# BEP32_6stencil_Seed_wMilling.net
KiCad netlist of a schematic drawn in EAGLE
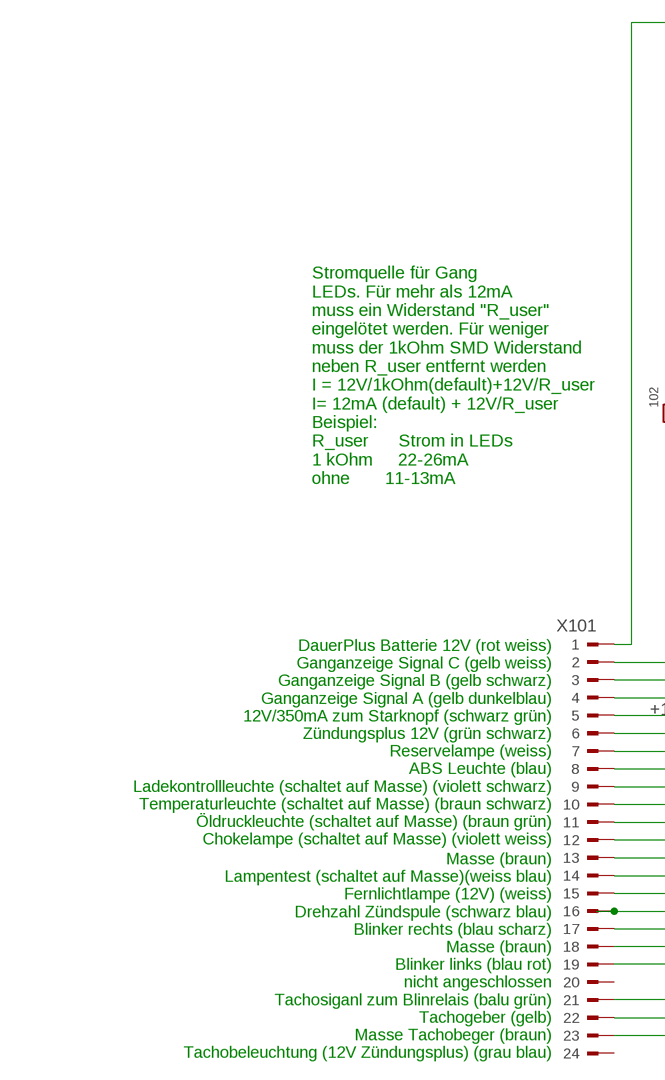
[diagram p0: schematic, sheet 1, part 1 of 2]
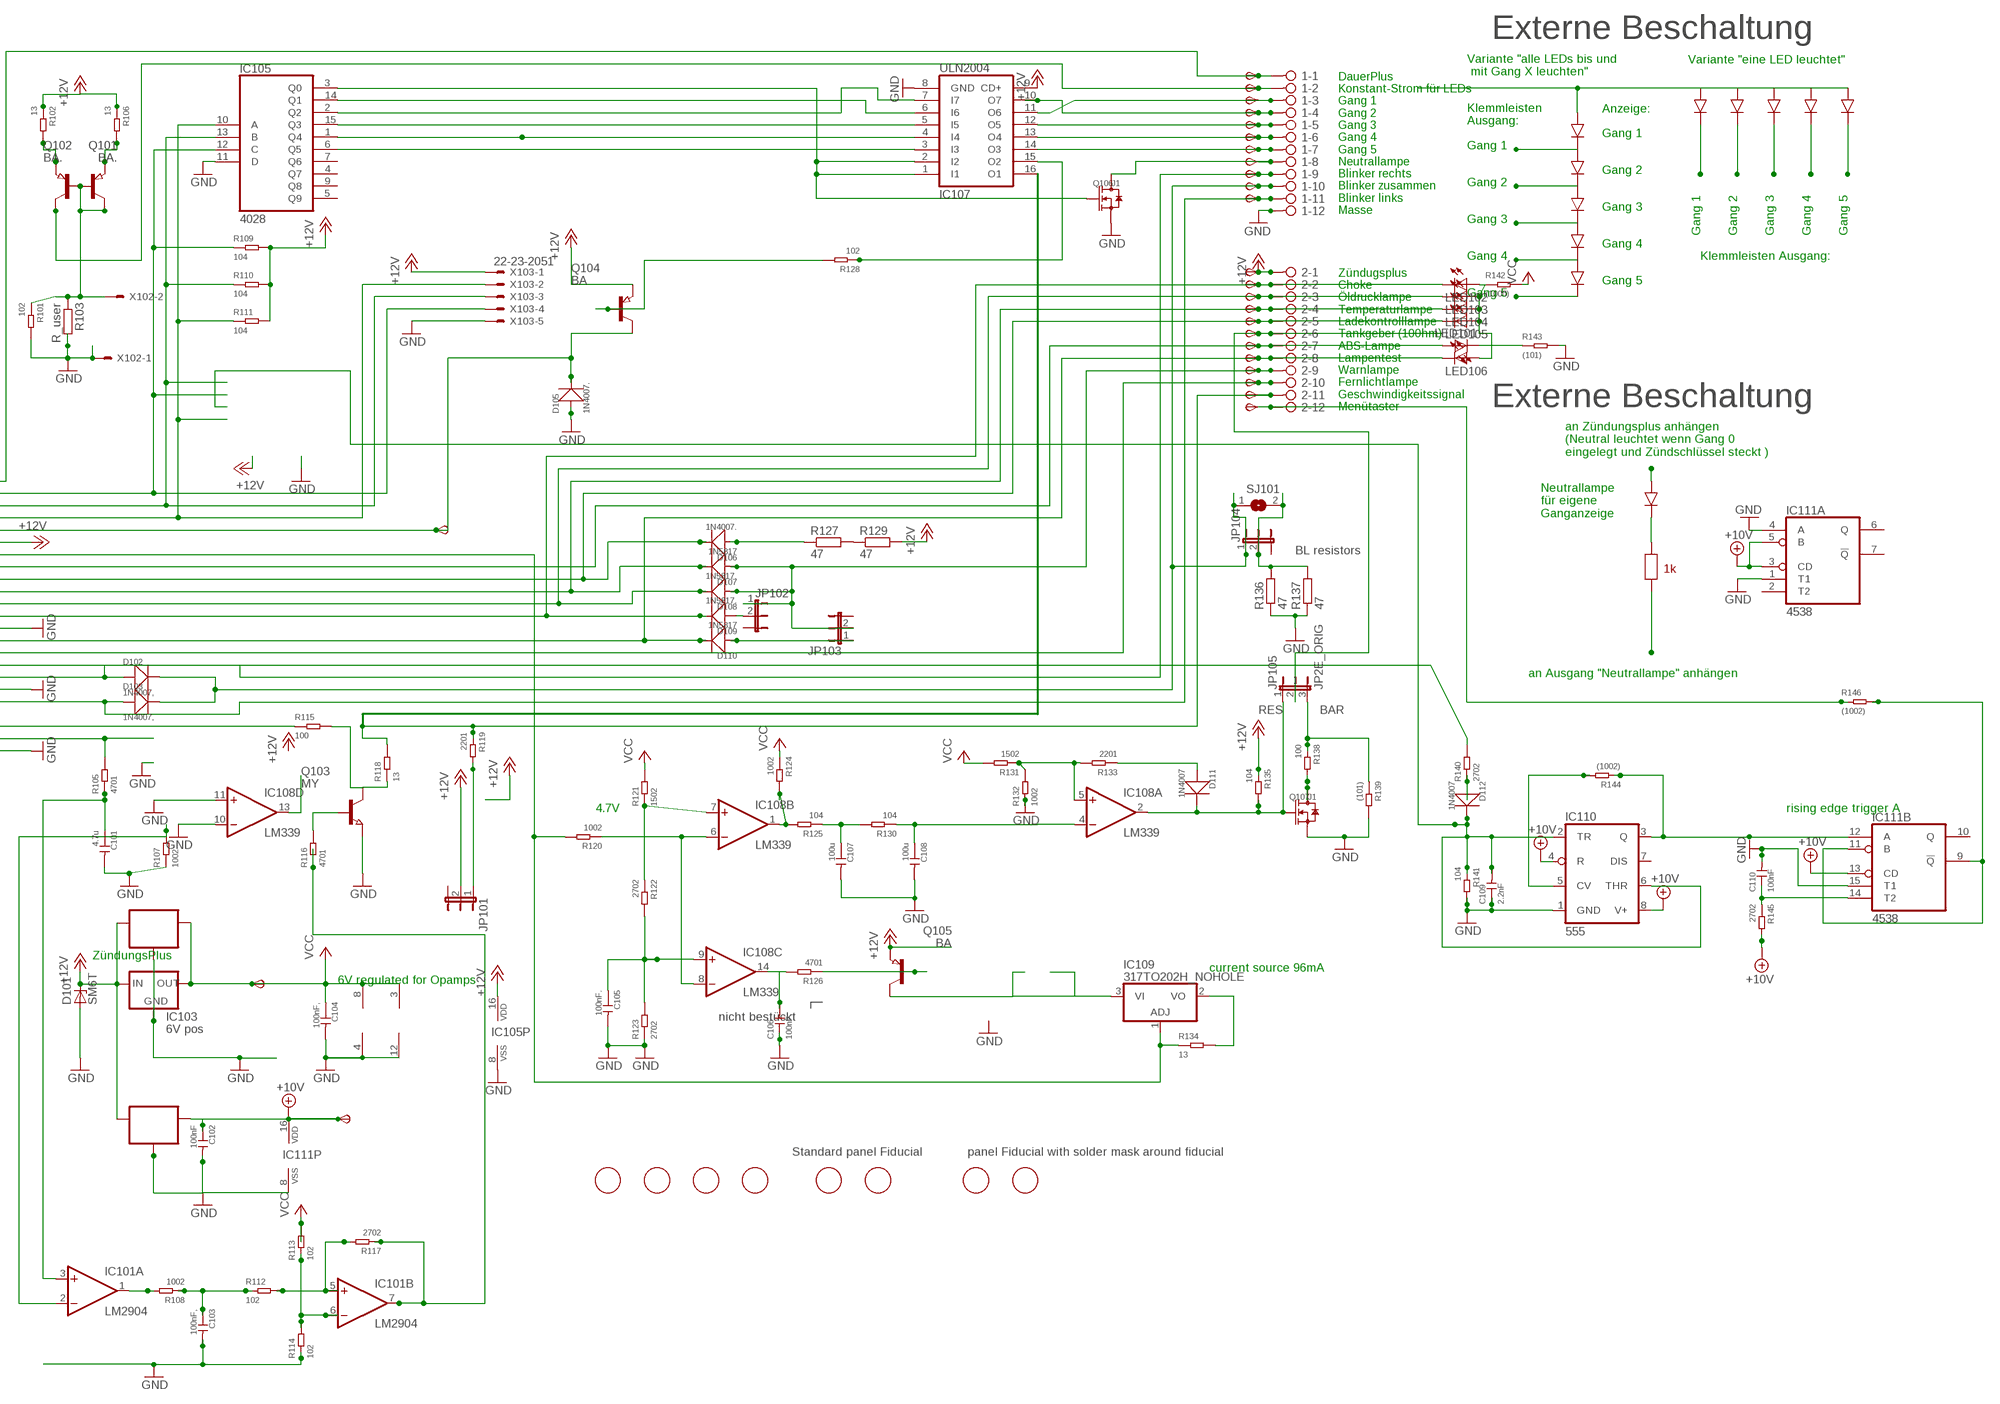
[diagram p1: schematic, sheet 1, part 2 of 2]
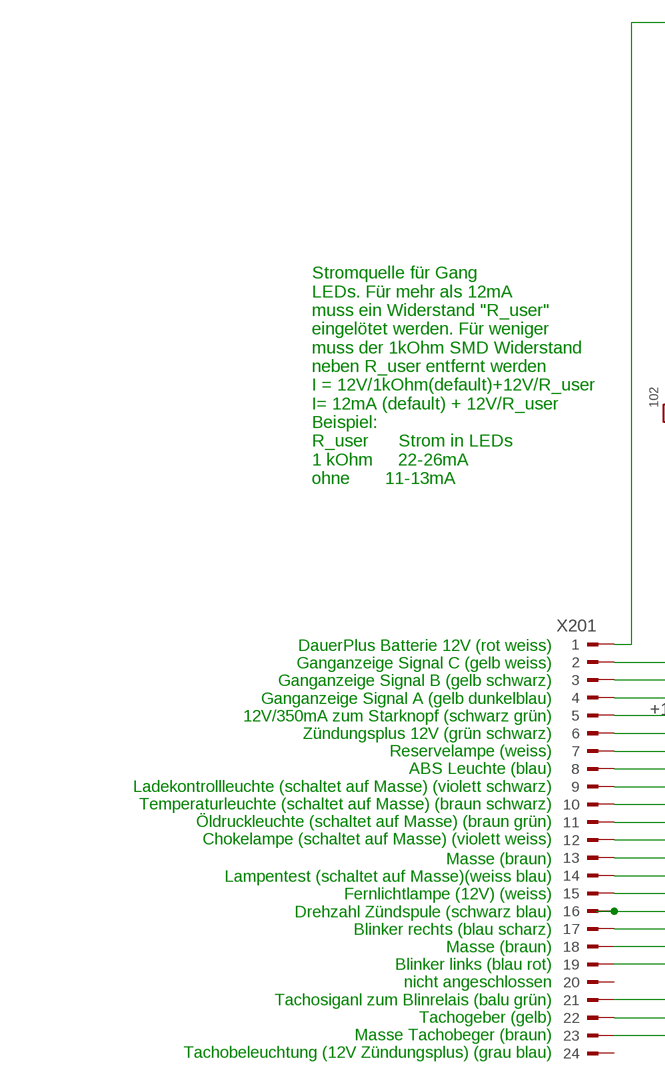
[diagram p2: schematic, sheet 2, part 1 of 2]
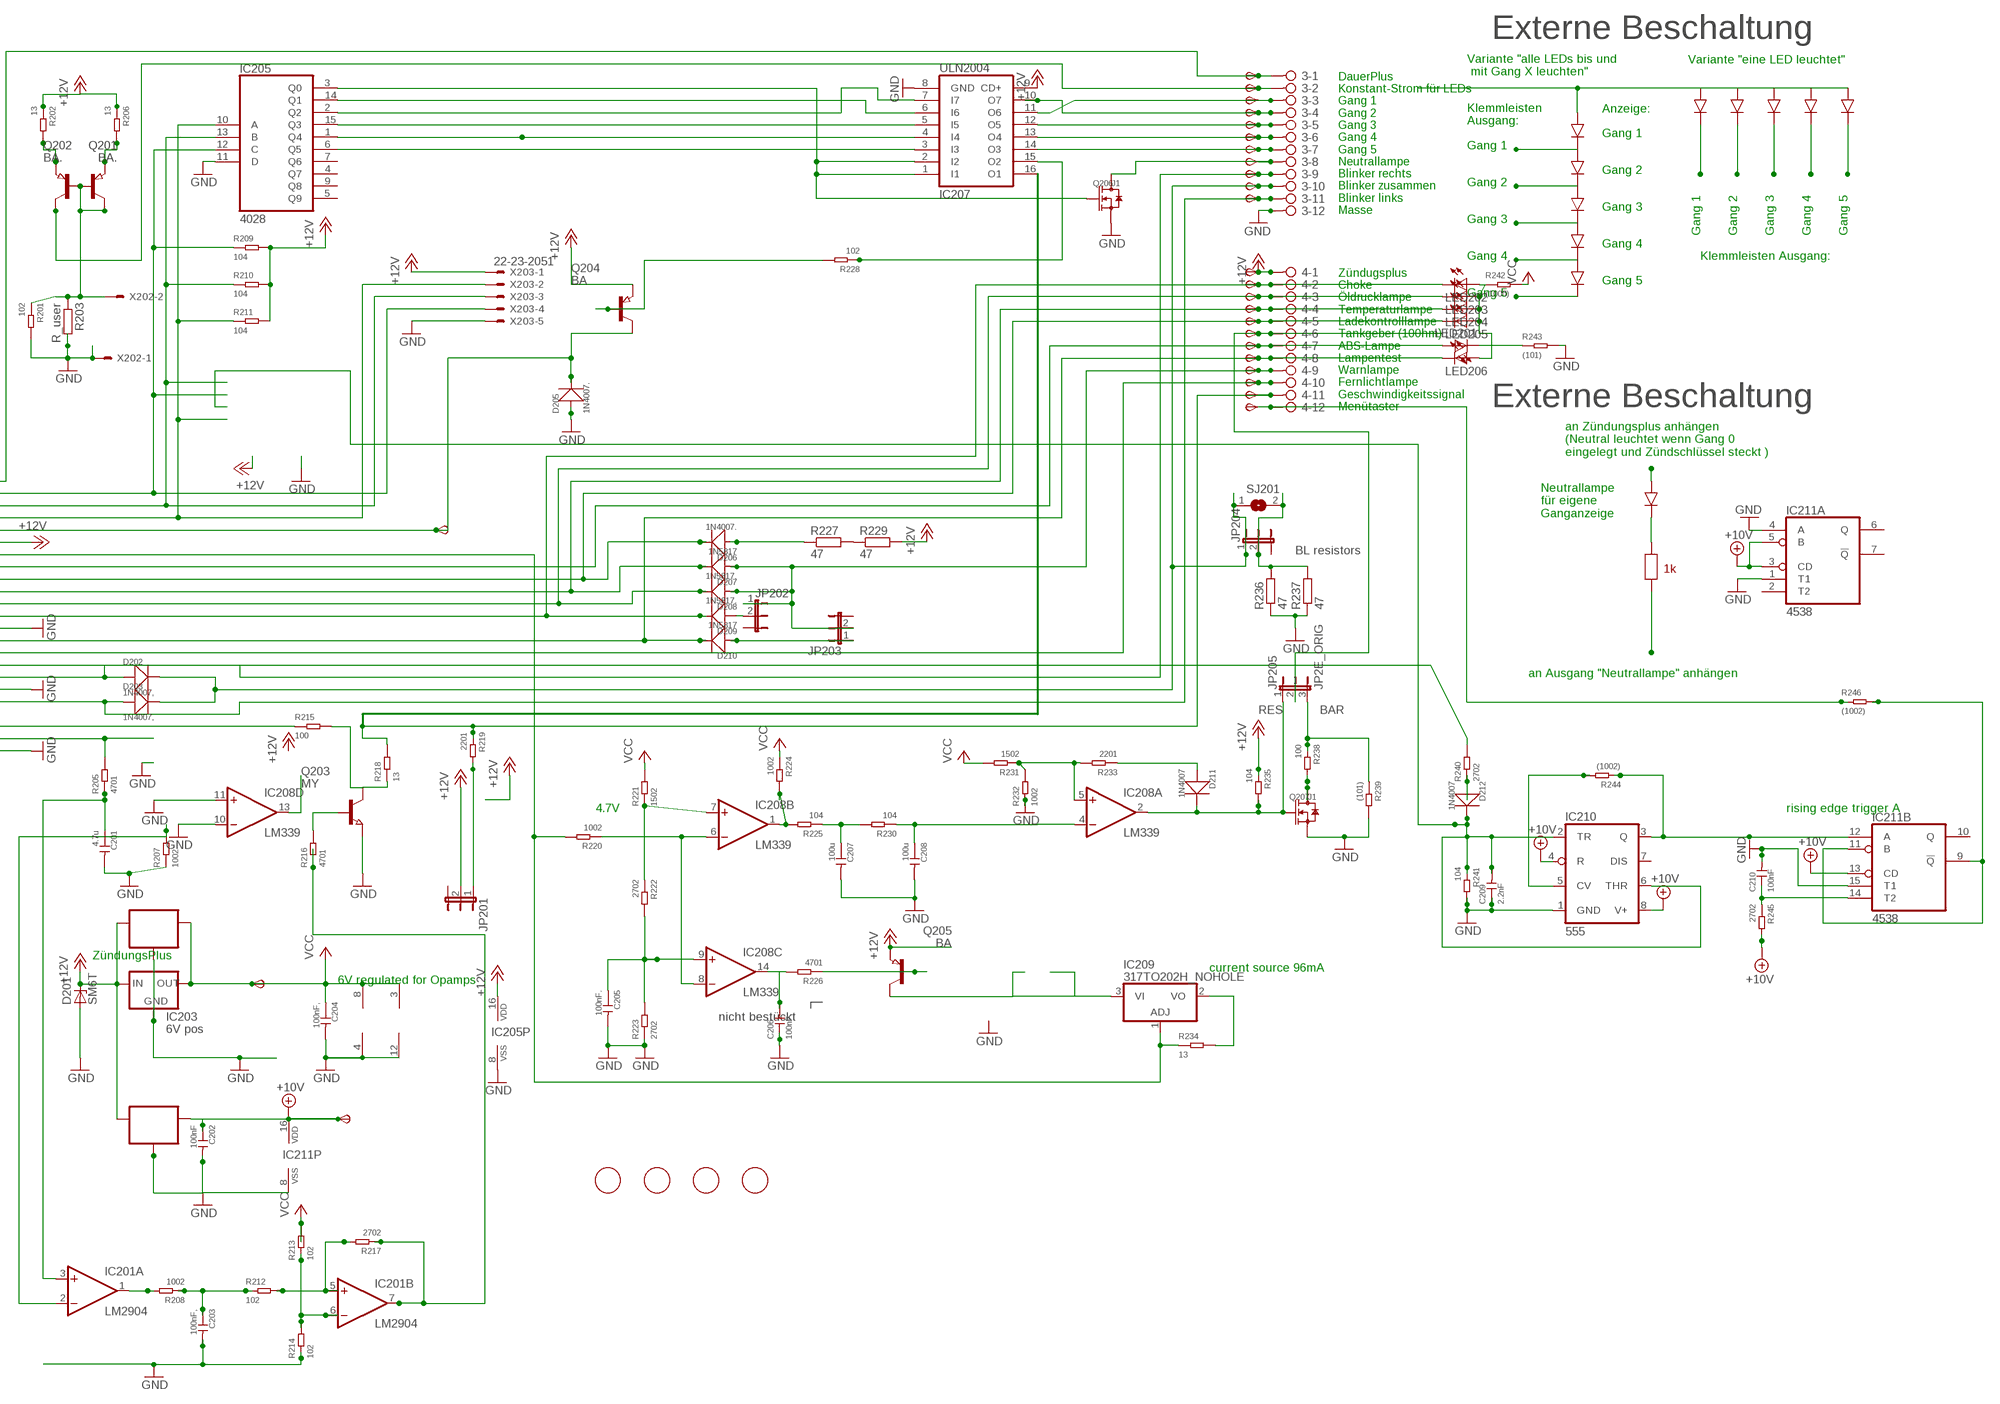
[diagram p3: schematic, sheet 2, part 2 of 2]
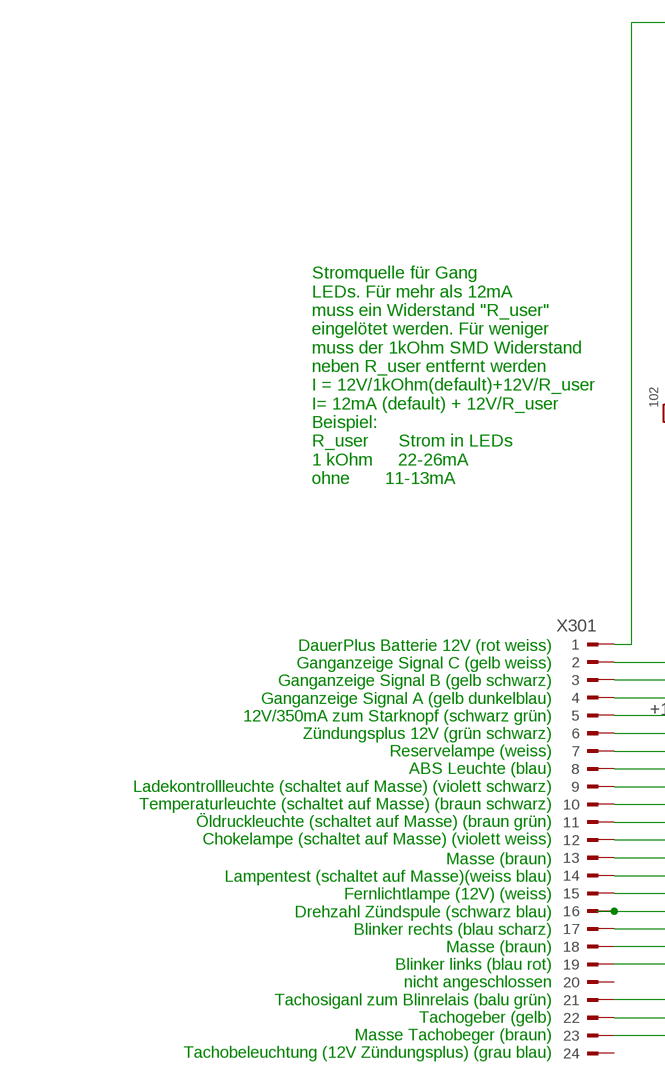
[diagram p4: schematic, sheet 3, part 1 of 2]
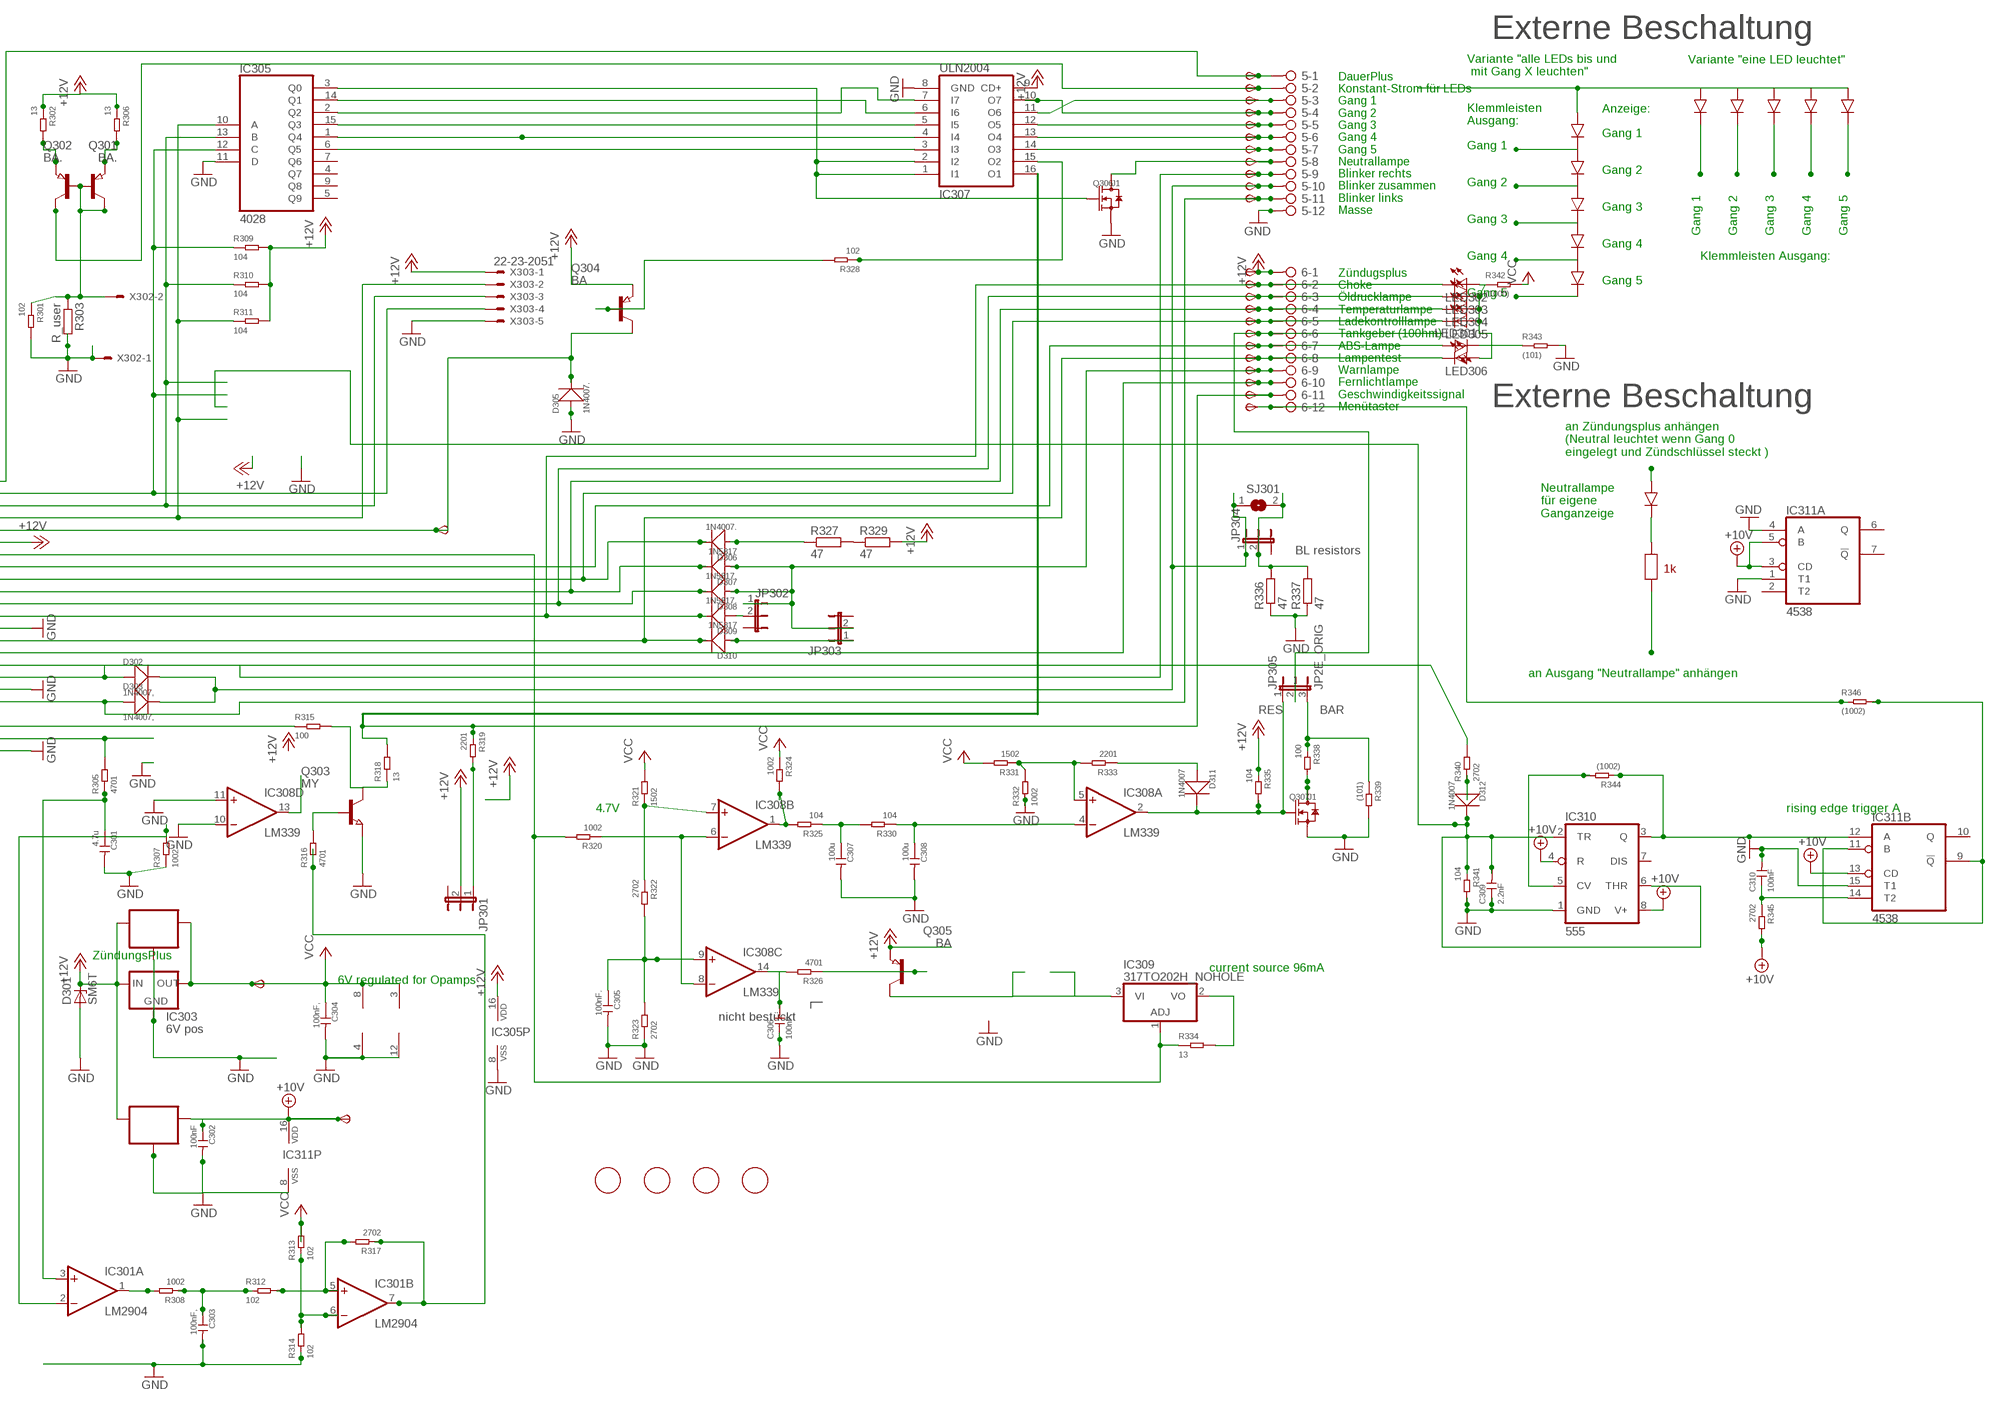
[diagram p5: schematic, sheet 3, part 2 of 2]
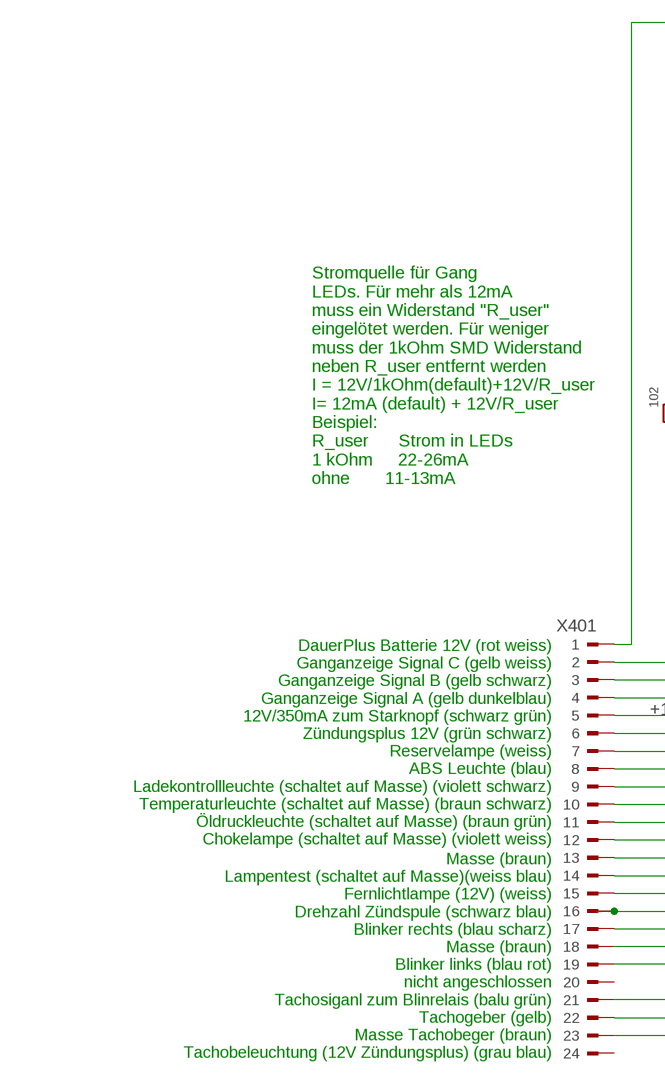
[diagram p6: schematic, sheet 4, part 1 of 2]
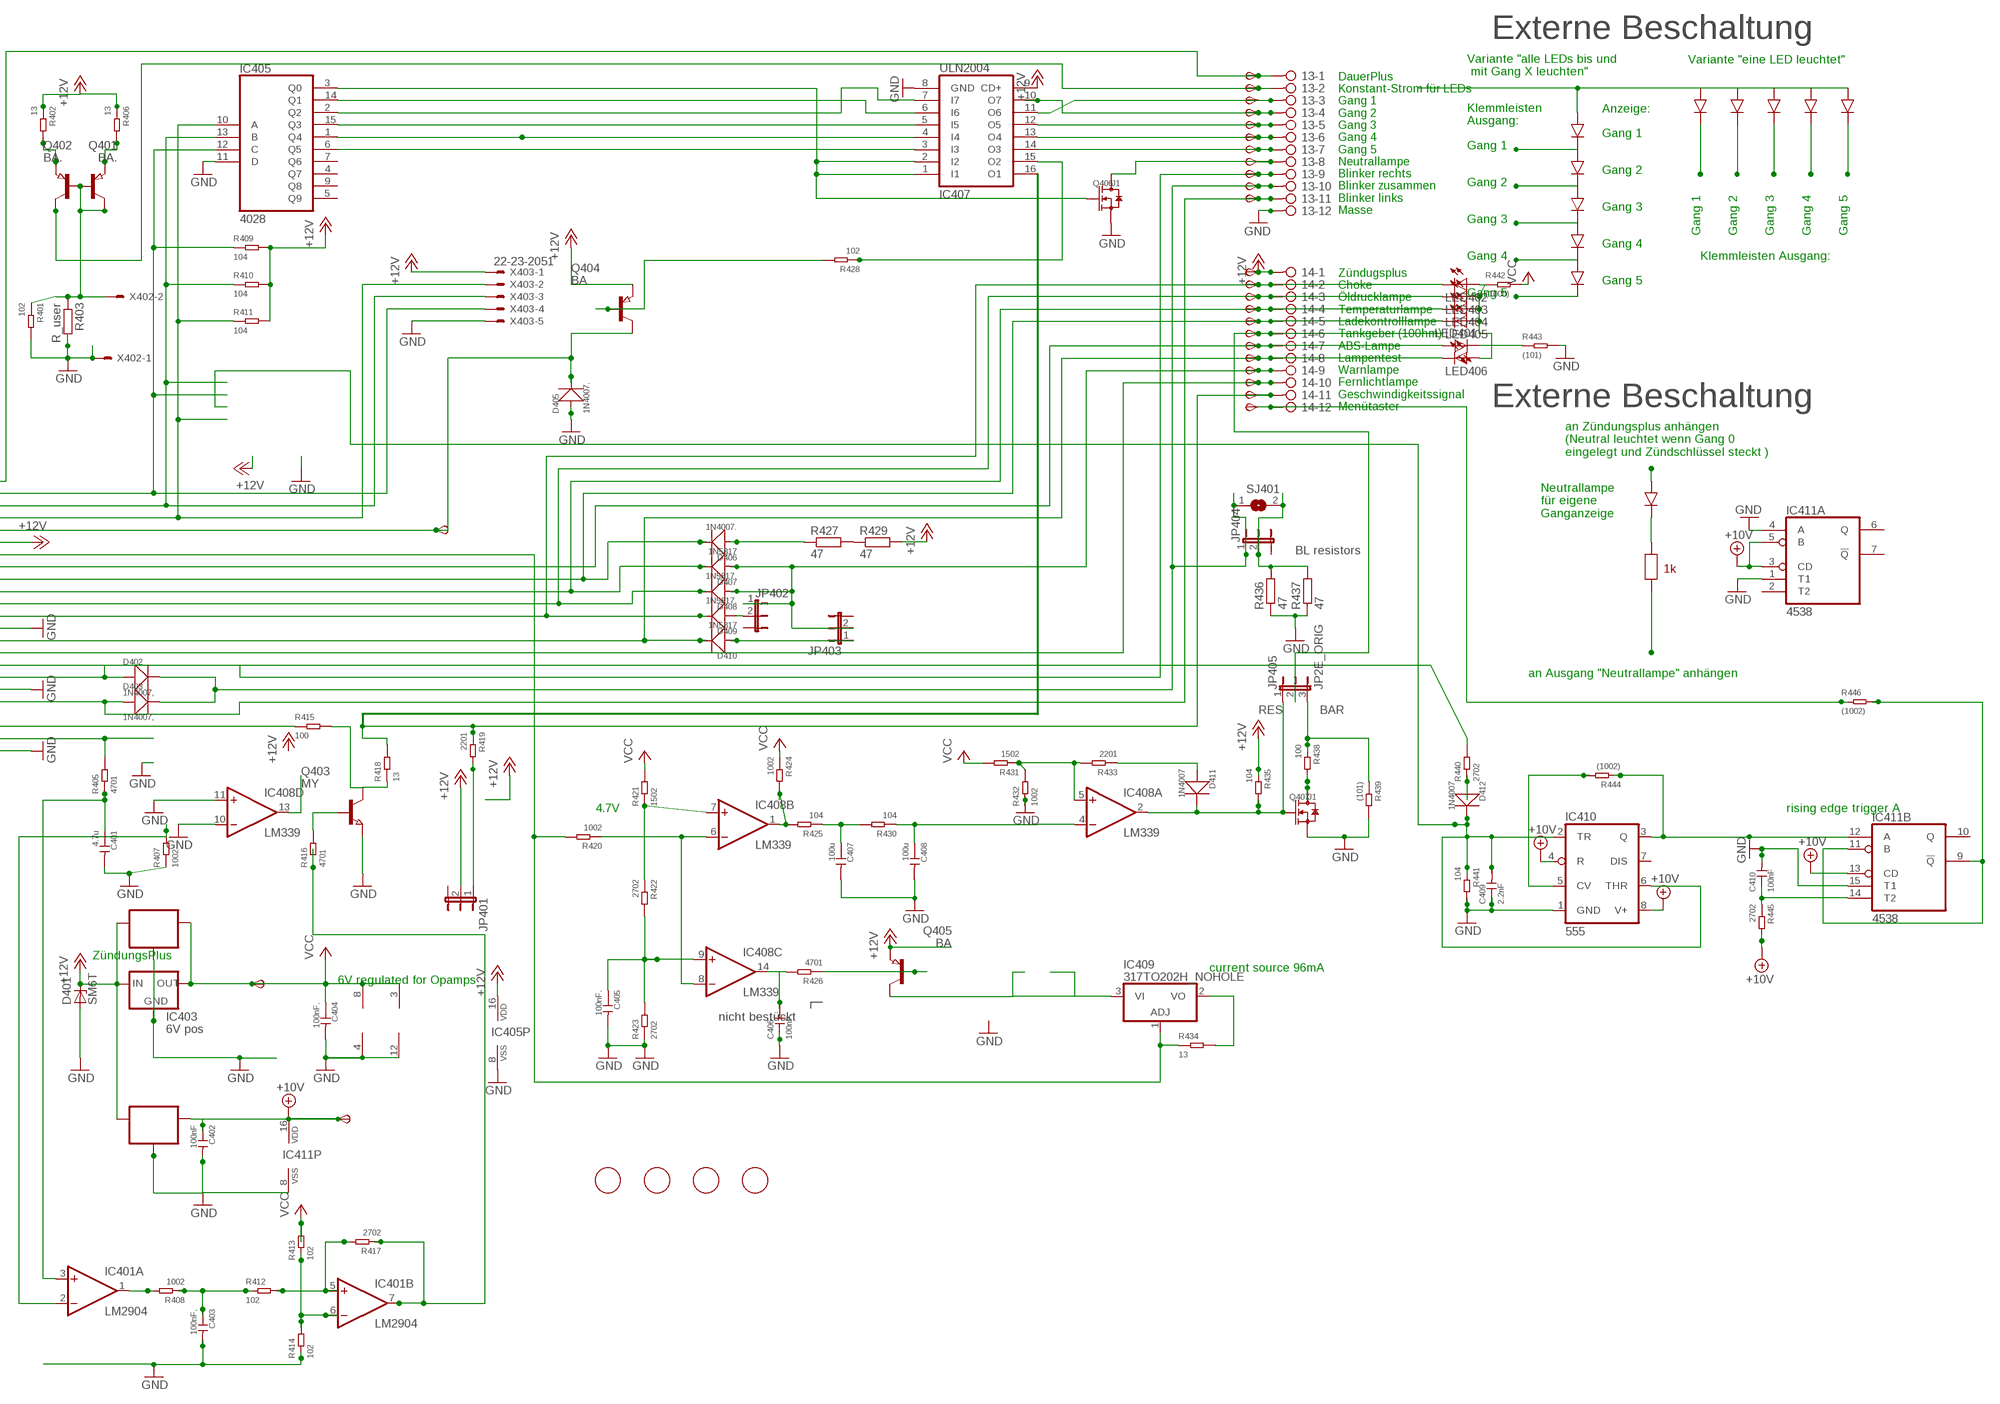
[diagram p7: schematic, sheet 4, part 2 of 2]
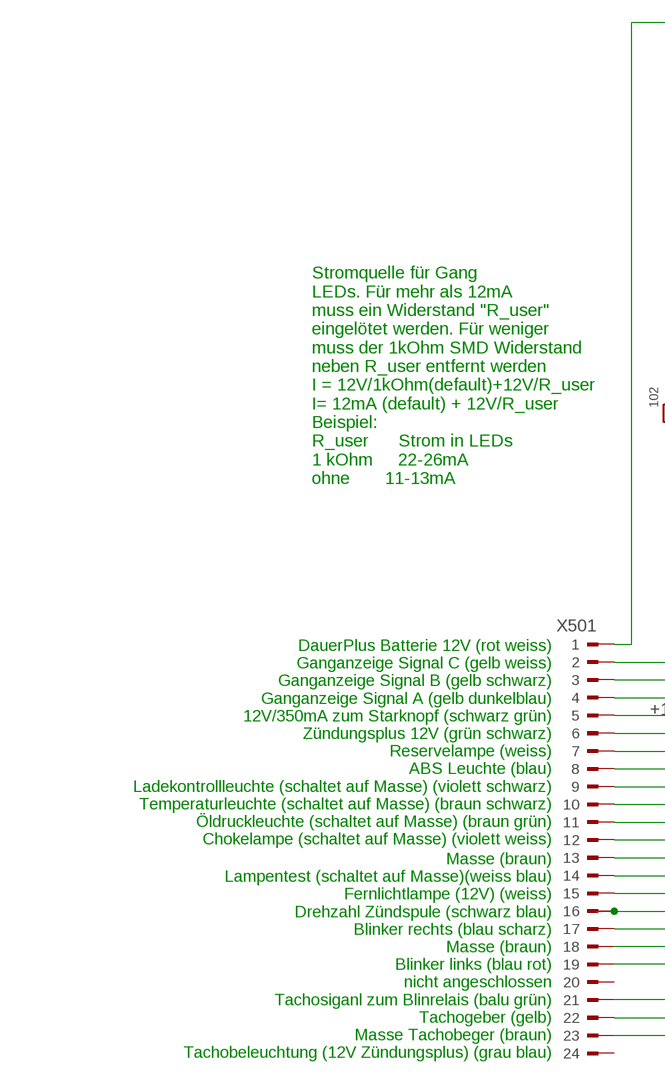
[diagram p8: schematic, sheet 5, part 1 of 2]
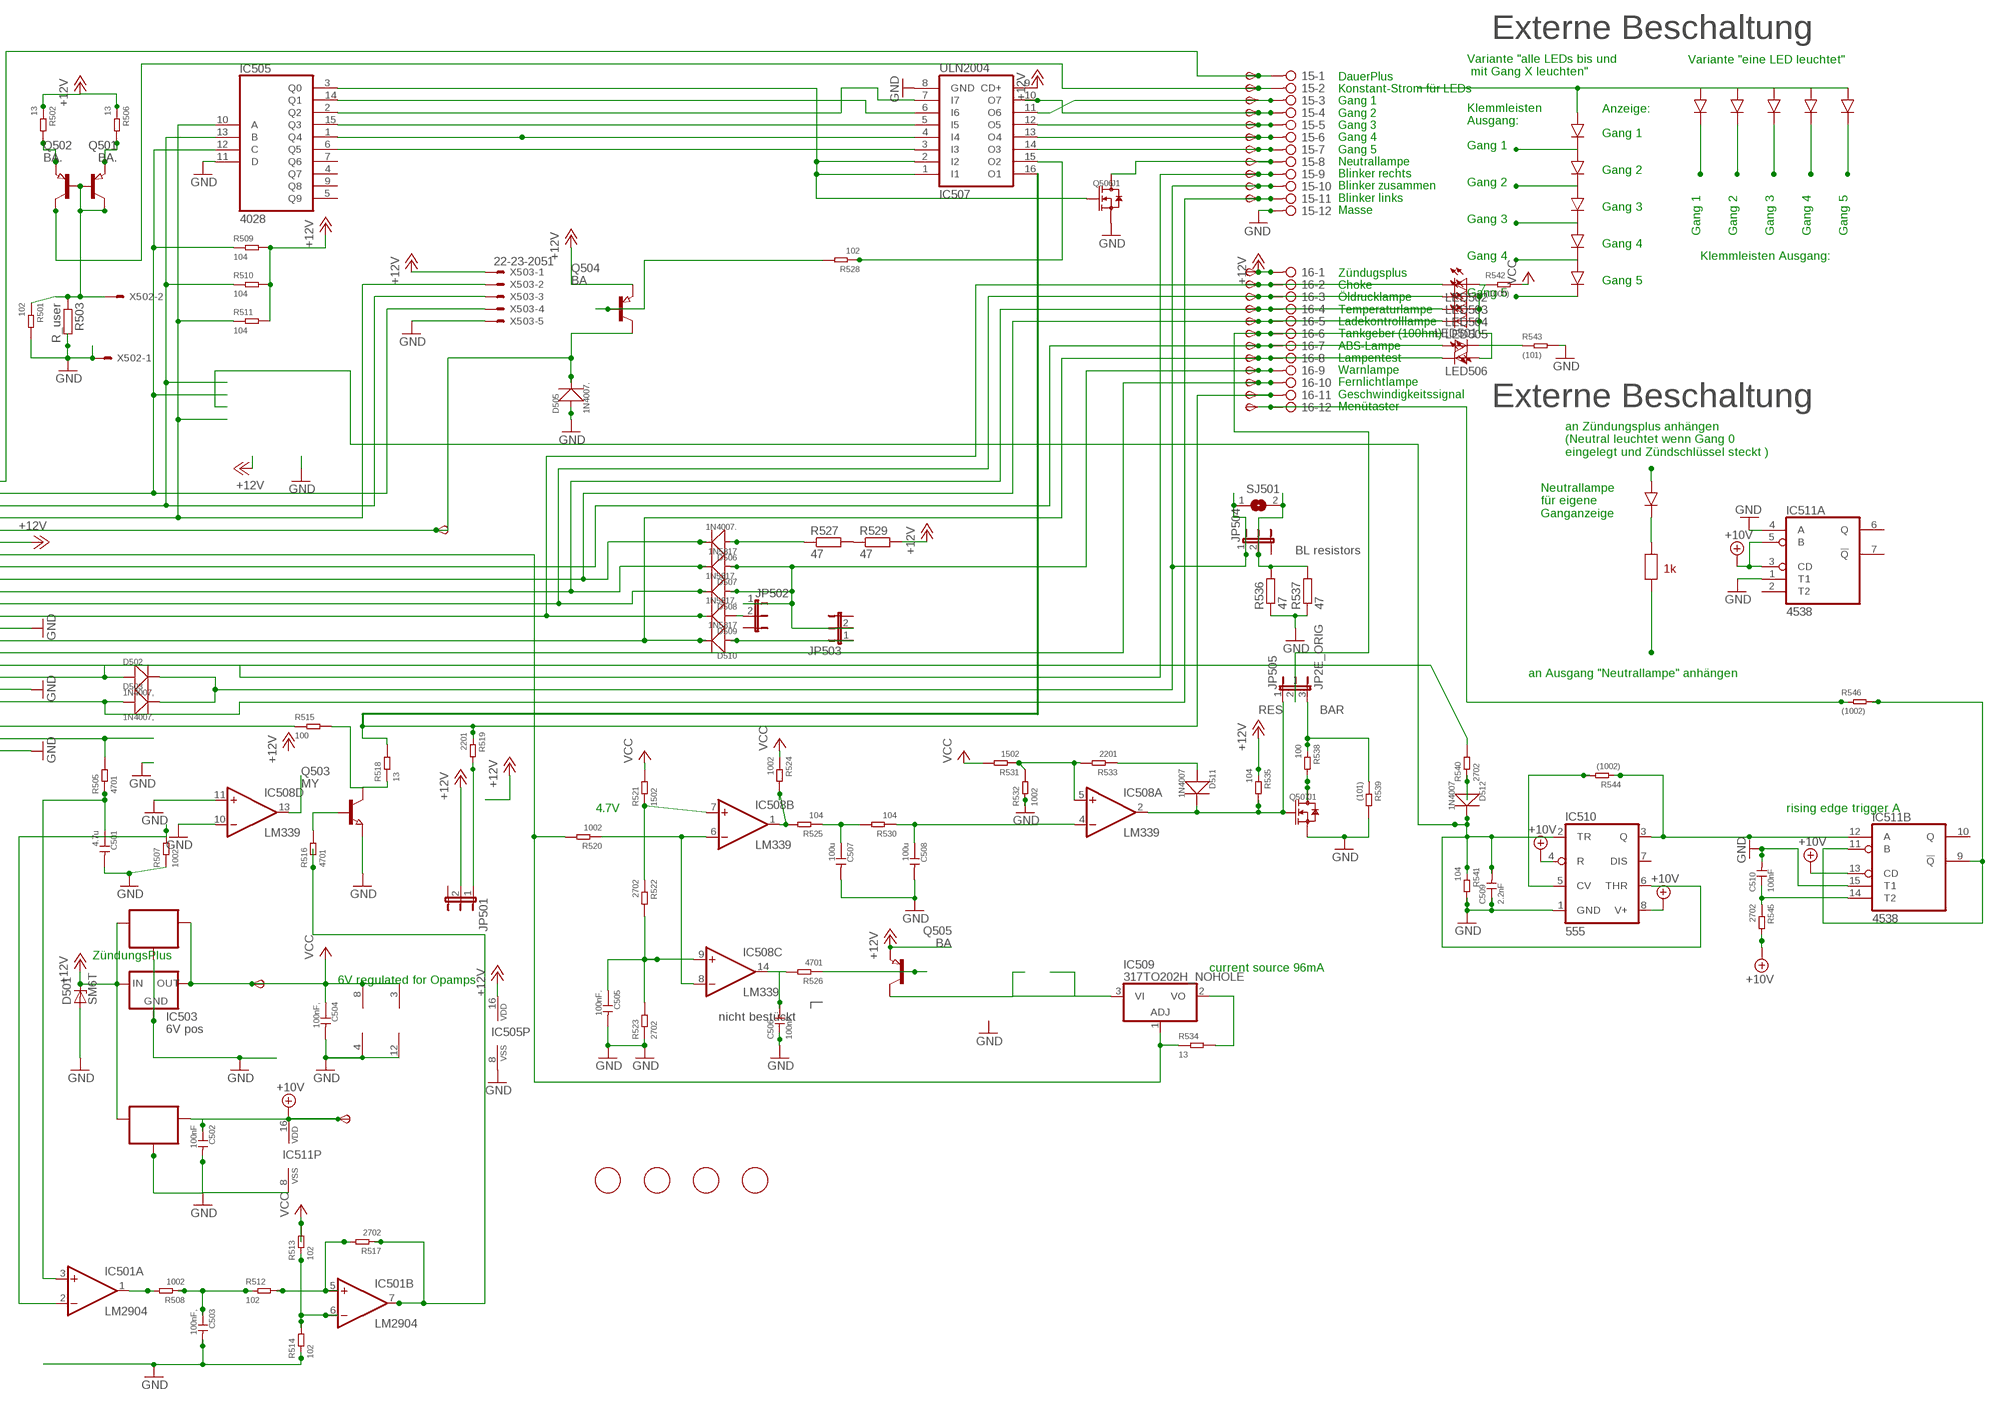
[diagram p9: schematic, sheet 5, part 2 of 2]
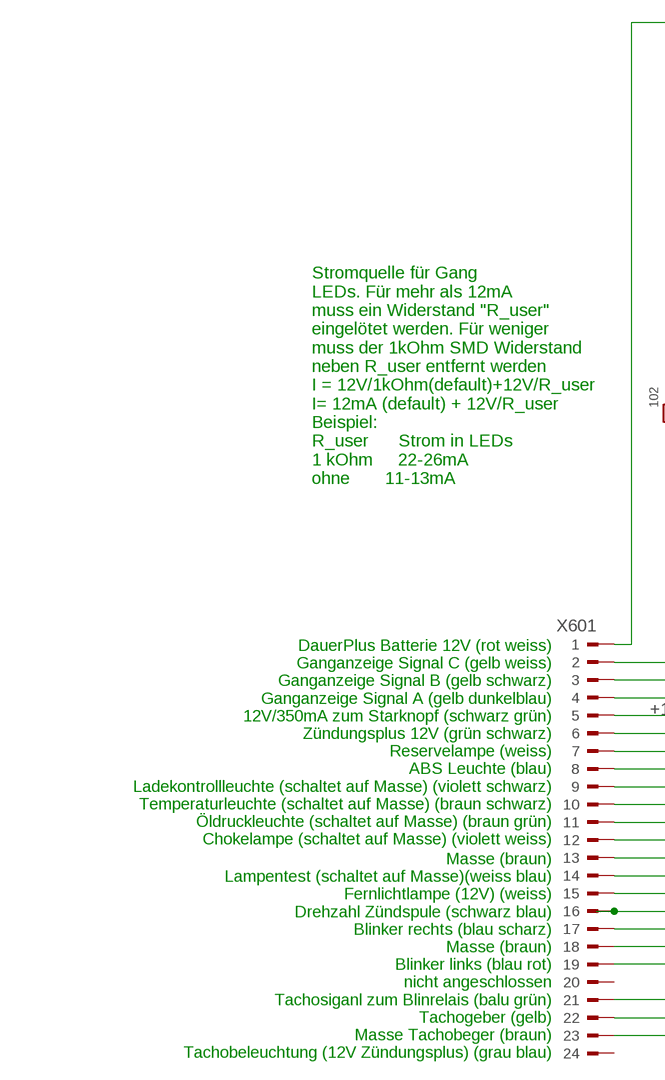
[diagram p10: schematic, sheet 6, part 1 of 2]
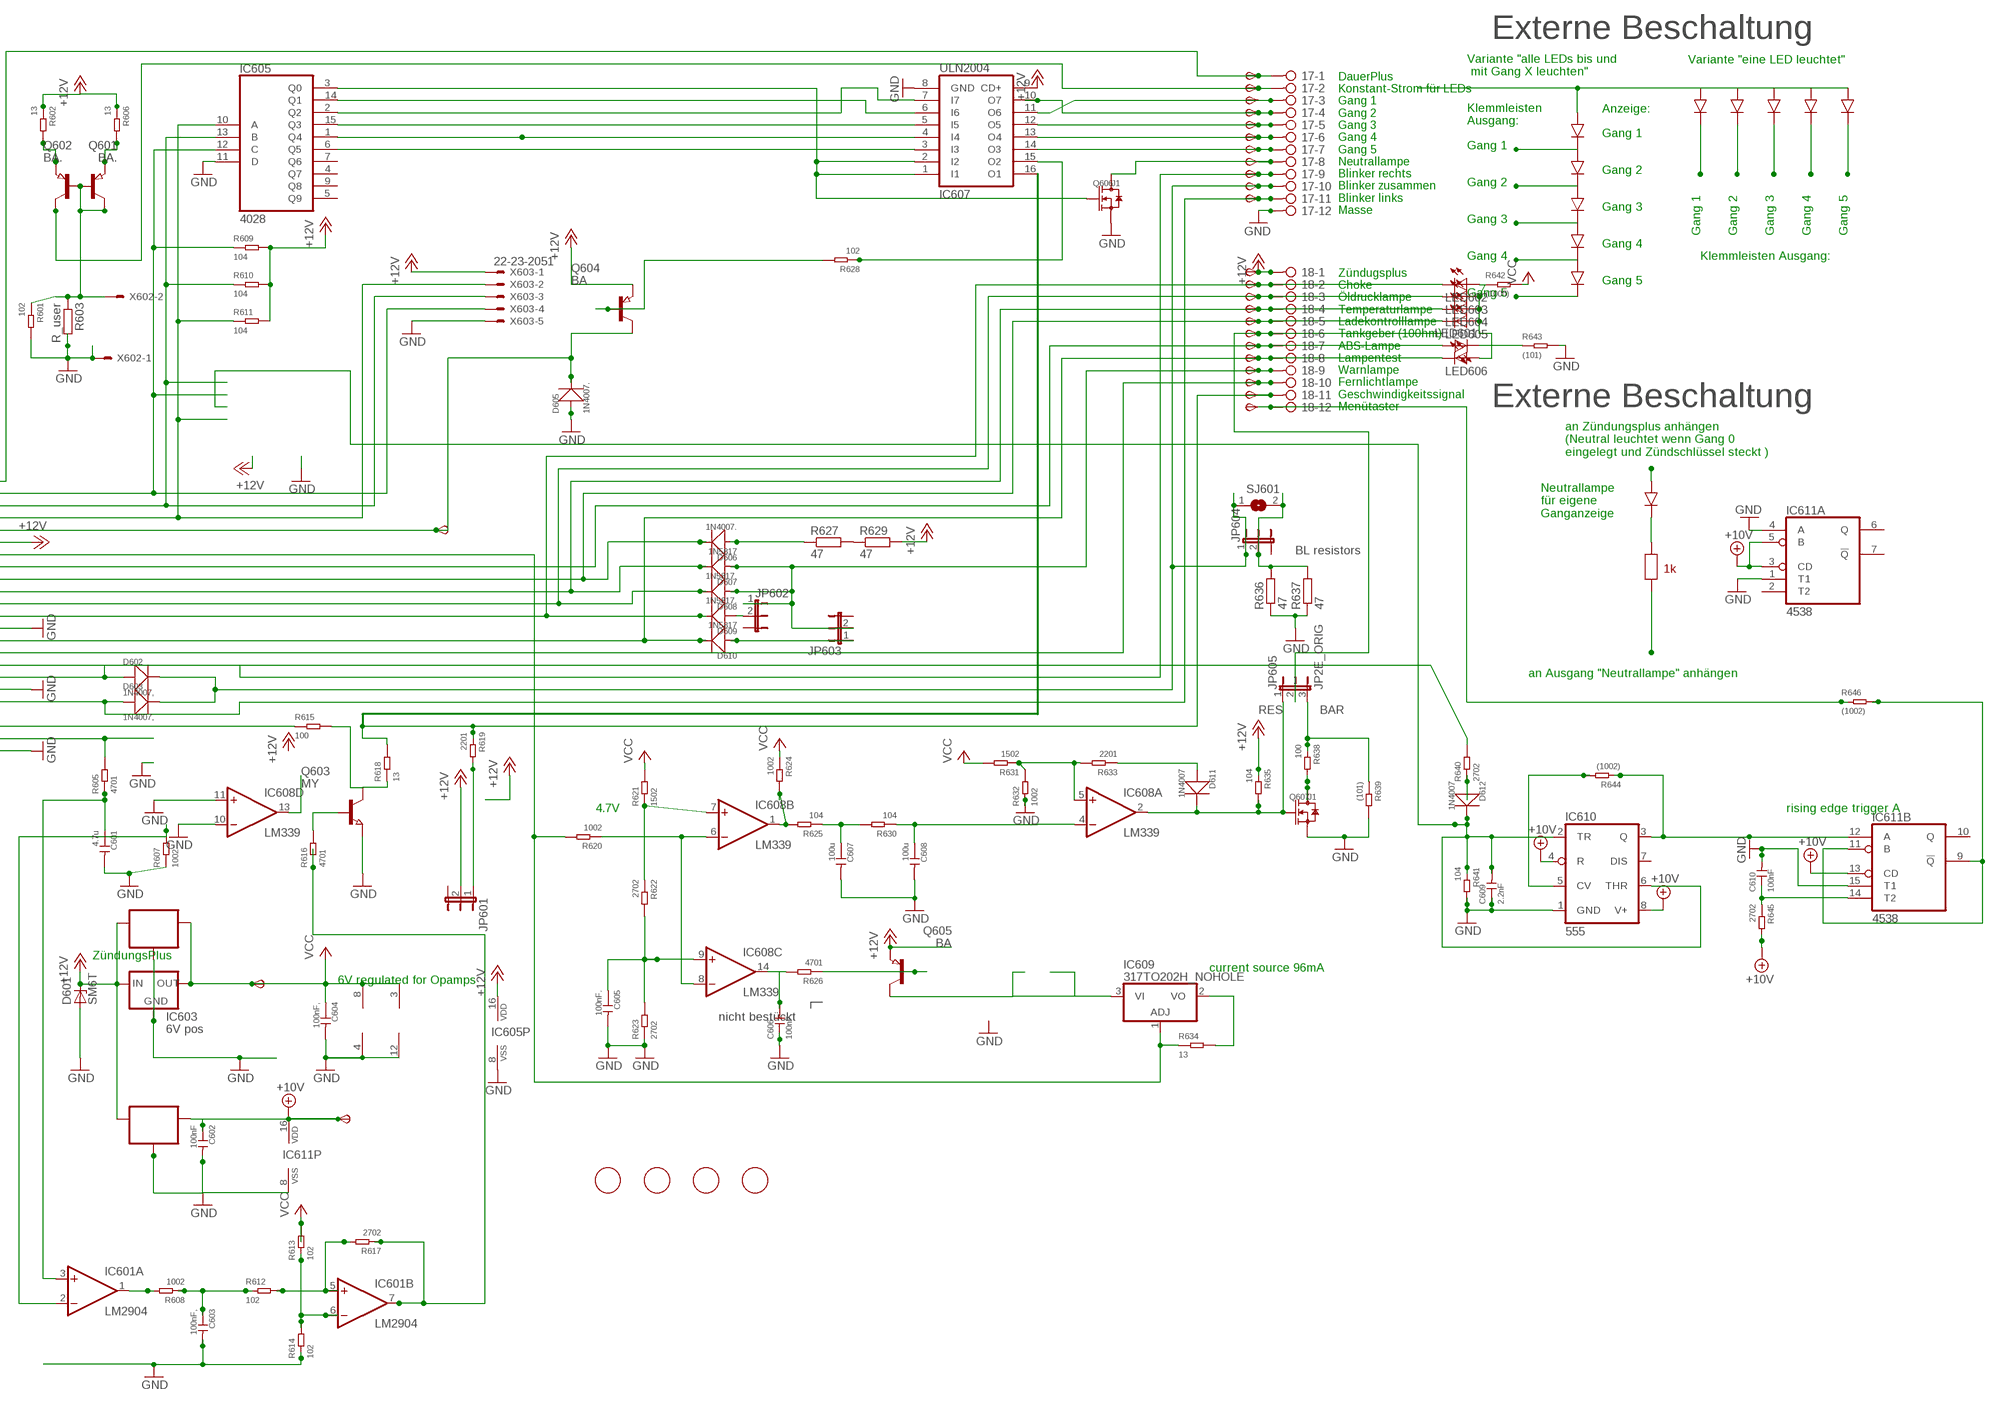
[diagram p11: schematic, sheet 6, part 2 of 2]
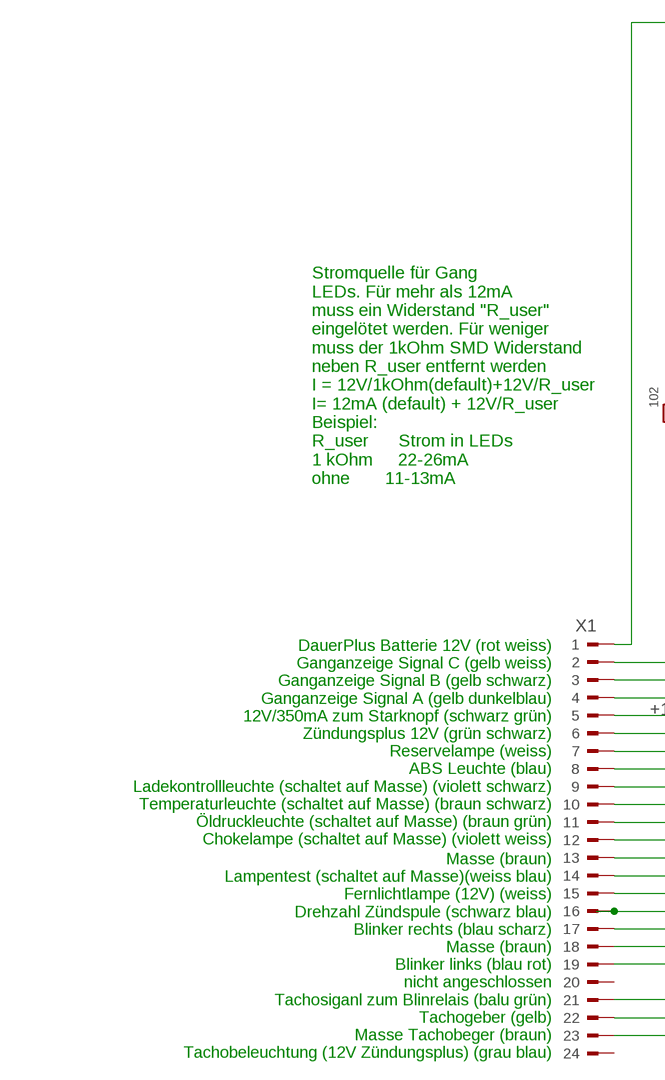
[diagram p12: schematic, sheet 7, part 1 of 2]
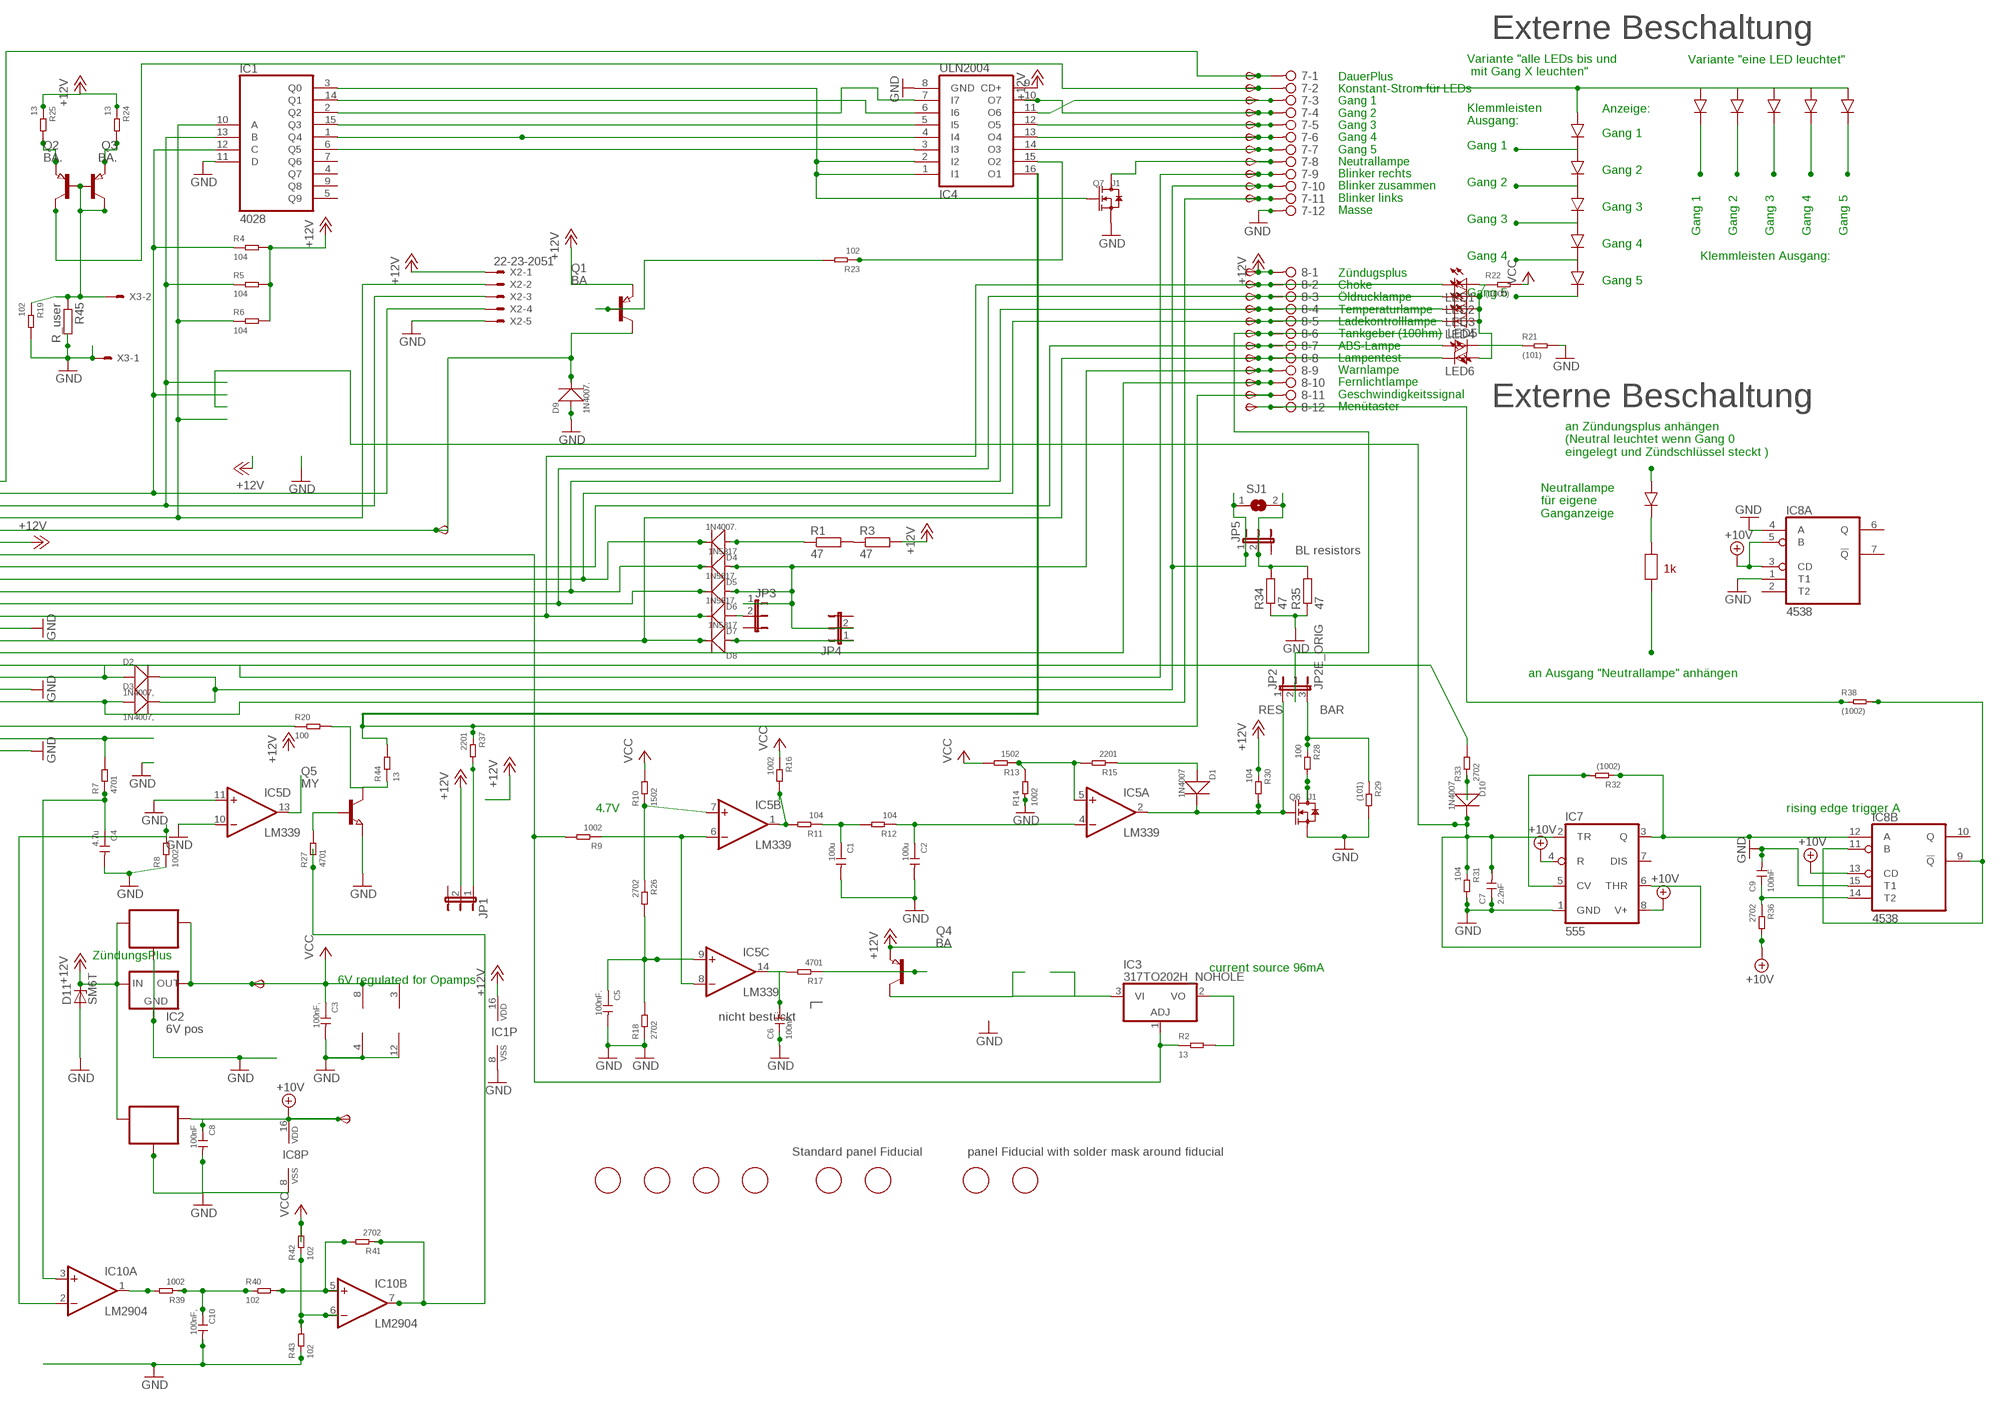
[diagram p13: schematic, sheet 7, part 2 of 2]
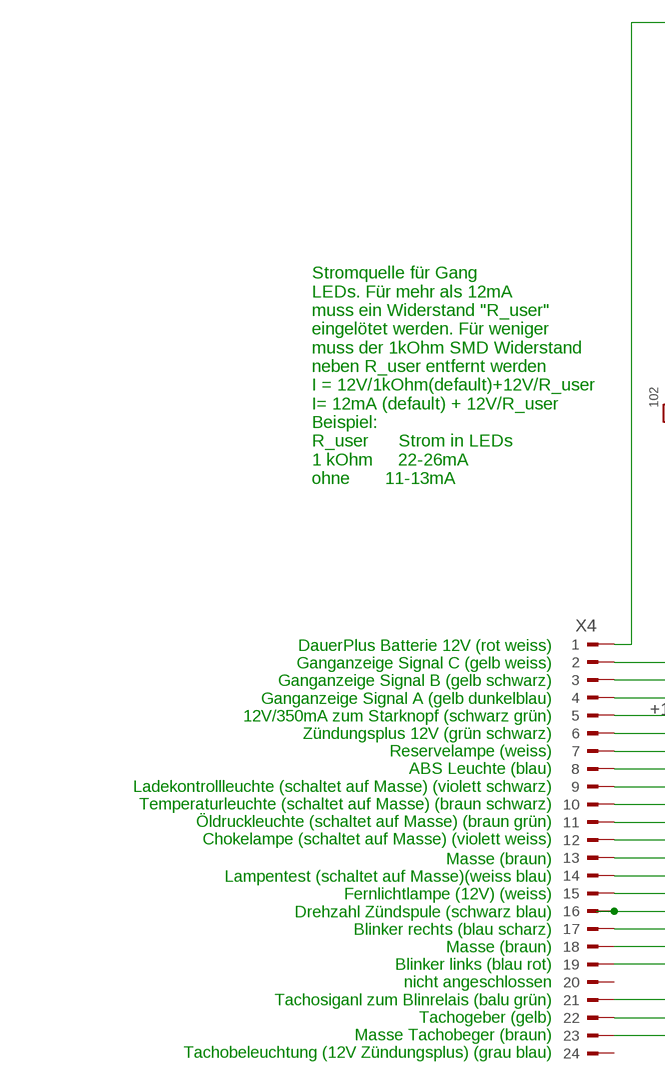
[diagram p14: schematic, sheet 8, part 1 of 2]
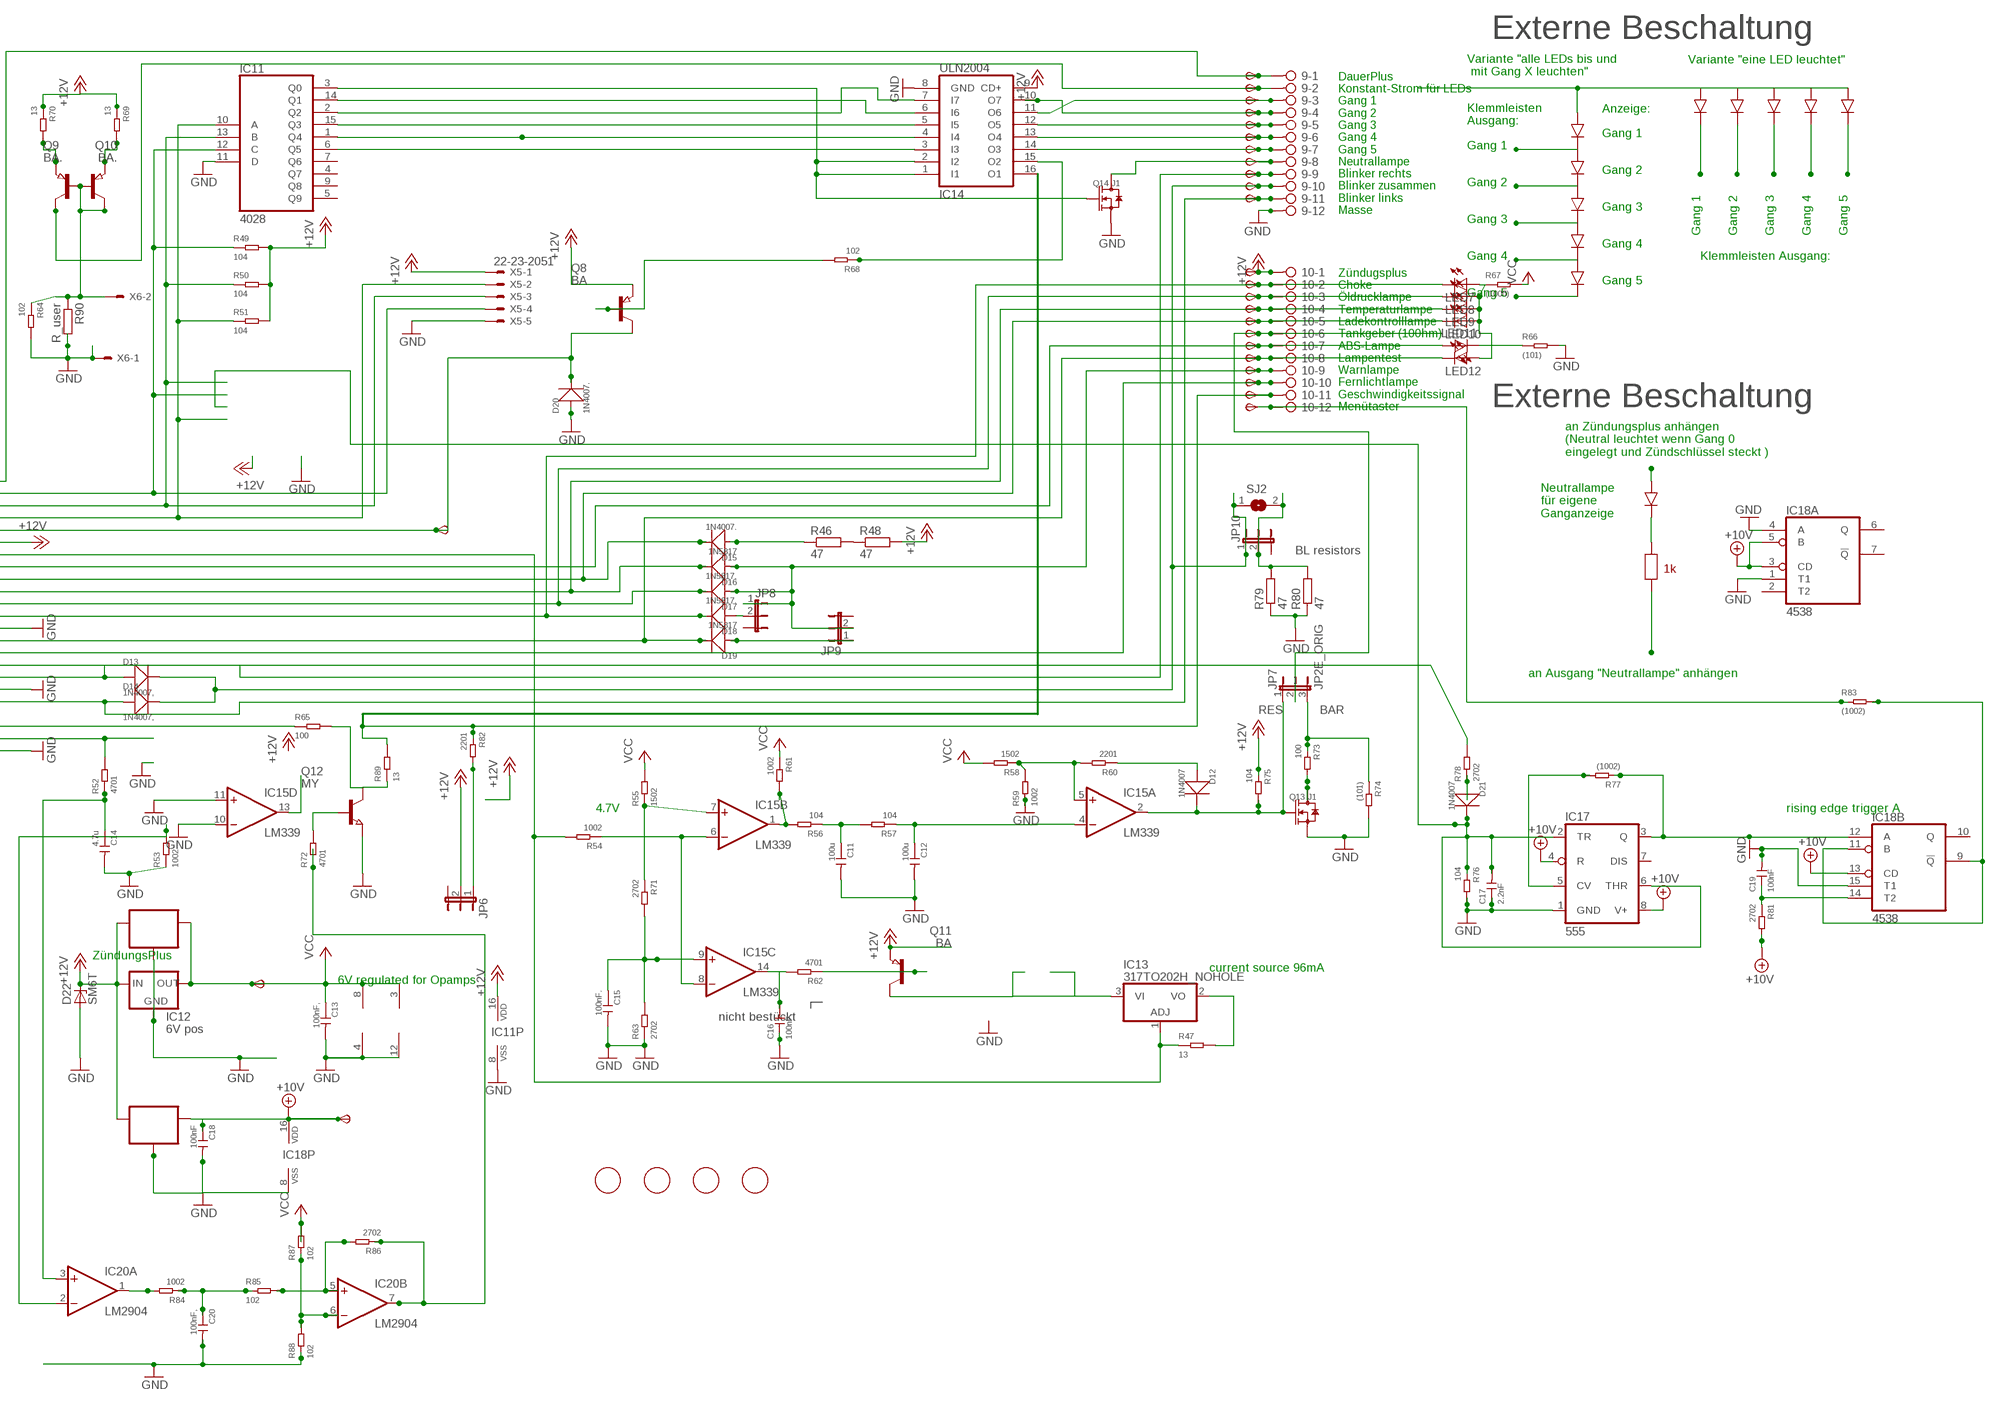
[diagram p15: schematic, sheet 8, part 2 of 2]
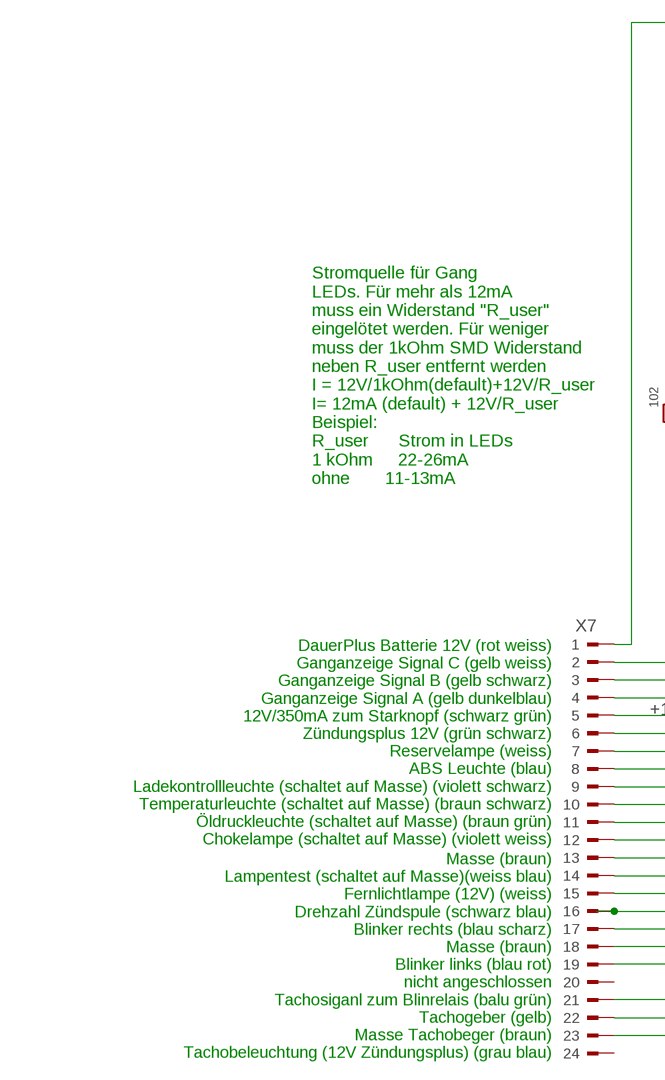
[diagram p16: schematic, sheet 9, part 1 of 2]
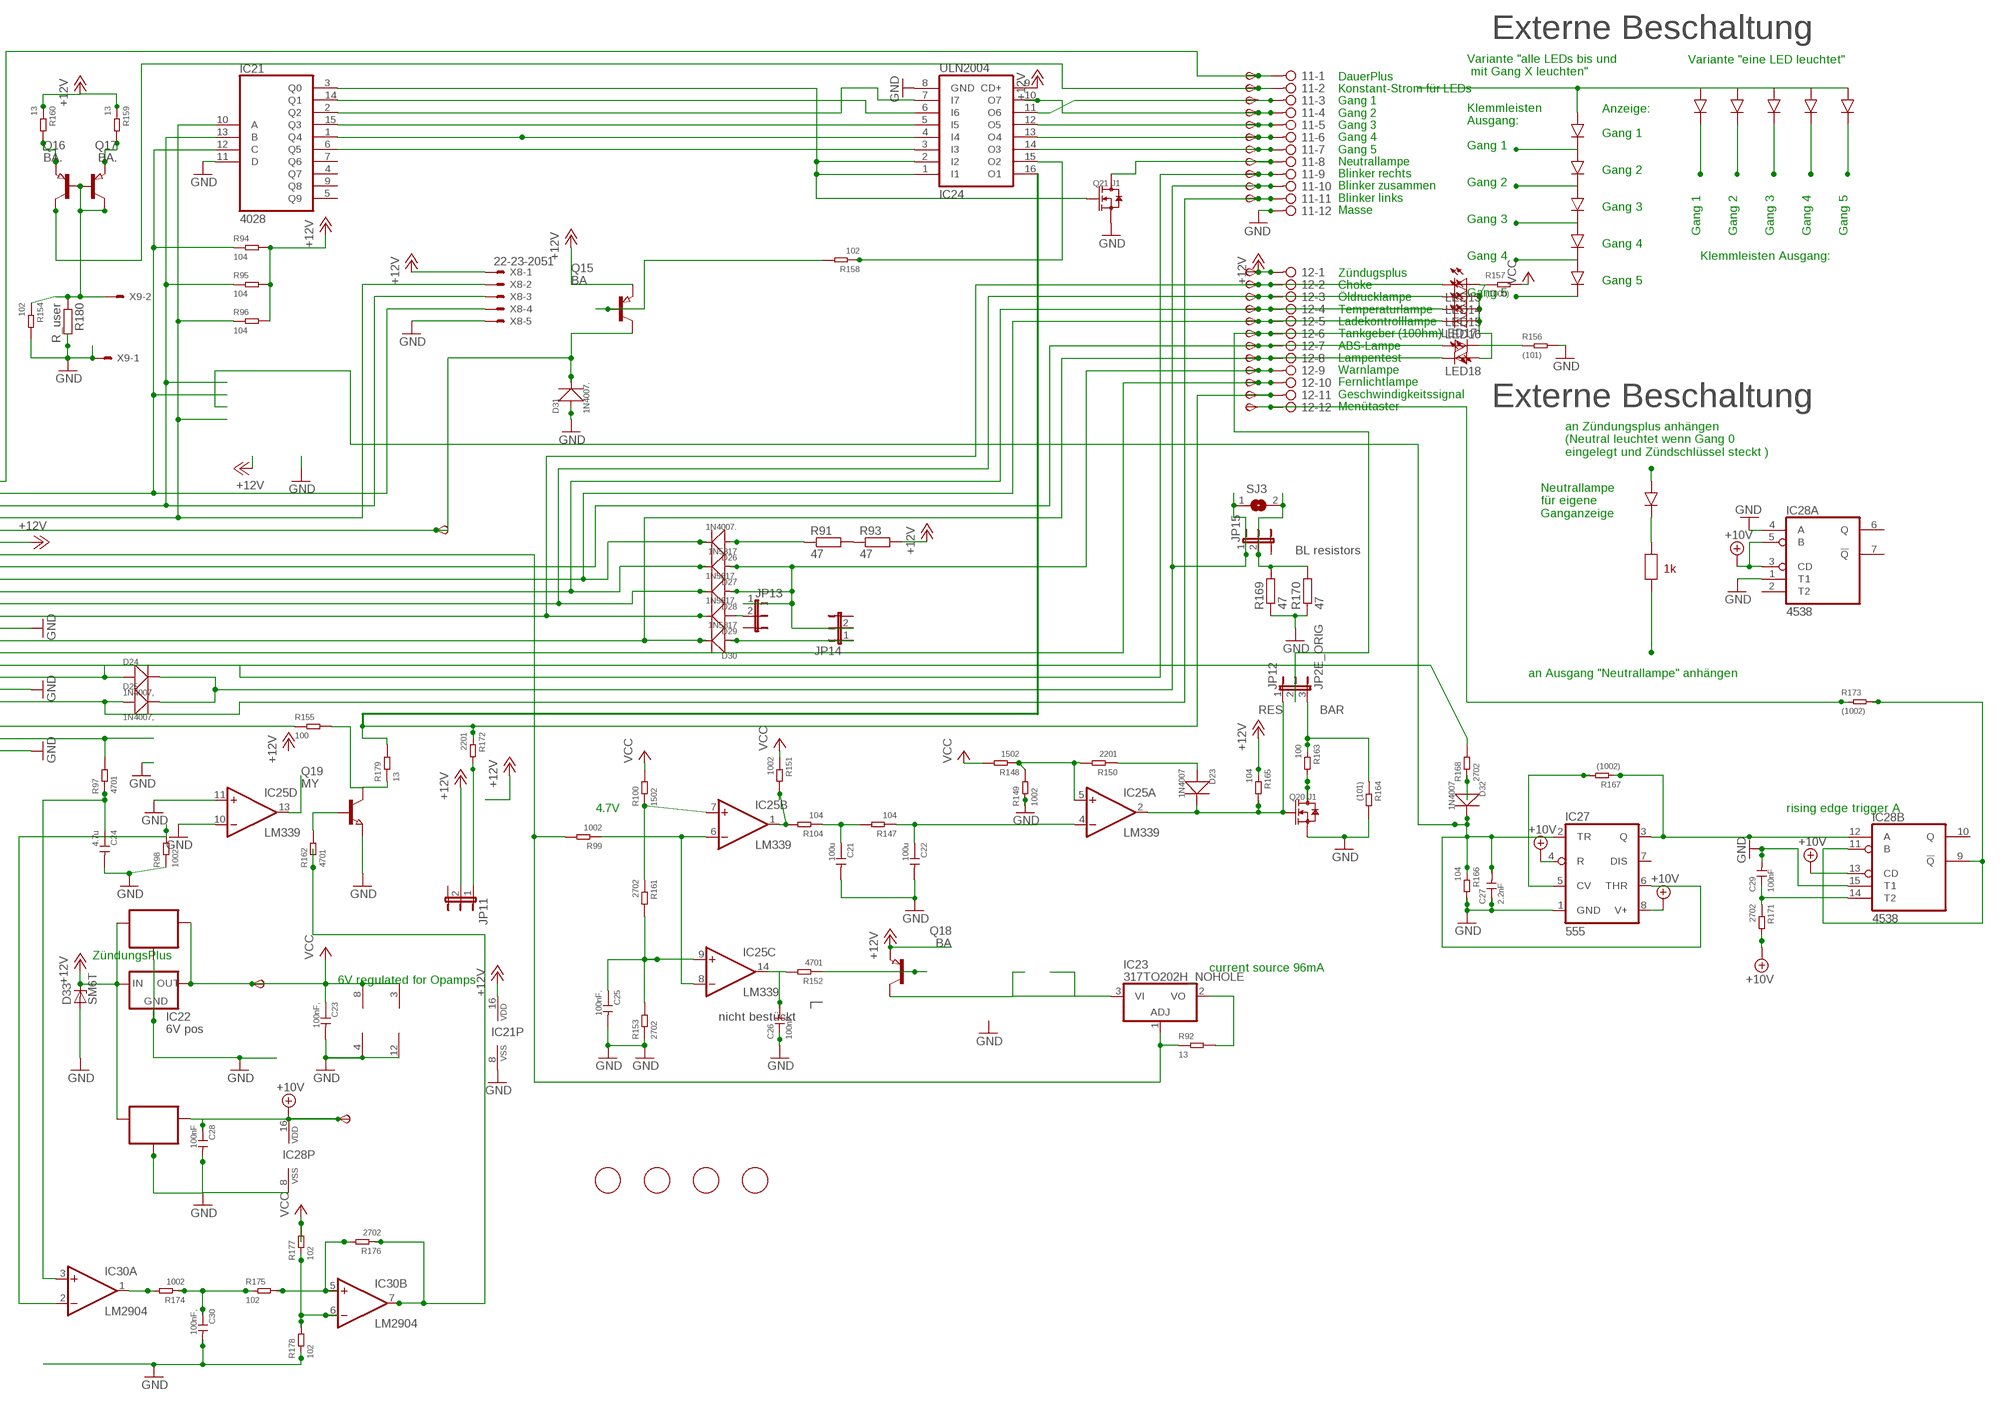
[diagram p17: schematic, sheet 9, part 2 of 2]
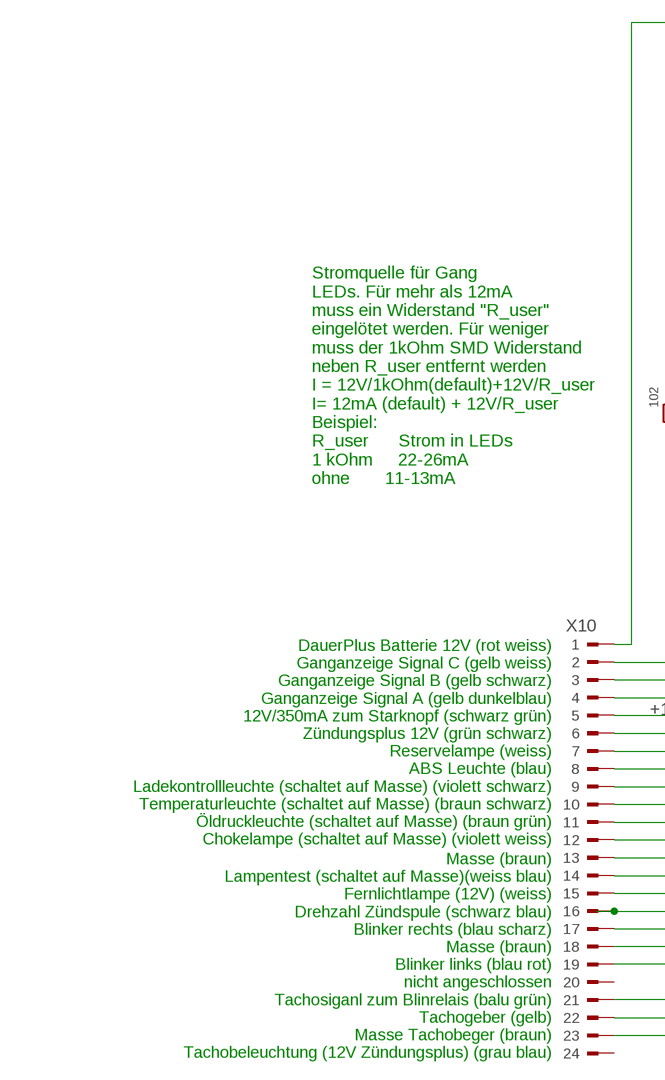
[diagram p18: schematic, sheet 10, part 1 of 2]
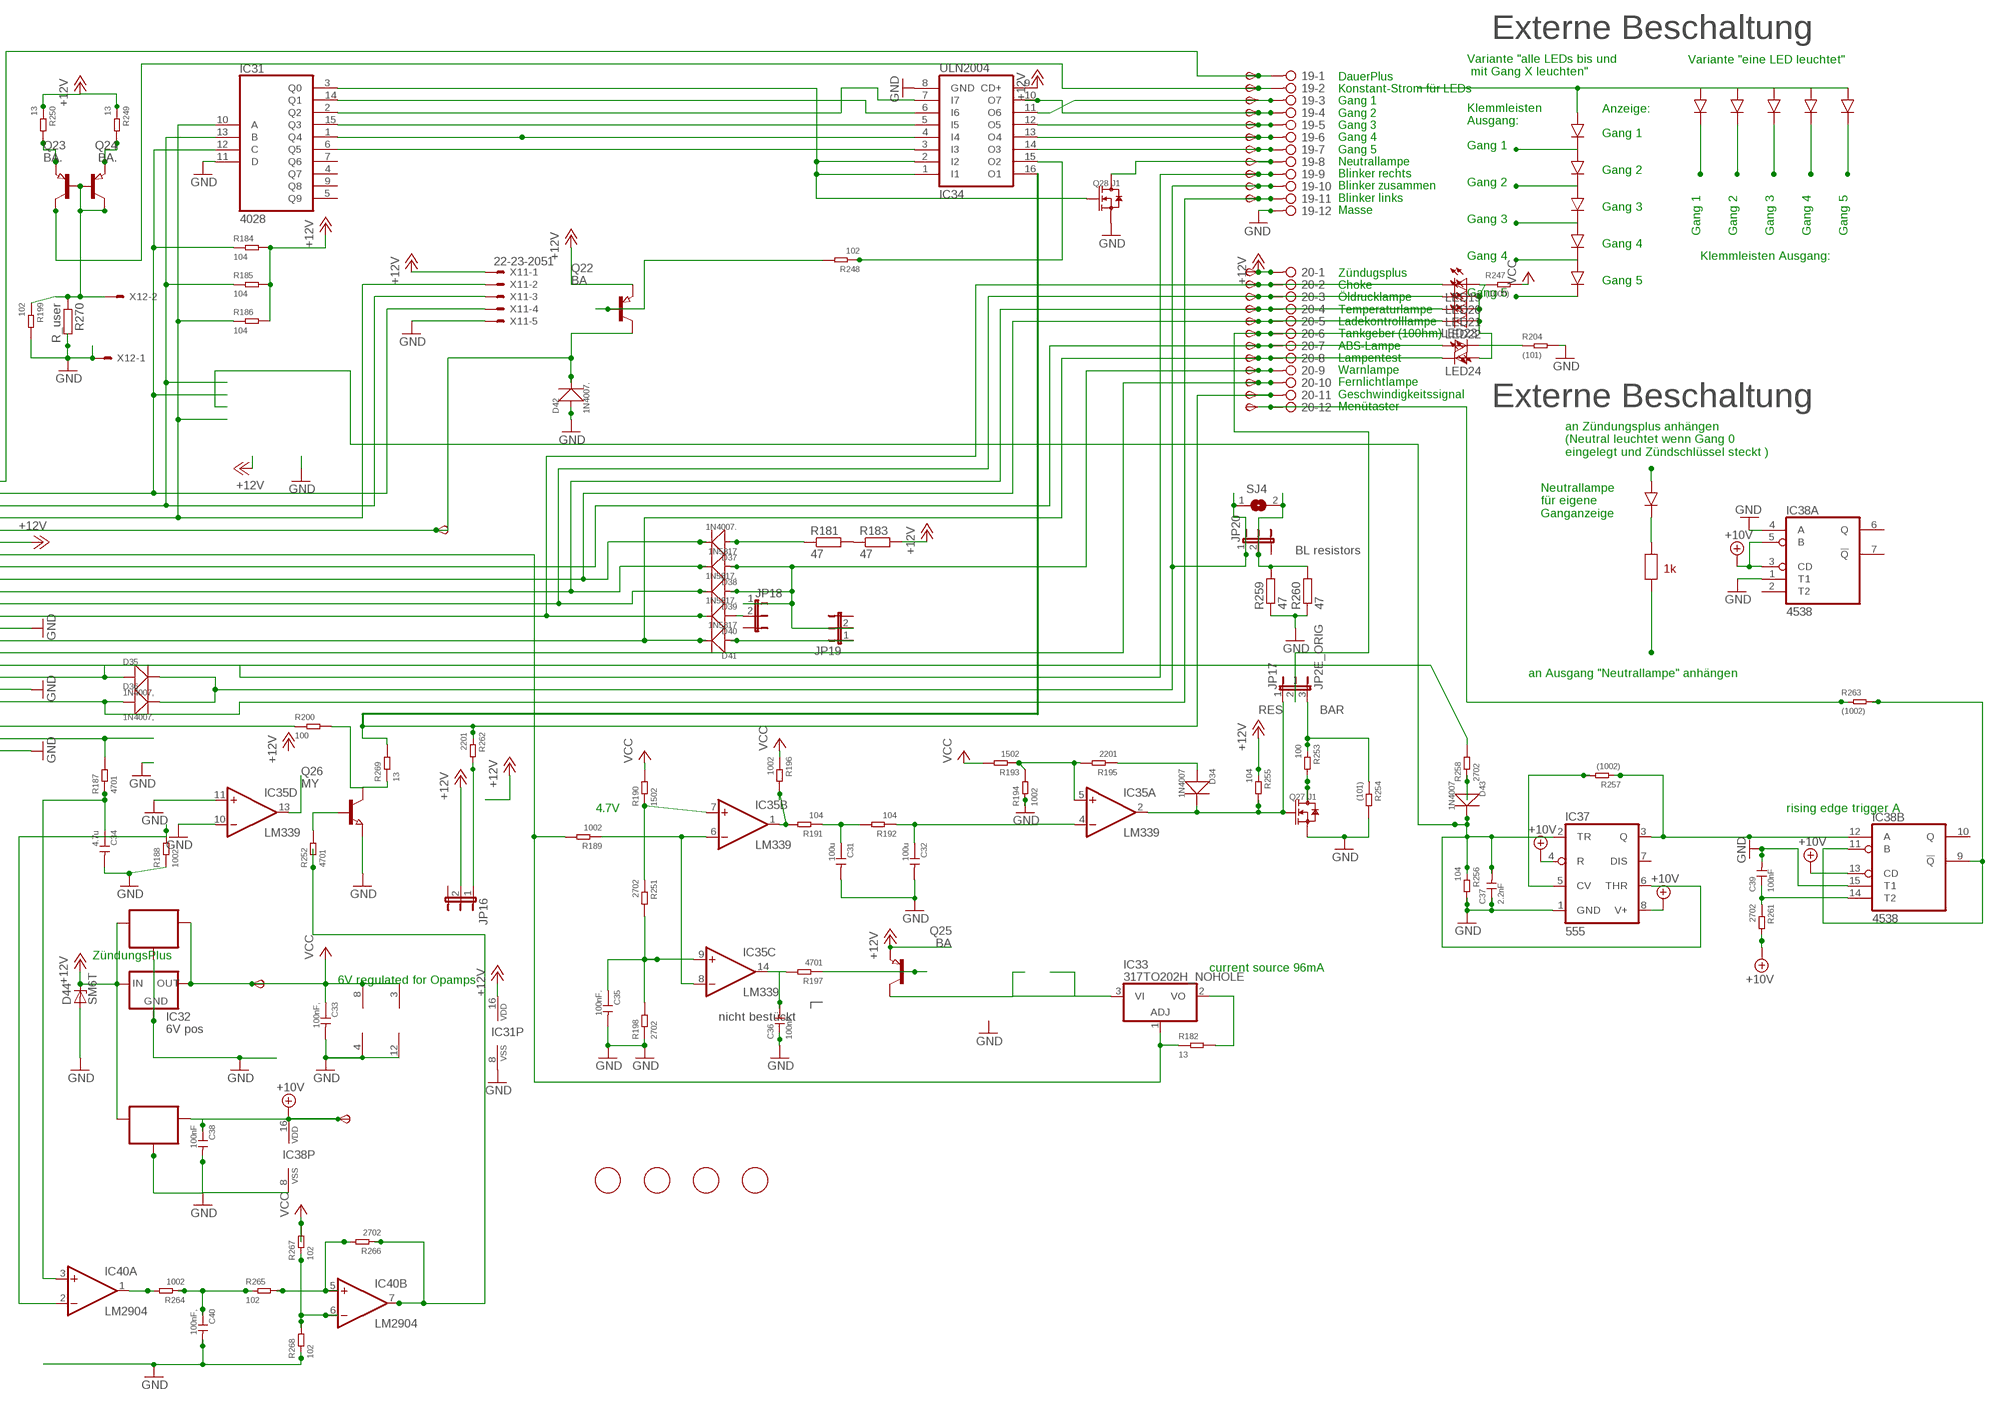
[diagram p19: schematic, sheet 10, part 2 of 2]
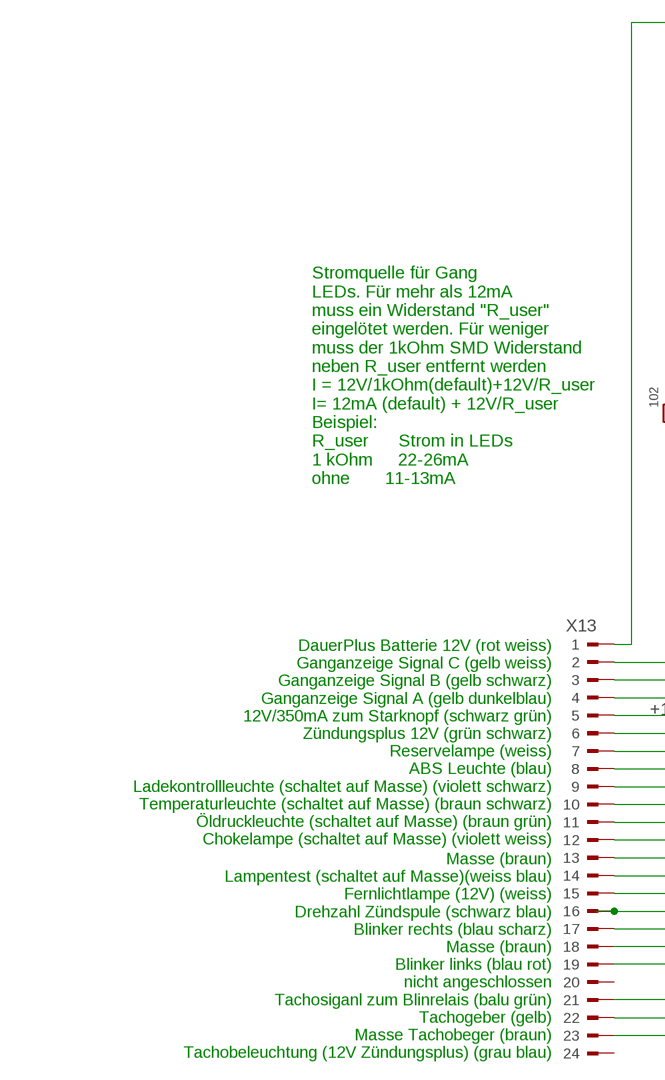
[diagram p20: schematic, sheet 11, part 1 of 2]
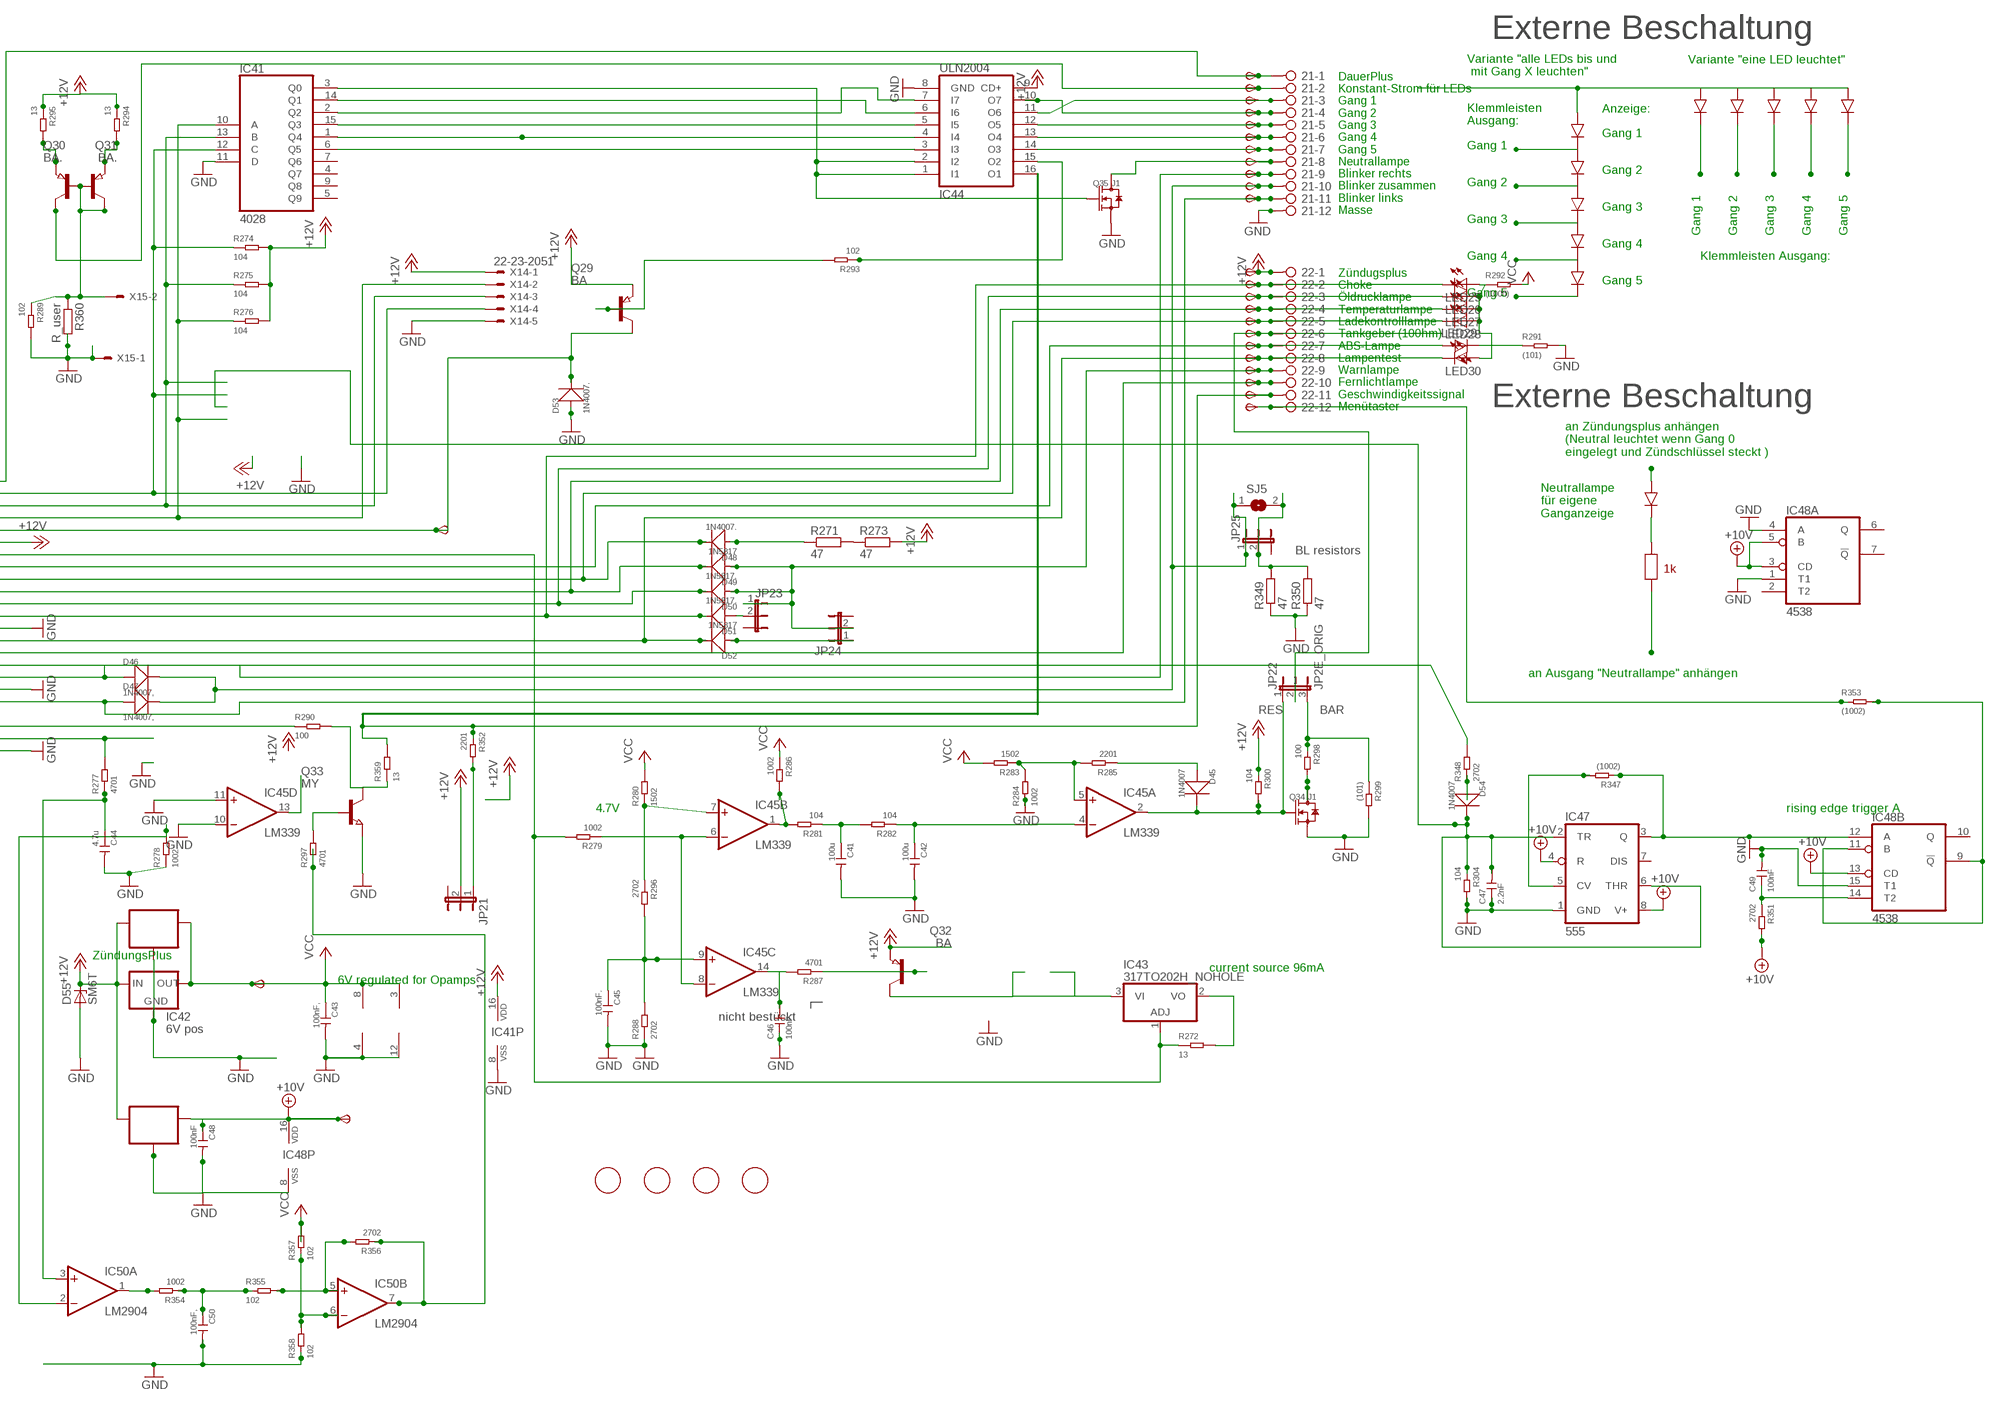
[diagram p21: schematic, sheet 11, part 2 of 2]
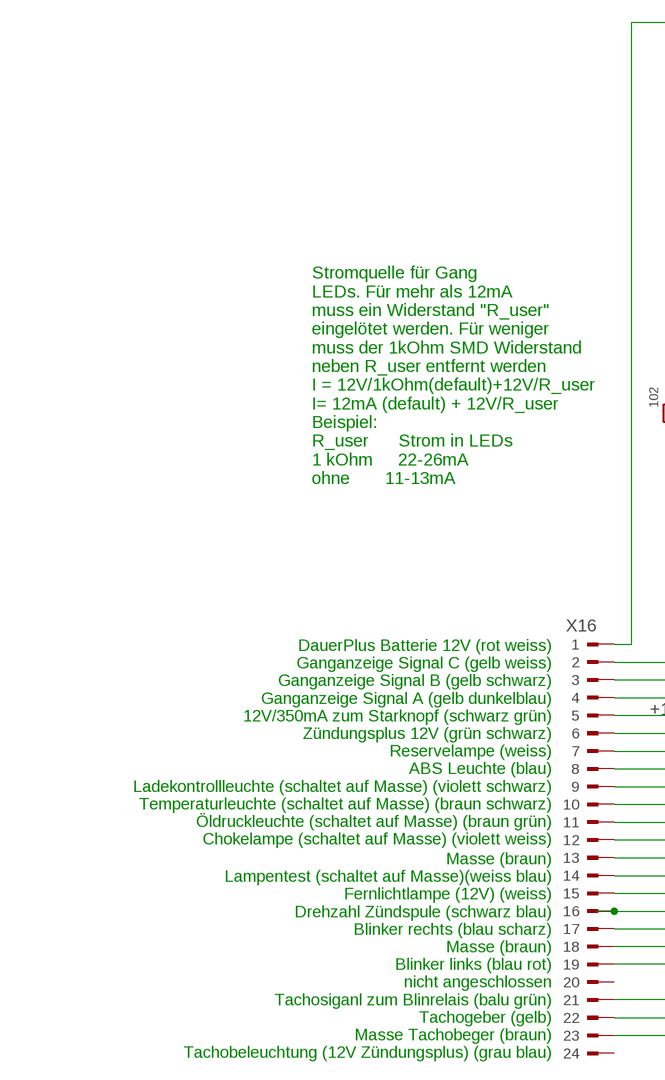
[diagram p22: schematic, sheet 12, part 1 of 2]
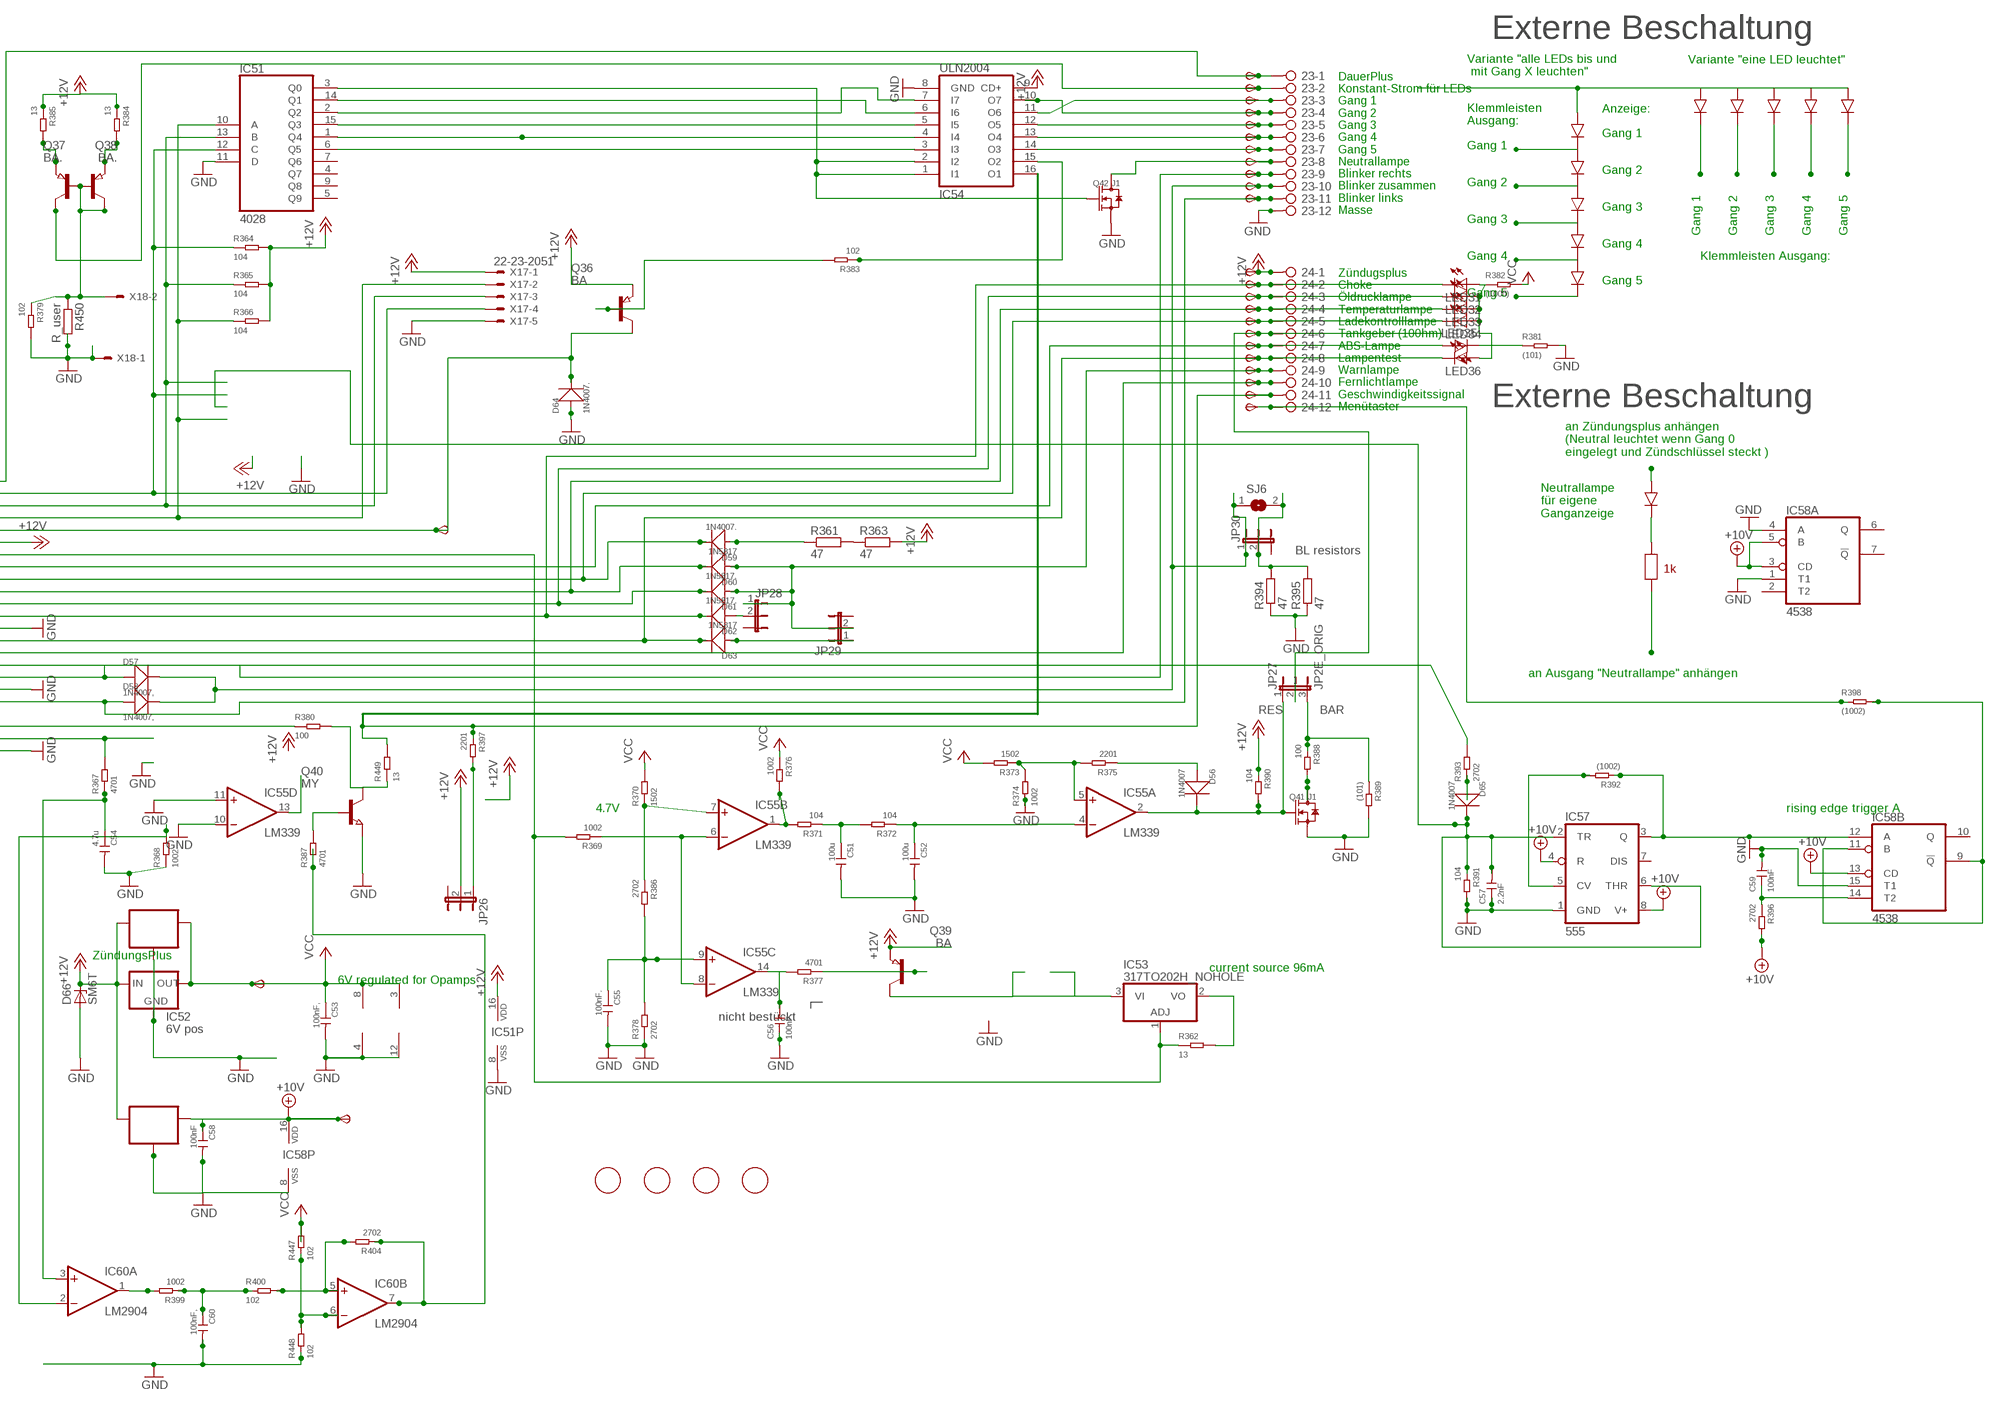
[diagram p23: schematic, sheet 12, part 2 of 2]

(export (version "E")
  (design (tool "Eeschema 10.0.6"))
  (components
    (comp (ref "6V501")
      (value "TPSB2.0")
      (footprint "eagle-import:B2.0")
      (libsource (lib "eagle-import") (part "TPSB2.0"))
    )
    (comp (ref "10V501")
      (value "TPSB2.0")
      (footprint "eagle-import:B2.0")
      (libsource (lib "eagle-import") (part "TPSB2.0"))
    )
    (comp (ref "15")
      (value "2081-1132")
      (footprint "eagle-import:12-PIN")
      (libsource (lib "eagle-import") (part "2081-1132"))
    )
    (comp (ref "16")
      (value "2081-1132")
      (footprint "eagle-import:12-PIN")
      (libsource (lib "eagle-import") (part "2081-1132"))
    )
    (comp (ref "C501")
      (value "4.7u")
      (footprint "eagle-import:C0805")
      (fields (field (name "MPN") "CC0805KKX5R8BB475"))
      (libsource (lib "eagle-import") (part "CERAMIC-4.7UF-25V-10%-X5R(0805)"))
    )
    (comp (ref "C502")
      (value "100nF")
      (footprint "eagle-import:C0805")
      (fields (field (name "MPN") "CC0805KRX7R9BB104"))
      (libsource (lib "eagle-import") (part "CERAMIC-100NF-50V-10%-X7R(0805)"))
    )
    (comp (ref "C503")
      (value "100nF,")
      (footprint "eagle-import:C0805")
      (fields (field (name "MPN") "CC0805KRX7R9BB104"))
      (libsource (lib "eagle-import") (part "CERAMIC-100NF-50V-10%-X7R(0805)"))
    )
    (comp (ref "C504")
      (value "100nF,")
      (footprint "eagle-import:C0805")
      (fields (field (name "MPN") "CC0805KRX7R9BB104"))
      (libsource (lib "eagle-import") (part "CERAMIC-100NF-50V-10%-X7R(0805)"))
    )
    (comp (ref "C505")
      (value "100nF.")
      (footprint "eagle-import:C0805")
      (fields (field (name "MPN") "CC0805KRX7R9BB104"))
      (libsource (lib "eagle-import") (part "CERAMIC-100NF-50V-10%-X7R(0805)"))
    )
    (comp (ref "C506")
      (value "100nF.")
      (footprint "eagle-import:C0805")
      (fields (field (name "MPN") "CC0805KRX7R9BB104"))
      (libsource (lib "eagle-import") (part "CERAMIC-100NF-50V-10%-X7R(0805)"))
    )
    (comp (ref "C507")
      (value "100u")
      (footprint "eagle-import:C1206")
      (fields (field (name "MPN") "GRM31CR60J107ME39L"))
      (libsource (lib "eagle-import") (part "CERAMIC-100UF-6.3V-20%-X5R(1206)"))
    )
    (comp (ref "C508")
      (value "100u")
      (footprint "eagle-import:C1206")
      (fields (field (name "MPN") "GRM31CR60J107ME39L"))
      (libsource (lib "eagle-import") (part "CERAMIC-100UF-6.3V-20%-X5R(1206)"))
    )
    (comp (ref "C509")
      (value "2.2nF")
      (footprint "eagle-import:C0805")
      (fields (field (name "MPN") "CC0805KRX7R9BB104"))
      (libsource (lib "eagle-import") (part "CERAMIC-100NF-50V-10%-X7R(0805)"))
    )
    (comp (ref "C510")
      (value "100nF")
      (footprint "eagle-import:C0805")
      (fields (field (name "MPN") "CC0805KRX7R9BB104"))
      (libsource (lib "eagle-import") (part "CERAMIC-100NF-50V-10%-X7R(0805)"))
    )
    (comp (ref "D501")
      (value "SM6T")
      (footprint "eagle-import:DO214AA")
      (libsource (lib "eagle-import") (part "SM6T"))
    )
    (comp (ref "D502")
      (value "1N4007,")
      (footprint "eagle-import:DO-214AC")
      (fields (field (name "MPN") "1N4007"))
      (libsource (lib "eagle-import") (part "DIODE-GEN-PURPOSE-1KV-1A(DO-214AC)"))
    )
    (comp (ref "D503")
      (value "1N4007,")
      (footprint "eagle-import:DO-214AC")
      (fields (field (name "MPN") "1N4007"))
      (libsource (lib "eagle-import") (part "DIODE-GEN-PURPOSE-1KV-1A(DO-214AC)"))
    )
    (comp (ref "D505")
      (value "1N4007.")
      (footprint "eagle-import:DO-214AC")
      (fields (field (name "MPN") "1N4007"))
      (libsource (lib "eagle-import") (part "DIODE-GEN-PURPOSE-1KV-1A(DO-214AC)"))
    )
    (comp (ref "D506")
      (value "1N4007.")
      (footprint "eagle-import:DO-214AC")
      (fields (field (name "MPN") "1N4007"))
      (libsource (lib "eagle-import") (part "DIODE-GEN-PURPOSE-1KV-1A(DO-214AC)"))
    )
    (comp (ref "D507")
      (value "1N5817")
      (footprint "eagle-import:DO-214AC_SLIM")
      (libsource (lib "eagle-import") (part "DIODE-GEN-PURPOSE-1KV-1A(DO-214AC)DO-214AC/1206"))
    )
    (comp (ref "D508")
      (value "1N5817.")
      (footprint "eagle-import:DO-214AC_SLIM")
      (libsource (lib "eagle-import") (part "DIODE-GEN-PURPOSE-1KV-1A(DO-214AC)DO-214AC/1206"))
    )
    (comp (ref "D509")
      (value "1N5817.")
      (footprint "eagle-import:DO-214AC_SLIM")
      (libsource (lib "eagle-import") (part "DIODE-GEN-PURPOSE-1KV-1A(DO-214AC)DO-214AC/1206"))
    )
    (comp (ref "D510")
      (value "1N5817")
      (footprint "eagle-import:DO-214AC_SLIM")
      (libsource (lib "eagle-import") (part "DIODE-GEN-PURPOSE-1KV-1A(DO-214AC)DO-214AC/1206"))
    )
    (comp (ref "D511")
      (value "1N4007")
      (footprint "eagle-import:DO-214AC")
      (libsource (lib "eagle-import") (part "DIODE-GEN-PURPOSE-1KV-1A(DO-214AC)"))
    )
    (comp (ref "D512")
      (value "1N4007")
      (footprint "eagle-import:DO-214AC")
      (libsource (lib "eagle-import") (part "DIODE-GEN-PURPOSE-1KV-1A(DO-214AC)"))
    )
    (comp (ref "FID501")
      (value "FIDUCIAL")
      (footprint "eagle-import:FIDUCIAL_1MM")
      (libsource (lib "eagle-import") (part "FIDUCIAL"))
    )
    (comp (ref "FID502")
      (value "FIDUCIAL")
      (footprint "eagle-import:FIDUCIAL_1MM")
      (libsource (lib "eagle-import") (part "FIDUCIAL"))
    )
    (comp (ref "FID503")
      (value "FIDUCIAL")
      (footprint "eagle-import:FIDUCIAL_1MM")
      (libsource (lib "eagle-import") (part "FIDUCIAL"))
    )
    (comp (ref "FID504")
      (value "FIDUCIAL")
      (footprint "eagle-import:FIDUCIAL_1MM")
      (libsource (lib "eagle-import") (part "FIDUCIAL"))
    )
    (comp (ref "IC501")
      (value "LM2904")
      (footprint "eagle-import:SO08")
      (libsource (lib "eagle-import") (part "LM358D"))
    )
    (comp (ref "IC502")
      (value "78L06")
      (footprint "eagle-import:SOT89_ROUND")
      (libsource (lib "eagle-import") (part "78LXXSOT89_ROUND"))
    )
    (comp (ref "IC503")
      (value "6V pos")
      (footprint "eagle-import:78LXX")
      (libsource (lib "eagle-import") (part "v-reg_78LXX"))
    )
    (comp (ref "IC504")
      (value "78L10")
      (footprint "eagle-import:SOT89_ROUND")
      (libsource (lib "eagle-import") (part "78LXXSOT89_ROUND"))
    )
    (comp (ref "IC505")
      (value "4028")
      (footprint "eagle-import:SO16")
      (libsource (lib "eagle-import") (part "4028D"))
    )
    (comp (ref "IC507")
      (value "ULN2004")
      (footprint "eagle-import:SO16")
      (libsource (lib "eagle-import") (part "ULN2004AD"))
    )
    (comp (ref "IC508")
      (value "LM339")
      (footprint "eagle-import:SO14")
      (libsource (lib "eagle-import") (part "LM339D"))
    )
    (comp (ref "IC509")
      (value "317TO202H_NOHOLE")
      (footprint "eagle-import:TO220H_NOHOLE")
      (libsource (lib "eagle-import") (part "317TO202H_NOHOLE"))
    )
    (comp (ref "IC510")
      (value "555")
      (footprint "eagle-import:SO08")
      (libsource (lib "eagle-import") (part "555DNE"))
    )
    (comp (ref "IC511")
      (value "4538")
      (footprint "eagle-import:SO16")
      (libsource (lib "eagle-import") (part "4538D"))
    )
    (comp (ref "JP501")
      (value "JP2EJP2_SMALLPADS")
      (footprint "eagle-import:JP2_SMALLPADS")
      (libsource (lib "eagle-import") (part "JP2EJP2_SMALLPADS"))
    )
    (comp (ref "JP502")
      (value "JP2EJP2_SMALLPADS")
      (footprint "eagle-import:JP2_SMALLPADS")
      (libsource (lib "eagle-import") (part "JP2EJP2_SMALLPADS"))
    )
    (comp (ref "JP503")
      (value "JP2EJP2_SMALLPADS")
      (footprint "eagle-import:JP2_SMALLPADS")
      (libsource (lib "eagle-import") (part "JP2EJP2_SMALLPADS"))
    )
    (comp (ref "JP504")
      (value "JP2EJP2_SMALLPADS")
      (footprint "eagle-import:JP2_SMALLPADS")
      (libsource (lib "eagle-import") (part "JP2EJP2_SMALLPADS"))
    )
    (comp (ref "JP505")
      (value "JP2E_ORIG")
      (footprint "eagle-import:JP2_ORIG_SMALLPADS")
      (libsource (lib "eagle-import") (part "JP2E_ORIG"))
    )
    (comp (ref "LED501")
      (value "LEDLD260")
      (footprint "eagle-import:LD260")
      (libsource (lib "eagle-import") (part "LEDLD260"))
    )
    (comp (ref "LED502")
      (value "LEDLD260")
      (footprint "eagle-import:LD260")
      (libsource (lib "eagle-import") (part "LEDLD260"))
    )
    (comp (ref "LED503")
      (value "LEDLD260")
      (footprint "eagle-import:LD260")
      (libsource (lib "eagle-import") (part "LEDLD260"))
    )
    (comp (ref "LED504")
      (value "LEDLD260")
      (footprint "eagle-import:LD260")
      (libsource (lib "eagle-import") (part "LEDLD260"))
    )
    (comp (ref "LED505")
      (value "LEDLD260")
      (footprint "eagle-import:LD260")
      (libsource (lib "eagle-import") (part "LEDLD260"))
    )
    (comp (ref "LED506")
      (value "LEDLD260")
      (footprint "eagle-import:LD260")
      (libsource (lib "eagle-import") (part "LEDLD260"))
    )
    (comp (ref "Q501")
      (value "BA.")
      (footprint "eagle-import:SOT89")
      (libsource (lib "eagle-import") (part "PNP-TRANSISTOR_SOT89"))
    )
    (comp (ref "Q502")
      (value "BA.")
      (footprint "eagle-import:SOT89")
      (libsource (lib "eagle-import") (part "PNP-TRANSISTOR_SOT89"))
    )
    (comp (ref "Q503")
      (value "MY")
      (footprint "eagle-import:SOT89")
      (libsource (lib "eagle-import") (part "NPN-TRANSISTOR_SOT89"))
    )
    (comp (ref "Q504")
      (value "BA")
      (footprint "eagle-import:SOT89")
      (libsource (lib "eagle-import") (part "PNP-TRANSISTOR_SOT89"))
    )
    (comp (ref "Q505")
      (value "BA")
      (footprint "eagle-import:SOT89")
      (libsource (lib "eagle-import") (part "PNP-TRANSISTOR_SOT89"))
    )
    (comp (ref "Q506")
      (value "J1")
      (footprint "eagle-import:SOT-23")
      (fields (field (name "MPN") "BSS138W-7-F"))
      (libsource (lib "eagle-import") (part "SMD-MOSFET-N-CH-50V-200MA-BSS138W-7-F(SOT-23)"))
    )
    (comp (ref "Q507")
      (value "J1")
      (footprint "eagle-import:SOT-23")
      (fields (field (name "MPN") "BSS138W-7-F"))
      (libsource (lib "eagle-import") (part "SMD-MOSFET-N-CH-50V-200MA-BSS138W-7-F(SOT-23)"))
    )
    (comp (ref "R501")
      (value "102")
      (footprint "eagle-import:R0805")
      (fields (field (name "MPN") "RC0805JR-071KL"))
      (libsource (lib "eagle-import") (part "SMD-RES-1K-5%-1/8W(0805)"))
    )
    (comp (ref "R502")
      (value "13")
      (footprint "eagle-import:R1206")
      (fields (field (name "MPN") "RC1206JR-0713RL"))
      (libsource (lib "eagle-import") (part "SMD-RES-13R-5%-1/4W(1206)"))
    )
    (comp (ref "R503")
      (value "R_user")
      (footprint "eagle-import:R0805")
      (libsource (lib "eagle-import") (part "R-EU_R0805"))
    )
    (comp (ref "R505")
      (value "4701")
      (footprint "eagle-import:R0805")
      (fields (field (name "MPN") "RC0805JR-074K7L"))
      (libsource (lib "eagle-import") (part "SMD-RES-4.7K-5%-1/8W(0805)"))
    )
    (comp (ref "R506")
      (value "13")
      (footprint "eagle-import:R1206")
      (fields (field (name "MPN") "RC1206JR-0713RL"))
      (libsource (lib "eagle-import") (part "SMD-RES-13R-5%-1/4W(1206)"))
    )
    (comp (ref "R507")
      (value "1002")
      (footprint "eagle-import:R0805")
      (fields (field (name "MPN") "RC0805FR-0710KL"))
      (libsource (lib "eagle-import") (part "SMD-RES-10K-1%-1/8W(0805)"))
    )
    (comp (ref "R508")
      (value "1002")
      (footprint "eagle-import:R0805")
      (fields (field (name "MPN") "RC0805FR-0710KL"))
      (libsource (lib "eagle-import") (part "SMD-RES-10K-1%-1/8W(0805)"))
    )
    (comp (ref "R509")
      (value "104")
      (footprint "eagle-import:R0805")
      (fields (field (name "MPN") "RC0805FR-0710KL"))
      (libsource (lib "eagle-import") (part "SMD-RES-10K-1%-1/8W(0805)"))
    )
    (comp (ref "R510")
      (value "104")
      (footprint "eagle-import:R0805")
      (fields (field (name "MPN") "RC0805FR-0710KL"))
      (libsource (lib "eagle-import") (part "SMD-RES-10K-1%-1/8W(0805)"))
    )
    (comp (ref "R511")
      (value "104")
      (footprint "eagle-import:R0805")
      (fields (field (name "MPN") "RC0805FR-0710KL"))
      (libsource (lib "eagle-import") (part "SMD-RES-10K-1%-1/8W(0805)"))
    )
    (comp (ref "R512")
      (value "102")
      (footprint "eagle-import:R0805")
      (fields (field (name "MPN") "RC0805JR-071KL"))
      (libsource (lib "eagle-import") (part "SMD-RES-1K-5%-1/8W(0805)"))
    )
    (comp (ref "R513")
      (value "102")
      (footprint "eagle-import:R0805")
      (fields (field (name "MPN") "RC0805JR-071KL"))
      (libsource (lib "eagle-import") (part "SMD-RES-1K-5%-1/8W(0805)"))
    )
    (comp (ref "R514")
      (value "102")
      (footprint "eagle-import:R0805")
      (fields (field (name "MPN") "RC0805JR-071KL"))
      (libsource (lib "eagle-import") (part "SMD-RES-1K-5%-1/8W(0805)"))
    )
    (comp (ref "R515")
      (value "100")
      (footprint "eagle-import:R0805")
      (fields (field (name "MPN") "RC0805JR-07220RL"))
      (libsource (lib "eagle-import") (part "SMD-RES-220R-5%-1/8W(0805)"))
    )
    (comp (ref "R516")
      (value "4701")
      (footprint "eagle-import:R0805")
      (fields (field (name "MPN") "RC0805JR-074K7L"))
      (libsource (lib "eagle-import") (part "SMD-RES-4.7K-5%-1/8W(0805)"))
    )
    (comp (ref "R517")
      (value "2702")
      (footprint "eagle-import:R0805")
      (fields (field (name "MPN") "RC0805JR-074K7L"))
      (libsource (lib "eagle-import") (part "SMD-RES-4.7K-5%-1/8W(0805)"))
    )
    (comp (ref "R518")
      (value "13")
      (footprint "eagle-import:R1206")
      (fields (field (name "MPN") "RC1206JR-0713RL"))
      (libsource (lib "eagle-import") (part "SMD-RES-13R-5%-1/4W(1206)"))
    )
    (comp (ref "R519")
      (value "2201")
      (footprint "eagle-import:R0805")
      (fields (field (name "MPN") "RC0805JR-072K2L"))
      (libsource (lib "eagle-import") (part "SMD-RES-2.2K-5%-1/8W(0805)"))
    )
    (comp (ref "R520")
      (value "1002")
      (footprint "eagle-import:R0805")
      (fields (field (name "MPN") "RC0805FR-0710KL"))
      (libsource (lib "eagle-import") (part "SMD-RES-10K-1%-1/8W(0805)"))
    )
    (comp (ref "R521")
      (value "1502")
      (footprint "eagle-import:R0805")
      (fields (field (name "MPN") "RC0805FR-0710KL"))
      (libsource (lib "eagle-import") (part "SMD-RES-10K-1%-1/8W(0805)"))
    )
    (comp (ref "R522")
      (value "2702")
      (footprint "eagle-import:R0805")
      (fields (field (name "MPN") "RC0805JR-074K7L"))
      (libsource (lib "eagle-import") (part "SMD-RES-4.7K-5%-1/8W(0805)"))
    )
    (comp (ref "R523")
      (value "2702")
      (footprint "eagle-import:R0805")
      (fields (field (name "MPN") "RC0805JR-074K7L"))
      (libsource (lib "eagle-import") (part "SMD-RES-4.7K-5%-1/8W(0805)"))
    )
    (comp (ref "R524")
      (value "1002")
      (footprint "eagle-import:R0805")
      (fields (field (name "MPN") "RC0805FR-0710KL"))
      (libsource (lib "eagle-import") (part "SMD-RES-10K-1%-1/8W(0805)"))
    )
    (comp (ref "R525")
      (value "104")
      (footprint "eagle-import:R0805")
      (fields (field (name "MPN") "RC0805FR-0710KL"))
      (libsource (lib "eagle-import") (part "SMD-RES-10K-1%-1/8W(0805)"))
    )
    (comp (ref "R526")
      (value "4701")
      (footprint "eagle-import:R0805")
      (fields (field (name "MPN") "RC0805JR-074K7L"))
      (libsource (lib "eagle-import") (part "SMD-RES-4.7K-5%-1/8W(0805)"))
    )
    (comp (ref "R527")
      (value "47")
      (footprint "eagle-import:V235_17_1MM")
      (libsource (lib "eagle-import") (part "R-EU_V235/17_1MM"))
    )
    (comp (ref "R528")
      (value "102")
      (footprint "eagle-import:R0805")
      (fields (field (name "MPN") "RC0805JR-071KL"))
      (libsource (lib "eagle-import") (part "SMD-RES-1K-5%-1/8W(0805)"))
    )
    (comp (ref "R529")
      (value "47")
      (footprint "eagle-import:V235_17_1MM")
      (libsource (lib "eagle-import") (part "R-EU_V235/17_1MM"))
    )
    (comp (ref "R530")
      (value "104")
      (footprint "eagle-import:R0805")
      (fields (field (name "MPN") "RC0805FR-0710KL"))
      (libsource (lib "eagle-import") (part "SMD-RES-10K-1%-1/8W(0805)"))
    )
    (comp (ref "R531")
      (value "1502")
      (footprint "eagle-import:R0805")
      (fields (field (name "MPN") "RC0805FR-0710KL"))
      (libsource (lib "eagle-import") (part "SMD-RES-10K-1%-1/8W(0805)"))
    )
    (comp (ref "R532")
      (value "1002")
      (footprint "eagle-import:R0805")
      (fields (field (name "MPN") "RC0805FR-0710KL"))
      (libsource (lib "eagle-import") (part "SMD-RES-10K-1%-1/8W(0805)"))
    )
    (comp (ref "R533")
      (value "2201")
      (footprint "eagle-import:R0805")
      (fields (field (name "MPN") "RC0805JR-072K2L"))
      (libsource (lib "eagle-import") (part "SMD-RES-2.2K-5%-1/8W(0805)"))
    )
    (comp (ref "R534")
      (value "13")
      (footprint "eagle-import:R1206")
      (fields (field (name "MPN") "RC1206JR-0713RL"))
      (libsource (lib "eagle-import") (part "SMD-RES-13R-5%-1/4W(1206)"))
    )
    (comp (ref "R535")
      (value "104")
      (footprint "eagle-import:R0805")
      (fields (field (name "MPN") "RC0805FR-0710KL"))
      (libsource (lib "eagle-import") (part "SMD-RES-10K-1%-1/8W(0805)"))
    )
    (comp (ref "R536")
      (value "47")
      (footprint "eagle-import:V235_17_1MM")
      (libsource (lib "eagle-import") (part "R-EU_V235/17_1MM"))
    )
    (comp (ref "R537")
      (value "47")
      (footprint "eagle-import:V235_17_1MM")
      (libsource (lib "eagle-import") (part "R-EU_V235/17_1MM"))
    )
    (comp (ref "R538")
      (value "100")
      (footprint "eagle-import:R0805")
      (fields (field (name "MPN") "RC0805JR-072K2L"))
      (libsource (lib "eagle-import") (part "SMD-RES-2.2K-5%-1/8W(0805)"))
    )
    (comp (ref "R539")
      (value "(101)")
      (footprint "eagle-import:R0805")
      (fields (field (name "MPN") "RC0805JR-072K2L"))
      (libsource (lib "eagle-import") (part "SMD-RES-2.2K-5%-1/8W(0805)"))
    )
    (comp (ref "R540")
      (value "2702")
      (footprint "eagle-import:R0805")
      (fields (field (name "MPN") "RC0805FR-0710KL"))
      (libsource (lib "eagle-import") (part "SMD-RES-10K-1%-1/8W(0805)"))
    )
    (comp (ref "R541")
      (value "104")
      (footprint "eagle-import:R0805")
      (fields (field (name "MPN") "RC0805FR-0710KL"))
      (libsource (lib "eagle-import") (part "SMD-RES-10K-1%-1/8W(0805)"))
    )
    (comp (ref "R542")
      (value "(1000)")
      (footprint "eagle-import:R0805")
      (fields (field (name "MPN") "RC0805JR-07100RL"))
      (libsource (lib "eagle-import") (part "SMD-RES-100R-5%-1/8W(0805)"))
    )
    (comp (ref "R543")
      (value "(101)")
      (footprint "eagle-import:R0805")
      (fields (field (name "MPN") "RC0805JR-07100RL"))
      (libsource (lib "eagle-import") (part "SMD-RES-100R-5%-1/8W(0805)"))
    )
    (comp (ref "R544")
      (value "(1002)")
      (footprint "eagle-import:R0805")
      (fields (field (name "MPN") "RC0805FR-0710KL"))
      (libsource (lib "eagle-import") (part "SMD-RES-10K-1%-1/8W(0805)"))
    )
    (comp (ref "R545")
      (value "2702")
      (footprint "eagle-import:R0805")
      (fields (field (name "MPN") "RC0805JR-074K7L"))
      (libsource (lib "eagle-import") (part "SMD-RES-4.7K-5%-1/8W(0805)"))
    )
    (comp (ref "R546")
      (value "(1002)")
      (footprint "eagle-import:R0805")
      (fields (field (name "MPN") "RC0805JR-074K7L"))
      (libsource (lib "eagle-import") (part "SMD-RES-4.7K-5%-1/8W(0805)"))
    )
    (comp (ref "SJ501")
      (value "SJ")
      (footprint "eagle-import:SJ")
      (libsource (lib "eagle-import") (part "SJ"))
    )
    (comp (ref "START501")
      (value "TPSB2.0")
      (footprint "eagle-import:B2.0")
      (libsource (lib "eagle-import") (part "TPSB2.0"))
    )
    (comp (ref "TP162")
      (value "TPSB2.0")
      (footprint "eagle-import:B2.0")
      (libsource (lib "eagle-import") (part "TPSB2.0"))
    )
    (comp (ref "TP163")
      (value "TPSB2.0")
      (footprint "eagle-import:B2.0")
      (libsource (lib "eagle-import") (part "TPSB2.0"))
    )
    (comp (ref "TP164")
      (value "TPSB2.0")
      (footprint "eagle-import:B2.0")
      (libsource (lib "eagle-import") (part "TPSB2.0"))
    )
    (comp (ref "TP165")
      (value "TPSB2.0")
      (footprint "eagle-import:B2.0")
      (libsource (lib "eagle-import") (part "TPSB2.0"))
    )
    (comp (ref "TP166")
      (value "TPSB2.0")
      (footprint "eagle-import:B2.0")
      (libsource (lib "eagle-import") (part "TPSB2.0"))
    )
    (comp (ref "TP167")
      (value "TPSB2.0")
      (footprint "eagle-import:B2.0")
      (libsource (lib "eagle-import") (part "TPSB2.0"))
    )
    (comp (ref "TP168")
      (value "TPSB2.0")
      (footprint "eagle-import:B2.0")
      (libsource (lib "eagle-import") (part "TPSB2.0"))
    )
    (comp (ref "TP169")
      (value "TPSB2.0")
      (footprint "eagle-import:B2.0")
      (libsource (lib "eagle-import") (part "TPSB2.0"))
    )
    (comp (ref "TP170")
      (value "TPSB2.0")
      (footprint "eagle-import:B2.0")
      (libsource (lib "eagle-import") (part "TPSB2.0"))
    )
    (comp (ref "TP171")
      (value "TPSB2.0")
      (footprint "eagle-import:B2.0")
      (libsource (lib "eagle-import") (part "TPSB2.0"))
    )
    (comp (ref "TP172")
      (value "TPSB2.0")
      (footprint "eagle-import:B2.0")
      (libsource (lib "eagle-import") (part "TPSB2.0"))
    )
    (comp (ref "TP173")
      (value "TPSB2.0")
      (footprint "eagle-import:B2.0")
      (libsource (lib "eagle-import") (part "TPSB2.0"))
    )
    (comp (ref "TP174")
      (value "TPSB2.0")
      (footprint "eagle-import:B2.0")
      (libsource (lib "eagle-import") (part "TPSB2.0"))
    )
    (comp (ref "TP175")
      (value "TPSB2.0")
      (footprint "eagle-import:B2.0")
      (libsource (lib "eagle-import") (part "TPSB2.0"))
    )
    (comp (ref "TP176")
      (value "TPSB2.0")
      (footprint "eagle-import:B2.0")
      (libsource (lib "eagle-import") (part "TPSB2.0"))
    )
    (comp (ref "TP177")
      (value "TPSB2.0")
      (footprint "eagle-import:B2.0")
      (libsource (lib "eagle-import") (part "TPSB2.0"))
    )
    (comp (ref "TP178")
      (value "TPSB2.0")
      (footprint "eagle-import:B2.0")
      (libsource (lib "eagle-import") (part "TPSB2.0"))
    )
    (comp (ref "TP179")
      (value "TPSB2.0")
      (footprint "eagle-import:B2.0")
      (libsource (lib "eagle-import") (part "TPSB2.0"))
    )
    (comp (ref "TP180")
      (value "TPSB1,27")
      (footprint "eagle-import:B1,27")
      (libsource (lib "eagle-import") (part "TPSB1,27"))
    )
    (comp (ref "TP181")
      (value "TPSB2.0")
      (footprint "eagle-import:B2.0")
      (libsource (lib "eagle-import") (part "TPSB2.0"))
    )
    (comp (ref "TP182")
      (value "TPSB2.0")
      (footprint "eagle-import:B2.0")
      (libsource (lib "eagle-import") (part "TPSB2.0"))
    )
    (comp (ref "TP183")
      (value "TPSB2.0")
      (footprint "eagle-import:B2.0")
      (libsource (lib "eagle-import") (part "TPSB2.0"))
    )
    (comp (ref "TP184")
      (value "TPSB2.0")
      (footprint "eagle-import:B2.0")
      (libsource (lib "eagle-import") (part "TPSB2.0"))
    )
    (comp (ref "X501")
      (value "CON_BMWV2")
      (footprint "eagle-import:24-PIN_V2")
      (libsource (lib "eagle-import") (part "CON_BMWV2"))
    )
    (comp (ref "X502")
      (value "22-23-2021")
      (footprint "eagle-import:22-23-2021")
      (fields (field (name "MF") "MOLEX"))
      (libsource (lib "eagle-import") (part "22-23-2021"))
    )
    (comp (ref "X503")
      (value "22-23-2051")
      (footprint "eagle-import:22-23-2051")
      (fields (field (name "MF") "MOLEX"))
      (libsource (lib "eagle-import") (part "22-23-2051"))
    )
    (comp (ref "6V2")
      (value "TPSB2.0")
      (footprint "eagle-import:B2.0")
      (libsource (lib "eagle-import") (part "TPSB2.0"))
    )
    (comp (ref "9")
      (value "2081-1132")
      (footprint "eagle-import:12-PIN")
      (libsource (lib "eagle-import") (part "2081-1132"))
    )
    (comp (ref "10")
      (value "2081-1132")
      (footprint "eagle-import:12-PIN")
      (libsource (lib "eagle-import") (part "2081-1132"))
    )
    (comp (ref "10V2")
      (value "TPSB2.0")
      (footprint "eagle-import:B2.0")
      (libsource (lib "eagle-import") (part "TPSB2.0"))
    )
    (comp (ref "C11")
      (value "100u")
      (footprint "eagle-import:C1206")
      (fields (field (name "MPN") "GRM31CR60J107ME39L"))
      (libsource (lib "eagle-import") (part "CERAMIC-100UF-6.3V-20%-X5R(1206)"))
    )
    (comp (ref "C12")
      (value "100u")
      (footprint "eagle-import:C1206")
      (fields (field (name "MPN") "GRM31CR60J107ME39L"))
      (libsource (lib "eagle-import") (part "CERAMIC-100UF-6.3V-20%-X5R(1206)"))
    )
    (comp (ref "C13")
      (value "100nF,")
      (footprint "eagle-import:C0805")
      (fields (field (name "MPN") "CC0805KRX7R9BB104"))
      (libsource (lib "eagle-import") (part "CERAMIC-100NF-50V-10%-X7R(0805)"))
    )
    (comp (ref "C14")
      (value "4.7u")
      (footprint "eagle-import:C0805")
      (fields (field (name "MPN") "CC0805KKX5R8BB475"))
      (libsource (lib "eagle-import") (part "CERAMIC-4.7UF-25V-10%-X5R(0805)"))
    )
    (comp (ref "C15")
      (value "100nF.")
      (footprint "eagle-import:C0805")
      (fields (field (name "MPN") "CC0805KRX7R9BB104"))
      (libsource (lib "eagle-import") (part "CERAMIC-100NF-50V-10%-X7R(0805)"))
    )
    (comp (ref "C16")
      (value "100nF.")
      (footprint "eagle-import:C0805")
      (fields (field (name "MPN") "CC0805KRX7R9BB104"))
      (libsource (lib "eagle-import") (part "CERAMIC-100NF-50V-10%-X7R(0805)"))
    )
    (comp (ref "C17")
      (value "2.2nF")
      (footprint "eagle-import:C0805")
      (fields (field (name "MPN") "CC0805KRX7R9BB104"))
      (libsource (lib "eagle-import") (part "CERAMIC-100NF-50V-10%-X7R(0805)"))
    )
    (comp (ref "C18")
      (value "100nF")
      (footprint "eagle-import:C0805")
      (fields (field (name "MPN") "CC0805KRX7R9BB104"))
      (libsource (lib "eagle-import") (part "CERAMIC-100NF-50V-10%-X7R(0805)"))
    )
    (comp (ref "C19")
      (value "100nF")
      (footprint "eagle-import:C0805")
      (fields (field (name "MPN") "CC0805KRX7R9BB104"))
      (libsource (lib "eagle-import") (part "CERAMIC-100NF-50V-10%-X7R(0805)"))
    )
    (comp (ref "C20")
      (value "100nF,")
      (footprint "eagle-import:C0805")
      (fields (field (name "MPN") "CC0805KRX7R9BB104"))
      (libsource (lib "eagle-import") (part "CERAMIC-100NF-50V-10%-X7R(0805)"))
    )
    (comp (ref "D12")
      (value "1N4007")
      (footprint "eagle-import:DO-214AC")
      (libsource (lib "eagle-import") (part "DIODE-GEN-PURPOSE-1KV-1A(DO-214AC)"))
    )
    (comp (ref "D13")
      (value "1N4007,")
      (footprint "eagle-import:DO-214AC")
      (fields (field (name "MPN") "1N4007"))
      (libsource (lib "eagle-import") (part "DIODE-GEN-PURPOSE-1KV-1A(DO-214AC)"))
    )
    (comp (ref "D14")
      (value "1N4007,")
      (footprint "eagle-import:DO-214AC")
      (fields (field (name "MPN") "1N4007"))
      (libsource (lib "eagle-import") (part "DIODE-GEN-PURPOSE-1KV-1A(DO-214AC)"))
    )
    (comp (ref "D15")
      (value "1N4007.")
      (footprint "eagle-import:DO-214AC")
      (fields (field (name "MPN") "1N4007"))
      (libsource (lib "eagle-import") (part "DIODE-GEN-PURPOSE-1KV-1A(DO-214AC)"))
    )
    (comp (ref "D16")
      (value "1N5817")
      (footprint "eagle-import:DO-214AC_SLIM")
      (libsource (lib "eagle-import") (part "DIODE-GEN-PURPOSE-1KV-1A(DO-214AC)DO-214AC/1206"))
    )
    (comp (ref "D17")
      (value "1N5817.")
      (footprint "eagle-import:DO-214AC_SLIM")
      (libsource (lib "eagle-import") (part "DIODE-GEN-PURPOSE-1KV-1A(DO-214AC)DO-214AC/1206"))
    )
    (comp (ref "D18")
      (value "1N5817.")
      (footprint "eagle-import:DO-214AC_SLIM")
      (libsource (lib "eagle-import") (part "DIODE-GEN-PURPOSE-1KV-1A(DO-214AC)DO-214AC/1206"))
    )
    (comp (ref "D19")
      (value "1N5817")
      (footprint "eagle-import:DO-214AC_SLIM")
      (libsource (lib "eagle-import") (part "DIODE-GEN-PURPOSE-1KV-1A(DO-214AC)DO-214AC/1206"))
    )
    (comp (ref "D20")
      (value "1N4007.")
      (footprint "eagle-import:DO-214AC")
      (fields (field (name "MPN") "1N4007"))
      (libsource (lib "eagle-import") (part "DIODE-GEN-PURPOSE-1KV-1A(DO-214AC)"))
    )
    (comp (ref "D21")
      (value "1N4007")
      (footprint "eagle-import:DO-214AC")
      (libsource (lib "eagle-import") (part "DIODE-GEN-PURPOSE-1KV-1A(DO-214AC)"))
    )
    (comp (ref "D22")
      (value "SM6T")
      (footprint "eagle-import:DO214AA")
      (libsource (lib "eagle-import") (part "SM6T"))
    )
    (comp (ref "FID7")
      (value "FIDUCIAL")
      (footprint "eagle-import:FIDUCIAL_1MM")
      (libsource (lib "eagle-import") (part "FIDUCIAL"))
    )
    (comp (ref "FID8")
      (value "FIDUCIAL")
      (footprint "eagle-import:FIDUCIAL_1MM")
      (libsource (lib "eagle-import") (part "FIDUCIAL"))
    )
    (comp (ref "FID9")
      (value "FIDUCIAL")
      (footprint "eagle-import:FIDUCIAL_1MM")
      (libsource (lib "eagle-import") (part "FIDUCIAL"))
    )
    (comp (ref "FID10")
      (value "FIDUCIAL")
      (footprint "eagle-import:FIDUCIAL_1MM")
      (libsource (lib "eagle-import") (part "FIDUCIAL"))
    )
    (comp (ref "IC11")
      (value "4028")
      (footprint "eagle-import:SO16")
      (libsource (lib "eagle-import") (part "4028D"))
    )
    (comp (ref "IC12")
      (value "6V pos")
      (footprint "eagle-import:78LXX")
      (libsource (lib "eagle-import") (part "v-reg_78LXX"))
    )
    (comp (ref "IC13")
      (value "317TO202H_NOHOLE")
      (footprint "eagle-import:TO220H_NOHOLE")
      (libsource (lib "eagle-import") (part "317TO202H_NOHOLE"))
    )
    (comp (ref "IC14")
      (value "ULN2004")
      (footprint "eagle-import:SO16")
      (libsource (lib "eagle-import") (part "ULN2004AD"))
    )
    (comp (ref "IC15")
      (value "LM339")
      (footprint "eagle-import:SO14")
      (libsource (lib "eagle-import") (part "LM339D"))
    )
    (comp (ref "IC16")
      (value "78L06")
      (footprint "eagle-import:SOT89_ROUND")
      (libsource (lib "eagle-import") (part "78LXXSOT89_ROUND"))
    )
    (comp (ref "IC17")
      (value "555")
      (footprint "eagle-import:SO08")
      (libsource (lib "eagle-import") (part "555DNE"))
    )
    (comp (ref "IC18")
      (value "4538")
      (footprint "eagle-import:SO16")
      (libsource (lib "eagle-import") (part "4538D"))
    )
    (comp (ref "IC19")
      (value "78L10")
      (footprint "eagle-import:SOT89_ROUND")
      (libsource (lib "eagle-import") (part "78LXXSOT89_ROUND"))
    )
    (comp (ref "IC20")
      (value "LM2904")
      (footprint "eagle-import:SO08")
      (libsource (lib "eagle-import") (part "LM358D"))
    )
    (comp (ref "JP6")
      (value "JP2EJP2_SMALLPADS")
      (footprint "eagle-import:JP2_SMALLPADS")
      (libsource (lib "eagle-import") (part "JP2EJP2_SMALLPADS"))
    )
    (comp (ref "JP7")
      (value "JP2E_ORIG")
      (footprint "eagle-import:JP2_ORIG_SMALLPADS")
      (libsource (lib "eagle-import") (part "JP2E_ORIG"))
    )
    (comp (ref "JP8")
      (value "JP2EJP2_SMALLPADS")
      (footprint "eagle-import:JP2_SMALLPADS")
      (libsource (lib "eagle-import") (part "JP2EJP2_SMALLPADS"))
    )
    (comp (ref "JP9")
      (value "JP2EJP2_SMALLPADS")
      (footprint "eagle-import:JP2_SMALLPADS")
      (libsource (lib "eagle-import") (part "JP2EJP2_SMALLPADS"))
    )
    (comp (ref "JP10")
      (value "JP2EJP2_SMALLPADS")
      (footprint "eagle-import:JP2_SMALLPADS")
      (libsource (lib "eagle-import") (part "JP2EJP2_SMALLPADS"))
    )
    (comp (ref "LED7")
      (value "LEDLD260")
      (footprint "eagle-import:LD260")
      (libsource (lib "eagle-import") (part "LEDLD260"))
    )
    (comp (ref "LED8")
      (value "LEDLD260")
      (footprint "eagle-import:LD260")
      (libsource (lib "eagle-import") (part "LEDLD260"))
    )
    (comp (ref "LED9")
      (value "LEDLD260")
      (footprint "eagle-import:LD260")
      (libsource (lib "eagle-import") (part "LEDLD260"))
    )
    (comp (ref "LED10")
      (value "LEDLD260")
      (footprint "eagle-import:LD260")
      (libsource (lib "eagle-import") (part "LEDLD260"))
    )
    (comp (ref "LED11")
      (value "LEDLD260")
      (footprint "eagle-import:LD260")
      (libsource (lib "eagle-import") (part "LEDLD260"))
    )
    (comp (ref "LED12")
      (value "LEDLD260")
      (footprint "eagle-import:LD260")
      (libsource (lib "eagle-import") (part "LEDLD260"))
    )
    (comp (ref "Q8")
      (value "BA")
      (footprint "eagle-import:SOT89")
      (libsource (lib "eagle-import") (part "PNP-TRANSISTOR_SOT89"))
    )
    (comp (ref "Q9")
      (value "BA.")
      (footprint "eagle-import:SOT89")
      (libsource (lib "eagle-import") (part "PNP-TRANSISTOR_SOT89"))
    )
    (comp (ref "Q10")
      (value "BA.")
      (footprint "eagle-import:SOT89")
      (libsource (lib "eagle-import") (part "PNP-TRANSISTOR_SOT89"))
    )
    (comp (ref "Q11")
      (value "BA")
      (footprint "eagle-import:SOT89")
      (libsource (lib "eagle-import") (part "PNP-TRANSISTOR_SOT89"))
    )
    (comp (ref "Q12")
      (value "MY")
      (footprint "eagle-import:SOT89")
      (libsource (lib "eagle-import") (part "NPN-TRANSISTOR_SOT89"))
    )
    (comp (ref "Q13")
      (value "J1")
      (footprint "eagle-import:SOT-23")
      (fields (field (name "MPN") "BSS138W-7-F"))
      (libsource (lib "eagle-import") (part "SMD-MOSFET-N-CH-50V-200MA-BSS138W-7-F(SOT-23)"))
    )
    (comp (ref "Q14")
      (value "J1")
      (footprint "eagle-import:SOT-23")
      (fields (field (name "MPN") "BSS138W-7-F"))
      (libsource (lib "eagle-import") (part "SMD-MOSFET-N-CH-50V-200MA-BSS138W-7-F(SOT-23)"))
    )
    (comp (ref "R46")
      (value "47")
      (footprint "eagle-import:V235_17_1MM")
      (libsource (lib "eagle-import") (part "R-EU_V235/17_1MM"))
    )
    (comp (ref "R47")
      (value "13")
      (footprint "eagle-import:R1206")
      (fields (field (name "MPN") "RC1206JR-0713RL"))
      (libsource (lib "eagle-import") (part "SMD-RES-13R-5%-1/4W(1206)"))
    )
    (comp (ref "R48")
      (value "47")
      (footprint "eagle-import:V235_17_1MM")
      (libsource (lib "eagle-import") (part "R-EU_V235/17_1MM"))
    )
    (comp (ref "R49")
      (value "104")
      (footprint "eagle-import:R0805")
      (fields (field (name "MPN") "RC0805FR-0710KL"))
      (libsource (lib "eagle-import") (part "SMD-RES-10K-1%-1/8W(0805)"))
    )
    (comp (ref "R50")
      (value "104")
      (footprint "eagle-import:R0805")
      (fields (field (name "MPN") "RC0805FR-0710KL"))
      (libsource (lib "eagle-import") (part "SMD-RES-10K-1%-1/8W(0805)"))
    )
    (comp (ref "R51")
      (value "104")
      (footprint "eagle-import:R0805")
      (fields (field (name "MPN") "RC0805FR-0710KL"))
      (libsource (lib "eagle-import") (part "SMD-RES-10K-1%-1/8W(0805)"))
    )
    (comp (ref "R52")
      (value "4701")
      (footprint "eagle-import:R0805")
      (fields (field (name "MPN") "RC0805JR-074K7L"))
      (libsource (lib "eagle-import") (part "SMD-RES-4.7K-5%-1/8W(0805)"))
    )
    (comp (ref "R53")
      (value "1002")
      (footprint "eagle-import:R0805")
      (fields (field (name "MPN") "RC0805FR-0710KL"))
      (libsource (lib "eagle-import") (part "SMD-RES-10K-1%-1/8W(0805)"))
    )
    (comp (ref "R54")
      (value "1002")
      (footprint "eagle-import:R0805")
      (fields (field (name "MPN") "RC0805FR-0710KL"))
      (libsource (lib "eagle-import") (part "SMD-RES-10K-1%-1/8W(0805)"))
    )
    (comp (ref "R55")
      (value "1502")
      (footprint "eagle-import:R0805")
      (fields (field (name "MPN") "RC0805FR-0710KL"))
      (libsource (lib "eagle-import") (part "SMD-RES-10K-1%-1/8W(0805)"))
    )
    (comp (ref "R56")
      (value "104")
      (footprint "eagle-import:R0805")
      (fields (field (name "MPN") "RC0805FR-0710KL"))
      (libsource (lib "eagle-import") (part "SMD-RES-10K-1%-1/8W(0805)"))
    )
    (comp (ref "R57")
      (value "104")
      (footprint "eagle-import:R0805")
      (fields (field (name "MPN") "RC0805FR-0710KL"))
      (libsource (lib "eagle-import") (part "SMD-RES-10K-1%-1/8W(0805)"))
    )
    (comp (ref "R58")
      (value "1502")
      (footprint "eagle-import:R0805")
      (fields (field (name "MPN") "RC0805FR-0710KL"))
      (libsource (lib "eagle-import") (part "SMD-RES-10K-1%-1/8W(0805)"))
    )
    (comp (ref "R59")
      (value "1002")
      (footprint "eagle-import:R0805")
      (fields (field (name "MPN") "RC0805FR-0710KL"))
      (libsource (lib "eagle-import") (part "SMD-RES-10K-1%-1/8W(0805)"))
    )
    (comp (ref "R60")
      (value "2201")
      (footprint "eagle-import:R0805")
      (fields (field (name "MPN") "RC0805JR-072K2L"))
      (libsource (lib "eagle-import") (part "SMD-RES-2.2K-5%-1/8W(0805)"))
    )
    (comp (ref "R61")
      (value "1002")
      (footprint "eagle-import:R0805")
      (fields (field (name "MPN") "RC0805FR-0710KL"))
      (libsource (lib "eagle-import") (part "SMD-RES-10K-1%-1/8W(0805)"))
    )
    (comp (ref "R62")
      (value "4701")
      (footprint "eagle-import:R0805")
      (fields (field (name "MPN") "RC0805JR-074K7L"))
      (libsource (lib "eagle-import") (part "SMD-RES-4.7K-5%-1/8W(0805)"))
    )
    (comp (ref "R63")
      (value "2702")
      (footprint "eagle-import:R0805")
      (fields (field (name "MPN") "RC0805JR-074K7L"))
      (libsource (lib "eagle-import") (part "SMD-RES-4.7K-5%-1/8W(0805)"))
    )
    (comp (ref "R64")
      (value "102")
      (footprint "eagle-import:R0805")
      (fields (field (name "MPN") "RC0805JR-071KL"))
      (libsource (lib "eagle-import") (part "SMD-RES-1K-5%-1/8W(0805)"))
    )
    (comp (ref "R65")
      (value "100")
      (footprint "eagle-import:R0805")
      (fields (field (name "MPN") "RC0805JR-07220RL"))
      (libsource (lib "eagle-import") (part "SMD-RES-220R-5%-1/8W(0805)"))
    )
    (comp (ref "R66")
      (value "(101)")
      (footprint "eagle-import:R0805")
      (fields (field (name "MPN") "RC0805JR-07100RL"))
      (libsource (lib "eagle-import") (part "SMD-RES-100R-5%-1/8W(0805)"))
    )
    (comp (ref "R67")
      (value "(1000)")
      (footprint "eagle-import:R0805")
      (fields (field (name "MPN") "RC0805JR-07100RL"))
      (libsource (lib "eagle-import") (part "SMD-RES-100R-5%-1/8W(0805)"))
    )
    (comp (ref "R68")
      (value "102")
      (footprint "eagle-import:R0805")
      (fields (field (name "MPN") "RC0805JR-071KL"))
      (libsource (lib "eagle-import") (part "SMD-RES-1K-5%-1/8W(0805)"))
    )
    (comp (ref "R69")
      (value "13")
      (footprint "eagle-import:R1206")
      (fields (field (name "MPN") "RC1206JR-0713RL"))
      (libsource (lib "eagle-import") (part "SMD-RES-13R-5%-1/4W(1206)"))
    )
    (comp (ref "R70")
      (value "13")
      (footprint "eagle-import:R1206")
      (fields (field (name "MPN") "RC1206JR-0713RL"))
      (libsource (lib "eagle-import") (part "SMD-RES-13R-5%-1/4W(1206)"))
    )
    (comp (ref "R71")
      (value "2702")
      (footprint "eagle-import:R0805")
      (fields (field (name "MPN") "RC0805JR-074K7L"))
      (libsource (lib "eagle-import") (part "SMD-RES-4.7K-5%-1/8W(0805)"))
    )
    (comp (ref "R72")
      (value "4701")
      (footprint "eagle-import:R0805")
      (fields (field (name "MPN") "RC0805JR-074K7L"))
      (libsource (lib "eagle-import") (part "SMD-RES-4.7K-5%-1/8W(0805)"))
    )
    (comp (ref "R73")
      (value "100")
      (footprint "eagle-import:R0805")
      (fields (field (name "MPN") "RC0805JR-072K2L"))
      (libsource (lib "eagle-import") (part "SMD-RES-2.2K-5%-1/8W(0805)"))
    )
    (comp (ref "R74")
      (value "(101)")
      (footprint "eagle-import:R0805")
      (fields (field (name "MPN") "RC0805JR-072K2L"))
      (libsource (lib "eagle-import") (part "SMD-RES-2.2K-5%-1/8W(0805)"))
    )
    (comp (ref "R75")
      (value "104")
      (footprint "eagle-import:R0805")
      (fields (field (name "MPN") "RC0805FR-0710KL"))
      (libsource (lib "eagle-import") (part "SMD-RES-10K-1%-1/8W(0805)"))
    )
    (comp (ref "R76")
      (value "104")
      (footprint "eagle-import:R0805")
      (fields (field (name "MPN") "RC0805FR-0710KL"))
      (libsource (lib "eagle-import") (part "SMD-RES-10K-1%-1/8W(0805)"))
    )
    (comp (ref "R77")
      (value "(1002)")
      (footprint "eagle-import:R0805")
      (fields (field (name "MPN") "RC0805FR-0710KL"))
      (libsource (lib "eagle-import") (part "SMD-RES-10K-1%-1/8W(0805)"))
    )
    (comp (ref "R78")
      (value "2702")
      (footprint "eagle-import:R0805")
      (fields (field (name "MPN") "RC0805FR-0710KL"))
      (libsource (lib "eagle-import") (part "SMD-RES-10K-1%-1/8W(0805)"))
    )
    (comp (ref "R79")
      (value "47")
      (footprint "eagle-import:V235_17_1MM")
      (libsource (lib "eagle-import") (part "R-EU_V235/17_1MM"))
    )
    (comp (ref "R80")
      (value "47")
      (footprint "eagle-import:V235_17_1MM")
      (libsource (lib "eagle-import") (part "R-EU_V235/17_1MM"))
    )
    (comp (ref "R81")
      (value "2702")
      (footprint "eagle-import:R0805")
      (fields (field (name "MPN") "RC0805JR-074K7L"))
      (libsource (lib "eagle-import") (part "SMD-RES-4.7K-5%-1/8W(0805)"))
    )
    (comp (ref "R82")
      (value "2201")
      (footprint "eagle-import:R0805")
      (fields (field (name "MPN") "RC0805JR-072K2L"))
      (libsource (lib "eagle-import") (part "SMD-RES-2.2K-5%-1/8W(0805)"))
    )
    (comp (ref "R83")
      (value "(1002)")
      (footprint "eagle-import:R0805")
      (fields (field (name "MPN") "RC0805JR-074K7L"))
      (libsource (lib "eagle-import") (part "SMD-RES-4.7K-5%-1/8W(0805)"))
    )
    (comp (ref "R84")
      (value "1002")
      (footprint "eagle-import:R0805")
      (fields (field (name "MPN") "RC0805FR-0710KL"))
      (libsource (lib "eagle-import") (part "SMD-RES-10K-1%-1/8W(0805)"))
    )
    (comp (ref "R85")
      (value "102")
      (footprint "eagle-import:R0805")
      (fields (field (name "MPN") "RC0805JR-071KL"))
      (libsource (lib "eagle-import") (part "SMD-RES-1K-5%-1/8W(0805)"))
    )
    (comp (ref "R86")
      (value "2702")
      (footprint "eagle-import:R0805")
      (fields (field (name "MPN") "RC0805JR-074K7L"))
      (libsource (lib "eagle-import") (part "SMD-RES-4.7K-5%-1/8W(0805)"))
    )
    (comp (ref "R87")
      (value "102")
      (footprint "eagle-import:R0805")
      (fields (field (name "MPN") "RC0805JR-071KL"))
      (libsource (lib "eagle-import") (part "SMD-RES-1K-5%-1/8W(0805)"))
    )
    (comp (ref "R88")
      (value "102")
      (footprint "eagle-import:R0805")
      (fields (field (name "MPN") "RC0805JR-071KL"))
      (libsource (lib "eagle-import") (part "SMD-RES-1K-5%-1/8W(0805)"))
    )
    (comp (ref "R89")
      (value "13")
      (footprint "eagle-import:R1206")
      (fields (field (name "MPN") "RC1206JR-0713RL"))
      (libsource (lib "eagle-import") (part "SMD-RES-13R-5%-1/4W(1206)"))
    )
    (comp (ref "R90")
      (value "R_user")
      (footprint "eagle-import:R0805")
      (libsource (lib "eagle-import") (part "R-EU_R0805"))
    )
    (comp (ref "SJ2") (value "SJ") (footprint "eagle-import:SJ") (libsource (lib "eagle-import") (part "SJ")))
    (comp (ref "START2")
      (value "TPSB2.0")
      (footprint "eagle-import:B2.0")
      (libsource (lib "eagle-import") (part "TPSB2.0"))
    )
    (comp (ref "TP93")
      (value "TPSB2.0")
      (footprint "eagle-import:B2.0")
      (libsource (lib "eagle-import") (part "TPSB2.0"))
    )
    (comp (ref "TP94")
      (value "TPSB2.0")
      (footprint "eagle-import:B2.0")
      (libsource (lib "eagle-import") (part "TPSB2.0"))
    )
    (comp (ref "TP95")
      (value "TPSB2.0")
      (footprint "eagle-import:B2.0")
      (libsource (lib "eagle-import") (part "TPSB2.0"))
    )
    (comp (ref "TP96")
      (value "TPSB2.0")
      (footprint "eagle-import:B2.0")
      (libsource (lib "eagle-import") (part "TPSB2.0"))
    )
    (comp (ref "TP97")
      (value "TPSB2.0")
      (footprint "eagle-import:B2.0")
      (libsource (lib "eagle-import") (part "TPSB2.0"))
    )
    (comp (ref "TP98")
      (value "TPSB2.0")
      (footprint "eagle-import:B2.0")
      (libsource (lib "eagle-import") (part "TPSB2.0"))
    )
    (comp (ref "TP99")
      (value "TPSB2.0")
      (footprint "eagle-import:B2.0")
      (libsource (lib "eagle-import") (part "TPSB2.0"))
    )
    (comp (ref "TP100")
      (value "TPSB2.0")
      (footprint "eagle-import:B2.0")
      (libsource (lib "eagle-import") (part "TPSB2.0"))
    )
    (comp (ref "TP101")
      (value "TPSB2.0")
      (footprint "eagle-import:B2.0")
      (libsource (lib "eagle-import") (part "TPSB2.0"))
    )
    (comp (ref "TP102")
      (value "TPSB2.0")
      (footprint "eagle-import:B2.0")
      (libsource (lib "eagle-import") (part "TPSB2.0"))
    )
    (comp (ref "TP103")
      (value "TPSB2.0")
      (footprint "eagle-import:B2.0")
      (libsource (lib "eagle-import") (part "TPSB2.0"))
    )
    (comp (ref "TP104")
      (value "TPSB2.0")
      (footprint "eagle-import:B2.0")
      (libsource (lib "eagle-import") (part "TPSB2.0"))
    )
    (comp (ref "TP105")
      (value "TPSB2.0")
      (footprint "eagle-import:B2.0")
      (libsource (lib "eagle-import") (part "TPSB2.0"))
    )
    (comp (ref "TP106")
      (value "TPSB2.0")
      (footprint "eagle-import:B2.0")
      (libsource (lib "eagle-import") (part "TPSB2.0"))
    )
    (comp (ref "TP107")
      (value "TPSB2.0")
      (footprint "eagle-import:B2.0")
      (libsource (lib "eagle-import") (part "TPSB2.0"))
    )
    (comp (ref "TP108")
      (value "TPSB2.0")
      (footprint "eagle-import:B2.0")
      (libsource (lib "eagle-import") (part "TPSB2.0"))
    )
    (comp (ref "TP109")
      (value "TPSB2.0")
      (footprint "eagle-import:B2.0")
      (libsource (lib "eagle-import") (part "TPSB2.0"))
    )
    (comp (ref "TP110")
      (value "TPSB2.0")
      (footprint "eagle-import:B2.0")
      (libsource (lib "eagle-import") (part "TPSB2.0"))
    )
    (comp (ref "TP111")
      (value "TPSB1,27")
      (footprint "eagle-import:B1,27")
      (libsource (lib "eagle-import") (part "TPSB1,27"))
    )
    (comp (ref "TP112")
      (value "TPSB2.0")
      (footprint "eagle-import:B2.0")
      (libsource (lib "eagle-import") (part "TPSB2.0"))
    )
    (comp (ref "TP113")
      (value "TPSB2.0")
      (footprint "eagle-import:B2.0")
      (libsource (lib "eagle-import") (part "TPSB2.0"))
    )
    (comp (ref "TP114")
      (value "TPSB2.0")
      (footprint "eagle-import:B2.0")
      (libsource (lib "eagle-import") (part "TPSB2.0"))
    )
    (comp (ref "TP115")
      (value "TPSB2.0")
      (footprint "eagle-import:B2.0")
      (libsource (lib "eagle-import") (part "TPSB2.0"))
    )
    (comp (ref "X4")
      (value "CON_BMWV2")
      (footprint "eagle-import:24-PIN_V2")
      (libsource (lib "eagle-import") (part "CON_BMWV2"))
    )
    (comp (ref "X5")
      (value "22-23-2051")
      (footprint "eagle-import:22-23-2051")
      (fields (field (name "MF") "MOLEX"))
      (libsource (lib "eagle-import") (part "22-23-2051"))
    )
    (comp (ref "X6")
      (value "22-23-2021")
      (footprint "eagle-import:22-23-2021")
      (fields (field (name "MF") "MOLEX"))
      (libsource (lib "eagle-import") (part "22-23-2021"))
    )
    (comp (ref "1")
      (value "2081-1132")
      (footprint "eagle-import:12-PIN")
      (libsource (lib "eagle-import") (part "2081-1132"))
    )
    (comp (ref "2")
      (value "2081-1132")
      (footprint "eagle-import:12-PIN")
      (libsource (lib "eagle-import") (part "2081-1132"))
    )
    (comp (ref "6V")
      (value "TPSB2.0")
      (footprint "eagle-import:B2.0")
      (libsource (lib "eagle-import") (part "TPSB2.0"))
    )
    (comp (ref "10V")
      (value "TPSB2.0")
      (footprint "eagle-import:B2.0")
      (libsource (lib "eagle-import") (part "TPSB2.0"))
    )
    (comp (ref "C101")
      (value "4.7u")
      (footprint "eagle-import:C0805")
      (fields (field (name "MPN") "CC0805KKX5R8BB475"))
      (libsource (lib "eagle-import") (part "CERAMIC-4.7UF-25V-10%-X5R(0805)"))
    )
    (comp (ref "C102")
      (value "100nF")
      (footprint "eagle-import:C0805")
      (fields (field (name "MPN") "CC0805KRX7R9BB104"))
      (libsource (lib "eagle-import") (part "CERAMIC-100NF-50V-10%-X7R(0805)"))
    )
    (comp (ref "C103")
      (value "100nF,")
      (footprint "eagle-import:C0805")
      (fields (field (name "MPN") "CC0805KRX7R9BB104"))
      (libsource (lib "eagle-import") (part "CERAMIC-100NF-50V-10%-X7R(0805)"))
    )
    (comp (ref "C104")
      (value "100nF,")
      (footprint "eagle-import:C0805")
      (fields (field (name "MPN") "CC0805KRX7R9BB104"))
      (libsource (lib "eagle-import") (part "CERAMIC-100NF-50V-10%-X7R(0805)"))
    )
    (comp (ref "C105")
      (value "100nF.")
      (footprint "eagle-import:C0805")
      (fields (field (name "MPN") "CC0805KRX7R9BB104"))
      (libsource (lib "eagle-import") (part "CERAMIC-100NF-50V-10%-X7R(0805)"))
    )
    (comp (ref "C106")
      (value "100nF.")
      (footprint "eagle-import:C0805")
      (fields (field (name "MPN") "CC0805KRX7R9BB104"))
      (libsource (lib "eagle-import") (part "CERAMIC-100NF-50V-10%-X7R(0805)"))
    )
    (comp (ref "C107")
      (value "100u")
      (footprint "eagle-import:C1206")
      (fields (field (name "MPN") "GRM31CR60J107ME39L"))
      (libsource (lib "eagle-import") (part "CERAMIC-100UF-6.3V-20%-X5R(1206)"))
    )
    (comp (ref "C108")
      (value "100u")
      (footprint "eagle-import:C1206")
      (fields (field (name "MPN") "GRM31CR60J107ME39L"))
      (libsource (lib "eagle-import") (part "CERAMIC-100UF-6.3V-20%-X5R(1206)"))
    )
    (comp (ref "C109")
      (value "2.2nF")
      (footprint "eagle-import:C0805")
      (fields (field (name "MPN") "CC0805KRX7R9BB104"))
      (libsource (lib "eagle-import") (part "CERAMIC-100NF-50V-10%-X7R(0805)"))
    )
    (comp (ref "C110")
      (value "100nF")
      (footprint "eagle-import:C0805")
      (fields (field (name "MPN") "CC0805KRX7R9BB104"))
      (libsource (lib "eagle-import") (part "CERAMIC-100NF-50V-10%-X7R(0805)"))
    )
    (comp (ref "D101")
      (value "SM6T")
      (footprint "eagle-import:DO214AA")
      (libsource (lib "eagle-import") (part "SM6T"))
    )
    (comp (ref "D102")
      (value "1N4007,")
      (footprint "eagle-import:DO-214AC")
      (fields (field (name "MPN") "1N4007"))
      (libsource (lib "eagle-import") (part "DIODE-GEN-PURPOSE-1KV-1A(DO-214AC)"))
    )
    (comp (ref "D103")
      (value "1N4007,")
      (footprint "eagle-import:DO-214AC")
      (fields (field (name "MPN") "1N4007"))
      (libsource (lib "eagle-import") (part "DIODE-GEN-PURPOSE-1KV-1A(DO-214AC)"))
    )
    (comp (ref "D105")
      (value "1N4007.")
      (footprint "eagle-import:DO-214AC")
      (fields (field (name "MPN") "1N4007"))
      (libsource (lib "eagle-import") (part "DIODE-GEN-PURPOSE-1KV-1A(DO-214AC)"))
    )
    (comp (ref "D106")
      (value "1N4007.")
      (footprint "eagle-import:DO-214AC")
      (fields (field (name "MPN") "1N4007"))
      (libsource (lib "eagle-import") (part "DIODE-GEN-PURPOSE-1KV-1A(DO-214AC)"))
    )
    (comp (ref "D107")
      (value "1N5817")
      (footprint "eagle-import:DO-214AC_SLIM")
      (libsource (lib "eagle-import") (part "DIODE-GEN-PURPOSE-1KV-1A(DO-214AC)DO-214AC/1206"))
    )
    (comp (ref "D108")
      (value "1N5817.")
      (footprint "eagle-import:DO-214AC_SLIM")
      (libsource (lib "eagle-import") (part "DIODE-GEN-PURPOSE-1KV-1A(DO-214AC)DO-214AC/1206"))
    )
    (comp (ref "D109")
      (value "1N5817.")
      (footprint "eagle-import:DO-214AC_SLIM")
      (libsource (lib "eagle-import") (part "DIODE-GEN-PURPOSE-1KV-1A(DO-214AC)DO-214AC/1206"))
    )
    (comp (ref "D110")
      (value "1N5817")
      (footprint "eagle-import:DO-214AC_SLIM")
      (libsource (lib "eagle-import") (part "DIODE-GEN-PURPOSE-1KV-1A(DO-214AC)DO-214AC/1206"))
    )
    (comp (ref "D111")
      (value "1N4007")
      (footprint "eagle-import:DO-214AC")
      (libsource (lib "eagle-import") (part "DIODE-GEN-PURPOSE-1KV-1A(DO-214AC)"))
    )
    (comp (ref "D112")
      (value "1N4007")
      (footprint "eagle-import:DO-214AC")
      (libsource (lib "eagle-import") (part "DIODE-GEN-PURPOSE-1KV-1A(DO-214AC)"))
    )
    (comp (ref "FID1")
      (value "FIDUCIAL")
      (footprint "eagle-import:FIDUCIAL_1MM")
      (libsource (lib "eagle-import") (part "FIDUCIAL"))
    )
    (comp (ref "FID1B")
      (value "FIDUCIALFIDUCIAL_1MM_WITH_SOLDERMASK")
      (footprint "eagle-import:FIDUCIAL_1MM_WITH_SOLDERMASK")
      (libsource (lib "eagle-import") (part "FIDUCIALFIDUCIAL_1MM_WITH_SOLDERMASK"))
    )
    (comp (ref "FID2")
      (value "FIDUCIAL")
      (footprint "eagle-import:FIDUCIAL_1MM")
      (libsource (lib "eagle-import") (part "FIDUCIAL"))
    )
    (comp (ref "FID2B")
      (value "FIDUCIALFIDUCIAL_1MM_WITH_SOLDERMASK")
      (footprint "eagle-import:FIDUCIAL_1MM_WITH_SOLDERMASK")
      (libsource (lib "eagle-import") (part "FIDUCIALFIDUCIAL_1MM_WITH_SOLDERMASK"))
    )
    (comp (ref "FID101")
      (value "FIDUCIAL")
      (footprint "eagle-import:FIDUCIAL_1MM")
      (libsource (lib "eagle-import") (part "FIDUCIAL"))
    )
    (comp (ref "FID102")
      (value "FIDUCIAL")
      (footprint "eagle-import:FIDUCIAL_1MM")
      (libsource (lib "eagle-import") (part "FIDUCIAL"))
    )
    (comp (ref "FID103")
      (value "FIDUCIAL")
      (footprint "eagle-import:FIDUCIAL_1MM")
      (libsource (lib "eagle-import") (part "FIDUCIAL"))
    )
    (comp (ref "FID104")
      (value "FIDUCIAL")
      (footprint "eagle-import:FIDUCIAL_1MM")
      (libsource (lib "eagle-import") (part "FIDUCIAL"))
    )
    (comp (ref "IC101")
      (value "LM2904")
      (footprint "eagle-import:SO08")
      (libsource (lib "eagle-import") (part "LM358D"))
    )
    (comp (ref "IC102")
      (value "78L06")
      (footprint "eagle-import:SOT89_ROUND")
      (libsource (lib "eagle-import") (part "78LXXSOT89_ROUND"))
    )
    (comp (ref "IC103")
      (value "6V pos")
      (footprint "eagle-import:78LXX")
      (libsource (lib "eagle-import") (part "v-reg_78LXX"))
    )
    (comp (ref "IC104")
      (value "78L10")
      (footprint "eagle-import:SOT89_ROUND")
      (libsource (lib "eagle-import") (part "78LXXSOT89_ROUND"))
    )
    (comp (ref "IC105")
      (value "4028")
      (footprint "eagle-import:SO16")
      (libsource (lib "eagle-import") (part "4028D"))
    )
    (comp (ref "IC107")
      (value "ULN2004")
      (footprint "eagle-import:SO16")
      (libsource (lib "eagle-import") (part "ULN2004AD"))
    )
    (comp (ref "IC108")
      (value "LM339")
      (footprint "eagle-import:SO14")
      (libsource (lib "eagle-import") (part "LM339D"))
    )
    (comp (ref "IC109")
      (value "317TO202H_NOHOLE")
      (footprint "eagle-import:TO220H_NOHOLE")
      (libsource (lib "eagle-import") (part "317TO202H_NOHOLE"))
    )
    (comp (ref "IC110")
      (value "555")
      (footprint "eagle-import:SO08")
      (libsource (lib "eagle-import") (part "555DNE"))
    )
    (comp (ref "IC111")
      (value "4538")
      (footprint "eagle-import:SO16")
      (libsource (lib "eagle-import") (part "4538D"))
    )
    (comp (ref "JP101")
      (value "JP2EJP2_SMALLPADS")
      (footprint "eagle-import:JP2_SMALLPADS")
      (libsource (lib "eagle-import") (part "JP2EJP2_SMALLPADS"))
    )
    (comp (ref "JP102")
      (value "JP2EJP2_SMALLPADS")
      (footprint "eagle-import:JP2_SMALLPADS")
      (libsource (lib "eagle-import") (part "JP2EJP2_SMALLPADS"))
    )
    (comp (ref "JP103")
      (value "JP2EJP2_SMALLPADS")
      (footprint "eagle-import:JP2_SMALLPADS")
      (libsource (lib "eagle-import") (part "JP2EJP2_SMALLPADS"))
    )
    (comp (ref "JP104")
      (value "JP2EJP2_SMALLPADS")
      (footprint "eagle-import:JP2_SMALLPADS")
      (libsource (lib "eagle-import") (part "JP2EJP2_SMALLPADS"))
    )
    (comp (ref "JP105")
      (value "JP2E_ORIG")
      (footprint "eagle-import:JP2_ORIG_SMALLPADS")
      (libsource (lib "eagle-import") (part "JP2E_ORIG"))
    )
    (comp (ref "LED101")
      (value "LEDLD260")
      (footprint "eagle-import:LD260")
      (libsource (lib "eagle-import") (part "LEDLD260"))
    )
    (comp (ref "LED102")
      (value "LEDLD260")
      (footprint "eagle-import:LD260")
      (libsource (lib "eagle-import") (part "LEDLD260"))
    )
    (comp (ref "LED103")
      (value "LEDLD260")
      (footprint "eagle-import:LD260")
      (libsource (lib "eagle-import") (part "LEDLD260"))
    )
    (comp (ref "LED104")
      (value "LEDLD260")
      (footprint "eagle-import:LD260")
      (libsource (lib "eagle-import") (part "LEDLD260"))
    )
    (comp (ref "LED105")
      (value "LEDLD260")
      (footprint "eagle-import:LD260")
      (libsource (lib "eagle-import") (part "LEDLD260"))
    )
    (comp (ref "LED106")
      (value "LEDLD260")
      (footprint "eagle-import:LD260")
      (libsource (lib "eagle-import") (part "LEDLD260"))
    )
    (comp (ref "Q101")
      (value "BA.")
      (footprint "eagle-import:SOT89")
      (libsource (lib "eagle-import") (part "PNP-TRANSISTOR_SOT89"))
    )
    (comp (ref "Q102")
      (value "BA.")
      (footprint "eagle-import:SOT89")
      (libsource (lib "eagle-import") (part "PNP-TRANSISTOR_SOT89"))
    )
    (comp (ref "Q103")
      (value "MY")
      (footprint "eagle-import:SOT89")
      (libsource (lib "eagle-import") (part "NPN-TRANSISTOR_SOT89"))
    )
    (comp (ref "Q104")
      (value "BA")
      (footprint "eagle-import:SOT89")
      (libsource (lib "eagle-import") (part "PNP-TRANSISTOR_SOT89"))
    )
    (comp (ref "Q105")
      (value "BA")
      (footprint "eagle-import:SOT89")
      (libsource (lib "eagle-import") (part "PNP-TRANSISTOR_SOT89"))
    )
    (comp (ref "Q106")
      (value "J1")
      (footprint "eagle-import:SOT-23")
      (fields (field (name "MPN") "BSS138W-7-F"))
      (libsource (lib "eagle-import") (part "SMD-MOSFET-N-CH-50V-200MA-BSS138W-7-F(SOT-23)"))
    )
    (comp (ref "Q107")
      (value "J1")
      (footprint "eagle-import:SOT-23")
      (fields (field (name "MPN") "BSS138W-7-F"))
      (libsource (lib "eagle-import") (part "SMD-MOSFET-N-CH-50V-200MA-BSS138W-7-F(SOT-23)"))
    )
    (comp (ref "R101")
      (value "102")
      (footprint "eagle-import:R0805")
      (fields (field (name "MPN") "RC0805JR-071KL"))
      (libsource (lib "eagle-import") (part "SMD-RES-1K-5%-1/8W(0805)"))
    )
    (comp (ref "R102")
      (value "13")
      (footprint "eagle-import:R1206")
      (fields (field (name "MPN") "RC1206JR-0713RL"))
      (libsource (lib "eagle-import") (part "SMD-RES-13R-5%-1/4W(1206)"))
    )
    (comp (ref "R103")
      (value "R_user")
      (footprint "eagle-import:R0805")
      (libsource (lib "eagle-import") (part "R-EU_R0805"))
    )
    (comp (ref "R105")
      (value "4701")
      (footprint "eagle-import:R0805")
      (fields (field (name "MPN") "RC0805JR-074K7L"))
      (libsource (lib "eagle-import") (part "SMD-RES-4.7K-5%-1/8W(0805)"))
    )
    (comp (ref "R106")
      (value "13")
      (footprint "eagle-import:R1206")
      (fields (field (name "MPN") "RC1206JR-0713RL"))
      (libsource (lib "eagle-import") (part "SMD-RES-13R-5%-1/4W(1206)"))
    )
    (comp (ref "R107")
      (value "1002")
      (footprint "eagle-import:R0805")
      (fields (field (name "MPN") "RC0805FR-0710KL"))
      (libsource (lib "eagle-import") (part "SMD-RES-10K-1%-1/8W(0805)"))
    )
    (comp (ref "R108")
      (value "1002")
      (footprint "eagle-import:R0805")
      (fields (field (name "MPN") "RC0805FR-0710KL"))
      (libsource (lib "eagle-import") (part "SMD-RES-10K-1%-1/8W(0805)"))
    )
    (comp (ref "R109")
      (value "104")
      (footprint "eagle-import:R0805")
      (fields (field (name "MPN") "RC0805FR-0710KL"))
      (libsource (lib "eagle-import") (part "SMD-RES-10K-1%-1/8W(0805)"))
    )
    (comp (ref "R110")
      (value "104")
      (footprint "eagle-import:R0805")
      (fields (field (name "MPN") "RC0805FR-0710KL"))
      (libsource (lib "eagle-import") (part "SMD-RES-10K-1%-1/8W(0805)"))
    )
    (comp (ref "R111")
      (value "104")
      (footprint "eagle-import:R0805")
      (fields (field (name "MPN") "RC0805FR-0710KL"))
      (libsource (lib "eagle-import") (part "SMD-RES-10K-1%-1/8W(0805)"))
    )
    (comp (ref "R112")
      (value "102")
      (footprint "eagle-import:R0805")
      (fields (field (name "MPN") "RC0805JR-071KL"))
      (libsource (lib "eagle-import") (part "SMD-RES-1K-5%-1/8W(0805)"))
    )
    (comp (ref "R113")
      (value "102")
      (footprint "eagle-import:R0805")
      (fields (field (name "MPN") "RC0805JR-071KL"))
      (libsource (lib "eagle-import") (part "SMD-RES-1K-5%-1/8W(0805)"))
    )
    (comp (ref "R114")
      (value "102")
      (footprint "eagle-import:R0805")
      (fields (field (name "MPN") "RC0805JR-071KL"))
      (libsource (lib "eagle-import") (part "SMD-RES-1K-5%-1/8W(0805)"))
    )
    (comp (ref "R115")
      (value "100")
      (footprint "eagle-import:R0805")
      (fields (field (name "MPN") "RC0805JR-07220RL"))
      (libsource (lib "eagle-import") (part "SMD-RES-220R-5%-1/8W(0805)"))
    )
    (comp (ref "R116")
      (value "4701")
      (footprint "eagle-import:R0805")
      (fields (field (name "MPN") "RC0805JR-074K7L"))
      (libsource (lib "eagle-import") (part "SMD-RES-4.7K-5%-1/8W(0805)"))
    )
    (comp (ref "R117")
      (value "2702")
      (footprint "eagle-import:R0805")
      (fields (field (name "MPN") "RC0805JR-074K7L"))
      (libsource (lib "eagle-import") (part "SMD-RES-4.7K-5%-1/8W(0805)"))
    )
    (comp (ref "R118")
      (value "13")
      (footprint "eagle-import:R1206")
      (fields (field (name "MPN") "RC1206JR-0713RL"))
      (libsource (lib "eagle-import") (part "SMD-RES-13R-5%-1/4W(1206)"))
    )
    (comp (ref "R119")
      (value "2201")
      (footprint "eagle-import:R0805")
      (fields (field (name "MPN") "RC0805JR-072K2L"))
      (libsource (lib "eagle-import") (part "SMD-RES-2.2K-5%-1/8W(0805)"))
    )
    (comp (ref "R120")
      (value "1002")
      (footprint "eagle-import:R0805")
      (fields (field (name "MPN") "RC0805FR-0710KL"))
      (libsource (lib "eagle-import") (part "SMD-RES-10K-1%-1/8W(0805)"))
    )
    (comp (ref "R121")
      (value "1502")
      (footprint "eagle-import:R0805")
      (fields (field (name "MPN") "RC0805FR-0710KL"))
      (libsource (lib "eagle-import") (part "SMD-RES-10K-1%-1/8W(0805)"))
    )
    (comp (ref "R122")
      (value "2702")
      (footprint "eagle-import:R0805")
      (fields (field (name "MPN") "RC0805JR-074K7L"))
      (libsource (lib "eagle-import") (part "SMD-RES-4.7K-5%-1/8W(0805)"))
    )
    (comp (ref "R123")
      (value "2702")
      (footprint "eagle-import:R0805")
      (fields (field (name "MPN") "RC0805JR-074K7L"))
      (libsource (lib "eagle-import") (part "SMD-RES-4.7K-5%-1/8W(0805)"))
    )
    (comp (ref "R124")
      (value "1002")
      (footprint "eagle-import:R0805")
      (fields (field (name "MPN") "RC0805FR-0710KL"))
      (libsource (lib "eagle-import") (part "SMD-RES-10K-1%-1/8W(0805)"))
    )
    (comp (ref "R125")
      (value "104")
      (footprint "eagle-import:R0805")
      (fields (field (name "MPN") "RC0805FR-0710KL"))
      (libsource (lib "eagle-import") (part "SMD-RES-10K-1%-1/8W(0805)"))
    )
    (comp (ref "R126")
      (value "4701")
      (footprint "eagle-import:R0805")
      (fields (field (name "MPN") "RC0805JR-074K7L"))
      (libsource (lib "eagle-import") (part "SMD-RES-4.7K-5%-1/8W(0805)"))
    )
    (comp (ref "R127")
      (value "47")
      (footprint "eagle-import:V235_17_1MM")
      (libsource (lib "eagle-import") (part "R-EU_V235/17_1MM"))
    )
    (comp (ref "R128")
      (value "102")
      (footprint "eagle-import:R0805")
      (fields (field (name "MPN") "RC0805JR-071KL"))
      (libsource (lib "eagle-import") (part "SMD-RES-1K-5%-1/8W(0805)"))
    )
    (comp (ref "R129")
      (value "47")
      (footprint "eagle-import:V235_17_1MM")
      (libsource (lib "eagle-import") (part "R-EU_V235/17_1MM"))
    )
    (comp (ref "R130")
      (value "104")
      (footprint "eagle-import:R0805")
      (fields (field (name "MPN") "RC0805FR-0710KL"))
      (libsource (lib "eagle-import") (part "SMD-RES-10K-1%-1/8W(0805)"))
    )
    (comp (ref "R131")
      (value "1502")
      (footprint "eagle-import:R0805")
      (fields (field (name "MPN") "RC0805FR-0710KL"))
      (libsource (lib "eagle-import") (part "SMD-RES-10K-1%-1/8W(0805)"))
    )
    (comp (ref "R132")
      (value "1002")
      (footprint "eagle-import:R0805")
      (fields (field (name "MPN") "RC0805FR-0710KL"))
      (libsource (lib "eagle-import") (part "SMD-RES-10K-1%-1/8W(0805)"))
    )
    (comp (ref "R133")
      (value "2201")
      (footprint "eagle-import:R0805")
      (fields (field (name "MPN") "RC0805JR-072K2L"))
      (libsource (lib "eagle-import") (part "SMD-RES-2.2K-5%-1/8W(0805)"))
    )
    (comp (ref "R134")
      (value "13")
      (footprint "eagle-import:R1206")
      (fields (field (name "MPN") "RC1206JR-0713RL"))
      (libsource (lib "eagle-import") (part "SMD-RES-13R-5%-1/4W(1206)"))
    )
    (comp (ref "R135")
      (value "104")
      (footprint "eagle-import:R0805")
      (fields (field (name "MPN") "RC0805FR-0710KL"))
      (libsource (lib "eagle-import") (part "SMD-RES-10K-1%-1/8W(0805)"))
    )
    (comp (ref "R136")
      (value "47")
      (footprint "eagle-import:V235_17_1MM")
      (libsource (lib "eagle-import") (part "R-EU_V235/17_1MM"))
    )
    (comp (ref "R137")
      (value "47")
      (footprint "eagle-import:V235_17_1MM")
      (libsource (lib "eagle-import") (part "R-EU_V235/17_1MM"))
    )
    (comp (ref "R138")
      (value "100")
      (footprint "eagle-import:R0805")
      (fields (field (name "MPN") "RC0805JR-072K2L"))
      (libsource (lib "eagle-import") (part "SMD-RES-2.2K-5%-1/8W(0805)"))
    )
    (comp (ref "R139")
      (value "(101)")
      (footprint "eagle-import:R0805")
      (fields (field (name "MPN") "RC0805JR-072K2L"))
      (libsource (lib "eagle-import") (part "SMD-RES-2.2K-5%-1/8W(0805)"))
    )
    (comp (ref "R140")
      (value "2702")
      (footprint "eagle-import:R0805")
      (fields (field (name "MPN") "RC0805FR-0710KL"))
      (libsource (lib "eagle-import") (part "SMD-RES-10K-1%-1/8W(0805)"))
    )
    (comp (ref "R141")
      (value "104")
      (footprint "eagle-import:R0805")
      (fields (field (name "MPN") "RC0805FR-0710KL"))
      (libsource (lib "eagle-import") (part "SMD-RES-10K-1%-1/8W(0805)"))
    )
    (comp (ref "R142")
      (value "(1000)")
      (footprint "eagle-import:R0805")
      (fields (field (name "MPN") "RC0805JR-07100RL"))
      (libsource (lib "eagle-import") (part "SMD-RES-100R-5%-1/8W(0805)"))
    )
    (comp (ref "R143")
      (value "(101)")
      (footprint "eagle-import:R0805")
      (fields (field (name "MPN") "RC0805JR-07100RL"))
      (libsource (lib "eagle-import") (part "SMD-RES-100R-5%-1/8W(0805)"))
    )
    (comp (ref "R144")
      (value "(1002)")
      (footprint "eagle-import:R0805")
      (fields (field (name "MPN") "RC0805FR-0710KL"))
      (libsource (lib "eagle-import") (part "SMD-RES-10K-1%-1/8W(0805)"))
    )
    (comp (ref "R145")
      (value "2702")
      (footprint "eagle-import:R0805")
      (fields (field (name "MPN") "RC0805JR-074K7L"))
      (libsource (lib "eagle-import") (part "SMD-RES-4.7K-5%-1/8W(0805)"))
    )
    (comp (ref "R146")
      (value "(1002)")
      (footprint "eagle-import:R0805")
      (fields (field (name "MPN") "RC0805JR-074K7L"))
      (libsource (lib "eagle-import") (part "SMD-RES-4.7K-5%-1/8W(0805)"))
    )
    (comp (ref "SJ101")
      (value "SJ")
      (footprint "eagle-import:SJ")
      (libsource (lib "eagle-import") (part "SJ"))
    )
    (comp (ref "START")
      (value "TPSB2.0")
      (footprint "eagle-import:B2.0")
      (libsource (lib "eagle-import") (part "TPSB2.0"))
    )
    (comp (ref "TP1")
      (value "TPSB2.0")
      (footprint "eagle-import:B2.0")
      (libsource (lib "eagle-import") (part "TPSB2.0"))
    )
    (comp (ref "TP2")
      (value "TPSB2.0")
      (footprint "eagle-import:B2.0")
      (libsource (lib "eagle-import") (part "TPSB2.0"))
    )
    (comp (ref "TP3")
      (value "TPSB2.0")
      (footprint "eagle-import:B2.0")
      (libsource (lib "eagle-import") (part "TPSB2.0"))
    )
    (comp (ref "TP4")
      (value "TPSB2.0")
      (footprint "eagle-import:B2.0")
      (libsource (lib "eagle-import") (part "TPSB2.0"))
    )
    (comp (ref "TP5")
      (value "TPSB2.0")
      (footprint "eagle-import:B2.0")
      (libsource (lib "eagle-import") (part "TPSB2.0"))
    )
    (comp (ref "TP6")
      (value "TPSB2.0")
      (footprint "eagle-import:B2.0")
      (libsource (lib "eagle-import") (part "TPSB2.0"))
    )
    (comp (ref "TP7")
      (value "TPSB2.0")
      (footprint "eagle-import:B2.0")
      (libsource (lib "eagle-import") (part "TPSB2.0"))
    )
    (comp (ref "TP8")
      (value "TPSB2.0")
      (footprint "eagle-import:B2.0")
      (libsource (lib "eagle-import") (part "TPSB2.0"))
    )
    (comp (ref "TP9")
      (value "TPSB2.0")
      (footprint "eagle-import:B2.0")
      (libsource (lib "eagle-import") (part "TPSB2.0"))
    )
    (comp (ref "TP10")
      (value "TPSB2.0")
      (footprint "eagle-import:B2.0")
      (libsource (lib "eagle-import") (part "TPSB2.0"))
    )
    (comp (ref "TP11")
      (value "TPSB2.0")
      (footprint "eagle-import:B2.0")
      (libsource (lib "eagle-import") (part "TPSB2.0"))
    )
    (comp (ref "TP12")
      (value "TPSB2.0")
      (footprint "eagle-import:B2.0")
      (libsource (lib "eagle-import") (part "TPSB2.0"))
    )
    (comp (ref "TP13")
      (value "TPSB2.0")
      (footprint "eagle-import:B2.0")
      (libsource (lib "eagle-import") (part "TPSB2.0"))
    )
    (comp (ref "TP16")
      (value "TPSB2.0")
      (footprint "eagle-import:B2.0")
      (libsource (lib "eagle-import") (part "TPSB2.0"))
    )
    (comp (ref "TP17")
      (value "TPSB2.0")
      (footprint "eagle-import:B2.0")
      (libsource (lib "eagle-import") (part "TPSB2.0"))
    )
    (comp (ref "TP18")
      (value "TPSB2.0")
      (footprint "eagle-import:B2.0")
      (libsource (lib "eagle-import") (part "TPSB2.0"))
    )
    (comp (ref "TP19")
      (value "TPSB2.0")
      (footprint "eagle-import:B2.0")
      (libsource (lib "eagle-import") (part "TPSB2.0"))
    )
    (comp (ref "TP21")
      (value "TPSB2.0")
      (footprint "eagle-import:B2.0")
      (libsource (lib "eagle-import") (part "TPSB2.0"))
    )
    (comp (ref "TP22")
      (value "TPSB2.0")
      (footprint "eagle-import:B2.0")
      (libsource (lib "eagle-import") (part "TPSB2.0"))
    )
    (comp (ref "TP23")
      (value "TPSB2.0")
      (footprint "eagle-import:B2.0")
      (libsource (lib "eagle-import") (part "TPSB2.0"))
    )
    (comp (ref "TP24")
      (value "TPSB1,27")
      (footprint "eagle-import:B1,27")
      (libsource (lib "eagle-import") (part "TPSB1,27"))
    )
    (comp (ref "TP25")
      (value "TPSB2.0")
      (footprint "eagle-import:B2.0")
      (libsource (lib "eagle-import") (part "TPSB2.0"))
    )
    (comp (ref "TP26")
      (value "TPSB2.0")
      (footprint "eagle-import:B2.0")
      (libsource (lib "eagle-import") (part "TPSB2.0"))
    )
    (comp (ref "X101")
      (value "CON_BMWV2")
      (footprint "eagle-import:24-PIN_V2")
      (libsource (lib "eagle-import") (part "CON_BMWV2"))
    )
    (comp (ref "X102")
      (value "22-23-2021")
      (footprint "eagle-import:22-23-2021")
      (fields (field (name "MF") "MOLEX"))
      (libsource (lib "eagle-import") (part "22-23-2021"))
    )
    (comp (ref "X103")
      (value "22-23-2051")
      (footprint "eagle-import:22-23-2051")
      (fields (field (name "MF") "MOLEX"))
      (libsource (lib "eagle-import") (part "22-23-2051"))
    )
    (comp (ref "6V401")
      (value "TPSB2.0")
      (footprint "eagle-import:B2.0")
      (libsource (lib "eagle-import") (part "TPSB2.0"))
    )
    (comp (ref "10V401")
      (value "TPSB2.0")
      (footprint "eagle-import:B2.0")
      (libsource (lib "eagle-import") (part "TPSB2.0"))
    )
    (comp (ref "13")
      (value "2081-1132")
      (footprint "eagle-import:12-PIN")
      (libsource (lib "eagle-import") (part "2081-1132"))
    )
    (comp (ref "14")
      (value "2081-1132")
      (footprint "eagle-import:12-PIN")
      (libsource (lib "eagle-import") (part "2081-1132"))
    )
    (comp (ref "C401")
      (value "4.7u")
      (footprint "eagle-import:C0805")
      (fields (field (name "MPN") "CC0805KKX5R8BB475"))
      (libsource (lib "eagle-import") (part "CERAMIC-4.7UF-25V-10%-X5R(0805)"))
    )
    (comp (ref "C402")
      (value "100nF")
      (footprint "eagle-import:C0805")
      (fields (field (name "MPN") "CC0805KRX7R9BB104"))
      (libsource (lib "eagle-import") (part "CERAMIC-100NF-50V-10%-X7R(0805)"))
    )
    (comp (ref "C403")
      (value "100nF,")
      (footprint "eagle-import:C0805")
      (fields (field (name "MPN") "CC0805KRX7R9BB104"))
      (libsource (lib "eagle-import") (part "CERAMIC-100NF-50V-10%-X7R(0805)"))
    )
    (comp (ref "C404")
      (value "100nF,")
      (footprint "eagle-import:C0805")
      (fields (field (name "MPN") "CC0805KRX7R9BB104"))
      (libsource (lib "eagle-import") (part "CERAMIC-100NF-50V-10%-X7R(0805)"))
    )
    (comp (ref "C405")
      (value "100nF.")
      (footprint "eagle-import:C0805")
      (fields (field (name "MPN") "CC0805KRX7R9BB104"))
      (libsource (lib "eagle-import") (part "CERAMIC-100NF-50V-10%-X7R(0805)"))
    )
    (comp (ref "C406")
      (value "100nF.")
      (footprint "eagle-import:C0805")
      (fields (field (name "MPN") "CC0805KRX7R9BB104"))
      (libsource (lib "eagle-import") (part "CERAMIC-100NF-50V-10%-X7R(0805)"))
    )
    (comp (ref "C407")
      (value "100u")
      (footprint "eagle-import:C1206")
      (fields (field (name "MPN") "GRM31CR60J107ME39L"))
      (libsource (lib "eagle-import") (part "CERAMIC-100UF-6.3V-20%-X5R(1206)"))
    )
    (comp (ref "C408")
      (value "100u")
      (footprint "eagle-import:C1206")
      (fields (field (name "MPN") "GRM31CR60J107ME39L"))
      (libsource (lib "eagle-import") (part "CERAMIC-100UF-6.3V-20%-X5R(1206)"))
    )
    (comp (ref "C409")
      (value "2.2nF")
      (footprint "eagle-import:C0805")
      (fields (field (name "MPN") "CC0805KRX7R9BB104"))
      (libsource (lib "eagle-import") (part "CERAMIC-100NF-50V-10%-X7R(0805)"))
    )
    (comp (ref "C410")
      (value "100nF")
      (footprint "eagle-import:C0805")
      (fields (field (name "MPN") "CC0805KRX7R9BB104"))
      (libsource (lib "eagle-import") (part "CERAMIC-100NF-50V-10%-X7R(0805)"))
    )
    (comp (ref "D401")
      (value "SM6T")
      (footprint "eagle-import:DO214AA")
      (libsource (lib "eagle-import") (part "SM6T"))
    )
    (comp (ref "D402")
      (value "1N4007,")
      (footprint "eagle-import:DO-214AC")
      (fields (field (name "MPN") "1N4007"))
      (libsource (lib "eagle-import") (part "DIODE-GEN-PURPOSE-1KV-1A(DO-214AC)"))
    )
    (comp (ref "D403")
      (value "1N4007,")
      (footprint "eagle-import:DO-214AC")
      (fields (field (name "MPN") "1N4007"))
      (libsource (lib "eagle-import") (part "DIODE-GEN-PURPOSE-1KV-1A(DO-214AC)"))
    )
    (comp (ref "D405")
      (value "1N4007.")
      (footprint "eagle-import:DO-214AC")
      (fields (field (name "MPN") "1N4007"))
      (libsource (lib "eagle-import") (part "DIODE-GEN-PURPOSE-1KV-1A(DO-214AC)"))
    )
    (comp (ref "D406")
      (value "1N4007.")
      (footprint "eagle-import:DO-214AC")
      (fields (field (name "MPN") "1N4007"))
      (libsource (lib "eagle-import") (part "DIODE-GEN-PURPOSE-1KV-1A(DO-214AC)"))
    )
    (comp (ref "D407")
      (value "1N5817")
      (footprint "eagle-import:DO-214AC_SLIM")
      (libsource (lib "eagle-import") (part "DIODE-GEN-PURPOSE-1KV-1A(DO-214AC)DO-214AC/1206"))
    )
    (comp (ref "D408")
      (value "1N5817.")
      (footprint "eagle-import:DO-214AC_SLIM")
      (libsource (lib "eagle-import") (part "DIODE-GEN-PURPOSE-1KV-1A(DO-214AC)DO-214AC/1206"))
    )
    (comp (ref "D409")
      (value "1N5817.")
      (footprint "eagle-import:DO-214AC_SLIM")
      (libsource (lib "eagle-import") (part "DIODE-GEN-PURPOSE-1KV-1A(DO-214AC)DO-214AC/1206"))
    )
    (comp (ref "D410")
      (value "1N5817")
      (footprint "eagle-import:DO-214AC_SLIM")
      (libsource (lib "eagle-import") (part "DIODE-GEN-PURPOSE-1KV-1A(DO-214AC)DO-214AC/1206"))
    )
    (comp (ref "D411")
      (value "1N4007")
      (footprint "eagle-import:DO-214AC")
      (libsource (lib "eagle-import") (part "DIODE-GEN-PURPOSE-1KV-1A(DO-214AC)"))
    )
    (comp (ref "D412")
      (value "1N4007")
      (footprint "eagle-import:DO-214AC")
      (libsource (lib "eagle-import") (part "DIODE-GEN-PURPOSE-1KV-1A(DO-214AC)"))
    )
    (comp (ref "FID401")
      (value "FIDUCIAL")
      (footprint "eagle-import:FIDUCIAL_1MM")
      (libsource (lib "eagle-import") (part "FIDUCIAL"))
    )
    (comp (ref "FID402")
      (value "FIDUCIAL")
      (footprint "eagle-import:FIDUCIAL_1MM")
      (libsource (lib "eagle-import") (part "FIDUCIAL"))
    )
    (comp (ref "FID403")
      (value "FIDUCIAL")
      (footprint "eagle-import:FIDUCIAL_1MM")
      (libsource (lib "eagle-import") (part "FIDUCIAL"))
    )
    (comp (ref "FID404")
      (value "FIDUCIAL")
      (footprint "eagle-import:FIDUCIAL_1MM")
      (libsource (lib "eagle-import") (part "FIDUCIAL"))
    )
    (comp (ref "IC401")
      (value "LM2904")
      (footprint "eagle-import:SO08")
      (libsource (lib "eagle-import") (part "LM358D"))
    )
    (comp (ref "IC402")
      (value "78L06")
      (footprint "eagle-import:SOT89_ROUND")
      (libsource (lib "eagle-import") (part "78LXXSOT89_ROUND"))
    )
    (comp (ref "IC403")
      (value "6V pos")
      (footprint "eagle-import:78LXX")
      (libsource (lib "eagle-import") (part "v-reg_78LXX"))
    )
    (comp (ref "IC404")
      (value "78L10")
      (footprint "eagle-import:SOT89_ROUND")
      (libsource (lib "eagle-import") (part "78LXXSOT89_ROUND"))
    )
    (comp (ref "IC405")
      (value "4028")
      (footprint "eagle-import:SO16")
      (libsource (lib "eagle-import") (part "4028D"))
    )
    (comp (ref "IC407")
      (value "ULN2004")
      (footprint "eagle-import:SO16")
      (libsource (lib "eagle-import") (part "ULN2004AD"))
    )
    (comp (ref "IC408")
      (value "LM339")
      (footprint "eagle-import:SO14")
      (libsource (lib "eagle-import") (part "LM339D"))
    )
    (comp (ref "IC409")
      (value "317TO202H_NOHOLE")
      (footprint "eagle-import:TO220H_NOHOLE")
      (libsource (lib "eagle-import") (part "317TO202H_NOHOLE"))
    )
    (comp (ref "IC410")
      (value "555")
      (footprint "eagle-import:SO08")
      (libsource (lib "eagle-import") (part "555DNE"))
    )
    (comp (ref "IC411")
      (value "4538")
      (footprint "eagle-import:SO16")
      (libsource (lib "eagle-import") (part "4538D"))
    )
    (comp (ref "JP401")
      (value "JP2EJP2_SMALLPADS")
      (footprint "eagle-import:JP2_SMALLPADS")
      (libsource (lib "eagle-import") (part "JP2EJP2_SMALLPADS"))
    )
    (comp (ref "JP402")
      (value "JP2EJP2_SMALLPADS")
      (footprint "eagle-import:JP2_SMALLPADS")
      (libsource (lib "eagle-import") (part "JP2EJP2_SMALLPADS"))
    )
    (comp (ref "JP403")
      (value "JP2EJP2_SMALLPADS")
      (footprint "eagle-import:JP2_SMALLPADS")
      (libsource (lib "eagle-import") (part "JP2EJP2_SMALLPADS"))
    )
    (comp (ref "JP404")
      (value "JP2EJP2_SMALLPADS")
      (footprint "eagle-import:JP2_SMALLPADS")
      (libsource (lib "eagle-import") (part "JP2EJP2_SMALLPADS"))
    )
    (comp (ref "JP405")
      (value "JP2E_ORIG")
      (footprint "eagle-import:JP2_ORIG_SMALLPADS")
      (libsource (lib "eagle-import") (part "JP2E_ORIG"))
    )
    (comp (ref "LED401")
      (value "LEDLD260")
      (footprint "eagle-import:LD260")
      (libsource (lib "eagle-import") (part "LEDLD260"))
    )
    (comp (ref "LED402")
      (value "LEDLD260")
      (footprint "eagle-import:LD260")
      (libsource (lib "eagle-import") (part "LEDLD260"))
    )
    (comp (ref "LED403")
      (value "LEDLD260")
      (footprint "eagle-import:LD260")
      (libsource (lib "eagle-import") (part "LEDLD260"))
    )
    (comp (ref "LED404")
      (value "LEDLD260")
      (footprint "eagle-import:LD260")
      (libsource (lib "eagle-import") (part "LEDLD260"))
    )
    (comp (ref "LED405")
      (value "LEDLD260")
      (footprint "eagle-import:LD260")
      (libsource (lib "eagle-import") (part "LEDLD260"))
    )
    (comp (ref "LED406")
      (value "LEDLD260")
      (footprint "eagle-import:LD260")
      (libsource (lib "eagle-import") (part "LEDLD260"))
    )
    (comp (ref "Q401")
      (value "BA.")
      (footprint "eagle-import:SOT89")
      (libsource (lib "eagle-import") (part "PNP-TRANSISTOR_SOT89"))
    )
    (comp (ref "Q402")
      (value "BA.")
      (footprint "eagle-import:SOT89")
      (libsource (lib "eagle-import") (part "PNP-TRANSISTOR_SOT89"))
    )
    (comp (ref "Q403")
      (value "MY")
      (footprint "eagle-import:SOT89")
      (libsource (lib "eagle-import") (part "NPN-TRANSISTOR_SOT89"))
    )
    (comp (ref "Q404")
      (value "BA")
      (footprint "eagle-import:SOT89")
      (libsource (lib "eagle-import") (part "PNP-TRANSISTOR_SOT89"))
    )
    (comp (ref "Q405")
      (value "BA")
      (footprint "eagle-import:SOT89")
      (libsource (lib "eagle-import") (part "PNP-TRANSISTOR_SOT89"))
    )
    (comp (ref "Q406")
      (value "J1")
      (footprint "eagle-import:SOT-23")
      (fields (field (name "MPN") "BSS138W-7-F"))
      (libsource (lib "eagle-import") (part "SMD-MOSFET-N-CH-50V-200MA-BSS138W-7-F(SOT-23)"))
    )
    (comp (ref "Q407")
      (value "J1")
      (footprint "eagle-import:SOT-23")
      (fields (field (name "MPN") "BSS138W-7-F"))
      (libsource (lib "eagle-import") (part "SMD-MOSFET-N-CH-50V-200MA-BSS138W-7-F(SOT-23)"))
    )
    (comp (ref "R401")
      (value "102")
      (footprint "eagle-import:R0805")
      (fields (field (name "MPN") "RC0805JR-071KL"))
      (libsource (lib "eagle-import") (part "SMD-RES-1K-5%-1/8W(0805)"))
    )
    (comp (ref "R402")
      (value "13")
      (footprint "eagle-import:R1206")
      (fields (field (name "MPN") "RC1206JR-0713RL"))
      (libsource (lib "eagle-import") (part "SMD-RES-13R-5%-1/4W(1206)"))
    )
    (comp (ref "R403")
      (value "R_user")
      (footprint "eagle-import:R0805")
      (libsource (lib "eagle-import") (part "R-EU_R0805"))
    )
    (comp (ref "R405")
      (value "4701")
      (footprint "eagle-import:R0805")
      (fields (field (name "MPN") "RC0805JR-074K7L"))
      (libsource (lib "eagle-import") (part "SMD-RES-4.7K-5%-1/8W(0805)"))
    )
    (comp (ref "R406")
      (value "13")
      (footprint "eagle-import:R1206")
      (fields (field (name "MPN") "RC1206JR-0713RL"))
      (libsource (lib "eagle-import") (part "SMD-RES-13R-5%-1/4W(1206)"))
    )
    (comp (ref "R407")
      (value "1002")
      (footprint "eagle-import:R0805")
      (fields (field (name "MPN") "RC0805FR-0710KL"))
      (libsource (lib "eagle-import") (part "SMD-RES-10K-1%-1/8W(0805)"))
    )
    (comp (ref "R408")
      (value "1002")
      (footprint "eagle-import:R0805")
      (fields (field (name "MPN") "RC0805FR-0710KL"))
      (libsource (lib "eagle-import") (part "SMD-RES-10K-1%-1/8W(0805)"))
    )
    (comp (ref "R409")
      (value "104")
      (footprint "eagle-import:R0805")
      (fields (field (name "MPN") "RC0805FR-0710KL"))
      (libsource (lib "eagle-import") (part "SMD-RES-10K-1%-1/8W(0805)"))
    )
    (comp (ref "R410")
      (value "104")
      (footprint "eagle-import:R0805")
      (fields (field (name "MPN") "RC0805FR-0710KL"))
      (libsource (lib "eagle-import") (part "SMD-RES-10K-1%-1/8W(0805)"))
    )
    (comp (ref "R411")
      (value "104")
      (footprint "eagle-import:R0805")
      (fields (field (name "MPN") "RC0805FR-0710KL"))
      (libsource (lib "eagle-import") (part "SMD-RES-10K-1%-1/8W(0805)"))
    )
    (comp (ref "R412")
      (value "102")
      (footprint "eagle-import:R0805")
      (fields (field (name "MPN") "RC0805JR-071KL"))
      (libsource (lib "eagle-import") (part "SMD-RES-1K-5%-1/8W(0805)"))
    )
    (comp (ref "R413")
      (value "102")
      (footprint "eagle-import:R0805")
      (fields (field (name "MPN") "RC0805JR-071KL"))
      (libsource (lib "eagle-import") (part "SMD-RES-1K-5%-1/8W(0805)"))
    )
    (comp (ref "R414")
      (value "102")
      (footprint "eagle-import:R0805")
      (fields (field (name "MPN") "RC0805JR-071KL"))
      (libsource (lib "eagle-import") (part "SMD-RES-1K-5%-1/8W(0805)"))
    )
    (comp (ref "R415")
      (value "100")
      (footprint "eagle-import:R0805")
      (fields (field (name "MPN") "RC0805JR-07220RL"))
      (libsource (lib "eagle-import") (part "SMD-RES-220R-5%-1/8W(0805)"))
    )
    (comp (ref "R416")
      (value "4701")
      (footprint "eagle-import:R0805")
      (fields (field (name "MPN") "RC0805JR-074K7L"))
      (libsource (lib "eagle-import") (part "SMD-RES-4.7K-5%-1/8W(0805)"))
    )
    (comp (ref "R417")
      (value "2702")
      (footprint "eagle-import:R0805")
      (fields (field (name "MPN") "RC0805JR-074K7L"))
      (libsource (lib "eagle-import") (part "SMD-RES-4.7K-5%-1/8W(0805)"))
    )
    (comp (ref "R418")
      (value "13")
      (footprint "eagle-import:R1206")
      (fields (field (name "MPN") "RC1206JR-0713RL"))
      (libsource (lib "eagle-import") (part "SMD-RES-13R-5%-1/4W(1206)"))
    )
    (comp (ref "R419")
      (value "2201")
      (footprint "eagle-import:R0805")
      (fields (field (name "MPN") "RC0805JR-072K2L"))
      (libsource (lib "eagle-import") (part "SMD-RES-2.2K-5%-1/8W(0805)"))
    )
    (comp (ref "R420")
      (value "1002")
      (footprint "eagle-import:R0805")
      (fields (field (name "MPN") "RC0805FR-0710KL"))
      (libsource (lib "eagle-import") (part "SMD-RES-10K-1%-1/8W(0805)"))
    )
    (comp (ref "R421")
      (value "1502")
      (footprint "eagle-import:R0805")
      (fields (field (name "MPN") "RC0805FR-0710KL"))
      (libsource (lib "eagle-import") (part "SMD-RES-10K-1%-1/8W(0805)"))
    )
    (comp (ref "R422")
      (value "2702")
      (footprint "eagle-import:R0805")
      (fields (field (name "MPN") "RC0805JR-074K7L"))
      (libsource (lib "eagle-import") (part "SMD-RES-4.7K-5%-1/8W(0805)"))
    )
    (comp (ref "R423")
      (value "2702")
      (footprint "eagle-import:R0805")
      (fields (field (name "MPN") "RC0805JR-074K7L"))
      (libsource (lib "eagle-import") (part "SMD-RES-4.7K-5%-1/8W(0805)"))
    )
    (comp (ref "R424")
      (value "1002")
      (footprint "eagle-import:R0805")
      (fields (field (name "MPN") "RC0805FR-0710KL"))
      (libsource (lib "eagle-import") (part "SMD-RES-10K-1%-1/8W(0805)"))
    )
    (comp (ref "R425")
      (value "104")
      (footprint "eagle-import:R0805")
      (fields (field (name "MPN") "RC0805FR-0710KL"))
      (libsource (lib "eagle-import") (part "SMD-RES-10K-1%-1/8W(0805)"))
    )
    (comp (ref "R426")
      (value "4701")
      (footprint "eagle-import:R0805")
      (fields (field (name "MPN") "RC0805JR-074K7L"))
      (libsource (lib "eagle-import") (part "SMD-RES-4.7K-5%-1/8W(0805)"))
    )
    (comp (ref "R427")
      (value "47")
      (footprint "eagle-import:V235_17_1MM")
      (libsource (lib "eagle-import") (part "R-EU_V235/17_1MM"))
    )
    (comp (ref "R428")
      (value "102")
      (footprint "eagle-import:R0805")
      (fields (field (name "MPN") "RC0805JR-071KL"))
      (libsource (lib "eagle-import") (part "SMD-RES-1K-5%-1/8W(0805)"))
    )
    (comp (ref "R429")
      (value "47")
      (footprint "eagle-import:V235_17_1MM")
      (libsource (lib "eagle-import") (part "R-EU_V235/17_1MM"))
    )
    (comp (ref "R430")
      (value "104")
      (footprint "eagle-import:R0805")
      (fields (field (name "MPN") "RC0805FR-0710KL"))
      (libsource (lib "eagle-import") (part "SMD-RES-10K-1%-1/8W(0805)"))
    )
    (comp (ref "R431")
      (value "1502")
      (footprint "eagle-import:R0805")
      (fields (field (name "MPN") "RC0805FR-0710KL"))
      (libsource (lib "eagle-import") (part "SMD-RES-10K-1%-1/8W(0805)"))
    )
    (comp (ref "R432")
      (value "1002")
      (footprint "eagle-import:R0805")
      (fields (field (name "MPN") "RC0805FR-0710KL"))
      (libsource (lib "eagle-import") (part "SMD-RES-10K-1%-1/8W(0805)"))
    )
    (comp (ref "R433")
      (value "2201")
      (footprint "eagle-import:R0805")
      (fields (field (name "MPN") "RC0805JR-072K2L"))
      (libsource (lib "eagle-import") (part "SMD-RES-2.2K-5%-1/8W(0805)"))
    )
    (comp (ref "R434")
      (value "13")
      (footprint "eagle-import:R1206")
      (fields (field (name "MPN") "RC1206JR-0713RL"))
      (libsource (lib "eagle-import") (part "SMD-RES-13R-5%-1/4W(1206)"))
    )
    (comp (ref "R435")
      (value "104")
      (footprint "eagle-import:R0805")
      (fields (field (name "MPN") "RC0805FR-0710KL"))
      (libsource (lib "eagle-import") (part "SMD-RES-10K-1%-1/8W(0805)"))
    )
    (comp (ref "R436")
      (value "47")
      (footprint "eagle-import:V235_17_1MM")
      (libsource (lib "eagle-import") (part "R-EU_V235/17_1MM"))
    )
    (comp (ref "R437")
      (value "47")
      (footprint "eagle-import:V235_17_1MM")
      (libsource (lib "eagle-import") (part "R-EU_V235/17_1MM"))
    )
    (comp (ref "R438")
      (value "100")
      (footprint "eagle-import:R0805")
      (fields (field (name "MPN") "RC0805JR-072K2L"))
      (libsource (lib "eagle-import") (part "SMD-RES-2.2K-5%-1/8W(0805)"))
    )
    (comp (ref "R439")
      (value "(101)")
      (footprint "eagle-import:R0805")
      (fields (field (name "MPN") "RC0805JR-072K2L"))
      (libsource (lib "eagle-import") (part "SMD-RES-2.2K-5%-1/8W(0805)"))
    )
    (comp (ref "R440")
      (value "2702")
      (footprint "eagle-import:R0805")
      (fields (field (name "MPN") "RC0805FR-0710KL"))
      (libsource (lib "eagle-import") (part "SMD-RES-10K-1%-1/8W(0805)"))
    )
    (comp (ref "R441")
      (value "104")
      (footprint "eagle-import:R0805")
      (fields (field (name "MPN") "RC0805FR-0710KL"))
      (libsource (lib "eagle-import") (part "SMD-RES-10K-1%-1/8W(0805)"))
    )
    (comp (ref "R442")
      (value "(1000)")
      (footprint "eagle-import:R0805")
      (fields (field (name "MPN") "RC0805JR-07100RL"))
      (libsource (lib "eagle-import") (part "SMD-RES-100R-5%-1/8W(0805)"))
    )
    (comp (ref "R443")
      (value "(101)")
      (footprint "eagle-import:R0805")
      (fields (field (name "MPN") "RC0805JR-07100RL"))
      (libsource (lib "eagle-import") (part "SMD-RES-100R-5%-1/8W(0805)"))
    )
    (comp (ref "R444")
      (value "(1002)")
      (footprint "eagle-import:R0805")
      (fields (field (name "MPN") "RC0805FR-0710KL"))
      (libsource (lib "eagle-import") (part "SMD-RES-10K-1%-1/8W(0805)"))
    )
    (comp (ref "R445")
      (value "2702")
      (footprint "eagle-import:R0805")
      (fields (field (name "MPN") "RC0805JR-074K7L"))
      (libsource (lib "eagle-import") (part "SMD-RES-4.7K-5%-1/8W(0805)"))
    )
    (comp (ref "R446")
      (value "(1002)")
      (footprint "eagle-import:R0805")
      (fields (field (name "MPN") "RC0805JR-074K7L"))
      (libsource (lib "eagle-import") (part "SMD-RES-4.7K-5%-1/8W(0805)"))
    )
    (comp (ref "SJ401")
      (value "SJ")
      (footprint "eagle-import:SJ")
      (libsource (lib "eagle-import") (part "SJ"))
    )
    (comp (ref "START401")
      (value "TPSB2.0")
      (footprint "eagle-import:B2.0")
      (libsource (lib "eagle-import") (part "TPSB2.0"))
    )
    (comp (ref "TP139")
      (value "TPSB2.0")
      (footprint "eagle-import:B2.0")
      (libsource (lib "eagle-import") (part "TPSB2.0"))
    )
    (comp (ref "TP140")
      (value "TPSB2.0")
      (footprint "eagle-import:B2.0")
      (libsource (lib "eagle-import") (part "TPSB2.0"))
    )
    (comp (ref "TP141")
      (value "TPSB2.0")
      (footprint "eagle-import:B2.0")
      (libsource (lib "eagle-import") (part "TPSB2.0"))
    )
    (comp (ref "TP142")
      (value "TPSB2.0")
      (footprint "eagle-import:B2.0")
      (libsource (lib "eagle-import") (part "TPSB2.0"))
    )
    (comp (ref "TP143")
      (value "TPSB2.0")
      (footprint "eagle-import:B2.0")
      (libsource (lib "eagle-import") (part "TPSB2.0"))
    )
    (comp (ref "TP144")
      (value "TPSB2.0")
      (footprint "eagle-import:B2.0")
      (libsource (lib "eagle-import") (part "TPSB2.0"))
    )
    (comp (ref "TP145")
      (value "TPSB2.0")
      (footprint "eagle-import:B2.0")
      (libsource (lib "eagle-import") (part "TPSB2.0"))
    )
    (comp (ref "TP146")
      (value "TPSB2.0")
      (footprint "eagle-import:B2.0")
      (libsource (lib "eagle-import") (part "TPSB2.0"))
    )
    (comp (ref "TP147")
      (value "TPSB2.0")
      (footprint "eagle-import:B2.0")
      (libsource (lib "eagle-import") (part "TPSB2.0"))
    )
    (comp (ref "TP148")
      (value "TPSB2.0")
      (footprint "eagle-import:B2.0")
      (libsource (lib "eagle-import") (part "TPSB2.0"))
    )
    (comp (ref "TP149")
      (value "TPSB2.0")
      (footprint "eagle-import:B2.0")
      (libsource (lib "eagle-import") (part "TPSB2.0"))
    )
    (comp (ref "TP150")
      (value "TPSB2.0")
      (footprint "eagle-import:B2.0")
      (libsource (lib "eagle-import") (part "TPSB2.0"))
    )
    (comp (ref "TP151")
      (value "TPSB2.0")
      (footprint "eagle-import:B2.0")
      (libsource (lib "eagle-import") (part "TPSB2.0"))
    )
    (comp (ref "TP152")
      (value "TPSB2.0")
      (footprint "eagle-import:B2.0")
      (libsource (lib "eagle-import") (part "TPSB2.0"))
    )
    (comp (ref "TP153")
      (value "TPSB2.0")
      (footprint "eagle-import:B2.0")
      (libsource (lib "eagle-import") (part "TPSB2.0"))
    )
    (comp (ref "TP154")
      (value "TPSB2.0")
      (footprint "eagle-import:B2.0")
      (libsource (lib "eagle-import") (part "TPSB2.0"))
    )
    (comp (ref "TP155")
      (value "TPSB2.0")
      (footprint "eagle-import:B2.0")
      (libsource (lib "eagle-import") (part "TPSB2.0"))
    )
    (comp (ref "TP156")
      (value "TPSB2.0")
      (footprint "eagle-import:B2.0")
      (libsource (lib "eagle-import") (part "TPSB2.0"))
    )
    (comp (ref "TP157")
      (value "TPSB1,27")
      (footprint "eagle-import:B1,27")
      (libsource (lib "eagle-import") (part "TPSB1,27"))
    )
    (comp (ref "TP158")
      (value "TPSB2.0")
      (footprint "eagle-import:B2.0")
      (libsource (lib "eagle-import") (part "TPSB2.0"))
    )
    (comp (ref "TP159")
      (value "TPSB2.0")
      (footprint "eagle-import:B2.0")
      (libsource (lib "eagle-import") (part "TPSB2.0"))
    )
    (comp (ref "TP160")
      (value "TPSB2.0")
      (footprint "eagle-import:B2.0")
      (libsource (lib "eagle-import") (part "TPSB2.0"))
    )
    (comp (ref "TP161")
      (value "TPSB2.0")
      (footprint "eagle-import:B2.0")
      (libsource (lib "eagle-import") (part "TPSB2.0"))
    )
    (comp (ref "X401")
      (value "CON_BMWV2")
      (footprint "eagle-import:24-PIN_V2")
      (libsource (lib "eagle-import") (part "CON_BMWV2"))
    )
    (comp (ref "X402")
      (value "22-23-2021")
      (footprint "eagle-import:22-23-2021")
      (fields (field (name "MF") "MOLEX"))
      (libsource (lib "eagle-import") (part "22-23-2021"))
    )
    (comp (ref "X403")
      (value "22-23-2051")
      (footprint "eagle-import:22-23-2051")
      (fields (field (name "MF") "MOLEX"))
      (libsource (lib "eagle-import") (part "22-23-2051"))
    )
    (comp (ref "6V601")
      (value "TPSB2.0")
      (footprint "eagle-import:B2.0")
      (libsource (lib "eagle-import") (part "TPSB2.0"))
    )
    (comp (ref "10V601")
      (value "TPSB2.0")
      (footprint "eagle-import:B2.0")
      (libsource (lib "eagle-import") (part "TPSB2.0"))
    )
    (comp (ref "17")
      (value "2081-1132")
      (footprint "eagle-import:12-PIN")
      (libsource (lib "eagle-import") (part "2081-1132"))
    )
    (comp (ref "18")
      (value "2081-1132")
      (footprint "eagle-import:12-PIN")
      (libsource (lib "eagle-import") (part "2081-1132"))
    )
    (comp (ref "C601")
      (value "4.7u")
      (footprint "eagle-import:C0805")
      (fields (field (name "MPN") "CC0805KKX5R8BB475"))
      (libsource (lib "eagle-import") (part "CERAMIC-4.7UF-25V-10%-X5R(0805)"))
    )
    (comp (ref "C602")
      (value "100nF")
      (footprint "eagle-import:C0805")
      (fields (field (name "MPN") "CC0805KRX7R9BB104"))
      (libsource (lib "eagle-import") (part "CERAMIC-100NF-50V-10%-X7R(0805)"))
    )
    (comp (ref "C603")
      (value "100nF,")
      (footprint "eagle-import:C0805")
      (fields (field (name "MPN") "CC0805KRX7R9BB104"))
      (libsource (lib "eagle-import") (part "CERAMIC-100NF-50V-10%-X7R(0805)"))
    )
    (comp (ref "C604")
      (value "100nF,")
      (footprint "eagle-import:C0805")
      (fields (field (name "MPN") "CC0805KRX7R9BB104"))
      (libsource (lib "eagle-import") (part "CERAMIC-100NF-50V-10%-X7R(0805)"))
    )
    (comp (ref "C605")
      (value "100nF.")
      (footprint "eagle-import:C0805")
      (fields (field (name "MPN") "CC0805KRX7R9BB104"))
      (libsource (lib "eagle-import") (part "CERAMIC-100NF-50V-10%-X7R(0805)"))
    )
    (comp (ref "C606")
      (value "100nF.")
      (footprint "eagle-import:C0805")
      (fields (field (name "MPN") "CC0805KRX7R9BB104"))
      (libsource (lib "eagle-import") (part "CERAMIC-100NF-50V-10%-X7R(0805)"))
    )
    (comp (ref "C607")
      (value "100u")
      (footprint "eagle-import:C1206")
      (fields (field (name "MPN") "GRM31CR60J107ME39L"))
      (libsource (lib "eagle-import") (part "CERAMIC-100UF-6.3V-20%-X5R(1206)"))
    )
    (comp (ref "C608")
      (value "100u")
      (footprint "eagle-import:C1206")
      (fields (field (name "MPN") "GRM31CR60J107ME39L"))
      (libsource (lib "eagle-import") (part "CERAMIC-100UF-6.3V-20%-X5R(1206)"))
    )
    (comp (ref "C609")
      (value "2.2nF")
      (footprint "eagle-import:C0805")
      (fields (field (name "MPN") "CC0805KRX7R9BB104"))
      (libsource (lib "eagle-import") (part "CERAMIC-100NF-50V-10%-X7R(0805)"))
    )
    (comp (ref "C610")
      (value "100nF")
      (footprint "eagle-import:C0805")
      (fields (field (name "MPN") "CC0805KRX7R9BB104"))
      (libsource (lib "eagle-import") (part "CERAMIC-100NF-50V-10%-X7R(0805)"))
    )
    (comp (ref "D601")
      (value "SM6T")
      (footprint "eagle-import:DO214AA")
      (libsource (lib "eagle-import") (part "SM6T"))
    )
    (comp (ref "D602")
      (value "1N4007,")
      (footprint "eagle-import:DO-214AC")
      (fields (field (name "MPN") "1N4007"))
      (libsource (lib "eagle-import") (part "DIODE-GEN-PURPOSE-1KV-1A(DO-214AC)"))
    )
    (comp (ref "D603")
      (value "1N4007,")
      (footprint "eagle-import:DO-214AC")
      (fields (field (name "MPN") "1N4007"))
      (libsource (lib "eagle-import") (part "DIODE-GEN-PURPOSE-1KV-1A(DO-214AC)"))
    )
    (comp (ref "D605")
      (value "1N4007.")
      (footprint "eagle-import:DO-214AC")
      (fields (field (name "MPN") "1N4007"))
      (libsource (lib "eagle-import") (part "DIODE-GEN-PURPOSE-1KV-1A(DO-214AC)"))
    )
    (comp (ref "D606")
      (value "1N4007.")
      (footprint "eagle-import:DO-214AC")
      (fields (field (name "MPN") "1N4007"))
      (libsource (lib "eagle-import") (part "DIODE-GEN-PURPOSE-1KV-1A(DO-214AC)"))
    )
    (comp (ref "D607")
      (value "1N5817")
      (footprint "eagle-import:DO-214AC_SLIM")
      (libsource (lib "eagle-import") (part "DIODE-GEN-PURPOSE-1KV-1A(DO-214AC)DO-214AC/1206"))
    )
    (comp (ref "D608")
      (value "1N5817.")
      (footprint "eagle-import:DO-214AC_SLIM")
      (libsource (lib "eagle-import") (part "DIODE-GEN-PURPOSE-1KV-1A(DO-214AC)DO-214AC/1206"))
    )
    (comp (ref "D609")
      (value "1N5817.")
      (footprint "eagle-import:DO-214AC_SLIM")
      (libsource (lib "eagle-import") (part "DIODE-GEN-PURPOSE-1KV-1A(DO-214AC)DO-214AC/1206"))
    )
    (comp (ref "D610")
      (value "1N5817")
      (footprint "eagle-import:DO-214AC_SLIM")
      (libsource (lib "eagle-import") (part "DIODE-GEN-PURPOSE-1KV-1A(DO-214AC)DO-214AC/1206"))
    )
    (comp (ref "D611")
      (value "1N4007")
      (footprint "eagle-import:DO-214AC")
      (libsource (lib "eagle-import") (part "DIODE-GEN-PURPOSE-1KV-1A(DO-214AC)"))
    )
    (comp (ref "D612")
      (value "1N4007")
      (footprint "eagle-import:DO-214AC")
      (libsource (lib "eagle-import") (part "DIODE-GEN-PURPOSE-1KV-1A(DO-214AC)"))
    )
    (comp (ref "FID601")
      (value "FIDUCIAL")
      (footprint "eagle-import:FIDUCIAL_1MM")
      (libsource (lib "eagle-import") (part "FIDUCIAL"))
    )
    (comp (ref "FID602")
      (value "FIDUCIAL")
      (footprint "eagle-import:FIDUCIAL_1MM")
      (libsource (lib "eagle-import") (part "FIDUCIAL"))
    )
    (comp (ref "FID603")
      (value "FIDUCIAL")
      (footprint "eagle-import:FIDUCIAL_1MM")
      (libsource (lib "eagle-import") (part "FIDUCIAL"))
    )
    (comp (ref "FID604")
      (value "FIDUCIAL")
      (footprint "eagle-import:FIDUCIAL_1MM")
      (libsource (lib "eagle-import") (part "FIDUCIAL"))
    )
    (comp (ref "IC601")
      (value "LM2904")
      (footprint "eagle-import:SO08")
      (libsource (lib "eagle-import") (part "LM358D"))
    )
    (comp (ref "IC602")
      (value "78L06")
      (footprint "eagle-import:SOT89_ROUND")
      (libsource (lib "eagle-import") (part "78LXXSOT89_ROUND"))
    )
    (comp (ref "IC603")
      (value "6V pos")
      (footprint "eagle-import:78LXX")
      (libsource (lib "eagle-import") (part "v-reg_78LXX"))
    )
    (comp (ref "IC604")
      (value "78L10")
      (footprint "eagle-import:SOT89_ROUND")
      (libsource (lib "eagle-import") (part "78LXXSOT89_ROUND"))
    )
    (comp (ref "IC605")
      (value "4028")
      (footprint "eagle-import:SO16")
      (libsource (lib "eagle-import") (part "4028D"))
    )
    (comp (ref "IC607")
      (value "ULN2004")
      (footprint "eagle-import:SO16")
      (libsource (lib "eagle-import") (part "ULN2004AD"))
    )
    (comp (ref "IC608")
      (value "LM339")
      (footprint "eagle-import:SO14")
      (libsource (lib "eagle-import") (part "LM339D"))
    )
    (comp (ref "IC609")
      (value "317TO202H_NOHOLE")
      (footprint "eagle-import:TO220H_NOHOLE")
      (libsource (lib "eagle-import") (part "317TO202H_NOHOLE"))
    )
    (comp (ref "IC610")
      (value "555")
      (footprint "eagle-import:SO08")
      (libsource (lib "eagle-import") (part "555DNE"))
    )
    (comp (ref "IC611")
      (value "4538")
      (footprint "eagle-import:SO16")
      (libsource (lib "eagle-import") (part "4538D"))
    )
    (comp (ref "JP601")
      (value "JP2EJP2_SMALLPADS")
      (footprint "eagle-import:JP2_SMALLPADS")
      (libsource (lib "eagle-import") (part "JP2EJP2_SMALLPADS"))
    )
    (comp (ref "JP602")
      (value "JP2EJP2_SMALLPADS")
      (footprint "eagle-import:JP2_SMALLPADS")
      (libsource (lib "eagle-import") (part "JP2EJP2_SMALLPADS"))
    )
    (comp (ref "JP603")
      (value "JP2EJP2_SMALLPADS")
      (footprint "eagle-import:JP2_SMALLPADS")
      (libsource (lib "eagle-import") (part "JP2EJP2_SMALLPADS"))
    )
    (comp (ref "JP604")
      (value "JP2EJP2_SMALLPADS")
      (footprint "eagle-import:JP2_SMALLPADS")
      (libsource (lib "eagle-import") (part "JP2EJP2_SMALLPADS"))
    )
    (comp (ref "JP605")
      (value "JP2E_ORIG")
      (footprint "eagle-import:JP2_ORIG_SMALLPADS")
      (libsource (lib "eagle-import") (part "JP2E_ORIG"))
    )
    (comp (ref "LED601")
      (value "LEDLD260")
      (footprint "eagle-import:LD260")
      (libsource (lib "eagle-import") (part "LEDLD260"))
    )
    (comp (ref "LED602")
      (value "LEDLD260")
      (footprint "eagle-import:LD260")
      (libsource (lib "eagle-import") (part "LEDLD260"))
    )
    (comp (ref "LED603")
      (value "LEDLD260")
      (footprint "eagle-import:LD260")
      (libsource (lib "eagle-import") (part "LEDLD260"))
    )
    (comp (ref "LED604")
      (value "LEDLD260")
      (footprint "eagle-import:LD260")
      (libsource (lib "eagle-import") (part "LEDLD260"))
    )
    (comp (ref "LED605")
      (value "LEDLD260")
      (footprint "eagle-import:LD260")
      (libsource (lib "eagle-import") (part "LEDLD260"))
    )
    (comp (ref "LED606")
      (value "LEDLD260")
      (footprint "eagle-import:LD260")
      (libsource (lib "eagle-import") (part "LEDLD260"))
    )
    (comp (ref "Q601")
      (value "BA.")
      (footprint "eagle-import:SOT89")
      (libsource (lib "eagle-import") (part "PNP-TRANSISTOR_SOT89"))
    )
    (comp (ref "Q602")
      (value "BA.")
      (footprint "eagle-import:SOT89")
      (libsource (lib "eagle-import") (part "PNP-TRANSISTOR_SOT89"))
    )
    (comp (ref "Q603")
      (value "MY")
      (footprint "eagle-import:SOT89")
      (libsource (lib "eagle-import") (part "NPN-TRANSISTOR_SOT89"))
    )
    (comp (ref "Q604")
      (value "BA")
      (footprint "eagle-import:SOT89")
      (libsource (lib "eagle-import") (part "PNP-TRANSISTOR_SOT89"))
    )
    (comp (ref "Q605")
      (value "BA")
      (footprint "eagle-import:SOT89")
      (libsource (lib "eagle-import") (part "PNP-TRANSISTOR_SOT89"))
    )
    (comp (ref "Q606")
      (value "J1")
      (footprint "eagle-import:SOT-23")
      (fields (field (name "MPN") "BSS138W-7-F"))
      (libsource (lib "eagle-import") (part "SMD-MOSFET-N-CH-50V-200MA-BSS138W-7-F(SOT-23)"))
    )
    (comp (ref "Q607")
      (value "J1")
      (footprint "eagle-import:SOT-23")
      (fields (field (name "MPN") "BSS138W-7-F"))
      (libsource (lib "eagle-import") (part "SMD-MOSFET-N-CH-50V-200MA-BSS138W-7-F(SOT-23)"))
    )
    (comp (ref "R601")
      (value "102")
      (footprint "eagle-import:R0805")
      (fields (field (name "MPN") "RC0805JR-071KL"))
      (libsource (lib "eagle-import") (part "SMD-RES-1K-5%-1/8W(0805)"))
    )
    (comp (ref "R602")
      (value "13")
      (footprint "eagle-import:R1206")
      (fields (field (name "MPN") "RC1206JR-0713RL"))
      (libsource (lib "eagle-import") (part "SMD-RES-13R-5%-1/4W(1206)"))
    )
    (comp (ref "R603")
      (value "R_user")
      (footprint "eagle-import:R0805")
      (libsource (lib "eagle-import") (part "R-EU_R0805"))
    )
    (comp (ref "R605")
      (value "4701")
      (footprint "eagle-import:R0805")
      (fields (field (name "MPN") "RC0805JR-074K7L"))
      (libsource (lib "eagle-import") (part "SMD-RES-4.7K-5%-1/8W(0805)"))
    )
    (comp (ref "R606")
      (value "13")
      (footprint "eagle-import:R1206")
      (fields (field (name "MPN") "RC1206JR-0713RL"))
      (libsource (lib "eagle-import") (part "SMD-RES-13R-5%-1/4W(1206)"))
    )
    (comp (ref "R607")
      (value "1002")
      (footprint "eagle-import:R0805")
      (fields (field (name "MPN") "RC0805FR-0710KL"))
      (libsource (lib "eagle-import") (part "SMD-RES-10K-1%-1/8W(0805)"))
    )
    (comp (ref "R608")
      (value "1002")
      (footprint "eagle-import:R0805")
      (fields (field (name "MPN") "RC0805FR-0710KL"))
      (libsource (lib "eagle-import") (part "SMD-RES-10K-1%-1/8W(0805)"))
    )
    (comp (ref "R609")
      (value "104")
      (footprint "eagle-import:R0805")
      (fields (field (name "MPN") "RC0805FR-0710KL"))
      (libsource (lib "eagle-import") (part "SMD-RES-10K-1%-1/8W(0805)"))
    )
    (comp (ref "R610")
      (value "104")
      (footprint "eagle-import:R0805")
      (fields (field (name "MPN") "RC0805FR-0710KL"))
      (libsource (lib "eagle-import") (part "SMD-RES-10K-1%-1/8W(0805)"))
    )
    (comp (ref "R611")
      (value "104")
      (footprint "eagle-import:R0805")
      (fields (field (name "MPN") "RC0805FR-0710KL"))
      (libsource (lib "eagle-import") (part "SMD-RES-10K-1%-1/8W(0805)"))
    )
    (comp (ref "R612")
      (value "102")
      (footprint "eagle-import:R0805")
      (fields (field (name "MPN") "RC0805JR-071KL"))
      (libsource (lib "eagle-import") (part "SMD-RES-1K-5%-1/8W(0805)"))
    )
    (comp (ref "R613")
      (value "102")
      (footprint "eagle-import:R0805")
      (fields (field (name "MPN") "RC0805JR-071KL"))
      (libsource (lib "eagle-import") (part "SMD-RES-1K-5%-1/8W(0805)"))
    )
    (comp (ref "R614")
      (value "102")
      (footprint "eagle-import:R0805")
      (fields (field (name "MPN") "RC0805JR-071KL"))
      (libsource (lib "eagle-import") (part "SMD-RES-1K-5%-1/8W(0805)"))
    )
    (comp (ref "R615")
      (value "100")
      (footprint "eagle-import:R0805")
      (fields (field (name "MPN") "RC0805JR-07220RL"))
      (libsource (lib "eagle-import") (part "SMD-RES-220R-5%-1/8W(0805)"))
    )
    (comp (ref "R616")
      (value "4701")
      (footprint "eagle-import:R0805")
      (fields (field (name "MPN") "RC0805JR-074K7L"))
      (libsource (lib "eagle-import") (part "SMD-RES-4.7K-5%-1/8W(0805)"))
    )
    (comp (ref "R617")
      (value "2702")
      (footprint "eagle-import:R0805")
      (fields (field (name "MPN") "RC0805JR-074K7L"))
      (libsource (lib "eagle-import") (part "SMD-RES-4.7K-5%-1/8W(0805)"))
    )
    (comp (ref "R618")
      (value "13")
      (footprint "eagle-import:R1206")
      (fields (field (name "MPN") "RC1206JR-0713RL"))
      (libsource (lib "eagle-import") (part "SMD-RES-13R-5%-1/4W(1206)"))
    )
    (comp (ref "R619")
      (value "2201")
      (footprint "eagle-import:R0805")
      (fields (field (name "MPN") "RC0805JR-072K2L"))
      (libsource (lib "eagle-import") (part "SMD-RES-2.2K-5%-1/8W(0805)"))
    )
    (comp (ref "R620")
      (value "1002")
      (footprint "eagle-import:R0805")
      (fields (field (name "MPN") "RC0805FR-0710KL"))
      (libsource (lib "eagle-import") (part "SMD-RES-10K-1%-1/8W(0805)"))
    )
    (comp (ref "R621")
      (value "1502")
      (footprint "eagle-import:R0805")
      (fields (field (name "MPN") "RC0805FR-0710KL"))
      (libsource (lib "eagle-import") (part "SMD-RES-10K-1%-1/8W(0805)"))
    )
    (comp (ref "R622")
      (value "2702")
      (footprint "eagle-import:R0805")
      (fields (field (name "MPN") "RC0805JR-074K7L"))
      (libsource (lib "eagle-import") (part "SMD-RES-4.7K-5%-1/8W(0805)"))
    )
    (comp (ref "R623")
      (value "2702")
      (footprint "eagle-import:R0805")
      (fields (field (name "MPN") "RC0805JR-074K7L"))
      (libsource (lib "eagle-import") (part "SMD-RES-4.7K-5%-1/8W(0805)"))
    )
    (comp (ref "R624")
      (value "1002")
      (footprint "eagle-import:R0805")
      (fields (field (name "MPN") "RC0805FR-0710KL"))
      (libsource (lib "eagle-import") (part "SMD-RES-10K-1%-1/8W(0805)"))
    )
    (comp (ref "R625")
      (value "104")
      (footprint "eagle-import:R0805")
      (fields (field (name "MPN") "RC0805FR-0710KL"))
      (libsource (lib "eagle-import") (part "SMD-RES-10K-1%-1/8W(0805)"))
    )
    (comp (ref "R626")
      (value "4701")
      (footprint "eagle-import:R0805")
      (fields (field (name "MPN") "RC0805JR-074K7L"))
      (libsource (lib "eagle-import") (part "SMD-RES-4.7K-5%-1/8W(0805)"))
    )
    (comp (ref "R627")
      (value "47")
      (footprint "eagle-import:V235_17_1MM")
      (libsource (lib "eagle-import") (part "R-EU_V235/17_1MM"))
    )
    (comp (ref "R628")
      (value "102")
      (footprint "eagle-import:R0805")
      (fields (field (name "MPN") "RC0805JR-071KL"))
      (libsource (lib "eagle-import") (part "SMD-RES-1K-5%-1/8W(0805)"))
    )
    (comp (ref "R629")
      (value "47")
      (footprint "eagle-import:V235_17_1MM")
      (libsource (lib "eagle-import") (part "R-EU_V235/17_1MM"))
    )
    (comp (ref "R630")
      (value "104")
      (footprint "eagle-import:R0805")
      (fields (field (name "MPN") "RC0805FR-0710KL"))
      (libsource (lib "eagle-import") (part "SMD-RES-10K-1%-1/8W(0805)"))
    )
    (comp (ref "R631")
      (value "1502")
      (footprint "eagle-import:R0805")
      (fields (field (name "MPN") "RC0805FR-0710KL"))
      (libsource (lib "eagle-import") (part "SMD-RES-10K-1%-1/8W(0805)"))
    )
    (comp (ref "R632")
      (value "1002")
      (footprint "eagle-import:R0805")
      (fields (field (name "MPN") "RC0805FR-0710KL"))
      (libsource (lib "eagle-import") (part "SMD-RES-10K-1%-1/8W(0805)"))
    )
    (comp (ref "R633")
      (value "2201")
      (footprint "eagle-import:R0805")
      (fields (field (name "MPN") "RC0805JR-072K2L"))
      (libsource (lib "eagle-import") (part "SMD-RES-2.2K-5%-1/8W(0805)"))
    )
    (comp (ref "R634")
      (value "13")
      (footprint "eagle-import:R1206")
      (fields (field (name "MPN") "RC1206JR-0713RL"))
      (libsource (lib "eagle-import") (part "SMD-RES-13R-5%-1/4W(1206)"))
    )
    (comp (ref "R635")
      (value "104")
      (footprint "eagle-import:R0805")
      (fields (field (name "MPN") "RC0805FR-0710KL"))
      (libsource (lib "eagle-import") (part "SMD-RES-10K-1%-1/8W(0805)"))
    )
    (comp (ref "R636")
      (value "47")
      (footprint "eagle-import:V235_17_1MM")
      (libsource (lib "eagle-import") (part "R-EU_V235/17_1MM"))
    )
    (comp (ref "R637")
      (value "47")
      (footprint "eagle-import:V235_17_1MM")
      (libsource (lib "eagle-import") (part "R-EU_V235/17_1MM"))
    )
    (comp (ref "R638")
      (value "100")
      (footprint "eagle-import:R0805")
      (fields (field (name "MPN") "RC0805JR-072K2L"))
      (libsource (lib "eagle-import") (part "SMD-RES-2.2K-5%-1/8W(0805)"))
    )
    (comp (ref "R639")
      (value "(101)")
      (footprint "eagle-import:R0805")
      (fields (field (name "MPN") "RC0805JR-072K2L"))
      (libsource (lib "eagle-import") (part "SMD-RES-2.2K-5%-1/8W(0805)"))
    )
    (comp (ref "R640")
      (value "2702")
      (footprint "eagle-import:R0805")
      (fields (field (name "MPN") "RC0805FR-0710KL"))
      (libsource (lib "eagle-import") (part "SMD-RES-10K-1%-1/8W(0805)"))
    )
    (comp (ref "R641")
      (value "104")
      (footprint "eagle-import:R0805")
      (fields (field (name "MPN") "RC0805FR-0710KL"))
      (libsource (lib "eagle-import") (part "SMD-RES-10K-1%-1/8W(0805)"))
    )
    (comp (ref "R642")
      (value "(1000)")
      (footprint "eagle-import:R0805")
      (fields (field (name "MPN") "RC0805JR-07100RL"))
      (libsource (lib "eagle-import") (part "SMD-RES-100R-5%-1/8W(0805)"))
    )
    (comp (ref "R643")
      (value "(101)")
      (footprint "eagle-import:R0805")
      (fields (field (name "MPN") "RC0805JR-07100RL"))
      (libsource (lib "eagle-import") (part "SMD-RES-100R-5%-1/8W(0805)"))
    )
    (comp (ref "R644")
      (value "(1002)")
      (footprint "eagle-import:R0805")
      (fields (field (name "MPN") "RC0805FR-0710KL"))
      (libsource (lib "eagle-import") (part "SMD-RES-10K-1%-1/8W(0805)"))
    )
    (comp (ref "R645")
      (value "2702")
      (footprint "eagle-import:R0805")
      (fields (field (name "MPN") "RC0805JR-074K7L"))
      (libsource (lib "eagle-import") (part "SMD-RES-4.7K-5%-1/8W(0805)"))
    )
    (comp (ref "R646")
      (value "(1002)")
      (footprint "eagle-import:R0805")
      (fields (field (name "MPN") "RC0805JR-074K7L"))
      (libsource (lib "eagle-import") (part "SMD-RES-4.7K-5%-1/8W(0805)"))
    )
    (comp (ref "SJ601")
      (value "SJ")
      (footprint "eagle-import:SJ")
      (libsource (lib "eagle-import") (part "SJ"))
    )
    (comp (ref "START601")
      (value "TPSB2.0")
      (footprint "eagle-import:B2.0")
      (libsource (lib "eagle-import") (part "TPSB2.0"))
    )
    (comp (ref "TP185")
      (value "TPSB2.0")
      (footprint "eagle-import:B2.0")
      (libsource (lib "eagle-import") (part "TPSB2.0"))
    )
    (comp (ref "TP186")
      (value "TPSB2.0")
      (footprint "eagle-import:B2.0")
      (libsource (lib "eagle-import") (part "TPSB2.0"))
    )
    (comp (ref "TP187")
      (value "TPSB2.0")
      (footprint "eagle-import:B2.0")
      (libsource (lib "eagle-import") (part "TPSB2.0"))
    )
    (comp (ref "TP188")
      (value "TPSB2.0")
      (footprint "eagle-import:B2.0")
      (libsource (lib "eagle-import") (part "TPSB2.0"))
    )
    (comp (ref "TP189")
      (value "TPSB2.0")
      (footprint "eagle-import:B2.0")
      (libsource (lib "eagle-import") (part "TPSB2.0"))
    )
    (comp (ref "TP190")
      (value "TPSB2.0")
      (footprint "eagle-import:B2.0")
      (libsource (lib "eagle-import") (part "TPSB2.0"))
    )
    (comp (ref "TP191")
      (value "TPSB2.0")
      (footprint "eagle-import:B2.0")
      (libsource (lib "eagle-import") (part "TPSB2.0"))
    )
    (comp (ref "TP192")
      (value "TPSB2.0")
      (footprint "eagle-import:B2.0")
      (libsource (lib "eagle-import") (part "TPSB2.0"))
    )
    (comp (ref "TP193")
      (value "TPSB2.0")
      (footprint "eagle-import:B2.0")
      (libsource (lib "eagle-import") (part "TPSB2.0"))
    )
    (comp (ref "TP194")
      (value "TPSB2.0")
      (footprint "eagle-import:B2.0")
      (libsource (lib "eagle-import") (part "TPSB2.0"))
    )
    (comp (ref "TP195")
      (value "TPSB2.0")
      (footprint "eagle-import:B2.0")
      (libsource (lib "eagle-import") (part "TPSB2.0"))
    )
    (comp (ref "TP196")
      (value "TPSB2.0")
      (footprint "eagle-import:B2.0")
      (libsource (lib "eagle-import") (part "TPSB2.0"))
    )
    (comp (ref "TP197")
      (value "TPSB2.0")
      (footprint "eagle-import:B2.0")
      (libsource (lib "eagle-import") (part "TPSB2.0"))
    )
    (comp (ref "TP198")
      (value "TPSB2.0")
      (footprint "eagle-import:B2.0")
      (libsource (lib "eagle-import") (part "TPSB2.0"))
    )
    (comp (ref "TP199")
      (value "TPSB2.0")
      (footprint "eagle-import:B2.0")
      (libsource (lib "eagle-import") (part "TPSB2.0"))
    )
    (comp (ref "TP200")
      (value "TPSB2.0")
      (footprint "eagle-import:B2.0")
      (libsource (lib "eagle-import") (part "TPSB2.0"))
    )
    (comp (ref "TP201")
      (value "TPSB2.0")
      (footprint "eagle-import:B2.0")
      (libsource (lib "eagle-import") (part "TPSB2.0"))
    )
    (comp (ref "TP202")
      (value "TPSB2.0")
      (footprint "eagle-import:B2.0")
      (libsource (lib "eagle-import") (part "TPSB2.0"))
    )
    (comp (ref "TP203")
      (value "TPSB1,27")
      (footprint "eagle-import:B1,27")
      (libsource (lib "eagle-import") (part "TPSB1,27"))
    )
    (comp (ref "TP204")
      (value "TPSB2.0")
      (footprint "eagle-import:B2.0")
      (libsource (lib "eagle-import") (part "TPSB2.0"))
    )
    (comp (ref "TP205")
      (value "TPSB2.0")
      (footprint "eagle-import:B2.0")
      (libsource (lib "eagle-import") (part "TPSB2.0"))
    )
    (comp (ref "TP206")
      (value "TPSB2.0")
      (footprint "eagle-import:B2.0")
      (libsource (lib "eagle-import") (part "TPSB2.0"))
    )
    (comp (ref "TP207")
      (value "TPSB2.0")
      (footprint "eagle-import:B2.0")
      (libsource (lib "eagle-import") (part "TPSB2.0"))
    )
    (comp (ref "X601")
      (value "CON_BMWV2")
      (footprint "eagle-import:24-PIN_V2")
      (libsource (lib "eagle-import") (part "CON_BMWV2"))
    )
    (comp (ref "X602")
      (value "22-23-2021")
      (footprint "eagle-import:22-23-2021")
      (fields (field (name "MF") "MOLEX"))
      (libsource (lib "eagle-import") (part "22-23-2021"))
    )
    (comp (ref "X603")
      (value "22-23-2051")
      (footprint "eagle-import:22-23-2051")
      (fields (field (name "MF") "MOLEX"))
      (libsource (lib "eagle-import") (part "22-23-2051"))
    )
    (comp (ref "6V4")
      (value "TPSB2.0")
      (footprint "eagle-import:B2.0")
      (libsource (lib "eagle-import") (part "TPSB2.0"))
    )
    (comp (ref "10V4")
      (value "TPSB2.0")
      (footprint "eagle-import:B2.0")
      (libsource (lib "eagle-import") (part "TPSB2.0"))
    )
    (comp (ref "19")
      (value "2081-1132")
      (footprint "eagle-import:12-PIN")
      (libsource (lib "eagle-import") (part "2081-1132"))
    )
    (comp (ref "20")
      (value "2081-1132")
      (footprint "eagle-import:12-PIN")
      (libsource (lib "eagle-import") (part "2081-1132"))
    )
    (comp (ref "C31")
      (value "100u")
      (footprint "eagle-import:C1206")
      (fields (field (name "MPN") "GRM31CR60J107ME39L"))
      (libsource (lib "eagle-import") (part "CERAMIC-100UF-6.3V-20%-X5R(1206)"))
    )
    (comp (ref "C32")
      (value "100u")
      (footprint "eagle-import:C1206")
      (fields (field (name "MPN") "GRM31CR60J107ME39L"))
      (libsource (lib "eagle-import") (part "CERAMIC-100UF-6.3V-20%-X5R(1206)"))
    )
    (comp (ref "C33")
      (value "100nF,")
      (footprint "eagle-import:C0805")
      (fields (field (name "MPN") "CC0805KRX7R9BB104"))
      (libsource (lib "eagle-import") (part "CERAMIC-100NF-50V-10%-X7R(0805)"))
    )
    (comp (ref "C34")
      (value "4.7u")
      (footprint "eagle-import:C0805")
      (fields (field (name "MPN") "CC0805KKX5R8BB475"))
      (libsource (lib "eagle-import") (part "CERAMIC-4.7UF-25V-10%-X5R(0805)"))
    )
    (comp (ref "C35")
      (value "100nF.")
      (footprint "eagle-import:C0805")
      (fields (field (name "MPN") "CC0805KRX7R9BB104"))
      (libsource (lib "eagle-import") (part "CERAMIC-100NF-50V-10%-X7R(0805)"))
    )
    (comp (ref "C36")
      (value "100nF.")
      (footprint "eagle-import:C0805")
      (fields (field (name "MPN") "CC0805KRX7R9BB104"))
      (libsource (lib "eagle-import") (part "CERAMIC-100NF-50V-10%-X7R(0805)"))
    )
    (comp (ref "C37")
      (value "2.2nF")
      (footprint "eagle-import:C0805")
      (fields (field (name "MPN") "CC0805KRX7R9BB104"))
      (libsource (lib "eagle-import") (part "CERAMIC-100NF-50V-10%-X7R(0805)"))
    )
    (comp (ref "C38")
      (value "100nF")
      (footprint "eagle-import:C0805")
      (fields (field (name "MPN") "CC0805KRX7R9BB104"))
      (libsource (lib "eagle-import") (part "CERAMIC-100NF-50V-10%-X7R(0805)"))
    )
    (comp (ref "C39")
      (value "100nF")
      (footprint "eagle-import:C0805")
      (fields (field (name "MPN") "CC0805KRX7R9BB104"))
      (libsource (lib "eagle-import") (part "CERAMIC-100NF-50V-10%-X7R(0805)"))
    )
    (comp (ref "C40")
      (value "100nF,")
      (footprint "eagle-import:C0805")
      (fields (field (name "MPN") "CC0805KRX7R9BB104"))
      (libsource (lib "eagle-import") (part "CERAMIC-100NF-50V-10%-X7R(0805)"))
    )
    (comp (ref "D34")
      (value "1N4007")
      (footprint "eagle-import:DO-214AC")
      (libsource (lib "eagle-import") (part "DIODE-GEN-PURPOSE-1KV-1A(DO-214AC)"))
    )
    (comp (ref "D35")
      (value "1N4007,")
      (footprint "eagle-import:DO-214AC")
      (fields (field (name "MPN") "1N4007"))
      (libsource (lib "eagle-import") (part "DIODE-GEN-PURPOSE-1KV-1A(DO-214AC)"))
    )
    (comp (ref "D36")
      (value "1N4007,")
      (footprint "eagle-import:DO-214AC")
      (fields (field (name "MPN") "1N4007"))
      (libsource (lib "eagle-import") (part "DIODE-GEN-PURPOSE-1KV-1A(DO-214AC)"))
    )
    (comp (ref "D37")
      (value "1N4007.")
      (footprint "eagle-import:DO-214AC")
      (fields (field (name "MPN") "1N4007"))
      (libsource (lib "eagle-import") (part "DIODE-GEN-PURPOSE-1KV-1A(DO-214AC)"))
    )
    (comp (ref "D38")
      (value "1N5817")
      (footprint "eagle-import:DO-214AC_SLIM")
      (libsource (lib "eagle-import") (part "DIODE-GEN-PURPOSE-1KV-1A(DO-214AC)DO-214AC/1206"))
    )
    (comp (ref "D39")
      (value "1N5817.")
      (footprint "eagle-import:DO-214AC_SLIM")
      (libsource (lib "eagle-import") (part "DIODE-GEN-PURPOSE-1KV-1A(DO-214AC)DO-214AC/1206"))
    )
    (comp (ref "D40")
      (value "1N5817.")
      (footprint "eagle-import:DO-214AC_SLIM")
      (libsource (lib "eagle-import") (part "DIODE-GEN-PURPOSE-1KV-1A(DO-214AC)DO-214AC/1206"))
    )
    (comp (ref "D41")
      (value "1N5817")
      (footprint "eagle-import:DO-214AC_SLIM")
      (libsource (lib "eagle-import") (part "DIODE-GEN-PURPOSE-1KV-1A(DO-214AC)DO-214AC/1206"))
    )
    (comp (ref "D42")
      (value "1N4007.")
      (footprint "eagle-import:DO-214AC")
      (fields (field (name "MPN") "1N4007"))
      (libsource (lib "eagle-import") (part "DIODE-GEN-PURPOSE-1KV-1A(DO-214AC)"))
    )
    (comp (ref "D43")
      (value "1N4007")
      (footprint "eagle-import:DO-214AC")
      (libsource (lib "eagle-import") (part "DIODE-GEN-PURPOSE-1KV-1A(DO-214AC)"))
    )
    (comp (ref "D44")
      (value "SM6T")
      (footprint "eagle-import:DO214AA")
      (libsource (lib "eagle-import") (part "SM6T"))
    )
    (comp (ref "FID15")
      (value "FIDUCIAL")
      (footprint "eagle-import:FIDUCIAL_1MM")
      (libsource (lib "eagle-import") (part "FIDUCIAL"))
    )
    (comp (ref "FID16")
      (value "FIDUCIAL")
      (footprint "eagle-import:FIDUCIAL_1MM")
      (libsource (lib "eagle-import") (part "FIDUCIAL"))
    )
    (comp (ref "FID17")
      (value "FIDUCIAL")
      (footprint "eagle-import:FIDUCIAL_1MM")
      (libsource (lib "eagle-import") (part "FIDUCIAL"))
    )
    (comp (ref "FID18")
      (value "FIDUCIAL")
      (footprint "eagle-import:FIDUCIAL_1MM")
      (libsource (lib "eagle-import") (part "FIDUCIAL"))
    )
    (comp (ref "IC31")
      (value "4028")
      (footprint "eagle-import:SO16")
      (libsource (lib "eagle-import") (part "4028D"))
    )
    (comp (ref "IC32")
      (value "6V pos")
      (footprint "eagle-import:78LXX")
      (libsource (lib "eagle-import") (part "v-reg_78LXX"))
    )
    (comp (ref "IC33")
      (value "317TO202H_NOHOLE")
      (footprint "eagle-import:TO220H_NOHOLE")
      (libsource (lib "eagle-import") (part "317TO202H_NOHOLE"))
    )
    (comp (ref "IC34")
      (value "ULN2004")
      (footprint "eagle-import:SO16")
      (libsource (lib "eagle-import") (part "ULN2004AD"))
    )
    (comp (ref "IC35")
      (value "LM339")
      (footprint "eagle-import:SO14")
      (libsource (lib "eagle-import") (part "LM339D"))
    )
    (comp (ref "IC36")
      (value "78L06")
      (footprint "eagle-import:SOT89_ROUND")
      (libsource (lib "eagle-import") (part "78LXXSOT89_ROUND"))
    )
    (comp (ref "IC37")
      (value "555")
      (footprint "eagle-import:SO08")
      (libsource (lib "eagle-import") (part "555DNE"))
    )
    (comp (ref "IC38")
      (value "4538")
      (footprint "eagle-import:SO16")
      (libsource (lib "eagle-import") (part "4538D"))
    )
    (comp (ref "IC39")
      (value "78L10")
      (footprint "eagle-import:SOT89_ROUND")
      (libsource (lib "eagle-import") (part "78LXXSOT89_ROUND"))
    )
    (comp (ref "IC40")
      (value "LM2904")
      (footprint "eagle-import:SO08")
      (libsource (lib "eagle-import") (part "LM358D"))
    )
    (comp (ref "JP16")
      (value "JP2EJP2_SMALLPADS")
      (footprint "eagle-import:JP2_SMALLPADS")
      (libsource (lib "eagle-import") (part "JP2EJP2_SMALLPADS"))
    )
    (comp (ref "JP17")
      (value "JP2E_ORIG")
      (footprint "eagle-import:JP2_ORIG_SMALLPADS")
      (libsource (lib "eagle-import") (part "JP2E_ORIG"))
    )
    (comp (ref "JP18")
      (value "JP2EJP2_SMALLPADS")
      (footprint "eagle-import:JP2_SMALLPADS")
      (libsource (lib "eagle-import") (part "JP2EJP2_SMALLPADS"))
    )
    (comp (ref "JP19")
      (value "JP2EJP2_SMALLPADS")
      (footprint "eagle-import:JP2_SMALLPADS")
      (libsource (lib "eagle-import") (part "JP2EJP2_SMALLPADS"))
    )
    (comp (ref "JP20")
      (value "JP2EJP2_SMALLPADS")
      (footprint "eagle-import:JP2_SMALLPADS")
      (libsource (lib "eagle-import") (part "JP2EJP2_SMALLPADS"))
    )
    (comp (ref "LED19")
      (value "LEDLD260")
      (footprint "eagle-import:LD260")
      (libsource (lib "eagle-import") (part "LEDLD260"))
    )
    (comp (ref "LED20")
      (value "LEDLD260")
      (footprint "eagle-import:LD260")
      (libsource (lib "eagle-import") (part "LEDLD260"))
    )
    (comp (ref "LED21")
      (value "LEDLD260")
      (footprint "eagle-import:LD260")
      (libsource (lib "eagle-import") (part "LEDLD260"))
    )
    (comp (ref "LED22")
      (value "LEDLD260")
      (footprint "eagle-import:LD260")
      (libsource (lib "eagle-import") (part "LEDLD260"))
    )
    (comp (ref "LED23")
      (value "LEDLD260")
      (footprint "eagle-import:LD260")
      (libsource (lib "eagle-import") (part "LEDLD260"))
    )
    (comp (ref "LED24")
      (value "LEDLD260")
      (footprint "eagle-import:LD260")
      (libsource (lib "eagle-import") (part "LEDLD260"))
    )
    (comp (ref "Q22")
      (value "BA")
      (footprint "eagle-import:SOT89")
      (libsource (lib "eagle-import") (part "PNP-TRANSISTOR_SOT89"))
    )
    (comp (ref "Q23")
      (value "BA.")
      (footprint "eagle-import:SOT89")
      (libsource (lib "eagle-import") (part "PNP-TRANSISTOR_SOT89"))
    )
    (comp (ref "Q24")
      (value "BA.")
      (footprint "eagle-import:SOT89")
      (libsource (lib "eagle-import") (part "PNP-TRANSISTOR_SOT89"))
    )
    (comp (ref "Q25")
      (value "BA")
      (footprint "eagle-import:SOT89")
      (libsource (lib "eagle-import") (part "PNP-TRANSISTOR_SOT89"))
    )
    (comp (ref "Q26")
      (value "MY")
      (footprint "eagle-import:SOT89")
      (libsource (lib "eagle-import") (part "NPN-TRANSISTOR_SOT89"))
    )
    (comp (ref "Q27")
      (value "J1")
      (footprint "eagle-import:SOT-23")
      (fields (field (name "MPN") "BSS138W-7-F"))
      (libsource (lib "eagle-import") (part "SMD-MOSFET-N-CH-50V-200MA-BSS138W-7-F(SOT-23)"))
    )
    (comp (ref "Q28")
      (value "J1")
      (footprint "eagle-import:SOT-23")
      (fields (field (name "MPN") "BSS138W-7-F"))
      (libsource (lib "eagle-import") (part "SMD-MOSFET-N-CH-50V-200MA-BSS138W-7-F(SOT-23)"))
    )
    (comp (ref "R181")
      (value "47")
      (footprint "eagle-import:V235_17_1MM")
      (libsource (lib "eagle-import") (part "R-EU_V235/17_1MM"))
    )
    (comp (ref "R182")
      (value "13")
      (footprint "eagle-import:R1206")
      (fields (field (name "MPN") "RC1206JR-0713RL"))
      (libsource (lib "eagle-import") (part "SMD-RES-13R-5%-1/4W(1206)"))
    )
    (comp (ref "R183")
      (value "47")
      (footprint "eagle-import:V235_17_1MM")
      (libsource (lib "eagle-import") (part "R-EU_V235/17_1MM"))
    )
    (comp (ref "R184")
      (value "104")
      (footprint "eagle-import:R0805")
      (fields (field (name "MPN") "RC0805FR-0710KL"))
      (libsource (lib "eagle-import") (part "SMD-RES-10K-1%-1/8W(0805)"))
    )
    (comp (ref "R185")
      (value "104")
      (footprint "eagle-import:R0805")
      (fields (field (name "MPN") "RC0805FR-0710KL"))
      (libsource (lib "eagle-import") (part "SMD-RES-10K-1%-1/8W(0805)"))
    )
    (comp (ref "R186")
      (value "104")
      (footprint "eagle-import:R0805")
      (fields (field (name "MPN") "RC0805FR-0710KL"))
      (libsource (lib "eagle-import") (part "SMD-RES-10K-1%-1/8W(0805)"))
    )
    (comp (ref "R187")
      (value "4701")
      (footprint "eagle-import:R0805")
      (fields (field (name "MPN") "RC0805JR-074K7L"))
      (libsource (lib "eagle-import") (part "SMD-RES-4.7K-5%-1/8W(0805)"))
    )
    (comp (ref "R188")
      (value "1002")
      (footprint "eagle-import:R0805")
      (fields (field (name "MPN") "RC0805FR-0710KL"))
      (libsource (lib "eagle-import") (part "SMD-RES-10K-1%-1/8W(0805)"))
    )
    (comp (ref "R189")
      (value "1002")
      (footprint "eagle-import:R0805")
      (fields (field (name "MPN") "RC0805FR-0710KL"))
      (libsource (lib "eagle-import") (part "SMD-RES-10K-1%-1/8W(0805)"))
    )
    (comp (ref "R190")
      (value "1502")
      (footprint "eagle-import:R0805")
      (fields (field (name "MPN") "RC0805FR-0710KL"))
      (libsource (lib "eagle-import") (part "SMD-RES-10K-1%-1/8W(0805)"))
    )
    (comp (ref "R191")
      (value "104")
      (footprint "eagle-import:R0805")
      (fields (field (name "MPN") "RC0805FR-0710KL"))
      (libsource (lib "eagle-import") (part "SMD-RES-10K-1%-1/8W(0805)"))
    )
    (comp (ref "R192")
      (value "104")
      (footprint "eagle-import:R0805")
      (fields (field (name "MPN") "RC0805FR-0710KL"))
      (libsource (lib "eagle-import") (part "SMD-RES-10K-1%-1/8W(0805)"))
    )
    (comp (ref "R193")
      (value "1502")
      (footprint "eagle-import:R0805")
      (fields (field (name "MPN") "RC0805FR-0710KL"))
      (libsource (lib "eagle-import") (part "SMD-RES-10K-1%-1/8W(0805)"))
    )
    (comp (ref "R194")
      (value "1002")
      (footprint "eagle-import:R0805")
      (fields (field (name "MPN") "RC0805FR-0710KL"))
      (libsource (lib "eagle-import") (part "SMD-RES-10K-1%-1/8W(0805)"))
    )
    (comp (ref "R195")
      (value "2201")
      (footprint "eagle-import:R0805")
      (fields (field (name "MPN") "RC0805JR-072K2L"))
      (libsource (lib "eagle-import") (part "SMD-RES-2.2K-5%-1/8W(0805)"))
    )
    (comp (ref "R196")
      (value "1002")
      (footprint "eagle-import:R0805")
      (fields (field (name "MPN") "RC0805FR-0710KL"))
      (libsource (lib "eagle-import") (part "SMD-RES-10K-1%-1/8W(0805)"))
    )
    (comp (ref "R197")
      (value "4701")
      (footprint "eagle-import:R0805")
      (fields (field (name "MPN") "RC0805JR-074K7L"))
      (libsource (lib "eagle-import") (part "SMD-RES-4.7K-5%-1/8W(0805)"))
    )
    (comp (ref "R198")
      (value "2702")
      (footprint "eagle-import:R0805")
      (fields (field (name "MPN") "RC0805JR-074K7L"))
      (libsource (lib "eagle-import") (part "SMD-RES-4.7K-5%-1/8W(0805)"))
    )
    (comp (ref "R199")
      (value "102")
      (footprint "eagle-import:R0805")
      (fields (field (name "MPN") "RC0805JR-071KL"))
      (libsource (lib "eagle-import") (part "SMD-RES-1K-5%-1/8W(0805)"))
    )
    (comp (ref "R200")
      (value "100")
      (footprint "eagle-import:R0805")
      (fields (field (name "MPN") "RC0805JR-07220RL"))
      (libsource (lib "eagle-import") (part "SMD-RES-220R-5%-1/8W(0805)"))
    )
    (comp (ref "R204")
      (value "(101)")
      (footprint "eagle-import:R0805")
      (fields (field (name "MPN") "RC0805JR-07100RL"))
      (libsource (lib "eagle-import") (part "SMD-RES-100R-5%-1/8W(0805)"))
    )
    (comp (ref "R247")
      (value "(1000)")
      (footprint "eagle-import:R0805")
      (fields (field (name "MPN") "RC0805JR-07100RL"))
      (libsource (lib "eagle-import") (part "SMD-RES-100R-5%-1/8W(0805)"))
    )
    (comp (ref "R248")
      (value "102")
      (footprint "eagle-import:R0805")
      (fields (field (name "MPN") "RC0805JR-071KL"))
      (libsource (lib "eagle-import") (part "SMD-RES-1K-5%-1/8W(0805)"))
    )
    (comp (ref "R249")
      (value "13")
      (footprint "eagle-import:R1206")
      (fields (field (name "MPN") "RC1206JR-0713RL"))
      (libsource (lib "eagle-import") (part "SMD-RES-13R-5%-1/4W(1206)"))
    )
    (comp (ref "R250")
      (value "13")
      (footprint "eagle-import:R1206")
      (fields (field (name "MPN") "RC1206JR-0713RL"))
      (libsource (lib "eagle-import") (part "SMD-RES-13R-5%-1/4W(1206)"))
    )
    (comp (ref "R251")
      (value "2702")
      (footprint "eagle-import:R0805")
      (fields (field (name "MPN") "RC0805JR-074K7L"))
      (libsource (lib "eagle-import") (part "SMD-RES-4.7K-5%-1/8W(0805)"))
    )
    (comp (ref "R252")
      (value "4701")
      (footprint "eagle-import:R0805")
      (fields (field (name "MPN") "RC0805JR-074K7L"))
      (libsource (lib "eagle-import") (part "SMD-RES-4.7K-5%-1/8W(0805)"))
    )
    (comp (ref "R253")
      (value "100")
      (footprint "eagle-import:R0805")
      (fields (field (name "MPN") "RC0805JR-072K2L"))
      (libsource (lib "eagle-import") (part "SMD-RES-2.2K-5%-1/8W(0805)"))
    )
    (comp (ref "R254")
      (value "(101)")
      (footprint "eagle-import:R0805")
      (fields (field (name "MPN") "RC0805JR-072K2L"))
      (libsource (lib "eagle-import") (part "SMD-RES-2.2K-5%-1/8W(0805)"))
    )
    (comp (ref "R255")
      (value "104")
      (footprint "eagle-import:R0805")
      (fields (field (name "MPN") "RC0805FR-0710KL"))
      (libsource (lib "eagle-import") (part "SMD-RES-10K-1%-1/8W(0805)"))
    )
    (comp (ref "R256")
      (value "104")
      (footprint "eagle-import:R0805")
      (fields (field (name "MPN") "RC0805FR-0710KL"))
      (libsource (lib "eagle-import") (part "SMD-RES-10K-1%-1/8W(0805)"))
    )
    (comp (ref "R257")
      (value "(1002)")
      (footprint "eagle-import:R0805")
      (fields (field (name "MPN") "RC0805FR-0710KL"))
      (libsource (lib "eagle-import") (part "SMD-RES-10K-1%-1/8W(0805)"))
    )
    (comp (ref "R258")
      (value "2702")
      (footprint "eagle-import:R0805")
      (fields (field (name "MPN") "RC0805FR-0710KL"))
      (libsource (lib "eagle-import") (part "SMD-RES-10K-1%-1/8W(0805)"))
    )
    (comp (ref "R259")
      (value "47")
      (footprint "eagle-import:V235_17_1MM")
      (libsource (lib "eagle-import") (part "R-EU_V235/17_1MM"))
    )
    (comp (ref "R260")
      (value "47")
      (footprint "eagle-import:V235_17_1MM")
      (libsource (lib "eagle-import") (part "R-EU_V235/17_1MM"))
    )
    (comp (ref "R261")
      (value "2702")
      (footprint "eagle-import:R0805")
      (fields (field (name "MPN") "RC0805JR-074K7L"))
      (libsource (lib "eagle-import") (part "SMD-RES-4.7K-5%-1/8W(0805)"))
    )
    (comp (ref "R262")
      (value "2201")
      (footprint "eagle-import:R0805")
      (fields (field (name "MPN") "RC0805JR-072K2L"))
      (libsource (lib "eagle-import") (part "SMD-RES-2.2K-5%-1/8W(0805)"))
    )
    (comp (ref "R263")
      (value "(1002)")
      (footprint "eagle-import:R0805")
      (fields (field (name "MPN") "RC0805JR-074K7L"))
      (libsource (lib "eagle-import") (part "SMD-RES-4.7K-5%-1/8W(0805)"))
    )
    (comp (ref "R264")
      (value "1002")
      (footprint "eagle-import:R0805")
      (fields (field (name "MPN") "RC0805FR-0710KL"))
      (libsource (lib "eagle-import") (part "SMD-RES-10K-1%-1/8W(0805)"))
    )
    (comp (ref "R265")
      (value "102")
      (footprint "eagle-import:R0805")
      (fields (field (name "MPN") "RC0805JR-071KL"))
      (libsource (lib "eagle-import") (part "SMD-RES-1K-5%-1/8W(0805)"))
    )
    (comp (ref "R266")
      (value "2702")
      (footprint "eagle-import:R0805")
      (fields (field (name "MPN") "RC0805JR-074K7L"))
      (libsource (lib "eagle-import") (part "SMD-RES-4.7K-5%-1/8W(0805)"))
    )
    (comp (ref "R267")
      (value "102")
      (footprint "eagle-import:R0805")
      (fields (field (name "MPN") "RC0805JR-071KL"))
      (libsource (lib "eagle-import") (part "SMD-RES-1K-5%-1/8W(0805)"))
    )
    (comp (ref "R268")
      (value "102")
      (footprint "eagle-import:R0805")
      (fields (field (name "MPN") "RC0805JR-071KL"))
      (libsource (lib "eagle-import") (part "SMD-RES-1K-5%-1/8W(0805)"))
    )
    (comp (ref "R269")
      (value "13")
      (footprint "eagle-import:R1206")
      (fields (field (name "MPN") "RC1206JR-0713RL"))
      (libsource (lib "eagle-import") (part "SMD-RES-13R-5%-1/4W(1206)"))
    )
    (comp (ref "R270")
      (value "R_user")
      (footprint "eagle-import:R0805")
      (libsource (lib "eagle-import") (part "R-EU_R0805"))
    )
    (comp (ref "SJ4") (value "SJ") (footprint "eagle-import:SJ") (libsource (lib "eagle-import") (part "SJ")))
    (comp (ref "START4")
      (value "TPSB2.0")
      (footprint "eagle-import:B2.0")
      (libsource (lib "eagle-import") (part "TPSB2.0"))
    )
    (comp (ref "TP208")
      (value "TPSB2.0")
      (footprint "eagle-import:B2.0")
      (libsource (lib "eagle-import") (part "TPSB2.0"))
    )
    (comp (ref "TP209")
      (value "TPSB2.0")
      (footprint "eagle-import:B2.0")
      (libsource (lib "eagle-import") (part "TPSB2.0"))
    )
    (comp (ref "TP210")
      (value "TPSB2.0")
      (footprint "eagle-import:B2.0")
      (libsource (lib "eagle-import") (part "TPSB2.0"))
    )
    (comp (ref "TP211")
      (value "TPSB2.0")
      (footprint "eagle-import:B2.0")
      (libsource (lib "eagle-import") (part "TPSB2.0"))
    )
    (comp (ref "TP212")
      (value "TPSB2.0")
      (footprint "eagle-import:B2.0")
      (libsource (lib "eagle-import") (part "TPSB2.0"))
    )
    (comp (ref "TP213")
      (value "TPSB2.0")
      (footprint "eagle-import:B2.0")
      (libsource (lib "eagle-import") (part "TPSB2.0"))
    )
    (comp (ref "TP214")
      (value "TPSB2.0")
      (footprint "eagle-import:B2.0")
      (libsource (lib "eagle-import") (part "TPSB2.0"))
    )
    (comp (ref "TP215")
      (value "TPSB2.0")
      (footprint "eagle-import:B2.0")
      (libsource (lib "eagle-import") (part "TPSB2.0"))
    )
    (comp (ref "TP216")
      (value "TPSB2.0")
      (footprint "eagle-import:B2.0")
      (libsource (lib "eagle-import") (part "TPSB2.0"))
    )
    (comp (ref "TP217")
      (value "TPSB2.0")
      (footprint "eagle-import:B2.0")
      (libsource (lib "eagle-import") (part "TPSB2.0"))
    )
    (comp (ref "TP218")
      (value "TPSB2.0")
      (footprint "eagle-import:B2.0")
      (libsource (lib "eagle-import") (part "TPSB2.0"))
    )
    (comp (ref "TP219")
      (value "TPSB2.0")
      (footprint "eagle-import:B2.0")
      (libsource (lib "eagle-import") (part "TPSB2.0"))
    )
    (comp (ref "TP220")
      (value "TPSB2.0")
      (footprint "eagle-import:B2.0")
      (libsource (lib "eagle-import") (part "TPSB2.0"))
    )
    (comp (ref "TP221")
      (value "TPSB2.0")
      (footprint "eagle-import:B2.0")
      (libsource (lib "eagle-import") (part "TPSB2.0"))
    )
    (comp (ref "TP222")
      (value "TPSB2.0")
      (footprint "eagle-import:B2.0")
      (libsource (lib "eagle-import") (part "TPSB2.0"))
    )
    (comp (ref "TP223")
      (value "TPSB2.0")
      (footprint "eagle-import:B2.0")
      (libsource (lib "eagle-import") (part "TPSB2.0"))
    )
    (comp (ref "TP224")
      (value "TPSB2.0")
      (footprint "eagle-import:B2.0")
      (libsource (lib "eagle-import") (part "TPSB2.0"))
    )
    (comp (ref "TP225")
      (value "TPSB2.0")
      (footprint "eagle-import:B2.0")
      (libsource (lib "eagle-import") (part "TPSB2.0"))
    )
    (comp (ref "TP226")
      (value "TPSB1,27")
      (footprint "eagle-import:B1,27")
      (libsource (lib "eagle-import") (part "TPSB1,27"))
    )
    (comp (ref "TP227")
      (value "TPSB2.0")
      (footprint "eagle-import:B2.0")
      (libsource (lib "eagle-import") (part "TPSB2.0"))
    )
    (comp (ref "TP228")
      (value "TPSB2.0")
      (footprint "eagle-import:B2.0")
      (libsource (lib "eagle-import") (part "TPSB2.0"))
    )
    (comp (ref "TP229")
      (value "TPSB2.0")
      (footprint "eagle-import:B2.0")
      (libsource (lib "eagle-import") (part "TPSB2.0"))
    )
    (comp (ref "TP230")
      (value "TPSB2.0")
      (footprint "eagle-import:B2.0")
      (libsource (lib "eagle-import") (part "TPSB2.0"))
    )
    (comp (ref "X10")
      (value "CON_BMWV2")
      (footprint "eagle-import:24-PIN_V2")
      (libsource (lib "eagle-import") (part "CON_BMWV2"))
    )
    (comp (ref "X11")
      (value "22-23-2051")
      (footprint "eagle-import:22-23-2051")
      (fields (field (name "MF") "MOLEX"))
      (libsource (lib "eagle-import") (part "22-23-2051"))
    )
    (comp (ref "X12")
      (value "22-23-2021")
      (footprint "eagle-import:22-23-2021")
      (fields (field (name "MF") "MOLEX"))
      (libsource (lib "eagle-import") (part "22-23-2021"))
    )
    (comp (ref "6V5")
      (value "TPSB2.0")
      (footprint "eagle-import:B2.0")
      (libsource (lib "eagle-import") (part "TPSB2.0"))
    )
    (comp (ref "10V5")
      (value "TPSB2.0")
      (footprint "eagle-import:B2.0")
      (libsource (lib "eagle-import") (part "TPSB2.0"))
    )
    (comp (ref "21")
      (value "2081-1132")
      (footprint "eagle-import:12-PIN")
      (libsource (lib "eagle-import") (part "2081-1132"))
    )
    (comp (ref "22")
      (value "2081-1132")
      (footprint "eagle-import:12-PIN")
      (libsource (lib "eagle-import") (part "2081-1132"))
    )
    (comp (ref "C41")
      (value "100u")
      (footprint "eagle-import:C1206")
      (fields (field (name "MPN") "GRM31CR60J107ME39L"))
      (libsource (lib "eagle-import") (part "CERAMIC-100UF-6.3V-20%-X5R(1206)"))
    )
    (comp (ref "C42")
      (value "100u")
      (footprint "eagle-import:C1206")
      (fields (field (name "MPN") "GRM31CR60J107ME39L"))
      (libsource (lib "eagle-import") (part "CERAMIC-100UF-6.3V-20%-X5R(1206)"))
    )
    (comp (ref "C43")
      (value "100nF,")
      (footprint "eagle-import:C0805")
      (fields (field (name "MPN") "CC0805KRX7R9BB104"))
      (libsource (lib "eagle-import") (part "CERAMIC-100NF-50V-10%-X7R(0805)"))
    )
    (comp (ref "C44")
      (value "4.7u")
      (footprint "eagle-import:C0805")
      (fields (field (name "MPN") "CC0805KKX5R8BB475"))
      (libsource (lib "eagle-import") (part "CERAMIC-4.7UF-25V-10%-X5R(0805)"))
    )
    (comp (ref "C45")
      (value "100nF.")
      (footprint "eagle-import:C0805")
      (fields (field (name "MPN") "CC0805KRX7R9BB104"))
      (libsource (lib "eagle-import") (part "CERAMIC-100NF-50V-10%-X7R(0805)"))
    )
    (comp (ref "C46")
      (value "100nF.")
      (footprint "eagle-import:C0805")
      (fields (field (name "MPN") "CC0805KRX7R9BB104"))
      (libsource (lib "eagle-import") (part "CERAMIC-100NF-50V-10%-X7R(0805)"))
    )
    (comp (ref "C47")
      (value "2.2nF")
      (footprint "eagle-import:C0805")
      (fields (field (name "MPN") "CC0805KRX7R9BB104"))
      (libsource (lib "eagle-import") (part "CERAMIC-100NF-50V-10%-X7R(0805)"))
    )
    (comp (ref "C48")
      (value "100nF")
      (footprint "eagle-import:C0805")
      (fields (field (name "MPN") "CC0805KRX7R9BB104"))
      (libsource (lib "eagle-import") (part "CERAMIC-100NF-50V-10%-X7R(0805)"))
    )
    (comp (ref "C49")
      (value "100nF")
      (footprint "eagle-import:C0805")
      (fields (field (name "MPN") "CC0805KRX7R9BB104"))
      (libsource (lib "eagle-import") (part "CERAMIC-100NF-50V-10%-X7R(0805)"))
    )
    (comp (ref "C50")
      (value "100nF,")
      (footprint "eagle-import:C0805")
      (fields (field (name "MPN") "CC0805KRX7R9BB104"))
      (libsource (lib "eagle-import") (part "CERAMIC-100NF-50V-10%-X7R(0805)"))
    )
    (comp (ref "D45")
      (value "1N4007")
      (footprint "eagle-import:DO-214AC")
      (libsource (lib "eagle-import") (part "DIODE-GEN-PURPOSE-1KV-1A(DO-214AC)"))
    )
    (comp (ref "D46")
      (value "1N4007,")
      (footprint "eagle-import:DO-214AC")
      (fields (field (name "MPN") "1N4007"))
      (libsource (lib "eagle-import") (part "DIODE-GEN-PURPOSE-1KV-1A(DO-214AC)"))
    )
    (comp (ref "D47")
      (value "1N4007,")
      (footprint "eagle-import:DO-214AC")
      (fields (field (name "MPN") "1N4007"))
      (libsource (lib "eagle-import") (part "DIODE-GEN-PURPOSE-1KV-1A(DO-214AC)"))
    )
    (comp (ref "D48")
      (value "1N4007.")
      (footprint "eagle-import:DO-214AC")
      (fields (field (name "MPN") "1N4007"))
      (libsource (lib "eagle-import") (part "DIODE-GEN-PURPOSE-1KV-1A(DO-214AC)"))
    )
    (comp (ref "D49")
      (value "1N5817")
      (footprint "eagle-import:DO-214AC_SLIM")
      (libsource (lib "eagle-import") (part "DIODE-GEN-PURPOSE-1KV-1A(DO-214AC)DO-214AC/1206"))
    )
    (comp (ref "D50")
      (value "1N5817.")
      (footprint "eagle-import:DO-214AC_SLIM")
      (libsource (lib "eagle-import") (part "DIODE-GEN-PURPOSE-1KV-1A(DO-214AC)DO-214AC/1206"))
    )
    (comp (ref "D51")
      (value "1N5817.")
      (footprint "eagle-import:DO-214AC_SLIM")
      (libsource (lib "eagle-import") (part "DIODE-GEN-PURPOSE-1KV-1A(DO-214AC)DO-214AC/1206"))
    )
    (comp (ref "D52")
      (value "1N5817")
      (footprint "eagle-import:DO-214AC_SLIM")
      (libsource (lib "eagle-import") (part "DIODE-GEN-PURPOSE-1KV-1A(DO-214AC)DO-214AC/1206"))
    )
    (comp (ref "D53")
      (value "1N4007.")
      (footprint "eagle-import:DO-214AC")
      (fields (field (name "MPN") "1N4007"))
      (libsource (lib "eagle-import") (part "DIODE-GEN-PURPOSE-1KV-1A(DO-214AC)"))
    )
    (comp (ref "D54")
      (value "1N4007")
      (footprint "eagle-import:DO-214AC")
      (libsource (lib "eagle-import") (part "DIODE-GEN-PURPOSE-1KV-1A(DO-214AC)"))
    )
    (comp (ref "D55")
      (value "SM6T")
      (footprint "eagle-import:DO214AA")
      (libsource (lib "eagle-import") (part "SM6T"))
    )
    (comp (ref "FID19")
      (value "FIDUCIAL")
      (footprint "eagle-import:FIDUCIAL_1MM")
      (libsource (lib "eagle-import") (part "FIDUCIAL"))
    )
    (comp (ref "FID20")
      (value "FIDUCIAL")
      (footprint "eagle-import:FIDUCIAL_1MM")
      (libsource (lib "eagle-import") (part "FIDUCIAL"))
    )
    (comp (ref "FID21")
      (value "FIDUCIAL")
      (footprint "eagle-import:FIDUCIAL_1MM")
      (libsource (lib "eagle-import") (part "FIDUCIAL"))
    )
    (comp (ref "FID22")
      (value "FIDUCIAL")
      (footprint "eagle-import:FIDUCIAL_1MM")
      (libsource (lib "eagle-import") (part "FIDUCIAL"))
    )
    (comp (ref "IC41")
      (value "4028")
      (footprint "eagle-import:SO16")
      (libsource (lib "eagle-import") (part "4028D"))
    )
    (comp (ref "IC42")
      (value "6V pos")
      (footprint "eagle-import:78LXX")
      (libsource (lib "eagle-import") (part "v-reg_78LXX"))
    )
    (comp (ref "IC43")
      (value "317TO202H_NOHOLE")
      (footprint "eagle-import:TO220H_NOHOLE")
      (libsource (lib "eagle-import") (part "317TO202H_NOHOLE"))
    )
    (comp (ref "IC44")
      (value "ULN2004")
      (footprint "eagle-import:SO16")
      (libsource (lib "eagle-import") (part "ULN2004AD"))
    )
    (comp (ref "IC45")
      (value "LM339")
      (footprint "eagle-import:SO14")
      (libsource (lib "eagle-import") (part "LM339D"))
    )
    (comp (ref "IC46")
      (value "78L06")
      (footprint "eagle-import:SOT89_ROUND")
      (libsource (lib "eagle-import") (part "78LXXSOT89_ROUND"))
    )
    (comp (ref "IC47")
      (value "555")
      (footprint "eagle-import:SO08")
      (libsource (lib "eagle-import") (part "555DNE"))
    )
    (comp (ref "IC48")
      (value "4538")
      (footprint "eagle-import:SO16")
      (libsource (lib "eagle-import") (part "4538D"))
    )
    (comp (ref "IC49")
      (value "78L10")
      (footprint "eagle-import:SOT89_ROUND")
      (libsource (lib "eagle-import") (part "78LXXSOT89_ROUND"))
    )
    (comp (ref "IC50")
      (value "LM2904")
      (footprint "eagle-import:SO08")
      (libsource (lib "eagle-import") (part "LM358D"))
    )
    (comp (ref "JP21")
      (value "JP2EJP2_SMALLPADS")
      (footprint "eagle-import:JP2_SMALLPADS")
      (libsource (lib "eagle-import") (part "JP2EJP2_SMALLPADS"))
    )
    (comp (ref "JP22")
      (value "JP2E_ORIG")
      (footprint "eagle-import:JP2_ORIG_SMALLPADS")
      (libsource (lib "eagle-import") (part "JP2E_ORIG"))
    )
    (comp (ref "JP23")
      (value "JP2EJP2_SMALLPADS")
      (footprint "eagle-import:JP2_SMALLPADS")
      (libsource (lib "eagle-import") (part "JP2EJP2_SMALLPADS"))
    )
    (comp (ref "JP24")
      (value "JP2EJP2_SMALLPADS")
      (footprint "eagle-import:JP2_SMALLPADS")
      (libsource (lib "eagle-import") (part "JP2EJP2_SMALLPADS"))
    )
    (comp (ref "JP25")
      (value "JP2EJP2_SMALLPADS")
      (footprint "eagle-import:JP2_SMALLPADS")
      (libsource (lib "eagle-import") (part "JP2EJP2_SMALLPADS"))
    )
    (comp (ref "LED25")
      (value "LEDLD260")
      (footprint "eagle-import:LD260")
      (libsource (lib "eagle-import") (part "LEDLD260"))
    )
    (comp (ref "LED26")
      (value "LEDLD260")
      (footprint "eagle-import:LD260")
      (libsource (lib "eagle-import") (part "LEDLD260"))
    )
    (comp (ref "LED27")
      (value "LEDLD260")
      (footprint "eagle-import:LD260")
      (libsource (lib "eagle-import") (part "LEDLD260"))
    )
    (comp (ref "LED28")
      (value "LEDLD260")
      (footprint "eagle-import:LD260")
      (libsource (lib "eagle-import") (part "LEDLD260"))
    )
    (comp (ref "LED29")
      (value "LEDLD260")
      (footprint "eagle-import:LD260")
      (libsource (lib "eagle-import") (part "LEDLD260"))
    )
    (comp (ref "LED30")
      (value "LEDLD260")
      (footprint "eagle-import:LD260")
      (libsource (lib "eagle-import") (part "LEDLD260"))
    )
    (comp (ref "Q29")
      (value "BA")
      (footprint "eagle-import:SOT89")
      (libsource (lib "eagle-import") (part "PNP-TRANSISTOR_SOT89"))
    )
    (comp (ref "Q30")
      (value "BA.")
      (footprint "eagle-import:SOT89")
      (libsource (lib "eagle-import") (part "PNP-TRANSISTOR_SOT89"))
    )
    (comp (ref "Q31")
      (value "BA.")
      (footprint "eagle-import:SOT89")
      (libsource (lib "eagle-import") (part "PNP-TRANSISTOR_SOT89"))
    )
    (comp (ref "Q32")
      (value "BA")
      (footprint "eagle-import:SOT89")
      (libsource (lib "eagle-import") (part "PNP-TRANSISTOR_SOT89"))
    )
    (comp (ref "Q33")
      (value "MY")
      (footprint "eagle-import:SOT89")
      (libsource (lib "eagle-import") (part "NPN-TRANSISTOR_SOT89"))
    )
    (comp (ref "Q34")
      (value "J1")
      (footprint "eagle-import:SOT-23")
      (fields (field (name "MPN") "BSS138W-7-F"))
      (libsource (lib "eagle-import") (part "SMD-MOSFET-N-CH-50V-200MA-BSS138W-7-F(SOT-23)"))
    )
    (comp (ref "Q35")
      (value "J1")
      (footprint "eagle-import:SOT-23")
      (fields (field (name "MPN") "BSS138W-7-F"))
      (libsource (lib "eagle-import") (part "SMD-MOSFET-N-CH-50V-200MA-BSS138W-7-F(SOT-23)"))
    )
    (comp (ref "R271")
      (value "47")
      (footprint "eagle-import:V235_17_1MM")
      (libsource (lib "eagle-import") (part "R-EU_V235/17_1MM"))
    )
    (comp (ref "R272")
      (value "13")
      (footprint "eagle-import:R1206")
      (fields (field (name "MPN") "RC1206JR-0713RL"))
      (libsource (lib "eagle-import") (part "SMD-RES-13R-5%-1/4W(1206)"))
    )
    (comp (ref "R273")
      (value "47")
      (footprint "eagle-import:V235_17_1MM")
      (libsource (lib "eagle-import") (part "R-EU_V235/17_1MM"))
    )
    (comp (ref "R274")
      (value "104")
      (footprint "eagle-import:R0805")
      (fields (field (name "MPN") "RC0805FR-0710KL"))
      (libsource (lib "eagle-import") (part "SMD-RES-10K-1%-1/8W(0805)"))
    )
    (comp (ref "R275")
      (value "104")
      (footprint "eagle-import:R0805")
      (fields (field (name "MPN") "RC0805FR-0710KL"))
      (libsource (lib "eagle-import") (part "SMD-RES-10K-1%-1/8W(0805)"))
    )
    (comp (ref "R276")
      (value "104")
      (footprint "eagle-import:R0805")
      (fields (field (name "MPN") "RC0805FR-0710KL"))
      (libsource (lib "eagle-import") (part "SMD-RES-10K-1%-1/8W(0805)"))
    )
    (comp (ref "R277")
      (value "4701")
      (footprint "eagle-import:R0805")
      (fields (field (name "MPN") "RC0805JR-074K7L"))
      (libsource (lib "eagle-import") (part "SMD-RES-4.7K-5%-1/8W(0805)"))
    )
    (comp (ref "R278")
      (value "1002")
      (footprint "eagle-import:R0805")
      (fields (field (name "MPN") "RC0805FR-0710KL"))
      (libsource (lib "eagle-import") (part "SMD-RES-10K-1%-1/8W(0805)"))
    )
    (comp (ref "R279")
      (value "1002")
      (footprint "eagle-import:R0805")
      (fields (field (name "MPN") "RC0805FR-0710KL"))
      (libsource (lib "eagle-import") (part "SMD-RES-10K-1%-1/8W(0805)"))
    )
    (comp (ref "R280")
      (value "1502")
      (footprint "eagle-import:R0805")
      (fields (field (name "MPN") "RC0805FR-0710KL"))
      (libsource (lib "eagle-import") (part "SMD-RES-10K-1%-1/8W(0805)"))
    )
    (comp (ref "R281")
      (value "104")
      (footprint "eagle-import:R0805")
      (fields (field (name "MPN") "RC0805FR-0710KL"))
      (libsource (lib "eagle-import") (part "SMD-RES-10K-1%-1/8W(0805)"))
    )
    (comp (ref "R282")
      (value "104")
      (footprint "eagle-import:R0805")
      (fields (field (name "MPN") "RC0805FR-0710KL"))
      (libsource (lib "eagle-import") (part "SMD-RES-10K-1%-1/8W(0805)"))
    )
    (comp (ref "R283")
      (value "1502")
      (footprint "eagle-import:R0805")
      (fields (field (name "MPN") "RC0805FR-0710KL"))
      (libsource (lib "eagle-import") (part "SMD-RES-10K-1%-1/8W(0805)"))
    )
    (comp (ref "R284")
      (value "1002")
      (footprint "eagle-import:R0805")
      (fields (field (name "MPN") "RC0805FR-0710KL"))
      (libsource (lib "eagle-import") (part "SMD-RES-10K-1%-1/8W(0805)"))
    )
    (comp (ref "R285")
      (value "2201")
      (footprint "eagle-import:R0805")
      (fields (field (name "MPN") "RC0805JR-072K2L"))
      (libsource (lib "eagle-import") (part "SMD-RES-2.2K-5%-1/8W(0805)"))
    )
    (comp (ref "R286")
      (value "1002")
      (footprint "eagle-import:R0805")
      (fields (field (name "MPN") "RC0805FR-0710KL"))
      (libsource (lib "eagle-import") (part "SMD-RES-10K-1%-1/8W(0805)"))
    )
    (comp (ref "R287")
      (value "4701")
      (footprint "eagle-import:R0805")
      (fields (field (name "MPN") "RC0805JR-074K7L"))
      (libsource (lib "eagle-import") (part "SMD-RES-4.7K-5%-1/8W(0805)"))
    )
    (comp (ref "R288")
      (value "2702")
      (footprint "eagle-import:R0805")
      (fields (field (name "MPN") "RC0805JR-074K7L"))
      (libsource (lib "eagle-import") (part "SMD-RES-4.7K-5%-1/8W(0805)"))
    )
    (comp (ref "R289")
      (value "102")
      (footprint "eagle-import:R0805")
      (fields (field (name "MPN") "RC0805JR-071KL"))
      (libsource (lib "eagle-import") (part "SMD-RES-1K-5%-1/8W(0805)"))
    )
    (comp (ref "R290")
      (value "100")
      (footprint "eagle-import:R0805")
      (fields (field (name "MPN") "RC0805JR-07220RL"))
      (libsource (lib "eagle-import") (part "SMD-RES-220R-5%-1/8W(0805)"))
    )
    (comp (ref "R291")
      (value "(101)")
      (footprint "eagle-import:R0805")
      (fields (field (name "MPN") "RC0805JR-07100RL"))
      (libsource (lib "eagle-import") (part "SMD-RES-100R-5%-1/8W(0805)"))
    )
    (comp (ref "R292")
      (value "(1000)")
      (footprint "eagle-import:R0805")
      (fields (field (name "MPN") "RC0805JR-07100RL"))
      (libsource (lib "eagle-import") (part "SMD-RES-100R-5%-1/8W(0805)"))
    )
    (comp (ref "R293")
      (value "102")
      (footprint "eagle-import:R0805")
      (fields (field (name "MPN") "RC0805JR-071KL"))
      (libsource (lib "eagle-import") (part "SMD-RES-1K-5%-1/8W(0805)"))
    )
    (comp (ref "R294")
      (value "13")
      (footprint "eagle-import:R1206")
      (fields (field (name "MPN") "RC1206JR-0713RL"))
      (libsource (lib "eagle-import") (part "SMD-RES-13R-5%-1/4W(1206)"))
    )
    (comp (ref "R295")
      (value "13")
      (footprint "eagle-import:R1206")
      (fields (field (name "MPN") "RC1206JR-0713RL"))
      (libsource (lib "eagle-import") (part "SMD-RES-13R-5%-1/4W(1206)"))
    )
    (comp (ref "R296")
      (value "2702")
      (footprint "eagle-import:R0805")
      (fields (field (name "MPN") "RC0805JR-074K7L"))
      (libsource (lib "eagle-import") (part "SMD-RES-4.7K-5%-1/8W(0805)"))
    )
    (comp (ref "R297")
      (value "4701")
      (footprint "eagle-import:R0805")
      (fields (field (name "MPN") "RC0805JR-074K7L"))
      (libsource (lib "eagle-import") (part "SMD-RES-4.7K-5%-1/8W(0805)"))
    )
    (comp (ref "R298")
      (value "100")
      (footprint "eagle-import:R0805")
      (fields (field (name "MPN") "RC0805JR-072K2L"))
      (libsource (lib "eagle-import") (part "SMD-RES-2.2K-5%-1/8W(0805)"))
    )
    (comp (ref "R299")
      (value "(101)")
      (footprint "eagle-import:R0805")
      (fields (field (name "MPN") "RC0805JR-072K2L"))
      (libsource (lib "eagle-import") (part "SMD-RES-2.2K-5%-1/8W(0805)"))
    )
    (comp (ref "R300")
      (value "104")
      (footprint "eagle-import:R0805")
      (fields (field (name "MPN") "RC0805FR-0710KL"))
      (libsource (lib "eagle-import") (part "SMD-RES-10K-1%-1/8W(0805)"))
    )
    (comp (ref "R304")
      (value "104")
      (footprint "eagle-import:R0805")
      (fields (field (name "MPN") "RC0805FR-0710KL"))
      (libsource (lib "eagle-import") (part "SMD-RES-10K-1%-1/8W(0805)"))
    )
    (comp (ref "R347")
      (value "(1002)")
      (footprint "eagle-import:R0805")
      (fields (field (name "MPN") "RC0805FR-0710KL"))
      (libsource (lib "eagle-import") (part "SMD-RES-10K-1%-1/8W(0805)"))
    )
    (comp (ref "R348")
      (value "2702")
      (footprint "eagle-import:R0805")
      (fields (field (name "MPN") "RC0805FR-0710KL"))
      (libsource (lib "eagle-import") (part "SMD-RES-10K-1%-1/8W(0805)"))
    )
    (comp (ref "R349")
      (value "47")
      (footprint "eagle-import:V235_17_1MM")
      (libsource (lib "eagle-import") (part "R-EU_V235/17_1MM"))
    )
    (comp (ref "R350")
      (value "47")
      (footprint "eagle-import:V235_17_1MM")
      (libsource (lib "eagle-import") (part "R-EU_V235/17_1MM"))
    )
    (comp (ref "R351")
      (value "2702")
      (footprint "eagle-import:R0805")
      (fields (field (name "MPN") "RC0805JR-074K7L"))
      (libsource (lib "eagle-import") (part "SMD-RES-4.7K-5%-1/8W(0805)"))
    )
    (comp (ref "R352")
      (value "2201")
      (footprint "eagle-import:R0805")
      (fields (field (name "MPN") "RC0805JR-072K2L"))
      (libsource (lib "eagle-import") (part "SMD-RES-2.2K-5%-1/8W(0805)"))
    )
    (comp (ref "R353")
      (value "(1002)")
      (footprint "eagle-import:R0805")
      (fields (field (name "MPN") "RC0805JR-074K7L"))
      (libsource (lib "eagle-import") (part "SMD-RES-4.7K-5%-1/8W(0805)"))
    )
    (comp (ref "R354")
      (value "1002")
      (footprint "eagle-import:R0805")
      (fields (field (name "MPN") "RC0805FR-0710KL"))
      (libsource (lib "eagle-import") (part "SMD-RES-10K-1%-1/8W(0805)"))
    )
    (comp (ref "R355")
      (value "102")
      (footprint "eagle-import:R0805")
      (fields (field (name "MPN") "RC0805JR-071KL"))
      (libsource (lib "eagle-import") (part "SMD-RES-1K-5%-1/8W(0805)"))
    )
    (comp (ref "R356")
      (value "2702")
      (footprint "eagle-import:R0805")
      (fields (field (name "MPN") "RC0805JR-074K7L"))
      (libsource (lib "eagle-import") (part "SMD-RES-4.7K-5%-1/8W(0805)"))
    )
    (comp (ref "R357")
      (value "102")
      (footprint "eagle-import:R0805")
      (fields (field (name "MPN") "RC0805JR-071KL"))
      (libsource (lib "eagle-import") (part "SMD-RES-1K-5%-1/8W(0805)"))
    )
    (comp (ref "R358")
      (value "102")
      (footprint "eagle-import:R0805")
      (fields (field (name "MPN") "RC0805JR-071KL"))
      (libsource (lib "eagle-import") (part "SMD-RES-1K-5%-1/8W(0805)"))
    )
    (comp (ref "R359")
      (value "13")
      (footprint "eagle-import:R1206")
      (fields (field (name "MPN") "RC1206JR-0713RL"))
      (libsource (lib "eagle-import") (part "SMD-RES-13R-5%-1/4W(1206)"))
    )
    (comp (ref "R360")
      (value "R_user")
      (footprint "eagle-import:R0805")
      (libsource (lib "eagle-import") (part "R-EU_R0805"))
    )
    (comp (ref "SJ5") (value "SJ") (footprint "eagle-import:SJ") (libsource (lib "eagle-import") (part "SJ")))
    (comp (ref "START5")
      (value "TPSB2.0")
      (footprint "eagle-import:B2.0")
      (libsource (lib "eagle-import") (part "TPSB2.0"))
    )
    (comp (ref "TP231")
      (value "TPSB2.0")
      (footprint "eagle-import:B2.0")
      (libsource (lib "eagle-import") (part "TPSB2.0"))
    )
    (comp (ref "TP232")
      (value "TPSB2.0")
      (footprint "eagle-import:B2.0")
      (libsource (lib "eagle-import") (part "TPSB2.0"))
    )
    (comp (ref "TP233")
      (value "TPSB2.0")
      (footprint "eagle-import:B2.0")
      (libsource (lib "eagle-import") (part "TPSB2.0"))
    )
    (comp (ref "TP234")
      (value "TPSB2.0")
      (footprint "eagle-import:B2.0")
      (libsource (lib "eagle-import") (part "TPSB2.0"))
    )
    (comp (ref "TP235")
      (value "TPSB2.0")
      (footprint "eagle-import:B2.0")
      (libsource (lib "eagle-import") (part "TPSB2.0"))
    )
    (comp (ref "TP236")
      (value "TPSB2.0")
      (footprint "eagle-import:B2.0")
      (libsource (lib "eagle-import") (part "TPSB2.0"))
    )
    (comp (ref "TP237")
      (value "TPSB2.0")
      (footprint "eagle-import:B2.0")
      (libsource (lib "eagle-import") (part "TPSB2.0"))
    )
    (comp (ref "TP238")
      (value "TPSB2.0")
      (footprint "eagle-import:B2.0")
      (libsource (lib "eagle-import") (part "TPSB2.0"))
    )
    (comp (ref "TP239")
      (value "TPSB2.0")
      (footprint "eagle-import:B2.0")
      (libsource (lib "eagle-import") (part "TPSB2.0"))
    )
    (comp (ref "TP240")
      (value "TPSB2.0")
      (footprint "eagle-import:B2.0")
      (libsource (lib "eagle-import") (part "TPSB2.0"))
    )
    (comp (ref "TP241")
      (value "TPSB2.0")
      (footprint "eagle-import:B2.0")
      (libsource (lib "eagle-import") (part "TPSB2.0"))
    )
    (comp (ref "TP242")
      (value "TPSB2.0")
      (footprint "eagle-import:B2.0")
      (libsource (lib "eagle-import") (part "TPSB2.0"))
    )
    (comp (ref "TP243")
      (value "TPSB2.0")
      (footprint "eagle-import:B2.0")
      (libsource (lib "eagle-import") (part "TPSB2.0"))
    )
    (comp (ref "TP244")
      (value "TPSB2.0")
      (footprint "eagle-import:B2.0")
      (libsource (lib "eagle-import") (part "TPSB2.0"))
    )
    (comp (ref "TP245")
      (value "TPSB2.0")
      (footprint "eagle-import:B2.0")
      (libsource (lib "eagle-import") (part "TPSB2.0"))
    )
    (comp (ref "TP246")
      (value "TPSB2.0")
      (footprint "eagle-import:B2.0")
      (libsource (lib "eagle-import") (part "TPSB2.0"))
    )
    (comp (ref "TP247")
      (value "TPSB2.0")
      (footprint "eagle-import:B2.0")
      (libsource (lib "eagle-import") (part "TPSB2.0"))
    )
    (comp (ref "TP248")
      (value "TPSB2.0")
      (footprint "eagle-import:B2.0")
      (libsource (lib "eagle-import") (part "TPSB2.0"))
    )
    (comp (ref "TP249")
      (value "TPSB1,27")
      (footprint "eagle-import:B1,27")
      (libsource (lib "eagle-import") (part "TPSB1,27"))
    )
    (comp (ref "TP250")
      (value "TPSB2.0")
      (footprint "eagle-import:B2.0")
      (libsource (lib "eagle-import") (part "TPSB2.0"))
    )
    (comp (ref "TP251")
      (value "TPSB2.0")
      (footprint "eagle-import:B2.0")
      (libsource (lib "eagle-import") (part "TPSB2.0"))
    )
    (comp (ref "TP252")
      (value "TPSB2.0")
      (footprint "eagle-import:B2.0")
      (libsource (lib "eagle-import") (part "TPSB2.0"))
    )
    (comp (ref "TP253")
      (value "TPSB2.0")
      (footprint "eagle-import:B2.0")
      (libsource (lib "eagle-import") (part "TPSB2.0"))
    )
    (comp (ref "X13")
      (value "CON_BMWV2")
      (footprint "eagle-import:24-PIN_V2")
      (libsource (lib "eagle-import") (part "CON_BMWV2"))
    )
    (comp (ref "X14")
      (value "22-23-2051")
      (footprint "eagle-import:22-23-2051")
      (fields (field (name "MF") "MOLEX"))
      (libsource (lib "eagle-import") (part "22-23-2051"))
    )
    (comp (ref "X15")
      (value "22-23-2021")
      (footprint "eagle-import:22-23-2021")
      (fields (field (name "MF") "MOLEX"))
      (libsource (lib "eagle-import") (part "22-23-2021"))
    )
    (comp (ref "6V3")
      (value "TPSB2.0")
      (footprint "eagle-import:B2.0")
      (libsource (lib "eagle-import") (part "TPSB2.0"))
    )
    (comp (ref "10V3")
      (value "TPSB2.0")
      (footprint "eagle-import:B2.0")
      (libsource (lib "eagle-import") (part "TPSB2.0"))
    )
    (comp (ref "11")
      (value "2081-1132")
      (footprint "eagle-import:12-PIN")
      (libsource (lib "eagle-import") (part "2081-1132"))
    )
    (comp (ref "12")
      (value "2081-1132")
      (footprint "eagle-import:12-PIN")
      (libsource (lib "eagle-import") (part "2081-1132"))
    )
    (comp (ref "C21")
      (value "100u")
      (footprint "eagle-import:C1206")
      (fields (field (name "MPN") "GRM31CR60J107ME39L"))
      (libsource (lib "eagle-import") (part "CERAMIC-100UF-6.3V-20%-X5R(1206)"))
    )
    (comp (ref "C22")
      (value "100u")
      (footprint "eagle-import:C1206")
      (fields (field (name "MPN") "GRM31CR60J107ME39L"))
      (libsource (lib "eagle-import") (part "CERAMIC-100UF-6.3V-20%-X5R(1206)"))
    )
    (comp (ref "C23")
      (value "100nF,")
      (footprint "eagle-import:C0805")
      (fields (field (name "MPN") "CC0805KRX7R9BB104"))
      (libsource (lib "eagle-import") (part "CERAMIC-100NF-50V-10%-X7R(0805)"))
    )
    (comp (ref "C24")
      (value "4.7u")
      (footprint "eagle-import:C0805")
      (fields (field (name "MPN") "CC0805KKX5R8BB475"))
      (libsource (lib "eagle-import") (part "CERAMIC-4.7UF-25V-10%-X5R(0805)"))
    )
    (comp (ref "C25")
      (value "100nF.")
      (footprint "eagle-import:C0805")
      (fields (field (name "MPN") "CC0805KRX7R9BB104"))
      (libsource (lib "eagle-import") (part "CERAMIC-100NF-50V-10%-X7R(0805)"))
    )
    (comp (ref "C26")
      (value "100nF.")
      (footprint "eagle-import:C0805")
      (fields (field (name "MPN") "CC0805KRX7R9BB104"))
      (libsource (lib "eagle-import") (part "CERAMIC-100NF-50V-10%-X7R(0805)"))
    )
    (comp (ref "C27")
      (value "2.2nF")
      (footprint "eagle-import:C0805")
      (fields (field (name "MPN") "CC0805KRX7R9BB104"))
      (libsource (lib "eagle-import") (part "CERAMIC-100NF-50V-10%-X7R(0805)"))
    )
    (comp (ref "C28")
      (value "100nF")
      (footprint "eagle-import:C0805")
      (fields (field (name "MPN") "CC0805KRX7R9BB104"))
      (libsource (lib "eagle-import") (part "CERAMIC-100NF-50V-10%-X7R(0805)"))
    )
    (comp (ref "C29")
      (value "100nF")
      (footprint "eagle-import:C0805")
      (fields (field (name "MPN") "CC0805KRX7R9BB104"))
      (libsource (lib "eagle-import") (part "CERAMIC-100NF-50V-10%-X7R(0805)"))
    )
    (comp (ref "C30")
      (value "100nF,")
      (footprint "eagle-import:C0805")
      (fields (field (name "MPN") "CC0805KRX7R9BB104"))
      (libsource (lib "eagle-import") (part "CERAMIC-100NF-50V-10%-X7R(0805)"))
    )
    (comp (ref "D23")
      (value "1N4007")
      (footprint "eagle-import:DO-214AC")
      (libsource (lib "eagle-import") (part "DIODE-GEN-PURPOSE-1KV-1A(DO-214AC)"))
    )
    (comp (ref "D24")
      (value "1N4007,")
      (footprint "eagle-import:DO-214AC")
      (fields (field (name "MPN") "1N4007"))
      (libsource (lib "eagle-import") (part "DIODE-GEN-PURPOSE-1KV-1A(DO-214AC)"))
    )
    (comp (ref "D25")
      (value "1N4007,")
      (footprint "eagle-import:DO-214AC")
      (fields (field (name "MPN") "1N4007"))
      (libsource (lib "eagle-import") (part "DIODE-GEN-PURPOSE-1KV-1A(DO-214AC)"))
    )
    (comp (ref "D26")
      (value "1N4007.")
      (footprint "eagle-import:DO-214AC")
      (fields (field (name "MPN") "1N4007"))
      (libsource (lib "eagle-import") (part "DIODE-GEN-PURPOSE-1KV-1A(DO-214AC)"))
    )
    (comp (ref "D27")
      (value "1N5817")
      (footprint "eagle-import:DO-214AC_SLIM")
      (libsource (lib "eagle-import") (part "DIODE-GEN-PURPOSE-1KV-1A(DO-214AC)DO-214AC/1206"))
    )
    (comp (ref "D28")
      (value "1N5817.")
      (footprint "eagle-import:DO-214AC_SLIM")
      (libsource (lib "eagle-import") (part "DIODE-GEN-PURPOSE-1KV-1A(DO-214AC)DO-214AC/1206"))
    )
    (comp (ref "D29")
      (value "1N5817.")
      (footprint "eagle-import:DO-214AC_SLIM")
      (libsource (lib "eagle-import") (part "DIODE-GEN-PURPOSE-1KV-1A(DO-214AC)DO-214AC/1206"))
    )
    (comp (ref "D30")
      (value "1N5817")
      (footprint "eagle-import:DO-214AC_SLIM")
      (libsource (lib "eagle-import") (part "DIODE-GEN-PURPOSE-1KV-1A(DO-214AC)DO-214AC/1206"))
    )
    (comp (ref "D31")
      (value "1N4007.")
      (footprint "eagle-import:DO-214AC")
      (fields (field (name "MPN") "1N4007"))
      (libsource (lib "eagle-import") (part "DIODE-GEN-PURPOSE-1KV-1A(DO-214AC)"))
    )
    (comp (ref "D32")
      (value "1N4007")
      (footprint "eagle-import:DO-214AC")
      (libsource (lib "eagle-import") (part "DIODE-GEN-PURPOSE-1KV-1A(DO-214AC)"))
    )
    (comp (ref "D33")
      (value "SM6T")
      (footprint "eagle-import:DO214AA")
      (libsource (lib "eagle-import") (part "SM6T"))
    )
    (comp (ref "FID11")
      (value "FIDUCIAL")
      (footprint "eagle-import:FIDUCIAL_1MM")
      (libsource (lib "eagle-import") (part "FIDUCIAL"))
    )
    (comp (ref "FID12")
      (value "FIDUCIAL")
      (footprint "eagle-import:FIDUCIAL_1MM")
      (libsource (lib "eagle-import") (part "FIDUCIAL"))
    )
    (comp (ref "FID13")
      (value "FIDUCIAL")
      (footprint "eagle-import:FIDUCIAL_1MM")
      (libsource (lib "eagle-import") (part "FIDUCIAL"))
    )
    (comp (ref "FID14")
      (value "FIDUCIAL")
      (footprint "eagle-import:FIDUCIAL_1MM")
      (libsource (lib "eagle-import") (part "FIDUCIAL"))
    )
    (comp (ref "IC21")
      (value "4028")
      (footprint "eagle-import:SO16")
      (libsource (lib "eagle-import") (part "4028D"))
    )
    (comp (ref "IC22")
      (value "6V pos")
      (footprint "eagle-import:78LXX")
      (libsource (lib "eagle-import") (part "v-reg_78LXX"))
    )
    (comp (ref "IC23")
      (value "317TO202H_NOHOLE")
      (footprint "eagle-import:TO220H_NOHOLE")
      (libsource (lib "eagle-import") (part "317TO202H_NOHOLE"))
    )
    (comp (ref "IC24")
      (value "ULN2004")
      (footprint "eagle-import:SO16")
      (libsource (lib "eagle-import") (part "ULN2004AD"))
    )
    (comp (ref "IC25")
      (value "LM339")
      (footprint "eagle-import:SO14")
      (libsource (lib "eagle-import") (part "LM339D"))
    )
    (comp (ref "IC26")
      (value "78L06")
      (footprint "eagle-import:SOT89_ROUND")
      (libsource (lib "eagle-import") (part "78LXXSOT89_ROUND"))
    )
    (comp (ref "IC27")
      (value "555")
      (footprint "eagle-import:SO08")
      (libsource (lib "eagle-import") (part "555DNE"))
    )
    (comp (ref "IC28")
      (value "4538")
      (footprint "eagle-import:SO16")
      (libsource (lib "eagle-import") (part "4538D"))
    )
    (comp (ref "IC29")
      (value "78L10")
      (footprint "eagle-import:SOT89_ROUND")
      (libsource (lib "eagle-import") (part "78LXXSOT89_ROUND"))
    )
    (comp (ref "IC30")
      (value "LM2904")
      (footprint "eagle-import:SO08")
      (libsource (lib "eagle-import") (part "LM358D"))
    )
    (comp (ref "JP11")
      (value "JP2EJP2_SMALLPADS")
      (footprint "eagle-import:JP2_SMALLPADS")
      (libsource (lib "eagle-import") (part "JP2EJP2_SMALLPADS"))
    )
    (comp (ref "JP12")
      (value "JP2E_ORIG")
      (footprint "eagle-import:JP2_ORIG_SMALLPADS")
      (libsource (lib "eagle-import") (part "JP2E_ORIG"))
    )
    (comp (ref "JP13")
      (value "JP2EJP2_SMALLPADS")
      (footprint "eagle-import:JP2_SMALLPADS")
      (libsource (lib "eagle-import") (part "JP2EJP2_SMALLPADS"))
    )
    (comp (ref "JP14")
      (value "JP2EJP2_SMALLPADS")
      (footprint "eagle-import:JP2_SMALLPADS")
      (libsource (lib "eagle-import") (part "JP2EJP2_SMALLPADS"))
    )
    (comp (ref "JP15")
      (value "JP2EJP2_SMALLPADS")
      (footprint "eagle-import:JP2_SMALLPADS")
      (libsource (lib "eagle-import") (part "JP2EJP2_SMALLPADS"))
    )
    (comp (ref "LED13")
      (value "LEDLD260")
      (footprint "eagle-import:LD260")
      (libsource (lib "eagle-import") (part "LEDLD260"))
    )
    (comp (ref "LED14")
      (value "LEDLD260")
      (footprint "eagle-import:LD260")
      (libsource (lib "eagle-import") (part "LEDLD260"))
    )
    (comp (ref "LED15")
      (value "LEDLD260")
      (footprint "eagle-import:LD260")
      (libsource (lib "eagle-import") (part "LEDLD260"))
    )
    (comp (ref "LED16")
      (value "LEDLD260")
      (footprint "eagle-import:LD260")
      (libsource (lib "eagle-import") (part "LEDLD260"))
    )
    (comp (ref "LED17")
      (value "LEDLD260")
      (footprint "eagle-import:LD260")
      (libsource (lib "eagle-import") (part "LEDLD260"))
    )
    (comp (ref "LED18")
      (value "LEDLD260")
      (footprint "eagle-import:LD260")
      (libsource (lib "eagle-import") (part "LEDLD260"))
    )
    (comp (ref "Q15")
      (value "BA")
      (footprint "eagle-import:SOT89")
      (libsource (lib "eagle-import") (part "PNP-TRANSISTOR_SOT89"))
    )
    (comp (ref "Q16")
      (value "BA.")
      (footprint "eagle-import:SOT89")
      (libsource (lib "eagle-import") (part "PNP-TRANSISTOR_SOT89"))
    )
    (comp (ref "Q17")
      (value "BA.")
      (footprint "eagle-import:SOT89")
      (libsource (lib "eagle-import") (part "PNP-TRANSISTOR_SOT89"))
    )
    (comp (ref "Q18")
      (value "BA")
      (footprint "eagle-import:SOT89")
      (libsource (lib "eagle-import") (part "PNP-TRANSISTOR_SOT89"))
    )
    (comp (ref "Q19")
      (value "MY")
      (footprint "eagle-import:SOT89")
      (libsource (lib "eagle-import") (part "NPN-TRANSISTOR_SOT89"))
    )
    (comp (ref "Q20")
      (value "J1")
      (footprint "eagle-import:SOT-23")
      (fields (field (name "MPN") "BSS138W-7-F"))
      (libsource (lib "eagle-import") (part "SMD-MOSFET-N-CH-50V-200MA-BSS138W-7-F(SOT-23)"))
    )
    (comp (ref "Q21")
      (value "J1")
      (footprint "eagle-import:SOT-23")
      (fields (field (name "MPN") "BSS138W-7-F"))
      (libsource (lib "eagle-import") (part "SMD-MOSFET-N-CH-50V-200MA-BSS138W-7-F(SOT-23)"))
    )
    (comp (ref "R91")
      (value "47")
      (footprint "eagle-import:V235_17_1MM")
      (libsource (lib "eagle-import") (part "R-EU_V235/17_1MM"))
    )
    (comp (ref "R92")
      (value "13")
      (footprint "eagle-import:R1206")
      (fields (field (name "MPN") "RC1206JR-0713RL"))
      (libsource (lib "eagle-import") (part "SMD-RES-13R-5%-1/4W(1206)"))
    )
    (comp (ref "R93")
      (value "47")
      (footprint "eagle-import:V235_17_1MM")
      (libsource (lib "eagle-import") (part "R-EU_V235/17_1MM"))
    )
    (comp (ref "R94")
      (value "104")
      (footprint "eagle-import:R0805")
      (fields (field (name "MPN") "RC0805FR-0710KL"))
      (libsource (lib "eagle-import") (part "SMD-RES-10K-1%-1/8W(0805)"))
    )
    (comp (ref "R95")
      (value "104")
      (footprint "eagle-import:R0805")
      (fields (field (name "MPN") "RC0805FR-0710KL"))
      (libsource (lib "eagle-import") (part "SMD-RES-10K-1%-1/8W(0805)"))
    )
    (comp (ref "R96")
      (value "104")
      (footprint "eagle-import:R0805")
      (fields (field (name "MPN") "RC0805FR-0710KL"))
      (libsource (lib "eagle-import") (part "SMD-RES-10K-1%-1/8W(0805)"))
    )
    (comp (ref "R97")
      (value "4701")
      (footprint "eagle-import:R0805")
      (fields (field (name "MPN") "RC0805JR-074K7L"))
      (libsource (lib "eagle-import") (part "SMD-RES-4.7K-5%-1/8W(0805)"))
    )
    (comp (ref "R98")
      (value "1002")
      (footprint "eagle-import:R0805")
      (fields (field (name "MPN") "RC0805FR-0710KL"))
      (libsource (lib "eagle-import") (part "SMD-RES-10K-1%-1/8W(0805)"))
    )
    (comp (ref "R99")
      (value "1002")
      (footprint "eagle-import:R0805")
      (fields (field (name "MPN") "RC0805FR-0710KL"))
      (libsource (lib "eagle-import") (part "SMD-RES-10K-1%-1/8W(0805)"))
    )
    (comp (ref "R100")
      (value "1502")
      (footprint "eagle-import:R0805")
      (fields (field (name "MPN") "RC0805FR-0710KL"))
      (libsource (lib "eagle-import") (part "SMD-RES-10K-1%-1/8W(0805)"))
    )
    (comp (ref "R104")
      (value "104")
      (footprint "eagle-import:R0805")
      (fields (field (name "MPN") "RC0805FR-0710KL"))
      (libsource (lib "eagle-import") (part "SMD-RES-10K-1%-1/8W(0805)"))
    )
    (comp (ref "R147")
      (value "104")
      (footprint "eagle-import:R0805")
      (fields (field (name "MPN") "RC0805FR-0710KL"))
      (libsource (lib "eagle-import") (part "SMD-RES-10K-1%-1/8W(0805)"))
    )
    (comp (ref "R148")
      (value "1502")
      (footprint "eagle-import:R0805")
      (fields (field (name "MPN") "RC0805FR-0710KL"))
      (libsource (lib "eagle-import") (part "SMD-RES-10K-1%-1/8W(0805)"))
    )
    (comp (ref "R149")
      (value "1002")
      (footprint "eagle-import:R0805")
      (fields (field (name "MPN") "RC0805FR-0710KL"))
      (libsource (lib "eagle-import") (part "SMD-RES-10K-1%-1/8W(0805)"))
    )
    (comp (ref "R150")
      (value "2201")
      (footprint "eagle-import:R0805")
      (fields (field (name "MPN") "RC0805JR-072K2L"))
      (libsource (lib "eagle-import") (part "SMD-RES-2.2K-5%-1/8W(0805)"))
    )
    (comp (ref "R151")
      (value "1002")
      (footprint "eagle-import:R0805")
      (fields (field (name "MPN") "RC0805FR-0710KL"))
      (libsource (lib "eagle-import") (part "SMD-RES-10K-1%-1/8W(0805)"))
    )
    (comp (ref "R152")
      (value "4701")
      (footprint "eagle-import:R0805")
      (fields (field (name "MPN") "RC0805JR-074K7L"))
      (libsource (lib "eagle-import") (part "SMD-RES-4.7K-5%-1/8W(0805)"))
    )
    (comp (ref "R153")
      (value "2702")
      (footprint "eagle-import:R0805")
      (fields (field (name "MPN") "RC0805JR-074K7L"))
      (libsource (lib "eagle-import") (part "SMD-RES-4.7K-5%-1/8W(0805)"))
    )
    (comp (ref "R154")
      (value "102")
      (footprint "eagle-import:R0805")
      (fields (field (name "MPN") "RC0805JR-071KL"))
      (libsource (lib "eagle-import") (part "SMD-RES-1K-5%-1/8W(0805)"))
    )
    (comp (ref "R155")
      (value "100")
      (footprint "eagle-import:R0805")
      (fields (field (name "MPN") "RC0805JR-07220RL"))
      (libsource (lib "eagle-import") (part "SMD-RES-220R-5%-1/8W(0805)"))
    )
    (comp (ref "R156")
      (value "(101)")
      (footprint "eagle-import:R0805")
      (fields (field (name "MPN") "RC0805JR-07100RL"))
      (libsource (lib "eagle-import") (part "SMD-RES-100R-5%-1/8W(0805)"))
    )
    (comp (ref "R157")
      (value "(1000)")
      (footprint "eagle-import:R0805")
      (fields (field (name "MPN") "RC0805JR-07100RL"))
      (libsource (lib "eagle-import") (part "SMD-RES-100R-5%-1/8W(0805)"))
    )
    (comp (ref "R158")
      (value "102")
      (footprint "eagle-import:R0805")
      (fields (field (name "MPN") "RC0805JR-071KL"))
      (libsource (lib "eagle-import") (part "SMD-RES-1K-5%-1/8W(0805)"))
    )
    (comp (ref "R159")
      (value "13")
      (footprint "eagle-import:R1206")
      (fields (field (name "MPN") "RC1206JR-0713RL"))
      (libsource (lib "eagle-import") (part "SMD-RES-13R-5%-1/4W(1206)"))
    )
    (comp (ref "R160")
      (value "13")
      (footprint "eagle-import:R1206")
      (fields (field (name "MPN") "RC1206JR-0713RL"))
      (libsource (lib "eagle-import") (part "SMD-RES-13R-5%-1/4W(1206)"))
    )
    (comp (ref "R161")
      (value "2702")
      (footprint "eagle-import:R0805")
      (fields (field (name "MPN") "RC0805JR-074K7L"))
      (libsource (lib "eagle-import") (part "SMD-RES-4.7K-5%-1/8W(0805)"))
    )
    (comp (ref "R162")
      (value "4701")
      (footprint "eagle-import:R0805")
      (fields (field (name "MPN") "RC0805JR-074K7L"))
      (libsource (lib "eagle-import") (part "SMD-RES-4.7K-5%-1/8W(0805)"))
    )
    (comp (ref "R163")
      (value "100")
      (footprint "eagle-import:R0805")
      (fields (field (name "MPN") "RC0805JR-072K2L"))
      (libsource (lib "eagle-import") (part "SMD-RES-2.2K-5%-1/8W(0805)"))
    )
    (comp (ref "R164")
      (value "(101)")
      (footprint "eagle-import:R0805")
      (fields (field (name "MPN") "RC0805JR-072K2L"))
      (libsource (lib "eagle-import") (part "SMD-RES-2.2K-5%-1/8W(0805)"))
    )
    (comp (ref "R165")
      (value "104")
      (footprint "eagle-import:R0805")
      (fields (field (name "MPN") "RC0805FR-0710KL"))
      (libsource (lib "eagle-import") (part "SMD-RES-10K-1%-1/8W(0805)"))
    )
    (comp (ref "R166")
      (value "104")
      (footprint "eagle-import:R0805")
      (fields (field (name "MPN") "RC0805FR-0710KL"))
      (libsource (lib "eagle-import") (part "SMD-RES-10K-1%-1/8W(0805)"))
    )
    (comp (ref "R167")
      (value "(1002)")
      (footprint "eagle-import:R0805")
      (fields (field (name "MPN") "RC0805FR-0710KL"))
      (libsource (lib "eagle-import") (part "SMD-RES-10K-1%-1/8W(0805)"))
    )
    (comp (ref "R168")
      (value "2702")
      (footprint "eagle-import:R0805")
      (fields (field (name "MPN") "RC0805FR-0710KL"))
      (libsource (lib "eagle-import") (part "SMD-RES-10K-1%-1/8W(0805)"))
    )
    (comp (ref "R169")
      (value "47")
      (footprint "eagle-import:V235_17_1MM")
      (libsource (lib "eagle-import") (part "R-EU_V235/17_1MM"))
    )
    (comp (ref "R170")
      (value "47")
      (footprint "eagle-import:V235_17_1MM")
      (libsource (lib "eagle-import") (part "R-EU_V235/17_1MM"))
    )
    (comp (ref "R171")
      (value "2702")
      (footprint "eagle-import:R0805")
      (fields (field (name "MPN") "RC0805JR-074K7L"))
      (libsource (lib "eagle-import") (part "SMD-RES-4.7K-5%-1/8W(0805)"))
    )
    (comp (ref "R172")
      (value "2201")
      (footprint "eagle-import:R0805")
      (fields (field (name "MPN") "RC0805JR-072K2L"))
      (libsource (lib "eagle-import") (part "SMD-RES-2.2K-5%-1/8W(0805)"))
    )
    (comp (ref "R173")
      (value "(1002)")
      (footprint "eagle-import:R0805")
      (fields (field (name "MPN") "RC0805JR-074K7L"))
      (libsource (lib "eagle-import") (part "SMD-RES-4.7K-5%-1/8W(0805)"))
    )
    (comp (ref "R174")
      (value "1002")
      (footprint "eagle-import:R0805")
      (fields (field (name "MPN") "RC0805FR-0710KL"))
      (libsource (lib "eagle-import") (part "SMD-RES-10K-1%-1/8W(0805)"))
    )
    (comp (ref "R175")
      (value "102")
      (footprint "eagle-import:R0805")
      (fields (field (name "MPN") "RC0805JR-071KL"))
      (libsource (lib "eagle-import") (part "SMD-RES-1K-5%-1/8W(0805)"))
    )
    (comp (ref "R176")
      (value "2702")
      (footprint "eagle-import:R0805")
      (fields (field (name "MPN") "RC0805JR-074K7L"))
      (libsource (lib "eagle-import") (part "SMD-RES-4.7K-5%-1/8W(0805)"))
    )
    (comp (ref "R177")
      (value "102")
      (footprint "eagle-import:R0805")
      (fields (field (name "MPN") "RC0805JR-071KL"))
      (libsource (lib "eagle-import") (part "SMD-RES-1K-5%-1/8W(0805)"))
    )
    (comp (ref "R178")
      (value "102")
      (footprint "eagle-import:R0805")
      (fields (field (name "MPN") "RC0805JR-071KL"))
      (libsource (lib "eagle-import") (part "SMD-RES-1K-5%-1/8W(0805)"))
    )
    (comp (ref "R179")
      (value "13")
      (footprint "eagle-import:R1206")
      (fields (field (name "MPN") "RC1206JR-0713RL"))
      (libsource (lib "eagle-import") (part "SMD-RES-13R-5%-1/4W(1206)"))
    )
    (comp (ref "R180")
      (value "R_user")
      (footprint "eagle-import:R0805")
      (libsource (lib "eagle-import") (part "R-EU_R0805"))
    )
    (comp (ref "SJ3") (value "SJ") (footprint "eagle-import:SJ") (libsource (lib "eagle-import") (part "SJ")))
    (comp (ref "START3")
      (value "TPSB2.0")
      (footprint "eagle-import:B2.0")
      (libsource (lib "eagle-import") (part "TPSB2.0"))
    )
    (comp (ref "TP116")
      (value "TPSB2.0")
      (footprint "eagle-import:B2.0")
      (libsource (lib "eagle-import") (part "TPSB2.0"))
    )
    (comp (ref "TP117")
      (value "TPSB2.0")
      (footprint "eagle-import:B2.0")
      (libsource (lib "eagle-import") (part "TPSB2.0"))
    )
    (comp (ref "TP118")
      (value "TPSB2.0")
      (footprint "eagle-import:B2.0")
      (libsource (lib "eagle-import") (part "TPSB2.0"))
    )
    (comp (ref "TP119")
      (value "TPSB2.0")
      (footprint "eagle-import:B2.0")
      (libsource (lib "eagle-import") (part "TPSB2.0"))
    )
    (comp (ref "TP120")
      (value "TPSB2.0")
      (footprint "eagle-import:B2.0")
      (libsource (lib "eagle-import") (part "TPSB2.0"))
    )
    (comp (ref "TP121")
      (value "TPSB2.0")
      (footprint "eagle-import:B2.0")
      (libsource (lib "eagle-import") (part "TPSB2.0"))
    )
    (comp (ref "TP122")
      (value "TPSB2.0")
      (footprint "eagle-import:B2.0")
      (libsource (lib "eagle-import") (part "TPSB2.0"))
    )
    (comp (ref "TP123")
      (value "TPSB2.0")
      (footprint "eagle-import:B2.0")
      (libsource (lib "eagle-import") (part "TPSB2.0"))
    )
    (comp (ref "TP124")
      (value "TPSB2.0")
      (footprint "eagle-import:B2.0")
      (libsource (lib "eagle-import") (part "TPSB2.0"))
    )
    (comp (ref "TP125")
      (value "TPSB2.0")
      (footprint "eagle-import:B2.0")
      (libsource (lib "eagle-import") (part "TPSB2.0"))
    )
    (comp (ref "TP126")
      (value "TPSB2.0")
      (footprint "eagle-import:B2.0")
      (libsource (lib "eagle-import") (part "TPSB2.0"))
    )
    (comp (ref "TP127")
      (value "TPSB2.0")
      (footprint "eagle-import:B2.0")
      (libsource (lib "eagle-import") (part "TPSB2.0"))
    )
    (comp (ref "TP128")
      (value "TPSB2.0")
      (footprint "eagle-import:B2.0")
      (libsource (lib "eagle-import") (part "TPSB2.0"))
    )
    (comp (ref "TP129")
      (value "TPSB2.0")
      (footprint "eagle-import:B2.0")
      (libsource (lib "eagle-import") (part "TPSB2.0"))
    )
    (comp (ref "TP130")
      (value "TPSB2.0")
      (footprint "eagle-import:B2.0")
      (libsource (lib "eagle-import") (part "TPSB2.0"))
    )
    (comp (ref "TP131")
      (value "TPSB2.0")
      (footprint "eagle-import:B2.0")
      (libsource (lib "eagle-import") (part "TPSB2.0"))
    )
    (comp (ref "TP132")
      (value "TPSB2.0")
      (footprint "eagle-import:B2.0")
      (libsource (lib "eagle-import") (part "TPSB2.0"))
    )
    (comp (ref "TP133")
      (value "TPSB2.0")
      (footprint "eagle-import:B2.0")
      (libsource (lib "eagle-import") (part "TPSB2.0"))
    )
    (comp (ref "TP134")
      (value "TPSB1,27")
      (footprint "eagle-import:B1,27")
      (libsource (lib "eagle-import") (part "TPSB1,27"))
    )
    (comp (ref "TP135")
      (value "TPSB2.0")
      (footprint "eagle-import:B2.0")
      (libsource (lib "eagle-import") (part "TPSB2.0"))
    )
    (comp (ref "TP136")
      (value "TPSB2.0")
      (footprint "eagle-import:B2.0")
      (libsource (lib "eagle-import") (part "TPSB2.0"))
    )
    (comp (ref "TP137")
      (value "TPSB2.0")
      (footprint "eagle-import:B2.0")
      (libsource (lib "eagle-import") (part "TPSB2.0"))
    )
    (comp (ref "TP138")
      (value "TPSB2.0")
      (footprint "eagle-import:B2.0")
      (libsource (lib "eagle-import") (part "TPSB2.0"))
    )
    (comp (ref "X7")
      (value "CON_BMWV2")
      (footprint "eagle-import:24-PIN_V2")
      (libsource (lib "eagle-import") (part "CON_BMWV2"))
    )
    (comp (ref "X8")
      (value "22-23-2051")
      (footprint "eagle-import:22-23-2051")
      (fields (field (name "MF") "MOLEX"))
      (libsource (lib "eagle-import") (part "22-23-2051"))
    )
    (comp (ref "X9")
      (value "22-23-2021")
      (footprint "eagle-import:22-23-2021")
      (fields (field (name "MF") "MOLEX"))
      (libsource (lib "eagle-import") (part "22-23-2021"))
    )
    (comp (ref "6V1")
      (value "TPSB2.0")
      (footprint "eagle-import:B2.0")
      (libsource (lib "eagle-import") (part "TPSB2.0"))
    )
    (comp (ref "7")
      (value "2081-1132")
      (footprint "eagle-import:12-PIN")
      (libsource (lib "eagle-import") (part "2081-1132"))
    )
    (comp (ref "8")
      (value "2081-1132")
      (footprint "eagle-import:12-PIN")
      (libsource (lib "eagle-import") (part "2081-1132"))
    )
    (comp (ref "10V1")
      (value "TPSB2.0")
      (footprint "eagle-import:B2.0")
      (libsource (lib "eagle-import") (part "TPSB2.0"))
    )
    (comp (ref "C1")
      (value "100u")
      (footprint "eagle-import:C1206")
      (fields (field (name "MPN") "GRM31CR60J107ME39L"))
      (libsource (lib "eagle-import") (part "CERAMIC-100UF-6.3V-20%-X5R(1206)"))
    )
    (comp (ref "C2")
      (value "100u")
      (footprint "eagle-import:C1206")
      (fields (field (name "MPN") "GRM31CR60J107ME39L"))
      (libsource (lib "eagle-import") (part "CERAMIC-100UF-6.3V-20%-X5R(1206)"))
    )
    (comp (ref "C3")
      (value "100nF,")
      (footprint "eagle-import:C0805")
      (fields (field (name "MPN") "CC0805KRX7R9BB104"))
      (libsource (lib "eagle-import") (part "CERAMIC-100NF-50V-10%-X7R(0805)"))
    )
    (comp (ref "C4")
      (value "4.7u")
      (footprint "eagle-import:C0805")
      (fields (field (name "MPN") "CC0805KKX5R8BB475"))
      (libsource (lib "eagle-import") (part "CERAMIC-4.7UF-25V-10%-X5R(0805)"))
    )
    (comp (ref "C5")
      (value "100nF.")
      (footprint "eagle-import:C0805")
      (fields (field (name "MPN") "CC0805KRX7R9BB104"))
      (libsource (lib "eagle-import") (part "CERAMIC-100NF-50V-10%-X7R(0805)"))
    )
    (comp (ref "C6")
      (value "100nF.")
      (footprint "eagle-import:C0805")
      (fields (field (name "MPN") "CC0805KRX7R9BB104"))
      (libsource (lib "eagle-import") (part "CERAMIC-100NF-50V-10%-X7R(0805)"))
    )
    (comp (ref "C7")
      (value "2.2nF")
      (footprint "eagle-import:C0805")
      (fields (field (name "MPN") "CC0805KRX7R9BB104"))
      (libsource (lib "eagle-import") (part "CERAMIC-100NF-50V-10%-X7R(0805)"))
    )
    (comp (ref "C8")
      (value "100nF")
      (footprint "eagle-import:C0805")
      (fields (field (name "MPN") "CC0805KRX7R9BB104"))
      (libsource (lib "eagle-import") (part "CERAMIC-100NF-50V-10%-X7R(0805)"))
    )
    (comp (ref "C9")
      (value "100nF")
      (footprint "eagle-import:C0805")
      (fields (field (name "MPN") "CC0805KRX7R9BB104"))
      (libsource (lib "eagle-import") (part "CERAMIC-100NF-50V-10%-X7R(0805)"))
    )
    (comp (ref "C10")
      (value "100nF,")
      (footprint "eagle-import:C0805")
      (fields (field (name "MPN") "CC0805KRX7R9BB104"))
      (libsource (lib "eagle-import") (part "CERAMIC-100NF-50V-10%-X7R(0805)"))
    )
    (comp (ref "D1")
      (value "1N4007")
      (footprint "eagle-import:DO-214AC")
      (libsource (lib "eagle-import") (part "DIODE-GEN-PURPOSE-1KV-1A(DO-214AC)"))
    )
    (comp (ref "D2")
      (value "1N4007,")
      (footprint "eagle-import:DO-214AC")
      (fields (field (name "MPN") "1N4007"))
      (libsource (lib "eagle-import") (part "DIODE-GEN-PURPOSE-1KV-1A(DO-214AC)"))
    )
    (comp (ref "D3")
      (value "1N4007,")
      (footprint "eagle-import:DO-214AC")
      (fields (field (name "MPN") "1N4007"))
      (libsource (lib "eagle-import") (part "DIODE-GEN-PURPOSE-1KV-1A(DO-214AC)"))
    )
    (comp (ref "D4")
      (value "1N4007.")
      (footprint "eagle-import:DO-214AC")
      (fields (field (name "MPN") "1N4007"))
      (libsource (lib "eagle-import") (part "DIODE-GEN-PURPOSE-1KV-1A(DO-214AC)"))
    )
    (comp (ref "D5")
      (value "1N5817")
      (footprint "eagle-import:DO-214AC_SLIM")
      (libsource (lib "eagle-import") (part "DIODE-GEN-PURPOSE-1KV-1A(DO-214AC)DO-214AC/1206"))
    )
    (comp (ref "D6")
      (value "1N5817.")
      (footprint "eagle-import:DO-214AC_SLIM")
      (libsource (lib "eagle-import") (part "DIODE-GEN-PURPOSE-1KV-1A(DO-214AC)DO-214AC/1206"))
    )
    (comp (ref "D7")
      (value "1N5817.")
      (footprint "eagle-import:DO-214AC_SLIM")
      (libsource (lib "eagle-import") (part "DIODE-GEN-PURPOSE-1KV-1A(DO-214AC)DO-214AC/1206"))
    )
    (comp (ref "D8")
      (value "1N5817")
      (footprint "eagle-import:DO-214AC_SLIM")
      (libsource (lib "eagle-import") (part "DIODE-GEN-PURPOSE-1KV-1A(DO-214AC)DO-214AC/1206"))
    )
    (comp (ref "D9")
      (value "1N4007.")
      (footprint "eagle-import:DO-214AC")
      (fields (field (name "MPN") "1N4007"))
      (libsource (lib "eagle-import") (part "DIODE-GEN-PURPOSE-1KV-1A(DO-214AC)"))
    )
    (comp (ref "D10")
      (value "1N4007")
      (footprint "eagle-import:DO-214AC")
      (libsource (lib "eagle-import") (part "DIODE-GEN-PURPOSE-1KV-1A(DO-214AC)"))
    )
    (comp (ref "D11")
      (value "SM6T")
      (footprint "eagle-import:DO214AA")
      (libsource (lib "eagle-import") (part "SM6T"))
    )
    (comp (ref "FID1B1")
      (value "FIDUCIALFIDUCIAL_1MM_WITH_SOLDERMASK")
      (footprint "eagle-import:FIDUCIAL_1MM_WITH_SOLDERMASK")
      (libsource (lib "eagle-import") (part "FIDUCIALFIDUCIAL_1MM_WITH_SOLDERMASK"))
    )
    (comp (ref "FID2B1")
      (value "FIDUCIALFIDUCIAL_1MM_WITH_SOLDERMASK")
      (footprint "eagle-import:FIDUCIAL_1MM_WITH_SOLDERMASK")
      (libsource (lib "eagle-import") (part "FIDUCIALFIDUCIAL_1MM_WITH_SOLDERMASK"))
    )
    (comp (ref "FID3")
      (value "FIDUCIAL")
      (footprint "eagle-import:FIDUCIAL_1MM")
      (libsource (lib "eagle-import") (part "FIDUCIAL"))
    )
    (comp (ref "FID4")
      (value "FIDUCIAL")
      (footprint "eagle-import:FIDUCIAL_1MM")
      (libsource (lib "eagle-import") (part "FIDUCIAL"))
    )
    (comp (ref "FID5")
      (value "FIDUCIAL")
      (footprint "eagle-import:FIDUCIAL_1MM")
      (libsource (lib "eagle-import") (part "FIDUCIAL"))
    )
    (comp (ref "FID6")
      (value "FIDUCIAL")
      (footprint "eagle-import:FIDUCIAL_1MM")
      (libsource (lib "eagle-import") (part "FIDUCIAL"))
    )
    (comp (ref "FID27")
      (value "FIDUCIAL")
      (footprint "eagle-import:FIDUCIAL_1MM")
      (libsource (lib "eagle-import") (part "FIDUCIAL"))
    )
    (comp (ref "FID28")
      (value "FIDUCIAL")
      (footprint "eagle-import:FIDUCIAL_1MM")
      (libsource (lib "eagle-import") (part "FIDUCIAL"))
    )
    (comp (ref "IC1")
      (value "4028")
      (footprint "eagle-import:SO16")
      (libsource (lib "eagle-import") (part "4028D"))
    )
    (comp (ref "IC2")
      (value "6V pos")
      (footprint "eagle-import:78LXX")
      (libsource (lib "eagle-import") (part "v-reg_78LXX"))
    )
    (comp (ref "IC3")
      (value "317TO202H_NOHOLE")
      (footprint "eagle-import:TO220H_NOHOLE")
      (libsource (lib "eagle-import") (part "317TO202H_NOHOLE"))
    )
    (comp (ref "IC4")
      (value "ULN2004")
      (footprint "eagle-import:SO16")
      (libsource (lib "eagle-import") (part "ULN2004AD"))
    )
    (comp (ref "IC5")
      (value "LM339")
      (footprint "eagle-import:SO14")
      (libsource (lib "eagle-import") (part "LM339D"))
    )
    (comp (ref "IC6")
      (value "78L06")
      (footprint "eagle-import:SOT89_ROUND")
      (libsource (lib "eagle-import") (part "78LXXSOT89_ROUND"))
    )
    (comp (ref "IC7")
      (value "555")
      (footprint "eagle-import:SO08")
      (libsource (lib "eagle-import") (part "555DNE"))
    )
    (comp (ref "IC8")
      (value "4538")
      (footprint "eagle-import:SO16")
      (libsource (lib "eagle-import") (part "4538D"))
    )
    (comp (ref "IC9")
      (value "78L10")
      (footprint "eagle-import:SOT89_ROUND")
      (libsource (lib "eagle-import") (part "78LXXSOT89_ROUND"))
    )
    (comp (ref "IC10")
      (value "LM2904")
      (footprint "eagle-import:SO08")
      (libsource (lib "eagle-import") (part "LM358D"))
    )
    (comp (ref "JP1")
      (value "JP2EJP2_SMALLPADS")
      (footprint "eagle-import:JP2_SMALLPADS")
      (libsource (lib "eagle-import") (part "JP2EJP2_SMALLPADS"))
    )
    (comp (ref "JP2")
      (value "JP2E_ORIG")
      (footprint "eagle-import:JP2_ORIG_SMALLPADS")
      (libsource (lib "eagle-import") (part "JP2E_ORIG"))
    )
    (comp (ref "JP3")
      (value "JP2EJP2_SMALLPADS")
      (footprint "eagle-import:JP2_SMALLPADS")
      (libsource (lib "eagle-import") (part "JP2EJP2_SMALLPADS"))
    )
    (comp (ref "JP4")
      (value "JP2EJP2_SMALLPADS")
      (footprint "eagle-import:JP2_SMALLPADS")
      (libsource (lib "eagle-import") (part "JP2EJP2_SMALLPADS"))
    )
    (comp (ref "JP5")
      (value "JP2EJP2_SMALLPADS")
      (footprint "eagle-import:JP2_SMALLPADS")
      (libsource (lib "eagle-import") (part "JP2EJP2_SMALLPADS"))
    )
    (comp (ref "LED1")
      (value "LEDLD260")
      (footprint "eagle-import:LD260")
      (libsource (lib "eagle-import") (part "LEDLD260"))
    )
    (comp (ref "LED2")
      (value "LEDLD260")
      (footprint "eagle-import:LD260")
      (libsource (lib "eagle-import") (part "LEDLD260"))
    )
    (comp (ref "LED3")
      (value "LEDLD260")
      (footprint "eagle-import:LD260")
      (libsource (lib "eagle-import") (part "LEDLD260"))
    )
    (comp (ref "LED4")
      (value "LEDLD260")
      (footprint "eagle-import:LD260")
      (libsource (lib "eagle-import") (part "LEDLD260"))
    )
    (comp (ref "LED5")
      (value "LEDLD260")
      (footprint "eagle-import:LD260")
      (libsource (lib "eagle-import") (part "LEDLD260"))
    )
    (comp (ref "LED6")
      (value "LEDLD260")
      (footprint "eagle-import:LD260")
      (libsource (lib "eagle-import") (part "LEDLD260"))
    )
    (comp (ref "Q1")
      (value "BA")
      (footprint "eagle-import:SOT89")
      (libsource (lib "eagle-import") (part "PNP-TRANSISTOR_SOT89"))
    )
    (comp (ref "Q2")
      (value "BA.")
      (footprint "eagle-import:SOT89")
      (libsource (lib "eagle-import") (part "PNP-TRANSISTOR_SOT89"))
    )
    (comp (ref "Q3")
      (value "BA.")
      (footprint "eagle-import:SOT89")
      (libsource (lib "eagle-import") (part "PNP-TRANSISTOR_SOT89"))
    )
    (comp (ref "Q4")
      (value "BA")
      (footprint "eagle-import:SOT89")
      (libsource (lib "eagle-import") (part "PNP-TRANSISTOR_SOT89"))
    )
    (comp (ref "Q5")
      (value "MY")
      (footprint "eagle-import:SOT89")
      (libsource (lib "eagle-import") (part "NPN-TRANSISTOR_SOT89"))
    )
    (comp (ref "Q6")
      (value "J1")
      (footprint "eagle-import:SOT-23")
      (fields (field (name "MPN") "BSS138W-7-F"))
      (libsource (lib "eagle-import") (part "SMD-MOSFET-N-CH-50V-200MA-BSS138W-7-F(SOT-23)"))
    )
    (comp (ref "Q7")
      (value "J1")
      (footprint "eagle-import:SOT-23")
      (fields (field (name "MPN") "BSS138W-7-F"))
      (libsource (lib "eagle-import") (part "SMD-MOSFET-N-CH-50V-200MA-BSS138W-7-F(SOT-23)"))
    )
    (comp (ref "R1")
      (value "47")
      (footprint "eagle-import:V235_17_1MM")
      (libsource (lib "eagle-import") (part "R-EU_V235/17_1MM"))
    )
    (comp (ref "R2")
      (value "13")
      (footprint "eagle-import:R1206")
      (fields (field (name "MPN") "RC1206JR-0713RL"))
      (libsource (lib "eagle-import") (part "SMD-RES-13R-5%-1/4W(1206)"))
    )
    (comp (ref "R3")
      (value "47")
      (footprint "eagle-import:V235_17_1MM")
      (libsource (lib "eagle-import") (part "R-EU_V235/17_1MM"))
    )
    (comp (ref "R4")
      (value "104")
      (footprint "eagle-import:R0805")
      (fields (field (name "MPN") "RC0805FR-0710KL"))
      (libsource (lib "eagle-import") (part "SMD-RES-10K-1%-1/8W(0805)"))
    )
    (comp (ref "R5")
      (value "104")
      (footprint "eagle-import:R0805")
      (fields (field (name "MPN") "RC0805FR-0710KL"))
      (libsource (lib "eagle-import") (part "SMD-RES-10K-1%-1/8W(0805)"))
    )
    (comp (ref "R6")
      (value "104")
      (footprint "eagle-import:R0805")
      (fields (field (name "MPN") "RC0805FR-0710KL"))
      (libsource (lib "eagle-import") (part "SMD-RES-10K-1%-1/8W(0805)"))
    )
    (comp (ref "R7")
      (value "4701")
      (footprint "eagle-import:R0805")
      (fields (field (name "MPN") "RC0805JR-074K7L"))
      (libsource (lib "eagle-import") (part "SMD-RES-4.7K-5%-1/8W(0805)"))
    )
    (comp (ref "R8")
      (value "1002")
      (footprint "eagle-import:R0805")
      (fields (field (name "MPN") "RC0805FR-0710KL"))
      (libsource (lib "eagle-import") (part "SMD-RES-10K-1%-1/8W(0805)"))
    )
    (comp (ref "R9")
      (value "1002")
      (footprint "eagle-import:R0805")
      (fields (field (name "MPN") "RC0805FR-0710KL"))
      (libsource (lib "eagle-import") (part "SMD-RES-10K-1%-1/8W(0805)"))
    )
    (comp (ref "R10")
      (value "1502")
      (footprint "eagle-import:R0805")
      (fields (field (name "MPN") "RC0805FR-0710KL"))
      (libsource (lib "eagle-import") (part "SMD-RES-10K-1%-1/8W(0805)"))
    )
    (comp (ref "R11")
      (value "104")
      (footprint "eagle-import:R0805")
      (fields (field (name "MPN") "RC0805FR-0710KL"))
      (libsource (lib "eagle-import") (part "SMD-RES-10K-1%-1/8W(0805)"))
    )
    (comp (ref "R12")
      (value "104")
      (footprint "eagle-import:R0805")
      (fields (field (name "MPN") "RC0805FR-0710KL"))
      (libsource (lib "eagle-import") (part "SMD-RES-10K-1%-1/8W(0805)"))
    )
    (comp (ref "R13")
      (value "1502")
      (footprint "eagle-import:R0805")
      (fields (field (name "MPN") "RC0805FR-0710KL"))
      (libsource (lib "eagle-import") (part "SMD-RES-10K-1%-1/8W(0805)"))
    )
    (comp (ref "R14")
      (value "1002")
      (footprint "eagle-import:R0805")
      (fields (field (name "MPN") "RC0805FR-0710KL"))
      (libsource (lib "eagle-import") (part "SMD-RES-10K-1%-1/8W(0805)"))
    )
    (comp (ref "R15")
      (value "2201")
      (footprint "eagle-import:R0805")
      (fields (field (name "MPN") "RC0805JR-072K2L"))
      (libsource (lib "eagle-import") (part "SMD-RES-2.2K-5%-1/8W(0805)"))
    )
    (comp (ref "R16")
      (value "1002")
      (footprint "eagle-import:R0805")
      (fields (field (name "MPN") "RC0805FR-0710KL"))
      (libsource (lib "eagle-import") (part "SMD-RES-10K-1%-1/8W(0805)"))
    )
    (comp (ref "R17")
      (value "4701")
      (footprint "eagle-import:R0805")
      (fields (field (name "MPN") "RC0805JR-074K7L"))
      (libsource (lib "eagle-import") (part "SMD-RES-4.7K-5%-1/8W(0805)"))
    )
    (comp (ref "R18")
      (value "2702")
      (footprint "eagle-import:R0805")
      (fields (field (name "MPN") "RC0805JR-074K7L"))
      (libsource (lib "eagle-import") (part "SMD-RES-4.7K-5%-1/8W(0805)"))
    )
    (comp (ref "R19")
      (value "102")
      (footprint "eagle-import:R0805")
      (fields (field (name "MPN") "RC0805JR-071KL"))
      (libsource (lib "eagle-import") (part "SMD-RES-1K-5%-1/8W(0805)"))
    )
    (comp (ref "R20")
      (value "100")
      (footprint "eagle-import:R0805")
      (fields (field (name "MPN") "RC0805JR-07220RL"))
      (libsource (lib "eagle-import") (part "SMD-RES-220R-5%-1/8W(0805)"))
    )
    (comp (ref "R21")
      (value "(101)")
      (footprint "eagle-import:R0805")
      (fields (field (name "MPN") "RC0805JR-07100RL"))
      (libsource (lib "eagle-import") (part "SMD-RES-100R-5%-1/8W(0805)"))
    )
    (comp (ref "R22")
      (value "(1000)")
      (footprint "eagle-import:R0805")
      (fields (field (name "MPN") "RC0805JR-07100RL"))
      (libsource (lib "eagle-import") (part "SMD-RES-100R-5%-1/8W(0805)"))
    )
    (comp (ref "R23")
      (value "102")
      (footprint "eagle-import:R0805")
      (fields (field (name "MPN") "RC0805JR-071KL"))
      (libsource (lib "eagle-import") (part "SMD-RES-1K-5%-1/8W(0805)"))
    )
    (comp (ref "R24")
      (value "13")
      (footprint "eagle-import:R1206")
      (fields (field (name "MPN") "RC1206JR-0713RL"))
      (libsource (lib "eagle-import") (part "SMD-RES-13R-5%-1/4W(1206)"))
    )
    (comp (ref "R25")
      (value "13")
      (footprint "eagle-import:R1206")
      (fields (field (name "MPN") "RC1206JR-0713RL"))
      (libsource (lib "eagle-import") (part "SMD-RES-13R-5%-1/4W(1206)"))
    )
    (comp (ref "R26")
      (value "2702")
      (footprint "eagle-import:R0805")
      (fields (field (name "MPN") "RC0805JR-074K7L"))
      (libsource (lib "eagle-import") (part "SMD-RES-4.7K-5%-1/8W(0805)"))
    )
    (comp (ref "R27")
      (value "4701")
      (footprint "eagle-import:R0805")
      (fields (field (name "MPN") "RC0805JR-074K7L"))
      (libsource (lib "eagle-import") (part "SMD-RES-4.7K-5%-1/8W(0805)"))
    )
    (comp (ref "R28")
      (value "100")
      (footprint "eagle-import:R0805")
      (fields (field (name "MPN") "RC0805JR-072K2L"))
      (libsource (lib "eagle-import") (part "SMD-RES-2.2K-5%-1/8W(0805)"))
    )
    (comp (ref "R29")
      (value "(101)")
      (footprint "eagle-import:R0805")
      (fields (field (name "MPN") "RC0805JR-072K2L"))
      (libsource (lib "eagle-import") (part "SMD-RES-2.2K-5%-1/8W(0805)"))
    )
    (comp (ref "R30")
      (value "104")
      (footprint "eagle-import:R0805")
      (fields (field (name "MPN") "RC0805FR-0710KL"))
      (libsource (lib "eagle-import") (part "SMD-RES-10K-1%-1/8W(0805)"))
    )
    (comp (ref "R31")
      (value "104")
      (footprint "eagle-import:R0805")
      (fields (field (name "MPN") "RC0805FR-0710KL"))
      (libsource (lib "eagle-import") (part "SMD-RES-10K-1%-1/8W(0805)"))
    )
    (comp (ref "R32")
      (value "(1002)")
      (footprint "eagle-import:R0805")
      (fields (field (name "MPN") "RC0805FR-0710KL"))
      (libsource (lib "eagle-import") (part "SMD-RES-10K-1%-1/8W(0805)"))
    )
    (comp (ref "R33")
      (value "2702")
      (footprint "eagle-import:R0805")
      (fields (field (name "MPN") "RC0805FR-0710KL"))
      (libsource (lib "eagle-import") (part "SMD-RES-10K-1%-1/8W(0805)"))
    )
    (comp (ref "R34")
      (value "47")
      (footprint "eagle-import:V235_17_1MM")
      (libsource (lib "eagle-import") (part "R-EU_V235/17_1MM"))
    )
    (comp (ref "R35")
      (value "47")
      (footprint "eagle-import:V235_17_1MM")
      (libsource (lib "eagle-import") (part "R-EU_V235/17_1MM"))
    )
    (comp (ref "R36")
      (value "2702")
      (footprint "eagle-import:R0805")
      (fields (field (name "MPN") "RC0805JR-074K7L"))
      (libsource (lib "eagle-import") (part "SMD-RES-4.7K-5%-1/8W(0805)"))
    )
    (comp (ref "R37")
      (value "2201")
      (footprint "eagle-import:R0805")
      (fields (field (name "MPN") "RC0805JR-072K2L"))
      (libsource (lib "eagle-import") (part "SMD-RES-2.2K-5%-1/8W(0805)"))
    )
    (comp (ref "R38")
      (value "(1002)")
      (footprint "eagle-import:R0805")
      (fields (field (name "MPN") "RC0805JR-074K7L"))
      (libsource (lib "eagle-import") (part "SMD-RES-4.7K-5%-1/8W(0805)"))
    )
    (comp (ref "R39")
      (value "1002")
      (footprint "eagle-import:R0805")
      (fields (field (name "MPN") "RC0805FR-0710KL"))
      (libsource (lib "eagle-import") (part "SMD-RES-10K-1%-1/8W(0805)"))
    )
    (comp (ref "R40")
      (value "102")
      (footprint "eagle-import:R0805")
      (fields (field (name "MPN") "RC0805JR-071KL"))
      (libsource (lib "eagle-import") (part "SMD-RES-1K-5%-1/8W(0805)"))
    )
    (comp (ref "R41")
      (value "2702")
      (footprint "eagle-import:R0805")
      (fields (field (name "MPN") "RC0805JR-074K7L"))
      (libsource (lib "eagle-import") (part "SMD-RES-4.7K-5%-1/8W(0805)"))
    )
    (comp (ref "R42")
      (value "102")
      (footprint "eagle-import:R0805")
      (fields (field (name "MPN") "RC0805JR-071KL"))
      (libsource (lib "eagle-import") (part "SMD-RES-1K-5%-1/8W(0805)"))
    )
    (comp (ref "R43")
      (value "102")
      (footprint "eagle-import:R0805")
      (fields (field (name "MPN") "RC0805JR-071KL"))
      (libsource (lib "eagle-import") (part "SMD-RES-1K-5%-1/8W(0805)"))
    )
    (comp (ref "R44")
      (value "13")
      (footprint "eagle-import:R1206")
      (fields (field (name "MPN") "RC1206JR-0713RL"))
      (libsource (lib "eagle-import") (part "SMD-RES-13R-5%-1/4W(1206)"))
    )
    (comp (ref "R45")
      (value "R_user")
      (footprint "eagle-import:R0805")
      (libsource (lib "eagle-import") (part "R-EU_R0805"))
    )
    (comp (ref "SJ1") (value "SJ") (footprint "eagle-import:SJ") (libsource (lib "eagle-import") (part "SJ")))
    (comp (ref "START1")
      (value "TPSB2.0")
      (footprint "eagle-import:B2.0")
      (libsource (lib "eagle-import") (part "TPSB2.0"))
    )
    (comp (ref "TP70")
      (value "TPSB2.0")
      (footprint "eagle-import:B2.0")
      (libsource (lib "eagle-import") (part "TPSB2.0"))
    )
    (comp (ref "TP71")
      (value "TPSB2.0")
      (footprint "eagle-import:B2.0")
      (libsource (lib "eagle-import") (part "TPSB2.0"))
    )
    (comp (ref "TP72")
      (value "TPSB2.0")
      (footprint "eagle-import:B2.0")
      (libsource (lib "eagle-import") (part "TPSB2.0"))
    )
    (comp (ref "TP73")
      (value "TPSB2.0")
      (footprint "eagle-import:B2.0")
      (libsource (lib "eagle-import") (part "TPSB2.0"))
    )
    (comp (ref "TP74")
      (value "TPSB2.0")
      (footprint "eagle-import:B2.0")
      (libsource (lib "eagle-import") (part "TPSB2.0"))
    )
    (comp (ref "TP75")
      (value "TPSB2.0")
      (footprint "eagle-import:B2.0")
      (libsource (lib "eagle-import") (part "TPSB2.0"))
    )
    (comp (ref "TP76")
      (value "TPSB2.0")
      (footprint "eagle-import:B2.0")
      (libsource (lib "eagle-import") (part "TPSB2.0"))
    )
    (comp (ref "TP77")
      (value "TPSB2.0")
      (footprint "eagle-import:B2.0")
      (libsource (lib "eagle-import") (part "TPSB2.0"))
    )
    (comp (ref "TP78")
      (value "TPSB2.0")
      (footprint "eagle-import:B2.0")
      (libsource (lib "eagle-import") (part "TPSB2.0"))
    )
    (comp (ref "TP79")
      (value "TPSB2.0")
      (footprint "eagle-import:B2.0")
      (libsource (lib "eagle-import") (part "TPSB2.0"))
    )
    (comp (ref "TP80")
      (value "TPSB2.0")
      (footprint "eagle-import:B2.0")
      (libsource (lib "eagle-import") (part "TPSB2.0"))
    )
    (comp (ref "TP81")
      (value "TPSB2.0")
      (footprint "eagle-import:B2.0")
      (libsource (lib "eagle-import") (part "TPSB2.0"))
    )
    (comp (ref "TP82")
      (value "TPSB2.0")
      (footprint "eagle-import:B2.0")
      (libsource (lib "eagle-import") (part "TPSB2.0"))
    )
    (comp (ref "TP83")
      (value "TPSB2.0")
      (footprint "eagle-import:B2.0")
      (libsource (lib "eagle-import") (part "TPSB2.0"))
    )
    (comp (ref "TP84")
      (value "TPSB2.0")
      (footprint "eagle-import:B2.0")
      (libsource (lib "eagle-import") (part "TPSB2.0"))
    )
    (comp (ref "TP85")
      (value "TPSB2.0")
      (footprint "eagle-import:B2.0")
      (libsource (lib "eagle-import") (part "TPSB2.0"))
    )
    (comp (ref "TP86")
      (value "TPSB2.0")
      (footprint "eagle-import:B2.0")
      (libsource (lib "eagle-import") (part "TPSB2.0"))
    )
    (comp (ref "TP87")
      (value "TPSB2.0")
      (footprint "eagle-import:B2.0")
      (libsource (lib "eagle-import") (part "TPSB2.0"))
    )
    (comp (ref "TP88")
      (value "TPSB1,27")
      (footprint "eagle-import:B1,27")
      (libsource (lib "eagle-import") (part "TPSB1,27"))
    )
    (comp (ref "TP89")
      (value "TPSB2.0")
      (footprint "eagle-import:B2.0")
      (libsource (lib "eagle-import") (part "TPSB2.0"))
    )
    (comp (ref "TP90")
      (value "TPSB2.0")
      (footprint "eagle-import:B2.0")
      (libsource (lib "eagle-import") (part "TPSB2.0"))
    )
    (comp (ref "TP91")
      (value "TPSB2.0")
      (footprint "eagle-import:B2.0")
      (libsource (lib "eagle-import") (part "TPSB2.0"))
    )
    (comp (ref "TP92")
      (value "TPSB2.0")
      (footprint "eagle-import:B2.0")
      (libsource (lib "eagle-import") (part "TPSB2.0"))
    )
    (comp (ref "X1")
      (value "CON_BMWV2")
      (footprint "eagle-import:24-PIN_V2")
      (libsource (lib "eagle-import") (part "CON_BMWV2"))
    )
    (comp (ref "X2")
      (value "22-23-2051")
      (footprint "eagle-import:22-23-2051")
      (fields (field (name "MF") "MOLEX"))
      (libsource (lib "eagle-import") (part "22-23-2051"))
    )
    (comp (ref "X3")
      (value "22-23-2021")
      (footprint "eagle-import:22-23-2021")
      (fields (field (name "MF") "MOLEX"))
      (libsource (lib "eagle-import") (part "22-23-2021"))
    )
    (comp (ref "3")
      (value "2081-1132")
      (footprint "eagle-import:12-PIN")
      (libsource (lib "eagle-import") (part "2081-1132"))
    )
    (comp (ref "4")
      (value "2081-1132")
      (footprint "eagle-import:12-PIN")
      (libsource (lib "eagle-import") (part "2081-1132"))
    )
    (comp (ref "6V201")
      (value "TPSB2.0")
      (footprint "eagle-import:B2.0")
      (libsource (lib "eagle-import") (part "TPSB2.0"))
    )
    (comp (ref "10V201")
      (value "TPSB2.0")
      (footprint "eagle-import:B2.0")
      (libsource (lib "eagle-import") (part "TPSB2.0"))
    )
    (comp (ref "C201")
      (value "4.7u")
      (footprint "eagle-import:C0805")
      (fields (field (name "MPN") "CC0805KKX5R8BB475"))
      (libsource (lib "eagle-import") (part "CERAMIC-4.7UF-25V-10%-X5R(0805)"))
    )
    (comp (ref "C202")
      (value "100nF")
      (footprint "eagle-import:C0805")
      (fields (field (name "MPN") "CC0805KRX7R9BB104"))
      (libsource (lib "eagle-import") (part "CERAMIC-100NF-50V-10%-X7R(0805)"))
    )
    (comp (ref "C203")
      (value "100nF,")
      (footprint "eagle-import:C0805")
      (fields (field (name "MPN") "CC0805KRX7R9BB104"))
      (libsource (lib "eagle-import") (part "CERAMIC-100NF-50V-10%-X7R(0805)"))
    )
    (comp (ref "C204")
      (value "100nF,")
      (footprint "eagle-import:C0805")
      (fields (field (name "MPN") "CC0805KRX7R9BB104"))
      (libsource (lib "eagle-import") (part "CERAMIC-100NF-50V-10%-X7R(0805)"))
    )
    (comp (ref "C205")
      (value "100nF.")
      (footprint "eagle-import:C0805")
      (fields (field (name "MPN") "CC0805KRX7R9BB104"))
      (libsource (lib "eagle-import") (part "CERAMIC-100NF-50V-10%-X7R(0805)"))
    )
    (comp (ref "C206")
      (value "100nF.")
      (footprint "eagle-import:C0805")
      (fields (field (name "MPN") "CC0805KRX7R9BB104"))
      (libsource (lib "eagle-import") (part "CERAMIC-100NF-50V-10%-X7R(0805)"))
    )
    (comp (ref "C207")
      (value "100u")
      (footprint "eagle-import:C1206")
      (fields (field (name "MPN") "GRM31CR60J107ME39L"))
      (libsource (lib "eagle-import") (part "CERAMIC-100UF-6.3V-20%-X5R(1206)"))
    )
    (comp (ref "C208")
      (value "100u")
      (footprint "eagle-import:C1206")
      (fields (field (name "MPN") "GRM31CR60J107ME39L"))
      (libsource (lib "eagle-import") (part "CERAMIC-100UF-6.3V-20%-X5R(1206)"))
    )
    (comp (ref "C209")
      (value "2.2nF")
      (footprint "eagle-import:C0805")
      (fields (field (name "MPN") "CC0805KRX7R9BB104"))
      (libsource (lib "eagle-import") (part "CERAMIC-100NF-50V-10%-X7R(0805)"))
    )
    (comp (ref "C210")
      (value "100nF")
      (footprint "eagle-import:C0805")
      (fields (field (name "MPN") "CC0805KRX7R9BB104"))
      (libsource (lib "eagle-import") (part "CERAMIC-100NF-50V-10%-X7R(0805)"))
    )
    (comp (ref "D201")
      (value "SM6T")
      (footprint "eagle-import:DO214AA")
      (libsource (lib "eagle-import") (part "SM6T"))
    )
    (comp (ref "D202")
      (value "1N4007,")
      (footprint "eagle-import:DO-214AC")
      (fields (field (name "MPN") "1N4007"))
      (libsource (lib "eagle-import") (part "DIODE-GEN-PURPOSE-1KV-1A(DO-214AC)"))
    )
    (comp (ref "D203")
      (value "1N4007,")
      (footprint "eagle-import:DO-214AC")
      (fields (field (name "MPN") "1N4007"))
      (libsource (lib "eagle-import") (part "DIODE-GEN-PURPOSE-1KV-1A(DO-214AC)"))
    )
    (comp (ref "D205")
      (value "1N4007.")
      (footprint "eagle-import:DO-214AC")
      (fields (field (name "MPN") "1N4007"))
      (libsource (lib "eagle-import") (part "DIODE-GEN-PURPOSE-1KV-1A(DO-214AC)"))
    )
    (comp (ref "D206")
      (value "1N4007.")
      (footprint "eagle-import:DO-214AC")
      (fields (field (name "MPN") "1N4007"))
      (libsource (lib "eagle-import") (part "DIODE-GEN-PURPOSE-1KV-1A(DO-214AC)"))
    )
    (comp (ref "D207")
      (value "1N5817")
      (footprint "eagle-import:DO-214AC_SLIM")
      (libsource (lib "eagle-import") (part "DIODE-GEN-PURPOSE-1KV-1A(DO-214AC)DO-214AC/1206"))
    )
    (comp (ref "D208")
      (value "1N5817.")
      (footprint "eagle-import:DO-214AC_SLIM")
      (libsource (lib "eagle-import") (part "DIODE-GEN-PURPOSE-1KV-1A(DO-214AC)DO-214AC/1206"))
    )
    (comp (ref "D209")
      (value "1N5817.")
      (footprint "eagle-import:DO-214AC_SLIM")
      (libsource (lib "eagle-import") (part "DIODE-GEN-PURPOSE-1KV-1A(DO-214AC)DO-214AC/1206"))
    )
    (comp (ref "D210")
      (value "1N5817")
      (footprint "eagle-import:DO-214AC_SLIM")
      (libsource (lib "eagle-import") (part "DIODE-GEN-PURPOSE-1KV-1A(DO-214AC)DO-214AC/1206"))
    )
    (comp (ref "D211")
      (value "1N4007")
      (footprint "eagle-import:DO-214AC")
      (libsource (lib "eagle-import") (part "DIODE-GEN-PURPOSE-1KV-1A(DO-214AC)"))
    )
    (comp (ref "D212")
      (value "1N4007")
      (footprint "eagle-import:DO-214AC")
      (libsource (lib "eagle-import") (part "DIODE-GEN-PURPOSE-1KV-1A(DO-214AC)"))
    )
    (comp (ref "FID201")
      (value "FIDUCIAL")
      (footprint "eagle-import:FIDUCIAL_1MM")
      (libsource (lib "eagle-import") (part "FIDUCIAL"))
    )
    (comp (ref "FID202")
      (value "FIDUCIAL")
      (footprint "eagle-import:FIDUCIAL_1MM")
      (libsource (lib "eagle-import") (part "FIDUCIAL"))
    )
    (comp (ref "FID203")
      (value "FIDUCIAL")
      (footprint "eagle-import:FIDUCIAL_1MM")
      (libsource (lib "eagle-import") (part "FIDUCIAL"))
    )
    (comp (ref "FID204")
      (value "FIDUCIAL")
      (footprint "eagle-import:FIDUCIAL_1MM")
      (libsource (lib "eagle-import") (part "FIDUCIAL"))
    )
    (comp (ref "IC201")
      (value "LM2904")
      (footprint "eagle-import:SO08")
      (libsource (lib "eagle-import") (part "LM358D"))
    )
    (comp (ref "IC202")
      (value "78L06")
      (footprint "eagle-import:SOT89_ROUND")
      (libsource (lib "eagle-import") (part "78LXXSOT89_ROUND"))
    )
    (comp (ref "IC203")
      (value "6V pos")
      (footprint "eagle-import:78LXX")
      (libsource (lib "eagle-import") (part "v-reg_78LXX"))
    )
    (comp (ref "IC204")
      (value "78L10")
      (footprint "eagle-import:SOT89_ROUND")
      (libsource (lib "eagle-import") (part "78LXXSOT89_ROUND"))
    )
    (comp (ref "IC205")
      (value "4028")
      (footprint "eagle-import:SO16")
      (libsource (lib "eagle-import") (part "4028D"))
    )
    (comp (ref "IC207")
      (value "ULN2004")
      (footprint "eagle-import:SO16")
      (libsource (lib "eagle-import") (part "ULN2004AD"))
    )
    (comp (ref "IC208")
      (value "LM339")
      (footprint "eagle-import:SO14")
      (libsource (lib "eagle-import") (part "LM339D"))
    )
    (comp (ref "IC209")
      (value "317TO202H_NOHOLE")
      (footprint "eagle-import:TO220H_NOHOLE")
      (libsource (lib "eagle-import") (part "317TO202H_NOHOLE"))
    )
    (comp (ref "IC210")
      (value "555")
      (footprint "eagle-import:SO08")
      (libsource (lib "eagle-import") (part "555DNE"))
    )
    (comp (ref "IC211")
      (value "4538")
      (footprint "eagle-import:SO16")
      (libsource (lib "eagle-import") (part "4538D"))
    )
    (comp (ref "JP201")
      (value "JP2EJP2_SMALLPADS")
      (footprint "eagle-import:JP2_SMALLPADS")
      (libsource (lib "eagle-import") (part "JP2EJP2_SMALLPADS"))
    )
    (comp (ref "JP202")
      (value "JP2EJP2_SMALLPADS")
      (footprint "eagle-import:JP2_SMALLPADS")
      (libsource (lib "eagle-import") (part "JP2EJP2_SMALLPADS"))
    )
    (comp (ref "JP203")
      (value "JP2EJP2_SMALLPADS")
      (footprint "eagle-import:JP2_SMALLPADS")
      (libsource (lib "eagle-import") (part "JP2EJP2_SMALLPADS"))
    )
    (comp (ref "JP204")
      (value "JP2EJP2_SMALLPADS")
      (footprint "eagle-import:JP2_SMALLPADS")
      (libsource (lib "eagle-import") (part "JP2EJP2_SMALLPADS"))
    )
    (comp (ref "JP205")
      (value "JP2E_ORIG")
      (footprint "eagle-import:JP2_ORIG_SMALLPADS")
      (libsource (lib "eagle-import") (part "JP2E_ORIG"))
    )
    (comp (ref "LED201")
      (value "LEDLD260")
      (footprint "eagle-import:LD260")
      (libsource (lib "eagle-import") (part "LEDLD260"))
    )
    (comp (ref "LED202")
      (value "LEDLD260")
      (footprint "eagle-import:LD260")
      (libsource (lib "eagle-import") (part "LEDLD260"))
    )
    (comp (ref "LED203")
      (value "LEDLD260")
      (footprint "eagle-import:LD260")
      (libsource (lib "eagle-import") (part "LEDLD260"))
    )
    (comp (ref "LED204")
      (value "LEDLD260")
      (footprint "eagle-import:LD260")
      (libsource (lib "eagle-import") (part "LEDLD260"))
    )
    (comp (ref "LED205")
      (value "LEDLD260")
      (footprint "eagle-import:LD260")
      (libsource (lib "eagle-import") (part "LEDLD260"))
    )
    (comp (ref "LED206")
      (value "LEDLD260")
      (footprint "eagle-import:LD260")
      (libsource (lib "eagle-import") (part "LEDLD260"))
    )
    (comp (ref "Q201")
      (value "BA.")
      (footprint "eagle-import:SOT89")
      (libsource (lib "eagle-import") (part "PNP-TRANSISTOR_SOT89"))
    )
    (comp (ref "Q202")
      (value "BA.")
      (footprint "eagle-import:SOT89")
      (libsource (lib "eagle-import") (part "PNP-TRANSISTOR_SOT89"))
    )
    (comp (ref "Q203")
      (value "MY")
      (footprint "eagle-import:SOT89")
      (libsource (lib "eagle-import") (part "NPN-TRANSISTOR_SOT89"))
    )
    (comp (ref "Q204")
      (value "BA")
      (footprint "eagle-import:SOT89")
      (libsource (lib "eagle-import") (part "PNP-TRANSISTOR_SOT89"))
    )
    (comp (ref "Q205")
      (value "BA")
      (footprint "eagle-import:SOT89")
      (libsource (lib "eagle-import") (part "PNP-TRANSISTOR_SOT89"))
    )
    (comp (ref "Q206")
      (value "J1")
      (footprint "eagle-import:SOT-23")
      (fields (field (name "MPN") "BSS138W-7-F"))
      (libsource (lib "eagle-import") (part "SMD-MOSFET-N-CH-50V-200MA-BSS138W-7-F(SOT-23)"))
    )
    (comp (ref "Q207")
      (value "J1")
      (footprint "eagle-import:SOT-23")
      (fields (field (name "MPN") "BSS138W-7-F"))
      (libsource (lib "eagle-import") (part "SMD-MOSFET-N-CH-50V-200MA-BSS138W-7-F(SOT-23)"))
    )
    (comp (ref "R201")
      (value "102")
      (footprint "eagle-import:R0805")
      (fields (field (name "MPN") "RC0805JR-071KL"))
      (libsource (lib "eagle-import") (part "SMD-RES-1K-5%-1/8W(0805)"))
    )
    (comp (ref "R202")
      (value "13")
      (footprint "eagle-import:R1206")
      (fields (field (name "MPN") "RC1206JR-0713RL"))
      (libsource (lib "eagle-import") (part "SMD-RES-13R-5%-1/4W(1206)"))
    )
    (comp (ref "R203")
      (value "R_user")
      (footprint "eagle-import:R0805")
      (libsource (lib "eagle-import") (part "R-EU_R0805"))
    )
    (comp (ref "R205")
      (value "4701")
      (footprint "eagle-import:R0805")
      (fields (field (name "MPN") "RC0805JR-074K7L"))
      (libsource (lib "eagle-import") (part "SMD-RES-4.7K-5%-1/8W(0805)"))
    )
    (comp (ref "R206")
      (value "13")
      (footprint "eagle-import:R1206")
      (fields (field (name "MPN") "RC1206JR-0713RL"))
      (libsource (lib "eagle-import") (part "SMD-RES-13R-5%-1/4W(1206)"))
    )
    (comp (ref "R207")
      (value "1002")
      (footprint "eagle-import:R0805")
      (fields (field (name "MPN") "RC0805FR-0710KL"))
      (libsource (lib "eagle-import") (part "SMD-RES-10K-1%-1/8W(0805)"))
    )
    (comp (ref "R208")
      (value "1002")
      (footprint "eagle-import:R0805")
      (fields (field (name "MPN") "RC0805FR-0710KL"))
      (libsource (lib "eagle-import") (part "SMD-RES-10K-1%-1/8W(0805)"))
    )
    (comp (ref "R209")
      (value "104")
      (footprint "eagle-import:R0805")
      (fields (field (name "MPN") "RC0805FR-0710KL"))
      (libsource (lib "eagle-import") (part "SMD-RES-10K-1%-1/8W(0805)"))
    )
    (comp (ref "R210")
      (value "104")
      (footprint "eagle-import:R0805")
      (fields (field (name "MPN") "RC0805FR-0710KL"))
      (libsource (lib "eagle-import") (part "SMD-RES-10K-1%-1/8W(0805)"))
    )
    (comp (ref "R211")
      (value "104")
      (footprint "eagle-import:R0805")
      (fields (field (name "MPN") "RC0805FR-0710KL"))
      (libsource (lib "eagle-import") (part "SMD-RES-10K-1%-1/8W(0805)"))
    )
    (comp (ref "R212")
      (value "102")
      (footprint "eagle-import:R0805")
      (fields (field (name "MPN") "RC0805JR-071KL"))
      (libsource (lib "eagle-import") (part "SMD-RES-1K-5%-1/8W(0805)"))
    )
    (comp (ref "R213")
      (value "102")
      (footprint "eagle-import:R0805")
      (fields (field (name "MPN") "RC0805JR-071KL"))
      (libsource (lib "eagle-import") (part "SMD-RES-1K-5%-1/8W(0805)"))
    )
    (comp (ref "R214")
      (value "102")
      (footprint "eagle-import:R0805")
      (fields (field (name "MPN") "RC0805JR-071KL"))
      (libsource (lib "eagle-import") (part "SMD-RES-1K-5%-1/8W(0805)"))
    )
    (comp (ref "R215")
      (value "100")
      (footprint "eagle-import:R0805")
      (fields (field (name "MPN") "RC0805JR-07220RL"))
      (libsource (lib "eagle-import") (part "SMD-RES-220R-5%-1/8W(0805)"))
    )
    (comp (ref "R216")
      (value "4701")
      (footprint "eagle-import:R0805")
      (fields (field (name "MPN") "RC0805JR-074K7L"))
      (libsource (lib "eagle-import") (part "SMD-RES-4.7K-5%-1/8W(0805)"))
    )
    (comp (ref "R217")
      (value "2702")
      (footprint "eagle-import:R0805")
      (fields (field (name "MPN") "RC0805JR-074K7L"))
      (libsource (lib "eagle-import") (part "SMD-RES-4.7K-5%-1/8W(0805)"))
    )
    (comp (ref "R218")
      (value "13")
      (footprint "eagle-import:R1206")
      (fields (field (name "MPN") "RC1206JR-0713RL"))
      (libsource (lib "eagle-import") (part "SMD-RES-13R-5%-1/4W(1206)"))
    )
    (comp (ref "R219")
      (value "2201")
      (footprint "eagle-import:R0805")
      (fields (field (name "MPN") "RC0805JR-072K2L"))
      (libsource (lib "eagle-import") (part "SMD-RES-2.2K-5%-1/8W(0805)"))
    )
    (comp (ref "R220")
      (value "1002")
      (footprint "eagle-import:R0805")
      (fields (field (name "MPN") "RC0805FR-0710KL"))
      (libsource (lib "eagle-import") (part "SMD-RES-10K-1%-1/8W(0805)"))
    )
    (comp (ref "R221")
      (value "1502")
      (footprint "eagle-import:R0805")
      (fields (field (name "MPN") "RC0805FR-0710KL"))
      (libsource (lib "eagle-import") (part "SMD-RES-10K-1%-1/8W(0805)"))
    )
    (comp (ref "R222")
      (value "2702")
      (footprint "eagle-import:R0805")
      (fields (field (name "MPN") "RC0805JR-074K7L"))
      (libsource (lib "eagle-import") (part "SMD-RES-4.7K-5%-1/8W(0805)"))
    )
    (comp (ref "R223")
      (value "2702")
      (footprint "eagle-import:R0805")
      (fields (field (name "MPN") "RC0805JR-074K7L"))
      (libsource (lib "eagle-import") (part "SMD-RES-4.7K-5%-1/8W(0805)"))
    )
    (comp (ref "R224")
      (value "1002")
      (footprint "eagle-import:R0805")
      (fields (field (name "MPN") "RC0805FR-0710KL"))
      (libsource (lib "eagle-import") (part "SMD-RES-10K-1%-1/8W(0805)"))
    )
    (comp (ref "R225")
      (value "104")
      (footprint "eagle-import:R0805")
      (fields (field (name "MPN") "RC0805FR-0710KL"))
      (libsource (lib "eagle-import") (part "SMD-RES-10K-1%-1/8W(0805)"))
    )
    (comp (ref "R226")
      (value "4701")
      (footprint "eagle-import:R0805")
      (fields (field (name "MPN") "RC0805JR-074K7L"))
      (libsource (lib "eagle-import") (part "SMD-RES-4.7K-5%-1/8W(0805)"))
    )
    (comp (ref "R227")
      (value "47")
      (footprint "eagle-import:V235_17_1MM")
      (libsource (lib "eagle-import") (part "R-EU_V235/17_1MM"))
    )
    (comp (ref "R228")
      (value "102")
      (footprint "eagle-import:R0805")
      (fields (field (name "MPN") "RC0805JR-071KL"))
      (libsource (lib "eagle-import") (part "SMD-RES-1K-5%-1/8W(0805)"))
    )
    (comp (ref "R229")
      (value "47")
      (footprint "eagle-import:V235_17_1MM")
      (libsource (lib "eagle-import") (part "R-EU_V235/17_1MM"))
    )
    (comp (ref "R230")
      (value "104")
      (footprint "eagle-import:R0805")
      (fields (field (name "MPN") "RC0805FR-0710KL"))
      (libsource (lib "eagle-import") (part "SMD-RES-10K-1%-1/8W(0805)"))
    )
    (comp (ref "R231")
      (value "1502")
      (footprint "eagle-import:R0805")
      (fields (field (name "MPN") "RC0805FR-0710KL"))
      (libsource (lib "eagle-import") (part "SMD-RES-10K-1%-1/8W(0805)"))
    )
    (comp (ref "R232")
      (value "1002")
      (footprint "eagle-import:R0805")
      (fields (field (name "MPN") "RC0805FR-0710KL"))
      (libsource (lib "eagle-import") (part "SMD-RES-10K-1%-1/8W(0805)"))
    )
    (comp (ref "R233")
      (value "2201")
      (footprint "eagle-import:R0805")
      (fields (field (name "MPN") "RC0805JR-072K2L"))
      (libsource (lib "eagle-import") (part "SMD-RES-2.2K-5%-1/8W(0805)"))
    )
    (comp (ref "R234")
      (value "13")
      (footprint "eagle-import:R1206")
      (fields (field (name "MPN") "RC1206JR-0713RL"))
      (libsource (lib "eagle-import") (part "SMD-RES-13R-5%-1/4W(1206)"))
    )
    (comp (ref "R235")
      (value "104")
      (footprint "eagle-import:R0805")
      (fields (field (name "MPN") "RC0805FR-0710KL"))
      (libsource (lib "eagle-import") (part "SMD-RES-10K-1%-1/8W(0805)"))
    )
    (comp (ref "R236")
      (value "47")
      (footprint "eagle-import:V235_17_1MM")
      (libsource (lib "eagle-import") (part "R-EU_V235/17_1MM"))
    )
    (comp (ref "R237")
      (value "47")
      (footprint "eagle-import:V235_17_1MM")
      (libsource (lib "eagle-import") (part "R-EU_V235/17_1MM"))
    )
    (comp (ref "R238")
      (value "100")
      (footprint "eagle-import:R0805")
      (fields (field (name "MPN") "RC0805JR-072K2L"))
      (libsource (lib "eagle-import") (part "SMD-RES-2.2K-5%-1/8W(0805)"))
    )
    (comp (ref "R239")
      (value "(101)")
      (footprint "eagle-import:R0805")
      (fields (field (name "MPN") "RC0805JR-072K2L"))
      (libsource (lib "eagle-import") (part "SMD-RES-2.2K-5%-1/8W(0805)"))
    )
    (comp (ref "R240")
      (value "2702")
      (footprint "eagle-import:R0805")
      (fields (field (name "MPN") "RC0805FR-0710KL"))
      (libsource (lib "eagle-import") (part "SMD-RES-10K-1%-1/8W(0805)"))
    )
    (comp (ref "R241")
      (value "104")
      (footprint "eagle-import:R0805")
      (fields (field (name "MPN") "RC0805FR-0710KL"))
      (libsource (lib "eagle-import") (part "SMD-RES-10K-1%-1/8W(0805)"))
    )
    (comp (ref "R242")
      (value "(1000)")
      (footprint "eagle-import:R0805")
      (fields (field (name "MPN") "RC0805JR-07100RL"))
      (libsource (lib "eagle-import") (part "SMD-RES-100R-5%-1/8W(0805)"))
    )
    (comp (ref "R243")
      (value "(101)")
      (footprint "eagle-import:R0805")
      (fields (field (name "MPN") "RC0805JR-07100RL"))
      (libsource (lib "eagle-import") (part "SMD-RES-100R-5%-1/8W(0805)"))
    )
    (comp (ref "R244")
      (value "(1002)")
      (footprint "eagle-import:R0805")
      (fields (field (name "MPN") "RC0805FR-0710KL"))
      (libsource (lib "eagle-import") (part "SMD-RES-10K-1%-1/8W(0805)"))
    )
    (comp (ref "R245")
      (value "2702")
      (footprint "eagle-import:R0805")
      (fields (field (name "MPN") "RC0805JR-074K7L"))
      (libsource (lib "eagle-import") (part "SMD-RES-4.7K-5%-1/8W(0805)"))
    )
    (comp (ref "R246")
      (value "(1002)")
      (footprint "eagle-import:R0805")
      (fields (field (name "MPN") "RC0805JR-074K7L"))
      (libsource (lib "eagle-import") (part "SMD-RES-4.7K-5%-1/8W(0805)"))
    )
    (comp (ref "SJ201")
      (value "SJ")
      (footprint "eagle-import:SJ")
      (libsource (lib "eagle-import") (part "SJ"))
    )
    (comp (ref "START201")
      (value "TPSB2.0")
      (footprint "eagle-import:B2.0")
      (libsource (lib "eagle-import") (part "TPSB2.0"))
    )
    (comp (ref "TP14")
      (value "TPSB2.0")
      (footprint "eagle-import:B2.0")
      (libsource (lib "eagle-import") (part "TPSB2.0"))
    )
    (comp (ref "TP15")
      (value "TPSB2.0")
      (footprint "eagle-import:B2.0")
      (libsource (lib "eagle-import") (part "TPSB2.0"))
    )
    (comp (ref "TP20")
      (value "TPSB2.0")
      (footprint "eagle-import:B2.0")
      (libsource (lib "eagle-import") (part "TPSB2.0"))
    )
    (comp (ref "TP27")
      (value "TPSB2.0")
      (footprint "eagle-import:B2.0")
      (libsource (lib "eagle-import") (part "TPSB2.0"))
    )
    (comp (ref "TP28")
      (value "TPSB2.0")
      (footprint "eagle-import:B2.0")
      (libsource (lib "eagle-import") (part "TPSB2.0"))
    )
    (comp (ref "TP29")
      (value "TPSB2.0")
      (footprint "eagle-import:B2.0")
      (libsource (lib "eagle-import") (part "TPSB2.0"))
    )
    (comp (ref "TP30")
      (value "TPSB2.0")
      (footprint "eagle-import:B2.0")
      (libsource (lib "eagle-import") (part "TPSB2.0"))
    )
    (comp (ref "TP31")
      (value "TPSB2.0")
      (footprint "eagle-import:B2.0")
      (libsource (lib "eagle-import") (part "TPSB2.0"))
    )
    (comp (ref "TP32")
      (value "TPSB2.0")
      (footprint "eagle-import:B2.0")
      (libsource (lib "eagle-import") (part "TPSB2.0"))
    )
    (comp (ref "TP33")
      (value "TPSB2.0")
      (footprint "eagle-import:B2.0")
      (libsource (lib "eagle-import") (part "TPSB2.0"))
    )
    (comp (ref "TP34")
      (value "TPSB2.0")
      (footprint "eagle-import:B2.0")
      (libsource (lib "eagle-import") (part "TPSB2.0"))
    )
    (comp (ref "TP35")
      (value "TPSB2.0")
      (footprint "eagle-import:B2.0")
      (libsource (lib "eagle-import") (part "TPSB2.0"))
    )
    (comp (ref "TP36")
      (value "TPSB2.0")
      (footprint "eagle-import:B2.0")
      (libsource (lib "eagle-import") (part "TPSB2.0"))
    )
    (comp (ref "TP37")
      (value "TPSB2.0")
      (footprint "eagle-import:B2.0")
      (libsource (lib "eagle-import") (part "TPSB2.0"))
    )
    (comp (ref "TP38")
      (value "TPSB2.0")
      (footprint "eagle-import:B2.0")
      (libsource (lib "eagle-import") (part "TPSB2.0"))
    )
    (comp (ref "TP39")
      (value "TPSB2.0")
      (footprint "eagle-import:B2.0")
      (libsource (lib "eagle-import") (part "TPSB2.0"))
    )
    (comp (ref "TP40")
      (value "TPSB2.0")
      (footprint "eagle-import:B2.0")
      (libsource (lib "eagle-import") (part "TPSB2.0"))
    )
    (comp (ref "TP41")
      (value "TPSB2.0")
      (footprint "eagle-import:B2.0")
      (libsource (lib "eagle-import") (part "TPSB2.0"))
    )
    (comp (ref "TP42")
      (value "TPSB1,27")
      (footprint "eagle-import:B1,27")
      (libsource (lib "eagle-import") (part "TPSB1,27"))
    )
    (comp (ref "TP43")
      (value "TPSB2.0")
      (footprint "eagle-import:B2.0")
      (libsource (lib "eagle-import") (part "TPSB2.0"))
    )
    (comp (ref "TP44")
      (value "TPSB2.0")
      (footprint "eagle-import:B2.0")
      (libsource (lib "eagle-import") (part "TPSB2.0"))
    )
    (comp (ref "TP45")
      (value "TPSB2.0")
      (footprint "eagle-import:B2.0")
      (libsource (lib "eagle-import") (part "TPSB2.0"))
    )
    (comp (ref "TP46")
      (value "TPSB2.0")
      (footprint "eagle-import:B2.0")
      (libsource (lib "eagle-import") (part "TPSB2.0"))
    )
    (comp (ref "X201")
      (value "CON_BMWV2")
      (footprint "eagle-import:24-PIN_V2")
      (libsource (lib "eagle-import") (part "CON_BMWV2"))
    )
    (comp (ref "X202")
      (value "22-23-2021")
      (footprint "eagle-import:22-23-2021")
      (fields (field (name "MF") "MOLEX"))
      (libsource (lib "eagle-import") (part "22-23-2021"))
    )
    (comp (ref "X203")
      (value "22-23-2051")
      (footprint "eagle-import:22-23-2051")
      (fields (field (name "MF") "MOLEX"))
      (libsource (lib "eagle-import") (part "22-23-2051"))
    )
    (comp (ref "6V6")
      (value "TPSB2.0")
      (footprint "eagle-import:B2.0")
      (libsource (lib "eagle-import") (part "TPSB2.0"))
    )
    (comp (ref "10V6")
      (value "TPSB2.0")
      (footprint "eagle-import:B2.0")
      (libsource (lib "eagle-import") (part "TPSB2.0"))
    )
    (comp (ref "23")
      (value "2081-1132")
      (footprint "eagle-import:12-PIN")
      (libsource (lib "eagle-import") (part "2081-1132"))
    )
    (comp (ref "24")
      (value "2081-1132")
      (footprint "eagle-import:12-PIN")
      (libsource (lib "eagle-import") (part "2081-1132"))
    )
    (comp (ref "C51")
      (value "100u")
      (footprint "eagle-import:C1206")
      (fields (field (name "MPN") "GRM31CR60J107ME39L"))
      (libsource (lib "eagle-import") (part "CERAMIC-100UF-6.3V-20%-X5R(1206)"))
    )
    (comp (ref "C52")
      (value "100u")
      (footprint "eagle-import:C1206")
      (fields (field (name "MPN") "GRM31CR60J107ME39L"))
      (libsource (lib "eagle-import") (part "CERAMIC-100UF-6.3V-20%-X5R(1206)"))
    )
    (comp (ref "C53")
      (value "100nF,")
      (footprint "eagle-import:C0805")
      (fields (field (name "MPN") "CC0805KRX7R9BB104"))
      (libsource (lib "eagle-import") (part "CERAMIC-100NF-50V-10%-X7R(0805)"))
    )
    (comp (ref "C54")
      (value "4.7u")
      (footprint "eagle-import:C0805")
      (fields (field (name "MPN") "CC0805KKX5R8BB475"))
      (libsource (lib "eagle-import") (part "CERAMIC-4.7UF-25V-10%-X5R(0805)"))
    )
    (comp (ref "C55")
      (value "100nF.")
      (footprint "eagle-import:C0805")
      (fields (field (name "MPN") "CC0805KRX7R9BB104"))
      (libsource (lib "eagle-import") (part "CERAMIC-100NF-50V-10%-X7R(0805)"))
    )
    (comp (ref "C56")
      (value "100nF.")
      (footprint "eagle-import:C0805")
      (fields (field (name "MPN") "CC0805KRX7R9BB104"))
      (libsource (lib "eagle-import") (part "CERAMIC-100NF-50V-10%-X7R(0805)"))
    )
    (comp (ref "C57")
      (value "2.2nF")
      (footprint "eagle-import:C0805")
      (fields (field (name "MPN") "CC0805KRX7R9BB104"))
      (libsource (lib "eagle-import") (part "CERAMIC-100NF-50V-10%-X7R(0805)"))
    )
    (comp (ref "C58")
      (value "100nF")
      (footprint "eagle-import:C0805")
      (fields (field (name "MPN") "CC0805KRX7R9BB104"))
      (libsource (lib "eagle-import") (part "CERAMIC-100NF-50V-10%-X7R(0805)"))
    )
    (comp (ref "C59")
      (value "100nF")
      (footprint "eagle-import:C0805")
      (fields (field (name "MPN") "CC0805KRX7R9BB104"))
      (libsource (lib "eagle-import") (part "CERAMIC-100NF-50V-10%-X7R(0805)"))
    )
    (comp (ref "C60")
      (value "100nF,")
      (footprint "eagle-import:C0805")
      (fields (field (name "MPN") "CC0805KRX7R9BB104"))
      (libsource (lib "eagle-import") (part "CERAMIC-100NF-50V-10%-X7R(0805)"))
    )
    (comp (ref "D56")
      (value "1N4007")
      (footprint "eagle-import:DO-214AC")
      (libsource (lib "eagle-import") (part "DIODE-GEN-PURPOSE-1KV-1A(DO-214AC)"))
    )
    (comp (ref "D57")
      (value "1N4007,")
      (footprint "eagle-import:DO-214AC")
      (fields (field (name "MPN") "1N4007"))
      (libsource (lib "eagle-import") (part "DIODE-GEN-PURPOSE-1KV-1A(DO-214AC)"))
    )
    (comp (ref "D58")
      (value "1N4007,")
      (footprint "eagle-import:DO-214AC")
      (fields (field (name "MPN") "1N4007"))
      (libsource (lib "eagle-import") (part "DIODE-GEN-PURPOSE-1KV-1A(DO-214AC)"))
    )
    (comp (ref "D59")
      (value "1N4007.")
      (footprint "eagle-import:DO-214AC")
      (fields (field (name "MPN") "1N4007"))
      (libsource (lib "eagle-import") (part "DIODE-GEN-PURPOSE-1KV-1A(DO-214AC)"))
    )
    (comp (ref "D60")
      (value "1N5817")
      (footprint "eagle-import:DO-214AC_SLIM")
      (libsource (lib "eagle-import") (part "DIODE-GEN-PURPOSE-1KV-1A(DO-214AC)DO-214AC/1206"))
    )
    (comp (ref "D61")
      (value "1N5817.")
      (footprint "eagle-import:DO-214AC_SLIM")
      (libsource (lib "eagle-import") (part "DIODE-GEN-PURPOSE-1KV-1A(DO-214AC)DO-214AC/1206"))
    )
    (comp (ref "D62")
      (value "1N5817.")
      (footprint "eagle-import:DO-214AC_SLIM")
      (libsource (lib "eagle-import") (part "DIODE-GEN-PURPOSE-1KV-1A(DO-214AC)DO-214AC/1206"))
    )
    (comp (ref "D63")
      (value "1N5817")
      (footprint "eagle-import:DO-214AC_SLIM")
      (libsource (lib "eagle-import") (part "DIODE-GEN-PURPOSE-1KV-1A(DO-214AC)DO-214AC/1206"))
    )
    (comp (ref "D64")
      (value "1N4007.")
      (footprint "eagle-import:DO-214AC")
      (fields (field (name "MPN") "1N4007"))
      (libsource (lib "eagle-import") (part "DIODE-GEN-PURPOSE-1KV-1A(DO-214AC)"))
    )
    (comp (ref "D65")
      (value "1N4007")
      (footprint "eagle-import:DO-214AC")
      (libsource (lib "eagle-import") (part "DIODE-GEN-PURPOSE-1KV-1A(DO-214AC)"))
    )
    (comp (ref "D66")
      (value "SM6T")
      (footprint "eagle-import:DO214AA")
      (libsource (lib "eagle-import") (part "SM6T"))
    )
    (comp (ref "FID23")
      (value "FIDUCIAL")
      (footprint "eagle-import:FIDUCIAL_1MM")
      (libsource (lib "eagle-import") (part "FIDUCIAL"))
    )
    (comp (ref "FID24")
      (value "FIDUCIAL")
      (footprint "eagle-import:FIDUCIAL_1MM")
      (libsource (lib "eagle-import") (part "FIDUCIAL"))
    )
    (comp (ref "FID25")
      (value "FIDUCIAL")
      (footprint "eagle-import:FIDUCIAL_1MM")
      (libsource (lib "eagle-import") (part "FIDUCIAL"))
    )
    (comp (ref "FID26")
      (value "FIDUCIAL")
      (footprint "eagle-import:FIDUCIAL_1MM")
      (libsource (lib "eagle-import") (part "FIDUCIAL"))
    )
    (comp (ref "IC51")
      (value "4028")
      (footprint "eagle-import:SO16")
      (libsource (lib "eagle-import") (part "4028D"))
    )
    (comp (ref "IC52")
      (value "6V pos")
      (footprint "eagle-import:78LXX")
      (libsource (lib "eagle-import") (part "v-reg_78LXX"))
    )
    (comp (ref "IC53")
      (value "317TO202H_NOHOLE")
      (footprint "eagle-import:TO220H_NOHOLE")
      (libsource (lib "eagle-import") (part "317TO202H_NOHOLE"))
    )
    (comp (ref "IC54")
      (value "ULN2004")
      (footprint "eagle-import:SO16")
      (libsource (lib "eagle-import") (part "ULN2004AD"))
    )
    (comp (ref "IC55")
      (value "LM339")
      (footprint "eagle-import:SO14")
      (libsource (lib "eagle-import") (part "LM339D"))
    )
    (comp (ref "IC56")
      (value "78L06")
      (footprint "eagle-import:SOT89_ROUND")
      (libsource (lib "eagle-import") (part "78LXXSOT89_ROUND"))
    )
    (comp (ref "IC57")
      (value "555")
      (footprint "eagle-import:SO08")
      (libsource (lib "eagle-import") (part "555DNE"))
    )
    (comp (ref "IC58")
      (value "4538")
      (footprint "eagle-import:SO16")
      (libsource (lib "eagle-import") (part "4538D"))
    )
    (comp (ref "IC59")
      (value "78L10")
      (footprint "eagle-import:SOT89_ROUND")
      (libsource (lib "eagle-import") (part "78LXXSOT89_ROUND"))
    )
    (comp (ref "IC60")
      (value "LM2904")
      (footprint "eagle-import:SO08")
      (libsource (lib "eagle-import") (part "LM358D"))
    )
    (comp (ref "JP26")
      (value "JP2EJP2_SMALLPADS")
      (footprint "eagle-import:JP2_SMALLPADS")
      (libsource (lib "eagle-import") (part "JP2EJP2_SMALLPADS"))
    )
    (comp (ref "JP27")
      (value "JP2E_ORIG")
      (footprint "eagle-import:JP2_ORIG_SMALLPADS")
      (libsource (lib "eagle-import") (part "JP2E_ORIG"))
    )
    (comp (ref "JP28")
      (value "JP2EJP2_SMALLPADS")
      (footprint "eagle-import:JP2_SMALLPADS")
      (libsource (lib "eagle-import") (part "JP2EJP2_SMALLPADS"))
    )
    (comp (ref "JP29")
      (value "JP2EJP2_SMALLPADS")
      (footprint "eagle-import:JP2_SMALLPADS")
      (libsource (lib "eagle-import") (part "JP2EJP2_SMALLPADS"))
    )
    (comp (ref "JP30")
      (value "JP2EJP2_SMALLPADS")
      (footprint "eagle-import:JP2_SMALLPADS")
      (libsource (lib "eagle-import") (part "JP2EJP2_SMALLPADS"))
    )
    (comp (ref "LED31")
      (value "LEDLD260")
      (footprint "eagle-import:LD260")
      (libsource (lib "eagle-import") (part "LEDLD260"))
    )
    (comp (ref "LED32")
      (value "LEDLD260")
      (footprint "eagle-import:LD260")
      (libsource (lib "eagle-import") (part "LEDLD260"))
    )
    (comp (ref "LED33")
      (value "LEDLD260")
      (footprint "eagle-import:LD260")
      (libsource (lib "eagle-import") (part "LEDLD260"))
    )
    (comp (ref "LED34")
      (value "LEDLD260")
      (footprint "eagle-import:LD260")
      (libsource (lib "eagle-import") (part "LEDLD260"))
    )
    (comp (ref "LED35")
      (value "LEDLD260")
      (footprint "eagle-import:LD260")
      (libsource (lib "eagle-import") (part "LEDLD260"))
    )
    (comp (ref "LED36")
      (value "LEDLD260")
      (footprint "eagle-import:LD260")
      (libsource (lib "eagle-import") (part "LEDLD260"))
    )
    (comp (ref "Q36")
      (value "BA")
      (footprint "eagle-import:SOT89")
      (libsource (lib "eagle-import") (part "PNP-TRANSISTOR_SOT89"))
    )
    (comp (ref "Q37")
      (value "BA.")
      (footprint "eagle-import:SOT89")
      (libsource (lib "eagle-import") (part "PNP-TRANSISTOR_SOT89"))
    )
    (comp (ref "Q38")
      (value "BA.")
      (footprint "eagle-import:SOT89")
      (libsource (lib "eagle-import") (part "PNP-TRANSISTOR_SOT89"))
    )
    (comp (ref "Q39")
      (value "BA")
      (footprint "eagle-import:SOT89")
      (libsource (lib "eagle-import") (part "PNP-TRANSISTOR_SOT89"))
    )
    (comp (ref "Q40")
      (value "MY")
      (footprint "eagle-import:SOT89")
      (libsource (lib "eagle-import") (part "NPN-TRANSISTOR_SOT89"))
    )
    (comp (ref "Q41")
      (value "J1")
      (footprint "eagle-import:SOT-23")
      (fields (field (name "MPN") "BSS138W-7-F"))
      (libsource (lib "eagle-import") (part "SMD-MOSFET-N-CH-50V-200MA-BSS138W-7-F(SOT-23)"))
    )
    (comp (ref "Q42")
      (value "J1")
      (footprint "eagle-import:SOT-23")
      (fields (field (name "MPN") "BSS138W-7-F"))
      (libsource (lib "eagle-import") (part "SMD-MOSFET-N-CH-50V-200MA-BSS138W-7-F(SOT-23)"))
    )
    (comp (ref "R361")
      (value "47")
      (footprint "eagle-import:V235_17_1MM")
      (libsource (lib "eagle-import") (part "R-EU_V235/17_1MM"))
    )
    (comp (ref "R362")
      (value "13")
      (footprint "eagle-import:R1206")
      (fields (field (name "MPN") "RC1206JR-0713RL"))
      (libsource (lib "eagle-import") (part "SMD-RES-13R-5%-1/4W(1206)"))
    )
    (comp (ref "R363")
      (value "47")
      (footprint "eagle-import:V235_17_1MM")
      (libsource (lib "eagle-import") (part "R-EU_V235/17_1MM"))
    )
    (comp (ref "R364")
      (value "104")
      (footprint "eagle-import:R0805")
      (fields (field (name "MPN") "RC0805FR-0710KL"))
      (libsource (lib "eagle-import") (part "SMD-RES-10K-1%-1/8W(0805)"))
    )
    (comp (ref "R365")
      (value "104")
      (footprint "eagle-import:R0805")
      (fields (field (name "MPN") "RC0805FR-0710KL"))
      (libsource (lib "eagle-import") (part "SMD-RES-10K-1%-1/8W(0805)"))
    )
    (comp (ref "R366")
      (value "104")
      (footprint "eagle-import:R0805")
      (fields (field (name "MPN") "RC0805FR-0710KL"))
      (libsource (lib "eagle-import") (part "SMD-RES-10K-1%-1/8W(0805)"))
    )
    (comp (ref "R367")
      (value "4701")
      (footprint "eagle-import:R0805")
      (fields (field (name "MPN") "RC0805JR-074K7L"))
      (libsource (lib "eagle-import") (part "SMD-RES-4.7K-5%-1/8W(0805)"))
    )
    (comp (ref "R368")
      (value "1002")
      (footprint "eagle-import:R0805")
      (fields (field (name "MPN") "RC0805FR-0710KL"))
      (libsource (lib "eagle-import") (part "SMD-RES-10K-1%-1/8W(0805)"))
    )
    (comp (ref "R369")
      (value "1002")
      (footprint "eagle-import:R0805")
      (fields (field (name "MPN") "RC0805FR-0710KL"))
      (libsource (lib "eagle-import") (part "SMD-RES-10K-1%-1/8W(0805)"))
    )
    (comp (ref "R370")
      (value "1502")
      (footprint "eagle-import:R0805")
      (fields (field (name "MPN") "RC0805FR-0710KL"))
      (libsource (lib "eagle-import") (part "SMD-RES-10K-1%-1/8W(0805)"))
    )
    (comp (ref "R371")
      (value "104")
      (footprint "eagle-import:R0805")
      (fields (field (name "MPN") "RC0805FR-0710KL"))
      (libsource (lib "eagle-import") (part "SMD-RES-10K-1%-1/8W(0805)"))
    )
    (comp (ref "R372")
      (value "104")
      (footprint "eagle-import:R0805")
      (fields (field (name "MPN") "RC0805FR-0710KL"))
      (libsource (lib "eagle-import") (part "SMD-RES-10K-1%-1/8W(0805)"))
    )
    (comp (ref "R373")
      (value "1502")
      (footprint "eagle-import:R0805")
      (fields (field (name "MPN") "RC0805FR-0710KL"))
      (libsource (lib "eagle-import") (part "SMD-RES-10K-1%-1/8W(0805)"))
    )
    (comp (ref "R374")
      (value "1002")
      (footprint "eagle-import:R0805")
      (fields (field (name "MPN") "RC0805FR-0710KL"))
      (libsource (lib "eagle-import") (part "SMD-RES-10K-1%-1/8W(0805)"))
    )
    (comp (ref "R375")
      (value "2201")
      (footprint "eagle-import:R0805")
      (fields (field (name "MPN") "RC0805JR-072K2L"))
      (libsource (lib "eagle-import") (part "SMD-RES-2.2K-5%-1/8W(0805)"))
    )
    (comp (ref "R376")
      (value "1002")
      (footprint "eagle-import:R0805")
      (fields (field (name "MPN") "RC0805FR-0710KL"))
      (libsource (lib "eagle-import") (part "SMD-RES-10K-1%-1/8W(0805)"))
    )
    (comp (ref "R377")
      (value "4701")
      (footprint "eagle-import:R0805")
      (fields (field (name "MPN") "RC0805JR-074K7L"))
      (libsource (lib "eagle-import") (part "SMD-RES-4.7K-5%-1/8W(0805)"))
    )
    (comp (ref "R378")
      (value "2702")
      (footprint "eagle-import:R0805")
      (fields (field (name "MPN") "RC0805JR-074K7L"))
      (libsource (lib "eagle-import") (part "SMD-RES-4.7K-5%-1/8W(0805)"))
    )
    (comp (ref "R379")
      (value "102")
      (footprint "eagle-import:R0805")
      (fields (field (name "MPN") "RC0805JR-071KL"))
      (libsource (lib "eagle-import") (part "SMD-RES-1K-5%-1/8W(0805)"))
    )
    (comp (ref "R380")
      (value "100")
      (footprint "eagle-import:R0805")
      (fields (field (name "MPN") "RC0805JR-07220RL"))
      (libsource (lib "eagle-import") (part "SMD-RES-220R-5%-1/8W(0805)"))
    )
    (comp (ref "R381")
      (value "(101)")
      (footprint "eagle-import:R0805")
      (fields (field (name "MPN") "RC0805JR-07100RL"))
      (libsource (lib "eagle-import") (part "SMD-RES-100R-5%-1/8W(0805)"))
    )
    (comp (ref "R382")
      (value "(1000)")
      (footprint "eagle-import:R0805")
      (fields (field (name "MPN") "RC0805JR-07100RL"))
      (libsource (lib "eagle-import") (part "SMD-RES-100R-5%-1/8W(0805)"))
    )
    (comp (ref "R383")
      (value "102")
      (footprint "eagle-import:R0805")
      (fields (field (name "MPN") "RC0805JR-071KL"))
      (libsource (lib "eagle-import") (part "SMD-RES-1K-5%-1/8W(0805)"))
    )
    (comp (ref "R384")
      (value "13")
      (footprint "eagle-import:R1206")
      (fields (field (name "MPN") "RC1206JR-0713RL"))
      (libsource (lib "eagle-import") (part "SMD-RES-13R-5%-1/4W(1206)"))
    )
    (comp (ref "R385")
      (value "13")
      (footprint "eagle-import:R1206")
      (fields (field (name "MPN") "RC1206JR-0713RL"))
      (libsource (lib "eagle-import") (part "SMD-RES-13R-5%-1/4W(1206)"))
    )
    (comp (ref "R386")
      (value "2702")
      (footprint "eagle-import:R0805")
      (fields (field (name "MPN") "RC0805JR-074K7L"))
      (libsource (lib "eagle-import") (part "SMD-RES-4.7K-5%-1/8W(0805)"))
    )
    (comp (ref "R387")
      (value "4701")
      (footprint "eagle-import:R0805")
      (fields (field (name "MPN") "RC0805JR-074K7L"))
      (libsource (lib "eagle-import") (part "SMD-RES-4.7K-5%-1/8W(0805)"))
    )
    (comp (ref "R388")
      (value "100")
      (footprint "eagle-import:R0805")
      (fields (field (name "MPN") "RC0805JR-072K2L"))
      (libsource (lib "eagle-import") (part "SMD-RES-2.2K-5%-1/8W(0805)"))
    )
    (comp (ref "R389")
      (value "(101)")
      (footprint "eagle-import:R0805")
      (fields (field (name "MPN") "RC0805JR-072K2L"))
      (libsource (lib "eagle-import") (part "SMD-RES-2.2K-5%-1/8W(0805)"))
    )
    (comp (ref "R390")
      (value "104")
      (footprint "eagle-import:R0805")
      (fields (field (name "MPN") "RC0805FR-0710KL"))
      (libsource (lib "eagle-import") (part "SMD-RES-10K-1%-1/8W(0805)"))
    )
    (comp (ref "R391")
      (value "104")
      (footprint "eagle-import:R0805")
      (fields (field (name "MPN") "RC0805FR-0710KL"))
      (libsource (lib "eagle-import") (part "SMD-RES-10K-1%-1/8W(0805)"))
    )
    (comp (ref "R392")
      (value "(1002)")
      (footprint "eagle-import:R0805")
      (fields (field (name "MPN") "RC0805FR-0710KL"))
      (libsource (lib "eagle-import") (part "SMD-RES-10K-1%-1/8W(0805)"))
    )
    (comp (ref "R393")
      (value "2702")
      (footprint "eagle-import:R0805")
      (fields (field (name "MPN") "RC0805FR-0710KL"))
      (libsource (lib "eagle-import") (part "SMD-RES-10K-1%-1/8W(0805)"))
    )
    (comp (ref "R394")
      (value "47")
      (footprint "eagle-import:V235_17_1MM")
      (libsource (lib "eagle-import") (part "R-EU_V235/17_1MM"))
    )
    (comp (ref "R395")
      (value "47")
      (footprint "eagle-import:V235_17_1MM")
      (libsource (lib "eagle-import") (part "R-EU_V235/17_1MM"))
    )
    (comp (ref "R396")
      (value "2702")
      (footprint "eagle-import:R0805")
      (fields (field (name "MPN") "RC0805JR-074K7L"))
      (libsource (lib "eagle-import") (part "SMD-RES-4.7K-5%-1/8W(0805)"))
    )
    (comp (ref "R397")
      (value "2201")
      (footprint "eagle-import:R0805")
      (fields (field (name "MPN") "RC0805JR-072K2L"))
      (libsource (lib "eagle-import") (part "SMD-RES-2.2K-5%-1/8W(0805)"))
    )
    (comp (ref "R398")
      (value "(1002)")
      (footprint "eagle-import:R0805")
      (fields (field (name "MPN") "RC0805JR-074K7L"))
      (libsource (lib "eagle-import") (part "SMD-RES-4.7K-5%-1/8W(0805)"))
    )
    (comp (ref "R399")
      (value "1002")
      (footprint "eagle-import:R0805")
      (fields (field (name "MPN") "RC0805FR-0710KL"))
      (libsource (lib "eagle-import") (part "SMD-RES-10K-1%-1/8W(0805)"))
    )
    (comp (ref "R400")
      (value "102")
      (footprint "eagle-import:R0805")
      (fields (field (name "MPN") "RC0805JR-071KL"))
      (libsource (lib "eagle-import") (part "SMD-RES-1K-5%-1/8W(0805)"))
    )
    (comp (ref "R404")
      (value "2702")
      (footprint "eagle-import:R0805")
      (fields (field (name "MPN") "RC0805JR-074K7L"))
      (libsource (lib "eagle-import") (part "SMD-RES-4.7K-5%-1/8W(0805)"))
    )
    (comp (ref "R447")
      (value "102")
      (footprint "eagle-import:R0805")
      (fields (field (name "MPN") "RC0805JR-071KL"))
      (libsource (lib "eagle-import") (part "SMD-RES-1K-5%-1/8W(0805)"))
    )
    (comp (ref "R448")
      (value "102")
      (footprint "eagle-import:R0805")
      (fields (field (name "MPN") "RC0805JR-071KL"))
      (libsource (lib "eagle-import") (part "SMD-RES-1K-5%-1/8W(0805)"))
    )
    (comp (ref "R449")
      (value "13")
      (footprint "eagle-import:R1206")
      (fields (field (name "MPN") "RC1206JR-0713RL"))
      (libsource (lib "eagle-import") (part "SMD-RES-13R-5%-1/4W(1206)"))
    )
    (comp (ref "R450")
      (value "R_user")
      (footprint "eagle-import:R0805")
      (libsource (lib "eagle-import") (part "R-EU_R0805"))
    )
    (comp (ref "SJ6") (value "SJ") (footprint "eagle-import:SJ") (libsource (lib "eagle-import") (part "SJ")))
    (comp (ref "START6")
      (value "TPSB2.0")
      (footprint "eagle-import:B2.0")
      (libsource (lib "eagle-import") (part "TPSB2.0"))
    )
    (comp (ref "TP254")
      (value "TPSB2.0")
      (footprint "eagle-import:B2.0")
      (libsource (lib "eagle-import") (part "TPSB2.0"))
    )
    (comp (ref "TP255")
      (value "TPSB2.0")
      (footprint "eagle-import:B2.0")
      (libsource (lib "eagle-import") (part "TPSB2.0"))
    )
    (comp (ref "TP256")
      (value "TPSB2.0")
      (footprint "eagle-import:B2.0")
      (libsource (lib "eagle-import") (part "TPSB2.0"))
    )
    (comp (ref "TP257")
      (value "TPSB2.0")
      (footprint "eagle-import:B2.0")
      (libsource (lib "eagle-import") (part "TPSB2.0"))
    )
    (comp (ref "TP258")
      (value "TPSB2.0")
      (footprint "eagle-import:B2.0")
      (libsource (lib "eagle-import") (part "TPSB2.0"))
    )
    (comp (ref "TP259")
      (value "TPSB2.0")
      (footprint "eagle-import:B2.0")
      (libsource (lib "eagle-import") (part "TPSB2.0"))
    )
    (comp (ref "TP260")
      (value "TPSB2.0")
      (footprint "eagle-import:B2.0")
      (libsource (lib "eagle-import") (part "TPSB2.0"))
    )
    (comp (ref "TP261")
      (value "TPSB2.0")
      (footprint "eagle-import:B2.0")
      (libsource (lib "eagle-import") (part "TPSB2.0"))
    )
    (comp (ref "TP262")
      (value "TPSB2.0")
      (footprint "eagle-import:B2.0")
      (libsource (lib "eagle-import") (part "TPSB2.0"))
    )
    (comp (ref "TP263")
      (value "TPSB2.0")
      (footprint "eagle-import:B2.0")
      (libsource (lib "eagle-import") (part "TPSB2.0"))
    )
    (comp (ref "TP264")
      (value "TPSB2.0")
      (footprint "eagle-import:B2.0")
      (libsource (lib "eagle-import") (part "TPSB2.0"))
    )
    (comp (ref "TP265")
      (value "TPSB2.0")
      (footprint "eagle-import:B2.0")
      (libsource (lib "eagle-import") (part "TPSB2.0"))
    )
    (comp (ref "TP266")
      (value "TPSB2.0")
      (footprint "eagle-import:B2.0")
      (libsource (lib "eagle-import") (part "TPSB2.0"))
    )
    (comp (ref "TP267")
      (value "TPSB2.0")
      (footprint "eagle-import:B2.0")
      (libsource (lib "eagle-import") (part "TPSB2.0"))
    )
    (comp (ref "TP268")
      (value "TPSB2.0")
      (footprint "eagle-import:B2.0")
      (libsource (lib "eagle-import") (part "TPSB2.0"))
    )
    (comp (ref "TP269")
      (value "TPSB2.0")
      (footprint "eagle-import:B2.0")
      (libsource (lib "eagle-import") (part "TPSB2.0"))
    )
    (comp (ref "TP270")
      (value "TPSB2.0")
      (footprint "eagle-import:B2.0")
      (libsource (lib "eagle-import") (part "TPSB2.0"))
    )
    (comp (ref "TP271")
      (value "TPSB2.0")
      (footprint "eagle-import:B2.0")
      (libsource (lib "eagle-import") (part "TPSB2.0"))
    )
    (comp (ref "TP272")
      (value "TPSB1,27")
      (footprint "eagle-import:B1,27")
      (libsource (lib "eagle-import") (part "TPSB1,27"))
    )
    (comp (ref "TP273")
      (value "TPSB2.0")
      (footprint "eagle-import:B2.0")
      (libsource (lib "eagle-import") (part "TPSB2.0"))
    )
    (comp (ref "TP274")
      (value "TPSB2.0")
      (footprint "eagle-import:B2.0")
      (libsource (lib "eagle-import") (part "TPSB2.0"))
    )
    (comp (ref "TP275")
      (value "TPSB2.0")
      (footprint "eagle-import:B2.0")
      (libsource (lib "eagle-import") (part "TPSB2.0"))
    )
    (comp (ref "TP276")
      (value "TPSB2.0")
      (footprint "eagle-import:B2.0")
      (libsource (lib "eagle-import") (part "TPSB2.0"))
    )
    (comp (ref "X16")
      (value "CON_BMWV2")
      (footprint "eagle-import:24-PIN_V2")
      (libsource (lib "eagle-import") (part "CON_BMWV2"))
    )
    (comp (ref "X17")
      (value "22-23-2051")
      (footprint "eagle-import:22-23-2051")
      (fields (field (name "MF") "MOLEX"))
      (libsource (lib "eagle-import") (part "22-23-2051"))
    )
    (comp (ref "X18")
      (value "22-23-2021")
      (footprint "eagle-import:22-23-2021")
      (fields (field (name "MF") "MOLEX"))
      (libsource (lib "eagle-import") (part "22-23-2021"))
    )
    (comp (ref "5")
      (value "2081-1132")
      (footprint "eagle-import:12-PIN")
      (libsource (lib "eagle-import") (part "2081-1132"))
    )
    (comp (ref "6")
      (value "2081-1132")
      (footprint "eagle-import:12-PIN")
      (libsource (lib "eagle-import") (part "2081-1132"))
    )
    (comp (ref "6V301")
      (value "TPSB2.0")
      (footprint "eagle-import:B2.0")
      (libsource (lib "eagle-import") (part "TPSB2.0"))
    )
    (comp (ref "10V301")
      (value "TPSB2.0")
      (footprint "eagle-import:B2.0")
      (libsource (lib "eagle-import") (part "TPSB2.0"))
    )
    (comp (ref "C301")
      (value "4.7u")
      (footprint "eagle-import:C0805")
      (fields (field (name "MPN") "CC0805KKX5R8BB475"))
      (libsource (lib "eagle-import") (part "CERAMIC-4.7UF-25V-10%-X5R(0805)"))
    )
    (comp (ref "C302")
      (value "100nF")
      (footprint "eagle-import:C0805")
      (fields (field (name "MPN") "CC0805KRX7R9BB104"))
      (libsource (lib "eagle-import") (part "CERAMIC-100NF-50V-10%-X7R(0805)"))
    )
    (comp (ref "C303")
      (value "100nF,")
      (footprint "eagle-import:C0805")
      (fields (field (name "MPN") "CC0805KRX7R9BB104"))
      (libsource (lib "eagle-import") (part "CERAMIC-100NF-50V-10%-X7R(0805)"))
    )
    (comp (ref "C304")
      (value "100nF,")
      (footprint "eagle-import:C0805")
      (fields (field (name "MPN") "CC0805KRX7R9BB104"))
      (libsource (lib "eagle-import") (part "CERAMIC-100NF-50V-10%-X7R(0805)"))
    )
    (comp (ref "C305")
      (value "100nF.")
      (footprint "eagle-import:C0805")
      (fields (field (name "MPN") "CC0805KRX7R9BB104"))
      (libsource (lib "eagle-import") (part "CERAMIC-100NF-50V-10%-X7R(0805)"))
    )
    (comp (ref "C306")
      (value "100nF.")
      (footprint "eagle-import:C0805")
      (fields (field (name "MPN") "CC0805KRX7R9BB104"))
      (libsource (lib "eagle-import") (part "CERAMIC-100NF-50V-10%-X7R(0805)"))
    )
    (comp (ref "C307")
      (value "100u")
      (footprint "eagle-import:C1206")
      (fields (field (name "MPN") "GRM31CR60J107ME39L"))
      (libsource (lib "eagle-import") (part "CERAMIC-100UF-6.3V-20%-X5R(1206)"))
    )
    (comp (ref "C308")
      (value "100u")
      (footprint "eagle-import:C1206")
      (fields (field (name "MPN") "GRM31CR60J107ME39L"))
      (libsource (lib "eagle-import") (part "CERAMIC-100UF-6.3V-20%-X5R(1206)"))
    )
    (comp (ref "C309")
      (value "2.2nF")
      (footprint "eagle-import:C0805")
      (fields (field (name "MPN") "CC0805KRX7R9BB104"))
      (libsource (lib "eagle-import") (part "CERAMIC-100NF-50V-10%-X7R(0805)"))
    )
    (comp (ref "C310")
      (value "100nF")
      (footprint "eagle-import:C0805")
      (fields (field (name "MPN") "CC0805KRX7R9BB104"))
      (libsource (lib "eagle-import") (part "CERAMIC-100NF-50V-10%-X7R(0805)"))
    )
    (comp (ref "D301")
      (value "SM6T")
      (footprint "eagle-import:DO214AA")
      (libsource (lib "eagle-import") (part "SM6T"))
    )
    (comp (ref "D302")
      (value "1N4007,")
      (footprint "eagle-import:DO-214AC")
      (fields (field (name "MPN") "1N4007"))
      (libsource (lib "eagle-import") (part "DIODE-GEN-PURPOSE-1KV-1A(DO-214AC)"))
    )
    (comp (ref "D303")
      (value "1N4007,")
      (footprint "eagle-import:DO-214AC")
      (fields (field (name "MPN") "1N4007"))
      (libsource (lib "eagle-import") (part "DIODE-GEN-PURPOSE-1KV-1A(DO-214AC)"))
    )
    (comp (ref "D305")
      (value "1N4007.")
      (footprint "eagle-import:DO-214AC")
      (fields (field (name "MPN") "1N4007"))
      (libsource (lib "eagle-import") (part "DIODE-GEN-PURPOSE-1KV-1A(DO-214AC)"))
    )
    (comp (ref "D306")
      (value "1N4007.")
      (footprint "eagle-import:DO-214AC")
      (fields (field (name "MPN") "1N4007"))
      (libsource (lib "eagle-import") (part "DIODE-GEN-PURPOSE-1KV-1A(DO-214AC)"))
    )
    (comp (ref "D307")
      (value "1N5817")
      (footprint "eagle-import:DO-214AC_SLIM")
      (libsource (lib "eagle-import") (part "DIODE-GEN-PURPOSE-1KV-1A(DO-214AC)DO-214AC/1206"))
    )
    (comp (ref "D308")
      (value "1N5817.")
      (footprint "eagle-import:DO-214AC_SLIM")
      (libsource (lib "eagle-import") (part "DIODE-GEN-PURPOSE-1KV-1A(DO-214AC)DO-214AC/1206"))
    )
    (comp (ref "D309")
      (value "1N5817.")
      (footprint "eagle-import:DO-214AC_SLIM")
      (libsource (lib "eagle-import") (part "DIODE-GEN-PURPOSE-1KV-1A(DO-214AC)DO-214AC/1206"))
    )
    (comp (ref "D310")
      (value "1N5817")
      (footprint "eagle-import:DO-214AC_SLIM")
      (libsource (lib "eagle-import") (part "DIODE-GEN-PURPOSE-1KV-1A(DO-214AC)DO-214AC/1206"))
    )
    (comp (ref "D311")
      (value "1N4007")
      (footprint "eagle-import:DO-214AC")
      (libsource (lib "eagle-import") (part "DIODE-GEN-PURPOSE-1KV-1A(DO-214AC)"))
    )
    (comp (ref "D312")
      (value "1N4007")
      (footprint "eagle-import:DO-214AC")
      (libsource (lib "eagle-import") (part "DIODE-GEN-PURPOSE-1KV-1A(DO-214AC)"))
    )
    (comp (ref "FID301")
      (value "FIDUCIAL")
      (footprint "eagle-import:FIDUCIAL_1MM")
      (libsource (lib "eagle-import") (part "FIDUCIAL"))
    )
    (comp (ref "FID302")
      (value "FIDUCIAL")
      (footprint "eagle-import:FIDUCIAL_1MM")
      (libsource (lib "eagle-import") (part "FIDUCIAL"))
    )
    (comp (ref "FID303")
      (value "FIDUCIAL")
      (footprint "eagle-import:FIDUCIAL_1MM")
      (libsource (lib "eagle-import") (part "FIDUCIAL"))
    )
    (comp (ref "FID304")
      (value "FIDUCIAL")
      (footprint "eagle-import:FIDUCIAL_1MM")
      (libsource (lib "eagle-import") (part "FIDUCIAL"))
    )
    (comp (ref "IC301")
      (value "LM2904")
      (footprint "eagle-import:SO08")
      (libsource (lib "eagle-import") (part "LM358D"))
    )
    (comp (ref "IC302")
      (value "78L06")
      (footprint "eagle-import:SOT89_ROUND")
      (libsource (lib "eagle-import") (part "78LXXSOT89_ROUND"))
    )
    (comp (ref "IC303")
      (value "6V pos")
      (footprint "eagle-import:78LXX")
      (libsource (lib "eagle-import") (part "v-reg_78LXX"))
    )
    (comp (ref "IC304")
      (value "78L10")
      (footprint "eagle-import:SOT89_ROUND")
      (libsource (lib "eagle-import") (part "78LXXSOT89_ROUND"))
    )
    (comp (ref "IC305")
      (value "4028")
      (footprint "eagle-import:SO16")
      (libsource (lib "eagle-import") (part "4028D"))
    )
    (comp (ref "IC307")
      (value "ULN2004")
      (footprint "eagle-import:SO16")
      (libsource (lib "eagle-import") (part "ULN2004AD"))
    )
    (comp (ref "IC308")
      (value "LM339")
      (footprint "eagle-import:SO14")
      (libsource (lib "eagle-import") (part "LM339D"))
    )
    (comp (ref "IC309")
      (value "317TO202H_NOHOLE")
      (footprint "eagle-import:TO220H_NOHOLE")
      (libsource (lib "eagle-import") (part "317TO202H_NOHOLE"))
    )
    (comp (ref "IC310")
      (value "555")
      (footprint "eagle-import:SO08")
      (libsource (lib "eagle-import") (part "555DNE"))
    )
    (comp (ref "IC311")
      (value "4538")
      (footprint "eagle-import:SO16")
      (libsource (lib "eagle-import") (part "4538D"))
    )
    (comp (ref "JP301")
      (value "JP2EJP2_SMALLPADS")
      (footprint "eagle-import:JP2_SMALLPADS")
      (libsource (lib "eagle-import") (part "JP2EJP2_SMALLPADS"))
    )
    (comp (ref "JP302")
      (value "JP2EJP2_SMALLPADS")
      (footprint "eagle-import:JP2_SMALLPADS")
      (libsource (lib "eagle-import") (part "JP2EJP2_SMALLPADS"))
    )
    (comp (ref "JP303")
      (value "JP2EJP2_SMALLPADS")
      (footprint "eagle-import:JP2_SMALLPADS")
      (libsource (lib "eagle-import") (part "JP2EJP2_SMALLPADS"))
    )
    (comp (ref "JP304")
      (value "JP2EJP2_SMALLPADS")
      (footprint "eagle-import:JP2_SMALLPADS")
      (libsource (lib "eagle-import") (part "JP2EJP2_SMALLPADS"))
    )
    (comp (ref "JP305")
      (value "JP2E_ORIG")
      (footprint "eagle-import:JP2_ORIG_SMALLPADS")
      (libsource (lib "eagle-import") (part "JP2E_ORIG"))
    )
    (comp (ref "LED301")
      (value "LEDLD260")
      (footprint "eagle-import:LD260")
      (libsource (lib "eagle-import") (part "LEDLD260"))
    )
    (comp (ref "LED302")
      (value "LEDLD260")
      (footprint "eagle-import:LD260")
      (libsource (lib "eagle-import") (part "LEDLD260"))
    )
    (comp (ref "LED303")
      (value "LEDLD260")
      (footprint "eagle-import:LD260")
      (libsource (lib "eagle-import") (part "LEDLD260"))
    )
    (comp (ref "LED304")
      (value "LEDLD260")
      (footprint "eagle-import:LD260")
      (libsource (lib "eagle-import") (part "LEDLD260"))
    )
    (comp (ref "LED305")
      (value "LEDLD260")
      (footprint "eagle-import:LD260")
      (libsource (lib "eagle-import") (part "LEDLD260"))
    )
    (comp (ref "LED306")
      (value "LEDLD260")
      (footprint "eagle-import:LD260")
      (libsource (lib "eagle-import") (part "LEDLD260"))
    )
    (comp (ref "Q301")
      (value "BA.")
      (footprint "eagle-import:SOT89")
      (libsource (lib "eagle-import") (part "PNP-TRANSISTOR_SOT89"))
    )
    (comp (ref "Q302")
      (value "BA.")
      (footprint "eagle-import:SOT89")
      (libsource (lib "eagle-import") (part "PNP-TRANSISTOR_SOT89"))
    )
    (comp (ref "Q303")
      (value "MY")
      (footprint "eagle-import:SOT89")
      (libsource (lib "eagle-import") (part "NPN-TRANSISTOR_SOT89"))
    )
    (comp (ref "Q304")
      (value "BA")
      (footprint "eagle-import:SOT89")
      (libsource (lib "eagle-import") (part "PNP-TRANSISTOR_SOT89"))
    )
    (comp (ref "Q305")
      (value "BA")
      (footprint "eagle-import:SOT89")
      (libsource (lib "eagle-import") (part "PNP-TRANSISTOR_SOT89"))
    )
    (comp (ref "Q306")
      (value "J1")
      (footprint "eagle-import:SOT-23")
      (fields (field (name "MPN") "BSS138W-7-F"))
      (libsource (lib "eagle-import") (part "SMD-MOSFET-N-CH-50V-200MA-BSS138W-7-F(SOT-23)"))
    )
    (comp (ref "Q307")
      (value "J1")
      (footprint "eagle-import:SOT-23")
      (fields (field (name "MPN") "BSS138W-7-F"))
      (libsource (lib "eagle-import") (part "SMD-MOSFET-N-CH-50V-200MA-BSS138W-7-F(SOT-23)"))
    )
    (comp (ref "R301")
      (value "102")
      (footprint "eagle-import:R0805")
      (fields (field (name "MPN") "RC0805JR-071KL"))
      (libsource (lib "eagle-import") (part "SMD-RES-1K-5%-1/8W(0805)"))
    )
    (comp (ref "R302")
      (value "13")
      (footprint "eagle-import:R1206")
      (fields (field (name "MPN") "RC1206JR-0713RL"))
      (libsource (lib "eagle-import") (part "SMD-RES-13R-5%-1/4W(1206)"))
    )
    (comp (ref "R303")
      (value "R_user")
      (footprint "eagle-import:R0805")
      (libsource (lib "eagle-import") (part "R-EU_R0805"))
    )
    (comp (ref "R305")
      (value "4701")
      (footprint "eagle-import:R0805")
      (fields (field (name "MPN") "RC0805JR-074K7L"))
      (libsource (lib "eagle-import") (part "SMD-RES-4.7K-5%-1/8W(0805)"))
    )
    (comp (ref "R306")
      (value "13")
      (footprint "eagle-import:R1206")
      (fields (field (name "MPN") "RC1206JR-0713RL"))
      (libsource (lib "eagle-import") (part "SMD-RES-13R-5%-1/4W(1206)"))
    )
    (comp (ref "R307")
      (value "1002")
      (footprint "eagle-import:R0805")
      (fields (field (name "MPN") "RC0805FR-0710KL"))
      (libsource (lib "eagle-import") (part "SMD-RES-10K-1%-1/8W(0805)"))
    )
    (comp (ref "R308")
      (value "1002")
      (footprint "eagle-import:R0805")
      (fields (field (name "MPN") "RC0805FR-0710KL"))
      (libsource (lib "eagle-import") (part "SMD-RES-10K-1%-1/8W(0805)"))
    )
    (comp (ref "R309")
      (value "104")
      (footprint "eagle-import:R0805")
      (fields (field (name "MPN") "RC0805FR-0710KL"))
      (libsource (lib "eagle-import") (part "SMD-RES-10K-1%-1/8W(0805)"))
    )
    (comp (ref "R310")
      (value "104")
      (footprint "eagle-import:R0805")
      (fields (field (name "MPN") "RC0805FR-0710KL"))
      (libsource (lib "eagle-import") (part "SMD-RES-10K-1%-1/8W(0805)"))
    )
    (comp (ref "R311")
      (value "104")
      (footprint "eagle-import:R0805")
      (fields (field (name "MPN") "RC0805FR-0710KL"))
      (libsource (lib "eagle-import") (part "SMD-RES-10K-1%-1/8W(0805)"))
    )
    (comp (ref "R312")
      (value "102")
      (footprint "eagle-import:R0805")
      (fields (field (name "MPN") "RC0805JR-071KL"))
      (libsource (lib "eagle-import") (part "SMD-RES-1K-5%-1/8W(0805)"))
    )
    (comp (ref "R313")
      (value "102")
      (footprint "eagle-import:R0805")
      (fields (field (name "MPN") "RC0805JR-071KL"))
      (libsource (lib "eagle-import") (part "SMD-RES-1K-5%-1/8W(0805)"))
    )
    (comp (ref "R314")
      (value "102")
      (footprint "eagle-import:R0805")
      (fields (field (name "MPN") "RC0805JR-071KL"))
      (libsource (lib "eagle-import") (part "SMD-RES-1K-5%-1/8W(0805)"))
    )
    (comp (ref "R315")
      (value "100")
      (footprint "eagle-import:R0805")
      (fields (field (name "MPN") "RC0805JR-07220RL"))
      (libsource (lib "eagle-import") (part "SMD-RES-220R-5%-1/8W(0805)"))
    )
    (comp (ref "R316")
      (value "4701")
      (footprint "eagle-import:R0805")
      (fields (field (name "MPN") "RC0805JR-074K7L"))
      (libsource (lib "eagle-import") (part "SMD-RES-4.7K-5%-1/8W(0805)"))
    )
    (comp (ref "R317")
      (value "2702")
      (footprint "eagle-import:R0805")
      (fields (field (name "MPN") "RC0805JR-074K7L"))
      (libsource (lib "eagle-import") (part "SMD-RES-4.7K-5%-1/8W(0805)"))
    )
    (comp (ref "R318")
      (value "13")
      (footprint "eagle-import:R1206")
      (fields (field (name "MPN") "RC1206JR-0713RL"))
      (libsource (lib "eagle-import") (part "SMD-RES-13R-5%-1/4W(1206)"))
    )
    (comp (ref "R319")
      (value "2201")
      (footprint "eagle-import:R0805")
      (fields (field (name "MPN") "RC0805JR-072K2L"))
      (libsource (lib "eagle-import") (part "SMD-RES-2.2K-5%-1/8W(0805)"))
    )
    (comp (ref "R320")
      (value "1002")
      (footprint "eagle-import:R0805")
      (fields (field (name "MPN") "RC0805FR-0710KL"))
      (libsource (lib "eagle-import") (part "SMD-RES-10K-1%-1/8W(0805)"))
    )
    (comp (ref "R321")
      (value "1502")
      (footprint "eagle-import:R0805")
      (fields (field (name "MPN") "RC0805FR-0710KL"))
      (libsource (lib "eagle-import") (part "SMD-RES-10K-1%-1/8W(0805)"))
    )
    (comp (ref "R322")
      (value "2702")
      (footprint "eagle-import:R0805")
      (fields (field (name "MPN") "RC0805JR-074K7L"))
      (libsource (lib "eagle-import") (part "SMD-RES-4.7K-5%-1/8W(0805)"))
    )
    (comp (ref "R323")
      (value "2702")
      (footprint "eagle-import:R0805")
      (fields (field (name "MPN") "RC0805JR-074K7L"))
      (libsource (lib "eagle-import") (part "SMD-RES-4.7K-5%-1/8W(0805)"))
    )
    (comp (ref "R324")
      (value "1002")
      (footprint "eagle-import:R0805")
      (fields (field (name "MPN") "RC0805FR-0710KL"))
      (libsource (lib "eagle-import") (part "SMD-RES-10K-1%-1/8W(0805)"))
    )
    (comp (ref "R325")
      (value "104")
      (footprint "eagle-import:R0805")
      (fields (field (name "MPN") "RC0805FR-0710KL"))
      (libsource (lib "eagle-import") (part "SMD-RES-10K-1%-1/8W(0805)"))
    )
    (comp (ref "R326")
      (value "4701")
      (footprint "eagle-import:R0805")
      (fields (field (name "MPN") "RC0805JR-074K7L"))
      (libsource (lib "eagle-import") (part "SMD-RES-4.7K-5%-1/8W(0805)"))
    )
    (comp (ref "R327")
      (value "47")
      (footprint "eagle-import:V235_17_1MM")
      (libsource (lib "eagle-import") (part "R-EU_V235/17_1MM"))
    )
    (comp (ref "R328")
      (value "102")
      (footprint "eagle-import:R0805")
      (fields (field (name "MPN") "RC0805JR-071KL"))
      (libsource (lib "eagle-import") (part "SMD-RES-1K-5%-1/8W(0805)"))
    )
    (comp (ref "R329")
      (value "47")
      (footprint "eagle-import:V235_17_1MM")
      (libsource (lib "eagle-import") (part "R-EU_V235/17_1MM"))
    )
    (comp (ref "R330")
      (value "104")
      (footprint "eagle-import:R0805")
      (fields (field (name "MPN") "RC0805FR-0710KL"))
      (libsource (lib "eagle-import") (part "SMD-RES-10K-1%-1/8W(0805)"))
    )
    (comp (ref "R331")
      (value "1502")
      (footprint "eagle-import:R0805")
      (fields (field (name "MPN") "RC0805FR-0710KL"))
      (libsource (lib "eagle-import") (part "SMD-RES-10K-1%-1/8W(0805)"))
    )
    (comp (ref "R332")
      (value "1002")
      (footprint "eagle-import:R0805")
      (fields (field (name "MPN") "RC0805FR-0710KL"))
      (libsource (lib "eagle-import") (part "SMD-RES-10K-1%-1/8W(0805)"))
    )
    (comp (ref "R333")
      (value "2201")
      (footprint "eagle-import:R0805")
      (fields (field (name "MPN") "RC0805JR-072K2L"))
      (libsource (lib "eagle-import") (part "SMD-RES-2.2K-5%-1/8W(0805)"))
    )
    (comp (ref "R334")
      (value "13")
      (footprint "eagle-import:R1206")
      (fields (field (name "MPN") "RC1206JR-0713RL"))
      (libsource (lib "eagle-import") (part "SMD-RES-13R-5%-1/4W(1206)"))
    )
    (comp (ref "R335")
      (value "104")
      (footprint "eagle-import:R0805")
      (fields (field (name "MPN") "RC0805FR-0710KL"))
      (libsource (lib "eagle-import") (part "SMD-RES-10K-1%-1/8W(0805)"))
    )
    (comp (ref "R336")
      (value "47")
      (footprint "eagle-import:V235_17_1MM")
      (libsource (lib "eagle-import") (part "R-EU_V235/17_1MM"))
    )
    (comp (ref "R337")
      (value "47")
      (footprint "eagle-import:V235_17_1MM")
      (libsource (lib "eagle-import") (part "R-EU_V235/17_1MM"))
    )
    (comp (ref "R338")
      (value "100")
      (footprint "eagle-import:R0805")
      (fields (field (name "MPN") "RC0805JR-072K2L"))
      (libsource (lib "eagle-import") (part "SMD-RES-2.2K-5%-1/8W(0805)"))
    )
    (comp (ref "R339")
      (value "(101)")
      (footprint "eagle-import:R0805")
      (fields (field (name "MPN") "RC0805JR-072K2L"))
      (libsource (lib "eagle-import") (part "SMD-RES-2.2K-5%-1/8W(0805)"))
    )
    (comp (ref "R340")
      (value "2702")
      (footprint "eagle-import:R0805")
      (fields (field (name "MPN") "RC0805FR-0710KL"))
      (libsource (lib "eagle-import") (part "SMD-RES-10K-1%-1/8W(0805)"))
    )
    (comp (ref "R341")
      (value "104")
      (footprint "eagle-import:R0805")
      (fields (field (name "MPN") "RC0805FR-0710KL"))
      (libsource (lib "eagle-import") (part "SMD-RES-10K-1%-1/8W(0805)"))
    )
    (comp (ref "R342")
      (value "(1000)")
      (footprint "eagle-import:R0805")
      (fields (field (name "MPN") "RC0805JR-07100RL"))
      (libsource (lib "eagle-import") (part "SMD-RES-100R-5%-1/8W(0805)"))
    )
    (comp (ref "R343")
      (value "(101)")
      (footprint "eagle-import:R0805")
      (fields (field (name "MPN") "RC0805JR-07100RL"))
      (libsource (lib "eagle-import") (part "SMD-RES-100R-5%-1/8W(0805)"))
    )
    (comp (ref "R344")
      (value "(1002)")
      (footprint "eagle-import:R0805")
      (fields (field (name "MPN") "RC0805FR-0710KL"))
      (libsource (lib "eagle-import") (part "SMD-RES-10K-1%-1/8W(0805)"))
    )
    (comp (ref "R345")
      (value "2702")
      (footprint "eagle-import:R0805")
      (fields (field (name "MPN") "RC0805JR-074K7L"))
      (libsource (lib "eagle-import") (part "SMD-RES-4.7K-5%-1/8W(0805)"))
    )
    (comp (ref "R346")
      (value "(1002)")
      (footprint "eagle-import:R0805")
      (fields (field (name "MPN") "RC0805JR-074K7L"))
      (libsource (lib "eagle-import") (part "SMD-RES-4.7K-5%-1/8W(0805)"))
    )
    (comp (ref "SJ301")
      (value "SJ")
      (footprint "eagle-import:SJ")
      (libsource (lib "eagle-import") (part "SJ"))
    )
    (comp (ref "START301")
      (value "TPSB2.0")
      (footprint "eagle-import:B2.0")
      (libsource (lib "eagle-import") (part "TPSB2.0"))
    )
    (comp (ref "TP47")
      (value "TPSB2.0")
      (footprint "eagle-import:B2.0")
      (libsource (lib "eagle-import") (part "TPSB2.0"))
    )
    (comp (ref "TP48")
      (value "TPSB2.0")
      (footprint "eagle-import:B2.0")
      (libsource (lib "eagle-import") (part "TPSB2.0"))
    )
    (comp (ref "TP49")
      (value "TPSB2.0")
      (footprint "eagle-import:B2.0")
      (libsource (lib "eagle-import") (part "TPSB2.0"))
    )
    (comp (ref "TP50")
      (value "TPSB2.0")
      (footprint "eagle-import:B2.0")
      (libsource (lib "eagle-import") (part "TPSB2.0"))
    )
    (comp (ref "TP51")
      (value "TPSB2.0")
      (footprint "eagle-import:B2.0")
      (libsource (lib "eagle-import") (part "TPSB2.0"))
    )
    (comp (ref "TP52")
      (value "TPSB2.0")
      (footprint "eagle-import:B2.0")
      (libsource (lib "eagle-import") (part "TPSB2.0"))
    )
    (comp (ref "TP53")
      (value "TPSB2.0")
      (footprint "eagle-import:B2.0")
      (libsource (lib "eagle-import") (part "TPSB2.0"))
    )
    (comp (ref "TP54")
      (value "TPSB2.0")
      (footprint "eagle-import:B2.0")
      (libsource (lib "eagle-import") (part "TPSB2.0"))
    )
    (comp (ref "TP55")
      (value "TPSB2.0")
      (footprint "eagle-import:B2.0")
      (libsource (lib "eagle-import") (part "TPSB2.0"))
    )
    (comp (ref "TP56")
      (value "TPSB2.0")
      (footprint "eagle-import:B2.0")
      (libsource (lib "eagle-import") (part "TPSB2.0"))
    )
    (comp (ref "TP57")
      (value "TPSB2.0")
      (footprint "eagle-import:B2.0")
      (libsource (lib "eagle-import") (part "TPSB2.0"))
    )
    (comp (ref "TP58")
      (value "TPSB2.0")
      (footprint "eagle-import:B2.0")
      (libsource (lib "eagle-import") (part "TPSB2.0"))
    )
    (comp (ref "TP59")
      (value "TPSB2.0")
      (footprint "eagle-import:B2.0")
      (libsource (lib "eagle-import") (part "TPSB2.0"))
    )
    (comp (ref "TP60")
      (value "TPSB2.0")
      (footprint "eagle-import:B2.0")
      (libsource (lib "eagle-import") (part "TPSB2.0"))
    )
    (comp (ref "TP61")
      (value "TPSB2.0")
      (footprint "eagle-import:B2.0")
      (libsource (lib "eagle-import") (part "TPSB2.0"))
    )
    (comp (ref "TP62")
      (value "TPSB2.0")
      (footprint "eagle-import:B2.0")
      (libsource (lib "eagle-import") (part "TPSB2.0"))
    )
    (comp (ref "TP63")
      (value "TPSB2.0")
      (footprint "eagle-import:B2.0")
      (libsource (lib "eagle-import") (part "TPSB2.0"))
    )
    (comp (ref "TP64")
      (value "TPSB2.0")
      (footprint "eagle-import:B2.0")
      (libsource (lib "eagle-import") (part "TPSB2.0"))
    )
    (comp (ref "TP65")
      (value "TPSB1,27")
      (footprint "eagle-import:B1,27")
      (libsource (lib "eagle-import") (part "TPSB1,27"))
    )
    (comp (ref "TP66")
      (value "TPSB2.0")
      (footprint "eagle-import:B2.0")
      (libsource (lib "eagle-import") (part "TPSB2.0"))
    )
    (comp (ref "TP67")
      (value "TPSB2.0")
      (footprint "eagle-import:B2.0")
      (libsource (lib "eagle-import") (part "TPSB2.0"))
    )
    (comp (ref "TP68")
      (value "TPSB2.0")
      (footprint "eagle-import:B2.0")
      (libsource (lib "eagle-import") (part "TPSB2.0"))
    )
    (comp (ref "TP69")
      (value "TPSB2.0")
      (footprint "eagle-import:B2.0")
      (libsource (lib "eagle-import") (part "TPSB2.0"))
    )
    (comp (ref "X301")
      (value "CON_BMWV2")
      (footprint "eagle-import:24-PIN_V2")
      (libsource (lib "eagle-import") (part "CON_BMWV2"))
    )
    (comp (ref "X302")
      (value "22-23-2021")
      (footprint "eagle-import:22-23-2021")
      (fields (field (name "MF") "MOLEX"))
      (libsource (lib "eagle-import") (part "22-23-2021"))
    )
    (comp (ref "X303")
      (value "22-23-2051")
      (footprint "eagle-import:22-23-2051")
      (fields (field (name "MF") "MOLEX"))
      (libsource (lib "eagle-import") (part "22-23-2051"))
    )
  )
  (nets
    (net (code "1") (name "+10V") (class "Default")
      (node (ref "10V") (pin "TP") (pinfunction "PP_TP") (pintype "input"))
      (node (ref "10V1") (pin "TP") (pinfunction "PP_TP") (pintype "input"))
      (node (ref "10V2") (pin "TP") (pinfunction "PP_TP") (pintype "input"))
      (node (ref "10V201") (pin "TP") (pinfunction "PP_TP") (pintype "input"))
      (node (ref "10V3") (pin "TP") (pinfunction "PP_TP") (pintype "input"))
      (node (ref "10V301") (pin "TP") (pinfunction "PP_TP") (pintype "input"))
      (node (ref "10V4") (pin "TP") (pinfunction "PP_TP") (pintype "input"))
      (node (ref "10V401") (pin "TP") (pinfunction "PP_TP") (pintype "input"))
      (node (ref "10V5") (pin "TP") (pinfunction "PP_TP") (pintype "input"))
      (node (ref "10V501") (pin "TP") (pinfunction "PP_TP") (pintype "input"))
      (node (ref "10V6") (pin "TP") (pinfunction "PP_TP") (pintype "input"))
      (node (ref "10V601") (pin "TP") (pinfunction "PP_TP") (pintype "input"))
      (node (ref "C102") (pin "1") (pinfunction "1_1") (pintype "passive"))
      (node (ref "C18") (pin "1") (pinfunction "1_1") (pintype "passive"))
      (node (ref "C202") (pin "1") (pinfunction "1_1") (pintype "passive"))
      (node (ref "C28") (pin "1") (pinfunction "1_1") (pintype "passive"))
      (node (ref "C302") (pin "1") (pinfunction "1_1") (pintype "passive"))
      (node (ref "C38") (pin "1") (pinfunction "1_1") (pintype "passive"))
      (node (ref "C402") (pin "1") (pinfunction "1_1") (pintype "passive"))
      (node (ref "C48") (pin "1") (pinfunction "1_1") (pintype "passive"))
      (node (ref "C502") (pin "1") (pinfunction "1_1") (pintype "passive"))
      (node (ref "C58") (pin "1") (pinfunction "1_1") (pintype "passive"))
      (node (ref "C602") (pin "1") (pinfunction "1_1") (pintype "passive"))
      (node (ref "C8") (pin "1") (pinfunction "1_1") (pintype "passive"))
      (node (ref "IC104") (pin "1") (pinfunction "OUT_1") (pintype "passive"))
      (node (ref "IC110") (pin "4") (pinfunction "R_4") (pintype "input"))
      (node (ref "IC110") (pin "8") (pinfunction "V+_8") (pintype "power_in"))
      (node (ref "IC111") (pin "13") (pinfunction "CD_13") (pintype "input"))
      (node (ref "IC111") (pin "16") (pinfunction "VDD_16") (pintype "power_in"))
      (node (ref "IC111") (pin "3") (pinfunction "CD_3") (pintype "input"))
      (node (ref "IC111") (pin "5") (pinfunction "B_5") (pintype "input"))
      (node (ref "IC17") (pin "4") (pinfunction "R_4") (pintype "input"))
      (node (ref "IC17") (pin "8") (pinfunction "V+_8") (pintype "power_in"))
      (node (ref "IC18") (pin "13") (pinfunction "CD_13") (pintype "input"))
      (node (ref "IC18") (pin "16") (pinfunction "VDD_16") (pintype "power_in"))
      (node (ref "IC18") (pin "3") (pinfunction "CD_3") (pintype "input"))
      (node (ref "IC18") (pin "5") (pinfunction "B_5") (pintype "input"))
      (node (ref "IC19") (pin "1") (pinfunction "OUT_1") (pintype "passive"))
      (node (ref "IC204") (pin "1") (pinfunction "OUT_1") (pintype "passive"))
      (node (ref "IC210") (pin "4") (pinfunction "R_4") (pintype "input"))
      (node (ref "IC210") (pin "8") (pinfunction "V+_8") (pintype "power_in"))
      (node (ref "IC211") (pin "13") (pinfunction "CD_13") (pintype "input"))
      (node (ref "IC211") (pin "16") (pinfunction "VDD_16") (pintype "power_in"))
      (node (ref "IC211") (pin "3") (pinfunction "CD_3") (pintype "input"))
      (node (ref "IC211") (pin "5") (pinfunction "B_5") (pintype "input"))
      (node (ref "IC27") (pin "4") (pinfunction "R_4") (pintype "input"))
      (node (ref "IC27") (pin "8") (pinfunction "V+_8") (pintype "power_in"))
      (node (ref "IC28") (pin "13") (pinfunction "CD_13") (pintype "input"))
      (node (ref "IC28") (pin "16") (pinfunction "VDD_16") (pintype "power_in"))
      (node (ref "IC28") (pin "3") (pinfunction "CD_3") (pintype "input"))
      (node (ref "IC28") (pin "5") (pinfunction "B_5") (pintype "input"))
      (node (ref "IC29") (pin "1") (pinfunction "OUT_1") (pintype "passive"))
      (node (ref "IC304") (pin "1") (pinfunction "OUT_1") (pintype "passive"))
      (node (ref "IC310") (pin "4") (pinfunction "R_4") (pintype "input"))
      (node (ref "IC310") (pin "8") (pinfunction "V+_8") (pintype "power_in"))
      (node (ref "IC311") (pin "13") (pinfunction "CD_13") (pintype "input"))
      (node (ref "IC311") (pin "16") (pinfunction "VDD_16") (pintype "power_in"))
      (node (ref "IC311") (pin "3") (pinfunction "CD_3") (pintype "input"))
      (node (ref "IC311") (pin "5") (pinfunction "B_5") (pintype "input"))
      (node (ref "IC37") (pin "4") (pinfunction "R_4") (pintype "input"))
      (node (ref "IC37") (pin "8") (pinfunction "V+_8") (pintype "power_in"))
      (node (ref "IC38") (pin "13") (pinfunction "CD_13") (pintype "input"))
      (node (ref "IC38") (pin "16") (pinfunction "VDD_16") (pintype "power_in"))
      (node (ref "IC38") (pin "3") (pinfunction "CD_3") (pintype "input"))
      (node (ref "IC38") (pin "5") (pinfunction "B_5") (pintype "input"))
      (node (ref "IC39") (pin "1") (pinfunction "OUT_1") (pintype "passive"))
      (node (ref "IC404") (pin "1") (pinfunction "OUT_1") (pintype "passive"))
      (node (ref "IC410") (pin "4") (pinfunction "R_4") (pintype "input"))
      (node (ref "IC410") (pin "8") (pinfunction "V+_8") (pintype "power_in"))
      (node (ref "IC411") (pin "13") (pinfunction "CD_13") (pintype "input"))
      (node (ref "IC411") (pin "16") (pinfunction "VDD_16") (pintype "power_in"))
      (node (ref "IC411") (pin "3") (pinfunction "CD_3") (pintype "input"))
      (node (ref "IC411") (pin "5") (pinfunction "B_5") (pintype "input"))
      (node (ref "IC47") (pin "4") (pinfunction "R_4") (pintype "input"))
      (node (ref "IC47") (pin "8") (pinfunction "V+_8") (pintype "power_in"))
      (node (ref "IC48") (pin "13") (pinfunction "CD_13") (pintype "input"))
      (node (ref "IC48") (pin "16") (pinfunction "VDD_16") (pintype "power_in"))
      (node (ref "IC48") (pin "3") (pinfunction "CD_3") (pintype "input"))
      (node (ref "IC48") (pin "5") (pinfunction "B_5") (pintype "input"))
      (node (ref "IC49") (pin "1") (pinfunction "OUT_1") (pintype "passive"))
      (node (ref "IC504") (pin "1") (pinfunction "OUT_1") (pintype "passive"))
      (node (ref "IC510") (pin "4") (pinfunction "R_4") (pintype "input"))
      (node (ref "IC510") (pin "8") (pinfunction "V+_8") (pintype "power_in"))
      (node (ref "IC511") (pin "13") (pinfunction "CD_13") (pintype "input"))
      (node (ref "IC511") (pin "16") (pinfunction "VDD_16") (pintype "power_in"))
      (node (ref "IC511") (pin "3") (pinfunction "CD_3") (pintype "input"))
      (node (ref "IC511") (pin "5") (pinfunction "B_5") (pintype "input"))
      (node (ref "IC57") (pin "4") (pinfunction "R_4") (pintype "input"))
      (node (ref "IC57") (pin "8") (pinfunction "V+_8") (pintype "power_in"))
      (node (ref "IC58") (pin "13") (pinfunction "CD_13") (pintype "input"))
      (node (ref "IC58") (pin "16") (pinfunction "VDD_16") (pintype "power_in"))
      (node (ref "IC58") (pin "3") (pinfunction "CD_3") (pintype "input"))
      (node (ref "IC58") (pin "5") (pinfunction "B_5") (pintype "input"))
      (node (ref "IC59") (pin "1") (pinfunction "OUT_1") (pintype "passive"))
      (node (ref "IC604") (pin "1") (pinfunction "OUT_1") (pintype "passive"))
      (node (ref "IC610") (pin "4") (pinfunction "R_4") (pintype "input"))
      (node (ref "IC610") (pin "8") (pinfunction "V+_8") (pintype "power_in"))
      (node (ref "IC611") (pin "13") (pinfunction "CD_13") (pintype "input"))
      (node (ref "IC611") (pin "16") (pinfunction "VDD_16") (pintype "power_in"))
      (node (ref "IC611") (pin "3") (pinfunction "CD_3") (pintype "input"))
      (node (ref "IC611") (pin "5") (pinfunction "B_5") (pintype "input"))
      (node (ref "IC7") (pin "4") (pinfunction "R_4") (pintype "input"))
      (node (ref "IC7") (pin "8") (pinfunction "V+_8") (pintype "power_in"))
      (node (ref "IC8") (pin "13") (pinfunction "CD_13") (pintype "input"))
      (node (ref "IC8") (pin "16") (pinfunction "VDD_16") (pintype "power_in"))
      (node (ref "IC8") (pin "3") (pinfunction "CD_3") (pintype "input"))
      (node (ref "IC8") (pin "5") (pinfunction "B_5") (pintype "input"))
      (node (ref "IC9") (pin "1") (pinfunction "OUT_1") (pintype "passive"))
      (node (ref "R145") (pin "2") (pinfunction "2_2") (pintype "passive"))
      (node (ref "R171") (pin "2") (pinfunction "2_2") (pintype "passive"))
      (node (ref "R245") (pin "2") (pinfunction "2_2") (pintype "passive"))
      (node (ref "R261") (pin "2") (pinfunction "2_2") (pintype "passive"))
      (node (ref "R345") (pin "2") (pinfunction "2_2") (pintype "passive"))
      (node (ref "R351") (pin "2") (pinfunction "2_2") (pintype "passive"))
      (node (ref "R36") (pin "2") (pinfunction "2_2") (pintype "passive"))
      (node (ref "R396") (pin "2") (pinfunction "2_2") (pintype "passive"))
      (node (ref "R445") (pin "2") (pinfunction "2_2") (pintype "passive"))
      (node (ref "R545") (pin "2") (pinfunction "2_2") (pintype "passive"))
      (node (ref "R645") (pin "2") (pinfunction "2_2") (pintype "passive"))
      (node (ref "R81") (pin "2") (pinfunction "2_2") (pintype "passive"))
    )
    (net (code "2") (name "+12V") (class "Default")
      (node (ref "10") (pin "1") (pinfunction "KL_1") (pintype "passive"))
      (node (ref "12") (pin "1") (pinfunction "KL_1") (pintype "passive"))
      (node (ref "14") (pin "1") (pinfunction "KL_1") (pintype "passive"))
      (node (ref "16") (pin "1") (pinfunction "KL_1") (pintype "passive"))
      (node (ref "18") (pin "1") (pinfunction "KL_1") (pintype "passive"))
      (node (ref "2") (pin "1") (pinfunction "KL_1") (pintype "passive"))
      (node (ref "20") (pin "1") (pinfunction "KL_1") (pintype "passive"))
      (node (ref "22") (pin "1") (pinfunction "KL_1") (pintype "passive"))
      (node (ref "24") (pin "1") (pinfunction "KL_1") (pintype "passive"))
      (node (ref "4") (pin "1") (pinfunction "KL_1") (pintype "passive"))
      (node (ref "6") (pin "1") (pinfunction "KL_1") (pintype "passive"))
      (node (ref "8") (pin "1") (pinfunction "KL_1") (pintype "passive"))
      (node (ref "D101") (pin "C") (pinfunction "C_C") (pintype "passive"))
      (node (ref "D11") (pin "C") (pinfunction "C_C") (pintype "passive"))
      (node (ref "D201") (pin "C") (pinfunction "C_C") (pintype "passive"))
      (node (ref "D22") (pin "C") (pinfunction "C_C") (pintype "passive"))
      (node (ref "D301") (pin "C") (pinfunction "C_C") (pintype "passive"))
      (node (ref "D33") (pin "C") (pinfunction "C_C") (pintype "passive"))
      (node (ref "D401") (pin "C") (pinfunction "C_C") (pintype "passive"))
      (node (ref "D44") (pin "C") (pinfunction "C_C") (pintype "passive"))
      (node (ref "D501") (pin "C") (pinfunction "C_C") (pintype "passive"))
      (node (ref "D55") (pin "C") (pinfunction "C_C") (pintype "passive"))
      (node (ref "D601") (pin "C") (pinfunction "C_C") (pintype "passive"))
      (node (ref "D66") (pin "C") (pinfunction "C_C") (pintype "passive"))
      (node (ref "IC1") (pin "16") (pinfunction "VDD_16") (pintype "power_in"))
      (node (ref "IC102") (pin "3") (pinfunction "IN_3") (pintype "input"))
      (node (ref "IC103") (pin "IN") (pinfunction "IN_IN") (pintype "input"))
      (node (ref "IC104") (pin "3") (pinfunction "IN_3") (pintype "input"))
      (node (ref "IC105") (pin "16") (pinfunction "VDD_16") (pintype "power_in"))
      (node (ref "IC107") (pin "9") (pinfunction "CD+_9") (pintype "passive"))
      (node (ref "IC11") (pin "16") (pinfunction "VDD_16") (pintype "power_in"))
      (node (ref "IC12") (pin "IN") (pinfunction "IN_IN") (pintype "input"))
      (node (ref "IC14") (pin "9") (pinfunction "CD+_9") (pintype "passive"))
      (node (ref "IC16") (pin "3") (pinfunction "IN_3") (pintype "input"))
      (node (ref "IC19") (pin "3") (pinfunction "IN_3") (pintype "input"))
      (node (ref "IC2") (pin "IN") (pinfunction "IN_IN") (pintype "input"))
      (node (ref "IC202") (pin "3") (pinfunction "IN_3") (pintype "input"))
      (node (ref "IC203") (pin "IN") (pinfunction "IN_IN") (pintype "input"))
      (node (ref "IC204") (pin "3") (pinfunction "IN_3") (pintype "input"))
      (node (ref "IC205") (pin "16") (pinfunction "VDD_16") (pintype "power_in"))
      (node (ref "IC207") (pin "9") (pinfunction "CD+_9") (pintype "passive"))
      (node (ref "IC21") (pin "16") (pinfunction "VDD_16") (pintype "power_in"))
      (node (ref "IC22") (pin "IN") (pinfunction "IN_IN") (pintype "input"))
      (node (ref "IC24") (pin "9") (pinfunction "CD+_9") (pintype "passive"))
      (node (ref "IC26") (pin "3") (pinfunction "IN_3") (pintype "input"))
      (node (ref "IC29") (pin "3") (pinfunction "IN_3") (pintype "input"))
      (node (ref "IC302") (pin "3") (pinfunction "IN_3") (pintype "input"))
      (node (ref "IC303") (pin "IN") (pinfunction "IN_IN") (pintype "input"))
      (node (ref "IC304") (pin "3") (pinfunction "IN_3") (pintype "input"))
      (node (ref "IC305") (pin "16") (pinfunction "VDD_16") (pintype "power_in"))
      (node (ref "IC307") (pin "9") (pinfunction "CD+_9") (pintype "passive"))
      (node (ref "IC31") (pin "16") (pinfunction "VDD_16") (pintype "power_in"))
      (node (ref "IC32") (pin "IN") (pinfunction "IN_IN") (pintype "input"))
      (node (ref "IC34") (pin "9") (pinfunction "CD+_9") (pintype "passive"))
      (node (ref "IC36") (pin "3") (pinfunction "IN_3") (pintype "input"))
      (node (ref "IC39") (pin "3") (pinfunction "IN_3") (pintype "input"))
      (node (ref "IC4") (pin "9") (pinfunction "CD+_9") (pintype "passive"))
      (node (ref "IC402") (pin "3") (pinfunction "IN_3") (pintype "input"))
      (node (ref "IC403") (pin "IN") (pinfunction "IN_IN") (pintype "input"))
      (node (ref "IC404") (pin "3") (pinfunction "IN_3") (pintype "input"))
      (node (ref "IC405") (pin "16") (pinfunction "VDD_16") (pintype "power_in"))
      (node (ref "IC407") (pin "9") (pinfunction "CD+_9") (pintype "passive"))
      (node (ref "IC41") (pin "16") (pinfunction "VDD_16") (pintype "power_in"))
      (node (ref "IC42") (pin "IN") (pinfunction "IN_IN") (pintype "input"))
      (node (ref "IC44") (pin "9") (pinfunction "CD+_9") (pintype "passive"))
      (node (ref "IC46") (pin "3") (pinfunction "IN_3") (pintype "input"))
      (node (ref "IC49") (pin "3") (pinfunction "IN_3") (pintype "input"))
      (node (ref "IC502") (pin "3") (pinfunction "IN_3") (pintype "input"))
      (node (ref "IC503") (pin "IN") (pinfunction "IN_IN") (pintype "input"))
      (node (ref "IC504") (pin "3") (pinfunction "IN_3") (pintype "input"))
      (node (ref "IC505") (pin "16") (pinfunction "VDD_16") (pintype "power_in"))
      (node (ref "IC507") (pin "9") (pinfunction "CD+_9") (pintype "passive"))
      (node (ref "IC51") (pin "16") (pinfunction "VDD_16") (pintype "power_in"))
      (node (ref "IC52") (pin "IN") (pinfunction "IN_IN") (pintype "input"))
      (node (ref "IC54") (pin "9") (pinfunction "CD+_9") (pintype "passive"))
      (node (ref "IC56") (pin "3") (pinfunction "IN_3") (pintype "input"))
      (node (ref "IC59") (pin "3") (pinfunction "IN_3") (pintype "input"))
      (node (ref "IC6") (pin "3") (pinfunction "IN_3") (pintype "input"))
      (node (ref "IC602") (pin "3") (pinfunction "IN_3") (pintype "input"))
      (node (ref "IC603") (pin "IN") (pinfunction "IN_IN") (pintype "input"))
      (node (ref "IC604") (pin "3") (pinfunction "IN_3") (pintype "input"))
      (node (ref "IC605") (pin "16") (pinfunction "VDD_16") (pintype "power_in"))
      (node (ref "IC607") (pin "9") (pinfunction "CD+_9") (pintype "passive"))
      (node (ref "IC9") (pin "3") (pinfunction "IN_3") (pintype "input"))
      (node (ref "JP1") (pin "2") (pinfunction "2_2") (pintype "passive"))
      (node (ref "JP101") (pin "2") (pinfunction "2_2") (pintype "passive"))
      (node (ref "JP11") (pin "2") (pinfunction "2_2") (pintype "passive"))
      (node (ref "JP16") (pin "2") (pinfunction "2_2") (pintype "passive"))
      (node (ref "JP201") (pin "2") (pinfunction "2_2") (pintype "passive"))
      (node (ref "JP21") (pin "2") (pinfunction "2_2") (pintype "passive"))
      (node (ref "JP26") (pin "2") (pinfunction "2_2") (pintype "passive"))
      (node (ref "JP301") (pin "2") (pinfunction "2_2") (pintype "passive"))
      (node (ref "JP401") (pin "2") (pinfunction "2_2") (pintype "passive"))
      (node (ref "JP501") (pin "2") (pinfunction "2_2") (pintype "passive"))
      (node (ref "JP6") (pin "2") (pinfunction "2_2") (pintype "passive"))
      (node (ref "JP601") (pin "2") (pinfunction "2_2") (pintype "passive"))
      (node (ref "Q1") (pin "3") (pinfunction "E_3") (pintype "passive"))
      (node (ref "Q104") (pin "3") (pinfunction "E_3") (pintype "passive"))
      (node (ref "Q105") (pin "3") (pinfunction "E_3") (pintype "passive"))
      (node (ref "Q11") (pin "3") (pinfunction "E_3") (pintype "passive"))
      (node (ref "Q15") (pin "3") (pinfunction "E_3") (pintype "passive"))
      (node (ref "Q18") (pin "3") (pinfunction "E_3") (pintype "passive"))
      (node (ref "Q204") (pin "3") (pinfunction "E_3") (pintype "passive"))
      (node (ref "Q205") (pin "3") (pinfunction "E_3") (pintype "passive"))
      (node (ref "Q22") (pin "3") (pinfunction "E_3") (pintype "passive"))
      (node (ref "Q25") (pin "3") (pinfunction "E_3") (pintype "passive"))
      (node (ref "Q29") (pin "3") (pinfunction "E_3") (pintype "passive"))
      (node (ref "Q304") (pin "3") (pinfunction "E_3") (pintype "passive"))
      (node (ref "Q305") (pin "3") (pinfunction "E_3") (pintype "passive"))
      (node (ref "Q32") (pin "3") (pinfunction "E_3") (pintype "passive"))
      (node (ref "Q36") (pin "3") (pinfunction "E_3") (pintype "passive"))
      (node (ref "Q39") (pin "3") (pinfunction "E_3") (pintype "passive"))
      (node (ref "Q4") (pin "3") (pinfunction "E_3") (pintype "passive"))
      (node (ref "Q404") (pin "3") (pinfunction "E_3") (pintype "passive"))
      (node (ref "Q405") (pin "3") (pinfunction "E_3") (pintype "passive"))
      (node (ref "Q504") (pin "3") (pinfunction "E_3") (pintype "passive"))
      (node (ref "Q505") (pin "3") (pinfunction "E_3") (pintype "passive"))
      (node (ref "Q604") (pin "3") (pinfunction "E_3") (pintype "passive"))
      (node (ref "Q605") (pin "3") (pinfunction "E_3") (pintype "passive"))
      (node (ref "Q8") (pin "3") (pinfunction "E_3") (pintype "passive"))
      (node (ref "R102") (pin "1") (pinfunction "1_1") (pintype "passive"))
      (node (ref "R106") (pin "1") (pinfunction "1_1") (pintype "passive"))
      (node (ref "R109") (pin "2") (pinfunction "2_2") (pintype "passive"))
      (node (ref "R110") (pin "2") (pinfunction "2_2") (pintype "passive"))
      (node (ref "R111") (pin "2") (pinfunction "2_2") (pintype "passive"))
      (node (ref "R129") (pin "2") (pinfunction "2_2") (pintype "passive"))
      (node (ref "R135") (pin "1") (pinfunction "1_1") (pintype "passive"))
      (node (ref "R159") (pin "1") (pinfunction "1_1") (pintype "passive"))
      (node (ref "R160") (pin "1") (pinfunction "1_1") (pintype "passive"))
      (node (ref "R165") (pin "1") (pinfunction "1_1") (pintype "passive"))
      (node (ref "R183") (pin "2") (pinfunction "2_2") (pintype "passive"))
      (node (ref "R184") (pin "2") (pinfunction "2_2") (pintype "passive"))
      (node (ref "R185") (pin "2") (pinfunction "2_2") (pintype "passive"))
      (node (ref "R186") (pin "2") (pinfunction "2_2") (pintype "passive"))
      (node (ref "R202") (pin "1") (pinfunction "1_1") (pintype "passive"))
      (node (ref "R206") (pin "1") (pinfunction "1_1") (pintype "passive"))
      (node (ref "R209") (pin "2") (pinfunction "2_2") (pintype "passive"))
      (node (ref "R210") (pin "2") (pinfunction "2_2") (pintype "passive"))
      (node (ref "R211") (pin "2") (pinfunction "2_2") (pintype "passive"))
      (node (ref "R229") (pin "2") (pinfunction "2_2") (pintype "passive"))
      (node (ref "R235") (pin "1") (pinfunction "1_1") (pintype "passive"))
      (node (ref "R24") (pin "1") (pinfunction "1_1") (pintype "passive"))
      (node (ref "R249") (pin "1") (pinfunction "1_1") (pintype "passive"))
      (node (ref "R25") (pin "1") (pinfunction "1_1") (pintype "passive"))
      (node (ref "R250") (pin "1") (pinfunction "1_1") (pintype "passive"))
      (node (ref "R255") (pin "1") (pinfunction "1_1") (pintype "passive"))
      (node (ref "R273") (pin "2") (pinfunction "2_2") (pintype "passive"))
      (node (ref "R274") (pin "2") (pinfunction "2_2") (pintype "passive"))
      (node (ref "R275") (pin "2") (pinfunction "2_2") (pintype "passive"))
      (node (ref "R276") (pin "2") (pinfunction "2_2") (pintype "passive"))
      (node (ref "R294") (pin "1") (pinfunction "1_1") (pintype "passive"))
      (node (ref "R295") (pin "1") (pinfunction "1_1") (pintype "passive"))
      (node (ref "R3") (pin "2") (pinfunction "2_2") (pintype "passive"))
      (node (ref "R30") (pin "1") (pinfunction "1_1") (pintype "passive"))
      (node (ref "R300") (pin "1") (pinfunction "1_1") (pintype "passive"))
      (node (ref "R302") (pin "1") (pinfunction "1_1") (pintype "passive"))
      (node (ref "R306") (pin "1") (pinfunction "1_1") (pintype "passive"))
      (node (ref "R309") (pin "2") (pinfunction "2_2") (pintype "passive"))
      (node (ref "R310") (pin "2") (pinfunction "2_2") (pintype "passive"))
      (node (ref "R311") (pin "2") (pinfunction "2_2") (pintype "passive"))
      (node (ref "R329") (pin "2") (pinfunction "2_2") (pintype "passive"))
      (node (ref "R335") (pin "1") (pinfunction "1_1") (pintype "passive"))
      (node (ref "R363") (pin "2") (pinfunction "2_2") (pintype "passive"))
      (node (ref "R364") (pin "2") (pinfunction "2_2") (pintype "passive"))
      (node (ref "R365") (pin "2") (pinfunction "2_2") (pintype "passive"))
      (node (ref "R366") (pin "2") (pinfunction "2_2") (pintype "passive"))
      (node (ref "R384") (pin "1") (pinfunction "1_1") (pintype "passive"))
      (node (ref "R385") (pin "1") (pinfunction "1_1") (pintype "passive"))
      (node (ref "R390") (pin "1") (pinfunction "1_1") (pintype "passive"))
      (node (ref "R4") (pin "2") (pinfunction "2_2") (pintype "passive"))
      (node (ref "R402") (pin "1") (pinfunction "1_1") (pintype "passive"))
      (node (ref "R406") (pin "1") (pinfunction "1_1") (pintype "passive"))
      (node (ref "R409") (pin "2") (pinfunction "2_2") (pintype "passive"))
      (node (ref "R410") (pin "2") (pinfunction "2_2") (pintype "passive"))
      (node (ref "R411") (pin "2") (pinfunction "2_2") (pintype "passive"))
      (node (ref "R429") (pin "2") (pinfunction "2_2") (pintype "passive"))
      (node (ref "R435") (pin "1") (pinfunction "1_1") (pintype "passive"))
      (node (ref "R48") (pin "2") (pinfunction "2_2") (pintype "passive"))
      (node (ref "R49") (pin "2") (pinfunction "2_2") (pintype "passive"))
      (node (ref "R5") (pin "2") (pinfunction "2_2") (pintype "passive"))
      (node (ref "R50") (pin "2") (pinfunction "2_2") (pintype "passive"))
      (node (ref "R502") (pin "1") (pinfunction "1_1") (pintype "passive"))
      (node (ref "R506") (pin "1") (pinfunction "1_1") (pintype "passive"))
      (node (ref "R509") (pin "2") (pinfunction "2_2") (pintype "passive"))
      (node (ref "R51") (pin "2") (pinfunction "2_2") (pintype "passive"))
      (node (ref "R510") (pin "2") (pinfunction "2_2") (pintype "passive"))
      (node (ref "R511") (pin "2") (pinfunction "2_2") (pintype "passive"))
      (node (ref "R529") (pin "2") (pinfunction "2_2") (pintype "passive"))
      (node (ref "R535") (pin "1") (pinfunction "1_1") (pintype "passive"))
      (node (ref "R6") (pin "2") (pinfunction "2_2") (pintype "passive"))
      (node (ref "R602") (pin "1") (pinfunction "1_1") (pintype "passive"))
      (node (ref "R606") (pin "1") (pinfunction "1_1") (pintype "passive"))
      (node (ref "R609") (pin "2") (pinfunction "2_2") (pintype "passive"))
      (node (ref "R610") (pin "2") (pinfunction "2_2") (pintype "passive"))
      (node (ref "R611") (pin "2") (pinfunction "2_2") (pintype "passive"))
      (node (ref "R629") (pin "2") (pinfunction "2_2") (pintype "passive"))
      (node (ref "R635") (pin "1") (pinfunction "1_1") (pintype "passive"))
      (node (ref "R69") (pin "1") (pinfunction "1_1") (pintype "passive"))
      (node (ref "R70") (pin "1") (pinfunction "1_1") (pintype "passive"))
      (node (ref "R75") (pin "1") (pinfunction "1_1") (pintype "passive"))
      (node (ref "R93") (pin "2") (pinfunction "2_2") (pintype "passive"))
      (node (ref "R94") (pin "2") (pinfunction "2_2") (pintype "passive"))
      (node (ref "R95") (pin "2") (pinfunction "2_2") (pintype "passive"))
      (node (ref "R96") (pin "2") (pinfunction "2_2") (pintype "passive"))
      (node (ref "TP114") (pin "TP") (pinfunction "PP_TP") (pintype "input"))
      (node (ref "TP12") (pin "TP") (pinfunction "PP_TP") (pintype "input"))
      (node (ref "TP137") (pin "TP") (pinfunction "PP_TP") (pintype "input"))
      (node (ref "TP160") (pin "TP") (pinfunction "PP_TP") (pintype "input"))
      (node (ref "TP183") (pin "TP") (pinfunction "PP_TP") (pintype "input"))
      (node (ref "TP206") (pin "TP") (pinfunction "PP_TP") (pintype "input"))
      (node (ref "TP229") (pin "TP") (pinfunction "PP_TP") (pintype "input"))
      (node (ref "TP252") (pin "TP") (pinfunction "PP_TP") (pintype "input"))
      (node (ref "TP275") (pin "TP") (pinfunction "PP_TP") (pintype "input"))
      (node (ref "TP45") (pin "TP") (pinfunction "PP_TP") (pintype "input"))
      (node (ref "TP68") (pin "TP") (pinfunction "PP_TP") (pintype "input"))
      (node (ref "TP91") (pin "TP") (pinfunction "PP_TP") (pintype "input"))
      (node (ref "X1") (pin "6") (pinfunction "6_6") (pintype "passive"))
      (node (ref "X10") (pin "6") (pinfunction "6_6") (pintype "passive"))
      (node (ref "X101") (pin "6") (pinfunction "6_6") (pintype "passive"))
      (node (ref "X103") (pin "1") (pinfunction "S_1") (pintype "passive"))
      (node (ref "X11") (pin "1") (pinfunction "S_1") (pintype "passive"))
      (node (ref "X13") (pin "6") (pinfunction "6_6") (pintype "passive"))
      (node (ref "X14") (pin "1") (pinfunction "S_1") (pintype "passive"))
      (node (ref "X16") (pin "6") (pinfunction "6_6") (pintype "passive"))
      (node (ref "X17") (pin "1") (pinfunction "S_1") (pintype "passive"))
      (node (ref "X2") (pin "1") (pinfunction "S_1") (pintype "passive"))
      (node (ref "X201") (pin "6") (pinfunction "6_6") (pintype "passive"))
      (node (ref "X203") (pin "1") (pinfunction "S_1") (pintype "passive"))
      (node (ref "X301") (pin "6") (pinfunction "6_6") (pintype "passive"))
      (node (ref "X303") (pin "1") (pinfunction "S_1") (pintype "passive"))
      (node (ref "X4") (pin "6") (pinfunction "6_6") (pintype "passive"))
      (node (ref "X401") (pin "6") (pinfunction "6_6") (pintype "passive"))
      (node (ref "X403") (pin "1") (pinfunction "S_1") (pintype "passive"))
      (node (ref "X5") (pin "1") (pinfunction "S_1") (pintype "passive"))
      (node (ref "X501") (pin "6") (pinfunction "6_6") (pintype "passive"))
      (node (ref "X503") (pin "1") (pinfunction "S_1") (pintype "passive"))
      (node (ref "X601") (pin "6") (pinfunction "6_6") (pintype "passive"))
      (node (ref "X603") (pin "1") (pinfunction "S_1") (pintype "passive"))
      (node (ref "X7") (pin "6") (pinfunction "6_6") (pintype "passive"))
      (node (ref "X8") (pin "1") (pinfunction "S_1") (pintype "passive"))
    )
    (net (code "3") (name "GND") (class "Default")
      (node (ref "1") (pin "12") (pinfunction "KL_12") (pintype "passive"))
      (node (ref "11") (pin "12") (pinfunction "KL_12") (pintype "passive"))
      (node (ref "13") (pin "12") (pinfunction "KL_12") (pintype "passive"))
      (node (ref "15") (pin "12") (pinfunction "KL_12") (pintype "passive"))
      (node (ref "17") (pin "12") (pinfunction "KL_12") (pintype "passive"))
      (node (ref "19") (pin "12") (pinfunction "KL_12") (pintype "passive"))
      (node (ref "21") (pin "12") (pinfunction "KL_12") (pintype "passive"))
      (node (ref "23") (pin "12") (pinfunction "KL_12") (pintype "passive"))
      (node (ref "3") (pin "12") (pinfunction "KL_12") (pintype "passive"))
      (node (ref "5") (pin "12") (pinfunction "KL_12") (pintype "passive"))
      (node (ref "7") (pin "12") (pinfunction "KL_12") (pintype "passive"))
      (node (ref "9") (pin "12") (pinfunction "KL_12") (pintype "passive"))
      (node (ref "C1") (pin "2") (pinfunction "2_2") (pintype "passive"))
      (node (ref "C10") (pin "2") (pinfunction "2_2") (pintype "passive"))
      (node (ref "C101") (pin "2") (pinfunction "2_2") (pintype "passive"))
      (node (ref "C102") (pin "2") (pinfunction "2_2") (pintype "passive"))
      (node (ref "C103") (pin "2") (pinfunction "2_2") (pintype "passive"))
      (node (ref "C104") (pin "2") (pinfunction "2_2") (pintype "passive"))
      (node (ref "C105") (pin "2") (pinfunction "2_2") (pintype "passive"))
      (node (ref "C106") (pin "1") (pinfunction "1_1") (pintype "passive"))
      (node (ref "C107") (pin "2") (pinfunction "2_2") (pintype "passive"))
      (node (ref "C108") (pin "2") (pinfunction "2_2") (pintype "passive"))
      (node (ref "C109") (pin "1") (pinfunction "1_1") (pintype "passive"))
      (node (ref "C11") (pin "2") (pinfunction "2_2") (pintype "passive"))
      (node (ref "C110") (pin "2") (pinfunction "2_2") (pintype "passive"))
      (node (ref "C12") (pin "2") (pinfunction "2_2") (pintype "passive"))
      (node (ref "C13") (pin "2") (pinfunction "2_2") (pintype "passive"))
      (node (ref "C14") (pin "2") (pinfunction "2_2") (pintype "passive"))
      (node (ref "C15") (pin "2") (pinfunction "2_2") (pintype "passive"))
      (node (ref "C16") (pin "1") (pinfunction "1_1") (pintype "passive"))
      (node (ref "C17") (pin "1") (pinfunction "1_1") (pintype "passive"))
      (node (ref "C18") (pin "2") (pinfunction "2_2") (pintype "passive"))
      (node (ref "C19") (pin "2") (pinfunction "2_2") (pintype "passive"))
      (node (ref "C2") (pin "2") (pinfunction "2_2") (pintype "passive"))
      (node (ref "C20") (pin "2") (pinfunction "2_2") (pintype "passive"))
      (node (ref "C201") (pin "2") (pinfunction "2_2") (pintype "passive"))
      (node (ref "C202") (pin "2") (pinfunction "2_2") (pintype "passive"))
      (node (ref "C203") (pin "2") (pinfunction "2_2") (pintype "passive"))
      (node (ref "C204") (pin "2") (pinfunction "2_2") (pintype "passive"))
      (node (ref "C205") (pin "2") (pinfunction "2_2") (pintype "passive"))
      (node (ref "C206") (pin "1") (pinfunction "1_1") (pintype "passive"))
      (node (ref "C207") (pin "2") (pinfunction "2_2") (pintype "passive"))
      (node (ref "C208") (pin "2") (pinfunction "2_2") (pintype "passive"))
      (node (ref "C209") (pin "1") (pinfunction "1_1") (pintype "passive"))
      (node (ref "C21") (pin "2") (pinfunction "2_2") (pintype "passive"))
      (node (ref "C210") (pin "2") (pinfunction "2_2") (pintype "passive"))
      (node (ref "C22") (pin "2") (pinfunction "2_2") (pintype "passive"))
      (node (ref "C23") (pin "2") (pinfunction "2_2") (pintype "passive"))
      (node (ref "C24") (pin "2") (pinfunction "2_2") (pintype "passive"))
      (node (ref "C25") (pin "2") (pinfunction "2_2") (pintype "passive"))
      (node (ref "C26") (pin "1") (pinfunction "1_1") (pintype "passive"))
      (node (ref "C27") (pin "1") (pinfunction "1_1") (pintype "passive"))
      (node (ref "C28") (pin "2") (pinfunction "2_2") (pintype "passive"))
      (node (ref "C29") (pin "2") (pinfunction "2_2") (pintype "passive"))
      (node (ref "C3") (pin "2") (pinfunction "2_2") (pintype "passive"))
      (node (ref "C30") (pin "2") (pinfunction "2_2") (pintype "passive"))
      (node (ref "C301") (pin "2") (pinfunction "2_2") (pintype "passive"))
      (node (ref "C302") (pin "2") (pinfunction "2_2") (pintype "passive"))
      (node (ref "C303") (pin "2") (pinfunction "2_2") (pintype "passive"))
      (node (ref "C304") (pin "2") (pinfunction "2_2") (pintype "passive"))
      (node (ref "C305") (pin "2") (pinfunction "2_2") (pintype "passive"))
      (node (ref "C306") (pin "1") (pinfunction "1_1") (pintype "passive"))
      (node (ref "C307") (pin "2") (pinfunction "2_2") (pintype "passive"))
      (node (ref "C308") (pin "2") (pinfunction "2_2") (pintype "passive"))
      (node (ref "C309") (pin "1") (pinfunction "1_1") (pintype "passive"))
      (node (ref "C31") (pin "2") (pinfunction "2_2") (pintype "passive"))
      (node (ref "C310") (pin "2") (pinfunction "2_2") (pintype "passive"))
      (node (ref "C32") (pin "2") (pinfunction "2_2") (pintype "passive"))
      (node (ref "C33") (pin "2") (pinfunction "2_2") (pintype "passive"))
      (node (ref "C34") (pin "2") (pinfunction "2_2") (pintype "passive"))
      (node (ref "C35") (pin "2") (pinfunction "2_2") (pintype "passive"))
      (node (ref "C36") (pin "1") (pinfunction "1_1") (pintype "passive"))
      (node (ref "C37") (pin "1") (pinfunction "1_1") (pintype "passive"))
      (node (ref "C38") (pin "2") (pinfunction "2_2") (pintype "passive"))
      (node (ref "C39") (pin "2") (pinfunction "2_2") (pintype "passive"))
      (node (ref "C4") (pin "2") (pinfunction "2_2") (pintype "passive"))
      (node (ref "C40") (pin "2") (pinfunction "2_2") (pintype "passive"))
      (node (ref "C401") (pin "2") (pinfunction "2_2") (pintype "passive"))
      (node (ref "C402") (pin "2") (pinfunction "2_2") (pintype "passive"))
      (node (ref "C403") (pin "2") (pinfunction "2_2") (pintype "passive"))
      (node (ref "C404") (pin "2") (pinfunction "2_2") (pintype "passive"))
      (node (ref "C405") (pin "2") (pinfunction "2_2") (pintype "passive"))
      (node (ref "C406") (pin "1") (pinfunction "1_1") (pintype "passive"))
      (node (ref "C407") (pin "2") (pinfunction "2_2") (pintype "passive"))
      (node (ref "C408") (pin "2") (pinfunction "2_2") (pintype "passive"))
      (node (ref "C409") (pin "1") (pinfunction "1_1") (pintype "passive"))
      (node (ref "C41") (pin "2") (pinfunction "2_2") (pintype "passive"))
      (node (ref "C410") (pin "2") (pinfunction "2_2") (pintype "passive"))
      (node (ref "C42") (pin "2") (pinfunction "2_2") (pintype "passive"))
      (node (ref "C43") (pin "2") (pinfunction "2_2") (pintype "passive"))
      (node (ref "C44") (pin "2") (pinfunction "2_2") (pintype "passive"))
      (node (ref "C45") (pin "2") (pinfunction "2_2") (pintype "passive"))
      (node (ref "C46") (pin "1") (pinfunction "1_1") (pintype "passive"))
      (node (ref "C47") (pin "1") (pinfunction "1_1") (pintype "passive"))
      (node (ref "C48") (pin "2") (pinfunction "2_2") (pintype "passive"))
      (node (ref "C49") (pin "2") (pinfunction "2_2") (pintype "passive"))
      (node (ref "C5") (pin "2") (pinfunction "2_2") (pintype "passive"))
      (node (ref "C50") (pin "2") (pinfunction "2_2") (pintype "passive"))
      (node (ref "C501") (pin "2") (pinfunction "2_2") (pintype "passive"))
      (node (ref "C502") (pin "2") (pinfunction "2_2") (pintype "passive"))
      (node (ref "C503") (pin "2") (pinfunction "2_2") (pintype "passive"))
      (node (ref "C504") (pin "2") (pinfunction "2_2") (pintype "passive"))
      (node (ref "C505") (pin "2") (pinfunction "2_2") (pintype "passive"))
      (node (ref "C506") (pin "1") (pinfunction "1_1") (pintype "passive"))
      (node (ref "C507") (pin "2") (pinfunction "2_2") (pintype "passive"))
      (node (ref "C508") (pin "2") (pinfunction "2_2") (pintype "passive"))
      (node (ref "C509") (pin "1") (pinfunction "1_1") (pintype "passive"))
      (node (ref "C51") (pin "2") (pinfunction "2_2") (pintype "passive"))
      (node (ref "C510") (pin "2") (pinfunction "2_2") (pintype "passive"))
      (node (ref "C52") (pin "2") (pinfunction "2_2") (pintype "passive"))
      (node (ref "C53") (pin "2") (pinfunction "2_2") (pintype "passive"))
      (node (ref "C54") (pin "2") (pinfunction "2_2") (pintype "passive"))
      (node (ref "C55") (pin "2") (pinfunction "2_2") (pintype "passive"))
      (node (ref "C56") (pin "1") (pinfunction "1_1") (pintype "passive"))
      (node (ref "C57") (pin "1") (pinfunction "1_1") (pintype "passive"))
      (node (ref "C58") (pin "2") (pinfunction "2_2") (pintype "passive"))
      (node (ref "C59") (pin "2") (pinfunction "2_2") (pintype "passive"))
      (node (ref "C6") (pin "1") (pinfunction "1_1") (pintype "passive"))
      (node (ref "C60") (pin "2") (pinfunction "2_2") (pintype "passive"))
      (node (ref "C601") (pin "2") (pinfunction "2_2") (pintype "passive"))
      (node (ref "C602") (pin "2") (pinfunction "2_2") (pintype "passive"))
      (node (ref "C603") (pin "2") (pinfunction "2_2") (pintype "passive"))
      (node (ref "C604") (pin "2") (pinfunction "2_2") (pintype "passive"))
      (node (ref "C605") (pin "2") (pinfunction "2_2") (pintype "passive"))
      (node (ref "C606") (pin "1") (pinfunction "1_1") (pintype "passive"))
      (node (ref "C607") (pin "2") (pinfunction "2_2") (pintype "passive"))
      (node (ref "C608") (pin "2") (pinfunction "2_2") (pintype "passive"))
      (node (ref "C609") (pin "1") (pinfunction "1_1") (pintype "passive"))
      (node (ref "C610") (pin "2") (pinfunction "2_2") (pintype "passive"))
      (node (ref "C7") (pin "1") (pinfunction "1_1") (pintype "passive"))
      (node (ref "C8") (pin "2") (pinfunction "2_2") (pintype "passive"))
      (node (ref "C9") (pin "2") (pinfunction "2_2") (pintype "passive"))
      (node (ref "D101") (pin "A") (pinfunction "A_A") (pintype "passive"))
      (node (ref "D105") (pin "1") (pinfunction "+_1") (pintype "passive"))
      (node (ref "D11") (pin "A") (pinfunction "A_A") (pintype "passive"))
      (node (ref "D20") (pin "1") (pinfunction "+_1") (pintype "passive"))
      (node (ref "D201") (pin "A") (pinfunction "A_A") (pintype "passive"))
      (node (ref "D205") (pin "1") (pinfunction "+_1") (pintype "passive"))
      (node (ref "D22") (pin "A") (pinfunction "A_A") (pintype "passive"))
      (node (ref "D301") (pin "A") (pinfunction "A_A") (pintype "passive"))
      (node (ref "D305") (pin "1") (pinfunction "+_1") (pintype "passive"))
      (node (ref "D31") (pin "1") (pinfunction "+_1") (pintype "passive"))
      (node (ref "D33") (pin "A") (pinfunction "A_A") (pintype "passive"))
      (node (ref "D401") (pin "A") (pinfunction "A_A") (pintype "passive"))
      (node (ref "D405") (pin "1") (pinfunction "+_1") (pintype "passive"))
      (node (ref "D42") (pin "1") (pinfunction "+_1") (pintype "passive"))
      (node (ref "D44") (pin "A") (pinfunction "A_A") (pintype "passive"))
      (node (ref "D501") (pin "A") (pinfunction "A_A") (pintype "passive"))
      (node (ref "D505") (pin "1") (pinfunction "+_1") (pintype "passive"))
      (node (ref "D53") (pin "1") (pinfunction "+_1") (pintype "passive"))
      (node (ref "D55") (pin "A") (pinfunction "A_A") (pintype "passive"))
      (node (ref "D601") (pin "A") (pinfunction "A_A") (pintype "passive"))
      (node (ref "D605") (pin "1") (pinfunction "+_1") (pintype "passive"))
      (node (ref "D64") (pin "1") (pinfunction "+_1") (pintype "passive"))
      (node (ref "D66") (pin "A") (pinfunction "A_A") (pintype "passive"))
      (node (ref "D9") (pin "1") (pinfunction "+_1") (pintype "passive"))
      (node (ref "IC1") (pin "11") (pinfunction "D_11") (pintype "input"))
      (node (ref "IC1") (pin "8") (pinfunction "VSS_8") (pintype "power_in"))
      (node (ref "IC10") (pin "4") (pinfunction "V-_4") (pintype "power_in"))
      (node (ref "IC101") (pin "4") (pinfunction "V-_4") (pintype "power_in"))
      (node (ref "IC102") (pin "2") (pinfunction "GND_2") (pintype "input"))
      (node (ref "IC102") (pin "2@1") (pinfunction "GND_2@1") (pintype "input"))
      (node (ref "IC103") (pin "GND") (pinfunction "GND_GND") (pintype "input"))
      (node (ref "IC104") (pin "2") (pinfunction "GND_2") (pintype "input"))
      (node (ref "IC104") (pin "2@1") (pinfunction "GND_2@1") (pintype "input"))
      (node (ref "IC105") (pin "11") (pinfunction "D_11") (pintype "input"))
      (node (ref "IC105") (pin "8") (pinfunction "VSS_8") (pintype "power_in"))
      (node (ref "IC107") (pin "8") (pinfunction "GND_8") (pintype "power_in"))
      (node (ref "IC108") (pin "10") (pinfunction "-IN_10") (pintype "input"))
      (node (ref "IC108") (pin "11") (pinfunction "+IN_11") (pintype "input"))
      (node (ref "IC108") (pin "12") (pinfunction "GND_12") (pintype "power_in"))
      (node (ref "IC11") (pin "11") (pinfunction "D_11") (pintype "input"))
      (node (ref "IC11") (pin "8") (pinfunction "VSS_8") (pintype "power_in"))
      (node (ref "IC110") (pin "1") (pinfunction "GND_1") (pintype "power_in"))
      (node (ref "IC111") (pin "1") (pinfunction "T1_1") (pintype "input"))
      (node (ref "IC111") (pin "15") (pinfunction "T1_15") (pintype "input"))
      (node (ref "IC111") (pin "4") (pinfunction "A_4") (pintype "input"))
      (node (ref "IC111") (pin "8") (pinfunction "VSS_8") (pintype "power_in"))
      (node (ref "IC12") (pin "GND") (pinfunction "GND_GND") (pintype "input"))
      (node (ref "IC14") (pin "8") (pinfunction "GND_8") (pintype "power_in"))
      (node (ref "IC15") (pin "10") (pinfunction "-IN_10") (pintype "input"))
      (node (ref "IC15") (pin "11") (pinfunction "+IN_11") (pintype "input"))
      (node (ref "IC15") (pin "12") (pinfunction "GND_12") (pintype "power_in"))
      (node (ref "IC16") (pin "2") (pinfunction "GND_2") (pintype "input"))
      (node (ref "IC16") (pin "2@1") (pinfunction "GND_2@1") (pintype "input"))
      (node (ref "IC17") (pin "1") (pinfunction "GND_1") (pintype "power_in"))
      (node (ref "IC18") (pin "1") (pinfunction "T1_1") (pintype "input"))
      (node (ref "IC18") (pin "15") (pinfunction "T1_15") (pintype "input"))
      (node (ref "IC18") (pin "4") (pinfunction "A_4") (pintype "input"))
      (node (ref "IC18") (pin "8") (pinfunction "VSS_8") (pintype "power_in"))
      (node (ref "IC19") (pin "2") (pinfunction "GND_2") (pintype "input"))
      (node (ref "IC19") (pin "2@1") (pinfunction "GND_2@1") (pintype "input"))
      (node (ref "IC2") (pin "GND") (pinfunction "GND_GND") (pintype "input"))
      (node (ref "IC20") (pin "4") (pinfunction "V-_4") (pintype "power_in"))
      (node (ref "IC201") (pin "4") (pinfunction "V-_4") (pintype "power_in"))
      (node (ref "IC202") (pin "2") (pinfunction "GND_2") (pintype "input"))
      (node (ref "IC202") (pin "2@1") (pinfunction "GND_2@1") (pintype "input"))
      (node (ref "IC203") (pin "GND") (pinfunction "GND_GND") (pintype "input"))
      (node (ref "IC204") (pin "2") (pinfunction "GND_2") (pintype "input"))
      (node (ref "IC204") (pin "2@1") (pinfunction "GND_2@1") (pintype "input"))
      (node (ref "IC205") (pin "11") (pinfunction "D_11") (pintype "input"))
      (node (ref "IC205") (pin "8") (pinfunction "VSS_8") (pintype "power_in"))
      (node (ref "IC207") (pin "8") (pinfunction "GND_8") (pintype "power_in"))
      (node (ref "IC208") (pin "10") (pinfunction "-IN_10") (pintype "input"))
      (node (ref "IC208") (pin "11") (pinfunction "+IN_11") (pintype "input"))
      (node (ref "IC208") (pin "12") (pinfunction "GND_12") (pintype "power_in"))
      (node (ref "IC21") (pin "11") (pinfunction "D_11") (pintype "input"))
      (node (ref "IC21") (pin "8") (pinfunction "VSS_8") (pintype "power_in"))
      (node (ref "IC210") (pin "1") (pinfunction "GND_1") (pintype "power_in"))
      (node (ref "IC211") (pin "1") (pinfunction "T1_1") (pintype "input"))
      (node (ref "IC211") (pin "15") (pinfunction "T1_15") (pintype "input"))
      (node (ref "IC211") (pin "4") (pinfunction "A_4") (pintype "input"))
      (node (ref "IC211") (pin "8") (pinfunction "VSS_8") (pintype "power_in"))
      (node (ref "IC22") (pin "GND") (pinfunction "GND_GND") (pintype "input"))
      (node (ref "IC24") (pin "8") (pinfunction "GND_8") (pintype "power_in"))
      (node (ref "IC25") (pin "10") (pinfunction "-IN_10") (pintype "input"))
      (node (ref "IC25") (pin "11") (pinfunction "+IN_11") (pintype "input"))
      (node (ref "IC25") (pin "12") (pinfunction "GND_12") (pintype "power_in"))
      (node (ref "IC26") (pin "2") (pinfunction "GND_2") (pintype "input"))
      (node (ref "IC26") (pin "2@1") (pinfunction "GND_2@1") (pintype "input"))
      (node (ref "IC27") (pin "1") (pinfunction "GND_1") (pintype "power_in"))
      (node (ref "IC28") (pin "1") (pinfunction "T1_1") (pintype "input"))
      (node (ref "IC28") (pin "15") (pinfunction "T1_15") (pintype "input"))
      (node (ref "IC28") (pin "4") (pinfunction "A_4") (pintype "input"))
      (node (ref "IC28") (pin "8") (pinfunction "VSS_8") (pintype "power_in"))
      (node (ref "IC29") (pin "2") (pinfunction "GND_2") (pintype "input"))
      (node (ref "IC29") (pin "2@1") (pinfunction "GND_2@1") (pintype "input"))
      (node (ref "IC30") (pin "4") (pinfunction "V-_4") (pintype "power_in"))
      (node (ref "IC301") (pin "4") (pinfunction "V-_4") (pintype "power_in"))
      (node (ref "IC302") (pin "2") (pinfunction "GND_2") (pintype "input"))
      (node (ref "IC302") (pin "2@1") (pinfunction "GND_2@1") (pintype "input"))
      (node (ref "IC303") (pin "GND") (pinfunction "GND_GND") (pintype "input"))
      (node (ref "IC304") (pin "2") (pinfunction "GND_2") (pintype "input"))
      (node (ref "IC304") (pin "2@1") (pinfunction "GND_2@1") (pintype "input"))
      (node (ref "IC305") (pin "11") (pinfunction "D_11") (pintype "input"))
      (node (ref "IC305") (pin "8") (pinfunction "VSS_8") (pintype "power_in"))
      (node (ref "IC307") (pin "8") (pinfunction "GND_8") (pintype "power_in"))
      (node (ref "IC308") (pin "10") (pinfunction "-IN_10") (pintype "input"))
      (node (ref "IC308") (pin "11") (pinfunction "+IN_11") (pintype "input"))
      (node (ref "IC308") (pin "12") (pinfunction "GND_12") (pintype "power_in"))
      (node (ref "IC31") (pin "11") (pinfunction "D_11") (pintype "input"))
      (node (ref "IC31") (pin "8") (pinfunction "VSS_8") (pintype "power_in"))
      (node (ref "IC310") (pin "1") (pinfunction "GND_1") (pintype "power_in"))
      (node (ref "IC311") (pin "1") (pinfunction "T1_1") (pintype "input"))
      (node (ref "IC311") (pin "15") (pinfunction "T1_15") (pintype "input"))
      (node (ref "IC311") (pin "4") (pinfunction "A_4") (pintype "input"))
      (node (ref "IC311") (pin "8") (pinfunction "VSS_8") (pintype "power_in"))
      (node (ref "IC32") (pin "GND") (pinfunction "GND_GND") (pintype "input"))
      (node (ref "IC34") (pin "8") (pinfunction "GND_8") (pintype "power_in"))
      (node (ref "IC35") (pin "10") (pinfunction "-IN_10") (pintype "input"))
      (node (ref "IC35") (pin "11") (pinfunction "+IN_11") (pintype "input"))
      (node (ref "IC35") (pin "12") (pinfunction "GND_12") (pintype "power_in"))
      (node (ref "IC36") (pin "2") (pinfunction "GND_2") (pintype "input"))
      (node (ref "IC36") (pin "2@1") (pinfunction "GND_2@1") (pintype "input"))
      (node (ref "IC37") (pin "1") (pinfunction "GND_1") (pintype "power_in"))
      (node (ref "IC38") (pin "1") (pinfunction "T1_1") (pintype "input"))
      (node (ref "IC38") (pin "15") (pinfunction "T1_15") (pintype "input"))
      (node (ref "IC38") (pin "4") (pinfunction "A_4") (pintype "input"))
      (node (ref "IC38") (pin "8") (pinfunction "VSS_8") (pintype "power_in"))
      (node (ref "IC39") (pin "2") (pinfunction "GND_2") (pintype "input"))
      (node (ref "IC39") (pin "2@1") (pinfunction "GND_2@1") (pintype "input"))
      (node (ref "IC4") (pin "8") (pinfunction "GND_8") (pintype "power_in"))
      (node (ref "IC40") (pin "4") (pinfunction "V-_4") (pintype "power_in"))
      (node (ref "IC401") (pin "4") (pinfunction "V-_4") (pintype "power_in"))
      (node (ref "IC402") (pin "2") (pinfunction "GND_2") (pintype "input"))
      (node (ref "IC402") (pin "2@1") (pinfunction "GND_2@1") (pintype "input"))
      (node (ref "IC403") (pin "GND") (pinfunction "GND_GND") (pintype "input"))
      (node (ref "IC404") (pin "2") (pinfunction "GND_2") (pintype "input"))
      (node (ref "IC404") (pin "2@1") (pinfunction "GND_2@1") (pintype "input"))
      (node (ref "IC405") (pin "11") (pinfunction "D_11") (pintype "input"))
      (node (ref "IC405") (pin "8") (pinfunction "VSS_8") (pintype "power_in"))
      (node (ref "IC407") (pin "8") (pinfunction "GND_8") (pintype "power_in"))
      (node (ref "IC408") (pin "10") (pinfunction "-IN_10") (pintype "input"))
      (node (ref "IC408") (pin "11") (pinfunction "+IN_11") (pintype "input"))
      (node (ref "IC408") (pin "12") (pinfunction "GND_12") (pintype "power_in"))
      (node (ref "IC41") (pin "11") (pinfunction "D_11") (pintype "input"))
      (node (ref "IC41") (pin "8") (pinfunction "VSS_8") (pintype "power_in"))
      (node (ref "IC410") (pin "1") (pinfunction "GND_1") (pintype "power_in"))
      (node (ref "IC411") (pin "1") (pinfunction "T1_1") (pintype "input"))
      (node (ref "IC411") (pin "15") (pinfunction "T1_15") (pintype "input"))
      (node (ref "IC411") (pin "4") (pinfunction "A_4") (pintype "input"))
      (node (ref "IC411") (pin "8") (pinfunction "VSS_8") (pintype "power_in"))
      (node (ref "IC42") (pin "GND") (pinfunction "GND_GND") (pintype "input"))
      (node (ref "IC44") (pin "8") (pinfunction "GND_8") (pintype "power_in"))
      (node (ref "IC45") (pin "10") (pinfunction "-IN_10") (pintype "input"))
      (node (ref "IC45") (pin "11") (pinfunction "+IN_11") (pintype "input"))
      (node (ref "IC45") (pin "12") (pinfunction "GND_12") (pintype "power_in"))
      (node (ref "IC46") (pin "2") (pinfunction "GND_2") (pintype "input"))
      (node (ref "IC46") (pin "2@1") (pinfunction "GND_2@1") (pintype "input"))
      (node (ref "IC47") (pin "1") (pinfunction "GND_1") (pintype "power_in"))
      (node (ref "IC48") (pin "1") (pinfunction "T1_1") (pintype "input"))
      (node (ref "IC48") (pin "15") (pinfunction "T1_15") (pintype "input"))
      (node (ref "IC48") (pin "4") (pinfunction "A_4") (pintype "input"))
      (node (ref "IC48") (pin "8") (pinfunction "VSS_8") (pintype "power_in"))
      (node (ref "IC49") (pin "2") (pinfunction "GND_2") (pintype "input"))
      (node (ref "IC49") (pin "2@1") (pinfunction "GND_2@1") (pintype "input"))
      (node (ref "IC5") (pin "10") (pinfunction "-IN_10") (pintype "input"))
      (node (ref "IC5") (pin "11") (pinfunction "+IN_11") (pintype "input"))
      (node (ref "IC5") (pin "12") (pinfunction "GND_12") (pintype "power_in"))
      (node (ref "IC50") (pin "4") (pinfunction "V-_4") (pintype "power_in"))
      (node (ref "IC501") (pin "4") (pinfunction "V-_4") (pintype "power_in"))
      (node (ref "IC502") (pin "2") (pinfunction "GND_2") (pintype "input"))
      (node (ref "IC502") (pin "2@1") (pinfunction "GND_2@1") (pintype "input"))
      (node (ref "IC503") (pin "GND") (pinfunction "GND_GND") (pintype "input"))
      (node (ref "IC504") (pin "2") (pinfunction "GND_2") (pintype "input"))
      (node (ref "IC504") (pin "2@1") (pinfunction "GND_2@1") (pintype "input"))
      (node (ref "IC505") (pin "11") (pinfunction "D_11") (pintype "input"))
      (node (ref "IC505") (pin "8") (pinfunction "VSS_8") (pintype "power_in"))
      (node (ref "IC507") (pin "8") (pinfunction "GND_8") (pintype "power_in"))
      (node (ref "IC508") (pin "10") (pinfunction "-IN_10") (pintype "input"))
      (node (ref "IC508") (pin "11") (pinfunction "+IN_11") (pintype "input"))
      (node (ref "IC508") (pin "12") (pinfunction "GND_12") (pintype "power_in"))
      (node (ref "IC51") (pin "11") (pinfunction "D_11") (pintype "input"))
      (node (ref "IC51") (pin "8") (pinfunction "VSS_8") (pintype "power_in"))
      (node (ref "IC510") (pin "1") (pinfunction "GND_1") (pintype "power_in"))
      (node (ref "IC511") (pin "1") (pinfunction "T1_1") (pintype "input"))
      (node (ref "IC511") (pin "15") (pinfunction "T1_15") (pintype "input"))
      (node (ref "IC511") (pin "4") (pinfunction "A_4") (pintype "input"))
      (node (ref "IC511") (pin "8") (pinfunction "VSS_8") (pintype "power_in"))
      (node (ref "IC52") (pin "GND") (pinfunction "GND_GND") (pintype "input"))
      (node (ref "IC54") (pin "8") (pinfunction "GND_8") (pintype "power_in"))
      (node (ref "IC55") (pin "10") (pinfunction "-IN_10") (pintype "input"))
      (node (ref "IC55") (pin "11") (pinfunction "+IN_11") (pintype "input"))
      (node (ref "IC55") (pin "12") (pinfunction "GND_12") (pintype "power_in"))
      (node (ref "IC56") (pin "2") (pinfunction "GND_2") (pintype "input"))
      (node (ref "IC56") (pin "2@1") (pinfunction "GND_2@1") (pintype "input"))
      (node (ref "IC57") (pin "1") (pinfunction "GND_1") (pintype "power_in"))
      (node (ref "IC58") (pin "1") (pinfunction "T1_1") (pintype "input"))
      (node (ref "IC58") (pin "15") (pinfunction "T1_15") (pintype "input"))
      (node (ref "IC58") (pin "4") (pinfunction "A_4") (pintype "input"))
      (node (ref "IC58") (pin "8") (pinfunction "VSS_8") (pintype "power_in"))
      (node (ref "IC59") (pin "2") (pinfunction "GND_2") (pintype "input"))
      (node (ref "IC59") (pin "2@1") (pinfunction "GND_2@1") (pintype "input"))
      (node (ref "IC6") (pin "2") (pinfunction "GND_2") (pintype "input"))
      (node (ref "IC6") (pin "2@1") (pinfunction "GND_2@1") (pintype "input"))
      (node (ref "IC60") (pin "4") (pinfunction "V-_4") (pintype "power_in"))
      (node (ref "IC601") (pin "4") (pinfunction "V-_4") (pintype "power_in"))
      (node (ref "IC602") (pin "2") (pinfunction "GND_2") (pintype "input"))
      (node (ref "IC602") (pin "2@1") (pinfunction "GND_2@1") (pintype "input"))
      (node (ref "IC603") (pin "GND") (pinfunction "GND_GND") (pintype "input"))
      (node (ref "IC604") (pin "2") (pinfunction "GND_2") (pintype "input"))
      (node (ref "IC604") (pin "2@1") (pinfunction "GND_2@1") (pintype "input"))
      (node (ref "IC605") (pin "11") (pinfunction "D_11") (pintype "input"))
      (node (ref "IC605") (pin "8") (pinfunction "VSS_8") (pintype "power_in"))
      (node (ref "IC607") (pin "8") (pinfunction "GND_8") (pintype "power_in"))
      (node (ref "IC608") (pin "10") (pinfunction "-IN_10") (pintype "input"))
      (node (ref "IC608") (pin "11") (pinfunction "+IN_11") (pintype "input"))
      (node (ref "IC608") (pin "12") (pinfunction "GND_12") (pintype "power_in"))
      (node (ref "IC610") (pin "1") (pinfunction "GND_1") (pintype "power_in"))
      (node (ref "IC611") (pin "1") (pinfunction "T1_1") (pintype "input"))
      (node (ref "IC611") (pin "15") (pinfunction "T1_15") (pintype "input"))
      (node (ref "IC611") (pin "4") (pinfunction "A_4") (pintype "input"))
      (node (ref "IC611") (pin "8") (pinfunction "VSS_8") (pintype "power_in"))
      (node (ref "IC7") (pin "1") (pinfunction "GND_1") (pintype "power_in"))
      (node (ref "IC8") (pin "1") (pinfunction "T1_1") (pintype "input"))
      (node (ref "IC8") (pin "15") (pinfunction "T1_15") (pintype "input"))
      (node (ref "IC8") (pin "4") (pinfunction "A_4") (pintype "input"))
      (node (ref "IC8") (pin "8") (pinfunction "VSS_8") (pintype "power_in"))
      (node (ref "IC9") (pin "2") (pinfunction "GND_2") (pintype "input"))
      (node (ref "IC9") (pin "2@1") (pinfunction "GND_2@1") (pintype "input"))
      (node (ref "Q103") (pin "3") (pinfunction "E_3") (pintype "passive"))
      (node (ref "Q106") (pin "2") (pinfunction "S_2") (pintype "passive"))
      (node (ref "Q107") (pin "2") (pinfunction "S_2") (pintype "passive"))
      (node (ref "Q12") (pin "3") (pinfunction "E_3") (pintype "passive"))
      (node (ref "Q13") (pin "2") (pinfunction "S_2") (pintype "passive"))
      (node (ref "Q14") (pin "2") (pinfunction "S_2") (pintype "passive"))
      (node (ref "Q19") (pin "3") (pinfunction "E_3") (pintype "passive"))
      (node (ref "Q20") (pin "2") (pinfunction "S_2") (pintype "passive"))
      (node (ref "Q203") (pin "3") (pinfunction "E_3") (pintype "passive"))
      (node (ref "Q206") (pin "2") (pinfunction "S_2") (pintype "passive"))
      (node (ref "Q207") (pin "2") (pinfunction "S_2") (pintype "passive"))
      (node (ref "Q21") (pin "2") (pinfunction "S_2") (pintype "passive"))
      (node (ref "Q26") (pin "3") (pinfunction "E_3") (pintype "passive"))
      (node (ref "Q27") (pin "2") (pinfunction "S_2") (pintype "passive"))
      (node (ref "Q28") (pin "2") (pinfunction "S_2") (pintype "passive"))
      (node (ref "Q303") (pin "3") (pinfunction "E_3") (pintype "passive"))
      (node (ref "Q306") (pin "2") (pinfunction "S_2") (pintype "passive"))
      (node (ref "Q307") (pin "2") (pinfunction "S_2") (pintype "passive"))
      (node (ref "Q33") (pin "3") (pinfunction "E_3") (pintype "passive"))
      (node (ref "Q34") (pin "2") (pinfunction "S_2") (pintype "passive"))
      (node (ref "Q35") (pin "2") (pinfunction "S_2") (pintype "passive"))
      (node (ref "Q40") (pin "3") (pinfunction "E_3") (pintype "passive"))
      (node (ref "Q403") (pin "3") (pinfunction "E_3") (pintype "passive"))
      (node (ref "Q406") (pin "2") (pinfunction "S_2") (pintype "passive"))
      (node (ref "Q407") (pin "2") (pinfunction "S_2") (pintype "passive"))
      (node (ref "Q41") (pin "2") (pinfunction "S_2") (pintype "passive"))
      (node (ref "Q42") (pin "2") (pinfunction "S_2") (pintype "passive"))
      (node (ref "Q5") (pin "3") (pinfunction "E_3") (pintype "passive"))
      (node (ref "Q503") (pin "3") (pinfunction "E_3") (pintype "passive"))
      (node (ref "Q506") (pin "2") (pinfunction "S_2") (pintype "passive"))
      (node (ref "Q507") (pin "2") (pinfunction "S_2") (pintype "passive"))
      (node (ref "Q6") (pin "2") (pinfunction "S_2") (pintype "passive"))
      (node (ref "Q603") (pin "3") (pinfunction "E_3") (pintype "passive"))
      (node (ref "Q606") (pin "2") (pinfunction "S_2") (pintype "passive"))
      (node (ref "Q607") (pin "2") (pinfunction "S_2") (pintype "passive"))
      (node (ref "Q7") (pin "2") (pinfunction "S_2") (pintype "passive"))
      (node (ref "R101") (pin "2") (pinfunction "2_2") (pintype "passive"))
      (node (ref "R103") (pin "2") (pinfunction "2_2") (pintype "passive"))
      (node (ref "R107") (pin "1") (pinfunction "1_1") (pintype "passive"))
      (node (ref "R114") (pin "1") (pinfunction "1_1") (pintype "passive"))
      (node (ref "R123") (pin "1") (pinfunction "1_1") (pintype "passive"))
      (node (ref "R132") (pin "1") (pinfunction "1_1") (pintype "passive"))
      (node (ref "R136") (pin "1") (pinfunction "1_1") (pintype "passive"))
      (node (ref "R137") (pin "1") (pinfunction "1_1") (pintype "passive"))
      (node (ref "R139") (pin "2") (pinfunction "2_2") (pintype "passive"))
      (node (ref "R14") (pin "1") (pinfunction "1_1") (pintype "passive"))
      (node (ref "R141") (pin "2") (pinfunction "2_2") (pintype "passive"))
      (node (ref "R143") (pin "2") (pinfunction "2_2") (pintype "passive"))
      (node (ref "R149") (pin "1") (pinfunction "1_1") (pintype "passive"))
      (node (ref "R153") (pin "1") (pinfunction "1_1") (pintype "passive"))
      (node (ref "R154") (pin "2") (pinfunction "2_2") (pintype "passive"))
      (node (ref "R156") (pin "2") (pinfunction "2_2") (pintype "passive"))
      (node (ref "R164") (pin "2") (pinfunction "2_2") (pintype "passive"))
      (node (ref "R166") (pin "2") (pinfunction "2_2") (pintype "passive"))
      (node (ref "R169") (pin "1") (pinfunction "1_1") (pintype "passive"))
      (node (ref "R170") (pin "1") (pinfunction "1_1") (pintype "passive"))
      (node (ref "R178") (pin "1") (pinfunction "1_1") (pintype "passive"))
      (node (ref "R18") (pin "1") (pinfunction "1_1") (pintype "passive"))
      (node (ref "R180") (pin "2") (pinfunction "2_2") (pintype "passive"))
      (node (ref "R188") (pin "1") (pinfunction "1_1") (pintype "passive"))
      (node (ref "R19") (pin "2") (pinfunction "2_2") (pintype "passive"))
      (node (ref "R194") (pin "1") (pinfunction "1_1") (pintype "passive"))
      (node (ref "R198") (pin "1") (pinfunction "1_1") (pintype "passive"))
      (node (ref "R199") (pin "2") (pinfunction "2_2") (pintype "passive"))
      (node (ref "R201") (pin "2") (pinfunction "2_2") (pintype "passive"))
      (node (ref "R203") (pin "2") (pinfunction "2_2") (pintype "passive"))
      (node (ref "R204") (pin "2") (pinfunction "2_2") (pintype "passive"))
      (node (ref "R207") (pin "1") (pinfunction "1_1") (pintype "passive"))
      (node (ref "R21") (pin "2") (pinfunction "2_2") (pintype "passive"))
      (node (ref "R214") (pin "1") (pinfunction "1_1") (pintype "passive"))
      (node (ref "R223") (pin "1") (pinfunction "1_1") (pintype "passive"))
      (node (ref "R232") (pin "1") (pinfunction "1_1") (pintype "passive"))
      (node (ref "R236") (pin "1") (pinfunction "1_1") (pintype "passive"))
      (node (ref "R237") (pin "1") (pinfunction "1_1") (pintype "passive"))
      (node (ref "R239") (pin "2") (pinfunction "2_2") (pintype "passive"))
      (node (ref "R241") (pin "2") (pinfunction "2_2") (pintype "passive"))
      (node (ref "R243") (pin "2") (pinfunction "2_2") (pintype "passive"))
      (node (ref "R254") (pin "2") (pinfunction "2_2") (pintype "passive"))
      (node (ref "R256") (pin "2") (pinfunction "2_2") (pintype "passive"))
      (node (ref "R259") (pin "1") (pinfunction "1_1") (pintype "passive"))
      (node (ref "R260") (pin "1") (pinfunction "1_1") (pintype "passive"))
      (node (ref "R268") (pin "1") (pinfunction "1_1") (pintype "passive"))
      (node (ref "R270") (pin "2") (pinfunction "2_2") (pintype "passive"))
      (node (ref "R278") (pin "1") (pinfunction "1_1") (pintype "passive"))
      (node (ref "R284") (pin "1") (pinfunction "1_1") (pintype "passive"))
      (node (ref "R288") (pin "1") (pinfunction "1_1") (pintype "passive"))
      (node (ref "R289") (pin "2") (pinfunction "2_2") (pintype "passive"))
      (node (ref "R29") (pin "2") (pinfunction "2_2") (pintype "passive"))
      (node (ref "R291") (pin "2") (pinfunction "2_2") (pintype "passive"))
      (node (ref "R299") (pin "2") (pinfunction "2_2") (pintype "passive"))
      (node (ref "R301") (pin "2") (pinfunction "2_2") (pintype "passive"))
      (node (ref "R303") (pin "2") (pinfunction "2_2") (pintype "passive"))
      (node (ref "R304") (pin "2") (pinfunction "2_2") (pintype "passive"))
      (node (ref "R307") (pin "1") (pinfunction "1_1") (pintype "passive"))
      (node (ref "R31") (pin "2") (pinfunction "2_2") (pintype "passive"))
      (node (ref "R314") (pin "1") (pinfunction "1_1") (pintype "passive"))
      (node (ref "R323") (pin "1") (pinfunction "1_1") (pintype "passive"))
      (node (ref "R332") (pin "1") (pinfunction "1_1") (pintype "passive"))
      (node (ref "R336") (pin "1") (pinfunction "1_1") (pintype "passive"))
      (node (ref "R337") (pin "1") (pinfunction "1_1") (pintype "passive"))
      (node (ref "R339") (pin "2") (pinfunction "2_2") (pintype "passive"))
      (node (ref "R34") (pin "1") (pinfunction "1_1") (pintype "passive"))
      (node (ref "R341") (pin "2") (pinfunction "2_2") (pintype "passive"))
      (node (ref "R343") (pin "2") (pinfunction "2_2") (pintype "passive"))
      (node (ref "R349") (pin "1") (pinfunction "1_1") (pintype "passive"))
      (node (ref "R35") (pin "1") (pinfunction "1_1") (pintype "passive"))
      (node (ref "R350") (pin "1") (pinfunction "1_1") (pintype "passive"))
      (node (ref "R358") (pin "1") (pinfunction "1_1") (pintype "passive"))
      (node (ref "R360") (pin "2") (pinfunction "2_2") (pintype "passive"))
      (node (ref "R368") (pin "1") (pinfunction "1_1") (pintype "passive"))
      (node (ref "R374") (pin "1") (pinfunction "1_1") (pintype "passive"))
      (node (ref "R378") (pin "1") (pinfunction "1_1") (pintype "passive"))
      (node (ref "R379") (pin "2") (pinfunction "2_2") (pintype "passive"))
      (node (ref "R381") (pin "2") (pinfunction "2_2") (pintype "passive"))
      (node (ref "R389") (pin "2") (pinfunction "2_2") (pintype "passive"))
      (node (ref "R391") (pin "2") (pinfunction "2_2") (pintype "passive"))
      (node (ref "R394") (pin "1") (pinfunction "1_1") (pintype "passive"))
      (node (ref "R395") (pin "1") (pinfunction "1_1") (pintype "passive"))
      (node (ref "R401") (pin "2") (pinfunction "2_2") (pintype "passive"))
      (node (ref "R403") (pin "2") (pinfunction "2_2") (pintype "passive"))
      (node (ref "R407") (pin "1") (pinfunction "1_1") (pintype "passive"))
      (node (ref "R414") (pin "1") (pinfunction "1_1") (pintype "passive"))
      (node (ref "R423") (pin "1") (pinfunction "1_1") (pintype "passive"))
      (node (ref "R43") (pin "1") (pinfunction "1_1") (pintype "passive"))
      (node (ref "R432") (pin "1") (pinfunction "1_1") (pintype "passive"))
      (node (ref "R436") (pin "1") (pinfunction "1_1") (pintype "passive"))
      (node (ref "R437") (pin "1") (pinfunction "1_1") (pintype "passive"))
      (node (ref "R439") (pin "2") (pinfunction "2_2") (pintype "passive"))
      (node (ref "R441") (pin "2") (pinfunction "2_2") (pintype "passive"))
      (node (ref "R443") (pin "2") (pinfunction "2_2") (pintype "passive"))
      (node (ref "R448") (pin "1") (pinfunction "1_1") (pintype "passive"))
      (node (ref "R45") (pin "2") (pinfunction "2_2") (pintype "passive"))
      (node (ref "R450") (pin "2") (pinfunction "2_2") (pintype "passive"))
      (node (ref "R501") (pin "2") (pinfunction "2_2") (pintype "passive"))
      (node (ref "R503") (pin "2") (pinfunction "2_2") (pintype "passive"))
      (node (ref "R507") (pin "1") (pinfunction "1_1") (pintype "passive"))
      (node (ref "R514") (pin "1") (pinfunction "1_1") (pintype "passive"))
      (node (ref "R523") (pin "1") (pinfunction "1_1") (pintype "passive"))
      (node (ref "R53") (pin "1") (pinfunction "1_1") (pintype "passive"))
      (node (ref "R532") (pin "1") (pinfunction "1_1") (pintype "passive"))
      (node (ref "R536") (pin "1") (pinfunction "1_1") (pintype "passive"))
      (node (ref "R537") (pin "1") (pinfunction "1_1") (pintype "passive"))
      (node (ref "R539") (pin "2") (pinfunction "2_2") (pintype "passive"))
      (node (ref "R541") (pin "2") (pinfunction "2_2") (pintype "passive"))
      (node (ref "R543") (pin "2") (pinfunction "2_2") (pintype "passive"))
      (node (ref "R59") (pin "1") (pinfunction "1_1") (pintype "passive"))
      (node (ref "R601") (pin "2") (pinfunction "2_2") (pintype "passive"))
      (node (ref "R603") (pin "2") (pinfunction "2_2") (pintype "passive"))
      (node (ref "R607") (pin "1") (pinfunction "1_1") (pintype "passive"))
      (node (ref "R614") (pin "1") (pinfunction "1_1") (pintype "passive"))
      (node (ref "R623") (pin "1") (pinfunction "1_1") (pintype "passive"))
      (node (ref "R63") (pin "1") (pinfunction "1_1") (pintype "passive"))
      (node (ref "R632") (pin "1") (pinfunction "1_1") (pintype "passive"))
      (node (ref "R636") (pin "1") (pinfunction "1_1") (pintype "passive"))
      (node (ref "R637") (pin "1") (pinfunction "1_1") (pintype "passive"))
      (node (ref "R639") (pin "2") (pinfunction "2_2") (pintype "passive"))
      (node (ref "R64") (pin "2") (pinfunction "2_2") (pintype "passive"))
      (node (ref "R641") (pin "2") (pinfunction "2_2") (pintype "passive"))
      (node (ref "R643") (pin "2") (pinfunction "2_2") (pintype "passive"))
      (node (ref "R66") (pin "2") (pinfunction "2_2") (pintype "passive"))
      (node (ref "R74") (pin "2") (pinfunction "2_2") (pintype "passive"))
      (node (ref "R76") (pin "2") (pinfunction "2_2") (pintype "passive"))
      (node (ref "R79") (pin "1") (pinfunction "1_1") (pintype "passive"))
      (node (ref "R8") (pin "1") (pinfunction "1_1") (pintype "passive"))
      (node (ref "R80") (pin "1") (pinfunction "1_1") (pintype "passive"))
      (node (ref "R88") (pin "1") (pinfunction "1_1") (pintype "passive"))
      (node (ref "R90") (pin "2") (pinfunction "2_2") (pintype "passive"))
      (node (ref "R98") (pin "1") (pinfunction "1_1") (pintype "passive"))
      (node (ref "X1") (pin "13") (pinfunction "13_13") (pintype "passive"))
      (node (ref "X1") (pin "18") (pinfunction "18_18") (pintype "passive"))
      (node (ref "X1") (pin "23") (pinfunction "23_23") (pintype "passive"))
      (node (ref "X10") (pin "13") (pinfunction "13_13") (pintype "passive"))
      (node (ref "X10") (pin "18") (pinfunction "18_18") (pintype "passive"))
      (node (ref "X10") (pin "23") (pinfunction "23_23") (pintype "passive"))
      (node (ref "X101") (pin "13") (pinfunction "13_13") (pintype "passive"))
      (node (ref "X101") (pin "18") (pinfunction "18_18") (pintype "passive"))
      (node (ref "X101") (pin "23") (pinfunction "23_23") (pintype "passive"))
      (node (ref "X102") (pin "1") (pinfunction "S_1") (pintype "passive"))
      (node (ref "X103") (pin "5") (pinfunction "S_5") (pintype "passive"))
      (node (ref "X11") (pin "5") (pinfunction "S_5") (pintype "passive"))
      (node (ref "X12") (pin "1") (pinfunction "S_1") (pintype "passive"))
      (node (ref "X13") (pin "13") (pinfunction "13_13") (pintype "passive"))
      (node (ref "X13") (pin "18") (pinfunction "18_18") (pintype "passive"))
      (node (ref "X13") (pin "23") (pinfunction "23_23") (pintype "passive"))
      (node (ref "X14") (pin "5") (pinfunction "S_5") (pintype "passive"))
      (node (ref "X15") (pin "1") (pinfunction "S_1") (pintype "passive"))
      (node (ref "X16") (pin "13") (pinfunction "13_13") (pintype "passive"))
      (node (ref "X16") (pin "18") (pinfunction "18_18") (pintype "passive"))
      (node (ref "X16") (pin "23") (pinfunction "23_23") (pintype "passive"))
      (node (ref "X17") (pin "5") (pinfunction "S_5") (pintype "passive"))
      (node (ref "X18") (pin "1") (pinfunction "S_1") (pintype "passive"))
      (node (ref "X2") (pin "5") (pinfunction "S_5") (pintype "passive"))
      (node (ref "X201") (pin "13") (pinfunction "13_13") (pintype "passive"))
      (node (ref "X201") (pin "18") (pinfunction "18_18") (pintype "passive"))
      (node (ref "X201") (pin "23") (pinfunction "23_23") (pintype "passive"))
      (node (ref "X202") (pin "1") (pinfunction "S_1") (pintype "passive"))
      (node (ref "X203") (pin "5") (pinfunction "S_5") (pintype "passive"))
      (node (ref "X3") (pin "1") (pinfunction "S_1") (pintype "passive"))
      (node (ref "X301") (pin "13") (pinfunction "13_13") (pintype "passive"))
      (node (ref "X301") (pin "18") (pinfunction "18_18") (pintype "passive"))
      (node (ref "X301") (pin "23") (pinfunction "23_23") (pintype "passive"))
      (node (ref "X302") (pin "1") (pinfunction "S_1") (pintype "passive"))
      (node (ref "X303") (pin "5") (pinfunction "S_5") (pintype "passive"))
      (node (ref "X4") (pin "13") (pinfunction "13_13") (pintype "passive"))
      (node (ref "X4") (pin "18") (pinfunction "18_18") (pintype "passive"))
      (node (ref "X4") (pin "23") (pinfunction "23_23") (pintype "passive"))
      (node (ref "X401") (pin "13") (pinfunction "13_13") (pintype "passive"))
      (node (ref "X401") (pin "18") (pinfunction "18_18") (pintype "passive"))
      (node (ref "X401") (pin "23") (pinfunction "23_23") (pintype "passive"))
      (node (ref "X402") (pin "1") (pinfunction "S_1") (pintype "passive"))
      (node (ref "X403") (pin "5") (pinfunction "S_5") (pintype "passive"))
      (node (ref "X5") (pin "5") (pinfunction "S_5") (pintype "passive"))
      (node (ref "X501") (pin "13") (pinfunction "13_13") (pintype "passive"))
      (node (ref "X501") (pin "18") (pinfunction "18_18") (pintype "passive"))
      (node (ref "X501") (pin "23") (pinfunction "23_23") (pintype "passive"))
      (node (ref "X502") (pin "1") (pinfunction "S_1") (pintype "passive"))
      (node (ref "X503") (pin "5") (pinfunction "S_5") (pintype "passive"))
      (node (ref "X6") (pin "1") (pinfunction "S_1") (pintype "passive"))
      (node (ref "X601") (pin "13") (pinfunction "13_13") (pintype "passive"))
      (node (ref "X601") (pin "18") (pinfunction "18_18") (pintype "passive"))
      (node (ref "X601") (pin "23") (pinfunction "23_23") (pintype "passive"))
      (node (ref "X602") (pin "1") (pinfunction "S_1") (pintype "passive"))
      (node (ref "X603") (pin "5") (pinfunction "S_5") (pintype "passive"))
      (node (ref "X7") (pin "13") (pinfunction "13_13") (pintype "passive"))
      (node (ref "X7") (pin "18") (pinfunction "18_18") (pintype "passive"))
      (node (ref "X7") (pin "23") (pinfunction "23_23") (pintype "passive"))
      (node (ref "X8") (pin "5") (pinfunction "S_5") (pintype "passive"))
      (node (ref "X9") (pin "1") (pinfunction "S_1") (pintype "passive"))
    )
    (net (code "4") (name "Net-(1A-KL)") (class "Default")
      (node (ref "1") (pin "1") (pinfunction "KL_1") (pintype "passive"))
      (node (ref "TP1") (pin "TP") (pinfunction "PP_TP") (pintype "input"))
      (node (ref "X101") (pin "1") (pinfunction "1_1") (pintype "passive"))
    )
    (net (code "5") (name "Net-(1B-KL)") (class "Default")
      (node (ref "1") (pin "10") (pinfunction "KL_10") (pintype "passive"))
      (node (ref "D102") (pin "2") (pinfunction "-_2") (pintype "passive"))
      (node (ref "D103") (pin "2") (pinfunction "-_2") (pintype "passive"))
      (node (ref "JP104") (pin "1") (pinfunction "1_1") (pintype "passive"))
      (node (ref "SJ101") (pin "1") (pinfunction "1_1") (pintype "passive"))
      (node (ref "TP10") (pin "TP") (pinfunction "PP_TP") (pintype "input"))
    )
    (net (code "6") (name "Net-(1C-KL)") (class "Default")
      (node (ref "1") (pin "11") (pinfunction "KL_11") (pintype "passive"))
      (node (ref "D103") (pin "1") (pinfunction "+_1") (pintype "passive"))
      (node (ref "TP11") (pin "TP") (pinfunction "PP_TP") (pintype "input"))
      (node (ref "X101") (pin "19") (pinfunction "19_19") (pintype "passive"))
    )
    (net (code "7") (name "Net-(1E-KL)") (class "Default")
      (node (ref "1") (pin "2") (pinfunction "KL_2") (pintype "passive"))
      (node (ref "Q101") (pin "2") (pinfunction "C_2") (pintype "passive"))
      (node (ref "TP2") (pin "TP") (pinfunction "PP_TP") (pintype "input"))
    )
    (net (code "8") (name "Net-(1F-KL)") (class "Default")
      (node (ref "1") (pin "3") (pinfunction "KL_3") (pintype "passive"))
      (node (ref "IC107") (pin "11") (pinfunction "O6_11") (pintype "open_collector"))
      (node (ref "TP3") (pin "TP") (pinfunction "PP_TP") (pintype "input"))
    )
    (net (code "9") (name "Net-(1G-KL)") (class "Default")
      (node (ref "1") (pin "4") (pinfunction "KL_4") (pintype "passive"))
      (node (ref "IC107") (pin "10") (pinfunction "O7_10") (pintype "open_collector"))
      (node (ref "TP4") (pin "TP") (pinfunction "PP_TP") (pintype "input"))
    )
    (net (code "10") (name "Net-(1H-KL)") (class "Default")
      (node (ref "1") (pin "5") (pinfunction "KL_5") (pintype "passive"))
      (node (ref "IC107") (pin "12") (pinfunction "O5_12") (pintype "open_collector"))
      (node (ref "TP5") (pin "TP") (pinfunction "PP_TP") (pintype "input"))
    )
    (net (code "11") (name "Net-(1I-KL)") (class "Default")
      (node (ref "1") (pin "6") (pinfunction "KL_6") (pintype "passive"))
      (node (ref "IC107") (pin "13") (pinfunction "O4_13") (pintype "open_collector"))
      (node (ref "TP6") (pin "TP") (pinfunction "PP_TP") (pintype "input"))
    )
    (net (code "12") (name "Net-(1J-KL)") (class "Default")
      (node (ref "1") (pin "7") (pinfunction "KL_7") (pintype "passive"))
      (node (ref "IC107") (pin "14") (pinfunction "O3_14") (pintype "open_collector"))
      (node (ref "TP7") (pin "TP") (pinfunction "PP_TP") (pintype "input"))
    )
    (net (code "13") (name "Net-(1K-KL)") (class "Default")
      (node (ref "1") (pin "8") (pinfunction "KL_8") (pintype "passive"))
      (node (ref "Q106") (pin "3") (pinfunction "D_3") (pintype "passive"))
      (node (ref "TP8") (pin "TP") (pinfunction "PP_TP") (pintype "input"))
    )
    (net (code "14") (name "Net-(1L-KL)") (class "Default")
      (node (ref "1") (pin "9") (pinfunction "KL_9") (pintype "passive"))
      (node (ref "D102") (pin "1") (pinfunction "+_1") (pintype "passive"))
      (node (ref "TP9") (pin "TP") (pinfunction "PP_TP") (pintype "input"))
      (node (ref "X101") (pin "17") (pinfunction "17_17") (pintype "passive"))
    )
    (net (code "15") (name "Net-(2B-KL)") (class "Default")
      (node (ref "2") (pin "10") (pinfunction "KL_10") (pintype "passive"))
      (node (ref "TP25") (pin "TP") (pinfunction "PP_TP") (pintype "input"))
      (node (ref "X101") (pin "15") (pinfunction "15_15") (pintype "passive"))
    )
    (net (code "16") (name "Net-(2C-KL)") (class "Default")
      (node (ref "2") (pin "11") (pinfunction "KL_11") (pintype "passive"))
      (node (ref "IC107") (pin "16") (pinfunction "O1_16") (pintype "open_collector"))
      (node (ref "R118") (pin "2") (pinfunction "2_2") (pintype "passive"))
      (node (ref "R119") (pin "1") (pinfunction "1_1") (pintype "passive"))
      (node (ref "TP26") (pin "TP") (pinfunction "PP_TP") (pintype "input"))
    )
    (net (code "17") (name "Net-(2D-KL)") (class "Default")
      (node (ref "2") (pin "12") (pinfunction "KL_12") (pintype "passive"))
      (node (ref "R146") (pin "1") (pinfunction "1_1") (pintype "passive"))
      (node (ref "TP13") (pin "TP") (pinfunction "PP_TP") (pintype "input"))
    )
    (net (code "18") (name "Net-(2E-KL)") (class "Default")
      (node (ref "2") (pin "2") (pinfunction "KL_2") (pintype "passive"))
      (node (ref "D109") (pin "2") (pinfunction "-_2") (pintype "passive"))
      (node (ref "LED102") (pin "K") (pinfunction "C_K") (pintype "passive"))
      (node (ref "TP16") (pin "TP") (pinfunction "PP_TP") (pintype "input"))
      (node (ref "X101") (pin "12") (pinfunction "12_12") (pintype "passive"))
    )
    (net (code "19") (name "Net-(2F-KL)") (class "Default")
      (node (ref "2") (pin "3") (pinfunction "KL_3") (pintype "passive"))
      (node (ref "D108") (pin "2") (pinfunction "-_2") (pintype "passive"))
      (node (ref "LED103") (pin "K") (pinfunction "C_K") (pintype "passive"))
      (node (ref "TP17") (pin "TP") (pinfunction "PP_TP") (pintype "input"))
      (node (ref "X101") (pin "11") (pinfunction "11_11") (pintype "passive"))
    )
    (net (code "20") (name "Net-(2G-KL)") (class "Default")
      (node (ref "2") (pin "4") (pinfunction "KL_4") (pintype "passive"))
      (node (ref "D107") (pin "2") (pinfunction "-_2") (pintype "passive"))
      (node (ref "LED104") (pin "K") (pinfunction "C_K") (pintype "passive"))
      (node (ref "TP18") (pin "TP") (pinfunction "PP_TP") (pintype "input"))
      (node (ref "X101") (pin "10") (pinfunction "10_10") (pintype "passive"))
    )
    (net (code "21") (name "Net-(2H-KL)") (class "Default")
      (node (ref "2") (pin "5") (pinfunction "KL_5") (pintype "passive"))
      (node (ref "D106") (pin "2") (pinfunction "-_2") (pintype "passive"))
      (node (ref "LED105") (pin "K") (pinfunction "C_K") (pintype "passive"))
      (node (ref "TP19") (pin "TP") (pinfunction "PP_TP") (pintype "input"))
      (node (ref "X101") (pin "9") (pinfunction "9_9") (pintype "passive"))
    )
    (net (code "22") (name "Net-(2I-KL)") (class "Default")
      (node (ref "2") (pin "6") (pinfunction "KL_6") (pintype "passive"))
      (node (ref "JP105") (pin "2") (pinfunction "2_2") (pintype "passive"))
      (node (ref "TP21") (pin "TP") (pinfunction "PP_TP") (pintype "input"))
    )
    (net (code "23") (name "Net-(2J-KL)") (class "Default")
      (node (ref "2") (pin "7") (pinfunction "KL_7") (pintype "passive"))
      (node (ref "LED101") (pin "A") (pinfunction "A_A") (pintype "passive"))
      (node (ref "TP22") (pin "TP") (pinfunction "PP_TP") (pintype "input"))
      (node (ref "X101") (pin "8") (pinfunction "8_8") (pintype "passive"))
    )
    (net (code "24") (name "Net-(2K-KL)") (class "Default")
      (node (ref "2") (pin "8") (pinfunction "KL_8") (pintype "passive"))
      (node (ref "D110") (pin "2") (pinfunction "-_2") (pintype "passive"))
      (node (ref "LED106") (pin "K") (pinfunction "C_K") (pintype "passive"))
      (node (ref "TP23") (pin "TP") (pinfunction "PP_TP") (pintype "input"))
      (node (ref "X101") (pin "14") (pinfunction "14_14") (pintype "passive"))
    )
    (net (code "25") (name "Net-(2L-KL)") (class "Default")
      (node (ref "2") (pin "9") (pinfunction "KL_9") (pintype "passive"))
      (node (ref "D107") (pin "1") (pinfunction "+_1") (pintype "passive"))
      (node (ref "D108") (pin "1") (pinfunction "+_1") (pintype "passive"))
      (node (ref "JP102") (pin "1") (pinfunction "1_1") (pintype "passive"))
      (node (ref "JP103") (pin "2") (pinfunction "2_2") (pintype "passive"))
      (node (ref "TP24") (pin "TP") (pinfunction "PP_TP") (pintype "input"))
    )
    (net (code "26") (name "Net-(3A-KL)") (class "Default")
      (node (ref "3") (pin "1") (pinfunction "KL_1") (pintype "passive"))
      (node (ref "TP14") (pin "TP") (pinfunction "PP_TP") (pintype "input"))
      (node (ref "X201") (pin "1") (pinfunction "1_1") (pintype "passive"))
    )
    (net (code "27") (name "Net-(3B-KL)") (class "Default")
      (node (ref "3") (pin "10") (pinfunction "KL_10") (pintype "passive"))
      (node (ref "D202") (pin "2") (pinfunction "-_2") (pintype "passive"))
      (node (ref "D203") (pin "2") (pinfunction "-_2") (pintype "passive"))
      (node (ref "JP204") (pin "1") (pinfunction "1_1") (pintype "passive"))
      (node (ref "SJ201") (pin "1") (pinfunction "1_1") (pintype "passive"))
      (node (ref "TP33") (pin "TP") (pinfunction "PP_TP") (pintype "input"))
    )
    (net (code "28") (name "Net-(3C-KL)") (class "Default")
      (node (ref "3") (pin "11") (pinfunction "KL_11") (pintype "passive"))
      (node (ref "D203") (pin "1") (pinfunction "+_1") (pintype "passive"))
      (node (ref "TP34") (pin "TP") (pinfunction "PP_TP") (pintype "input"))
      (node (ref "X201") (pin "19") (pinfunction "19_19") (pintype "passive"))
    )
    (net (code "29") (name "Net-(3E-KL)") (class "Default")
      (node (ref "3") (pin "2") (pinfunction "KL_2") (pintype "passive"))
      (node (ref "Q201") (pin "2") (pinfunction "C_2") (pintype "passive"))
      (node (ref "TP15") (pin "TP") (pinfunction "PP_TP") (pintype "input"))
    )
    (net (code "30") (name "Net-(3F-KL)") (class "Default")
      (node (ref "3") (pin "3") (pinfunction "KL_3") (pintype "passive"))
      (node (ref "IC207") (pin "11") (pinfunction "O6_11") (pintype "open_collector"))
      (node (ref "TP20") (pin "TP") (pinfunction "PP_TP") (pintype "input"))
    )
    (net (code "31") (name "Net-(3G-KL)") (class "Default")
      (node (ref "3") (pin "4") (pinfunction "KL_4") (pintype "passive"))
      (node (ref "IC207") (pin "10") (pinfunction "O7_10") (pintype "open_collector"))
      (node (ref "TP27") (pin "TP") (pinfunction "PP_TP") (pintype "input"))
    )
    (net (code "32") (name "Net-(3H-KL)") (class "Default")
      (node (ref "3") (pin "5") (pinfunction "KL_5") (pintype "passive"))
      (node (ref "IC207") (pin "12") (pinfunction "O5_12") (pintype "open_collector"))
      (node (ref "TP28") (pin "TP") (pinfunction "PP_TP") (pintype "input"))
    )
    (net (code "33") (name "Net-(3I-KL)") (class "Default")
      (node (ref "3") (pin "6") (pinfunction "KL_6") (pintype "passive"))
      (node (ref "IC207") (pin "13") (pinfunction "O4_13") (pintype "open_collector"))
      (node (ref "TP29") (pin "TP") (pinfunction "PP_TP") (pintype "input"))
    )
    (net (code "34") (name "Net-(3J-KL)") (class "Default")
      (node (ref "3") (pin "7") (pinfunction "KL_7") (pintype "passive"))
      (node (ref "IC207") (pin "14") (pinfunction "O3_14") (pintype "open_collector"))
      (node (ref "TP30") (pin "TP") (pinfunction "PP_TP") (pintype "input"))
    )
    (net (code "35") (name "Net-(3K-KL)") (class "Default")
      (node (ref "3") (pin "8") (pinfunction "KL_8") (pintype "passive"))
      (node (ref "Q206") (pin "3") (pinfunction "D_3") (pintype "passive"))
      (node (ref "TP31") (pin "TP") (pinfunction "PP_TP") (pintype "input"))
    )
    (net (code "36") (name "Net-(3L-KL)") (class "Default")
      (node (ref "3") (pin "9") (pinfunction "KL_9") (pintype "passive"))
      (node (ref "D202") (pin "1") (pinfunction "+_1") (pintype "passive"))
      (node (ref "TP32") (pin "TP") (pinfunction "PP_TP") (pintype "input"))
      (node (ref "X201") (pin "17") (pinfunction "17_17") (pintype "passive"))
    )
    (net (code "37") (name "Net-(4B-KL)") (class "Default")
      (node (ref "4") (pin "10") (pinfunction "KL_10") (pintype "passive"))
      (node (ref "TP43") (pin "TP") (pinfunction "PP_TP") (pintype "input"))
      (node (ref "X201") (pin "15") (pinfunction "15_15") (pintype "passive"))
    )
    (net (code "38") (name "Net-(4C-KL)") (class "Default")
      (node (ref "4") (pin "11") (pinfunction "KL_11") (pintype "passive"))
      (node (ref "IC207") (pin "16") (pinfunction "O1_16") (pintype "open_collector"))
      (node (ref "R218") (pin "2") (pinfunction "2_2") (pintype "passive"))
      (node (ref "R219") (pin "1") (pinfunction "1_1") (pintype "passive"))
      (node (ref "TP44") (pin "TP") (pinfunction "PP_TP") (pintype "input"))
    )
    (net (code "39") (name "Net-(4D-KL)") (class "Default")
      (node (ref "4") (pin "12") (pinfunction "KL_12") (pintype "passive"))
      (node (ref "R246") (pin "1") (pinfunction "1_1") (pintype "passive"))
      (node (ref "TP46") (pin "TP") (pinfunction "PP_TP") (pintype "input"))
    )
    (net (code "40") (name "Net-(4E-KL)") (class "Default")
      (node (ref "4") (pin "2") (pinfunction "KL_2") (pintype "passive"))
      (node (ref "D209") (pin "2") (pinfunction "-_2") (pintype "passive"))
      (node (ref "LED202") (pin "K") (pinfunction "C_K") (pintype "passive"))
      (node (ref "TP35") (pin "TP") (pinfunction "PP_TP") (pintype "input"))
      (node (ref "X201") (pin "12") (pinfunction "12_12") (pintype "passive"))
    )
    (net (code "41") (name "Net-(4F-KL)") (class "Default")
      (node (ref "4") (pin "3") (pinfunction "KL_3") (pintype "passive"))
      (node (ref "D208") (pin "2") (pinfunction "-_2") (pintype "passive"))
      (node (ref "LED203") (pin "K") (pinfunction "C_K") (pintype "passive"))
      (node (ref "TP36") (pin "TP") (pinfunction "PP_TP") (pintype "input"))
      (node (ref "X201") (pin "11") (pinfunction "11_11") (pintype "passive"))
    )
    (net (code "42") (name "Net-(4G-KL)") (class "Default")
      (node (ref "4") (pin "4") (pinfunction "KL_4") (pintype "passive"))
      (node (ref "D207") (pin "2") (pinfunction "-_2") (pintype "passive"))
      (node (ref "LED204") (pin "K") (pinfunction "C_K") (pintype "passive"))
      (node (ref "TP37") (pin "TP") (pinfunction "PP_TP") (pintype "input"))
      (node (ref "X201") (pin "10") (pinfunction "10_10") (pintype "passive"))
    )
    (net (code "43") (name "Net-(4H-KL)") (class "Default")
      (node (ref "4") (pin "5") (pinfunction "KL_5") (pintype "passive"))
      (node (ref "D206") (pin "2") (pinfunction "-_2") (pintype "passive"))
      (node (ref "LED205") (pin "K") (pinfunction "C_K") (pintype "passive"))
      (node (ref "TP38") (pin "TP") (pinfunction "PP_TP") (pintype "input"))
      (node (ref "X201") (pin "9") (pinfunction "9_9") (pintype "passive"))
    )
    (net (code "44") (name "Net-(4I-KL)") (class "Default")
      (node (ref "4") (pin "6") (pinfunction "KL_6") (pintype "passive"))
      (node (ref "JP205") (pin "2") (pinfunction "2_2") (pintype "passive"))
      (node (ref "TP39") (pin "TP") (pinfunction "PP_TP") (pintype "input"))
    )
    (net (code "45") (name "Net-(4J-KL)") (class "Default")
      (node (ref "4") (pin "7") (pinfunction "KL_7") (pintype "passive"))
      (node (ref "LED201") (pin "A") (pinfunction "A_A") (pintype "passive"))
      (node (ref "TP40") (pin "TP") (pinfunction "PP_TP") (pintype "input"))
      (node (ref "X201") (pin "8") (pinfunction "8_8") (pintype "passive"))
    )
    (net (code "46") (name "Net-(4K-KL)") (class "Default")
      (node (ref "4") (pin "8") (pinfunction "KL_8") (pintype "passive"))
      (node (ref "D210") (pin "2") (pinfunction "-_2") (pintype "passive"))
      (node (ref "LED206") (pin "K") (pinfunction "C_K") (pintype "passive"))
      (node (ref "TP41") (pin "TP") (pinfunction "PP_TP") (pintype "input"))
      (node (ref "X201") (pin "14") (pinfunction "14_14") (pintype "passive"))
    )
    (net (code "47") (name "Net-(4L-KL)") (class "Default")
      (node (ref "4") (pin "9") (pinfunction "KL_9") (pintype "passive"))
      (node (ref "D207") (pin "1") (pinfunction "+_1") (pintype "passive"))
      (node (ref "D208") (pin "1") (pinfunction "+_1") (pintype "passive"))
      (node (ref "JP202") (pin "1") (pinfunction "1_1") (pintype "passive"))
      (node (ref "JP203") (pin "2") (pinfunction "2_2") (pintype "passive"))
      (node (ref "TP42") (pin "TP") (pinfunction "PP_TP") (pintype "input"))
    )
    (net (code "48") (name "Net-(5A-KL)") (class "Default")
      (node (ref "5") (pin "1") (pinfunction "KL_1") (pintype "passive"))
      (node (ref "TP47") (pin "TP") (pinfunction "PP_TP") (pintype "input"))
      (node (ref "X301") (pin "1") (pinfunction "1_1") (pintype "passive"))
    )
    (net (code "49") (name "Net-(5B-KL)") (class "Default")
      (node (ref "5") (pin "10") (pinfunction "KL_10") (pintype "passive"))
      (node (ref "D302") (pin "2") (pinfunction "-_2") (pintype "passive"))
      (node (ref "D303") (pin "2") (pinfunction "-_2") (pintype "passive"))
      (node (ref "JP304") (pin "1") (pinfunction "1_1") (pintype "passive"))
      (node (ref "SJ301") (pin "1") (pinfunction "1_1") (pintype "passive"))
      (node (ref "TP56") (pin "TP") (pinfunction "PP_TP") (pintype "input"))
    )
    (net (code "50") (name "Net-(5C-KL)") (class "Default")
      (node (ref "5") (pin "11") (pinfunction "KL_11") (pintype "passive"))
      (node (ref "D303") (pin "1") (pinfunction "+_1") (pintype "passive"))
      (node (ref "TP57") (pin "TP") (pinfunction "PP_TP") (pintype "input"))
      (node (ref "X301") (pin "19") (pinfunction "19_19") (pintype "passive"))
    )
    (net (code "51") (name "Net-(5E-KL)") (class "Default")
      (node (ref "5") (pin "2") (pinfunction "KL_2") (pintype "passive"))
      (node (ref "Q301") (pin "2") (pinfunction "C_2") (pintype "passive"))
      (node (ref "TP48") (pin "TP") (pinfunction "PP_TP") (pintype "input"))
    )
    (net (code "52") (name "Net-(5F-KL)") (class "Default")
      (node (ref "5") (pin "3") (pinfunction "KL_3") (pintype "passive"))
      (node (ref "IC307") (pin "11") (pinfunction "O6_11") (pintype "open_collector"))
      (node (ref "TP49") (pin "TP") (pinfunction "PP_TP") (pintype "input"))
    )
    (net (code "53") (name "Net-(5G-KL)") (class "Default")
      (node (ref "5") (pin "4") (pinfunction "KL_4") (pintype "passive"))
      (node (ref "IC307") (pin "10") (pinfunction "O7_10") (pintype "open_collector"))
      (node (ref "TP50") (pin "TP") (pinfunction "PP_TP") (pintype "input"))
    )
    (net (code "54") (name "Net-(5H-KL)") (class "Default")
      (node (ref "5") (pin "5") (pinfunction "KL_5") (pintype "passive"))
      (node (ref "IC307") (pin "12") (pinfunction "O5_12") (pintype "open_collector"))
      (node (ref "TP51") (pin "TP") (pinfunction "PP_TP") (pintype "input"))
    )
    (net (code "55") (name "Net-(5I-KL)") (class "Default")
      (node (ref "5") (pin "6") (pinfunction "KL_6") (pintype "passive"))
      (node (ref "IC307") (pin "13") (pinfunction "O4_13") (pintype "open_collector"))
      (node (ref "TP52") (pin "TP") (pinfunction "PP_TP") (pintype "input"))
    )
    (net (code "56") (name "Net-(5J-KL)") (class "Default")
      (node (ref "5") (pin "7") (pinfunction "KL_7") (pintype "passive"))
      (node (ref "IC307") (pin "14") (pinfunction "O3_14") (pintype "open_collector"))
      (node (ref "TP53") (pin "TP") (pinfunction "PP_TP") (pintype "input"))
    )
    (net (code "57") (name "Net-(5K-KL)") (class "Default")
      (node (ref "5") (pin "8") (pinfunction "KL_8") (pintype "passive"))
      (node (ref "Q306") (pin "3") (pinfunction "D_3") (pintype "passive"))
      (node (ref "TP54") (pin "TP") (pinfunction "PP_TP") (pintype "input"))
    )
    (net (code "58") (name "Net-(5L-KL)") (class "Default")
      (node (ref "5") (pin "9") (pinfunction "KL_9") (pintype "passive"))
      (node (ref "D302") (pin "1") (pinfunction "+_1") (pintype "passive"))
      (node (ref "TP55") (pin "TP") (pinfunction "PP_TP") (pintype "input"))
      (node (ref "X301") (pin "17") (pinfunction "17_17") (pintype "passive"))
    )
    (net (code "59") (name "Net-(6B-KL)") (class "Default")
      (node (ref "6") (pin "10") (pinfunction "KL_10") (pintype "passive"))
      (node (ref "TP66") (pin "TP") (pinfunction "PP_TP") (pintype "input"))
      (node (ref "X301") (pin "15") (pinfunction "15_15") (pintype "passive"))
    )
    (net (code "60") (name "Net-(6C-KL)") (class "Default")
      (node (ref "6") (pin "11") (pinfunction "KL_11") (pintype "passive"))
      (node (ref "IC307") (pin "16") (pinfunction "O1_16") (pintype "open_collector"))
      (node (ref "R318") (pin "2") (pinfunction "2_2") (pintype "passive"))
      (node (ref "R319") (pin "1") (pinfunction "1_1") (pintype "passive"))
      (node (ref "TP67") (pin "TP") (pinfunction "PP_TP") (pintype "input"))
    )
    (net (code "61") (name "Net-(6D-KL)") (class "Default")
      (node (ref "6") (pin "12") (pinfunction "KL_12") (pintype "passive"))
      (node (ref "R346") (pin "1") (pinfunction "1_1") (pintype "passive"))
      (node (ref "TP69") (pin "TP") (pinfunction "PP_TP") (pintype "input"))
    )
    (net (code "62") (name "Net-(6E-KL)") (class "Default")
      (node (ref "6") (pin "2") (pinfunction "KL_2") (pintype "passive"))
      (node (ref "D309") (pin "2") (pinfunction "-_2") (pintype "passive"))
      (node (ref "LED302") (pin "K") (pinfunction "C_K") (pintype "passive"))
      (node (ref "TP58") (pin "TP") (pinfunction "PP_TP") (pintype "input"))
      (node (ref "X301") (pin "12") (pinfunction "12_12") (pintype "passive"))
    )
    (net (code "63") (name "Net-(6F-KL)") (class "Default")
      (node (ref "6") (pin "3") (pinfunction "KL_3") (pintype "passive"))
      (node (ref "D308") (pin "2") (pinfunction "-_2") (pintype "passive"))
      (node (ref "LED303") (pin "K") (pinfunction "C_K") (pintype "passive"))
      (node (ref "TP59") (pin "TP") (pinfunction "PP_TP") (pintype "input"))
      (node (ref "X301") (pin "11") (pinfunction "11_11") (pintype "passive"))
    )
    (net (code "64") (name "Net-(6G-KL)") (class "Default")
      (node (ref "6") (pin "4") (pinfunction "KL_4") (pintype "passive"))
      (node (ref "D307") (pin "2") (pinfunction "-_2") (pintype "passive"))
      (node (ref "LED304") (pin "K") (pinfunction "C_K") (pintype "passive"))
      (node (ref "TP60") (pin "TP") (pinfunction "PP_TP") (pintype "input"))
      (node (ref "X301") (pin "10") (pinfunction "10_10") (pintype "passive"))
    )
    (net (code "65") (name "Net-(6H-KL)") (class "Default")
      (node (ref "6") (pin "5") (pinfunction "KL_5") (pintype "passive"))
      (node (ref "D306") (pin "2") (pinfunction "-_2") (pintype "passive"))
      (node (ref "LED305") (pin "K") (pinfunction "C_K") (pintype "passive"))
      (node (ref "TP61") (pin "TP") (pinfunction "PP_TP") (pintype "input"))
      (node (ref "X301") (pin "9") (pinfunction "9_9") (pintype "passive"))
    )
    (net (code "66") (name "Net-(6I-KL)") (class "Default")
      (node (ref "6") (pin "6") (pinfunction "KL_6") (pintype "passive"))
      (node (ref "JP305") (pin "2") (pinfunction "2_2") (pintype "passive"))
      (node (ref "TP62") (pin "TP") (pinfunction "PP_TP") (pintype "input"))
    )
    (net (code "67") (name "Net-(6J-KL)") (class "Default")
      (node (ref "6") (pin "7") (pinfunction "KL_7") (pintype "passive"))
      (node (ref "LED301") (pin "A") (pinfunction "A_A") (pintype "passive"))
      (node (ref "TP63") (pin "TP") (pinfunction "PP_TP") (pintype "input"))
      (node (ref "X301") (pin "8") (pinfunction "8_8") (pintype "passive"))
    )
    (net (code "68") (name "Net-(6K-KL)") (class "Default")
      (node (ref "6") (pin "8") (pinfunction "KL_8") (pintype "passive"))
      (node (ref "D310") (pin "2") (pinfunction "-_2") (pintype "passive"))
      (node (ref "LED306") (pin "K") (pinfunction "C_K") (pintype "passive"))
      (node (ref "TP64") (pin "TP") (pinfunction "PP_TP") (pintype "input"))
      (node (ref "X301") (pin "14") (pinfunction "14_14") (pintype "passive"))
    )
    (net (code "69") (name "Net-(6L-KL)") (class "Default")
      (node (ref "6") (pin "9") (pinfunction "KL_9") (pintype "passive"))
      (node (ref "D307") (pin "1") (pinfunction "+_1") (pintype "passive"))
      (node (ref "D308") (pin "1") (pinfunction "+_1") (pintype "passive"))
      (node (ref "JP302") (pin "1") (pinfunction "1_1") (pintype "passive"))
      (node (ref "JP303") (pin "2") (pinfunction "2_2") (pintype "passive"))
      (node (ref "TP65") (pin "TP") (pinfunction "PP_TP") (pintype "input"))
    )
    (net (code "70") (name "Net-(7A-KL)") (class "Default")
      (node (ref "7") (pin "1") (pinfunction "KL_1") (pintype "passive"))
      (node (ref "TP70") (pin "TP") (pinfunction "PP_TP") (pintype "input"))
      (node (ref "X1") (pin "1") (pinfunction "1_1") (pintype "passive"))
    )
    (net (code "71") (name "Net-(7B-KL)") (class "Default")
      (node (ref "7") (pin "10") (pinfunction "KL_10") (pintype "passive"))
      (node (ref "D2") (pin "2") (pinfunction "-_2") (pintype "passive"))
      (node (ref "D3") (pin "2") (pinfunction "-_2") (pintype "passive"))
      (node (ref "JP5") (pin "1") (pinfunction "1_1") (pintype "passive"))
      (node (ref "SJ1") (pin "1") (pinfunction "1_1") (pintype "passive"))
      (node (ref "TP79") (pin "TP") (pinfunction "PP_TP") (pintype "input"))
    )
    (net (code "72") (name "Net-(7C-KL)") (class "Default")
      (node (ref "7") (pin "11") (pinfunction "KL_11") (pintype "passive"))
      (node (ref "D3") (pin "1") (pinfunction "+_1") (pintype "passive"))
      (node (ref "TP80") (pin "TP") (pinfunction "PP_TP") (pintype "input"))
      (node (ref "X1") (pin "19") (pinfunction "19_19") (pintype "passive"))
    )
    (net (code "73") (name "Net-(7E-KL)") (class "Default")
      (node (ref "7") (pin "2") (pinfunction "KL_2") (pintype "passive"))
      (node (ref "Q3") (pin "2") (pinfunction "C_2") (pintype "passive"))
      (node (ref "TP71") (pin "TP") (pinfunction "PP_TP") (pintype "input"))
    )
    (net (code "74") (name "Net-(7F-KL)") (class "Default")
      (node (ref "7") (pin "3") (pinfunction "KL_3") (pintype "passive"))
      (node (ref "IC4") (pin "11") (pinfunction "O6_11") (pintype "open_collector"))
      (node (ref "TP72") (pin "TP") (pinfunction "PP_TP") (pintype "input"))
    )
    (net (code "75") (name "Net-(7G-KL)") (class "Default")
      (node (ref "7") (pin "4") (pinfunction "KL_4") (pintype "passive"))
      (node (ref "IC4") (pin "10") (pinfunction "O7_10") (pintype "open_collector"))
      (node (ref "TP73") (pin "TP") (pinfunction "PP_TP") (pintype "input"))
    )
    (net (code "76") (name "Net-(7H-KL)") (class "Default")
      (node (ref "7") (pin "5") (pinfunction "KL_5") (pintype "passive"))
      (node (ref "IC4") (pin "12") (pinfunction "O5_12") (pintype "open_collector"))
      (node (ref "TP74") (pin "TP") (pinfunction "PP_TP") (pintype "input"))
    )
    (net (code "77") (name "Net-(7I-KL)") (class "Default")
      (node (ref "7") (pin "6") (pinfunction "KL_6") (pintype "passive"))
      (node (ref "IC4") (pin "13") (pinfunction "O4_13") (pintype "open_collector"))
      (node (ref "TP75") (pin "TP") (pinfunction "PP_TP") (pintype "input"))
    )
    (net (code "78") (name "Net-(7J-KL)") (class "Default")
      (node (ref "7") (pin "7") (pinfunction "KL_7") (pintype "passive"))
      (node (ref "IC4") (pin "14") (pinfunction "O3_14") (pintype "open_collector"))
      (node (ref "TP76") (pin "TP") (pinfunction "PP_TP") (pintype "input"))
    )
    (net (code "79") (name "Net-(7K-KL)") (class "Default")
      (node (ref "7") (pin "8") (pinfunction "KL_8") (pintype "passive"))
      (node (ref "Q7") (pin "3") (pinfunction "D_3") (pintype "passive"))
      (node (ref "TP77") (pin "TP") (pinfunction "PP_TP") (pintype "input"))
    )
    (net (code "80") (name "Net-(7L-KL)") (class "Default")
      (node (ref "7") (pin "9") (pinfunction "KL_9") (pintype "passive"))
      (node (ref "D2") (pin "1") (pinfunction "+_1") (pintype "passive"))
      (node (ref "TP78") (pin "TP") (pinfunction "PP_TP") (pintype "input"))
      (node (ref "X1") (pin "17") (pinfunction "17_17") (pintype "passive"))
    )
    (net (code "81") (name "Net-(8B-KL)") (class "Default")
      (node (ref "8") (pin "10") (pinfunction "KL_10") (pintype "passive"))
      (node (ref "TP89") (pin "TP") (pinfunction "PP_TP") (pintype "input"))
      (node (ref "X1") (pin "15") (pinfunction "15_15") (pintype "passive"))
    )
    (net (code "82") (name "Net-(8C-KL)") (class "Default")
      (node (ref "8") (pin "11") (pinfunction "KL_11") (pintype "passive"))
      (node (ref "IC4") (pin "16") (pinfunction "O1_16") (pintype "open_collector"))
      (node (ref "R37") (pin "1") (pinfunction "1_1") (pintype "passive"))
      (node (ref "R44") (pin "2") (pinfunction "2_2") (pintype "passive"))
      (node (ref "TP90") (pin "TP") (pinfunction "PP_TP") (pintype "input"))
    )
    (net (code "83") (name "Net-(8D-KL)") (class "Default")
      (node (ref "8") (pin "12") (pinfunction "KL_12") (pintype "passive"))
      (node (ref "R38") (pin "1") (pinfunction "1_1") (pintype "passive"))
      (node (ref "TP92") (pin "TP") (pinfunction "PP_TP") (pintype "input"))
    )
    (net (code "84") (name "Net-(8E-KL)") (class "Default")
      (node (ref "8") (pin "2") (pinfunction "KL_2") (pintype "passive"))
      (node (ref "D7") (pin "2") (pinfunction "-_2") (pintype "passive"))
      (node (ref "LED1") (pin "K") (pinfunction "C_K") (pintype "passive"))
      (node (ref "TP81") (pin "TP") (pinfunction "PP_TP") (pintype "input"))
      (node (ref "X1") (pin "12") (pinfunction "12_12") (pintype "passive"))
    )
    (net (code "85") (name "Net-(8F-KL)") (class "Default")
      (node (ref "8") (pin "3") (pinfunction "KL_3") (pintype "passive"))
      (node (ref "D6") (pin "2") (pinfunction "-_2") (pintype "passive"))
      (node (ref "LED2") (pin "K") (pinfunction "C_K") (pintype "passive"))
      (node (ref "TP82") (pin "TP") (pinfunction "PP_TP") (pintype "input"))
      (node (ref "X1") (pin "11") (pinfunction "11_11") (pintype "passive"))
    )
    (net (code "86") (name "Net-(8G-KL)") (class "Default")
      (node (ref "8") (pin "4") (pinfunction "KL_4") (pintype "passive"))
      (node (ref "D5") (pin "2") (pinfunction "-_2") (pintype "passive"))
      (node (ref "LED3") (pin "K") (pinfunction "C_K") (pintype "passive"))
      (node (ref "TP83") (pin "TP") (pinfunction "PP_TP") (pintype "input"))
      (node (ref "X1") (pin "10") (pinfunction "10_10") (pintype "passive"))
    )
    (net (code "87") (name "Net-(8H-KL)") (class "Default")
      (node (ref "8") (pin "5") (pinfunction "KL_5") (pintype "passive"))
      (node (ref "D4") (pin "2") (pinfunction "-_2") (pintype "passive"))
      (node (ref "LED4") (pin "K") (pinfunction "C_K") (pintype "passive"))
      (node (ref "TP84") (pin "TP") (pinfunction "PP_TP") (pintype "input"))
      (node (ref "X1") (pin "9") (pinfunction "9_9") (pintype "passive"))
    )
    (net (code "88") (name "Net-(8I-KL)") (class "Default")
      (node (ref "8") (pin "6") (pinfunction "KL_6") (pintype "passive"))
      (node (ref "JP2") (pin "2") (pinfunction "2_2") (pintype "passive"))
      (node (ref "TP85") (pin "TP") (pinfunction "PP_TP") (pintype "input"))
    )
    (net (code "89") (name "Net-(8J-KL)") (class "Default")
      (node (ref "8") (pin "7") (pinfunction "KL_7") (pintype "passive"))
      (node (ref "LED5") (pin "A") (pinfunction "A_A") (pintype "passive"))
      (node (ref "TP86") (pin "TP") (pinfunction "PP_TP") (pintype "input"))
      (node (ref "X1") (pin "8") (pinfunction "8_8") (pintype "passive"))
    )
    (net (code "90") (name "Net-(8K-KL)") (class "Default")
      (node (ref "8") (pin "8") (pinfunction "KL_8") (pintype "passive"))
      (node (ref "D8") (pin "2") (pinfunction "-_2") (pintype "passive"))
      (node (ref "LED6") (pin "K") (pinfunction "C_K") (pintype "passive"))
      (node (ref "TP87") (pin "TP") (pinfunction "PP_TP") (pintype "input"))
      (node (ref "X1") (pin "14") (pinfunction "14_14") (pintype "passive"))
    )
    (net (code "91") (name "Net-(8L-KL)") (class "Default")
      (node (ref "8") (pin "9") (pinfunction "KL_9") (pintype "passive"))
      (node (ref "D5") (pin "1") (pinfunction "+_1") (pintype "passive"))
      (node (ref "D6") (pin "1") (pinfunction "+_1") (pintype "passive"))
      (node (ref "JP3") (pin "1") (pinfunction "1_1") (pintype "passive"))
      (node (ref "JP4") (pin "2") (pinfunction "2_2") (pintype "passive"))
      (node (ref "TP88") (pin "TP") (pinfunction "PP_TP") (pintype "input"))
    )
    (net (code "92") (name "Net-(9A-KL)") (class "Default")
      (node (ref "9") (pin "1") (pinfunction "KL_1") (pintype "passive"))
      (node (ref "TP93") (pin "TP") (pinfunction "PP_TP") (pintype "input"))
      (node (ref "X4") (pin "1") (pinfunction "1_1") (pintype "passive"))
    )
    (net (code "93") (name "Net-(9B-KL)") (class "Default")
      (node (ref "9") (pin "10") (pinfunction "KL_10") (pintype "passive"))
      (node (ref "D13") (pin "2") (pinfunction "-_2") (pintype "passive"))
      (node (ref "D14") (pin "2") (pinfunction "-_2") (pintype "passive"))
      (node (ref "JP10") (pin "1") (pinfunction "1_1") (pintype "passive"))
      (node (ref "SJ2") (pin "1") (pinfunction "1_1") (pintype "passive"))
      (node (ref "TP102") (pin "TP") (pinfunction "PP_TP") (pintype "input"))
    )
    (net (code "94") (name "Net-(9C-KL)") (class "Default")
      (node (ref "9") (pin "11") (pinfunction "KL_11") (pintype "passive"))
      (node (ref "D14") (pin "1") (pinfunction "+_1") (pintype "passive"))
      (node (ref "TP103") (pin "TP") (pinfunction "PP_TP") (pintype "input"))
      (node (ref "X4") (pin "19") (pinfunction "19_19") (pintype "passive"))
    )
    (net (code "95") (name "Net-(9E-KL)") (class "Default")
      (node (ref "9") (pin "2") (pinfunction "KL_2") (pintype "passive"))
      (node (ref "Q10") (pin "2") (pinfunction "C_2") (pintype "passive"))
      (node (ref "TP94") (pin "TP") (pinfunction "PP_TP") (pintype "input"))
    )
    (net (code "96") (name "Net-(9F-KL)") (class "Default")
      (node (ref "9") (pin "3") (pinfunction "KL_3") (pintype "passive"))
      (node (ref "IC14") (pin "11") (pinfunction "O6_11") (pintype "open_collector"))
      (node (ref "TP95") (pin "TP") (pinfunction "PP_TP") (pintype "input"))
    )
    (net (code "97") (name "Net-(9G-KL)") (class "Default")
      (node (ref "9") (pin "4") (pinfunction "KL_4") (pintype "passive"))
      (node (ref "IC14") (pin "10") (pinfunction "O7_10") (pintype "open_collector"))
      (node (ref "TP96") (pin "TP") (pinfunction "PP_TP") (pintype "input"))
    )
    (net (code "98") (name "Net-(9H-KL)") (class "Default")
      (node (ref "9") (pin "5") (pinfunction "KL_5") (pintype "passive"))
      (node (ref "IC14") (pin "12") (pinfunction "O5_12") (pintype "open_collector"))
      (node (ref "TP97") (pin "TP") (pinfunction "PP_TP") (pintype "input"))
    )
    (net (code "99") (name "Net-(9I-KL)") (class "Default")
      (node (ref "9") (pin "6") (pinfunction "KL_6") (pintype "passive"))
      (node (ref "IC14") (pin "13") (pinfunction "O4_13") (pintype "open_collector"))
      (node (ref "TP98") (pin "TP") (pinfunction "PP_TP") (pintype "input"))
    )
    (net (code "100") (name "Net-(9J-KL)") (class "Default")
      (node (ref "9") (pin "7") (pinfunction "KL_7") (pintype "passive"))
      (node (ref "IC14") (pin "14") (pinfunction "O3_14") (pintype "open_collector"))
      (node (ref "TP99") (pin "TP") (pinfunction "PP_TP") (pintype "input"))
    )
    (net (code "101") (name "Net-(9K-KL)") (class "Default")
      (node (ref "9") (pin "8") (pinfunction "KL_8") (pintype "passive"))
      (node (ref "Q14") (pin "3") (pinfunction "D_3") (pintype "passive"))
      (node (ref "TP100") (pin "TP") (pinfunction "PP_TP") (pintype "input"))
    )
    (net (code "102") (name "Net-(9L-KL)") (class "Default")
      (node (ref "9") (pin "9") (pinfunction "KL_9") (pintype "passive"))
      (node (ref "D13") (pin "1") (pinfunction "+_1") (pintype "passive"))
      (node (ref "TP101") (pin "TP") (pinfunction "PP_TP") (pintype "input"))
      (node (ref "X4") (pin "17") (pinfunction "17_17") (pintype "passive"))
    )
    (net (code "103") (name "Net-(10B-KL)") (class "Default")
      (node (ref "10") (pin "10") (pinfunction "KL_10") (pintype "passive"))
      (node (ref "TP112") (pin "TP") (pinfunction "PP_TP") (pintype "input"))
      (node (ref "X4") (pin "15") (pinfunction "15_15") (pintype "passive"))
    )
    (net (code "104") (name "Net-(10C-KL)") (class "Default")
      (node (ref "10") (pin "11") (pinfunction "KL_11") (pintype "passive"))
      (node (ref "IC14") (pin "16") (pinfunction "O1_16") (pintype "open_collector"))
      (node (ref "R82") (pin "1") (pinfunction "1_1") (pintype "passive"))
      (node (ref "R89") (pin "2") (pinfunction "2_2") (pintype "passive"))
      (node (ref "TP113") (pin "TP") (pinfunction "PP_TP") (pintype "input"))
    )
    (net (code "105") (name "Net-(10D-KL)") (class "Default")
      (node (ref "10") (pin "12") (pinfunction "KL_12") (pintype "passive"))
      (node (ref "R83") (pin "1") (pinfunction "1_1") (pintype "passive"))
      (node (ref "TP115") (pin "TP") (pinfunction "PP_TP") (pintype "input"))
    )
    (net (code "106") (name "Net-(10E-KL)") (class "Default")
      (node (ref "10") (pin "2") (pinfunction "KL_2") (pintype "passive"))
      (node (ref "D18") (pin "2") (pinfunction "-_2") (pintype "passive"))
      (node (ref "LED7") (pin "K") (pinfunction "C_K") (pintype "passive"))
      (node (ref "TP104") (pin "TP") (pinfunction "PP_TP") (pintype "input"))
      (node (ref "X4") (pin "12") (pinfunction "12_12") (pintype "passive"))
    )
    (net (code "107") (name "Net-(10F-KL)") (class "Default")
      (node (ref "10") (pin "3") (pinfunction "KL_3") (pintype "passive"))
      (node (ref "D17") (pin "2") (pinfunction "-_2") (pintype "passive"))
      (node (ref "LED8") (pin "K") (pinfunction "C_K") (pintype "passive"))
      (node (ref "TP105") (pin "TP") (pinfunction "PP_TP") (pintype "input"))
      (node (ref "X4") (pin "11") (pinfunction "11_11") (pintype "passive"))
    )
    (net (code "108") (name "Net-(10G-KL)") (class "Default")
      (node (ref "10") (pin "4") (pinfunction "KL_4") (pintype "passive"))
      (node (ref "D16") (pin "2") (pinfunction "-_2") (pintype "passive"))
      (node (ref "LED9") (pin "K") (pinfunction "C_K") (pintype "passive"))
      (node (ref "TP106") (pin "TP") (pinfunction "PP_TP") (pintype "input"))
      (node (ref "X4") (pin "10") (pinfunction "10_10") (pintype "passive"))
    )
    (net (code "109") (name "Net-(10H-KL)") (class "Default")
      (node (ref "10") (pin "5") (pinfunction "KL_5") (pintype "passive"))
      (node (ref "D15") (pin "2") (pinfunction "-_2") (pintype "passive"))
      (node (ref "LED10") (pin "K") (pinfunction "C_K") (pintype "passive"))
      (node (ref "TP107") (pin "TP") (pinfunction "PP_TP") (pintype "input"))
      (node (ref "X4") (pin "9") (pinfunction "9_9") (pintype "passive"))
    )
    (net (code "110") (name "Net-(10I-KL)") (class "Default")
      (node (ref "10") (pin "6") (pinfunction "KL_6") (pintype "passive"))
      (node (ref "JP7") (pin "2") (pinfunction "2_2") (pintype "passive"))
      (node (ref "TP108") (pin "TP") (pinfunction "PP_TP") (pintype "input"))
    )
    (net (code "111") (name "Net-(10J-KL)") (class "Default")
      (node (ref "10") (pin "7") (pinfunction "KL_7") (pintype "passive"))
      (node (ref "LED11") (pin "A") (pinfunction "A_A") (pintype "passive"))
      (node (ref "TP109") (pin "TP") (pinfunction "PP_TP") (pintype "input"))
      (node (ref "X4") (pin "8") (pinfunction "8_8") (pintype "passive"))
    )
    (net (code "112") (name "Net-(10K-KL)") (class "Default")
      (node (ref "10") (pin "8") (pinfunction "KL_8") (pintype "passive"))
      (node (ref "D19") (pin "2") (pinfunction "-_2") (pintype "passive"))
      (node (ref "LED12") (pin "K") (pinfunction "C_K") (pintype "passive"))
      (node (ref "TP110") (pin "TP") (pinfunction "PP_TP") (pintype "input"))
      (node (ref "X4") (pin "14") (pinfunction "14_14") (pintype "passive"))
    )
    (net (code "113") (name "Net-(10L-KL)") (class "Default")
      (node (ref "10") (pin "9") (pinfunction "KL_9") (pintype "passive"))
      (node (ref "D16") (pin "1") (pinfunction "+_1") (pintype "passive"))
      (node (ref "D17") (pin "1") (pinfunction "+_1") (pintype "passive"))
      (node (ref "JP8") (pin "1") (pinfunction "1_1") (pintype "passive"))
      (node (ref "JP9") (pin "2") (pinfunction "2_2") (pintype "passive"))
      (node (ref "TP111") (pin "TP") (pinfunction "PP_TP") (pintype "input"))
    )
    (net (code "114") (name "Net-(11A-KL)") (class "Default")
      (node (ref "11") (pin "1") (pinfunction "KL_1") (pintype "passive"))
      (node (ref "TP116") (pin "TP") (pinfunction "PP_TP") (pintype "input"))
      (node (ref "X7") (pin "1") (pinfunction "1_1") (pintype "passive"))
    )
    (net (code "115") (name "Net-(11B-KL)") (class "Default")
      (node (ref "11") (pin "10") (pinfunction "KL_10") (pintype "passive"))
      (node (ref "D24") (pin "2") (pinfunction "-_2") (pintype "passive"))
      (node (ref "D25") (pin "2") (pinfunction "-_2") (pintype "passive"))
      (node (ref "JP15") (pin "1") (pinfunction "1_1") (pintype "passive"))
      (node (ref "SJ3") (pin "1") (pinfunction "1_1") (pintype "passive"))
      (node (ref "TP125") (pin "TP") (pinfunction "PP_TP") (pintype "input"))
    )
    (net (code "116") (name "Net-(11C-KL)") (class "Default")
      (node (ref "11") (pin "11") (pinfunction "KL_11") (pintype "passive"))
      (node (ref "D25") (pin "1") (pinfunction "+_1") (pintype "passive"))
      (node (ref "TP126") (pin "TP") (pinfunction "PP_TP") (pintype "input"))
      (node (ref "X7") (pin "19") (pinfunction "19_19") (pintype "passive"))
    )
    (net (code "117") (name "Net-(11E-KL)") (class "Default")
      (node (ref "11") (pin "2") (pinfunction "KL_2") (pintype "passive"))
      (node (ref "Q17") (pin "2") (pinfunction "C_2") (pintype "passive"))
      (node (ref "TP117") (pin "TP") (pinfunction "PP_TP") (pintype "input"))
    )
    (net (code "118") (name "Net-(11F-KL)") (class "Default")
      (node (ref "11") (pin "3") (pinfunction "KL_3") (pintype "passive"))
      (node (ref "IC24") (pin "11") (pinfunction "O6_11") (pintype "open_collector"))
      (node (ref "TP118") (pin "TP") (pinfunction "PP_TP") (pintype "input"))
    )
    (net (code "119") (name "Net-(11G-KL)") (class "Default")
      (node (ref "11") (pin "4") (pinfunction "KL_4") (pintype "passive"))
      (node (ref "IC24") (pin "10") (pinfunction "O7_10") (pintype "open_collector"))
      (node (ref "TP119") (pin "TP") (pinfunction "PP_TP") (pintype "input"))
    )
    (net (code "120") (name "Net-(11H-KL)") (class "Default")
      (node (ref "11") (pin "5") (pinfunction "KL_5") (pintype "passive"))
      (node (ref "IC24") (pin "12") (pinfunction "O5_12") (pintype "open_collector"))
      (node (ref "TP120") (pin "TP") (pinfunction "PP_TP") (pintype "input"))
    )
    (net (code "121") (name "Net-(11I-KL)") (class "Default")
      (node (ref "11") (pin "6") (pinfunction "KL_6") (pintype "passive"))
      (node (ref "IC24") (pin "13") (pinfunction "O4_13") (pintype "open_collector"))
      (node (ref "TP121") (pin "TP") (pinfunction "PP_TP") (pintype "input"))
    )
    (net (code "122") (name "Net-(11J-KL)") (class "Default")
      (node (ref "11") (pin "7") (pinfunction "KL_7") (pintype "passive"))
      (node (ref "IC24") (pin "14") (pinfunction "O3_14") (pintype "open_collector"))
      (node (ref "TP122") (pin "TP") (pinfunction "PP_TP") (pintype "input"))
    )
    (net (code "123") (name "Net-(11K-KL)") (class "Default")
      (node (ref "11") (pin "8") (pinfunction "KL_8") (pintype "passive"))
      (node (ref "Q21") (pin "3") (pinfunction "D_3") (pintype "passive"))
      (node (ref "TP123") (pin "TP") (pinfunction "PP_TP") (pintype "input"))
    )
    (net (code "124") (name "Net-(11L-KL)") (class "Default")
      (node (ref "11") (pin "9") (pinfunction "KL_9") (pintype "passive"))
      (node (ref "D24") (pin "1") (pinfunction "+_1") (pintype "passive"))
      (node (ref "TP124") (pin "TP") (pinfunction "PP_TP") (pintype "input"))
      (node (ref "X7") (pin "17") (pinfunction "17_17") (pintype "passive"))
    )
    (net (code "125") (name "Net-(12B-KL)") (class "Default")
      (node (ref "12") (pin "10") (pinfunction "KL_10") (pintype "passive"))
      (node (ref "TP135") (pin "TP") (pinfunction "PP_TP") (pintype "input"))
      (node (ref "X7") (pin "15") (pinfunction "15_15") (pintype "passive"))
    )
    (net (code "126") (name "Net-(12C-KL)") (class "Default")
      (node (ref "12") (pin "11") (pinfunction "KL_11") (pintype "passive"))
      (node (ref "IC24") (pin "16") (pinfunction "O1_16") (pintype "open_collector"))
      (node (ref "R172") (pin "1") (pinfunction "1_1") (pintype "passive"))
      (node (ref "R179") (pin "2") (pinfunction "2_2") (pintype "passive"))
      (node (ref "TP136") (pin "TP") (pinfunction "PP_TP") (pintype "input"))
    )
    (net (code "127") (name "Net-(12D-KL)") (class "Default")
      (node (ref "12") (pin "12") (pinfunction "KL_12") (pintype "passive"))
      (node (ref "R173") (pin "1") (pinfunction "1_1") (pintype "passive"))
      (node (ref "TP138") (pin "TP") (pinfunction "PP_TP") (pintype "input"))
    )
    (net (code "128") (name "Net-(12E-KL)") (class "Default")
      (node (ref "12") (pin "2") (pinfunction "KL_2") (pintype "passive"))
      (node (ref "D29") (pin "2") (pinfunction "-_2") (pintype "passive"))
      (node (ref "LED13") (pin "K") (pinfunction "C_K") (pintype "passive"))
      (node (ref "TP127") (pin "TP") (pinfunction "PP_TP") (pintype "input"))
      (node (ref "X7") (pin "12") (pinfunction "12_12") (pintype "passive"))
    )
    (net (code "129") (name "Net-(12F-KL)") (class "Default")
      (node (ref "12") (pin "3") (pinfunction "KL_3") (pintype "passive"))
      (node (ref "D28") (pin "2") (pinfunction "-_2") (pintype "passive"))
      (node (ref "LED14") (pin "K") (pinfunction "C_K") (pintype "passive"))
      (node (ref "TP128") (pin "TP") (pinfunction "PP_TP") (pintype "input"))
      (node (ref "X7") (pin "11") (pinfunction "11_11") (pintype "passive"))
    )
    (net (code "130") (name "Net-(12G-KL)") (class "Default")
      (node (ref "12") (pin "4") (pinfunction "KL_4") (pintype "passive"))
      (node (ref "D27") (pin "2") (pinfunction "-_2") (pintype "passive"))
      (node (ref "LED15") (pin "K") (pinfunction "C_K") (pintype "passive"))
      (node (ref "TP129") (pin "TP") (pinfunction "PP_TP") (pintype "input"))
      (node (ref "X7") (pin "10") (pinfunction "10_10") (pintype "passive"))
    )
    (net (code "131") (name "Net-(12H-KL)") (class "Default")
      (node (ref "12") (pin "5") (pinfunction "KL_5") (pintype "passive"))
      (node (ref "D26") (pin "2") (pinfunction "-_2") (pintype "passive"))
      (node (ref "LED16") (pin "K") (pinfunction "C_K") (pintype "passive"))
      (node (ref "TP130") (pin "TP") (pinfunction "PP_TP") (pintype "input"))
      (node (ref "X7") (pin "9") (pinfunction "9_9") (pintype "passive"))
    )
    (net (code "132") (name "Net-(12I-KL)") (class "Default")
      (node (ref "12") (pin "6") (pinfunction "KL_6") (pintype "passive"))
      (node (ref "JP12") (pin "2") (pinfunction "2_2") (pintype "passive"))
      (node (ref "TP131") (pin "TP") (pinfunction "PP_TP") (pintype "input"))
    )
    (net (code "133") (name "Net-(12J-KL)") (class "Default")
      (node (ref "12") (pin "7") (pinfunction "KL_7") (pintype "passive"))
      (node (ref "LED17") (pin "A") (pinfunction "A_A") (pintype "passive"))
      (node (ref "TP132") (pin "TP") (pinfunction "PP_TP") (pintype "input"))
      (node (ref "X7") (pin "8") (pinfunction "8_8") (pintype "passive"))
    )
    (net (code "134") (name "Net-(12K-KL)") (class "Default")
      (node (ref "12") (pin "8") (pinfunction "KL_8") (pintype "passive"))
      (node (ref "D30") (pin "2") (pinfunction "-_2") (pintype "passive"))
      (node (ref "LED18") (pin "K") (pinfunction "C_K") (pintype "passive"))
      (node (ref "TP133") (pin "TP") (pinfunction "PP_TP") (pintype "input"))
      (node (ref "X7") (pin "14") (pinfunction "14_14") (pintype "passive"))
    )
    (net (code "135") (name "Net-(12L-KL)") (class "Default")
      (node (ref "12") (pin "9") (pinfunction "KL_9") (pintype "passive"))
      (node (ref "D27") (pin "1") (pinfunction "+_1") (pintype "passive"))
      (node (ref "D28") (pin "1") (pinfunction "+_1") (pintype "passive"))
      (node (ref "JP13") (pin "1") (pinfunction "1_1") (pintype "passive"))
      (node (ref "JP14") (pin "2") (pinfunction "2_2") (pintype "passive"))
      (node (ref "TP134") (pin "TP") (pinfunction "PP_TP") (pintype "input"))
    )
    (net (code "136") (name "Net-(13A-KL)") (class "Default")
      (node (ref "13") (pin "1") (pinfunction "KL_1") (pintype "passive"))
      (node (ref "TP139") (pin "TP") (pinfunction "PP_TP") (pintype "input"))
      (node (ref "X401") (pin "1") (pinfunction "1_1") (pintype "passive"))
    )
    (net (code "137") (name "Net-(13B-KL)") (class "Default")
      (node (ref "13") (pin "10") (pinfunction "KL_10") (pintype "passive"))
      (node (ref "D402") (pin "2") (pinfunction "-_2") (pintype "passive"))
      (node (ref "D403") (pin "2") (pinfunction "-_2") (pintype "passive"))
      (node (ref "JP404") (pin "1") (pinfunction "1_1") (pintype "passive"))
      (node (ref "SJ401") (pin "1") (pinfunction "1_1") (pintype "passive"))
      (node (ref "TP148") (pin "TP") (pinfunction "PP_TP") (pintype "input"))
    )
    (net (code "138") (name "Net-(13C-KL)") (class "Default")
      (node (ref "13") (pin "11") (pinfunction "KL_11") (pintype "passive"))
      (node (ref "D403") (pin "1") (pinfunction "+_1") (pintype "passive"))
      (node (ref "TP149") (pin "TP") (pinfunction "PP_TP") (pintype "input"))
      (node (ref "X401") (pin "19") (pinfunction "19_19") (pintype "passive"))
    )
    (net (code "139") (name "Net-(13E-KL)") (class "Default")
      (node (ref "13") (pin "2") (pinfunction "KL_2") (pintype "passive"))
      (node (ref "Q401") (pin "2") (pinfunction "C_2") (pintype "passive"))
      (node (ref "TP140") (pin "TP") (pinfunction "PP_TP") (pintype "input"))
    )
    (net (code "140") (name "Net-(13F-KL)") (class "Default")
      (node (ref "13") (pin "3") (pinfunction "KL_3") (pintype "passive"))
      (node (ref "IC407") (pin "11") (pinfunction "O6_11") (pintype "open_collector"))
      (node (ref "TP141") (pin "TP") (pinfunction "PP_TP") (pintype "input"))
    )
    (net (code "141") (name "Net-(13G-KL)") (class "Default")
      (node (ref "13") (pin "4") (pinfunction "KL_4") (pintype "passive"))
      (node (ref "IC407") (pin "10") (pinfunction "O7_10") (pintype "open_collector"))
      (node (ref "TP142") (pin "TP") (pinfunction "PP_TP") (pintype "input"))
    )
    (net (code "142") (name "Net-(13H-KL)") (class "Default")
      (node (ref "13") (pin "5") (pinfunction "KL_5") (pintype "passive"))
      (node (ref "IC407") (pin "12") (pinfunction "O5_12") (pintype "open_collector"))
      (node (ref "TP143") (pin "TP") (pinfunction "PP_TP") (pintype "input"))
    )
    (net (code "143") (name "Net-(13I-KL)") (class "Default")
      (node (ref "13") (pin "6") (pinfunction "KL_6") (pintype "passive"))
      (node (ref "IC407") (pin "13") (pinfunction "O4_13") (pintype "open_collector"))
      (node (ref "TP144") (pin "TP") (pinfunction "PP_TP") (pintype "input"))
    )
    (net (code "144") (name "Net-(13J-KL)") (class "Default")
      (node (ref "13") (pin "7") (pinfunction "KL_7") (pintype "passive"))
      (node (ref "IC407") (pin "14") (pinfunction "O3_14") (pintype "open_collector"))
      (node (ref "TP145") (pin "TP") (pinfunction "PP_TP") (pintype "input"))
    )
    (net (code "145") (name "Net-(13K-KL)") (class "Default")
      (node (ref "13") (pin "8") (pinfunction "KL_8") (pintype "passive"))
      (node (ref "Q406") (pin "3") (pinfunction "D_3") (pintype "passive"))
      (node (ref "TP146") (pin "TP") (pinfunction "PP_TP") (pintype "input"))
    )
    (net (code "146") (name "Net-(13L-KL)") (class "Default")
      (node (ref "13") (pin "9") (pinfunction "KL_9") (pintype "passive"))
      (node (ref "D402") (pin "1") (pinfunction "+_1") (pintype "passive"))
      (node (ref "TP147") (pin "TP") (pinfunction "PP_TP") (pintype "input"))
      (node (ref "X401") (pin "17") (pinfunction "17_17") (pintype "passive"))
    )
    (net (code "147") (name "Net-(14B-KL)") (class "Default")
      (node (ref "14") (pin "10") (pinfunction "KL_10") (pintype "passive"))
      (node (ref "TP158") (pin "TP") (pinfunction "PP_TP") (pintype "input"))
      (node (ref "X401") (pin "15") (pinfunction "15_15") (pintype "passive"))
    )
    (net (code "148") (name "Net-(14C-KL)") (class "Default")
      (node (ref "14") (pin "11") (pinfunction "KL_11") (pintype "passive"))
      (node (ref "IC407") (pin "16") (pinfunction "O1_16") (pintype "open_collector"))
      (node (ref "R418") (pin "2") (pinfunction "2_2") (pintype "passive"))
      (node (ref "R419") (pin "1") (pinfunction "1_1") (pintype "passive"))
      (node (ref "TP159") (pin "TP") (pinfunction "PP_TP") (pintype "input"))
    )
    (net (code "149") (name "Net-(14D-KL)") (class "Default")
      (node (ref "14") (pin "12") (pinfunction "KL_12") (pintype "passive"))
      (node (ref "R446") (pin "1") (pinfunction "1_1") (pintype "passive"))
      (node (ref "TP161") (pin "TP") (pinfunction "PP_TP") (pintype "input"))
    )
    (net (code "150") (name "Net-(14E-KL)") (class "Default")
      (node (ref "14") (pin "2") (pinfunction "KL_2") (pintype "passive"))
      (node (ref "D409") (pin "2") (pinfunction "-_2") (pintype "passive"))
      (node (ref "LED402") (pin "K") (pinfunction "C_K") (pintype "passive"))
      (node (ref "TP150") (pin "TP") (pinfunction "PP_TP") (pintype "input"))
      (node (ref "X401") (pin "12") (pinfunction "12_12") (pintype "passive"))
    )
    (net (code "151") (name "Net-(14F-KL)") (class "Default")
      (node (ref "14") (pin "3") (pinfunction "KL_3") (pintype "passive"))
      (node (ref "D408") (pin "2") (pinfunction "-_2") (pintype "passive"))
      (node (ref "LED403") (pin "K") (pinfunction "C_K") (pintype "passive"))
      (node (ref "TP151") (pin "TP") (pinfunction "PP_TP") (pintype "input"))
      (node (ref "X401") (pin "11") (pinfunction "11_11") (pintype "passive"))
    )
    (net (code "152") (name "Net-(14G-KL)") (class "Default")
      (node (ref "14") (pin "4") (pinfunction "KL_4") (pintype "passive"))
      (node (ref "D407") (pin "2") (pinfunction "-_2") (pintype "passive"))
      (node (ref "LED404") (pin "K") (pinfunction "C_K") (pintype "passive"))
      (node (ref "TP152") (pin "TP") (pinfunction "PP_TP") (pintype "input"))
      (node (ref "X401") (pin "10") (pinfunction "10_10") (pintype "passive"))
    )
    (net (code "153") (name "Net-(14H-KL)") (class "Default")
      (node (ref "14") (pin "5") (pinfunction "KL_5") (pintype "passive"))
      (node (ref "D406") (pin "2") (pinfunction "-_2") (pintype "passive"))
      (node (ref "LED405") (pin "K") (pinfunction "C_K") (pintype "passive"))
      (node (ref "TP153") (pin "TP") (pinfunction "PP_TP") (pintype "input"))
      (node (ref "X401") (pin "9") (pinfunction "9_9") (pintype "passive"))
    )
    (net (code "154") (name "Net-(14I-KL)") (class "Default")
      (node (ref "14") (pin "6") (pinfunction "KL_6") (pintype "passive"))
      (node (ref "JP405") (pin "2") (pinfunction "2_2") (pintype "passive"))
      (node (ref "TP154") (pin "TP") (pinfunction "PP_TP") (pintype "input"))
    )
    (net (code "155") (name "Net-(14J-KL)") (class "Default")
      (node (ref "14") (pin "7") (pinfunction "KL_7") (pintype "passive"))
      (node (ref "LED401") (pin "A") (pinfunction "A_A") (pintype "passive"))
      (node (ref "TP155") (pin "TP") (pinfunction "PP_TP") (pintype "input"))
      (node (ref "X401") (pin "8") (pinfunction "8_8") (pintype "passive"))
    )
    (net (code "156") (name "Net-(14K-KL)") (class "Default")
      (node (ref "14") (pin "8") (pinfunction "KL_8") (pintype "passive"))
      (node (ref "D410") (pin "2") (pinfunction "-_2") (pintype "passive"))
      (node (ref "LED406") (pin "K") (pinfunction "C_K") (pintype "passive"))
      (node (ref "TP156") (pin "TP") (pinfunction "PP_TP") (pintype "input"))
      (node (ref "X401") (pin "14") (pinfunction "14_14") (pintype "passive"))
    )
    (net (code "157") (name "Net-(14L-KL)") (class "Default")
      (node (ref "14") (pin "9") (pinfunction "KL_9") (pintype "passive"))
      (node (ref "D407") (pin "1") (pinfunction "+_1") (pintype "passive"))
      (node (ref "D408") (pin "1") (pinfunction "+_1") (pintype "passive"))
      (node (ref "JP402") (pin "1") (pinfunction "1_1") (pintype "passive"))
      (node (ref "JP403") (pin "2") (pinfunction "2_2") (pintype "passive"))
      (node (ref "TP157") (pin "TP") (pinfunction "PP_TP") (pintype "input"))
    )
    (net (code "158") (name "Net-(15A-KL)") (class "Default")
      (node (ref "15") (pin "1") (pinfunction "KL_1") (pintype "passive"))
      (node (ref "TP162") (pin "TP") (pinfunction "PP_TP") (pintype "input"))
      (node (ref "X501") (pin "1") (pinfunction "1_1") (pintype "passive"))
    )
    (net (code "159") (name "Net-(15B-KL)") (class "Default")
      (node (ref "15") (pin "10") (pinfunction "KL_10") (pintype "passive"))
      (node (ref "D502") (pin "2") (pinfunction "-_2") (pintype "passive"))
      (node (ref "D503") (pin "2") (pinfunction "-_2") (pintype "passive"))
      (node (ref "JP504") (pin "1") (pinfunction "1_1") (pintype "passive"))
      (node (ref "SJ501") (pin "1") (pinfunction "1_1") (pintype "passive"))
      (node (ref "TP171") (pin "TP") (pinfunction "PP_TP") (pintype "input"))
    )
    (net (code "160") (name "Net-(15C-KL)") (class "Default")
      (node (ref "15") (pin "11") (pinfunction "KL_11") (pintype "passive"))
      (node (ref "D503") (pin "1") (pinfunction "+_1") (pintype "passive"))
      (node (ref "TP172") (pin "TP") (pinfunction "PP_TP") (pintype "input"))
      (node (ref "X501") (pin "19") (pinfunction "19_19") (pintype "passive"))
    )
    (net (code "161") (name "Net-(15E-KL)") (class "Default")
      (node (ref "15") (pin "2") (pinfunction "KL_2") (pintype "passive"))
      (node (ref "Q501") (pin "2") (pinfunction "C_2") (pintype "passive"))
      (node (ref "TP163") (pin "TP") (pinfunction "PP_TP") (pintype "input"))
    )
    (net (code "162") (name "Net-(15F-KL)") (class "Default")
      (node (ref "15") (pin "3") (pinfunction "KL_3") (pintype "passive"))
      (node (ref "IC507") (pin "11") (pinfunction "O6_11") (pintype "open_collector"))
      (node (ref "TP164") (pin "TP") (pinfunction "PP_TP") (pintype "input"))
    )
    (net (code "163") (name "Net-(15G-KL)") (class "Default")
      (node (ref "15") (pin "4") (pinfunction "KL_4") (pintype "passive"))
      (node (ref "IC507") (pin "10") (pinfunction "O7_10") (pintype "open_collector"))
      (node (ref "TP165") (pin "TP") (pinfunction "PP_TP") (pintype "input"))
    )
    (net (code "164") (name "Net-(15H-KL)") (class "Default")
      (node (ref "15") (pin "5") (pinfunction "KL_5") (pintype "passive"))
      (node (ref "IC507") (pin "12") (pinfunction "O5_12") (pintype "open_collector"))
      (node (ref "TP166") (pin "TP") (pinfunction "PP_TP") (pintype "input"))
    )
    (net (code "165") (name "Net-(15I-KL)") (class "Default")
      (node (ref "15") (pin "6") (pinfunction "KL_6") (pintype "passive"))
      (node (ref "IC507") (pin "13") (pinfunction "O4_13") (pintype "open_collector"))
      (node (ref "TP167") (pin "TP") (pinfunction "PP_TP") (pintype "input"))
    )
    (net (code "166") (name "Net-(15J-KL)") (class "Default")
      (node (ref "15") (pin "7") (pinfunction "KL_7") (pintype "passive"))
      (node (ref "IC507") (pin "14") (pinfunction "O3_14") (pintype "open_collector"))
      (node (ref "TP168") (pin "TP") (pinfunction "PP_TP") (pintype "input"))
    )
    (net (code "167") (name "Net-(15K-KL)") (class "Default")
      (node (ref "15") (pin "8") (pinfunction "KL_8") (pintype "passive"))
      (node (ref "Q506") (pin "3") (pinfunction "D_3") (pintype "passive"))
      (node (ref "TP169") (pin "TP") (pinfunction "PP_TP") (pintype "input"))
    )
    (net (code "168") (name "Net-(15L-KL)") (class "Default")
      (node (ref "15") (pin "9") (pinfunction "KL_9") (pintype "passive"))
      (node (ref "D502") (pin "1") (pinfunction "+_1") (pintype "passive"))
      (node (ref "TP170") (pin "TP") (pinfunction "PP_TP") (pintype "input"))
      (node (ref "X501") (pin "17") (pinfunction "17_17") (pintype "passive"))
    )
    (net (code "169") (name "Net-(16B-KL)") (class "Default")
      (node (ref "16") (pin "10") (pinfunction "KL_10") (pintype "passive"))
      (node (ref "TP181") (pin "TP") (pinfunction "PP_TP") (pintype "input"))
      (node (ref "X501") (pin "15") (pinfunction "15_15") (pintype "passive"))
    )
    (net (code "170") (name "Net-(16C-KL)") (class "Default")
      (node (ref "16") (pin "11") (pinfunction "KL_11") (pintype "passive"))
      (node (ref "IC507") (pin "16") (pinfunction "O1_16") (pintype "open_collector"))
      (node (ref "R518") (pin "2") (pinfunction "2_2") (pintype "passive"))
      (node (ref "R519") (pin "1") (pinfunction "1_1") (pintype "passive"))
      (node (ref "TP182") (pin "TP") (pinfunction "PP_TP") (pintype "input"))
    )
    (net (code "171") (name "Net-(16D-KL)") (class "Default")
      (node (ref "16") (pin "12") (pinfunction "KL_12") (pintype "passive"))
      (node (ref "R546") (pin "1") (pinfunction "1_1") (pintype "passive"))
      (node (ref "TP184") (pin "TP") (pinfunction "PP_TP") (pintype "input"))
    )
    (net (code "172") (name "Net-(16E-KL)") (class "Default")
      (node (ref "16") (pin "2") (pinfunction "KL_2") (pintype "passive"))
      (node (ref "D509") (pin "2") (pinfunction "-_2") (pintype "passive"))
      (node (ref "LED502") (pin "K") (pinfunction "C_K") (pintype "passive"))
      (node (ref "TP173") (pin "TP") (pinfunction "PP_TP") (pintype "input"))
      (node (ref "X501") (pin "12") (pinfunction "12_12") (pintype "passive"))
    )
    (net (code "173") (name "Net-(16F-KL)") (class "Default")
      (node (ref "16") (pin "3") (pinfunction "KL_3") (pintype "passive"))
      (node (ref "D508") (pin "2") (pinfunction "-_2") (pintype "passive"))
      (node (ref "LED503") (pin "K") (pinfunction "C_K") (pintype "passive"))
      (node (ref "TP174") (pin "TP") (pinfunction "PP_TP") (pintype "input"))
      (node (ref "X501") (pin "11") (pinfunction "11_11") (pintype "passive"))
    )
    (net (code "174") (name "Net-(16G-KL)") (class "Default")
      (node (ref "16") (pin "4") (pinfunction "KL_4") (pintype "passive"))
      (node (ref "D507") (pin "2") (pinfunction "-_2") (pintype "passive"))
      (node (ref "LED504") (pin "K") (pinfunction "C_K") (pintype "passive"))
      (node (ref "TP175") (pin "TP") (pinfunction "PP_TP") (pintype "input"))
      (node (ref "X501") (pin "10") (pinfunction "10_10") (pintype "passive"))
    )
    (net (code "175") (name "Net-(16H-KL)") (class "Default")
      (node (ref "16") (pin "5") (pinfunction "KL_5") (pintype "passive"))
      (node (ref "D506") (pin "2") (pinfunction "-_2") (pintype "passive"))
      (node (ref "LED505") (pin "K") (pinfunction "C_K") (pintype "passive"))
      (node (ref "TP176") (pin "TP") (pinfunction "PP_TP") (pintype "input"))
      (node (ref "X501") (pin "9") (pinfunction "9_9") (pintype "passive"))
    )
    (net (code "176") (name "Net-(16I-KL)") (class "Default")
      (node (ref "16") (pin "6") (pinfunction "KL_6") (pintype "passive"))
      (node (ref "JP505") (pin "2") (pinfunction "2_2") (pintype "passive"))
      (node (ref "TP177") (pin "TP") (pinfunction "PP_TP") (pintype "input"))
    )
    (net (code "177") (name "Net-(16J-KL)") (class "Default")
      (node (ref "16") (pin "7") (pinfunction "KL_7") (pintype "passive"))
      (node (ref "LED501") (pin "A") (pinfunction "A_A") (pintype "passive"))
      (node (ref "TP178") (pin "TP") (pinfunction "PP_TP") (pintype "input"))
      (node (ref "X501") (pin "8") (pinfunction "8_8") (pintype "passive"))
    )
    (net (code "178") (name "Net-(16K-KL)") (class "Default")
      (node (ref "16") (pin "8") (pinfunction "KL_8") (pintype "passive"))
      (node (ref "D510") (pin "2") (pinfunction "-_2") (pintype "passive"))
      (node (ref "LED506") (pin "K") (pinfunction "C_K") (pintype "passive"))
      (node (ref "TP179") (pin "TP") (pinfunction "PP_TP") (pintype "input"))
      (node (ref "X501") (pin "14") (pinfunction "14_14") (pintype "passive"))
    )
    (net (code "179") (name "Net-(16L-KL)") (class "Default")
      (node (ref "16") (pin "9") (pinfunction "KL_9") (pintype "passive"))
      (node (ref "D507") (pin "1") (pinfunction "+_1") (pintype "passive"))
      (node (ref "D508") (pin "1") (pinfunction "+_1") (pintype "passive"))
      (node (ref "JP502") (pin "1") (pinfunction "1_1") (pintype "passive"))
      (node (ref "JP503") (pin "2") (pinfunction "2_2") (pintype "passive"))
      (node (ref "TP180") (pin "TP") (pinfunction "PP_TP") (pintype "input"))
    )
    (net (code "180") (name "Net-(17A-KL)") (class "Default")
      (node (ref "17") (pin "1") (pinfunction "KL_1") (pintype "passive"))
      (node (ref "TP185") (pin "TP") (pinfunction "PP_TP") (pintype "input"))
      (node (ref "X601") (pin "1") (pinfunction "1_1") (pintype "passive"))
    )
    (net (code "181") (name "Net-(17B-KL)") (class "Default")
      (node (ref "17") (pin "10") (pinfunction "KL_10") (pintype "passive"))
      (node (ref "D602") (pin "2") (pinfunction "-_2") (pintype "passive"))
      (node (ref "D603") (pin "2") (pinfunction "-_2") (pintype "passive"))
      (node (ref "JP604") (pin "1") (pinfunction "1_1") (pintype "passive"))
      (node (ref "SJ601") (pin "1") (pinfunction "1_1") (pintype "passive"))
      (node (ref "TP194") (pin "TP") (pinfunction "PP_TP") (pintype "input"))
    )
    (net (code "182") (name "Net-(17C-KL)") (class "Default")
      (node (ref "17") (pin "11") (pinfunction "KL_11") (pintype "passive"))
      (node (ref "D603") (pin "1") (pinfunction "+_1") (pintype "passive"))
      (node (ref "TP195") (pin "TP") (pinfunction "PP_TP") (pintype "input"))
      (node (ref "X601") (pin "19") (pinfunction "19_19") (pintype "passive"))
    )
    (net (code "183") (name "Net-(17E-KL)") (class "Default")
      (node (ref "17") (pin "2") (pinfunction "KL_2") (pintype "passive"))
      (node (ref "Q601") (pin "2") (pinfunction "C_2") (pintype "passive"))
      (node (ref "TP186") (pin "TP") (pinfunction "PP_TP") (pintype "input"))
    )
    (net (code "184") (name "Net-(17F-KL)") (class "Default")
      (node (ref "17") (pin "3") (pinfunction "KL_3") (pintype "passive"))
      (node (ref "IC607") (pin "11") (pinfunction "O6_11") (pintype "open_collector"))
      (node (ref "TP187") (pin "TP") (pinfunction "PP_TP") (pintype "input"))
    )
    (net (code "185") (name "Net-(17G-KL)") (class "Default")
      (node (ref "17") (pin "4") (pinfunction "KL_4") (pintype "passive"))
      (node (ref "IC607") (pin "10") (pinfunction "O7_10") (pintype "open_collector"))
      (node (ref "TP188") (pin "TP") (pinfunction "PP_TP") (pintype "input"))
    )
    (net (code "186") (name "Net-(17H-KL)") (class "Default")
      (node (ref "17") (pin "5") (pinfunction "KL_5") (pintype "passive"))
      (node (ref "IC607") (pin "12") (pinfunction "O5_12") (pintype "open_collector"))
      (node (ref "TP189") (pin "TP") (pinfunction "PP_TP") (pintype "input"))
    )
    (net (code "187") (name "Net-(17I-KL)") (class "Default")
      (node (ref "17") (pin "6") (pinfunction "KL_6") (pintype "passive"))
      (node (ref "IC607") (pin "13") (pinfunction "O4_13") (pintype "open_collector"))
      (node (ref "TP190") (pin "TP") (pinfunction "PP_TP") (pintype "input"))
    )
    (net (code "188") (name "Net-(17J-KL)") (class "Default")
      (node (ref "17") (pin "7") (pinfunction "KL_7") (pintype "passive"))
      (node (ref "IC607") (pin "14") (pinfunction "O3_14") (pintype "open_collector"))
      (node (ref "TP191") (pin "TP") (pinfunction "PP_TP") (pintype "input"))
    )
    (net (code "189") (name "Net-(17K-KL)") (class "Default")
      (node (ref "17") (pin "8") (pinfunction "KL_8") (pintype "passive"))
      (node (ref "Q606") (pin "3") (pinfunction "D_3") (pintype "passive"))
      (node (ref "TP192") (pin "TP") (pinfunction "PP_TP") (pintype "input"))
    )
    (net (code "190") (name "Net-(17L-KL)") (class "Default")
      (node (ref "17") (pin "9") (pinfunction "KL_9") (pintype "passive"))
      (node (ref "D602") (pin "1") (pinfunction "+_1") (pintype "passive"))
      (node (ref "TP193") (pin "TP") (pinfunction "PP_TP") (pintype "input"))
      (node (ref "X601") (pin "17") (pinfunction "17_17") (pintype "passive"))
    )
    (net (code "191") (name "Net-(18B-KL)") (class "Default")
      (node (ref "18") (pin "10") (pinfunction "KL_10") (pintype "passive"))
      (node (ref "TP204") (pin "TP") (pinfunction "PP_TP") (pintype "input"))
      (node (ref "X601") (pin "15") (pinfunction "15_15") (pintype "passive"))
    )
    (net (code "192") (name "Net-(18C-KL)") (class "Default")
      (node (ref "18") (pin "11") (pinfunction "KL_11") (pintype "passive"))
      (node (ref "IC607") (pin "16") (pinfunction "O1_16") (pintype "open_collector"))
      (node (ref "R618") (pin "2") (pinfunction "2_2") (pintype "passive"))
      (node (ref "R619") (pin "1") (pinfunction "1_1") (pintype "passive"))
      (node (ref "TP205") (pin "TP") (pinfunction "PP_TP") (pintype "input"))
    )
    (net (code "193") (name "Net-(18D-KL)") (class "Default")
      (node (ref "18") (pin "12") (pinfunction "KL_12") (pintype "passive"))
      (node (ref "R646") (pin "1") (pinfunction "1_1") (pintype "passive"))
      (node (ref "TP207") (pin "TP") (pinfunction "PP_TP") (pintype "input"))
    )
    (net (code "194") (name "Net-(18E-KL)") (class "Default")
      (node (ref "18") (pin "2") (pinfunction "KL_2") (pintype "passive"))
      (node (ref "D609") (pin "2") (pinfunction "-_2") (pintype "passive"))
      (node (ref "LED602") (pin "K") (pinfunction "C_K") (pintype "passive"))
      (node (ref "TP196") (pin "TP") (pinfunction "PP_TP") (pintype "input"))
      (node (ref "X601") (pin "12") (pinfunction "12_12") (pintype "passive"))
    )
    (net (code "195") (name "Net-(18F-KL)") (class "Default")
      (node (ref "18") (pin "3") (pinfunction "KL_3") (pintype "passive"))
      (node (ref "D608") (pin "2") (pinfunction "-_2") (pintype "passive"))
      (node (ref "LED603") (pin "K") (pinfunction "C_K") (pintype "passive"))
      (node (ref "TP197") (pin "TP") (pinfunction "PP_TP") (pintype "input"))
      (node (ref "X601") (pin "11") (pinfunction "11_11") (pintype "passive"))
    )
    (net (code "196") (name "Net-(18G-KL)") (class "Default")
      (node (ref "18") (pin "4") (pinfunction "KL_4") (pintype "passive"))
      (node (ref "D607") (pin "2") (pinfunction "-_2") (pintype "passive"))
      (node (ref "LED604") (pin "K") (pinfunction "C_K") (pintype "passive"))
      (node (ref "TP198") (pin "TP") (pinfunction "PP_TP") (pintype "input"))
      (node (ref "X601") (pin "10") (pinfunction "10_10") (pintype "passive"))
    )
    (net (code "197") (name "Net-(18H-KL)") (class "Default")
      (node (ref "18") (pin "5") (pinfunction "KL_5") (pintype "passive"))
      (node (ref "D606") (pin "2") (pinfunction "-_2") (pintype "passive"))
      (node (ref "LED605") (pin "K") (pinfunction "C_K") (pintype "passive"))
      (node (ref "TP199") (pin "TP") (pinfunction "PP_TP") (pintype "input"))
      (node (ref "X601") (pin "9") (pinfunction "9_9") (pintype "passive"))
    )
    (net (code "198") (name "Net-(18I-KL)") (class "Default")
      (node (ref "18") (pin "6") (pinfunction "KL_6") (pintype "passive"))
      (node (ref "JP605") (pin "2") (pinfunction "2_2") (pintype "passive"))
      (node (ref "TP200") (pin "TP") (pinfunction "PP_TP") (pintype "input"))
    )
    (net (code "199") (name "Net-(18J-KL)") (class "Default")
      (node (ref "18") (pin "7") (pinfunction "KL_7") (pintype "passive"))
      (node (ref "LED601") (pin "A") (pinfunction "A_A") (pintype "passive"))
      (node (ref "TP201") (pin "TP") (pinfunction "PP_TP") (pintype "input"))
      (node (ref "X601") (pin "8") (pinfunction "8_8") (pintype "passive"))
    )
    (net (code "200") (name "Net-(18K-KL)") (class "Default")
      (node (ref "18") (pin "8") (pinfunction "KL_8") (pintype "passive"))
      (node (ref "D610") (pin "2") (pinfunction "-_2") (pintype "passive"))
      (node (ref "LED606") (pin "K") (pinfunction "C_K") (pintype "passive"))
      (node (ref "TP202") (pin "TP") (pinfunction "PP_TP") (pintype "input"))
      (node (ref "X601") (pin "14") (pinfunction "14_14") (pintype "passive"))
    )
    (net (code "201") (name "Net-(18L-KL)") (class "Default")
      (node (ref "18") (pin "9") (pinfunction "KL_9") (pintype "passive"))
      (node (ref "D607") (pin "1") (pinfunction "+_1") (pintype "passive"))
      (node (ref "D608") (pin "1") (pinfunction "+_1") (pintype "passive"))
      (node (ref "JP602") (pin "1") (pinfunction "1_1") (pintype "passive"))
      (node (ref "JP603") (pin "2") (pinfunction "2_2") (pintype "passive"))
      (node (ref "TP203") (pin "TP") (pinfunction "PP_TP") (pintype "input"))
    )
    (net (code "202") (name "Net-(19A-KL)") (class "Default")
      (node (ref "19") (pin "1") (pinfunction "KL_1") (pintype "passive"))
      (node (ref "TP208") (pin "TP") (pinfunction "PP_TP") (pintype "input"))
      (node (ref "X10") (pin "1") (pinfunction "1_1") (pintype "passive"))
    )
    (net (code "203") (name "Net-(19B-KL)") (class "Default")
      (node (ref "19") (pin "10") (pinfunction "KL_10") (pintype "passive"))
      (node (ref "D35") (pin "2") (pinfunction "-_2") (pintype "passive"))
      (node (ref "D36") (pin "2") (pinfunction "-_2") (pintype "passive"))
      (node (ref "JP20") (pin "1") (pinfunction "1_1") (pintype "passive"))
      (node (ref "SJ4") (pin "1") (pinfunction "1_1") (pintype "passive"))
      (node (ref "TP217") (pin "TP") (pinfunction "PP_TP") (pintype "input"))
    )
    (net (code "204") (name "Net-(19C-KL)") (class "Default")
      (node (ref "19") (pin "11") (pinfunction "KL_11") (pintype "passive"))
      (node (ref "D36") (pin "1") (pinfunction "+_1") (pintype "passive"))
      (node (ref "TP218") (pin "TP") (pinfunction "PP_TP") (pintype "input"))
      (node (ref "X10") (pin "19") (pinfunction "19_19") (pintype "passive"))
    )
    (net (code "205") (name "Net-(19E-KL)") (class "Default")
      (node (ref "19") (pin "2") (pinfunction "KL_2") (pintype "passive"))
      (node (ref "Q24") (pin "2") (pinfunction "C_2") (pintype "passive"))
      (node (ref "TP209") (pin "TP") (pinfunction "PP_TP") (pintype "input"))
    )
    (net (code "206") (name "Net-(19F-KL)") (class "Default")
      (node (ref "19") (pin "3") (pinfunction "KL_3") (pintype "passive"))
      (node (ref "IC34") (pin "11") (pinfunction "O6_11") (pintype "open_collector"))
      (node (ref "TP210") (pin "TP") (pinfunction "PP_TP") (pintype "input"))
    )
    (net (code "207") (name "Net-(19G-KL)") (class "Default")
      (node (ref "19") (pin "4") (pinfunction "KL_4") (pintype "passive"))
      (node (ref "IC34") (pin "10") (pinfunction "O7_10") (pintype "open_collector"))
      (node (ref "TP211") (pin "TP") (pinfunction "PP_TP") (pintype "input"))
    )
    (net (code "208") (name "Net-(19H-KL)") (class "Default")
      (node (ref "19") (pin "5") (pinfunction "KL_5") (pintype "passive"))
      (node (ref "IC34") (pin "12") (pinfunction "O5_12") (pintype "open_collector"))
      (node (ref "TP212") (pin "TP") (pinfunction "PP_TP") (pintype "input"))
    )
    (net (code "209") (name "Net-(19I-KL)") (class "Default")
      (node (ref "19") (pin "6") (pinfunction "KL_6") (pintype "passive"))
      (node (ref "IC34") (pin "13") (pinfunction "O4_13") (pintype "open_collector"))
      (node (ref "TP213") (pin "TP") (pinfunction "PP_TP") (pintype "input"))
    )
    (net (code "210") (name "Net-(19J-KL)") (class "Default")
      (node (ref "19") (pin "7") (pinfunction "KL_7") (pintype "passive"))
      (node (ref "IC34") (pin "14") (pinfunction "O3_14") (pintype "open_collector"))
      (node (ref "TP214") (pin "TP") (pinfunction "PP_TP") (pintype "input"))
    )
    (net (code "211") (name "Net-(19K-KL)") (class "Default")
      (node (ref "19") (pin "8") (pinfunction "KL_8") (pintype "passive"))
      (node (ref "Q28") (pin "3") (pinfunction "D_3") (pintype "passive"))
      (node (ref "TP215") (pin "TP") (pinfunction "PP_TP") (pintype "input"))
    )
    (net (code "212") (name "Net-(19L-KL)") (class "Default")
      (node (ref "19") (pin "9") (pinfunction "KL_9") (pintype "passive"))
      (node (ref "D35") (pin "1") (pinfunction "+_1") (pintype "passive"))
      (node (ref "TP216") (pin "TP") (pinfunction "PP_TP") (pintype "input"))
      (node (ref "X10") (pin "17") (pinfunction "17_17") (pintype "passive"))
    )
    (net (code "213") (name "Net-(20B-KL)") (class "Default")
      (node (ref "20") (pin "10") (pinfunction "KL_10") (pintype "passive"))
      (node (ref "TP227") (pin "TP") (pinfunction "PP_TP") (pintype "input"))
      (node (ref "X10") (pin "15") (pinfunction "15_15") (pintype "passive"))
    )
    (net (code "214") (name "Net-(20C-KL)") (class "Default")
      (node (ref "20") (pin "11") (pinfunction "KL_11") (pintype "passive"))
      (node (ref "IC34") (pin "16") (pinfunction "O1_16") (pintype "open_collector"))
      (node (ref "R262") (pin "1") (pinfunction "1_1") (pintype "passive"))
      (node (ref "R269") (pin "2") (pinfunction "2_2") (pintype "passive"))
      (node (ref "TP228") (pin "TP") (pinfunction "PP_TP") (pintype "input"))
    )
    (net (code "215") (name "Net-(20D-KL)") (class "Default")
      (node (ref "20") (pin "12") (pinfunction "KL_12") (pintype "passive"))
      (node (ref "R263") (pin "1") (pinfunction "1_1") (pintype "passive"))
      (node (ref "TP230") (pin "TP") (pinfunction "PP_TP") (pintype "input"))
    )
    (net (code "216") (name "Net-(20E-KL)") (class "Default")
      (node (ref "20") (pin "2") (pinfunction "KL_2") (pintype "passive"))
      (node (ref "D40") (pin "2") (pinfunction "-_2") (pintype "passive"))
      (node (ref "LED19") (pin "K") (pinfunction "C_K") (pintype "passive"))
      (node (ref "TP219") (pin "TP") (pinfunction "PP_TP") (pintype "input"))
      (node (ref "X10") (pin "12") (pinfunction "12_12") (pintype "passive"))
    )
    (net (code "217") (name "Net-(20F-KL)") (class "Default")
      (node (ref "20") (pin "3") (pinfunction "KL_3") (pintype "passive"))
      (node (ref "D39") (pin "2") (pinfunction "-_2") (pintype "passive"))
      (node (ref "LED20") (pin "K") (pinfunction "C_K") (pintype "passive"))
      (node (ref "TP220") (pin "TP") (pinfunction "PP_TP") (pintype "input"))
      (node (ref "X10") (pin "11") (pinfunction "11_11") (pintype "passive"))
    )
    (net (code "218") (name "Net-(20G-KL)") (class "Default")
      (node (ref "20") (pin "4") (pinfunction "KL_4") (pintype "passive"))
      (node (ref "D38") (pin "2") (pinfunction "-_2") (pintype "passive"))
      (node (ref "LED21") (pin "K") (pinfunction "C_K") (pintype "passive"))
      (node (ref "TP221") (pin "TP") (pinfunction "PP_TP") (pintype "input"))
      (node (ref "X10") (pin "10") (pinfunction "10_10") (pintype "passive"))
    )
    (net (code "219") (name "Net-(20H-KL)") (class "Default")
      (node (ref "20") (pin "5") (pinfunction "KL_5") (pintype "passive"))
      (node (ref "D37") (pin "2") (pinfunction "-_2") (pintype "passive"))
      (node (ref "LED22") (pin "K") (pinfunction "C_K") (pintype "passive"))
      (node (ref "TP222") (pin "TP") (pinfunction "PP_TP") (pintype "input"))
      (node (ref "X10") (pin "9") (pinfunction "9_9") (pintype "passive"))
    )
    (net (code "220") (name "Net-(20I-KL)") (class "Default")
      (node (ref "20") (pin "6") (pinfunction "KL_6") (pintype "passive"))
      (node (ref "JP17") (pin "2") (pinfunction "2_2") (pintype "passive"))
      (node (ref "TP223") (pin "TP") (pinfunction "PP_TP") (pintype "input"))
    )
    (net (code "221") (name "Net-(20J-KL)") (class "Default")
      (node (ref "20") (pin "7") (pinfunction "KL_7") (pintype "passive"))
      (node (ref "LED23") (pin "A") (pinfunction "A_A") (pintype "passive"))
      (node (ref "TP224") (pin "TP") (pinfunction "PP_TP") (pintype "input"))
      (node (ref "X10") (pin "8") (pinfunction "8_8") (pintype "passive"))
    )
    (net (code "222") (name "Net-(20K-KL)") (class "Default")
      (node (ref "20") (pin "8") (pinfunction "KL_8") (pintype "passive"))
      (node (ref "D41") (pin "2") (pinfunction "-_2") (pintype "passive"))
      (node (ref "LED24") (pin "K") (pinfunction "C_K") (pintype "passive"))
      (node (ref "TP225") (pin "TP") (pinfunction "PP_TP") (pintype "input"))
      (node (ref "X10") (pin "14") (pinfunction "14_14") (pintype "passive"))
    )
    (net (code "223") (name "Net-(20L-KL)") (class "Default")
      (node (ref "20") (pin "9") (pinfunction "KL_9") (pintype "passive"))
      (node (ref "D38") (pin "1") (pinfunction "+_1") (pintype "passive"))
      (node (ref "D39") (pin "1") (pinfunction "+_1") (pintype "passive"))
      (node (ref "JP18") (pin "1") (pinfunction "1_1") (pintype "passive"))
      (node (ref "JP19") (pin "2") (pinfunction "2_2") (pintype "passive"))
      (node (ref "TP226") (pin "TP") (pinfunction "PP_TP") (pintype "input"))
    )
    (net (code "224") (name "Net-(21A-KL)") (class "Default")
      (node (ref "21") (pin "1") (pinfunction "KL_1") (pintype "passive"))
      (node (ref "TP231") (pin "TP") (pinfunction "PP_TP") (pintype "input"))
      (node (ref "X13") (pin "1") (pinfunction "1_1") (pintype "passive"))
    )
    (net (code "225") (name "Net-(21B-KL)") (class "Default")
      (node (ref "21") (pin "10") (pinfunction "KL_10") (pintype "passive"))
      (node (ref "D46") (pin "2") (pinfunction "-_2") (pintype "passive"))
      (node (ref "D47") (pin "2") (pinfunction "-_2") (pintype "passive"))
      (node (ref "JP25") (pin "1") (pinfunction "1_1") (pintype "passive"))
      (node (ref "SJ5") (pin "1") (pinfunction "1_1") (pintype "passive"))
      (node (ref "TP240") (pin "TP") (pinfunction "PP_TP") (pintype "input"))
    )
    (net (code "226") (name "Net-(21C-KL)") (class "Default")
      (node (ref "21") (pin "11") (pinfunction "KL_11") (pintype "passive"))
      (node (ref "D47") (pin "1") (pinfunction "+_1") (pintype "passive"))
      (node (ref "TP241") (pin "TP") (pinfunction "PP_TP") (pintype "input"))
      (node (ref "X13") (pin "19") (pinfunction "19_19") (pintype "passive"))
    )
    (net (code "227") (name "Net-(21E-KL)") (class "Default")
      (node (ref "21") (pin "2") (pinfunction "KL_2") (pintype "passive"))
      (node (ref "Q31") (pin "2") (pinfunction "C_2") (pintype "passive"))
      (node (ref "TP232") (pin "TP") (pinfunction "PP_TP") (pintype "input"))
    )
    (net (code "228") (name "Net-(21F-KL)") (class "Default")
      (node (ref "21") (pin "3") (pinfunction "KL_3") (pintype "passive"))
      (node (ref "IC44") (pin "11") (pinfunction "O6_11") (pintype "open_collector"))
      (node (ref "TP233") (pin "TP") (pinfunction "PP_TP") (pintype "input"))
    )
    (net (code "229") (name "Net-(21G-KL)") (class "Default")
      (node (ref "21") (pin "4") (pinfunction "KL_4") (pintype "passive"))
      (node (ref "IC44") (pin "10") (pinfunction "O7_10") (pintype "open_collector"))
      (node (ref "TP234") (pin "TP") (pinfunction "PP_TP") (pintype "input"))
    )
    (net (code "230") (name "Net-(21H-KL)") (class "Default")
      (node (ref "21") (pin "5") (pinfunction "KL_5") (pintype "passive"))
      (node (ref "IC44") (pin "12") (pinfunction "O5_12") (pintype "open_collector"))
      (node (ref "TP235") (pin "TP") (pinfunction "PP_TP") (pintype "input"))
    )
    (net (code "231") (name "Net-(21I-KL)") (class "Default")
      (node (ref "21") (pin "6") (pinfunction "KL_6") (pintype "passive"))
      (node (ref "IC44") (pin "13") (pinfunction "O4_13") (pintype "open_collector"))
      (node (ref "TP236") (pin "TP") (pinfunction "PP_TP") (pintype "input"))
    )
    (net (code "232") (name "Net-(21J-KL)") (class "Default")
      (node (ref "21") (pin "7") (pinfunction "KL_7") (pintype "passive"))
      (node (ref "IC44") (pin "14") (pinfunction "O3_14") (pintype "open_collector"))
      (node (ref "TP237") (pin "TP") (pinfunction "PP_TP") (pintype "input"))
    )
    (net (code "233") (name "Net-(21K-KL)") (class "Default")
      (node (ref "21") (pin "8") (pinfunction "KL_8") (pintype "passive"))
      (node (ref "Q35") (pin "3") (pinfunction "D_3") (pintype "passive"))
      (node (ref "TP238") (pin "TP") (pinfunction "PP_TP") (pintype "input"))
    )
    (net (code "234") (name "Net-(21L-KL)") (class "Default")
      (node (ref "21") (pin "9") (pinfunction "KL_9") (pintype "passive"))
      (node (ref "D46") (pin "1") (pinfunction "+_1") (pintype "passive"))
      (node (ref "TP239") (pin "TP") (pinfunction "PP_TP") (pintype "input"))
      (node (ref "X13") (pin "17") (pinfunction "17_17") (pintype "passive"))
    )
    (net (code "235") (name "Net-(22B-KL)") (class "Default")
      (node (ref "22") (pin "10") (pinfunction "KL_10") (pintype "passive"))
      (node (ref "TP250") (pin "TP") (pinfunction "PP_TP") (pintype "input"))
      (node (ref "X13") (pin "15") (pinfunction "15_15") (pintype "passive"))
    )
    (net (code "236") (name "Net-(22C-KL)") (class "Default")
      (node (ref "22") (pin "11") (pinfunction "KL_11") (pintype "passive"))
      (node (ref "IC44") (pin "16") (pinfunction "O1_16") (pintype "open_collector"))
      (node (ref "R352") (pin "1") (pinfunction "1_1") (pintype "passive"))
      (node (ref "R359") (pin "2") (pinfunction "2_2") (pintype "passive"))
      (node (ref "TP251") (pin "TP") (pinfunction "PP_TP") (pintype "input"))
    )
    (net (code "237") (name "Net-(22D-KL)") (class "Default")
      (node (ref "22") (pin "12") (pinfunction "KL_12") (pintype "passive"))
      (node (ref "R353") (pin "1") (pinfunction "1_1") (pintype "passive"))
      (node (ref "TP253") (pin "TP") (pinfunction "PP_TP") (pintype "input"))
    )
    (net (code "238") (name "Net-(22E-KL)") (class "Default")
      (node (ref "22") (pin "2") (pinfunction "KL_2") (pintype "passive"))
      (node (ref "D51") (pin "2") (pinfunction "-_2") (pintype "passive"))
      (node (ref "LED25") (pin "K") (pinfunction "C_K") (pintype "passive"))
      (node (ref "TP242") (pin "TP") (pinfunction "PP_TP") (pintype "input"))
      (node (ref "X13") (pin "12") (pinfunction "12_12") (pintype "passive"))
    )
    (net (code "239") (name "Net-(22F-KL)") (class "Default")
      (node (ref "22") (pin "3") (pinfunction "KL_3") (pintype "passive"))
      (node (ref "D50") (pin "2") (pinfunction "-_2") (pintype "passive"))
      (node (ref "LED26") (pin "K") (pinfunction "C_K") (pintype "passive"))
      (node (ref "TP243") (pin "TP") (pinfunction "PP_TP") (pintype "input"))
      (node (ref "X13") (pin "11") (pinfunction "11_11") (pintype "passive"))
    )
    (net (code "240") (name "Net-(22G-KL)") (class "Default")
      (node (ref "22") (pin "4") (pinfunction "KL_4") (pintype "passive"))
      (node (ref "D49") (pin "2") (pinfunction "-_2") (pintype "passive"))
      (node (ref "LED27") (pin "K") (pinfunction "C_K") (pintype "passive"))
      (node (ref "TP244") (pin "TP") (pinfunction "PP_TP") (pintype "input"))
      (node (ref "X13") (pin "10") (pinfunction "10_10") (pintype "passive"))
    )
    (net (code "241") (name "Net-(22H-KL)") (class "Default")
      (node (ref "22") (pin "5") (pinfunction "KL_5") (pintype "passive"))
      (node (ref "D48") (pin "2") (pinfunction "-_2") (pintype "passive"))
      (node (ref "LED28") (pin "K") (pinfunction "C_K") (pintype "passive"))
      (node (ref "TP245") (pin "TP") (pinfunction "PP_TP") (pintype "input"))
      (node (ref "X13") (pin "9") (pinfunction "9_9") (pintype "passive"))
    )
    (net (code "242") (name "Net-(22I-KL)") (class "Default")
      (node (ref "22") (pin "6") (pinfunction "KL_6") (pintype "passive"))
      (node (ref "JP22") (pin "2") (pinfunction "2_2") (pintype "passive"))
      (node (ref "TP246") (pin "TP") (pinfunction "PP_TP") (pintype "input"))
    )
    (net (code "243") (name "Net-(22J-KL)") (class "Default")
      (node (ref "22") (pin "7") (pinfunction "KL_7") (pintype "passive"))
      (node (ref "LED29") (pin "A") (pinfunction "A_A") (pintype "passive"))
      (node (ref "TP247") (pin "TP") (pinfunction "PP_TP") (pintype "input"))
      (node (ref "X13") (pin "8") (pinfunction "8_8") (pintype "passive"))
    )
    (net (code "244") (name "Net-(22K-KL)") (class "Default")
      (node (ref "22") (pin "8") (pinfunction "KL_8") (pintype "passive"))
      (node (ref "D52") (pin "2") (pinfunction "-_2") (pintype "passive"))
      (node (ref "LED30") (pin "K") (pinfunction "C_K") (pintype "passive"))
      (node (ref "TP248") (pin "TP") (pinfunction "PP_TP") (pintype "input"))
      (node (ref "X13") (pin "14") (pinfunction "14_14") (pintype "passive"))
    )
    (net (code "245") (name "Net-(22L-KL)") (class "Default")
      (node (ref "22") (pin "9") (pinfunction "KL_9") (pintype "passive"))
      (node (ref "D49") (pin "1") (pinfunction "+_1") (pintype "passive"))
      (node (ref "D50") (pin "1") (pinfunction "+_1") (pintype "passive"))
      (node (ref "JP23") (pin "1") (pinfunction "1_1") (pintype "passive"))
      (node (ref "JP24") (pin "2") (pinfunction "2_2") (pintype "passive"))
      (node (ref "TP249") (pin "TP") (pinfunction "PP_TP") (pintype "input"))
    )
    (net (code "246") (name "Net-(23A-KL)") (class "Default")
      (node (ref "23") (pin "1") (pinfunction "KL_1") (pintype "passive"))
      (node (ref "TP254") (pin "TP") (pinfunction "PP_TP") (pintype "input"))
      (node (ref "X16") (pin "1") (pinfunction "1_1") (pintype "passive"))
    )
    (net (code "247") (name "Net-(23B-KL)") (class "Default")
      (node (ref "23") (pin "10") (pinfunction "KL_10") (pintype "passive"))
      (node (ref "D57") (pin "2") (pinfunction "-_2") (pintype "passive"))
      (node (ref "D58") (pin "2") (pinfunction "-_2") (pintype "passive"))
      (node (ref "JP30") (pin "1") (pinfunction "1_1") (pintype "passive"))
      (node (ref "SJ6") (pin "1") (pinfunction "1_1") (pintype "passive"))
      (node (ref "TP263") (pin "TP") (pinfunction "PP_TP") (pintype "input"))
    )
    (net (code "248") (name "Net-(23C-KL)") (class "Default")
      (node (ref "23") (pin "11") (pinfunction "KL_11") (pintype "passive"))
      (node (ref "D58") (pin "1") (pinfunction "+_1") (pintype "passive"))
      (node (ref "TP264") (pin "TP") (pinfunction "PP_TP") (pintype "input"))
      (node (ref "X16") (pin "19") (pinfunction "19_19") (pintype "passive"))
    )
    (net (code "249") (name "Net-(23E-KL)") (class "Default")
      (node (ref "23") (pin "2") (pinfunction "KL_2") (pintype "passive"))
      (node (ref "Q38") (pin "2") (pinfunction "C_2") (pintype "passive"))
      (node (ref "TP255") (pin "TP") (pinfunction "PP_TP") (pintype "input"))
    )
    (net (code "250") (name "Net-(23F-KL)") (class "Default")
      (node (ref "23") (pin "3") (pinfunction "KL_3") (pintype "passive"))
      (node (ref "IC54") (pin "11") (pinfunction "O6_11") (pintype "open_collector"))
      (node (ref "TP256") (pin "TP") (pinfunction "PP_TP") (pintype "input"))
    )
    (net (code "251") (name "Net-(23G-KL)") (class "Default")
      (node (ref "23") (pin "4") (pinfunction "KL_4") (pintype "passive"))
      (node (ref "IC54") (pin "10") (pinfunction "O7_10") (pintype "open_collector"))
      (node (ref "TP257") (pin "TP") (pinfunction "PP_TP") (pintype "input"))
    )
    (net (code "252") (name "Net-(23H-KL)") (class "Default")
      (node (ref "23") (pin "5") (pinfunction "KL_5") (pintype "passive"))
      (node (ref "IC54") (pin "12") (pinfunction "O5_12") (pintype "open_collector"))
      (node (ref "TP258") (pin "TP") (pinfunction "PP_TP") (pintype "input"))
    )
    (net (code "253") (name "Net-(23I-KL)") (class "Default")
      (node (ref "23") (pin "6") (pinfunction "KL_6") (pintype "passive"))
      (node (ref "IC54") (pin "13") (pinfunction "O4_13") (pintype "open_collector"))
      (node (ref "TP259") (pin "TP") (pinfunction "PP_TP") (pintype "input"))
    )
    (net (code "254") (name "Net-(23J-KL)") (class "Default")
      (node (ref "23") (pin "7") (pinfunction "KL_7") (pintype "passive"))
      (node (ref "IC54") (pin "14") (pinfunction "O3_14") (pintype "open_collector"))
      (node (ref "TP260") (pin "TP") (pinfunction "PP_TP") (pintype "input"))
    )
    (net (code "255") (name "Net-(23K-KL)") (class "Default")
      (node (ref "23") (pin "8") (pinfunction "KL_8") (pintype "passive"))
      (node (ref "Q42") (pin "3") (pinfunction "D_3") (pintype "passive"))
      (node (ref "TP261") (pin "TP") (pinfunction "PP_TP") (pintype "input"))
    )
    (net (code "256") (name "Net-(23L-KL)") (class "Default")
      (node (ref "23") (pin "9") (pinfunction "KL_9") (pintype "passive"))
      (node (ref "D57") (pin "1") (pinfunction "+_1") (pintype "passive"))
      (node (ref "TP262") (pin "TP") (pinfunction "PP_TP") (pintype "input"))
      (node (ref "X16") (pin "17") (pinfunction "17_17") (pintype "passive"))
    )
    (net (code "257") (name "Net-(24B-KL)") (class "Default")
      (node (ref "24") (pin "10") (pinfunction "KL_10") (pintype "passive"))
      (node (ref "TP273") (pin "TP") (pinfunction "PP_TP") (pintype "input"))
      (node (ref "X16") (pin "15") (pinfunction "15_15") (pintype "passive"))
    )
    (net (code "258") (name "Net-(24C-KL)") (class "Default")
      (node (ref "24") (pin "11") (pinfunction "KL_11") (pintype "passive"))
      (node (ref "IC54") (pin "16") (pinfunction "O1_16") (pintype "open_collector"))
      (node (ref "R397") (pin "1") (pinfunction "1_1") (pintype "passive"))
      (node (ref "R449") (pin "2") (pinfunction "2_2") (pintype "passive"))
      (node (ref "TP274") (pin "TP") (pinfunction "PP_TP") (pintype "input"))
    )
    (net (code "259") (name "Net-(24D-KL)") (class "Default")
      (node (ref "24") (pin "12") (pinfunction "KL_12") (pintype "passive"))
      (node (ref "R398") (pin "1") (pinfunction "1_1") (pintype "passive"))
      (node (ref "TP276") (pin "TP") (pinfunction "PP_TP") (pintype "input"))
    )
    (net (code "260") (name "Net-(24E-KL)") (class "Default")
      (node (ref "24") (pin "2") (pinfunction "KL_2") (pintype "passive"))
      (node (ref "D62") (pin "2") (pinfunction "-_2") (pintype "passive"))
      (node (ref "LED31") (pin "K") (pinfunction "C_K") (pintype "passive"))
      (node (ref "TP265") (pin "TP") (pinfunction "PP_TP") (pintype "input"))
      (node (ref "X16") (pin "12") (pinfunction "12_12") (pintype "passive"))
    )
    (net (code "261") (name "Net-(24F-KL)") (class "Default")
      (node (ref "24") (pin "3") (pinfunction "KL_3") (pintype "passive"))
      (node (ref "D61") (pin "2") (pinfunction "-_2") (pintype "passive"))
      (node (ref "LED32") (pin "K") (pinfunction "C_K") (pintype "passive"))
      (node (ref "TP266") (pin "TP") (pinfunction "PP_TP") (pintype "input"))
      (node (ref "X16") (pin "11") (pinfunction "11_11") (pintype "passive"))
    )
    (net (code "262") (name "Net-(24G-KL)") (class "Default")
      (node (ref "24") (pin "4") (pinfunction "KL_4") (pintype "passive"))
      (node (ref "D60") (pin "2") (pinfunction "-_2") (pintype "passive"))
      (node (ref "LED33") (pin "K") (pinfunction "C_K") (pintype "passive"))
      (node (ref "TP267") (pin "TP") (pinfunction "PP_TP") (pintype "input"))
      (node (ref "X16") (pin "10") (pinfunction "10_10") (pintype "passive"))
    )
    (net (code "263") (name "Net-(24H-KL)") (class "Default")
      (node (ref "24") (pin "5") (pinfunction "KL_5") (pintype "passive"))
      (node (ref "D59") (pin "2") (pinfunction "-_2") (pintype "passive"))
      (node (ref "LED34") (pin "K") (pinfunction "C_K") (pintype "passive"))
      (node (ref "TP268") (pin "TP") (pinfunction "PP_TP") (pintype "input"))
      (node (ref "X16") (pin "9") (pinfunction "9_9") (pintype "passive"))
    )
    (net (code "264") (name "Net-(24I-KL)") (class "Default")
      (node (ref "24") (pin "6") (pinfunction "KL_6") (pintype "passive"))
      (node (ref "JP27") (pin "2") (pinfunction "2_2") (pintype "passive"))
      (node (ref "TP269") (pin "TP") (pinfunction "PP_TP") (pintype "input"))
    )
    (net (code "265") (name "Net-(24J-KL)") (class "Default")
      (node (ref "24") (pin "7") (pinfunction "KL_7") (pintype "passive"))
      (node (ref "LED35") (pin "A") (pinfunction "A_A") (pintype "passive"))
      (node (ref "TP270") (pin "TP") (pinfunction "PP_TP") (pintype "input"))
      (node (ref "X16") (pin "8") (pinfunction "8_8") (pintype "passive"))
    )
    (net (code "266") (name "Net-(24K-KL)") (class "Default")
      (node (ref "24") (pin "8") (pinfunction "KL_8") (pintype "passive"))
      (node (ref "D63") (pin "2") (pinfunction "-_2") (pintype "passive"))
      (node (ref "LED36") (pin "K") (pinfunction "C_K") (pintype "passive"))
      (node (ref "TP271") (pin "TP") (pinfunction "PP_TP") (pintype "input"))
      (node (ref "X16") (pin "14") (pinfunction "14_14") (pintype "passive"))
    )
    (net (code "267") (name "Net-(24L-KL)") (class "Default")
      (node (ref "24") (pin "9") (pinfunction "KL_9") (pintype "passive"))
      (node (ref "D60") (pin "1") (pinfunction "+_1") (pintype "passive"))
      (node (ref "D61") (pin "1") (pinfunction "+_1") (pintype "passive"))
      (node (ref "JP28") (pin "1") (pinfunction "1_1") (pintype "passive"))
      (node (ref "JP29") (pin "2") (pinfunction "2_2") (pintype "passive"))
      (node (ref "TP272") (pin "TP") (pinfunction "PP_TP") (pintype "input"))
    )
    (net (code "268") (name "Net-(C1-Pad1)") (class "Default")
      (node (ref "C1") (pin "1") (pinfunction "1_1") (pintype "passive"))
      (node (ref "R11") (pin "1") (pinfunction "1_1") (pintype "passive"))
      (node (ref "R12") (pin "2") (pinfunction "2_2") (pintype "passive"))
    )
    (net (code "269") (name "Net-(C10-Pad1)") (class "Default")
      (node (ref "C10") (pin "1") (pinfunction "1_1") (pintype "passive"))
      (node (ref "R39") (pin "1") (pinfunction "1_1") (pintype "passive"))
      (node (ref "R40") (pin "1") (pinfunction "1_1") (pintype "passive"))
    )
    (net (code "270") (name "Net-(C11-Pad1)") (class "Default")
      (node (ref "C11") (pin "1") (pinfunction "1_1") (pintype "passive"))
      (node (ref "R56") (pin "1") (pinfunction "1_1") (pintype "passive"))
      (node (ref "R57") (pin "2") (pinfunction "2_2") (pintype "passive"))
    )
    (net (code "271") (name "Net-(C20-Pad1)") (class "Default")
      (node (ref "C20") (pin "1") (pinfunction "1_1") (pintype "passive"))
      (node (ref "R84") (pin "1") (pinfunction "1_1") (pintype "passive"))
      (node (ref "R85") (pin "1") (pinfunction "1_1") (pintype "passive"))
    )
    (net (code "272") (name "Net-(C21-Pad1)") (class "Default")
      (node (ref "C21") (pin "1") (pinfunction "1_1") (pintype "passive"))
      (node (ref "R104") (pin "1") (pinfunction "1_1") (pintype "passive"))
      (node (ref "R147") (pin "2") (pinfunction "2_2") (pintype "passive"))
    )
    (net (code "273") (name "Net-(C30-Pad1)") (class "Default")
      (node (ref "C30") (pin "1") (pinfunction "1_1") (pintype "passive"))
      (node (ref "R174") (pin "1") (pinfunction "1_1") (pintype "passive"))
      (node (ref "R175") (pin "1") (pinfunction "1_1") (pintype "passive"))
    )
    (net (code "274") (name "Net-(C31-Pad1)") (class "Default")
      (node (ref "C31") (pin "1") (pinfunction "1_1") (pintype "passive"))
      (node (ref "R191") (pin "1") (pinfunction "1_1") (pintype "passive"))
      (node (ref "R192") (pin "2") (pinfunction "2_2") (pintype "passive"))
    )
    (net (code "275") (name "Net-(C40-Pad1)") (class "Default")
      (node (ref "C40") (pin "1") (pinfunction "1_1") (pintype "passive"))
      (node (ref "R264") (pin "1") (pinfunction "1_1") (pintype "passive"))
      (node (ref "R265") (pin "1") (pinfunction "1_1") (pintype "passive"))
    )
    (net (code "276") (name "Net-(C41-Pad1)") (class "Default")
      (node (ref "C41") (pin "1") (pinfunction "1_1") (pintype "passive"))
      (node (ref "R281") (pin "1") (pinfunction "1_1") (pintype "passive"))
      (node (ref "R282") (pin "2") (pinfunction "2_2") (pintype "passive"))
    )
    (net (code "277") (name "Net-(C50-Pad1)") (class "Default")
      (node (ref "C50") (pin "1") (pinfunction "1_1") (pintype "passive"))
      (node (ref "R354") (pin "1") (pinfunction "1_1") (pintype "passive"))
      (node (ref "R355") (pin "1") (pinfunction "1_1") (pintype "passive"))
    )
    (net (code "278") (name "Net-(C51-Pad1)") (class "Default")
      (node (ref "C51") (pin "1") (pinfunction "1_1") (pintype "passive"))
      (node (ref "R371") (pin "1") (pinfunction "1_1") (pintype "passive"))
      (node (ref "R372") (pin "2") (pinfunction "2_2") (pintype "passive"))
    )
    (net (code "279") (name "Net-(C60-Pad1)") (class "Default")
      (node (ref "C60") (pin "1") (pinfunction "1_1") (pintype "passive"))
      (node (ref "R399") (pin "1") (pinfunction "1_1") (pintype "passive"))
      (node (ref "R400") (pin "1") (pinfunction "1_1") (pintype "passive"))
    )
    (net (code "280") (name "Net-(C103-Pad1)") (class "Default")
      (node (ref "C103") (pin "1") (pinfunction "1_1") (pintype "passive"))
      (node (ref "R108") (pin "1") (pinfunction "1_1") (pintype "passive"))
      (node (ref "R112") (pin "1") (pinfunction "1_1") (pintype "passive"))
    )
    (net (code "281") (name "Net-(C107-Pad1)") (class "Default")
      (node (ref "C107") (pin "1") (pinfunction "1_1") (pintype "passive"))
      (node (ref "R125") (pin "1") (pinfunction "1_1") (pintype "passive"))
      (node (ref "R130") (pin "2") (pinfunction "2_2") (pintype "passive"))
    )
    (net (code "282") (name "Net-(C203-Pad1)") (class "Default")
      (node (ref "C203") (pin "1") (pinfunction "1_1") (pintype "passive"))
      (node (ref "R208") (pin "1") (pinfunction "1_1") (pintype "passive"))
      (node (ref "R212") (pin "1") (pinfunction "1_1") (pintype "passive"))
    )
    (net (code "283") (name "Net-(C207-Pad1)") (class "Default")
      (node (ref "C207") (pin "1") (pinfunction "1_1") (pintype "passive"))
      (node (ref "R225") (pin "1") (pinfunction "1_1") (pintype "passive"))
      (node (ref "R230") (pin "2") (pinfunction "2_2") (pintype "passive"))
    )
    (net (code "284") (name "Net-(C303-Pad1)") (class "Default")
      (node (ref "C303") (pin "1") (pinfunction "1_1") (pintype "passive"))
      (node (ref "R308") (pin "1") (pinfunction "1_1") (pintype "passive"))
      (node (ref "R312") (pin "1") (pinfunction "1_1") (pintype "passive"))
    )
    (net (code "285") (name "Net-(C307-Pad1)") (class "Default")
      (node (ref "C307") (pin "1") (pinfunction "1_1") (pintype "passive"))
      (node (ref "R325") (pin "1") (pinfunction "1_1") (pintype "passive"))
      (node (ref "R330") (pin "2") (pinfunction "2_2") (pintype "passive"))
    )
    (net (code "286") (name "Net-(C403-Pad1)") (class "Default")
      (node (ref "C403") (pin "1") (pinfunction "1_1") (pintype "passive"))
      (node (ref "R408") (pin "1") (pinfunction "1_1") (pintype "passive"))
      (node (ref "R412") (pin "1") (pinfunction "1_1") (pintype "passive"))
    )
    (net (code "287") (name "Net-(C407-Pad1)") (class "Default")
      (node (ref "C407") (pin "1") (pinfunction "1_1") (pintype "passive"))
      (node (ref "R425") (pin "1") (pinfunction "1_1") (pintype "passive"))
      (node (ref "R430") (pin "2") (pinfunction "2_2") (pintype "passive"))
    )
    (net (code "288") (name "Net-(C503-Pad1)") (class "Default")
      (node (ref "C503") (pin "1") (pinfunction "1_1") (pintype "passive"))
      (node (ref "R508") (pin "1") (pinfunction "1_1") (pintype "passive"))
      (node (ref "R512") (pin "1") (pinfunction "1_1") (pintype "passive"))
    )
    (net (code "289") (name "Net-(C507-Pad1)") (class "Default")
      (node (ref "C507") (pin "1") (pinfunction "1_1") (pintype "passive"))
      (node (ref "R525") (pin "1") (pinfunction "1_1") (pintype "passive"))
      (node (ref "R530") (pin "2") (pinfunction "2_2") (pintype "passive"))
    )
    (net (code "290") (name "Net-(C603-Pad1)") (class "Default")
      (node (ref "C603") (pin "1") (pinfunction "1_1") (pintype "passive"))
      (node (ref "R608") (pin "1") (pinfunction "1_1") (pintype "passive"))
      (node (ref "R612") (pin "1") (pinfunction "1_1") (pintype "passive"))
    )
    (net (code "291") (name "Net-(C607-Pad1)") (class "Default")
      (node (ref "C607") (pin "1") (pinfunction "1_1") (pintype "passive"))
      (node (ref "R625") (pin "1") (pinfunction "1_1") (pintype "passive"))
      (node (ref "R630") (pin "2") (pinfunction "2_2") (pintype "passive"))
    )
    (net (code "292") (name "Net-(D1-+)") (class "Default")
      (node (ref "D1") (pin "1") (pinfunction "+_1") (pintype "passive"))
      (node (ref "R15") (pin "1") (pinfunction "1_1") (pintype "passive"))
    )
    (net (code "293") (name "Net-(D1--)") (class "Default")
      (node (ref "D1") (pin "2") (pinfunction "-_2") (pintype "passive"))
      (node (ref "IC5") (pin "2") (pinfunction "OUT_2") (pintype "open_collector"))
      (node (ref "JP2") (pin "1") (pinfunction "1_1") (pintype "passive"))
      (node (ref "Q6") (pin "1") (pinfunction "G_1") (pintype "passive"))
      (node (ref "R30") (pin "2") (pinfunction "2_2") (pintype "passive"))
    )
    (net (code "294") (name "Net-(D4-+)") (class "Default")
      (node (ref "D4") (pin "1") (pinfunction "+_1") (pintype "passive"))
      (node (ref "R1") (pin "1") (pinfunction "1_1") (pintype "passive"))
    )
    (net (code "295") (name "Net-(D7-+)") (class "Default")
      (node (ref "D7") (pin "1") (pinfunction "+_1") (pintype "passive"))
      (node (ref "JP3") (pin "2") (pinfunction "2_2") (pintype "passive"))
    )
    (net (code "296") (name "Net-(D8-+)") (class "Default")
      (node (ref "D8") (pin "1") (pinfunction "+_1") (pintype "passive"))
      (node (ref "JP4") (pin "1") (pinfunction "1_1") (pintype "passive"))
    )
    (net (code "297") (name "Net-(D9--)") (class "Default")
      (node (ref "D9") (pin "2") (pinfunction "-_2") (pintype "passive"))
      (node (ref "Q1") (pin "2") (pinfunction "C_2") (pintype "passive"))
      (node (ref "START1") (pin "TP") (pinfunction "PP_TP") (pintype "input"))
      (node (ref "X1") (pin "5") (pinfunction "5_5") (pintype "passive"))
    )
    (net (code "298") (name "Net-(D10-+)") (class "Default")
      (node (ref "D10") (pin "1") (pinfunction "+_1") (pintype "passive"))
      (node (ref "R33") (pin "1") (pinfunction "1_1") (pintype "passive"))
    )
    (net (code "299") (name "Net-(D10--)") (class "Default")
      (node (ref "C7") (pin "2") (pinfunction "2_2") (pintype "passive"))
      (node (ref "D10") (pin "2") (pinfunction "-_2") (pintype "passive"))
      (node (ref "IC7") (pin "2") (pinfunction "TR_2") (pintype "input"))
      (node (ref "IC7") (pin "6") (pinfunction "THR_6") (pintype "input"))
      (node (ref "R31") (pin "1") (pinfunction "1_1") (pintype "passive"))
    )
    (net (code "300") (name "Net-(D12-+)") (class "Default")
      (node (ref "D12") (pin "1") (pinfunction "+_1") (pintype "passive"))
      (node (ref "R60") (pin "1") (pinfunction "1_1") (pintype "passive"))
    )
    (net (code "301") (name "Net-(D12--)") (class "Default")
      (node (ref "D12") (pin "2") (pinfunction "-_2") (pintype "passive"))
      (node (ref "IC15") (pin "2") (pinfunction "OUT_2") (pintype "open_collector"))
      (node (ref "JP7") (pin "1") (pinfunction "1_1") (pintype "passive"))
      (node (ref "Q13") (pin "1") (pinfunction "G_1") (pintype "passive"))
      (node (ref "R75") (pin "2") (pinfunction "2_2") (pintype "passive"))
    )
    (net (code "302") (name "Net-(D15-+)") (class "Default")
      (node (ref "D15") (pin "1") (pinfunction "+_1") (pintype "passive"))
      (node (ref "R46") (pin "1") (pinfunction "1_1") (pintype "passive"))
    )
    (net (code "303") (name "Net-(D18-+)") (class "Default")
      (node (ref "D18") (pin "1") (pinfunction "+_1") (pintype "passive"))
      (node (ref "JP8") (pin "2") (pinfunction "2_2") (pintype "passive"))
    )
    (net (code "304") (name "Net-(D19-+)") (class "Default")
      (node (ref "D19") (pin "1") (pinfunction "+_1") (pintype "passive"))
      (node (ref "JP9") (pin "1") (pinfunction "1_1") (pintype "passive"))
    )
    (net (code "305") (name "Net-(D20--)") (class "Default")
      (node (ref "D20") (pin "2") (pinfunction "-_2") (pintype "passive"))
      (node (ref "Q8") (pin "2") (pinfunction "C_2") (pintype "passive"))
      (node (ref "START2") (pin "TP") (pinfunction "PP_TP") (pintype "input"))
      (node (ref "X4") (pin "5") (pinfunction "5_5") (pintype "passive"))
    )
    (net (code "306") (name "Net-(D21-+)") (class "Default")
      (node (ref "D21") (pin "1") (pinfunction "+_1") (pintype "passive"))
      (node (ref "R78") (pin "1") (pinfunction "1_1") (pintype "passive"))
    )
    (net (code "307") (name "Net-(D21--)") (class "Default")
      (node (ref "C17") (pin "2") (pinfunction "2_2") (pintype "passive"))
      (node (ref "D21") (pin "2") (pinfunction "-_2") (pintype "passive"))
      (node (ref "IC17") (pin "2") (pinfunction "TR_2") (pintype "input"))
      (node (ref "IC17") (pin "6") (pinfunction "THR_6") (pintype "input"))
      (node (ref "R76") (pin "1") (pinfunction "1_1") (pintype "passive"))
    )
    (net (code "308") (name "Net-(D23-+)") (class "Default")
      (node (ref "D23") (pin "1") (pinfunction "+_1") (pintype "passive"))
      (node (ref "R150") (pin "1") (pinfunction "1_1") (pintype "passive"))
    )
    (net (code "309") (name "Net-(D23--)") (class "Default")
      (node (ref "D23") (pin "2") (pinfunction "-_2") (pintype "passive"))
      (node (ref "IC25") (pin "2") (pinfunction "OUT_2") (pintype "open_collector"))
      (node (ref "JP12") (pin "1") (pinfunction "1_1") (pintype "passive"))
      (node (ref "Q20") (pin "1") (pinfunction "G_1") (pintype "passive"))
      (node (ref "R165") (pin "2") (pinfunction "2_2") (pintype "passive"))
    )
    (net (code "310") (name "Net-(D26-+)") (class "Default")
      (node (ref "D26") (pin "1") (pinfunction "+_1") (pintype "passive"))
      (node (ref "R91") (pin "1") (pinfunction "1_1") (pintype "passive"))
    )
    (net (code "311") (name "Net-(D29-+)") (class "Default")
      (node (ref "D29") (pin "1") (pinfunction "+_1") (pintype "passive"))
      (node (ref "JP13") (pin "2") (pinfunction "2_2") (pintype "passive"))
    )
    (net (code "312") (name "Net-(D30-+)") (class "Default")
      (node (ref "D30") (pin "1") (pinfunction "+_1") (pintype "passive"))
      (node (ref "JP14") (pin "1") (pinfunction "1_1") (pintype "passive"))
    )
    (net (code "313") (name "Net-(D31--)") (class "Default")
      (node (ref "D31") (pin "2") (pinfunction "-_2") (pintype "passive"))
      (node (ref "Q15") (pin "2") (pinfunction "C_2") (pintype "passive"))
      (node (ref "START3") (pin "TP") (pinfunction "PP_TP") (pintype "input"))
      (node (ref "X7") (pin "5") (pinfunction "5_5") (pintype "passive"))
    )
    (net (code "314") (name "Net-(D32-+)") (class "Default")
      (node (ref "D32") (pin "1") (pinfunction "+_1") (pintype "passive"))
      (node (ref "R168") (pin "1") (pinfunction "1_1") (pintype "passive"))
    )
    (net (code "315") (name "Net-(D32--)") (class "Default")
      (node (ref "C27") (pin "2") (pinfunction "2_2") (pintype "passive"))
      (node (ref "D32") (pin "2") (pinfunction "-_2") (pintype "passive"))
      (node (ref "IC27") (pin "2") (pinfunction "TR_2") (pintype "input"))
      (node (ref "IC27") (pin "6") (pinfunction "THR_6") (pintype "input"))
      (node (ref "R166") (pin "1") (pinfunction "1_1") (pintype "passive"))
    )
    (net (code "316") (name "Net-(D34-+)") (class "Default")
      (node (ref "D34") (pin "1") (pinfunction "+_1") (pintype "passive"))
      (node (ref "R195") (pin "1") (pinfunction "1_1") (pintype "passive"))
    )
    (net (code "317") (name "Net-(D34--)") (class "Default")
      (node (ref "D34") (pin "2") (pinfunction "-_2") (pintype "passive"))
      (node (ref "IC35") (pin "2") (pinfunction "OUT_2") (pintype "open_collector"))
      (node (ref "JP17") (pin "1") (pinfunction "1_1") (pintype "passive"))
      (node (ref "Q27") (pin "1") (pinfunction "G_1") (pintype "passive"))
      (node (ref "R255") (pin "2") (pinfunction "2_2") (pintype "passive"))
    )
    (net (code "318") (name "Net-(D37-+)") (class "Default")
      (node (ref "D37") (pin "1") (pinfunction "+_1") (pintype "passive"))
      (node (ref "R181") (pin "1") (pinfunction "1_1") (pintype "passive"))
    )
    (net (code "319") (name "Net-(D40-+)") (class "Default")
      (node (ref "D40") (pin "1") (pinfunction "+_1") (pintype "passive"))
      (node (ref "JP18") (pin "2") (pinfunction "2_2") (pintype "passive"))
    )
    (net (code "320") (name "Net-(D41-+)") (class "Default")
      (node (ref "D41") (pin "1") (pinfunction "+_1") (pintype "passive"))
      (node (ref "JP19") (pin "1") (pinfunction "1_1") (pintype "passive"))
    )
    (net (code "321") (name "Net-(D42--)") (class "Default")
      (node (ref "D42") (pin "2") (pinfunction "-_2") (pintype "passive"))
      (node (ref "Q22") (pin "2") (pinfunction "C_2") (pintype "passive"))
      (node (ref "START4") (pin "TP") (pinfunction "PP_TP") (pintype "input"))
      (node (ref "X10") (pin "5") (pinfunction "5_5") (pintype "passive"))
    )
    (net (code "322") (name "Net-(D43-+)") (class "Default")
      (node (ref "D43") (pin "1") (pinfunction "+_1") (pintype "passive"))
      (node (ref "R258") (pin "1") (pinfunction "1_1") (pintype "passive"))
    )
    (net (code "323") (name "Net-(D43--)") (class "Default")
      (node (ref "C37") (pin "2") (pinfunction "2_2") (pintype "passive"))
      (node (ref "D43") (pin "2") (pinfunction "-_2") (pintype "passive"))
      (node (ref "IC37") (pin "2") (pinfunction "TR_2") (pintype "input"))
      (node (ref "IC37") (pin "6") (pinfunction "THR_6") (pintype "input"))
      (node (ref "R256") (pin "1") (pinfunction "1_1") (pintype "passive"))
    )
    (net (code "324") (name "Net-(D45-+)") (class "Default")
      (node (ref "D45") (pin "1") (pinfunction "+_1") (pintype "passive"))
      (node (ref "R285") (pin "1") (pinfunction "1_1") (pintype "passive"))
    )
    (net (code "325") (name "Net-(D45--)") (class "Default")
      (node (ref "D45") (pin "2") (pinfunction "-_2") (pintype "passive"))
      (node (ref "IC45") (pin "2") (pinfunction "OUT_2") (pintype "open_collector"))
      (node (ref "JP22") (pin "1") (pinfunction "1_1") (pintype "passive"))
      (node (ref "Q34") (pin "1") (pinfunction "G_1") (pintype "passive"))
      (node (ref "R300") (pin "2") (pinfunction "2_2") (pintype "passive"))
    )
    (net (code "326") (name "Net-(D48-+)") (class "Default")
      (node (ref "D48") (pin "1") (pinfunction "+_1") (pintype "passive"))
      (node (ref "R271") (pin "1") (pinfunction "1_1") (pintype "passive"))
    )
    (net (code "327") (name "Net-(D51-+)") (class "Default")
      (node (ref "D51") (pin "1") (pinfunction "+_1") (pintype "passive"))
      (node (ref "JP23") (pin "2") (pinfunction "2_2") (pintype "passive"))
    )
    (net (code "328") (name "Net-(D52-+)") (class "Default")
      (node (ref "D52") (pin "1") (pinfunction "+_1") (pintype "passive"))
      (node (ref "JP24") (pin "1") (pinfunction "1_1") (pintype "passive"))
    )
    (net (code "329") (name "Net-(D53--)") (class "Default")
      (node (ref "D53") (pin "2") (pinfunction "-_2") (pintype "passive"))
      (node (ref "Q29") (pin "2") (pinfunction "C_2") (pintype "passive"))
      (node (ref "START5") (pin "TP") (pinfunction "PP_TP") (pintype "input"))
      (node (ref "X13") (pin "5") (pinfunction "5_5") (pintype "passive"))
    )
    (net (code "330") (name "Net-(D54-+)") (class "Default")
      (node (ref "D54") (pin "1") (pinfunction "+_1") (pintype "passive"))
      (node (ref "R348") (pin "1") (pinfunction "1_1") (pintype "passive"))
    )
    (net (code "331") (name "Net-(D54--)") (class "Default")
      (node (ref "C47") (pin "2") (pinfunction "2_2") (pintype "passive"))
      (node (ref "D54") (pin "2") (pinfunction "-_2") (pintype "passive"))
      (node (ref "IC47") (pin "2") (pinfunction "TR_2") (pintype "input"))
      (node (ref "IC47") (pin "6") (pinfunction "THR_6") (pintype "input"))
      (node (ref "R304") (pin "1") (pinfunction "1_1") (pintype "passive"))
    )
    (net (code "332") (name "Net-(D56-+)") (class "Default")
      (node (ref "D56") (pin "1") (pinfunction "+_1") (pintype "passive"))
      (node (ref "R375") (pin "1") (pinfunction "1_1") (pintype "passive"))
    )
    (net (code "333") (name "Net-(D56--)") (class "Default")
      (node (ref "D56") (pin "2") (pinfunction "-_2") (pintype "passive"))
      (node (ref "IC55") (pin "2") (pinfunction "OUT_2") (pintype "open_collector"))
      (node (ref "JP27") (pin "1") (pinfunction "1_1") (pintype "passive"))
      (node (ref "Q41") (pin "1") (pinfunction "G_1") (pintype "passive"))
      (node (ref "R390") (pin "2") (pinfunction "2_2") (pintype "passive"))
    )
    (net (code "334") (name "Net-(D59-+)") (class "Default")
      (node (ref "D59") (pin "1") (pinfunction "+_1") (pintype "passive"))
      (node (ref "R361") (pin "1") (pinfunction "1_1") (pintype "passive"))
    )
    (net (code "335") (name "Net-(D62-+)") (class "Default")
      (node (ref "D62") (pin "1") (pinfunction "+_1") (pintype "passive"))
      (node (ref "JP28") (pin "2") (pinfunction "2_2") (pintype "passive"))
    )
    (net (code "336") (name "Net-(D63-+)") (class "Default")
      (node (ref "D63") (pin "1") (pinfunction "+_1") (pintype "passive"))
      (node (ref "JP29") (pin "1") (pinfunction "1_1") (pintype "passive"))
    )
    (net (code "337") (name "Net-(D64--)") (class "Default")
      (node (ref "D64") (pin "2") (pinfunction "-_2") (pintype "passive"))
      (node (ref "Q36") (pin "2") (pinfunction "C_2") (pintype "passive"))
      (node (ref "START6") (pin "TP") (pinfunction "PP_TP") (pintype "input"))
      (node (ref "X16") (pin "5") (pinfunction "5_5") (pintype "passive"))
    )
    (net (code "338") (name "Net-(D65-+)") (class "Default")
      (node (ref "D65") (pin "1") (pinfunction "+_1") (pintype "passive"))
      (node (ref "R393") (pin "1") (pinfunction "1_1") (pintype "passive"))
    )
    (net (code "339") (name "Net-(D65--)") (class "Default")
      (node (ref "C57") (pin "2") (pinfunction "2_2") (pintype "passive"))
      (node (ref "D65") (pin "2") (pinfunction "-_2") (pintype "passive"))
      (node (ref "IC57") (pin "2") (pinfunction "TR_2") (pintype "input"))
      (node (ref "IC57") (pin "6") (pinfunction "THR_6") (pintype "input"))
      (node (ref "R391") (pin "1") (pinfunction "1_1") (pintype "passive"))
    )
    (net (code "340") (name "Net-(D105--)") (class "Default")
      (node (ref "D105") (pin "2") (pinfunction "-_2") (pintype "passive"))
      (node (ref "Q104") (pin "2") (pinfunction "C_2") (pintype "passive"))
      (node (ref "START") (pin "TP") (pinfunction "PP_TP") (pintype "input"))
      (node (ref "X101") (pin "5") (pinfunction "5_5") (pintype "passive"))
    )
    (net (code "341") (name "Net-(D106-+)") (class "Default")
      (node (ref "D106") (pin "1") (pinfunction "+_1") (pintype "passive"))
      (node (ref "R127") (pin "1") (pinfunction "1_1") (pintype "passive"))
    )
    (net (code "342") (name "Net-(D109-+)") (class "Default")
      (node (ref "D109") (pin "1") (pinfunction "+_1") (pintype "passive"))
      (node (ref "JP102") (pin "2") (pinfunction "2_2") (pintype "passive"))
    )
    (net (code "343") (name "Net-(D110-+)") (class "Default")
      (node (ref "D110") (pin "1") (pinfunction "+_1") (pintype "passive"))
      (node (ref "JP103") (pin "1") (pinfunction "1_1") (pintype "passive"))
    )
    (net (code "344") (name "Net-(D111-+)") (class "Default")
      (node (ref "D111") (pin "1") (pinfunction "+_1") (pintype "passive"))
      (node (ref "R133") (pin "1") (pinfunction "1_1") (pintype "passive"))
    )
    (net (code "345") (name "Net-(D111--)") (class "Default")
      (node (ref "D111") (pin "2") (pinfunction "-_2") (pintype "passive"))
      (node (ref "IC108") (pin "2") (pinfunction "OUT_2") (pintype "open_collector"))
      (node (ref "JP105") (pin "1") (pinfunction "1_1") (pintype "passive"))
      (node (ref "Q107") (pin "1") (pinfunction "G_1") (pintype "passive"))
      (node (ref "R135") (pin "2") (pinfunction "2_2") (pintype "passive"))
    )
    (net (code "346") (name "Net-(D112-+)") (class "Default")
      (node (ref "D112") (pin "1") (pinfunction "+_1") (pintype "passive"))
      (node (ref "R140") (pin "1") (pinfunction "1_1") (pintype "passive"))
    )
    (net (code "347") (name "Net-(D112--)") (class "Default")
      (node (ref "C109") (pin "2") (pinfunction "2_2") (pintype "passive"))
      (node (ref "D112") (pin "2") (pinfunction "-_2") (pintype "passive"))
      (node (ref "IC110") (pin "2") (pinfunction "TR_2") (pintype "input"))
      (node (ref "IC110") (pin "6") (pinfunction "THR_6") (pintype "input"))
      (node (ref "R141") (pin "1") (pinfunction "1_1") (pintype "passive"))
    )
    (net (code "348") (name "Net-(D205--)") (class "Default")
      (node (ref "D205") (pin "2") (pinfunction "-_2") (pintype "passive"))
      (node (ref "Q204") (pin "2") (pinfunction "C_2") (pintype "passive"))
      (node (ref "START201") (pin "TP") (pinfunction "PP_TP") (pintype "input"))
      (node (ref "X201") (pin "5") (pinfunction "5_5") (pintype "passive"))
    )
    (net (code "349") (name "Net-(D206-+)") (class "Default")
      (node (ref "D206") (pin "1") (pinfunction "+_1") (pintype "passive"))
      (node (ref "R227") (pin "1") (pinfunction "1_1") (pintype "passive"))
    )
    (net (code "350") (name "Net-(D209-+)") (class "Default")
      (node (ref "D209") (pin "1") (pinfunction "+_1") (pintype "passive"))
      (node (ref "JP202") (pin "2") (pinfunction "2_2") (pintype "passive"))
    )
    (net (code "351") (name "Net-(D210-+)") (class "Default")
      (node (ref "D210") (pin "1") (pinfunction "+_1") (pintype "passive"))
      (node (ref "JP203") (pin "1") (pinfunction "1_1") (pintype "passive"))
    )
    (net (code "352") (name "Net-(D211-+)") (class "Default")
      (node (ref "D211") (pin "1") (pinfunction "+_1") (pintype "passive"))
      (node (ref "R233") (pin "1") (pinfunction "1_1") (pintype "passive"))
    )
    (net (code "353") (name "Net-(D211--)") (class "Default")
      (node (ref "D211") (pin "2") (pinfunction "-_2") (pintype "passive"))
      (node (ref "IC208") (pin "2") (pinfunction "OUT_2") (pintype "open_collector"))
      (node (ref "JP205") (pin "1") (pinfunction "1_1") (pintype "passive"))
      (node (ref "Q207") (pin "1") (pinfunction "G_1") (pintype "passive"))
      (node (ref "R235") (pin "2") (pinfunction "2_2") (pintype "passive"))
    )
    (net (code "354") (name "Net-(D212-+)") (class "Default")
      (node (ref "D212") (pin "1") (pinfunction "+_1") (pintype "passive"))
      (node (ref "R240") (pin "1") (pinfunction "1_1") (pintype "passive"))
    )
    (net (code "355") (name "Net-(D212--)") (class "Default")
      (node (ref "C209") (pin "2") (pinfunction "2_2") (pintype "passive"))
      (node (ref "D212") (pin "2") (pinfunction "-_2") (pintype "passive"))
      (node (ref "IC210") (pin "2") (pinfunction "TR_2") (pintype "input"))
      (node (ref "IC210") (pin "6") (pinfunction "THR_6") (pintype "input"))
      (node (ref "R241") (pin "1") (pinfunction "1_1") (pintype "passive"))
    )
    (net (code "356") (name "Net-(D305--)") (class "Default")
      (node (ref "D305") (pin "2") (pinfunction "-_2") (pintype "passive"))
      (node (ref "Q304") (pin "2") (pinfunction "C_2") (pintype "passive"))
      (node (ref "START301") (pin "TP") (pinfunction "PP_TP") (pintype "input"))
      (node (ref "X301") (pin "5") (pinfunction "5_5") (pintype "passive"))
    )
    (net (code "357") (name "Net-(D306-+)") (class "Default")
      (node (ref "D306") (pin "1") (pinfunction "+_1") (pintype "passive"))
      (node (ref "R327") (pin "1") (pinfunction "1_1") (pintype "passive"))
    )
    (net (code "358") (name "Net-(D309-+)") (class "Default")
      (node (ref "D309") (pin "1") (pinfunction "+_1") (pintype "passive"))
      (node (ref "JP302") (pin "2") (pinfunction "2_2") (pintype "passive"))
    )
    (net (code "359") (name "Net-(D310-+)") (class "Default")
      (node (ref "D310") (pin "1") (pinfunction "+_1") (pintype "passive"))
      (node (ref "JP303") (pin "1") (pinfunction "1_1") (pintype "passive"))
    )
    (net (code "360") (name "Net-(D311-+)") (class "Default")
      (node (ref "D311") (pin "1") (pinfunction "+_1") (pintype "passive"))
      (node (ref "R333") (pin "1") (pinfunction "1_1") (pintype "passive"))
    )
    (net (code "361") (name "Net-(D311--)") (class "Default")
      (node (ref "D311") (pin "2") (pinfunction "-_2") (pintype "passive"))
      (node (ref "IC308") (pin "2") (pinfunction "OUT_2") (pintype "open_collector"))
      (node (ref "JP305") (pin "1") (pinfunction "1_1") (pintype "passive"))
      (node (ref "Q307") (pin "1") (pinfunction "G_1") (pintype "passive"))
      (node (ref "R335") (pin "2") (pinfunction "2_2") (pintype "passive"))
    )
    (net (code "362") (name "Net-(D312-+)") (class "Default")
      (node (ref "D312") (pin "1") (pinfunction "+_1") (pintype "passive"))
      (node (ref "R340") (pin "1") (pinfunction "1_1") (pintype "passive"))
    )
    (net (code "363") (name "Net-(D312--)") (class "Default")
      (node (ref "C309") (pin "2") (pinfunction "2_2") (pintype "passive"))
      (node (ref "D312") (pin "2") (pinfunction "-_2") (pintype "passive"))
      (node (ref "IC310") (pin "2") (pinfunction "TR_2") (pintype "input"))
      (node (ref "IC310") (pin "6") (pinfunction "THR_6") (pintype "input"))
      (node (ref "R341") (pin "1") (pinfunction "1_1") (pintype "passive"))
    )
    (net (code "364") (name "Net-(D405--)") (class "Default")
      (node (ref "D405") (pin "2") (pinfunction "-_2") (pintype "passive"))
      (node (ref "Q404") (pin "2") (pinfunction "C_2") (pintype "passive"))
      (node (ref "START401") (pin "TP") (pinfunction "PP_TP") (pintype "input"))
      (node (ref "X401") (pin "5") (pinfunction "5_5") (pintype "passive"))
    )
    (net (code "365") (name "Net-(D406-+)") (class "Default")
      (node (ref "D406") (pin "1") (pinfunction "+_1") (pintype "passive"))
      (node (ref "R427") (pin "1") (pinfunction "1_1") (pintype "passive"))
    )
    (net (code "366") (name "Net-(D409-+)") (class "Default")
      (node (ref "D409") (pin "1") (pinfunction "+_1") (pintype "passive"))
      (node (ref "JP402") (pin "2") (pinfunction "2_2") (pintype "passive"))
    )
    (net (code "367") (name "Net-(D410-+)") (class "Default")
      (node (ref "D410") (pin "1") (pinfunction "+_1") (pintype "passive"))
      (node (ref "JP403") (pin "1") (pinfunction "1_1") (pintype "passive"))
    )
    (net (code "368") (name "Net-(D411-+)") (class "Default")
      (node (ref "D411") (pin "1") (pinfunction "+_1") (pintype "passive"))
      (node (ref "R433") (pin "1") (pinfunction "1_1") (pintype "passive"))
    )
    (net (code "369") (name "Net-(D411--)") (class "Default")
      (node (ref "D411") (pin "2") (pinfunction "-_2") (pintype "passive"))
      (node (ref "IC408") (pin "2") (pinfunction "OUT_2") (pintype "open_collector"))
      (node (ref "JP405") (pin "1") (pinfunction "1_1") (pintype "passive"))
      (node (ref "Q407") (pin "1") (pinfunction "G_1") (pintype "passive"))
      (node (ref "R435") (pin "2") (pinfunction "2_2") (pintype "passive"))
    )
    (net (code "370") (name "Net-(D412-+)") (class "Default")
      (node (ref "D412") (pin "1") (pinfunction "+_1") (pintype "passive"))
      (node (ref "R440") (pin "1") (pinfunction "1_1") (pintype "passive"))
    )
    (net (code "371") (name "Net-(D412--)") (class "Default")
      (node (ref "C409") (pin "2") (pinfunction "2_2") (pintype "passive"))
      (node (ref "D412") (pin "2") (pinfunction "-_2") (pintype "passive"))
      (node (ref "IC410") (pin "2") (pinfunction "TR_2") (pintype "input"))
      (node (ref "IC410") (pin "6") (pinfunction "THR_6") (pintype "input"))
      (node (ref "R441") (pin "1") (pinfunction "1_1") (pintype "passive"))
    )
    (net (code "372") (name "Net-(D505--)") (class "Default")
      (node (ref "D505") (pin "2") (pinfunction "-_2") (pintype "passive"))
      (node (ref "Q504") (pin "2") (pinfunction "C_2") (pintype "passive"))
      (node (ref "START501") (pin "TP") (pinfunction "PP_TP") (pintype "input"))
      (node (ref "X501") (pin "5") (pinfunction "5_5") (pintype "passive"))
    )
    (net (code "373") (name "Net-(D506-+)") (class "Default")
      (node (ref "D506") (pin "1") (pinfunction "+_1") (pintype "passive"))
      (node (ref "R527") (pin "1") (pinfunction "1_1") (pintype "passive"))
    )
    (net (code "374") (name "Net-(D509-+)") (class "Default")
      (node (ref "D509") (pin "1") (pinfunction "+_1") (pintype "passive"))
      (node (ref "JP502") (pin "2") (pinfunction "2_2") (pintype "passive"))
    )
    (net (code "375") (name "Net-(D510-+)") (class "Default")
      (node (ref "D510") (pin "1") (pinfunction "+_1") (pintype "passive"))
      (node (ref "JP503") (pin "1") (pinfunction "1_1") (pintype "passive"))
    )
    (net (code "376") (name "Net-(D511-+)") (class "Default")
      (node (ref "D511") (pin "1") (pinfunction "+_1") (pintype "passive"))
      (node (ref "R533") (pin "1") (pinfunction "1_1") (pintype "passive"))
    )
    (net (code "377") (name "Net-(D511--)") (class "Default")
      (node (ref "D511") (pin "2") (pinfunction "-_2") (pintype "passive"))
      (node (ref "IC508") (pin "2") (pinfunction "OUT_2") (pintype "open_collector"))
      (node (ref "JP505") (pin "1") (pinfunction "1_1") (pintype "passive"))
      (node (ref "Q507") (pin "1") (pinfunction "G_1") (pintype "passive"))
      (node (ref "R535") (pin "2") (pinfunction "2_2") (pintype "passive"))
    )
    (net (code "378") (name "Net-(D512-+)") (class "Default")
      (node (ref "D512") (pin "1") (pinfunction "+_1") (pintype "passive"))
      (node (ref "R540") (pin "1") (pinfunction "1_1") (pintype "passive"))
    )
    (net (code "379") (name "Net-(D512--)") (class "Default")
      (node (ref "C509") (pin "2") (pinfunction "2_2") (pintype "passive"))
      (node (ref "D512") (pin "2") (pinfunction "-_2") (pintype "passive"))
      (node (ref "IC510") (pin "2") (pinfunction "TR_2") (pintype "input"))
      (node (ref "IC510") (pin "6") (pinfunction "THR_6") (pintype "input"))
      (node (ref "R541") (pin "1") (pinfunction "1_1") (pintype "passive"))
    )
    (net (code "380") (name "Net-(D605--)") (class "Default")
      (node (ref "D605") (pin "2") (pinfunction "-_2") (pintype "passive"))
      (node (ref "Q604") (pin "2") (pinfunction "C_2") (pintype "passive"))
      (node (ref "START601") (pin "TP") (pinfunction "PP_TP") (pintype "input"))
      (node (ref "X601") (pin "5") (pinfunction "5_5") (pintype "passive"))
    )
    (net (code "381") (name "Net-(D606-+)") (class "Default")
      (node (ref "D606") (pin "1") (pinfunction "+_1") (pintype "passive"))
      (node (ref "R627") (pin "1") (pinfunction "1_1") (pintype "passive"))
    )
    (net (code "382") (name "Net-(D609-+)") (class "Default")
      (node (ref "D609") (pin "1") (pinfunction "+_1") (pintype "passive"))
      (node (ref "JP602") (pin "2") (pinfunction "2_2") (pintype "passive"))
    )
    (net (code "383") (name "Net-(D610-+)") (class "Default")
      (node (ref "D610") (pin "1") (pinfunction "+_1") (pintype "passive"))
      (node (ref "JP603") (pin "1") (pinfunction "1_1") (pintype "passive"))
    )
    (net (code "384") (name "Net-(D611-+)") (class "Default")
      (node (ref "D611") (pin "1") (pinfunction "+_1") (pintype "passive"))
      (node (ref "R633") (pin "1") (pinfunction "1_1") (pintype "passive"))
    )
    (net (code "385") (name "Net-(D611--)") (class "Default")
      (node (ref "D611") (pin "2") (pinfunction "-_2") (pintype "passive"))
      (node (ref "IC608") (pin "2") (pinfunction "OUT_2") (pintype "open_collector"))
      (node (ref "JP605") (pin "1") (pinfunction "1_1") (pintype "passive"))
      (node (ref "Q607") (pin "1") (pinfunction "G_1") (pintype "passive"))
      (node (ref "R635") (pin "2") (pinfunction "2_2") (pintype "passive"))
    )
    (net (code "386") (name "Net-(D612-+)") (class "Default")
      (node (ref "D612") (pin "1") (pinfunction "+_1") (pintype "passive"))
      (node (ref "R640") (pin "1") (pinfunction "1_1") (pintype "passive"))
    )
    (net (code "387") (name "Net-(D612--)") (class "Default")
      (node (ref "C609") (pin "2") (pinfunction "2_2") (pintype "passive"))
      (node (ref "D612") (pin "2") (pinfunction "-_2") (pintype "passive"))
      (node (ref "IC610") (pin "2") (pinfunction "TR_2") (pintype "input"))
      (node (ref "IC610") (pin "6") (pinfunction "THR_6") (pintype "input"))
      (node (ref "R641") (pin "1") (pinfunction "1_1") (pintype "passive"))
    )
    (net (code "388") (name "Net-(IC1A-A)") (class "Default")
      (node (ref "IC1") (pin "10") (pinfunction "A_10") (pintype "input"))
      (node (ref "R6") (pin "1") (pinfunction "1_1") (pintype "passive"))
      (node (ref "X1") (pin "4") (pinfunction "4_4") (pintype "passive"))
      (node (ref "X2") (pin "2") (pinfunction "S_2") (pintype "passive"))
    )
    (net (code "389") (name "Net-(IC1A-B)") (class "Default")
      (node (ref "IC1") (pin "13") (pinfunction "B_13") (pintype "input"))
      (node (ref "R5") (pin "1") (pinfunction "1_1") (pintype "passive"))
      (node (ref "X1") (pin "3") (pinfunction "3_3") (pintype "passive"))
      (node (ref "X2") (pin "3") (pinfunction "S_3") (pintype "passive"))
    )
    (net (code "390") (name "Net-(IC1A-C)") (class "Default")
      (node (ref "IC1") (pin "12") (pinfunction "C_12") (pintype "input"))
      (node (ref "R4") (pin "1") (pinfunction "1_1") (pintype "passive"))
      (node (ref "X1") (pin "2") (pinfunction "2_2") (pintype "passive"))
      (node (ref "X2") (pin "4") (pinfunction "S_4") (pintype "passive"))
    )
    (net (code "391") (name "Net-(IC1A-Q0)") (class "Default")
      (node (ref "IC1") (pin "3") (pinfunction "Q0_3") (pintype "output"))
      (node (ref "IC4") (pin "1") (pinfunction "I1_1") (pintype "input"))
      (node (ref "IC4") (pin "2") (pinfunction "I2_2") (pintype "input"))
      (node (ref "Q7") (pin "1") (pinfunction "G_1") (pintype "passive"))
    )
    (net (code "392") (name "Net-(IC1A-Q1)") (class "Default")
      (node (ref "IC1") (pin "14") (pinfunction "Q1_14") (pintype "output"))
      (node (ref "IC4") (pin "6") (pinfunction "I6_6") (pintype "input"))
    )
    (net (code "393") (name "Net-(IC1A-Q2)") (class "Default")
      (node (ref "IC1") (pin "2") (pinfunction "Q2_2") (pintype "output"))
      (node (ref "IC4") (pin "7") (pinfunction "I7_7") (pintype "input"))
    )
    (net (code "394") (name "Net-(IC1A-Q3)") (class "Default")
      (node (ref "IC1") (pin "15") (pinfunction "Q3_15") (pintype "output"))
      (node (ref "IC4") (pin "5") (pinfunction "I5_5") (pintype "input"))
    )
    (net (code "395") (name "Net-(IC1A-Q4)") (class "Default")
      (node (ref "IC1") (pin "1") (pinfunction "Q4_1") (pintype "output"))
      (node (ref "IC4") (pin "4") (pinfunction "I4_4") (pintype "input"))
    )
    (net (code "396") (name "Net-(IC1A-Q5)") (class "Default")
      (node (ref "IC1") (pin "6") (pinfunction "Q5_6") (pintype "output"))
      (node (ref "IC4") (pin "3") (pinfunction "I3_3") (pintype "input"))
    )
    (net (code "397") (name "Net-(IC3-ADJ)") (class "Default")
      (node (ref "IC3") (pin "1") (pinfunction "ADJ_1") (pintype "input"))
      (node (ref "R2") (pin "1") (pinfunction "1_1") (pintype "passive"))
      (node (ref "R9") (pin "2") (pinfunction "2_2") (pintype "passive"))
      (node (ref "X1") (pin "7") (pinfunction "7_7") (pintype "passive"))
    )
    (net (code "398") (name "Net-(IC3-VI)") (class "Default")
      (node (ref "IC3") (pin "3") (pinfunction "VI_3") (pintype "input"))
      (node (ref "Q4") (pin "2") (pinfunction "C_2") (pintype "passive"))
    )
    (net (code "399") (name "Net-(IC3-VO)") (class "Default")
      (node (ref "IC3") (pin "2") (pinfunction "VO_2") (pintype "passive"))
      (node (ref "R2") (pin "2") (pinfunction "2_2") (pintype "passive"))
    )
    (net (code "400") (name "Net-(IC4-O2)") (class "Default")
      (node (ref "IC4") (pin "15") (pinfunction "O2_15") (pintype "open_collector"))
      (node (ref "R23") (pin "1") (pinfunction "1_1") (pintype "passive"))
    )
    (net (code "401") (name "Net-(IC5A-+IN)") (class "Default")
      (node (ref "IC5") (pin "5") (pinfunction "+IN_5") (pintype "input"))
      (node (ref "R13") (pin "1") (pinfunction "1_1") (pintype "passive"))
      (node (ref "R14") (pin "2") (pinfunction "2_2") (pintype "passive"))
      (node (ref "R15") (pin "2") (pinfunction "2_2") (pintype "passive"))
    )
    (net (code "402") (name "Net-(IC5A--IN)") (class "Default")
      (node (ref "C2") (pin "1") (pinfunction "1_1") (pintype "passive"))
      (node (ref "IC5") (pin "4") (pinfunction "-IN_4") (pintype "input"))
      (node (ref "R12") (pin "1") (pinfunction "1_1") (pintype "passive"))
    )
    (net (code "403") (name "Net-(IC5B-+IN)") (class "Default")
      (node (ref "IC5") (pin "7") (pinfunction "+IN_7") (pintype "input"))
      (node (ref "R10") (pin "1") (pinfunction "1_1") (pintype "passive"))
      (node (ref "R26") (pin "1") (pinfunction "1_1") (pintype "passive"))
    )
    (net (code "404") (name "Net-(IC5B--IN)") (class "Default")
      (node (ref "IC5") (pin "6") (pinfunction "-IN_6") (pintype "input"))
      (node (ref "IC5") (pin "8") (pinfunction "-IN_8") (pintype "input"))
      (node (ref "R9") (pin "1") (pinfunction "1_1") (pintype "passive"))
    )
    (net (code "405") (name "Net-(IC5B-OUT)") (class "Default")
      (node (ref "IC5") (pin "1") (pinfunction "OUT_1") (pintype "open_collector"))
      (node (ref "R11") (pin "2") (pinfunction "2_2") (pintype "passive"))
      (node (ref "R16") (pin "2") (pinfunction "2_2") (pintype "passive"))
    )
    (net (code "406") (name "Net-(IC5C-+IN)") (class "Default")
      (node (ref "C5") (pin "1") (pinfunction "1_1") (pintype "passive"))
      (node (ref "IC5") (pin "9") (pinfunction "+IN_9") (pintype "input"))
      (node (ref "R18") (pin "2") (pinfunction "2_2") (pintype "passive"))
      (node (ref "R26") (pin "2") (pinfunction "2_2") (pintype "passive"))
    )
    (net (code "407") (name "Net-(IC5C-OUT)") (class "Default")
      (node (ref "C6") (pin "2") (pinfunction "2_2") (pintype "passive"))
      (node (ref "IC5") (pin "14") (pinfunction "OUT_14") (pintype "open_collector"))
      (node (ref "R17") (pin "2") (pinfunction "2_2") (pintype "passive"))
    )
    (net (code "408") (name "Net-(IC7-CV)") (class "Default")
      (node (ref "IC7") (pin "5") (pinfunction "CV_5") (pintype "input"))
      (node (ref "R32") (pin "2") (pinfunction "2_2") (pintype "passive"))
    )
    (net (code "409") (name "Net-(IC7-Q)") (class "Default")
      (node (ref "IC7") (pin "3") (pinfunction "Q_3") (pintype "output"))
      (node (ref "IC8") (pin "12") (pinfunction "A_12") (pintype "input"))
      (node (ref "R32") (pin "1") (pinfunction "1_1") (pintype "passive"))
    )
    (net (code "410") (name "Net-(IC8B-B)") (class "Default")
      (node (ref "IC8") (pin "11") (pinfunction "B_11") (pintype "input"))
      (node (ref "IC8") (pin "9") (pinfunction "~{Q}_9") (pintype "output"))
      (node (ref "R38") (pin "2") (pinfunction "2_2") (pintype "passive"))
    )
    (net (code "411") (name "Net-(IC8B-T2)") (class "Default")
      (node (ref "C9") (pin "1") (pinfunction "1_1") (pintype "passive"))
      (node (ref "IC8") (pin "14") (pinfunction "T2_14") (pintype "input"))
      (node (ref "R36") (pin "1") (pinfunction "1_1") (pintype "passive"))
    )
    (net (code "412") (name "Net-(IC10A-+IN)") (class "Default")
      (node (ref "C4") (pin "1") (pinfunction "1_1") (pintype "passive"))
      (node (ref "IC10") (pin "3") (pinfunction "+IN_3") (pintype "input"))
      (node (ref "R7") (pin "1") (pinfunction "1_1") (pintype "passive"))
    )
    (net (code "413") (name "Net-(IC10A--IN)") (class "Default")
      (node (ref "IC10") (pin "2") (pinfunction "-IN_2") (pintype "input"))
      (node (ref "R8") (pin "2") (pinfunction "2_2") (pintype "passive"))
    )
    (net (code "414") (name "Net-(IC10A-OUT)") (class "Default")
      (node (ref "IC10") (pin "1") (pinfunction "OUT_1") (pintype "output"))
      (node (ref "R39") (pin "2") (pinfunction "2_2") (pintype "passive"))
    )
    (net (code "415") (name "Net-(IC10B-+IN)") (class "Default")
      (node (ref "IC10") (pin "5") (pinfunction "+IN_5") (pintype "input"))
      (node (ref "R40") (pin "2") (pinfunction "2_2") (pintype "passive"))
      (node (ref "R41") (pin "2") (pinfunction "2_2") (pintype "passive"))
    )
    (net (code "416") (name "Net-(IC10B--IN)") (class "Default")
      (node (ref "IC10") (pin "6") (pinfunction "-IN_6") (pintype "input"))
      (node (ref "R42") (pin "1") (pinfunction "1_1") (pintype "passive"))
      (node (ref "R43") (pin "2") (pinfunction "2_2") (pintype "passive"))
    )
    (net (code "417") (name "Net-(IC10B-OUT)") (class "Default")
      (node (ref "IC10") (pin "7") (pinfunction "OUT_7") (pintype "output"))
      (node (ref "R27") (pin "1") (pinfunction "1_1") (pintype "passive"))
      (node (ref "R41") (pin "1") (pinfunction "1_1") (pintype "passive"))
    )
    (net (code "418") (name "Net-(IC11A-A)") (class "Default")
      (node (ref "IC11") (pin "10") (pinfunction "A_10") (pintype "input"))
      (node (ref "R51") (pin "1") (pinfunction "1_1") (pintype "passive"))
      (node (ref "X4") (pin "4") (pinfunction "4_4") (pintype "passive"))
      (node (ref "X5") (pin "2") (pinfunction "S_2") (pintype "passive"))
    )
    (net (code "419") (name "Net-(IC11A-B)") (class "Default")
      (node (ref "IC11") (pin "13") (pinfunction "B_13") (pintype "input"))
      (node (ref "R50") (pin "1") (pinfunction "1_1") (pintype "passive"))
      (node (ref "X4") (pin "3") (pinfunction "3_3") (pintype "passive"))
      (node (ref "X5") (pin "3") (pinfunction "S_3") (pintype "passive"))
    )
    (net (code "420") (name "Net-(IC11A-C)") (class "Default")
      (node (ref "IC11") (pin "12") (pinfunction "C_12") (pintype "input"))
      (node (ref "R49") (pin "1") (pinfunction "1_1") (pintype "passive"))
      (node (ref "X4") (pin "2") (pinfunction "2_2") (pintype "passive"))
      (node (ref "X5") (pin "4") (pinfunction "S_4") (pintype "passive"))
    )
    (net (code "421") (name "Net-(IC11A-Q0)") (class "Default")
      (node (ref "IC11") (pin "3") (pinfunction "Q0_3") (pintype "output"))
      (node (ref "IC14") (pin "1") (pinfunction "I1_1") (pintype "input"))
      (node (ref "IC14") (pin "2") (pinfunction "I2_2") (pintype "input"))
      (node (ref "Q14") (pin "1") (pinfunction "G_1") (pintype "passive"))
    )
    (net (code "422") (name "Net-(IC11A-Q1)") (class "Default")
      (node (ref "IC11") (pin "14") (pinfunction "Q1_14") (pintype "output"))
      (node (ref "IC14") (pin "6") (pinfunction "I6_6") (pintype "input"))
    )
    (net (code "423") (name "Net-(IC11A-Q2)") (class "Default")
      (node (ref "IC11") (pin "2") (pinfunction "Q2_2") (pintype "output"))
      (node (ref "IC14") (pin "7") (pinfunction "I7_7") (pintype "input"))
    )
    (net (code "424") (name "Net-(IC11A-Q3)") (class "Default")
      (node (ref "IC11") (pin "15") (pinfunction "Q3_15") (pintype "output"))
      (node (ref "IC14") (pin "5") (pinfunction "I5_5") (pintype "input"))
    )
    (net (code "425") (name "Net-(IC11A-Q4)") (class "Default")
      (node (ref "IC11") (pin "1") (pinfunction "Q4_1") (pintype "output"))
      (node (ref "IC14") (pin "4") (pinfunction "I4_4") (pintype "input"))
    )
    (net (code "426") (name "Net-(IC11A-Q5)") (class "Default")
      (node (ref "IC11") (pin "6") (pinfunction "Q5_6") (pintype "output"))
      (node (ref "IC14") (pin "3") (pinfunction "I3_3") (pintype "input"))
    )
    (net (code "427") (name "Net-(IC13-ADJ)") (class "Default")
      (node (ref "IC13") (pin "1") (pinfunction "ADJ_1") (pintype "input"))
      (node (ref "R47") (pin "1") (pinfunction "1_1") (pintype "passive"))
      (node (ref "R54") (pin "2") (pinfunction "2_2") (pintype "passive"))
      (node (ref "X4") (pin "7") (pinfunction "7_7") (pintype "passive"))
    )
    (net (code "428") (name "Net-(IC13-VI)") (class "Default")
      (node (ref "IC13") (pin "3") (pinfunction "VI_3") (pintype "input"))
      (node (ref "Q11") (pin "2") (pinfunction "C_2") (pintype "passive"))
    )
    (net (code "429") (name "Net-(IC13-VO)") (class "Default")
      (node (ref "IC13") (pin "2") (pinfunction "VO_2") (pintype "passive"))
      (node (ref "R47") (pin "2") (pinfunction "2_2") (pintype "passive"))
    )
    (net (code "430") (name "Net-(IC14-O2)") (class "Default")
      (node (ref "IC14") (pin "15") (pinfunction "O2_15") (pintype "open_collector"))
      (node (ref "R68") (pin "1") (pinfunction "1_1") (pintype "passive"))
    )
    (net (code "431") (name "Net-(IC15A-+IN)") (class "Default")
      (node (ref "IC15") (pin "5") (pinfunction "+IN_5") (pintype "input"))
      (node (ref "R58") (pin "1") (pinfunction "1_1") (pintype "passive"))
      (node (ref "R59") (pin "2") (pinfunction "2_2") (pintype "passive"))
      (node (ref "R60") (pin "2") (pinfunction "2_2") (pintype "passive"))
    )
    (net (code "432") (name "Net-(IC15A--IN)") (class "Default")
      (node (ref "C12") (pin "1") (pinfunction "1_1") (pintype "passive"))
      (node (ref "IC15") (pin "4") (pinfunction "-IN_4") (pintype "input"))
      (node (ref "R57") (pin "1") (pinfunction "1_1") (pintype "passive"))
    )
    (net (code "433") (name "Net-(IC15B-+IN)") (class "Default")
      (node (ref "IC15") (pin "7") (pinfunction "+IN_7") (pintype "input"))
      (node (ref "R55") (pin "1") (pinfunction "1_1") (pintype "passive"))
      (node (ref "R71") (pin "1") (pinfunction "1_1") (pintype "passive"))
    )
    (net (code "434") (name "Net-(IC15B--IN)") (class "Default")
      (node (ref "IC15") (pin "6") (pinfunction "-IN_6") (pintype "input"))
      (node (ref "IC15") (pin "8") (pinfunction "-IN_8") (pintype "input"))
      (node (ref "R54") (pin "1") (pinfunction "1_1") (pintype "passive"))
    )
    (net (code "435") (name "Net-(IC15B-OUT)") (class "Default")
      (node (ref "IC15") (pin "1") (pinfunction "OUT_1") (pintype "open_collector"))
      (node (ref "R56") (pin "2") (pinfunction "2_2") (pintype "passive"))
      (node (ref "R61") (pin "2") (pinfunction "2_2") (pintype "passive"))
    )
    (net (code "436") (name "Net-(IC15C-+IN)") (class "Default")
      (node (ref "C15") (pin "1") (pinfunction "1_1") (pintype "passive"))
      (node (ref "IC15") (pin "9") (pinfunction "+IN_9") (pintype "input"))
      (node (ref "R63") (pin "2") (pinfunction "2_2") (pintype "passive"))
      (node (ref "R71") (pin "2") (pinfunction "2_2") (pintype "passive"))
    )
    (net (code "437") (name "Net-(IC15C-OUT)") (class "Default")
      (node (ref "C16") (pin "2") (pinfunction "2_2") (pintype "passive"))
      (node (ref "IC15") (pin "14") (pinfunction "OUT_14") (pintype "open_collector"))
      (node (ref "R62") (pin "2") (pinfunction "2_2") (pintype "passive"))
    )
    (net (code "438") (name "Net-(IC17-CV)") (class "Default")
      (node (ref "IC17") (pin "5") (pinfunction "CV_5") (pintype "input"))
      (node (ref "R77") (pin "2") (pinfunction "2_2") (pintype "passive"))
    )
    (net (code "439") (name "Net-(IC17-Q)") (class "Default")
      (node (ref "IC17") (pin "3") (pinfunction "Q_3") (pintype "output"))
      (node (ref "IC18") (pin "12") (pinfunction "A_12") (pintype "input"))
      (node (ref "R77") (pin "1") (pinfunction "1_1") (pintype "passive"))
    )
    (net (code "440") (name "Net-(IC18B-B)") (class "Default")
      (node (ref "IC18") (pin "11") (pinfunction "B_11") (pintype "input"))
      (node (ref "IC18") (pin "9") (pinfunction "~{Q}_9") (pintype "output"))
      (node (ref "R83") (pin "2") (pinfunction "2_2") (pintype "passive"))
    )
    (net (code "441") (name "Net-(IC18B-T2)") (class "Default")
      (node (ref "C19") (pin "1") (pinfunction "1_1") (pintype "passive"))
      (node (ref "IC18") (pin "14") (pinfunction "T2_14") (pintype "input"))
      (node (ref "R81") (pin "1") (pinfunction "1_1") (pintype "passive"))
    )
    (net (code "442") (name "Net-(IC20A-+IN)") (class "Default")
      (node (ref "C14") (pin "1") (pinfunction "1_1") (pintype "passive"))
      (node (ref "IC20") (pin "3") (pinfunction "+IN_3") (pintype "input"))
      (node (ref "R52") (pin "1") (pinfunction "1_1") (pintype "passive"))
    )
    (net (code "443") (name "Net-(IC20A--IN)") (class "Default")
      (node (ref "IC20") (pin "2") (pinfunction "-IN_2") (pintype "input"))
      (node (ref "R53") (pin "2") (pinfunction "2_2") (pintype "passive"))
    )
    (net (code "444") (name "Net-(IC20A-OUT)") (class "Default")
      (node (ref "IC20") (pin "1") (pinfunction "OUT_1") (pintype "output"))
      (node (ref "R84") (pin "2") (pinfunction "2_2") (pintype "passive"))
    )
    (net (code "445") (name "Net-(IC20B-+IN)") (class "Default")
      (node (ref "IC20") (pin "5") (pinfunction "+IN_5") (pintype "input"))
      (node (ref "R85") (pin "2") (pinfunction "2_2") (pintype "passive"))
      (node (ref "R86") (pin "2") (pinfunction "2_2") (pintype "passive"))
    )
    (net (code "446") (name "Net-(IC20B--IN)") (class "Default")
      (node (ref "IC20") (pin "6") (pinfunction "-IN_6") (pintype "input"))
      (node (ref "R87") (pin "1") (pinfunction "1_1") (pintype "passive"))
      (node (ref "R88") (pin "2") (pinfunction "2_2") (pintype "passive"))
    )
    (net (code "447") (name "Net-(IC20B-OUT)") (class "Default")
      (node (ref "IC20") (pin "7") (pinfunction "OUT_7") (pintype "output"))
      (node (ref "R72") (pin "1") (pinfunction "1_1") (pintype "passive"))
      (node (ref "R86") (pin "1") (pinfunction "1_1") (pintype "passive"))
    )
    (net (code "448") (name "Net-(IC21A-A)") (class "Default")
      (node (ref "IC21") (pin "10") (pinfunction "A_10") (pintype "input"))
      (node (ref "R96") (pin "1") (pinfunction "1_1") (pintype "passive"))
      (node (ref "X7") (pin "4") (pinfunction "4_4") (pintype "passive"))
      (node (ref "X8") (pin "2") (pinfunction "S_2") (pintype "passive"))
    )
    (net (code "449") (name "Net-(IC21A-B)") (class "Default")
      (node (ref "IC21") (pin "13") (pinfunction "B_13") (pintype "input"))
      (node (ref "R95") (pin "1") (pinfunction "1_1") (pintype "passive"))
      (node (ref "X7") (pin "3") (pinfunction "3_3") (pintype "passive"))
      (node (ref "X8") (pin "3") (pinfunction "S_3") (pintype "passive"))
    )
    (net (code "450") (name "Net-(IC21A-C)") (class "Default")
      (node (ref "IC21") (pin "12") (pinfunction "C_12") (pintype "input"))
      (node (ref "R94") (pin "1") (pinfunction "1_1") (pintype "passive"))
      (node (ref "X7") (pin "2") (pinfunction "2_2") (pintype "passive"))
      (node (ref "X8") (pin "4") (pinfunction "S_4") (pintype "passive"))
    )
    (net (code "451") (name "Net-(IC21A-Q0)") (class "Default")
      (node (ref "IC21") (pin "3") (pinfunction "Q0_3") (pintype "output"))
      (node (ref "IC24") (pin "1") (pinfunction "I1_1") (pintype "input"))
      (node (ref "IC24") (pin "2") (pinfunction "I2_2") (pintype "input"))
      (node (ref "Q21") (pin "1") (pinfunction "G_1") (pintype "passive"))
    )
    (net (code "452") (name "Net-(IC21A-Q1)") (class "Default")
      (node (ref "IC21") (pin "14") (pinfunction "Q1_14") (pintype "output"))
      (node (ref "IC24") (pin "6") (pinfunction "I6_6") (pintype "input"))
    )
    (net (code "453") (name "Net-(IC21A-Q2)") (class "Default")
      (node (ref "IC21") (pin "2") (pinfunction "Q2_2") (pintype "output"))
      (node (ref "IC24") (pin "7") (pinfunction "I7_7") (pintype "input"))
    )
    (net (code "454") (name "Net-(IC21A-Q3)") (class "Default")
      (node (ref "IC21") (pin "15") (pinfunction "Q3_15") (pintype "output"))
      (node (ref "IC24") (pin "5") (pinfunction "I5_5") (pintype "input"))
    )
    (net (code "455") (name "Net-(IC21A-Q4)") (class "Default")
      (node (ref "IC21") (pin "1") (pinfunction "Q4_1") (pintype "output"))
      (node (ref "IC24") (pin "4") (pinfunction "I4_4") (pintype "input"))
    )
    (net (code "456") (name "Net-(IC21A-Q5)") (class "Default")
      (node (ref "IC21") (pin "6") (pinfunction "Q5_6") (pintype "output"))
      (node (ref "IC24") (pin "3") (pinfunction "I3_3") (pintype "input"))
    )
    (net (code "457") (name "Net-(IC23-ADJ)") (class "Default")
      (node (ref "IC23") (pin "1") (pinfunction "ADJ_1") (pintype "input"))
      (node (ref "R92") (pin "1") (pinfunction "1_1") (pintype "passive"))
      (node (ref "R99") (pin "2") (pinfunction "2_2") (pintype "passive"))
      (node (ref "X7") (pin "7") (pinfunction "7_7") (pintype "passive"))
    )
    (net (code "458") (name "Net-(IC23-VI)") (class "Default")
      (node (ref "IC23") (pin "3") (pinfunction "VI_3") (pintype "input"))
      (node (ref "Q18") (pin "2") (pinfunction "C_2") (pintype "passive"))
    )
    (net (code "459") (name "Net-(IC23-VO)") (class "Default")
      (node (ref "IC23") (pin "2") (pinfunction "VO_2") (pintype "passive"))
      (node (ref "R92") (pin "2") (pinfunction "2_2") (pintype "passive"))
    )
    (net (code "460") (name "Net-(IC24-O2)") (class "Default")
      (node (ref "IC24") (pin "15") (pinfunction "O2_15") (pintype "open_collector"))
      (node (ref "R158") (pin "1") (pinfunction "1_1") (pintype "passive"))
    )
    (net (code "461") (name "Net-(IC25A-+IN)") (class "Default")
      (node (ref "IC25") (pin "5") (pinfunction "+IN_5") (pintype "input"))
      (node (ref "R148") (pin "1") (pinfunction "1_1") (pintype "passive"))
      (node (ref "R149") (pin "2") (pinfunction "2_2") (pintype "passive"))
      (node (ref "R150") (pin "2") (pinfunction "2_2") (pintype "passive"))
    )
    (net (code "462") (name "Net-(IC25A--IN)") (class "Default")
      (node (ref "C22") (pin "1") (pinfunction "1_1") (pintype "passive"))
      (node (ref "IC25") (pin "4") (pinfunction "-IN_4") (pintype "input"))
      (node (ref "R147") (pin "1") (pinfunction "1_1") (pintype "passive"))
    )
    (net (code "463") (name "Net-(IC25B-+IN)") (class "Default")
      (node (ref "IC25") (pin "7") (pinfunction "+IN_7") (pintype "input"))
      (node (ref "R100") (pin "1") (pinfunction "1_1") (pintype "passive"))
      (node (ref "R161") (pin "1") (pinfunction "1_1") (pintype "passive"))
    )
    (net (code "464") (name "Net-(IC25B--IN)") (class "Default")
      (node (ref "IC25") (pin "6") (pinfunction "-IN_6") (pintype "input"))
      (node (ref "IC25") (pin "8") (pinfunction "-IN_8") (pintype "input"))
      (node (ref "R99") (pin "1") (pinfunction "1_1") (pintype "passive"))
    )
    (net (code "465") (name "Net-(IC25B-OUT)") (class "Default")
      (node (ref "IC25") (pin "1") (pinfunction "OUT_1") (pintype "open_collector"))
      (node (ref "R104") (pin "2") (pinfunction "2_2") (pintype "passive"))
      (node (ref "R151") (pin "2") (pinfunction "2_2") (pintype "passive"))
    )
    (net (code "466") (name "Net-(IC25C-+IN)") (class "Default")
      (node (ref "C25") (pin "1") (pinfunction "1_1") (pintype "passive"))
      (node (ref "IC25") (pin "9") (pinfunction "+IN_9") (pintype "input"))
      (node (ref "R153") (pin "2") (pinfunction "2_2") (pintype "passive"))
      (node (ref "R161") (pin "2") (pinfunction "2_2") (pintype "passive"))
    )
    (net (code "467") (name "Net-(IC25C-OUT)") (class "Default")
      (node (ref "C26") (pin "2") (pinfunction "2_2") (pintype "passive"))
      (node (ref "IC25") (pin "14") (pinfunction "OUT_14") (pintype "open_collector"))
      (node (ref "R152") (pin "2") (pinfunction "2_2") (pintype "passive"))
    )
    (net (code "468") (name "Net-(IC27-CV)") (class "Default")
      (node (ref "IC27") (pin "5") (pinfunction "CV_5") (pintype "input"))
      (node (ref "R167") (pin "2") (pinfunction "2_2") (pintype "passive"))
    )
    (net (code "469") (name "Net-(IC27-Q)") (class "Default")
      (node (ref "IC27") (pin "3") (pinfunction "Q_3") (pintype "output"))
      (node (ref "IC28") (pin "12") (pinfunction "A_12") (pintype "input"))
      (node (ref "R167") (pin "1") (pinfunction "1_1") (pintype "passive"))
    )
    (net (code "470") (name "Net-(IC28B-B)") (class "Default")
      (node (ref "IC28") (pin "11") (pinfunction "B_11") (pintype "input"))
      (node (ref "IC28") (pin "9") (pinfunction "~{Q}_9") (pintype "output"))
      (node (ref "R173") (pin "2") (pinfunction "2_2") (pintype "passive"))
    )
    (net (code "471") (name "Net-(IC28B-T2)") (class "Default")
      (node (ref "C29") (pin "1") (pinfunction "1_1") (pintype "passive"))
      (node (ref "IC28") (pin "14") (pinfunction "T2_14") (pintype "input"))
      (node (ref "R171") (pin "1") (pinfunction "1_1") (pintype "passive"))
    )
    (net (code "472") (name "Net-(IC30A-+IN)") (class "Default")
      (node (ref "C24") (pin "1") (pinfunction "1_1") (pintype "passive"))
      (node (ref "IC30") (pin "3") (pinfunction "+IN_3") (pintype "input"))
      (node (ref "R97") (pin "1") (pinfunction "1_1") (pintype "passive"))
    )
    (net (code "473") (name "Net-(IC30A--IN)") (class "Default")
      (node (ref "IC30") (pin "2") (pinfunction "-IN_2") (pintype "input"))
      (node (ref "R98") (pin "2") (pinfunction "2_2") (pintype "passive"))
    )
    (net (code "474") (name "Net-(IC30A-OUT)") (class "Default")
      (node (ref "IC30") (pin "1") (pinfunction "OUT_1") (pintype "output"))
      (node (ref "R174") (pin "2") (pinfunction "2_2") (pintype "passive"))
    )
    (net (code "475") (name "Net-(IC30B-+IN)") (class "Default")
      (node (ref "IC30") (pin "5") (pinfunction "+IN_5") (pintype "input"))
      (node (ref "R175") (pin "2") (pinfunction "2_2") (pintype "passive"))
      (node (ref "R176") (pin "2") (pinfunction "2_2") (pintype "passive"))
    )
    (net (code "476") (name "Net-(IC30B--IN)") (class "Default")
      (node (ref "IC30") (pin "6") (pinfunction "-IN_6") (pintype "input"))
      (node (ref "R177") (pin "1") (pinfunction "1_1") (pintype "passive"))
      (node (ref "R178") (pin "2") (pinfunction "2_2") (pintype "passive"))
    )
    (net (code "477") (name "Net-(IC30B-OUT)") (class "Default")
      (node (ref "IC30") (pin "7") (pinfunction "OUT_7") (pintype "output"))
      (node (ref "R162") (pin "1") (pinfunction "1_1") (pintype "passive"))
      (node (ref "R176") (pin "1") (pinfunction "1_1") (pintype "passive"))
    )
    (net (code "478") (name "Net-(IC31A-A)") (class "Default")
      (node (ref "IC31") (pin "10") (pinfunction "A_10") (pintype "input"))
      (node (ref "R186") (pin "1") (pinfunction "1_1") (pintype "passive"))
      (node (ref "X10") (pin "4") (pinfunction "4_4") (pintype "passive"))
      (node (ref "X11") (pin "2") (pinfunction "S_2") (pintype "passive"))
    )
    (net (code "479") (name "Net-(IC31A-B)") (class "Default")
      (node (ref "IC31") (pin "13") (pinfunction "B_13") (pintype "input"))
      (node (ref "R185") (pin "1") (pinfunction "1_1") (pintype "passive"))
      (node (ref "X10") (pin "3") (pinfunction "3_3") (pintype "passive"))
      (node (ref "X11") (pin "3") (pinfunction "S_3") (pintype "passive"))
    )
    (net (code "480") (name "Net-(IC31A-C)") (class "Default")
      (node (ref "IC31") (pin "12") (pinfunction "C_12") (pintype "input"))
      (node (ref "R184") (pin "1") (pinfunction "1_1") (pintype "passive"))
      (node (ref "X10") (pin "2") (pinfunction "2_2") (pintype "passive"))
      (node (ref "X11") (pin "4") (pinfunction "S_4") (pintype "passive"))
    )
    (net (code "481") (name "Net-(IC31A-Q0)") (class "Default")
      (node (ref "IC31") (pin "3") (pinfunction "Q0_3") (pintype "output"))
      (node (ref "IC34") (pin "1") (pinfunction "I1_1") (pintype "input"))
      (node (ref "IC34") (pin "2") (pinfunction "I2_2") (pintype "input"))
      (node (ref "Q28") (pin "1") (pinfunction "G_1") (pintype "passive"))
    )
    (net (code "482") (name "Net-(IC31A-Q1)") (class "Default")
      (node (ref "IC31") (pin "14") (pinfunction "Q1_14") (pintype "output"))
      (node (ref "IC34") (pin "6") (pinfunction "I6_6") (pintype "input"))
    )
    (net (code "483") (name "Net-(IC31A-Q2)") (class "Default")
      (node (ref "IC31") (pin "2") (pinfunction "Q2_2") (pintype "output"))
      (node (ref "IC34") (pin "7") (pinfunction "I7_7") (pintype "input"))
    )
    (net (code "484") (name "Net-(IC31A-Q3)") (class "Default")
      (node (ref "IC31") (pin "15") (pinfunction "Q3_15") (pintype "output"))
      (node (ref "IC34") (pin "5") (pinfunction "I5_5") (pintype "input"))
    )
    (net (code "485") (name "Net-(IC31A-Q4)") (class "Default")
      (node (ref "IC31") (pin "1") (pinfunction "Q4_1") (pintype "output"))
      (node (ref "IC34") (pin "4") (pinfunction "I4_4") (pintype "input"))
    )
    (net (code "486") (name "Net-(IC31A-Q5)") (class "Default")
      (node (ref "IC31") (pin "6") (pinfunction "Q5_6") (pintype "output"))
      (node (ref "IC34") (pin "3") (pinfunction "I3_3") (pintype "input"))
    )
    (net (code "487") (name "Net-(IC33-ADJ)") (class "Default")
      (node (ref "IC33") (pin "1") (pinfunction "ADJ_1") (pintype "input"))
      (node (ref "R182") (pin "1") (pinfunction "1_1") (pintype "passive"))
      (node (ref "R189") (pin "2") (pinfunction "2_2") (pintype "passive"))
      (node (ref "X10") (pin "7") (pinfunction "7_7") (pintype "passive"))
    )
    (net (code "488") (name "Net-(IC33-VI)") (class "Default")
      (node (ref "IC33") (pin "3") (pinfunction "VI_3") (pintype "input"))
      (node (ref "Q25") (pin "2") (pinfunction "C_2") (pintype "passive"))
    )
    (net (code "489") (name "Net-(IC33-VO)") (class "Default")
      (node (ref "IC33") (pin "2") (pinfunction "VO_2") (pintype "passive"))
      (node (ref "R182") (pin "2") (pinfunction "2_2") (pintype "passive"))
    )
    (net (code "490") (name "Net-(IC34-O2)") (class "Default")
      (node (ref "IC34") (pin "15") (pinfunction "O2_15") (pintype "open_collector"))
      (node (ref "R248") (pin "1") (pinfunction "1_1") (pintype "passive"))
    )
    (net (code "491") (name "Net-(IC35A-+IN)") (class "Default")
      (node (ref "IC35") (pin "5") (pinfunction "+IN_5") (pintype "input"))
      (node (ref "R193") (pin "1") (pinfunction "1_1") (pintype "passive"))
      (node (ref "R194") (pin "2") (pinfunction "2_2") (pintype "passive"))
      (node (ref "R195") (pin "2") (pinfunction "2_2") (pintype "passive"))
    )
    (net (code "492") (name "Net-(IC35A--IN)") (class "Default")
      (node (ref "C32") (pin "1") (pinfunction "1_1") (pintype "passive"))
      (node (ref "IC35") (pin "4") (pinfunction "-IN_4") (pintype "input"))
      (node (ref "R192") (pin "1") (pinfunction "1_1") (pintype "passive"))
    )
    (net (code "493") (name "Net-(IC35B-+IN)") (class "Default")
      (node (ref "IC35") (pin "7") (pinfunction "+IN_7") (pintype "input"))
      (node (ref "R190") (pin "1") (pinfunction "1_1") (pintype "passive"))
      (node (ref "R251") (pin "1") (pinfunction "1_1") (pintype "passive"))
    )
    (net (code "494") (name "Net-(IC35B--IN)") (class "Default")
      (node (ref "IC35") (pin "6") (pinfunction "-IN_6") (pintype "input"))
      (node (ref "IC35") (pin "8") (pinfunction "-IN_8") (pintype "input"))
      (node (ref "R189") (pin "1") (pinfunction "1_1") (pintype "passive"))
    )
    (net (code "495") (name "Net-(IC35B-OUT)") (class "Default")
      (node (ref "IC35") (pin "1") (pinfunction "OUT_1") (pintype "open_collector"))
      (node (ref "R191") (pin "2") (pinfunction "2_2") (pintype "passive"))
      (node (ref "R196") (pin "2") (pinfunction "2_2") (pintype "passive"))
    )
    (net (code "496") (name "Net-(IC35C-+IN)") (class "Default")
      (node (ref "C35") (pin "1") (pinfunction "1_1") (pintype "passive"))
      (node (ref "IC35") (pin "9") (pinfunction "+IN_9") (pintype "input"))
      (node (ref "R198") (pin "2") (pinfunction "2_2") (pintype "passive"))
      (node (ref "R251") (pin "2") (pinfunction "2_2") (pintype "passive"))
    )
    (net (code "497") (name "Net-(IC35C-OUT)") (class "Default")
      (node (ref "C36") (pin "2") (pinfunction "2_2") (pintype "passive"))
      (node (ref "IC35") (pin "14") (pinfunction "OUT_14") (pintype "open_collector"))
      (node (ref "R197") (pin "2") (pinfunction "2_2") (pintype "passive"))
    )
    (net (code "498") (name "Net-(IC37-CV)") (class "Default")
      (node (ref "IC37") (pin "5") (pinfunction "CV_5") (pintype "input"))
      (node (ref "R257") (pin "2") (pinfunction "2_2") (pintype "passive"))
    )
    (net (code "499") (name "Net-(IC37-Q)") (class "Default")
      (node (ref "IC37") (pin "3") (pinfunction "Q_3") (pintype "output"))
      (node (ref "IC38") (pin "12") (pinfunction "A_12") (pintype "input"))
      (node (ref "R257") (pin "1") (pinfunction "1_1") (pintype "passive"))
    )
    (net (code "500") (name "Net-(IC38B-B)") (class "Default")
      (node (ref "IC38") (pin "11") (pinfunction "B_11") (pintype "input"))
      (node (ref "IC38") (pin "9") (pinfunction "~{Q}_9") (pintype "output"))
      (node (ref "R263") (pin "2") (pinfunction "2_2") (pintype "passive"))
    )
    (net (code "501") (name "Net-(IC38B-T2)") (class "Default")
      (node (ref "C39") (pin "1") (pinfunction "1_1") (pintype "passive"))
      (node (ref "IC38") (pin "14") (pinfunction "T2_14") (pintype "input"))
      (node (ref "R261") (pin "1") (pinfunction "1_1") (pintype "passive"))
    )
    (net (code "502") (name "Net-(IC40A-+IN)") (class "Default")
      (node (ref "C34") (pin "1") (pinfunction "1_1") (pintype "passive"))
      (node (ref "IC40") (pin "3") (pinfunction "+IN_3") (pintype "input"))
      (node (ref "R187") (pin "1") (pinfunction "1_1") (pintype "passive"))
    )
    (net (code "503") (name "Net-(IC40A--IN)") (class "Default")
      (node (ref "IC40") (pin "2") (pinfunction "-IN_2") (pintype "input"))
      (node (ref "R188") (pin "2") (pinfunction "2_2") (pintype "passive"))
    )
    (net (code "504") (name "Net-(IC40A-OUT)") (class "Default")
      (node (ref "IC40") (pin "1") (pinfunction "OUT_1") (pintype "output"))
      (node (ref "R264") (pin "2") (pinfunction "2_2") (pintype "passive"))
    )
    (net (code "505") (name "Net-(IC40B-+IN)") (class "Default")
      (node (ref "IC40") (pin "5") (pinfunction "+IN_5") (pintype "input"))
      (node (ref "R265") (pin "2") (pinfunction "2_2") (pintype "passive"))
      (node (ref "R266") (pin "2") (pinfunction "2_2") (pintype "passive"))
    )
    (net (code "506") (name "Net-(IC40B--IN)") (class "Default")
      (node (ref "IC40") (pin "6") (pinfunction "-IN_6") (pintype "input"))
      (node (ref "R267") (pin "1") (pinfunction "1_1") (pintype "passive"))
      (node (ref "R268") (pin "2") (pinfunction "2_2") (pintype "passive"))
    )
    (net (code "507") (name "Net-(IC40B-OUT)") (class "Default")
      (node (ref "IC40") (pin "7") (pinfunction "OUT_7") (pintype "output"))
      (node (ref "R252") (pin "1") (pinfunction "1_1") (pintype "passive"))
      (node (ref "R266") (pin "1") (pinfunction "1_1") (pintype "passive"))
    )
    (net (code "508") (name "Net-(IC41A-A)") (class "Default")
      (node (ref "IC41") (pin "10") (pinfunction "A_10") (pintype "input"))
      (node (ref "R276") (pin "1") (pinfunction "1_1") (pintype "passive"))
      (node (ref "X13") (pin "4") (pinfunction "4_4") (pintype "passive"))
      (node (ref "X14") (pin "2") (pinfunction "S_2") (pintype "passive"))
    )
    (net (code "509") (name "Net-(IC41A-B)") (class "Default")
      (node (ref "IC41") (pin "13") (pinfunction "B_13") (pintype "input"))
      (node (ref "R275") (pin "1") (pinfunction "1_1") (pintype "passive"))
      (node (ref "X13") (pin "3") (pinfunction "3_3") (pintype "passive"))
      (node (ref "X14") (pin "3") (pinfunction "S_3") (pintype "passive"))
    )
    (net (code "510") (name "Net-(IC41A-C)") (class "Default")
      (node (ref "IC41") (pin "12") (pinfunction "C_12") (pintype "input"))
      (node (ref "R274") (pin "1") (pinfunction "1_1") (pintype "passive"))
      (node (ref "X13") (pin "2") (pinfunction "2_2") (pintype "passive"))
      (node (ref "X14") (pin "4") (pinfunction "S_4") (pintype "passive"))
    )
    (net (code "511") (name "Net-(IC41A-Q0)") (class "Default")
      (node (ref "IC41") (pin "3") (pinfunction "Q0_3") (pintype "output"))
      (node (ref "IC44") (pin "1") (pinfunction "I1_1") (pintype "input"))
      (node (ref "IC44") (pin "2") (pinfunction "I2_2") (pintype "input"))
      (node (ref "Q35") (pin "1") (pinfunction "G_1") (pintype "passive"))
    )
    (net (code "512") (name "Net-(IC41A-Q1)") (class "Default")
      (node (ref "IC41") (pin "14") (pinfunction "Q1_14") (pintype "output"))
      (node (ref "IC44") (pin "6") (pinfunction "I6_6") (pintype "input"))
    )
    (net (code "513") (name "Net-(IC41A-Q2)") (class "Default")
      (node (ref "IC41") (pin "2") (pinfunction "Q2_2") (pintype "output"))
      (node (ref "IC44") (pin "7") (pinfunction "I7_7") (pintype "input"))
    )
    (net (code "514") (name "Net-(IC41A-Q3)") (class "Default")
      (node (ref "IC41") (pin "15") (pinfunction "Q3_15") (pintype "output"))
      (node (ref "IC44") (pin "5") (pinfunction "I5_5") (pintype "input"))
    )
    (net (code "515") (name "Net-(IC41A-Q4)") (class "Default")
      (node (ref "IC41") (pin "1") (pinfunction "Q4_1") (pintype "output"))
      (node (ref "IC44") (pin "4") (pinfunction "I4_4") (pintype "input"))
    )
    (net (code "516") (name "Net-(IC41A-Q5)") (class "Default")
      (node (ref "IC41") (pin "6") (pinfunction "Q5_6") (pintype "output"))
      (node (ref "IC44") (pin "3") (pinfunction "I3_3") (pintype "input"))
    )
    (net (code "517") (name "Net-(IC43-ADJ)") (class "Default")
      (node (ref "IC43") (pin "1") (pinfunction "ADJ_1") (pintype "input"))
      (node (ref "R272") (pin "1") (pinfunction "1_1") (pintype "passive"))
      (node (ref "R279") (pin "2") (pinfunction "2_2") (pintype "passive"))
      (node (ref "X13") (pin "7") (pinfunction "7_7") (pintype "passive"))
    )
    (net (code "518") (name "Net-(IC43-VI)") (class "Default")
      (node (ref "IC43") (pin "3") (pinfunction "VI_3") (pintype "input"))
      (node (ref "Q32") (pin "2") (pinfunction "C_2") (pintype "passive"))
    )
    (net (code "519") (name "Net-(IC43-VO)") (class "Default")
      (node (ref "IC43") (pin "2") (pinfunction "VO_2") (pintype "passive"))
      (node (ref "R272") (pin "2") (pinfunction "2_2") (pintype "passive"))
    )
    (net (code "520") (name "Net-(IC44-O2)") (class "Default")
      (node (ref "IC44") (pin "15") (pinfunction "O2_15") (pintype "open_collector"))
      (node (ref "R293") (pin "1") (pinfunction "1_1") (pintype "passive"))
    )
    (net (code "521") (name "Net-(IC45A-+IN)") (class "Default")
      (node (ref "IC45") (pin "5") (pinfunction "+IN_5") (pintype "input"))
      (node (ref "R283") (pin "1") (pinfunction "1_1") (pintype "passive"))
      (node (ref "R284") (pin "2") (pinfunction "2_2") (pintype "passive"))
      (node (ref "R285") (pin "2") (pinfunction "2_2") (pintype "passive"))
    )
    (net (code "522") (name "Net-(IC45A--IN)") (class "Default")
      (node (ref "C42") (pin "1") (pinfunction "1_1") (pintype "passive"))
      (node (ref "IC45") (pin "4") (pinfunction "-IN_4") (pintype "input"))
      (node (ref "R282") (pin "1") (pinfunction "1_1") (pintype "passive"))
    )
    (net (code "523") (name "Net-(IC45B-+IN)") (class "Default")
      (node (ref "IC45") (pin "7") (pinfunction "+IN_7") (pintype "input"))
      (node (ref "R280") (pin "1") (pinfunction "1_1") (pintype "passive"))
      (node (ref "R296") (pin "1") (pinfunction "1_1") (pintype "passive"))
    )
    (net (code "524") (name "Net-(IC45B--IN)") (class "Default")
      (node (ref "IC45") (pin "6") (pinfunction "-IN_6") (pintype "input"))
      (node (ref "IC45") (pin "8") (pinfunction "-IN_8") (pintype "input"))
      (node (ref "R279") (pin "1") (pinfunction "1_1") (pintype "passive"))
    )
    (net (code "525") (name "Net-(IC45B-OUT)") (class "Default")
      (node (ref "IC45") (pin "1") (pinfunction "OUT_1") (pintype "open_collector"))
      (node (ref "R281") (pin "2") (pinfunction "2_2") (pintype "passive"))
      (node (ref "R286") (pin "2") (pinfunction "2_2") (pintype "passive"))
    )
    (net (code "526") (name "Net-(IC45C-+IN)") (class "Default")
      (node (ref "C45") (pin "1") (pinfunction "1_1") (pintype "passive"))
      (node (ref "IC45") (pin "9") (pinfunction "+IN_9") (pintype "input"))
      (node (ref "R288") (pin "2") (pinfunction "2_2") (pintype "passive"))
      (node (ref "R296") (pin "2") (pinfunction "2_2") (pintype "passive"))
    )
    (net (code "527") (name "Net-(IC45C-OUT)") (class "Default")
      (node (ref "C46") (pin "2") (pinfunction "2_2") (pintype "passive"))
      (node (ref "IC45") (pin "14") (pinfunction "OUT_14") (pintype "open_collector"))
      (node (ref "R287") (pin "2") (pinfunction "2_2") (pintype "passive"))
    )
    (net (code "528") (name "Net-(IC47-CV)") (class "Default")
      (node (ref "IC47") (pin "5") (pinfunction "CV_5") (pintype "input"))
      (node (ref "R347") (pin "2") (pinfunction "2_2") (pintype "passive"))
    )
    (net (code "529") (name "Net-(IC47-Q)") (class "Default")
      (node (ref "IC47") (pin "3") (pinfunction "Q_3") (pintype "output"))
      (node (ref "IC48") (pin "12") (pinfunction "A_12") (pintype "input"))
      (node (ref "R347") (pin "1") (pinfunction "1_1") (pintype "passive"))
    )
    (net (code "530") (name "Net-(IC48B-B)") (class "Default")
      (node (ref "IC48") (pin "11") (pinfunction "B_11") (pintype "input"))
      (node (ref "IC48") (pin "9") (pinfunction "~{Q}_9") (pintype "output"))
      (node (ref "R353") (pin "2") (pinfunction "2_2") (pintype "passive"))
    )
    (net (code "531") (name "Net-(IC48B-T2)") (class "Default")
      (node (ref "C49") (pin "1") (pinfunction "1_1") (pintype "passive"))
      (node (ref "IC48") (pin "14") (pinfunction "T2_14") (pintype "input"))
      (node (ref "R351") (pin "1") (pinfunction "1_1") (pintype "passive"))
    )
    (net (code "532") (name "Net-(IC50A-+IN)") (class "Default")
      (node (ref "C44") (pin "1") (pinfunction "1_1") (pintype "passive"))
      (node (ref "IC50") (pin "3") (pinfunction "+IN_3") (pintype "input"))
      (node (ref "R277") (pin "1") (pinfunction "1_1") (pintype "passive"))
    )
    (net (code "533") (name "Net-(IC50A--IN)") (class "Default")
      (node (ref "IC50") (pin "2") (pinfunction "-IN_2") (pintype "input"))
      (node (ref "R278") (pin "2") (pinfunction "2_2") (pintype "passive"))
    )
    (net (code "534") (name "Net-(IC50A-OUT)") (class "Default")
      (node (ref "IC50") (pin "1") (pinfunction "OUT_1") (pintype "output"))
      (node (ref "R354") (pin "2") (pinfunction "2_2") (pintype "passive"))
    )
    (net (code "535") (name "Net-(IC50B-+IN)") (class "Default")
      (node (ref "IC50") (pin "5") (pinfunction "+IN_5") (pintype "input"))
      (node (ref "R355") (pin "2") (pinfunction "2_2") (pintype "passive"))
      (node (ref "R356") (pin "2") (pinfunction "2_2") (pintype "passive"))
    )
    (net (code "536") (name "Net-(IC50B--IN)") (class "Default")
      (node (ref "IC50") (pin "6") (pinfunction "-IN_6") (pintype "input"))
      (node (ref "R357") (pin "1") (pinfunction "1_1") (pintype "passive"))
      (node (ref "R358") (pin "2") (pinfunction "2_2") (pintype "passive"))
    )
    (net (code "537") (name "Net-(IC50B-OUT)") (class "Default")
      (node (ref "IC50") (pin "7") (pinfunction "OUT_7") (pintype "output"))
      (node (ref "R297") (pin "1") (pinfunction "1_1") (pintype "passive"))
      (node (ref "R356") (pin "1") (pinfunction "1_1") (pintype "passive"))
    )
    (net (code "538") (name "Net-(IC51A-A)") (class "Default")
      (node (ref "IC51") (pin "10") (pinfunction "A_10") (pintype "input"))
      (node (ref "R366") (pin "1") (pinfunction "1_1") (pintype "passive"))
      (node (ref "X16") (pin "4") (pinfunction "4_4") (pintype "passive"))
      (node (ref "X17") (pin "2") (pinfunction "S_2") (pintype "passive"))
    )
    (net (code "539") (name "Net-(IC51A-B)") (class "Default")
      (node (ref "IC51") (pin "13") (pinfunction "B_13") (pintype "input"))
      (node (ref "R365") (pin "1") (pinfunction "1_1") (pintype "passive"))
      (node (ref "X16") (pin "3") (pinfunction "3_3") (pintype "passive"))
      (node (ref "X17") (pin "3") (pinfunction "S_3") (pintype "passive"))
    )
    (net (code "540") (name "Net-(IC51A-C)") (class "Default")
      (node (ref "IC51") (pin "12") (pinfunction "C_12") (pintype "input"))
      (node (ref "R364") (pin "1") (pinfunction "1_1") (pintype "passive"))
      (node (ref "X16") (pin "2") (pinfunction "2_2") (pintype "passive"))
      (node (ref "X17") (pin "4") (pinfunction "S_4") (pintype "passive"))
    )
    (net (code "541") (name "Net-(IC51A-Q0)") (class "Default")
      (node (ref "IC51") (pin "3") (pinfunction "Q0_3") (pintype "output"))
      (node (ref "IC54") (pin "1") (pinfunction "I1_1") (pintype "input"))
      (node (ref "IC54") (pin "2") (pinfunction "I2_2") (pintype "input"))
      (node (ref "Q42") (pin "1") (pinfunction "G_1") (pintype "passive"))
    )
    (net (code "542") (name "Net-(IC51A-Q1)") (class "Default")
      (node (ref "IC51") (pin "14") (pinfunction "Q1_14") (pintype "output"))
      (node (ref "IC54") (pin "6") (pinfunction "I6_6") (pintype "input"))
    )
    (net (code "543") (name "Net-(IC51A-Q2)") (class "Default")
      (node (ref "IC51") (pin "2") (pinfunction "Q2_2") (pintype "output"))
      (node (ref "IC54") (pin "7") (pinfunction "I7_7") (pintype "input"))
    )
    (net (code "544") (name "Net-(IC51A-Q3)") (class "Default")
      (node (ref "IC51") (pin "15") (pinfunction "Q3_15") (pintype "output"))
      (node (ref "IC54") (pin "5") (pinfunction "I5_5") (pintype "input"))
    )
    (net (code "545") (name "Net-(IC51A-Q4)") (class "Default")
      (node (ref "IC51") (pin "1") (pinfunction "Q4_1") (pintype "output"))
      (node (ref "IC54") (pin "4") (pinfunction "I4_4") (pintype "input"))
    )
    (net (code "546") (name "Net-(IC51A-Q5)") (class "Default")
      (node (ref "IC51") (pin "6") (pinfunction "Q5_6") (pintype "output"))
      (node (ref "IC54") (pin "3") (pinfunction "I3_3") (pintype "input"))
    )
    (net (code "547") (name "Net-(IC53-ADJ)") (class "Default")
      (node (ref "IC53") (pin "1") (pinfunction "ADJ_1") (pintype "input"))
      (node (ref "R362") (pin "1") (pinfunction "1_1") (pintype "passive"))
      (node (ref "R369") (pin "2") (pinfunction "2_2") (pintype "passive"))
      (node (ref "X16") (pin "7") (pinfunction "7_7") (pintype "passive"))
    )
    (net (code "548") (name "Net-(IC53-VI)") (class "Default")
      (node (ref "IC53") (pin "3") (pinfunction "VI_3") (pintype "input"))
      (node (ref "Q39") (pin "2") (pinfunction "C_2") (pintype "passive"))
    )
    (net (code "549") (name "Net-(IC53-VO)") (class "Default")
      (node (ref "IC53") (pin "2") (pinfunction "VO_2") (pintype "passive"))
      (node (ref "R362") (pin "2") (pinfunction "2_2") (pintype "passive"))
    )
    (net (code "550") (name "Net-(IC54-O2)") (class "Default")
      (node (ref "IC54") (pin "15") (pinfunction "O2_15") (pintype "open_collector"))
      (node (ref "R383") (pin "1") (pinfunction "1_1") (pintype "passive"))
    )
    (net (code "551") (name "Net-(IC55A-+IN)") (class "Default")
      (node (ref "IC55") (pin "5") (pinfunction "+IN_5") (pintype "input"))
      (node (ref "R373") (pin "1") (pinfunction "1_1") (pintype "passive"))
      (node (ref "R374") (pin "2") (pinfunction "2_2") (pintype "passive"))
      (node (ref "R375") (pin "2") (pinfunction "2_2") (pintype "passive"))
    )
    (net (code "552") (name "Net-(IC55A--IN)") (class "Default")
      (node (ref "C52") (pin "1") (pinfunction "1_1") (pintype "passive"))
      (node (ref "IC55") (pin "4") (pinfunction "-IN_4") (pintype "input"))
      (node (ref "R372") (pin "1") (pinfunction "1_1") (pintype "passive"))
    )
    (net (code "553") (name "Net-(IC55B-+IN)") (class "Default")
      (node (ref "IC55") (pin "7") (pinfunction "+IN_7") (pintype "input"))
      (node (ref "R370") (pin "1") (pinfunction "1_1") (pintype "passive"))
      (node (ref "R386") (pin "1") (pinfunction "1_1") (pintype "passive"))
    )
    (net (code "554") (name "Net-(IC55B--IN)") (class "Default")
      (node (ref "IC55") (pin "6") (pinfunction "-IN_6") (pintype "input"))
      (node (ref "IC55") (pin "8") (pinfunction "-IN_8") (pintype "input"))
      (node (ref "R369") (pin "1") (pinfunction "1_1") (pintype "passive"))
    )
    (net (code "555") (name "Net-(IC55B-OUT)") (class "Default")
      (node (ref "IC55") (pin "1") (pinfunction "OUT_1") (pintype "open_collector"))
      (node (ref "R371") (pin "2") (pinfunction "2_2") (pintype "passive"))
      (node (ref "R376") (pin "2") (pinfunction "2_2") (pintype "passive"))
    )
    (net (code "556") (name "Net-(IC55C-+IN)") (class "Default")
      (node (ref "C55") (pin "1") (pinfunction "1_1") (pintype "passive"))
      (node (ref "IC55") (pin "9") (pinfunction "+IN_9") (pintype "input"))
      (node (ref "R378") (pin "2") (pinfunction "2_2") (pintype "passive"))
      (node (ref "R386") (pin "2") (pinfunction "2_2") (pintype "passive"))
    )
    (net (code "557") (name "Net-(IC55C-OUT)") (class "Default")
      (node (ref "C56") (pin "2") (pinfunction "2_2") (pintype "passive"))
      (node (ref "IC55") (pin "14") (pinfunction "OUT_14") (pintype "open_collector"))
      (node (ref "R377") (pin "2") (pinfunction "2_2") (pintype "passive"))
    )
    (net (code "558") (name "Net-(IC57-CV)") (class "Default")
      (node (ref "IC57") (pin "5") (pinfunction "CV_5") (pintype "input"))
      (node (ref "R392") (pin "2") (pinfunction "2_2") (pintype "passive"))
    )
    (net (code "559") (name "Net-(IC57-Q)") (class "Default")
      (node (ref "IC57") (pin "3") (pinfunction "Q_3") (pintype "output"))
      (node (ref "IC58") (pin "12") (pinfunction "A_12") (pintype "input"))
      (node (ref "R392") (pin "1") (pinfunction "1_1") (pintype "passive"))
    )
    (net (code "560") (name "Net-(IC58B-B)") (class "Default")
      (node (ref "IC58") (pin "11") (pinfunction "B_11") (pintype "input"))
      (node (ref "IC58") (pin "9") (pinfunction "~{Q}_9") (pintype "output"))
      (node (ref "R398") (pin "2") (pinfunction "2_2") (pintype "passive"))
    )
    (net (code "561") (name "Net-(IC58B-T2)") (class "Default")
      (node (ref "C59") (pin "1") (pinfunction "1_1") (pintype "passive"))
      (node (ref "IC58") (pin "14") (pinfunction "T2_14") (pintype "input"))
      (node (ref "R396") (pin "1") (pinfunction "1_1") (pintype "passive"))
    )
    (net (code "562") (name "Net-(IC60A-+IN)") (class "Default")
      (node (ref "C54") (pin "1") (pinfunction "1_1") (pintype "passive"))
      (node (ref "IC60") (pin "3") (pinfunction "+IN_3") (pintype "input"))
      (node (ref "R367") (pin "1") (pinfunction "1_1") (pintype "passive"))
    )
    (net (code "563") (name "Net-(IC60A--IN)") (class "Default")
      (node (ref "IC60") (pin "2") (pinfunction "-IN_2") (pintype "input"))
      (node (ref "R368") (pin "2") (pinfunction "2_2") (pintype "passive"))
    )
    (net (code "564") (name "Net-(IC60A-OUT)") (class "Default")
      (node (ref "IC60") (pin "1") (pinfunction "OUT_1") (pintype "output"))
      (node (ref "R399") (pin "2") (pinfunction "2_2") (pintype "passive"))
    )
    (net (code "565") (name "Net-(IC60B-+IN)") (class "Default")
      (node (ref "IC60") (pin "5") (pinfunction "+IN_5") (pintype "input"))
      (node (ref "R400") (pin "2") (pinfunction "2_2") (pintype "passive"))
      (node (ref "R404") (pin "2") (pinfunction "2_2") (pintype "passive"))
    )
    (net (code "566") (name "Net-(IC60B--IN)") (class "Default")
      (node (ref "IC60") (pin "6") (pinfunction "-IN_6") (pintype "input"))
      (node (ref "R447") (pin "1") (pinfunction "1_1") (pintype "passive"))
      (node (ref "R448") (pin "2") (pinfunction "2_2") (pintype "passive"))
    )
    (net (code "567") (name "Net-(IC60B-OUT)") (class "Default")
      (node (ref "IC60") (pin "7") (pinfunction "OUT_7") (pintype "output"))
      (node (ref "R387") (pin "1") (pinfunction "1_1") (pintype "passive"))
      (node (ref "R404") (pin "1") (pinfunction "1_1") (pintype "passive"))
    )
    (net (code "568") (name "Net-(IC101A-+IN)") (class "Default")
      (node (ref "C101") (pin "1") (pinfunction "1_1") (pintype "passive"))
      (node (ref "IC101") (pin "3") (pinfunction "+IN_3") (pintype "input"))
      (node (ref "R105") (pin "1") (pinfunction "1_1") (pintype "passive"))
    )
    (net (code "569") (name "Net-(IC101A--IN)") (class "Default")
      (node (ref "IC101") (pin "2") (pinfunction "-IN_2") (pintype "input"))
      (node (ref "R107") (pin "2") (pinfunction "2_2") (pintype "passive"))
    )
    (net (code "570") (name "Net-(IC101A-OUT)") (class "Default")
      (node (ref "IC101") (pin "1") (pinfunction "OUT_1") (pintype "output"))
      (node (ref "R108") (pin "2") (pinfunction "2_2") (pintype "passive"))
    )
    (net (code "571") (name "Net-(IC101B-+IN)") (class "Default")
      (node (ref "IC101") (pin "5") (pinfunction "+IN_5") (pintype "input"))
      (node (ref "R112") (pin "2") (pinfunction "2_2") (pintype "passive"))
      (node (ref "R117") (pin "2") (pinfunction "2_2") (pintype "passive"))
    )
    (net (code "572") (name "Net-(IC101B--IN)") (class "Default")
      (node (ref "IC101") (pin "6") (pinfunction "-IN_6") (pintype "input"))
      (node (ref "R113") (pin "1") (pinfunction "1_1") (pintype "passive"))
      (node (ref "R114") (pin "2") (pinfunction "2_2") (pintype "passive"))
    )
    (net (code "573") (name "Net-(IC101B-OUT)") (class "Default")
      (node (ref "IC101") (pin "7") (pinfunction "OUT_7") (pintype "output"))
      (node (ref "R116") (pin "1") (pinfunction "1_1") (pintype "passive"))
      (node (ref "R117") (pin "1") (pinfunction "1_1") (pintype "passive"))
    )
    (net (code "574") (name "Net-(IC105A-A)") (class "Default")
      (node (ref "IC105") (pin "10") (pinfunction "A_10") (pintype "input"))
      (node (ref "R111") (pin "1") (pinfunction "1_1") (pintype "passive"))
      (node (ref "X101") (pin "4") (pinfunction "4_4") (pintype "passive"))
      (node (ref "X103") (pin "2") (pinfunction "S_2") (pintype "passive"))
    )
    (net (code "575") (name "Net-(IC105A-B)") (class "Default")
      (node (ref "IC105") (pin "13") (pinfunction "B_13") (pintype "input"))
      (node (ref "R110") (pin "1") (pinfunction "1_1") (pintype "passive"))
      (node (ref "X101") (pin "3") (pinfunction "3_3") (pintype "passive"))
      (node (ref "X103") (pin "3") (pinfunction "S_3") (pintype "passive"))
    )
    (net (code "576") (name "Net-(IC105A-C)") (class "Default")
      (node (ref "IC105") (pin "12") (pinfunction "C_12") (pintype "input"))
      (node (ref "R109") (pin "1") (pinfunction "1_1") (pintype "passive"))
      (node (ref "X101") (pin "2") (pinfunction "2_2") (pintype "passive"))
      (node (ref "X103") (pin "4") (pinfunction "S_4") (pintype "passive"))
    )
    (net (code "577") (name "Net-(IC105A-Q0)") (class "Default")
      (node (ref "IC105") (pin "3") (pinfunction "Q0_3") (pintype "output"))
      (node (ref "IC107") (pin "1") (pinfunction "I1_1") (pintype "input"))
      (node (ref "IC107") (pin "2") (pinfunction "I2_2") (pintype "input"))
      (node (ref "Q106") (pin "1") (pinfunction "G_1") (pintype "passive"))
    )
    (net (code "578") (name "Net-(IC105A-Q1)") (class "Default")
      (node (ref "IC105") (pin "14") (pinfunction "Q1_14") (pintype "output"))
      (node (ref "IC107") (pin "6") (pinfunction "I6_6") (pintype "input"))
    )
    (net (code "579") (name "Net-(IC105A-Q2)") (class "Default")
      (node (ref "IC105") (pin "2") (pinfunction "Q2_2") (pintype "output"))
      (node (ref "IC107") (pin "7") (pinfunction "I7_7") (pintype "input"))
    )
    (net (code "580") (name "Net-(IC105A-Q3)") (class "Default")
      (node (ref "IC105") (pin "15") (pinfunction "Q3_15") (pintype "output"))
      (node (ref "IC107") (pin "5") (pinfunction "I5_5") (pintype "input"))
    )
    (net (code "581") (name "Net-(IC105A-Q4)") (class "Default")
      (node (ref "IC105") (pin "1") (pinfunction "Q4_1") (pintype "output"))
      (node (ref "IC107") (pin "4") (pinfunction "I4_4") (pintype "input"))
    )
    (net (code "582") (name "Net-(IC105A-Q5)") (class "Default")
      (node (ref "IC105") (pin "6") (pinfunction "Q5_6") (pintype "output"))
      (node (ref "IC107") (pin "3") (pinfunction "I3_3") (pintype "input"))
    )
    (net (code "583") (name "Net-(IC107-O2)") (class "Default")
      (node (ref "IC107") (pin "15") (pinfunction "O2_15") (pintype "open_collector"))
      (node (ref "R128") (pin "1") (pinfunction "1_1") (pintype "passive"))
    )
    (net (code "584") (name "Net-(IC108A-+IN)") (class "Default")
      (node (ref "IC108") (pin "5") (pinfunction "+IN_5") (pintype "input"))
      (node (ref "R131") (pin "1") (pinfunction "1_1") (pintype "passive"))
      (node (ref "R132") (pin "2") (pinfunction "2_2") (pintype "passive"))
      (node (ref "R133") (pin "2") (pinfunction "2_2") (pintype "passive"))
    )
    (net (code "585") (name "Net-(IC108A--IN)") (class "Default")
      (node (ref "C108") (pin "1") (pinfunction "1_1") (pintype "passive"))
      (node (ref "IC108") (pin "4") (pinfunction "-IN_4") (pintype "input"))
      (node (ref "R130") (pin "1") (pinfunction "1_1") (pintype "passive"))
    )
    (net (code "586") (name "Net-(IC108B-+IN)") (class "Default")
      (node (ref "IC108") (pin "7") (pinfunction "+IN_7") (pintype "input"))
      (node (ref "R121") (pin "1") (pinfunction "1_1") (pintype "passive"))
      (node (ref "R122") (pin "1") (pinfunction "1_1") (pintype "passive"))
    )
    (net (code "587") (name "Net-(IC108B--IN)") (class "Default")
      (node (ref "IC108") (pin "6") (pinfunction "-IN_6") (pintype "input"))
      (node (ref "IC108") (pin "8") (pinfunction "-IN_8") (pintype "input"))
      (node (ref "R120") (pin "1") (pinfunction "1_1") (pintype "passive"))
    )
    (net (code "588") (name "Net-(IC108B-OUT)") (class "Default")
      (node (ref "IC108") (pin "1") (pinfunction "OUT_1") (pintype "open_collector"))
      (node (ref "R124") (pin "2") (pinfunction "2_2") (pintype "passive"))
      (node (ref "R125") (pin "2") (pinfunction "2_2") (pintype "passive"))
    )
    (net (code "589") (name "Net-(IC108C-+IN)") (class "Default")
      (node (ref "C105") (pin "1") (pinfunction "1_1") (pintype "passive"))
      (node (ref "IC108") (pin "9") (pinfunction "+IN_9") (pintype "input"))
      (node (ref "R122") (pin "2") (pinfunction "2_2") (pintype "passive"))
      (node (ref "R123") (pin "2") (pinfunction "2_2") (pintype "passive"))
    )
    (net (code "590") (name "Net-(IC108C-OUT)") (class "Default")
      (node (ref "C106") (pin "2") (pinfunction "2_2") (pintype "passive"))
      (node (ref "IC108") (pin "14") (pinfunction "OUT_14") (pintype "open_collector"))
      (node (ref "R126") (pin "2") (pinfunction "2_2") (pintype "passive"))
    )
    (net (code "591") (name "Net-(IC109-ADJ)") (class "Default")
      (node (ref "IC109") (pin "1") (pinfunction "ADJ_1") (pintype "input"))
      (node (ref "R120") (pin "2") (pinfunction "2_2") (pintype "passive"))
      (node (ref "R134") (pin "1") (pinfunction "1_1") (pintype "passive"))
      (node (ref "X101") (pin "7") (pinfunction "7_7") (pintype "passive"))
    )
    (net (code "592") (name "Net-(IC109-VI)") (class "Default")
      (node (ref "IC109") (pin "3") (pinfunction "VI_3") (pintype "input"))
      (node (ref "Q105") (pin "2") (pinfunction "C_2") (pintype "passive"))
    )
    (net (code "593") (name "Net-(IC109-VO)") (class "Default")
      (node (ref "IC109") (pin "2") (pinfunction "VO_2") (pintype "passive"))
      (node (ref "R134") (pin "2") (pinfunction "2_2") (pintype "passive"))
    )
    (net (code "594") (name "Net-(IC110-CV)") (class "Default")
      (node (ref "IC110") (pin "5") (pinfunction "CV_5") (pintype "input"))
      (node (ref "R144") (pin "2") (pinfunction "2_2") (pintype "passive"))
    )
    (net (code "595") (name "Net-(IC110-Q)") (class "Default")
      (node (ref "IC110") (pin "3") (pinfunction "Q_3") (pintype "output"))
      (node (ref "IC111") (pin "12") (pinfunction "A_12") (pintype "input"))
      (node (ref "R144") (pin "1") (pinfunction "1_1") (pintype "passive"))
    )
    (net (code "596") (name "Net-(IC111B-B)") (class "Default")
      (node (ref "IC111") (pin "11") (pinfunction "B_11") (pintype "input"))
      (node (ref "IC111") (pin "9") (pinfunction "~{Q}_9") (pintype "output"))
      (node (ref "R146") (pin "2") (pinfunction "2_2") (pintype "passive"))
    )
    (net (code "597") (name "Net-(IC111B-T2)") (class "Default")
      (node (ref "C110") (pin "1") (pinfunction "1_1") (pintype "passive"))
      (node (ref "IC111") (pin "14") (pinfunction "T2_14") (pintype "input"))
      (node (ref "R145") (pin "1") (pinfunction "1_1") (pintype "passive"))
    )
    (net (code "598") (name "Net-(IC201A-+IN)") (class "Default")
      (node (ref "C201") (pin "1") (pinfunction "1_1") (pintype "passive"))
      (node (ref "IC201") (pin "3") (pinfunction "+IN_3") (pintype "input"))
      (node (ref "R205") (pin "1") (pinfunction "1_1") (pintype "passive"))
    )
    (net (code "599") (name "Net-(IC201A--IN)") (class "Default")
      (node (ref "IC201") (pin "2") (pinfunction "-IN_2") (pintype "input"))
      (node (ref "R207") (pin "2") (pinfunction "2_2") (pintype "passive"))
    )
    (net (code "600") (name "Net-(IC201A-OUT)") (class "Default")
      (node (ref "IC201") (pin "1") (pinfunction "OUT_1") (pintype "output"))
      (node (ref "R208") (pin "2") (pinfunction "2_2") (pintype "passive"))
    )
    (net (code "601") (name "Net-(IC201B-+IN)") (class "Default")
      (node (ref "IC201") (pin "5") (pinfunction "+IN_5") (pintype "input"))
      (node (ref "R212") (pin "2") (pinfunction "2_2") (pintype "passive"))
      (node (ref "R217") (pin "2") (pinfunction "2_2") (pintype "passive"))
    )
    (net (code "602") (name "Net-(IC201B--IN)") (class "Default")
      (node (ref "IC201") (pin "6") (pinfunction "-IN_6") (pintype "input"))
      (node (ref "R213") (pin "1") (pinfunction "1_1") (pintype "passive"))
      (node (ref "R214") (pin "2") (pinfunction "2_2") (pintype "passive"))
    )
    (net (code "603") (name "Net-(IC201B-OUT)") (class "Default")
      (node (ref "IC201") (pin "7") (pinfunction "OUT_7") (pintype "output"))
      (node (ref "R216") (pin "1") (pinfunction "1_1") (pintype "passive"))
      (node (ref "R217") (pin "1") (pinfunction "1_1") (pintype "passive"))
    )
    (net (code "604") (name "Net-(IC205A-A)") (class "Default")
      (node (ref "IC205") (pin "10") (pinfunction "A_10") (pintype "input"))
      (node (ref "R211") (pin "1") (pinfunction "1_1") (pintype "passive"))
      (node (ref "X201") (pin "4") (pinfunction "4_4") (pintype "passive"))
      (node (ref "X203") (pin "2") (pinfunction "S_2") (pintype "passive"))
    )
    (net (code "605") (name "Net-(IC205A-B)") (class "Default")
      (node (ref "IC205") (pin "13") (pinfunction "B_13") (pintype "input"))
      (node (ref "R210") (pin "1") (pinfunction "1_1") (pintype "passive"))
      (node (ref "X201") (pin "3") (pinfunction "3_3") (pintype "passive"))
      (node (ref "X203") (pin "3") (pinfunction "S_3") (pintype "passive"))
    )
    (net (code "606") (name "Net-(IC205A-C)") (class "Default")
      (node (ref "IC205") (pin "12") (pinfunction "C_12") (pintype "input"))
      (node (ref "R209") (pin "1") (pinfunction "1_1") (pintype "passive"))
      (node (ref "X201") (pin "2") (pinfunction "2_2") (pintype "passive"))
      (node (ref "X203") (pin "4") (pinfunction "S_4") (pintype "passive"))
    )
    (net (code "607") (name "Net-(IC205A-Q0)") (class "Default")
      (node (ref "IC205") (pin "3") (pinfunction "Q0_3") (pintype "output"))
      (node (ref "IC207") (pin "1") (pinfunction "I1_1") (pintype "input"))
      (node (ref "IC207") (pin "2") (pinfunction "I2_2") (pintype "input"))
      (node (ref "Q206") (pin "1") (pinfunction "G_1") (pintype "passive"))
    )
    (net (code "608") (name "Net-(IC205A-Q1)") (class "Default")
      (node (ref "IC205") (pin "14") (pinfunction "Q1_14") (pintype "output"))
      (node (ref "IC207") (pin "6") (pinfunction "I6_6") (pintype "input"))
    )
    (net (code "609") (name "Net-(IC205A-Q2)") (class "Default")
      (node (ref "IC205") (pin "2") (pinfunction "Q2_2") (pintype "output"))
      (node (ref "IC207") (pin "7") (pinfunction "I7_7") (pintype "input"))
    )
    (net (code "610") (name "Net-(IC205A-Q3)") (class "Default")
      (node (ref "IC205") (pin "15") (pinfunction "Q3_15") (pintype "output"))
      (node (ref "IC207") (pin "5") (pinfunction "I5_5") (pintype "input"))
    )
    (net (code "611") (name "Net-(IC205A-Q4)") (class "Default")
      (node (ref "IC205") (pin "1") (pinfunction "Q4_1") (pintype "output"))
      (node (ref "IC207") (pin "4") (pinfunction "I4_4") (pintype "input"))
    )
    (net (code "612") (name "Net-(IC205A-Q5)") (class "Default")
      (node (ref "IC205") (pin "6") (pinfunction "Q5_6") (pintype "output"))
      (node (ref "IC207") (pin "3") (pinfunction "I3_3") (pintype "input"))
    )
    (net (code "613") (name "Net-(IC207-O2)") (class "Default")
      (node (ref "IC207") (pin "15") (pinfunction "O2_15") (pintype "open_collector"))
      (node (ref "R228") (pin "1") (pinfunction "1_1") (pintype "passive"))
    )
    (net (code "614") (name "Net-(IC208A-+IN)") (class "Default")
      (node (ref "IC208") (pin "5") (pinfunction "+IN_5") (pintype "input"))
      (node (ref "R231") (pin "1") (pinfunction "1_1") (pintype "passive"))
      (node (ref "R232") (pin "2") (pinfunction "2_2") (pintype "passive"))
      (node (ref "R233") (pin "2") (pinfunction "2_2") (pintype "passive"))
    )
    (net (code "615") (name "Net-(IC208A--IN)") (class "Default")
      (node (ref "C208") (pin "1") (pinfunction "1_1") (pintype "passive"))
      (node (ref "IC208") (pin "4") (pinfunction "-IN_4") (pintype "input"))
      (node (ref "R230") (pin "1") (pinfunction "1_1") (pintype "passive"))
    )
    (net (code "616") (name "Net-(IC208B-+IN)") (class "Default")
      (node (ref "IC208") (pin "7") (pinfunction "+IN_7") (pintype "input"))
      (node (ref "R221") (pin "1") (pinfunction "1_1") (pintype "passive"))
      (node (ref "R222") (pin "1") (pinfunction "1_1") (pintype "passive"))
    )
    (net (code "617") (name "Net-(IC208B--IN)") (class "Default")
      (node (ref "IC208") (pin "6") (pinfunction "-IN_6") (pintype "input"))
      (node (ref "IC208") (pin "8") (pinfunction "-IN_8") (pintype "input"))
      (node (ref "R220") (pin "1") (pinfunction "1_1") (pintype "passive"))
    )
    (net (code "618") (name "Net-(IC208B-OUT)") (class "Default")
      (node (ref "IC208") (pin "1") (pinfunction "OUT_1") (pintype "open_collector"))
      (node (ref "R224") (pin "2") (pinfunction "2_2") (pintype "passive"))
      (node (ref "R225") (pin "2") (pinfunction "2_2") (pintype "passive"))
    )
    (net (code "619") (name "Net-(IC208C-+IN)") (class "Default")
      (node (ref "C205") (pin "1") (pinfunction "1_1") (pintype "passive"))
      (node (ref "IC208") (pin "9") (pinfunction "+IN_9") (pintype "input"))
      (node (ref "R222") (pin "2") (pinfunction "2_2") (pintype "passive"))
      (node (ref "R223") (pin "2") (pinfunction "2_2") (pintype "passive"))
    )
    (net (code "620") (name "Net-(IC208C-OUT)") (class "Default")
      (node (ref "C206") (pin "2") (pinfunction "2_2") (pintype "passive"))
      (node (ref "IC208") (pin "14") (pinfunction "OUT_14") (pintype "open_collector"))
      (node (ref "R226") (pin "2") (pinfunction "2_2") (pintype "passive"))
    )
    (net (code "621") (name "Net-(IC209-ADJ)") (class "Default")
      (node (ref "IC209") (pin "1") (pinfunction "ADJ_1") (pintype "input"))
      (node (ref "R220") (pin "2") (pinfunction "2_2") (pintype "passive"))
      (node (ref "R234") (pin "1") (pinfunction "1_1") (pintype "passive"))
      (node (ref "X201") (pin "7") (pinfunction "7_7") (pintype "passive"))
    )
    (net (code "622") (name "Net-(IC209-VI)") (class "Default")
      (node (ref "IC209") (pin "3") (pinfunction "VI_3") (pintype "input"))
      (node (ref "Q205") (pin "2") (pinfunction "C_2") (pintype "passive"))
    )
    (net (code "623") (name "Net-(IC209-VO)") (class "Default")
      (node (ref "IC209") (pin "2") (pinfunction "VO_2") (pintype "passive"))
      (node (ref "R234") (pin "2") (pinfunction "2_2") (pintype "passive"))
    )
    (net (code "624") (name "Net-(IC210-CV)") (class "Default")
      (node (ref "IC210") (pin "5") (pinfunction "CV_5") (pintype "input"))
      (node (ref "R244") (pin "2") (pinfunction "2_2") (pintype "passive"))
    )
    (net (code "625") (name "Net-(IC210-Q)") (class "Default")
      (node (ref "IC210") (pin "3") (pinfunction "Q_3") (pintype "output"))
      (node (ref "IC211") (pin "12") (pinfunction "A_12") (pintype "input"))
      (node (ref "R244") (pin "1") (pinfunction "1_1") (pintype "passive"))
    )
    (net (code "626") (name "Net-(IC211B-B)") (class "Default")
      (node (ref "IC211") (pin "11") (pinfunction "B_11") (pintype "input"))
      (node (ref "IC211") (pin "9") (pinfunction "~{Q}_9") (pintype "output"))
      (node (ref "R246") (pin "2") (pinfunction "2_2") (pintype "passive"))
    )
    (net (code "627") (name "Net-(IC211B-T2)") (class "Default")
      (node (ref "C210") (pin "1") (pinfunction "1_1") (pintype "passive"))
      (node (ref "IC211") (pin "14") (pinfunction "T2_14") (pintype "input"))
      (node (ref "R245") (pin "1") (pinfunction "1_1") (pintype "passive"))
    )
    (net (code "628") (name "Net-(IC301A-+IN)") (class "Default")
      (node (ref "C301") (pin "1") (pinfunction "1_1") (pintype "passive"))
      (node (ref "IC301") (pin "3") (pinfunction "+IN_3") (pintype "input"))
      (node (ref "R305") (pin "1") (pinfunction "1_1") (pintype "passive"))
    )
    (net (code "629") (name "Net-(IC301A--IN)") (class "Default")
      (node (ref "IC301") (pin "2") (pinfunction "-IN_2") (pintype "input"))
      (node (ref "R307") (pin "2") (pinfunction "2_2") (pintype "passive"))
    )
    (net (code "630") (name "Net-(IC301A-OUT)") (class "Default")
      (node (ref "IC301") (pin "1") (pinfunction "OUT_1") (pintype "output"))
      (node (ref "R308") (pin "2") (pinfunction "2_2") (pintype "passive"))
    )
    (net (code "631") (name "Net-(IC301B-+IN)") (class "Default")
      (node (ref "IC301") (pin "5") (pinfunction "+IN_5") (pintype "input"))
      (node (ref "R312") (pin "2") (pinfunction "2_2") (pintype "passive"))
      (node (ref "R317") (pin "2") (pinfunction "2_2") (pintype "passive"))
    )
    (net (code "632") (name "Net-(IC301B--IN)") (class "Default")
      (node (ref "IC301") (pin "6") (pinfunction "-IN_6") (pintype "input"))
      (node (ref "R313") (pin "1") (pinfunction "1_1") (pintype "passive"))
      (node (ref "R314") (pin "2") (pinfunction "2_2") (pintype "passive"))
    )
    (net (code "633") (name "Net-(IC301B-OUT)") (class "Default")
      (node (ref "IC301") (pin "7") (pinfunction "OUT_7") (pintype "output"))
      (node (ref "R316") (pin "1") (pinfunction "1_1") (pintype "passive"))
      (node (ref "R317") (pin "1") (pinfunction "1_1") (pintype "passive"))
    )
    (net (code "634") (name "Net-(IC305A-A)") (class "Default")
      (node (ref "IC305") (pin "10") (pinfunction "A_10") (pintype "input"))
      (node (ref "R311") (pin "1") (pinfunction "1_1") (pintype "passive"))
      (node (ref "X301") (pin "4") (pinfunction "4_4") (pintype "passive"))
      (node (ref "X303") (pin "2") (pinfunction "S_2") (pintype "passive"))
    )
    (net (code "635") (name "Net-(IC305A-B)") (class "Default")
      (node (ref "IC305") (pin "13") (pinfunction "B_13") (pintype "input"))
      (node (ref "R310") (pin "1") (pinfunction "1_1") (pintype "passive"))
      (node (ref "X301") (pin "3") (pinfunction "3_3") (pintype "passive"))
      (node (ref "X303") (pin "3") (pinfunction "S_3") (pintype "passive"))
    )
    (net (code "636") (name "Net-(IC305A-C)") (class "Default")
      (node (ref "IC305") (pin "12") (pinfunction "C_12") (pintype "input"))
      (node (ref "R309") (pin "1") (pinfunction "1_1") (pintype "passive"))
      (node (ref "X301") (pin "2") (pinfunction "2_2") (pintype "passive"))
      (node (ref "X303") (pin "4") (pinfunction "S_4") (pintype "passive"))
    )
    (net (code "637") (name "Net-(IC305A-Q0)") (class "Default")
      (node (ref "IC305") (pin "3") (pinfunction "Q0_3") (pintype "output"))
      (node (ref "IC307") (pin "1") (pinfunction "I1_1") (pintype "input"))
      (node (ref "IC307") (pin "2") (pinfunction "I2_2") (pintype "input"))
      (node (ref "Q306") (pin "1") (pinfunction "G_1") (pintype "passive"))
    )
    (net (code "638") (name "Net-(IC305A-Q1)") (class "Default")
      (node (ref "IC305") (pin "14") (pinfunction "Q1_14") (pintype "output"))
      (node (ref "IC307") (pin "6") (pinfunction "I6_6") (pintype "input"))
    )
    (net (code "639") (name "Net-(IC305A-Q2)") (class "Default")
      (node (ref "IC305") (pin "2") (pinfunction "Q2_2") (pintype "output"))
      (node (ref "IC307") (pin "7") (pinfunction "I7_7") (pintype "input"))
    )
    (net (code "640") (name "Net-(IC305A-Q3)") (class "Default")
      (node (ref "IC305") (pin "15") (pinfunction "Q3_15") (pintype "output"))
      (node (ref "IC307") (pin "5") (pinfunction "I5_5") (pintype "input"))
    )
    (net (code "641") (name "Net-(IC305A-Q4)") (class "Default")
      (node (ref "IC305") (pin "1") (pinfunction "Q4_1") (pintype "output"))
      (node (ref "IC307") (pin "4") (pinfunction "I4_4") (pintype "input"))
    )
    (net (code "642") (name "Net-(IC305A-Q5)") (class "Default")
      (node (ref "IC305") (pin "6") (pinfunction "Q5_6") (pintype "output"))
      (node (ref "IC307") (pin "3") (pinfunction "I3_3") (pintype "input"))
    )
    (net (code "643") (name "Net-(IC307-O2)") (class "Default")
      (node (ref "IC307") (pin "15") (pinfunction "O2_15") (pintype "open_collector"))
      (node (ref "R328") (pin "1") (pinfunction "1_1") (pintype "passive"))
    )
    (net (code "644") (name "Net-(IC308A-+IN)") (class "Default")
      (node (ref "IC308") (pin "5") (pinfunction "+IN_5") (pintype "input"))
      (node (ref "R331") (pin "1") (pinfunction "1_1") (pintype "passive"))
      (node (ref "R332") (pin "2") (pinfunction "2_2") (pintype "passive"))
      (node (ref "R333") (pin "2") (pinfunction "2_2") (pintype "passive"))
    )
    (net (code "645") (name "Net-(IC308A--IN)") (class "Default")
      (node (ref "C308") (pin "1") (pinfunction "1_1") (pintype "passive"))
      (node (ref "IC308") (pin "4") (pinfunction "-IN_4") (pintype "input"))
      (node (ref "R330") (pin "1") (pinfunction "1_1") (pintype "passive"))
    )
    (net (code "646") (name "Net-(IC308B-+IN)") (class "Default")
      (node (ref "IC308") (pin "7") (pinfunction "+IN_7") (pintype "input"))
      (node (ref "R321") (pin "1") (pinfunction "1_1") (pintype "passive"))
      (node (ref "R322") (pin "1") (pinfunction "1_1") (pintype "passive"))
    )
    (net (code "647") (name "Net-(IC308B--IN)") (class "Default")
      (node (ref "IC308") (pin "6") (pinfunction "-IN_6") (pintype "input"))
      (node (ref "IC308") (pin "8") (pinfunction "-IN_8") (pintype "input"))
      (node (ref "R320") (pin "1") (pinfunction "1_1") (pintype "passive"))
    )
    (net (code "648") (name "Net-(IC308B-OUT)") (class "Default")
      (node (ref "IC308") (pin "1") (pinfunction "OUT_1") (pintype "open_collector"))
      (node (ref "R324") (pin "2") (pinfunction "2_2") (pintype "passive"))
      (node (ref "R325") (pin "2") (pinfunction "2_2") (pintype "passive"))
    )
    (net (code "649") (name "Net-(IC308C-+IN)") (class "Default")
      (node (ref "C305") (pin "1") (pinfunction "1_1") (pintype "passive"))
      (node (ref "IC308") (pin "9") (pinfunction "+IN_9") (pintype "input"))
      (node (ref "R322") (pin "2") (pinfunction "2_2") (pintype "passive"))
      (node (ref "R323") (pin "2") (pinfunction "2_2") (pintype "passive"))
    )
    (net (code "650") (name "Net-(IC308C-OUT)") (class "Default")
      (node (ref "C306") (pin "2") (pinfunction "2_2") (pintype "passive"))
      (node (ref "IC308") (pin "14") (pinfunction "OUT_14") (pintype "open_collector"))
      (node (ref "R326") (pin "2") (pinfunction "2_2") (pintype "passive"))
    )
    (net (code "651") (name "Net-(IC309-ADJ)") (class "Default")
      (node (ref "IC309") (pin "1") (pinfunction "ADJ_1") (pintype "input"))
      (node (ref "R320") (pin "2") (pinfunction "2_2") (pintype "passive"))
      (node (ref "R334") (pin "1") (pinfunction "1_1") (pintype "passive"))
      (node (ref "X301") (pin "7") (pinfunction "7_7") (pintype "passive"))
    )
    (net (code "652") (name "Net-(IC309-VI)") (class "Default")
      (node (ref "IC309") (pin "3") (pinfunction "VI_3") (pintype "input"))
      (node (ref "Q305") (pin "2") (pinfunction "C_2") (pintype "passive"))
    )
    (net (code "653") (name "Net-(IC309-VO)") (class "Default")
      (node (ref "IC309") (pin "2") (pinfunction "VO_2") (pintype "passive"))
      (node (ref "R334") (pin "2") (pinfunction "2_2") (pintype "passive"))
    )
    (net (code "654") (name "Net-(IC310-CV)") (class "Default")
      (node (ref "IC310") (pin "5") (pinfunction "CV_5") (pintype "input"))
      (node (ref "R344") (pin "2") (pinfunction "2_2") (pintype "passive"))
    )
    (net (code "655") (name "Net-(IC310-Q)") (class "Default")
      (node (ref "IC310") (pin "3") (pinfunction "Q_3") (pintype "output"))
      (node (ref "IC311") (pin "12") (pinfunction "A_12") (pintype "input"))
      (node (ref "R344") (pin "1") (pinfunction "1_1") (pintype "passive"))
    )
    (net (code "656") (name "Net-(IC311B-B)") (class "Default")
      (node (ref "IC311") (pin "11") (pinfunction "B_11") (pintype "input"))
      (node (ref "IC311") (pin "9") (pinfunction "~{Q}_9") (pintype "output"))
      (node (ref "R346") (pin "2") (pinfunction "2_2") (pintype "passive"))
    )
    (net (code "657") (name "Net-(IC311B-T2)") (class "Default")
      (node (ref "C310") (pin "1") (pinfunction "1_1") (pintype "passive"))
      (node (ref "IC311") (pin "14") (pinfunction "T2_14") (pintype "input"))
      (node (ref "R345") (pin "1") (pinfunction "1_1") (pintype "passive"))
    )
    (net (code "658") (name "Net-(IC401A-+IN)") (class "Default")
      (node (ref "C401") (pin "1") (pinfunction "1_1") (pintype "passive"))
      (node (ref "IC401") (pin "3") (pinfunction "+IN_3") (pintype "input"))
      (node (ref "R405") (pin "1") (pinfunction "1_1") (pintype "passive"))
    )
    (net (code "659") (name "Net-(IC401A--IN)") (class "Default")
      (node (ref "IC401") (pin "2") (pinfunction "-IN_2") (pintype "input"))
      (node (ref "R407") (pin "2") (pinfunction "2_2") (pintype "passive"))
    )
    (net (code "660") (name "Net-(IC401A-OUT)") (class "Default")
      (node (ref "IC401") (pin "1") (pinfunction "OUT_1") (pintype "output"))
      (node (ref "R408") (pin "2") (pinfunction "2_2") (pintype "passive"))
    )
    (net (code "661") (name "Net-(IC401B-+IN)") (class "Default")
      (node (ref "IC401") (pin "5") (pinfunction "+IN_5") (pintype "input"))
      (node (ref "R412") (pin "2") (pinfunction "2_2") (pintype "passive"))
      (node (ref "R417") (pin "2") (pinfunction "2_2") (pintype "passive"))
    )
    (net (code "662") (name "Net-(IC401B--IN)") (class "Default")
      (node (ref "IC401") (pin "6") (pinfunction "-IN_6") (pintype "input"))
      (node (ref "R413") (pin "1") (pinfunction "1_1") (pintype "passive"))
      (node (ref "R414") (pin "2") (pinfunction "2_2") (pintype "passive"))
    )
    (net (code "663") (name "Net-(IC401B-OUT)") (class "Default")
      (node (ref "IC401") (pin "7") (pinfunction "OUT_7") (pintype "output"))
      (node (ref "R416") (pin "1") (pinfunction "1_1") (pintype "passive"))
      (node (ref "R417") (pin "1") (pinfunction "1_1") (pintype "passive"))
    )
    (net (code "664") (name "Net-(IC405A-A)") (class "Default")
      (node (ref "IC405") (pin "10") (pinfunction "A_10") (pintype "input"))
      (node (ref "R411") (pin "1") (pinfunction "1_1") (pintype "passive"))
      (node (ref "X401") (pin "4") (pinfunction "4_4") (pintype "passive"))
      (node (ref "X403") (pin "2") (pinfunction "S_2") (pintype "passive"))
    )
    (net (code "665") (name "Net-(IC405A-B)") (class "Default")
      (node (ref "IC405") (pin "13") (pinfunction "B_13") (pintype "input"))
      (node (ref "R410") (pin "1") (pinfunction "1_1") (pintype "passive"))
      (node (ref "X401") (pin "3") (pinfunction "3_3") (pintype "passive"))
      (node (ref "X403") (pin "3") (pinfunction "S_3") (pintype "passive"))
    )
    (net (code "666") (name "Net-(IC405A-C)") (class "Default")
      (node (ref "IC405") (pin "12") (pinfunction "C_12") (pintype "input"))
      (node (ref "R409") (pin "1") (pinfunction "1_1") (pintype "passive"))
      (node (ref "X401") (pin "2") (pinfunction "2_2") (pintype "passive"))
      (node (ref "X403") (pin "4") (pinfunction "S_4") (pintype "passive"))
    )
    (net (code "667") (name "Net-(IC405A-Q0)") (class "Default")
      (node (ref "IC405") (pin "3") (pinfunction "Q0_3") (pintype "output"))
      (node (ref "IC407") (pin "1") (pinfunction "I1_1") (pintype "input"))
      (node (ref "IC407") (pin "2") (pinfunction "I2_2") (pintype "input"))
      (node (ref "Q406") (pin "1") (pinfunction "G_1") (pintype "passive"))
    )
    (net (code "668") (name "Net-(IC405A-Q1)") (class "Default")
      (node (ref "IC405") (pin "14") (pinfunction "Q1_14") (pintype "output"))
      (node (ref "IC407") (pin "6") (pinfunction "I6_6") (pintype "input"))
    )
    (net (code "669") (name "Net-(IC405A-Q2)") (class "Default")
      (node (ref "IC405") (pin "2") (pinfunction "Q2_2") (pintype "output"))
      (node (ref "IC407") (pin "7") (pinfunction "I7_7") (pintype "input"))
    )
    (net (code "670") (name "Net-(IC405A-Q3)") (class "Default")
      (node (ref "IC405") (pin "15") (pinfunction "Q3_15") (pintype "output"))
      (node (ref "IC407") (pin "5") (pinfunction "I5_5") (pintype "input"))
    )
    (net (code "671") (name "Net-(IC405A-Q4)") (class "Default")
      (node (ref "IC405") (pin "1") (pinfunction "Q4_1") (pintype "output"))
      (node (ref "IC407") (pin "4") (pinfunction "I4_4") (pintype "input"))
    )
    (net (code "672") (name "Net-(IC405A-Q5)") (class "Default")
      (node (ref "IC405") (pin "6") (pinfunction "Q5_6") (pintype "output"))
      (node (ref "IC407") (pin "3") (pinfunction "I3_3") (pintype "input"))
    )
    (net (code "673") (name "Net-(IC407-O2)") (class "Default")
      (node (ref "IC407") (pin "15") (pinfunction "O2_15") (pintype "open_collector"))
      (node (ref "R428") (pin "1") (pinfunction "1_1") (pintype "passive"))
    )
    (net (code "674") (name "Net-(IC408A-+IN)") (class "Default")
      (node (ref "IC408") (pin "5") (pinfunction "+IN_5") (pintype "input"))
      (node (ref "R431") (pin "1") (pinfunction "1_1") (pintype "passive"))
      (node (ref "R432") (pin "2") (pinfunction "2_2") (pintype "passive"))
      (node (ref "R433") (pin "2") (pinfunction "2_2") (pintype "passive"))
    )
    (net (code "675") (name "Net-(IC408A--IN)") (class "Default")
      (node (ref "C408") (pin "1") (pinfunction "1_1") (pintype "passive"))
      (node (ref "IC408") (pin "4") (pinfunction "-IN_4") (pintype "input"))
      (node (ref "R430") (pin "1") (pinfunction "1_1") (pintype "passive"))
    )
    (net (code "676") (name "Net-(IC408B-+IN)") (class "Default")
      (node (ref "IC408") (pin "7") (pinfunction "+IN_7") (pintype "input"))
      (node (ref "R421") (pin "1") (pinfunction "1_1") (pintype "passive"))
      (node (ref "R422") (pin "1") (pinfunction "1_1") (pintype "passive"))
    )
    (net (code "677") (name "Net-(IC408B--IN)") (class "Default")
      (node (ref "IC408") (pin "6") (pinfunction "-IN_6") (pintype "input"))
      (node (ref "IC408") (pin "8") (pinfunction "-IN_8") (pintype "input"))
      (node (ref "R420") (pin "1") (pinfunction "1_1") (pintype "passive"))
    )
    (net (code "678") (name "Net-(IC408B-OUT)") (class "Default")
      (node (ref "IC408") (pin "1") (pinfunction "OUT_1") (pintype "open_collector"))
      (node (ref "R424") (pin "2") (pinfunction "2_2") (pintype "passive"))
      (node (ref "R425") (pin "2") (pinfunction "2_2") (pintype "passive"))
    )
    (net (code "679") (name "Net-(IC408C-+IN)") (class "Default")
      (node (ref "C405") (pin "1") (pinfunction "1_1") (pintype "passive"))
      (node (ref "IC408") (pin "9") (pinfunction "+IN_9") (pintype "input"))
      (node (ref "R422") (pin "2") (pinfunction "2_2") (pintype "passive"))
      (node (ref "R423") (pin "2") (pinfunction "2_2") (pintype "passive"))
    )
    (net (code "680") (name "Net-(IC408C-OUT)") (class "Default")
      (node (ref "C406") (pin "2") (pinfunction "2_2") (pintype "passive"))
      (node (ref "IC408") (pin "14") (pinfunction "OUT_14") (pintype "open_collector"))
      (node (ref "R426") (pin "2") (pinfunction "2_2") (pintype "passive"))
    )
    (net (code "681") (name "Net-(IC409-ADJ)") (class "Default")
      (node (ref "IC409") (pin "1") (pinfunction "ADJ_1") (pintype "input"))
      (node (ref "R420") (pin "2") (pinfunction "2_2") (pintype "passive"))
      (node (ref "R434") (pin "1") (pinfunction "1_1") (pintype "passive"))
      (node (ref "X401") (pin "7") (pinfunction "7_7") (pintype "passive"))
    )
    (net (code "682") (name "Net-(IC409-VI)") (class "Default")
      (node (ref "IC409") (pin "3") (pinfunction "VI_3") (pintype "input"))
      (node (ref "Q405") (pin "2") (pinfunction "C_2") (pintype "passive"))
    )
    (net (code "683") (name "Net-(IC409-VO)") (class "Default")
      (node (ref "IC409") (pin "2") (pinfunction "VO_2") (pintype "passive"))
      (node (ref "R434") (pin "2") (pinfunction "2_2") (pintype "passive"))
    )
    (net (code "684") (name "Net-(IC410-CV)") (class "Default")
      (node (ref "IC410") (pin "5") (pinfunction "CV_5") (pintype "input"))
      (node (ref "R444") (pin "2") (pinfunction "2_2") (pintype "passive"))
    )
    (net (code "685") (name "Net-(IC410-Q)") (class "Default")
      (node (ref "IC410") (pin "3") (pinfunction "Q_3") (pintype "output"))
      (node (ref "IC411") (pin "12") (pinfunction "A_12") (pintype "input"))
      (node (ref "R444") (pin "1") (pinfunction "1_1") (pintype "passive"))
    )
    (net (code "686") (name "Net-(IC411B-B)") (class "Default")
      (node (ref "IC411") (pin "11") (pinfunction "B_11") (pintype "input"))
      (node (ref "IC411") (pin "9") (pinfunction "~{Q}_9") (pintype "output"))
      (node (ref "R446") (pin "2") (pinfunction "2_2") (pintype "passive"))
    )
    (net (code "687") (name "Net-(IC411B-T2)") (class "Default")
      (node (ref "C410") (pin "1") (pinfunction "1_1") (pintype "passive"))
      (node (ref "IC411") (pin "14") (pinfunction "T2_14") (pintype "input"))
      (node (ref "R445") (pin "1") (pinfunction "1_1") (pintype "passive"))
    )
    (net (code "688") (name "Net-(IC501A-+IN)") (class "Default")
      (node (ref "C501") (pin "1") (pinfunction "1_1") (pintype "passive"))
      (node (ref "IC501") (pin "3") (pinfunction "+IN_3") (pintype "input"))
      (node (ref "R505") (pin "1") (pinfunction "1_1") (pintype "passive"))
    )
    (net (code "689") (name "Net-(IC501A--IN)") (class "Default")
      (node (ref "IC501") (pin "2") (pinfunction "-IN_2") (pintype "input"))
      (node (ref "R507") (pin "2") (pinfunction "2_2") (pintype "passive"))
    )
    (net (code "690") (name "Net-(IC501A-OUT)") (class "Default")
      (node (ref "IC501") (pin "1") (pinfunction "OUT_1") (pintype "output"))
      (node (ref "R508") (pin "2") (pinfunction "2_2") (pintype "passive"))
    )
    (net (code "691") (name "Net-(IC501B-+IN)") (class "Default")
      (node (ref "IC501") (pin "5") (pinfunction "+IN_5") (pintype "input"))
      (node (ref "R512") (pin "2") (pinfunction "2_2") (pintype "passive"))
      (node (ref "R517") (pin "2") (pinfunction "2_2") (pintype "passive"))
    )
    (net (code "692") (name "Net-(IC501B--IN)") (class "Default")
      (node (ref "IC501") (pin "6") (pinfunction "-IN_6") (pintype "input"))
      (node (ref "R513") (pin "1") (pinfunction "1_1") (pintype "passive"))
      (node (ref "R514") (pin "2") (pinfunction "2_2") (pintype "passive"))
    )
    (net (code "693") (name "Net-(IC501B-OUT)") (class "Default")
      (node (ref "IC501") (pin "7") (pinfunction "OUT_7") (pintype "output"))
      (node (ref "R516") (pin "1") (pinfunction "1_1") (pintype "passive"))
      (node (ref "R517") (pin "1") (pinfunction "1_1") (pintype "passive"))
    )
    (net (code "694") (name "Net-(IC505A-A)") (class "Default")
      (node (ref "IC505") (pin "10") (pinfunction "A_10") (pintype "input"))
      (node (ref "R511") (pin "1") (pinfunction "1_1") (pintype "passive"))
      (node (ref "X501") (pin "4") (pinfunction "4_4") (pintype "passive"))
      (node (ref "X503") (pin "2") (pinfunction "S_2") (pintype "passive"))
    )
    (net (code "695") (name "Net-(IC505A-B)") (class "Default")
      (node (ref "IC505") (pin "13") (pinfunction "B_13") (pintype "input"))
      (node (ref "R510") (pin "1") (pinfunction "1_1") (pintype "passive"))
      (node (ref "X501") (pin "3") (pinfunction "3_3") (pintype "passive"))
      (node (ref "X503") (pin "3") (pinfunction "S_3") (pintype "passive"))
    )
    (net (code "696") (name "Net-(IC505A-C)") (class "Default")
      (node (ref "IC505") (pin "12") (pinfunction "C_12") (pintype "input"))
      (node (ref "R509") (pin "1") (pinfunction "1_1") (pintype "passive"))
      (node (ref "X501") (pin "2") (pinfunction "2_2") (pintype "passive"))
      (node (ref "X503") (pin "4") (pinfunction "S_4") (pintype "passive"))
    )
    (net (code "697") (name "Net-(IC505A-Q0)") (class "Default")
      (node (ref "IC505") (pin "3") (pinfunction "Q0_3") (pintype "output"))
      (node (ref "IC507") (pin "1") (pinfunction "I1_1") (pintype "input"))
      (node (ref "IC507") (pin "2") (pinfunction "I2_2") (pintype "input"))
      (node (ref "Q506") (pin "1") (pinfunction "G_1") (pintype "passive"))
    )
    (net (code "698") (name "Net-(IC505A-Q1)") (class "Default")
      (node (ref "IC505") (pin "14") (pinfunction "Q1_14") (pintype "output"))
      (node (ref "IC507") (pin "6") (pinfunction "I6_6") (pintype "input"))
    )
    (net (code "699") (name "Net-(IC505A-Q2)") (class "Default")
      (node (ref "IC505") (pin "2") (pinfunction "Q2_2") (pintype "output"))
      (node (ref "IC507") (pin "7") (pinfunction "I7_7") (pintype "input"))
    )
    (net (code "700") (name "Net-(IC505A-Q3)") (class "Default")
      (node (ref "IC505") (pin "15") (pinfunction "Q3_15") (pintype "output"))
      (node (ref "IC507") (pin "5") (pinfunction "I5_5") (pintype "input"))
    )
    (net (code "701") (name "Net-(IC505A-Q4)") (class "Default")
      (node (ref "IC505") (pin "1") (pinfunction "Q4_1") (pintype "output"))
      (node (ref "IC507") (pin "4") (pinfunction "I4_4") (pintype "input"))
    )
    (net (code "702") (name "Net-(IC505A-Q5)") (class "Default")
      (node (ref "IC505") (pin "6") (pinfunction "Q5_6") (pintype "output"))
      (node (ref "IC507") (pin "3") (pinfunction "I3_3") (pintype "input"))
    )
    (net (code "703") (name "Net-(IC507-O2)") (class "Default")
      (node (ref "IC507") (pin "15") (pinfunction "O2_15") (pintype "open_collector"))
      (node (ref "R528") (pin "1") (pinfunction "1_1") (pintype "passive"))
    )
    (net (code "704") (name "Net-(IC508A-+IN)") (class "Default")
      (node (ref "IC508") (pin "5") (pinfunction "+IN_5") (pintype "input"))
      (node (ref "R531") (pin "1") (pinfunction "1_1") (pintype "passive"))
      (node (ref "R532") (pin "2") (pinfunction "2_2") (pintype "passive"))
      (node (ref "R533") (pin "2") (pinfunction "2_2") (pintype "passive"))
    )
    (net (code "705") (name "Net-(IC508A--IN)") (class "Default")
      (node (ref "C508") (pin "1") (pinfunction "1_1") (pintype "passive"))
      (node (ref "IC508") (pin "4") (pinfunction "-IN_4") (pintype "input"))
      (node (ref "R530") (pin "1") (pinfunction "1_1") (pintype "passive"))
    )
    (net (code "706") (name "Net-(IC508B-+IN)") (class "Default")
      (node (ref "IC508") (pin "7") (pinfunction "+IN_7") (pintype "input"))
      (node (ref "R521") (pin "1") (pinfunction "1_1") (pintype "passive"))
      (node (ref "R522") (pin "1") (pinfunction "1_1") (pintype "passive"))
    )
    (net (code "707") (name "Net-(IC508B--IN)") (class "Default")
      (node (ref "IC508") (pin "6") (pinfunction "-IN_6") (pintype "input"))
      (node (ref "IC508") (pin "8") (pinfunction "-IN_8") (pintype "input"))
      (node (ref "R520") (pin "1") (pinfunction "1_1") (pintype "passive"))
    )
    (net (code "708") (name "Net-(IC508B-OUT)") (class "Default")
      (node (ref "IC508") (pin "1") (pinfunction "OUT_1") (pintype "open_collector"))
      (node (ref "R524") (pin "2") (pinfunction "2_2") (pintype "passive"))
      (node (ref "R525") (pin "2") (pinfunction "2_2") (pintype "passive"))
    )
    (net (code "709") (name "Net-(IC508C-+IN)") (class "Default")
      (node (ref "C505") (pin "1") (pinfunction "1_1") (pintype "passive"))
      (node (ref "IC508") (pin "9") (pinfunction "+IN_9") (pintype "input"))
      (node (ref "R522") (pin "2") (pinfunction "2_2") (pintype "passive"))
      (node (ref "R523") (pin "2") (pinfunction "2_2") (pintype "passive"))
    )
    (net (code "710") (name "Net-(IC508C-OUT)") (class "Default")
      (node (ref "C506") (pin "2") (pinfunction "2_2") (pintype "passive"))
      (node (ref "IC508") (pin "14") (pinfunction "OUT_14") (pintype "open_collector"))
      (node (ref "R526") (pin "2") (pinfunction "2_2") (pintype "passive"))
    )
    (net (code "711") (name "Net-(IC509-ADJ)") (class "Default")
      (node (ref "IC509") (pin "1") (pinfunction "ADJ_1") (pintype "input"))
      (node (ref "R520") (pin "2") (pinfunction "2_2") (pintype "passive"))
      (node (ref "R534") (pin "1") (pinfunction "1_1") (pintype "passive"))
      (node (ref "X501") (pin "7") (pinfunction "7_7") (pintype "passive"))
    )
    (net (code "712") (name "Net-(IC509-VI)") (class "Default")
      (node (ref "IC509") (pin "3") (pinfunction "VI_3") (pintype "input"))
      (node (ref "Q505") (pin "2") (pinfunction "C_2") (pintype "passive"))
    )
    (net (code "713") (name "Net-(IC509-VO)") (class "Default")
      (node (ref "IC509") (pin "2") (pinfunction "VO_2") (pintype "passive"))
      (node (ref "R534") (pin "2") (pinfunction "2_2") (pintype "passive"))
    )
    (net (code "714") (name "Net-(IC510-CV)") (class "Default")
      (node (ref "IC510") (pin "5") (pinfunction "CV_5") (pintype "input"))
      (node (ref "R544") (pin "2") (pinfunction "2_2") (pintype "passive"))
    )
    (net (code "715") (name "Net-(IC510-Q)") (class "Default")
      (node (ref "IC510") (pin "3") (pinfunction "Q_3") (pintype "output"))
      (node (ref "IC511") (pin "12") (pinfunction "A_12") (pintype "input"))
      (node (ref "R544") (pin "1") (pinfunction "1_1") (pintype "passive"))
    )
    (net (code "716") (name "Net-(IC511B-B)") (class "Default")
      (node (ref "IC511") (pin "11") (pinfunction "B_11") (pintype "input"))
      (node (ref "IC511") (pin "9") (pinfunction "~{Q}_9") (pintype "output"))
      (node (ref "R546") (pin "2") (pinfunction "2_2") (pintype "passive"))
    )
    (net (code "717") (name "Net-(IC511B-T2)") (class "Default")
      (node (ref "C510") (pin "1") (pinfunction "1_1") (pintype "passive"))
      (node (ref "IC511") (pin "14") (pinfunction "T2_14") (pintype "input"))
      (node (ref "R545") (pin "1") (pinfunction "1_1") (pintype "passive"))
    )
    (net (code "718") (name "Net-(IC601A-+IN)") (class "Default")
      (node (ref "C601") (pin "1") (pinfunction "1_1") (pintype "passive"))
      (node (ref "IC601") (pin "3") (pinfunction "+IN_3") (pintype "input"))
      (node (ref "R605") (pin "1") (pinfunction "1_1") (pintype "passive"))
    )
    (net (code "719") (name "Net-(IC601A--IN)") (class "Default")
      (node (ref "IC601") (pin "2") (pinfunction "-IN_2") (pintype "input"))
      (node (ref "R607") (pin "2") (pinfunction "2_2") (pintype "passive"))
    )
    (net (code "720") (name "Net-(IC601A-OUT)") (class "Default")
      (node (ref "IC601") (pin "1") (pinfunction "OUT_1") (pintype "output"))
      (node (ref "R608") (pin "2") (pinfunction "2_2") (pintype "passive"))
    )
    (net (code "721") (name "Net-(IC601B-+IN)") (class "Default")
      (node (ref "IC601") (pin "5") (pinfunction "+IN_5") (pintype "input"))
      (node (ref "R612") (pin "2") (pinfunction "2_2") (pintype "passive"))
      (node (ref "R617") (pin "2") (pinfunction "2_2") (pintype "passive"))
    )
    (net (code "722") (name "Net-(IC601B--IN)") (class "Default")
      (node (ref "IC601") (pin "6") (pinfunction "-IN_6") (pintype "input"))
      (node (ref "R613") (pin "1") (pinfunction "1_1") (pintype "passive"))
      (node (ref "R614") (pin "2") (pinfunction "2_2") (pintype "passive"))
    )
    (net (code "723") (name "Net-(IC601B-OUT)") (class "Default")
      (node (ref "IC601") (pin "7") (pinfunction "OUT_7") (pintype "output"))
      (node (ref "R616") (pin "1") (pinfunction "1_1") (pintype "passive"))
      (node (ref "R617") (pin "1") (pinfunction "1_1") (pintype "passive"))
    )
    (net (code "724") (name "Net-(IC605A-A)") (class "Default")
      (node (ref "IC605") (pin "10") (pinfunction "A_10") (pintype "input"))
      (node (ref "R611") (pin "1") (pinfunction "1_1") (pintype "passive"))
      (node (ref "X601") (pin "4") (pinfunction "4_4") (pintype "passive"))
      (node (ref "X603") (pin "2") (pinfunction "S_2") (pintype "passive"))
    )
    (net (code "725") (name "Net-(IC605A-B)") (class "Default")
      (node (ref "IC605") (pin "13") (pinfunction "B_13") (pintype "input"))
      (node (ref "R610") (pin "1") (pinfunction "1_1") (pintype "passive"))
      (node (ref "X601") (pin "3") (pinfunction "3_3") (pintype "passive"))
      (node (ref "X603") (pin "3") (pinfunction "S_3") (pintype "passive"))
    )
    (net (code "726") (name "Net-(IC605A-C)") (class "Default")
      (node (ref "IC605") (pin "12") (pinfunction "C_12") (pintype "input"))
      (node (ref "R609") (pin "1") (pinfunction "1_1") (pintype "passive"))
      (node (ref "X601") (pin "2") (pinfunction "2_2") (pintype "passive"))
      (node (ref "X603") (pin "4") (pinfunction "S_4") (pintype "passive"))
    )
    (net (code "727") (name "Net-(IC605A-Q0)") (class "Default")
      (node (ref "IC605") (pin "3") (pinfunction "Q0_3") (pintype "output"))
      (node (ref "IC607") (pin "1") (pinfunction "I1_1") (pintype "input"))
      (node (ref "IC607") (pin "2") (pinfunction "I2_2") (pintype "input"))
      (node (ref "Q606") (pin "1") (pinfunction "G_1") (pintype "passive"))
    )
    (net (code "728") (name "Net-(IC605A-Q1)") (class "Default")
      (node (ref "IC605") (pin "14") (pinfunction "Q1_14") (pintype "output"))
      (node (ref "IC607") (pin "6") (pinfunction "I6_6") (pintype "input"))
    )
    (net (code "729") (name "Net-(IC605A-Q2)") (class "Default")
      (node (ref "IC605") (pin "2") (pinfunction "Q2_2") (pintype "output"))
      (node (ref "IC607") (pin "7") (pinfunction "I7_7") (pintype "input"))
    )
    (net (code "730") (name "Net-(IC605A-Q3)") (class "Default")
      (node (ref "IC605") (pin "15") (pinfunction "Q3_15") (pintype "output"))
      (node (ref "IC607") (pin "5") (pinfunction "I5_5") (pintype "input"))
    )
    (net (code "731") (name "Net-(IC605A-Q4)") (class "Default")
      (node (ref "IC605") (pin "1") (pinfunction "Q4_1") (pintype "output"))
      (node (ref "IC607") (pin "4") (pinfunction "I4_4") (pintype "input"))
    )
    (net (code "732") (name "Net-(IC605A-Q5)") (class "Default")
      (node (ref "IC605") (pin "6") (pinfunction "Q5_6") (pintype "output"))
      (node (ref "IC607") (pin "3") (pinfunction "I3_3") (pintype "input"))
    )
    (net (code "733") (name "Net-(IC607-O2)") (class "Default")
      (node (ref "IC607") (pin "15") (pinfunction "O2_15") (pintype "open_collector"))
      (node (ref "R628") (pin "1") (pinfunction "1_1") (pintype "passive"))
    )
    (net (code "734") (name "Net-(IC608A-+IN)") (class "Default")
      (node (ref "IC608") (pin "5") (pinfunction "+IN_5") (pintype "input"))
      (node (ref "R631") (pin "1") (pinfunction "1_1") (pintype "passive"))
      (node (ref "R632") (pin "2") (pinfunction "2_2") (pintype "passive"))
      (node (ref "R633") (pin "2") (pinfunction "2_2") (pintype "passive"))
    )
    (net (code "735") (name "Net-(IC608A--IN)") (class "Default")
      (node (ref "C608") (pin "1") (pinfunction "1_1") (pintype "passive"))
      (node (ref "IC608") (pin "4") (pinfunction "-IN_4") (pintype "input"))
      (node (ref "R630") (pin "1") (pinfunction "1_1") (pintype "passive"))
    )
    (net (code "736") (name "Net-(IC608B-+IN)") (class "Default")
      (node (ref "IC608") (pin "7") (pinfunction "+IN_7") (pintype "input"))
      (node (ref "R621") (pin "1") (pinfunction "1_1") (pintype "passive"))
      (node (ref "R622") (pin "1") (pinfunction "1_1") (pintype "passive"))
    )
    (net (code "737") (name "Net-(IC608B--IN)") (class "Default")
      (node (ref "IC608") (pin "6") (pinfunction "-IN_6") (pintype "input"))
      (node (ref "IC608") (pin "8") (pinfunction "-IN_8") (pintype "input"))
      (node (ref "R620") (pin "1") (pinfunction "1_1") (pintype "passive"))
    )
    (net (code "738") (name "Net-(IC608B-OUT)") (class "Default")
      (node (ref "IC608") (pin "1") (pinfunction "OUT_1") (pintype "open_collector"))
      (node (ref "R624") (pin "2") (pinfunction "2_2") (pintype "passive"))
      (node (ref "R625") (pin "2") (pinfunction "2_2") (pintype "passive"))
    )
    (net (code "739") (name "Net-(IC608C-+IN)") (class "Default")
      (node (ref "C605") (pin "1") (pinfunction "1_1") (pintype "passive"))
      (node (ref "IC608") (pin "9") (pinfunction "+IN_9") (pintype "input"))
      (node (ref "R622") (pin "2") (pinfunction "2_2") (pintype "passive"))
      (node (ref "R623") (pin "2") (pinfunction "2_2") (pintype "passive"))
    )
    (net (code "740") (name "Net-(IC608C-OUT)") (class "Default")
      (node (ref "C606") (pin "2") (pinfunction "2_2") (pintype "passive"))
      (node (ref "IC608") (pin "14") (pinfunction "OUT_14") (pintype "open_collector"))
      (node (ref "R626") (pin "2") (pinfunction "2_2") (pintype "passive"))
    )
    (net (code "741") (name "Net-(IC609-ADJ)") (class "Default")
      (node (ref "IC609") (pin "1") (pinfunction "ADJ_1") (pintype "input"))
      (node (ref "R620") (pin "2") (pinfunction "2_2") (pintype "passive"))
      (node (ref "R634") (pin "1") (pinfunction "1_1") (pintype "passive"))
      (node (ref "X601") (pin "7") (pinfunction "7_7") (pintype "passive"))
    )
    (net (code "742") (name "Net-(IC609-VI)") (class "Default")
      (node (ref "IC609") (pin "3") (pinfunction "VI_3") (pintype "input"))
      (node (ref "Q605") (pin "2") (pinfunction "C_2") (pintype "passive"))
    )
    (net (code "743") (name "Net-(IC609-VO)") (class "Default")
      (node (ref "IC609") (pin "2") (pinfunction "VO_2") (pintype "passive"))
      (node (ref "R634") (pin "2") (pinfunction "2_2") (pintype "passive"))
    )
    (net (code "744") (name "Net-(IC610-CV)") (class "Default")
      (node (ref "IC610") (pin "5") (pinfunction "CV_5") (pintype "input"))
      (node (ref "R644") (pin "2") (pinfunction "2_2") (pintype "passive"))
    )
    (net (code "745") (name "Net-(IC610-Q)") (class "Default")
      (node (ref "IC610") (pin "3") (pinfunction "Q_3") (pintype "output"))
      (node (ref "IC611") (pin "12") (pinfunction "A_12") (pintype "input"))
      (node (ref "R644") (pin "1") (pinfunction "1_1") (pintype "passive"))
    )
    (net (code "746") (name "Net-(IC611B-B)") (class "Default")
      (node (ref "IC611") (pin "11") (pinfunction "B_11") (pintype "input"))
      (node (ref "IC611") (pin "9") (pinfunction "~{Q}_9") (pintype "output"))
      (node (ref "R646") (pin "2") (pinfunction "2_2") (pintype "passive"))
    )
    (net (code "747") (name "Net-(IC611B-T2)") (class "Default")
      (node (ref "C610") (pin "1") (pinfunction "1_1") (pintype "passive"))
      (node (ref "IC611") (pin "14") (pinfunction "T2_14") (pintype "input"))
      (node (ref "R645") (pin "1") (pinfunction "1_1") (pintype "passive"))
    )
    (net (code "748") (name "Net-(JP1-Pad1)") (class "Default")
      (node (ref "JP1") (pin "1") (pinfunction "1_1") (pintype "passive"))
      (node (ref "R37") (pin "2") (pinfunction "2_2") (pintype "passive"))
    )
    (net (code "749") (name "Net-(JP2-Pad3)") (class "Default")
      (node (ref "JP2") (pin "3") (pinfunction "3_3") (pintype "passive"))
      (node (ref "R28") (pin "1") (pinfunction "1_1") (pintype "passive"))
      (node (ref "R29") (pin "1") (pinfunction "1_1") (pintype "passive"))
    )
    (net (code "750") (name "Net-(JP5-Pad2)") (class "Default")
      (node (ref "JP5") (pin "2") (pinfunction "2_2") (pintype "passive"))
      (node (ref "R34") (pin "2") (pinfunction "2_2") (pintype "passive"))
      (node (ref "R35") (pin "2") (pinfunction "2_2") (pintype "passive"))
      (node (ref "SJ1") (pin "2") (pinfunction "2_2") (pintype "passive"))
    )
    (net (code "751") (name "Net-(JP6-Pad1)") (class "Default")
      (node (ref "JP6") (pin "1") (pinfunction "1_1") (pintype "passive"))
      (node (ref "R82") (pin "2") (pinfunction "2_2") (pintype "passive"))
    )
    (net (code "752") (name "Net-(JP7-Pad3)") (class "Default")
      (node (ref "JP7") (pin "3") (pinfunction "3_3") (pintype "passive"))
      (node (ref "R73") (pin "1") (pinfunction "1_1") (pintype "passive"))
      (node (ref "R74") (pin "1") (pinfunction "1_1") (pintype "passive"))
    )
    (net (code "753") (name "Net-(JP10-Pad2)") (class "Default")
      (node (ref "JP10") (pin "2") (pinfunction "2_2") (pintype "passive"))
      (node (ref "R79") (pin "2") (pinfunction "2_2") (pintype "passive"))
      (node (ref "R80") (pin "2") (pinfunction "2_2") (pintype "passive"))
      (node (ref "SJ2") (pin "2") (pinfunction "2_2") (pintype "passive"))
    )
    (net (code "754") (name "Net-(JP11-Pad1)") (class "Default")
      (node (ref "JP11") (pin "1") (pinfunction "1_1") (pintype "passive"))
      (node (ref "R172") (pin "2") (pinfunction "2_2") (pintype "passive"))
    )
    (net (code "755") (name "Net-(JP12-Pad3)") (class "Default")
      (node (ref "JP12") (pin "3") (pinfunction "3_3") (pintype "passive"))
      (node (ref "R163") (pin "1") (pinfunction "1_1") (pintype "passive"))
      (node (ref "R164") (pin "1") (pinfunction "1_1") (pintype "passive"))
    )
    (net (code "756") (name "Net-(JP15-Pad2)") (class "Default")
      (node (ref "JP15") (pin "2") (pinfunction "2_2") (pintype "passive"))
      (node (ref "R169") (pin "2") (pinfunction "2_2") (pintype "passive"))
      (node (ref "R170") (pin "2") (pinfunction "2_2") (pintype "passive"))
      (node (ref "SJ3") (pin "2") (pinfunction "2_2") (pintype "passive"))
    )
    (net (code "757") (name "Net-(JP16-Pad1)") (class "Default")
      (node (ref "JP16") (pin "1") (pinfunction "1_1") (pintype "passive"))
      (node (ref "R262") (pin "2") (pinfunction "2_2") (pintype "passive"))
    )
    (net (code "758") (name "Net-(JP17-Pad3)") (class "Default")
      (node (ref "JP17") (pin "3") (pinfunction "3_3") (pintype "passive"))
      (node (ref "R253") (pin "1") (pinfunction "1_1") (pintype "passive"))
      (node (ref "R254") (pin "1") (pinfunction "1_1") (pintype "passive"))
    )
    (net (code "759") (name "Net-(JP20-Pad2)") (class "Default")
      (node (ref "JP20") (pin "2") (pinfunction "2_2") (pintype "passive"))
      (node (ref "R259") (pin "2") (pinfunction "2_2") (pintype "passive"))
      (node (ref "R260") (pin "2") (pinfunction "2_2") (pintype "passive"))
      (node (ref "SJ4") (pin "2") (pinfunction "2_2") (pintype "passive"))
    )
    (net (code "760") (name "Net-(JP21-Pad1)") (class "Default")
      (node (ref "JP21") (pin "1") (pinfunction "1_1") (pintype "passive"))
      (node (ref "R352") (pin "2") (pinfunction "2_2") (pintype "passive"))
    )
    (net (code "761") (name "Net-(JP22-Pad3)") (class "Default")
      (node (ref "JP22") (pin "3") (pinfunction "3_3") (pintype "passive"))
      (node (ref "R298") (pin "1") (pinfunction "1_1") (pintype "passive"))
      (node (ref "R299") (pin "1") (pinfunction "1_1") (pintype "passive"))
    )
    (net (code "762") (name "Net-(JP25-Pad2)") (class "Default")
      (node (ref "JP25") (pin "2") (pinfunction "2_2") (pintype "passive"))
      (node (ref "R349") (pin "2") (pinfunction "2_2") (pintype "passive"))
      (node (ref "R350") (pin "2") (pinfunction "2_2") (pintype "passive"))
      (node (ref "SJ5") (pin "2") (pinfunction "2_2") (pintype "passive"))
    )
    (net (code "763") (name "Net-(JP26-Pad1)") (class "Default")
      (node (ref "JP26") (pin "1") (pinfunction "1_1") (pintype "passive"))
      (node (ref "R397") (pin "2") (pinfunction "2_2") (pintype "passive"))
    )
    (net (code "764") (name "Net-(JP27-Pad3)") (class "Default")
      (node (ref "JP27") (pin "3") (pinfunction "3_3") (pintype "passive"))
      (node (ref "R388") (pin "1") (pinfunction "1_1") (pintype "passive"))
      (node (ref "R389") (pin "1") (pinfunction "1_1") (pintype "passive"))
    )
    (net (code "765") (name "Net-(JP30-Pad2)") (class "Default")
      (node (ref "JP30") (pin "2") (pinfunction "2_2") (pintype "passive"))
      (node (ref "R394") (pin "2") (pinfunction "2_2") (pintype "passive"))
      (node (ref "R395") (pin "2") (pinfunction "2_2") (pintype "passive"))
      (node (ref "SJ6") (pin "2") (pinfunction "2_2") (pintype "passive"))
    )
    (net (code "766") (name "Net-(JP101-Pad1)") (class "Default")
      (node (ref "JP101") (pin "1") (pinfunction "1_1") (pintype "passive"))
      (node (ref "R119") (pin "2") (pinfunction "2_2") (pintype "passive"))
    )
    (net (code "767") (name "Net-(JP104-Pad2)") (class "Default")
      (node (ref "JP104") (pin "2") (pinfunction "2_2") (pintype "passive"))
      (node (ref "R136") (pin "2") (pinfunction "2_2") (pintype "passive"))
      (node (ref "R137") (pin "2") (pinfunction "2_2") (pintype "passive"))
      (node (ref "SJ101") (pin "2") (pinfunction "2_2") (pintype "passive"))
    )
    (net (code "768") (name "Net-(JP105-Pad3)") (class "Default")
      (node (ref "JP105") (pin "3") (pinfunction "3_3") (pintype "passive"))
      (node (ref "R138") (pin "1") (pinfunction "1_1") (pintype "passive"))
      (node (ref "R139") (pin "1") (pinfunction "1_1") (pintype "passive"))
    )
    (net (code "769") (name "Net-(JP201-Pad1)") (class "Default")
      (node (ref "JP201") (pin "1") (pinfunction "1_1") (pintype "passive"))
      (node (ref "R219") (pin "2") (pinfunction "2_2") (pintype "passive"))
    )
    (net (code "770") (name "Net-(JP204-Pad2)") (class "Default")
      (node (ref "JP204") (pin "2") (pinfunction "2_2") (pintype "passive"))
      (node (ref "R236") (pin "2") (pinfunction "2_2") (pintype "passive"))
      (node (ref "R237") (pin "2") (pinfunction "2_2") (pintype "passive"))
      (node (ref "SJ201") (pin "2") (pinfunction "2_2") (pintype "passive"))
    )
    (net (code "771") (name "Net-(JP205-Pad3)") (class "Default")
      (node (ref "JP205") (pin "3") (pinfunction "3_3") (pintype "passive"))
      (node (ref "R238") (pin "1") (pinfunction "1_1") (pintype "passive"))
      (node (ref "R239") (pin "1") (pinfunction "1_1") (pintype "passive"))
    )
    (net (code "772") (name "Net-(JP301-Pad1)") (class "Default")
      (node (ref "JP301") (pin "1") (pinfunction "1_1") (pintype "passive"))
      (node (ref "R319") (pin "2") (pinfunction "2_2") (pintype "passive"))
    )
    (net (code "773") (name "Net-(JP304-Pad2)") (class "Default")
      (node (ref "JP304") (pin "2") (pinfunction "2_2") (pintype "passive"))
      (node (ref "R336") (pin "2") (pinfunction "2_2") (pintype "passive"))
      (node (ref "R337") (pin "2") (pinfunction "2_2") (pintype "passive"))
      (node (ref "SJ301") (pin "2") (pinfunction "2_2") (pintype "passive"))
    )
    (net (code "774") (name "Net-(JP305-Pad3)") (class "Default")
      (node (ref "JP305") (pin "3") (pinfunction "3_3") (pintype "passive"))
      (node (ref "R338") (pin "1") (pinfunction "1_1") (pintype "passive"))
      (node (ref "R339") (pin "1") (pinfunction "1_1") (pintype "passive"))
    )
    (net (code "775") (name "Net-(JP401-Pad1)") (class "Default")
      (node (ref "JP401") (pin "1") (pinfunction "1_1") (pintype "passive"))
      (node (ref "R419") (pin "2") (pinfunction "2_2") (pintype "passive"))
    )
    (net (code "776") (name "Net-(JP404-Pad2)") (class "Default")
      (node (ref "JP404") (pin "2") (pinfunction "2_2") (pintype "passive"))
      (node (ref "R436") (pin "2") (pinfunction "2_2") (pintype "passive"))
      (node (ref "R437") (pin "2") (pinfunction "2_2") (pintype "passive"))
      (node (ref "SJ401") (pin "2") (pinfunction "2_2") (pintype "passive"))
    )
    (net (code "777") (name "Net-(JP405-Pad3)") (class "Default")
      (node (ref "JP405") (pin "3") (pinfunction "3_3") (pintype "passive"))
      (node (ref "R438") (pin "1") (pinfunction "1_1") (pintype "passive"))
      (node (ref "R439") (pin "1") (pinfunction "1_1") (pintype "passive"))
    )
    (net (code "778") (name "Net-(JP501-Pad1)") (class "Default")
      (node (ref "JP501") (pin "1") (pinfunction "1_1") (pintype "passive"))
      (node (ref "R519") (pin "2") (pinfunction "2_2") (pintype "passive"))
    )
    (net (code "779") (name "Net-(JP504-Pad2)") (class "Default")
      (node (ref "JP504") (pin "2") (pinfunction "2_2") (pintype "passive"))
      (node (ref "R536") (pin "2") (pinfunction "2_2") (pintype "passive"))
      (node (ref "R537") (pin "2") (pinfunction "2_2") (pintype "passive"))
      (node (ref "SJ501") (pin "2") (pinfunction "2_2") (pintype "passive"))
    )
    (net (code "780") (name "Net-(JP505-Pad3)") (class "Default")
      (node (ref "JP505") (pin "3") (pinfunction "3_3") (pintype "passive"))
      (node (ref "R538") (pin "1") (pinfunction "1_1") (pintype "passive"))
      (node (ref "R539") (pin "1") (pinfunction "1_1") (pintype "passive"))
    )
    (net (code "781") (name "Net-(JP601-Pad1)") (class "Default")
      (node (ref "JP601") (pin "1") (pinfunction "1_1") (pintype "passive"))
      (node (ref "R619") (pin "2") (pinfunction "2_2") (pintype "passive"))
    )
    (net (code "782") (name "Net-(JP604-Pad2)") (class "Default")
      (node (ref "JP604") (pin "2") (pinfunction "2_2") (pintype "passive"))
      (node (ref "R636") (pin "2") (pinfunction "2_2") (pintype "passive"))
      (node (ref "R637") (pin "2") (pinfunction "2_2") (pintype "passive"))
      (node (ref "SJ601") (pin "2") (pinfunction "2_2") (pintype "passive"))
    )
    (net (code "783") (name "Net-(JP605-Pad3)") (class "Default")
      (node (ref "JP605") (pin "3") (pinfunction "3_3") (pintype "passive"))
      (node (ref "R638") (pin "1") (pinfunction "1_1") (pintype "passive"))
      (node (ref "R639") (pin "1") (pinfunction "1_1") (pintype "passive"))
    )
    (net (code "784") (name "Net-(LED1-PadA)") (class "Default")
      (node (ref "LED1") (pin "A") (pinfunction "A_A") (pintype "passive"))
      (node (ref "LED2") (pin "A") (pinfunction "A_A") (pintype "passive"))
      (node (ref "LED3") (pin "A") (pinfunction "A_A") (pintype "passive"))
      (node (ref "LED4") (pin "A") (pinfunction "A_A") (pintype "passive"))
      (node (ref "LED6") (pin "A") (pinfunction "A_A") (pintype "passive"))
      (node (ref "R22") (pin "1") (pinfunction "1_1") (pintype "passive"))
    )
    (net (code "785") (name "Net-(LED5-C)") (class "Default")
      (node (ref "LED5") (pin "K") (pinfunction "C_K") (pintype "passive"))
      (node (ref "R21") (pin "1") (pinfunction "1_1") (pintype "passive"))
    )
    (net (code "786") (name "Net-(LED10-PadA)") (class "Default")
      (node (ref "LED10") (pin "A") (pinfunction "A_A") (pintype "passive"))
      (node (ref "LED12") (pin "A") (pinfunction "A_A") (pintype "passive"))
      (node (ref "LED7") (pin "A") (pinfunction "A_A") (pintype "passive"))
      (node (ref "LED8") (pin "A") (pinfunction "A_A") (pintype "passive"))
      (node (ref "LED9") (pin "A") (pinfunction "A_A") (pintype "passive"))
      (node (ref "R67") (pin "1") (pinfunction "1_1") (pintype "passive"))
    )
    (net (code "787") (name "Net-(LED11-C)") (class "Default")
      (node (ref "LED11") (pin "K") (pinfunction "C_K") (pintype "passive"))
      (node (ref "R66") (pin "1") (pinfunction "1_1") (pintype "passive"))
    )
    (net (code "788") (name "Net-(LED13-PadA)") (class "Default")
      (node (ref "LED13") (pin "A") (pinfunction "A_A") (pintype "passive"))
      (node (ref "LED14") (pin "A") (pinfunction "A_A") (pintype "passive"))
      (node (ref "LED15") (pin "A") (pinfunction "A_A") (pintype "passive"))
      (node (ref "LED16") (pin "A") (pinfunction "A_A") (pintype "passive"))
      (node (ref "LED18") (pin "A") (pinfunction "A_A") (pintype "passive"))
      (node (ref "R157") (pin "1") (pinfunction "1_1") (pintype "passive"))
    )
    (net (code "789") (name "Net-(LED17-C)") (class "Default")
      (node (ref "LED17") (pin "K") (pinfunction "C_K") (pintype "passive"))
      (node (ref "R156") (pin "1") (pinfunction "1_1") (pintype "passive"))
    )
    (net (code "790") (name "Net-(LED19-PadA)") (class "Default")
      (node (ref "LED19") (pin "A") (pinfunction "A_A") (pintype "passive"))
      (node (ref "LED20") (pin "A") (pinfunction "A_A") (pintype "passive"))
      (node (ref "LED21") (pin "A") (pinfunction "A_A") (pintype "passive"))
      (node (ref "LED22") (pin "A") (pinfunction "A_A") (pintype "passive"))
      (node (ref "LED24") (pin "A") (pinfunction "A_A") (pintype "passive"))
      (node (ref "R247") (pin "1") (pinfunction "1_1") (pintype "passive"))
    )
    (net (code "791") (name "Net-(LED23-C)") (class "Default")
      (node (ref "LED23") (pin "K") (pinfunction "C_K") (pintype "passive"))
      (node (ref "R204") (pin "1") (pinfunction "1_1") (pintype "passive"))
    )
    (net (code "792") (name "Net-(LED25-PadA)") (class "Default")
      (node (ref "LED25") (pin "A") (pinfunction "A_A") (pintype "passive"))
      (node (ref "LED26") (pin "A") (pinfunction "A_A") (pintype "passive"))
      (node (ref "LED27") (pin "A") (pinfunction "A_A") (pintype "passive"))
      (node (ref "LED28") (pin "A") (pinfunction "A_A") (pintype "passive"))
      (node (ref "LED30") (pin "A") (pinfunction "A_A") (pintype "passive"))
      (node (ref "R292") (pin "1") (pinfunction "1_1") (pintype "passive"))
    )
    (net (code "793") (name "Net-(LED29-C)") (class "Default")
      (node (ref "LED29") (pin "K") (pinfunction "C_K") (pintype "passive"))
      (node (ref "R291") (pin "1") (pinfunction "1_1") (pintype "passive"))
    )
    (net (code "794") (name "Net-(LED31-PadA)") (class "Default")
      (node (ref "LED31") (pin "A") (pinfunction "A_A") (pintype "passive"))
      (node (ref "LED32") (pin "A") (pinfunction "A_A") (pintype "passive"))
      (node (ref "LED33") (pin "A") (pinfunction "A_A") (pintype "passive"))
      (node (ref "LED34") (pin "A") (pinfunction "A_A") (pintype "passive"))
      (node (ref "LED36") (pin "A") (pinfunction "A_A") (pintype "passive"))
      (node (ref "R382") (pin "1") (pinfunction "1_1") (pintype "passive"))
    )
    (net (code "795") (name "Net-(LED35-C)") (class "Default")
      (node (ref "LED35") (pin "K") (pinfunction "C_K") (pintype "passive"))
      (node (ref "R381") (pin "1") (pinfunction "1_1") (pintype "passive"))
    )
    (net (code "796") (name "Net-(LED101-C)") (class "Default")
      (node (ref "LED101") (pin "K") (pinfunction "C_K") (pintype "passive"))
      (node (ref "R143") (pin "1") (pinfunction "1_1") (pintype "passive"))
    )
    (net (code "797") (name "Net-(LED102-PadA)") (class "Default")
      (node (ref "LED102") (pin "A") (pinfunction "A_A") (pintype "passive"))
      (node (ref "LED103") (pin "A") (pinfunction "A_A") (pintype "passive"))
      (node (ref "LED104") (pin "A") (pinfunction "A_A") (pintype "passive"))
      (node (ref "LED105") (pin "A") (pinfunction "A_A") (pintype "passive"))
      (node (ref "LED106") (pin "A") (pinfunction "A_A") (pintype "passive"))
      (node (ref "R142") (pin "1") (pinfunction "1_1") (pintype "passive"))
    )
    (net (code "798") (name "Net-(LED201-C)") (class "Default")
      (node (ref "LED201") (pin "K") (pinfunction "C_K") (pintype "passive"))
      (node (ref "R243") (pin "1") (pinfunction "1_1") (pintype "passive"))
    )
    (net (code "799") (name "Net-(LED202-PadA)") (class "Default")
      (node (ref "LED202") (pin "A") (pinfunction "A_A") (pintype "passive"))
      (node (ref "LED203") (pin "A") (pinfunction "A_A") (pintype "passive"))
      (node (ref "LED204") (pin "A") (pinfunction "A_A") (pintype "passive"))
      (node (ref "LED205") (pin "A") (pinfunction "A_A") (pintype "passive"))
      (node (ref "LED206") (pin "A") (pinfunction "A_A") (pintype "passive"))
      (node (ref "R242") (pin "1") (pinfunction "1_1") (pintype "passive"))
    )
    (net (code "800") (name "Net-(LED301-C)") (class "Default")
      (node (ref "LED301") (pin "K") (pinfunction "C_K") (pintype "passive"))
      (node (ref "R343") (pin "1") (pinfunction "1_1") (pintype "passive"))
    )
    (net (code "801") (name "Net-(LED302-PadA)") (class "Default")
      (node (ref "LED302") (pin "A") (pinfunction "A_A") (pintype "passive"))
      (node (ref "LED303") (pin "A") (pinfunction "A_A") (pintype "passive"))
      (node (ref "LED304") (pin "A") (pinfunction "A_A") (pintype "passive"))
      (node (ref "LED305") (pin "A") (pinfunction "A_A") (pintype "passive"))
      (node (ref "LED306") (pin "A") (pinfunction "A_A") (pintype "passive"))
      (node (ref "R342") (pin "1") (pinfunction "1_1") (pintype "passive"))
    )
    (net (code "802") (name "Net-(LED401-C)") (class "Default")
      (node (ref "LED401") (pin "K") (pinfunction "C_K") (pintype "passive"))
      (node (ref "R443") (pin "1") (pinfunction "1_1") (pintype "passive"))
    )
    (net (code "803") (name "Net-(LED402-PadA)") (class "Default")
      (node (ref "LED402") (pin "A") (pinfunction "A_A") (pintype "passive"))
      (node (ref "LED403") (pin "A") (pinfunction "A_A") (pintype "passive"))
      (node (ref "LED404") (pin "A") (pinfunction "A_A") (pintype "passive"))
      (node (ref "LED405") (pin "A") (pinfunction "A_A") (pintype "passive"))
      (node (ref "LED406") (pin "A") (pinfunction "A_A") (pintype "passive"))
      (node (ref "R442") (pin "1") (pinfunction "1_1") (pintype "passive"))
    )
    (net (code "804") (name "Net-(LED501-C)") (class "Default")
      (node (ref "LED501") (pin "K") (pinfunction "C_K") (pintype "passive"))
      (node (ref "R543") (pin "1") (pinfunction "1_1") (pintype "passive"))
    )
    (net (code "805") (name "Net-(LED502-PadA)") (class "Default")
      (node (ref "LED502") (pin "A") (pinfunction "A_A") (pintype "passive"))
      (node (ref "LED503") (pin "A") (pinfunction "A_A") (pintype "passive"))
      (node (ref "LED504") (pin "A") (pinfunction "A_A") (pintype "passive"))
      (node (ref "LED505") (pin "A") (pinfunction "A_A") (pintype "passive"))
      (node (ref "LED506") (pin "A") (pinfunction "A_A") (pintype "passive"))
      (node (ref "R542") (pin "1") (pinfunction "1_1") (pintype "passive"))
    )
    (net (code "806") (name "Net-(LED601-C)") (class "Default")
      (node (ref "LED601") (pin "K") (pinfunction "C_K") (pintype "passive"))
      (node (ref "R643") (pin "1") (pinfunction "1_1") (pintype "passive"))
    )
    (net (code "807") (name "Net-(LED602-PadA)") (class "Default")
      (node (ref "LED602") (pin "A") (pinfunction "A_A") (pintype "passive"))
      (node (ref "LED603") (pin "A") (pinfunction "A_A") (pintype "passive"))
      (node (ref "LED604") (pin "A") (pinfunction "A_A") (pintype "passive"))
      (node (ref "LED605") (pin "A") (pinfunction "A_A") (pintype "passive"))
      (node (ref "LED606") (pin "A") (pinfunction "A_A") (pintype "passive"))
      (node (ref "R642") (pin "1") (pinfunction "1_1") (pintype "passive"))
    )
    (net (code "808") (name "Net-(Q1-B)") (class "Default")
      (node (ref "Q1") (pin "1") (pinfunction "B_1") (pintype "passive"))
      (node (ref "R23") (pin "2") (pinfunction "2_2") (pintype "passive"))
    )
    (net (code "809") (name "Net-(Q2-B)") (class "Default")
      (node (ref "Q2") (pin "1") (pinfunction "B_1") (pintype "passive"))
      (node (ref "Q2") (pin "2") (pinfunction "C_2") (pintype "passive"))
      (node (ref "Q3") (pin "1") (pinfunction "B_1") (pintype "passive"))
      (node (ref "R19") (pin "1") (pinfunction "1_1") (pintype "passive"))
      (node (ref "R45") (pin "1") (pinfunction "1_1") (pintype "passive"))
      (node (ref "X3") (pin "2") (pinfunction "S_2") (pintype "passive"))
    )
    (net (code "810") (name "Net-(Q2-E)") (class "Default")
      (node (ref "Q2") (pin "3") (pinfunction "E_3") (pintype "passive"))
      (node (ref "R24") (pin "2") (pinfunction "2_2") (pintype "passive"))
    )
    (net (code "811") (name "Net-(Q3-E)") (class "Default")
      (node (ref "Q3") (pin "3") (pinfunction "E_3") (pintype "passive"))
      (node (ref "R25") (pin "2") (pinfunction "2_2") (pintype "passive"))
    )
    (net (code "812") (name "Net-(Q4-B)") (class "Default")
      (node (ref "Q4") (pin "1") (pinfunction "B_1") (pintype "passive"))
      (node (ref "R17") (pin "1") (pinfunction "1_1") (pintype "passive"))
    )
    (net (code "813") (name "Net-(Q5-B)") (class "Default")
      (node (ref "Q5") (pin "1") (pinfunction "B_1") (pintype "passive"))
      (node (ref "R27") (pin "2") (pinfunction "2_2") (pintype "passive"))
    )
    (net (code "814") (name "Net-(Q5-C)") (class "Default")
      (node (ref "Q5") (pin "2") (pinfunction "C_2") (pintype "passive"))
      (node (ref "R20") (pin "2") (pinfunction "2_2") (pintype "passive"))
      (node (ref "R44") (pin "1") (pinfunction "1_1") (pintype "passive"))
    )
    (net (code "815") (name "Net-(Q6-D)") (class "Default")
      (node (ref "Q6") (pin "3") (pinfunction "D_3") (pintype "passive"))
      (node (ref "R28") (pin "2") (pinfunction "2_2") (pintype "passive"))
    )
    (net (code "816") (name "Net-(Q8-B)") (class "Default")
      (node (ref "Q8") (pin "1") (pinfunction "B_1") (pintype "passive"))
      (node (ref "R68") (pin "2") (pinfunction "2_2") (pintype "passive"))
    )
    (net (code "817") (name "Net-(Q9-E)") (class "Default")
      (node (ref "Q9") (pin "3") (pinfunction "E_3") (pintype "passive"))
      (node (ref "R69") (pin "2") (pinfunction "2_2") (pintype "passive"))
    )
    (net (code "818") (name "Net-(Q10-B)") (class "Default")
      (node (ref "Q10") (pin "1") (pinfunction "B_1") (pintype "passive"))
      (node (ref "Q9") (pin "1") (pinfunction "B_1") (pintype "passive"))
      (node (ref "Q9") (pin "2") (pinfunction "C_2") (pintype "passive"))
      (node (ref "R64") (pin "1") (pinfunction "1_1") (pintype "passive"))
      (node (ref "R90") (pin "1") (pinfunction "1_1") (pintype "passive"))
      (node (ref "X6") (pin "2") (pinfunction "S_2") (pintype "passive"))
    )
    (net (code "819") (name "Net-(Q10-E)") (class "Default")
      (node (ref "Q10") (pin "3") (pinfunction "E_3") (pintype "passive"))
      (node (ref "R70") (pin "2") (pinfunction "2_2") (pintype "passive"))
    )
    (net (code "820") (name "Net-(Q11-B)") (class "Default")
      (node (ref "Q11") (pin "1") (pinfunction "B_1") (pintype "passive"))
      (node (ref "R62") (pin "1") (pinfunction "1_1") (pintype "passive"))
    )
    (net (code "821") (name "Net-(Q12-B)") (class "Default")
      (node (ref "Q12") (pin "1") (pinfunction "B_1") (pintype "passive"))
      (node (ref "R72") (pin "2") (pinfunction "2_2") (pintype "passive"))
    )
    (net (code "822") (name "Net-(Q12-C)") (class "Default")
      (node (ref "Q12") (pin "2") (pinfunction "C_2") (pintype "passive"))
      (node (ref "R65") (pin "2") (pinfunction "2_2") (pintype "passive"))
      (node (ref "R89") (pin "1") (pinfunction "1_1") (pintype "passive"))
    )
    (net (code "823") (name "Net-(Q13-D)") (class "Default")
      (node (ref "Q13") (pin "3") (pinfunction "D_3") (pintype "passive"))
      (node (ref "R73") (pin "2") (pinfunction "2_2") (pintype "passive"))
    )
    (net (code "824") (name "Net-(Q15-B)") (class "Default")
      (node (ref "Q15") (pin "1") (pinfunction "B_1") (pintype "passive"))
      (node (ref "R158") (pin "2") (pinfunction "2_2") (pintype "passive"))
    )
    (net (code "825") (name "Net-(Q16-B)") (class "Default")
      (node (ref "Q16") (pin "1") (pinfunction "B_1") (pintype "passive"))
      (node (ref "Q16") (pin "2") (pinfunction "C_2") (pintype "passive"))
      (node (ref "Q17") (pin "1") (pinfunction "B_1") (pintype "passive"))
      (node (ref "R154") (pin "1") (pinfunction "1_1") (pintype "passive"))
      (node (ref "R180") (pin "1") (pinfunction "1_1") (pintype "passive"))
      (node (ref "X9") (pin "2") (pinfunction "S_2") (pintype "passive"))
    )
    (net (code "826") (name "Net-(Q16-E)") (class "Default")
      (node (ref "Q16") (pin "3") (pinfunction "E_3") (pintype "passive"))
      (node (ref "R159") (pin "2") (pinfunction "2_2") (pintype "passive"))
    )
    (net (code "827") (name "Net-(Q17-E)") (class "Default")
      (node (ref "Q17") (pin "3") (pinfunction "E_3") (pintype "passive"))
      (node (ref "R160") (pin "2") (pinfunction "2_2") (pintype "passive"))
    )
    (net (code "828") (name "Net-(Q18-B)") (class "Default")
      (node (ref "Q18") (pin "1") (pinfunction "B_1") (pintype "passive"))
      (node (ref "R152") (pin "1") (pinfunction "1_1") (pintype "passive"))
    )
    (net (code "829") (name "Net-(Q19-B)") (class "Default")
      (node (ref "Q19") (pin "1") (pinfunction "B_1") (pintype "passive"))
      (node (ref "R162") (pin "2") (pinfunction "2_2") (pintype "passive"))
    )
    (net (code "830") (name "Net-(Q19-C)") (class "Default")
      (node (ref "Q19") (pin "2") (pinfunction "C_2") (pintype "passive"))
      (node (ref "R155") (pin "2") (pinfunction "2_2") (pintype "passive"))
      (node (ref "R179") (pin "1") (pinfunction "1_1") (pintype "passive"))
    )
    (net (code "831") (name "Net-(Q20-D)") (class "Default")
      (node (ref "Q20") (pin "3") (pinfunction "D_3") (pintype "passive"))
      (node (ref "R163") (pin "2") (pinfunction "2_2") (pintype "passive"))
    )
    (net (code "832") (name "Net-(Q22-B)") (class "Default")
      (node (ref "Q22") (pin "1") (pinfunction "B_1") (pintype "passive"))
      (node (ref "R248") (pin "2") (pinfunction "2_2") (pintype "passive"))
    )
    (net (code "833") (name "Net-(Q23-B)") (class "Default")
      (node (ref "Q23") (pin "1") (pinfunction "B_1") (pintype "passive"))
      (node (ref "Q23") (pin "2") (pinfunction "C_2") (pintype "passive"))
      (node (ref "Q24") (pin "1") (pinfunction "B_1") (pintype "passive"))
      (node (ref "R199") (pin "1") (pinfunction "1_1") (pintype "passive"))
      (node (ref "R270") (pin "1") (pinfunction "1_1") (pintype "passive"))
      (node (ref "X12") (pin "2") (pinfunction "S_2") (pintype "passive"))
    )
    (net (code "834") (name "Net-(Q23-E)") (class "Default")
      (node (ref "Q23") (pin "3") (pinfunction "E_3") (pintype "passive"))
      (node (ref "R249") (pin "2") (pinfunction "2_2") (pintype "passive"))
    )
    (net (code "835") (name "Net-(Q24-E)") (class "Default")
      (node (ref "Q24") (pin "3") (pinfunction "E_3") (pintype "passive"))
      (node (ref "R250") (pin "2") (pinfunction "2_2") (pintype "passive"))
    )
    (net (code "836") (name "Net-(Q25-B)") (class "Default")
      (node (ref "Q25") (pin "1") (pinfunction "B_1") (pintype "passive"))
      (node (ref "R197") (pin "1") (pinfunction "1_1") (pintype "passive"))
    )
    (net (code "837") (name "Net-(Q26-B)") (class "Default")
      (node (ref "Q26") (pin "1") (pinfunction "B_1") (pintype "passive"))
      (node (ref "R252") (pin "2") (pinfunction "2_2") (pintype "passive"))
    )
    (net (code "838") (name "Net-(Q26-C)") (class "Default")
      (node (ref "Q26") (pin "2") (pinfunction "C_2") (pintype "passive"))
      (node (ref "R200") (pin "2") (pinfunction "2_2") (pintype "passive"))
      (node (ref "R269") (pin "1") (pinfunction "1_1") (pintype "passive"))
    )
    (net (code "839") (name "Net-(Q27-D)") (class "Default")
      (node (ref "Q27") (pin "3") (pinfunction "D_3") (pintype "passive"))
      (node (ref "R253") (pin "2") (pinfunction "2_2") (pintype "passive"))
    )
    (net (code "840") (name "Net-(Q29-B)") (class "Default")
      (node (ref "Q29") (pin "1") (pinfunction "B_1") (pintype "passive"))
      (node (ref "R293") (pin "2") (pinfunction "2_2") (pintype "passive"))
    )
    (net (code "841") (name "Net-(Q30-B)") (class "Default")
      (node (ref "Q30") (pin "1") (pinfunction "B_1") (pintype "passive"))
      (node (ref "Q30") (pin "2") (pinfunction "C_2") (pintype "passive"))
      (node (ref "Q31") (pin "1") (pinfunction "B_1") (pintype "passive"))
      (node (ref "R289") (pin "1") (pinfunction "1_1") (pintype "passive"))
      (node (ref "R360") (pin "1") (pinfunction "1_1") (pintype "passive"))
      (node (ref "X15") (pin "2") (pinfunction "S_2") (pintype "passive"))
    )
    (net (code "842") (name "Net-(Q30-E)") (class "Default")
      (node (ref "Q30") (pin "3") (pinfunction "E_3") (pintype "passive"))
      (node (ref "R294") (pin "2") (pinfunction "2_2") (pintype "passive"))
    )
    (net (code "843") (name "Net-(Q31-E)") (class "Default")
      (node (ref "Q31") (pin "3") (pinfunction "E_3") (pintype "passive"))
      (node (ref "R295") (pin "2") (pinfunction "2_2") (pintype "passive"))
    )
    (net (code "844") (name "Net-(Q32-B)") (class "Default")
      (node (ref "Q32") (pin "1") (pinfunction "B_1") (pintype "passive"))
      (node (ref "R287") (pin "1") (pinfunction "1_1") (pintype "passive"))
    )
    (net (code "845") (name "Net-(Q33-B)") (class "Default")
      (node (ref "Q33") (pin "1") (pinfunction "B_1") (pintype "passive"))
      (node (ref "R297") (pin "2") (pinfunction "2_2") (pintype "passive"))
    )
    (net (code "846") (name "Net-(Q33-C)") (class "Default")
      (node (ref "Q33") (pin "2") (pinfunction "C_2") (pintype "passive"))
      (node (ref "R290") (pin "2") (pinfunction "2_2") (pintype "passive"))
      (node (ref "R359") (pin "1") (pinfunction "1_1") (pintype "passive"))
    )
    (net (code "847") (name "Net-(Q34-D)") (class "Default")
      (node (ref "Q34") (pin "3") (pinfunction "D_3") (pintype "passive"))
      (node (ref "R298") (pin "2") (pinfunction "2_2") (pintype "passive"))
    )
    (net (code "848") (name "Net-(Q36-B)") (class "Default")
      (node (ref "Q36") (pin "1") (pinfunction "B_1") (pintype "passive"))
      (node (ref "R383") (pin "2") (pinfunction "2_2") (pintype "passive"))
    )
    (net (code "849") (name "Net-(Q37-B)") (class "Default")
      (node (ref "Q37") (pin "1") (pinfunction "B_1") (pintype "passive"))
      (node (ref "Q37") (pin "2") (pinfunction "C_2") (pintype "passive"))
      (node (ref "Q38") (pin "1") (pinfunction "B_1") (pintype "passive"))
      (node (ref "R379") (pin "1") (pinfunction "1_1") (pintype "passive"))
      (node (ref "R450") (pin "1") (pinfunction "1_1") (pintype "passive"))
      (node (ref "X18") (pin "2") (pinfunction "S_2") (pintype "passive"))
    )
    (net (code "850") (name "Net-(Q37-E)") (class "Default")
      (node (ref "Q37") (pin "3") (pinfunction "E_3") (pintype "passive"))
      (node (ref "R384") (pin "2") (pinfunction "2_2") (pintype "passive"))
    )
    (net (code "851") (name "Net-(Q38-E)") (class "Default")
      (node (ref "Q38") (pin "3") (pinfunction "E_3") (pintype "passive"))
      (node (ref "R385") (pin "2") (pinfunction "2_2") (pintype "passive"))
    )
    (net (code "852") (name "Net-(Q39-B)") (class "Default")
      (node (ref "Q39") (pin "1") (pinfunction "B_1") (pintype "passive"))
      (node (ref "R377") (pin "1") (pinfunction "1_1") (pintype "passive"))
    )
    (net (code "853") (name "Net-(Q40-B)") (class "Default")
      (node (ref "Q40") (pin "1") (pinfunction "B_1") (pintype "passive"))
      (node (ref "R387") (pin "2") (pinfunction "2_2") (pintype "passive"))
    )
    (net (code "854") (name "Net-(Q40-C)") (class "Default")
      (node (ref "Q40") (pin "2") (pinfunction "C_2") (pintype "passive"))
      (node (ref "R380") (pin "2") (pinfunction "2_2") (pintype "passive"))
      (node (ref "R449") (pin "1") (pinfunction "1_1") (pintype "passive"))
    )
    (net (code "855") (name "Net-(Q41-D)") (class "Default")
      (node (ref "Q41") (pin "3") (pinfunction "D_3") (pintype "passive"))
      (node (ref "R388") (pin "2") (pinfunction "2_2") (pintype "passive"))
    )
    (net (code "856") (name "Net-(Q101-B)") (class "Default")
      (node (ref "Q101") (pin "1") (pinfunction "B_1") (pintype "passive"))
      (node (ref "Q102") (pin "1") (pinfunction "B_1") (pintype "passive"))
      (node (ref "Q102") (pin "2") (pinfunction "C_2") (pintype "passive"))
      (node (ref "R101") (pin "1") (pinfunction "1_1") (pintype "passive"))
      (node (ref "R103") (pin "1") (pinfunction "1_1") (pintype "passive"))
      (node (ref "X102") (pin "2") (pinfunction "S_2") (pintype "passive"))
    )
    (net (code "857") (name "Net-(Q101-E)") (class "Default")
      (node (ref "Q101") (pin "3") (pinfunction "E_3") (pintype "passive"))
      (node (ref "R102") (pin "2") (pinfunction "2_2") (pintype "passive"))
    )
    (net (code "858") (name "Net-(Q102-E)") (class "Default")
      (node (ref "Q102") (pin "3") (pinfunction "E_3") (pintype "passive"))
      (node (ref "R106") (pin "2") (pinfunction "2_2") (pintype "passive"))
    )
    (net (code "859") (name "Net-(Q103-B)") (class "Default")
      (node (ref "Q103") (pin "1") (pinfunction "B_1") (pintype "passive"))
      (node (ref "R116") (pin "2") (pinfunction "2_2") (pintype "passive"))
    )
    (net (code "860") (name "Net-(Q103-C)") (class "Default")
      (node (ref "Q103") (pin "2") (pinfunction "C_2") (pintype "passive"))
      (node (ref "R115") (pin "2") (pinfunction "2_2") (pintype "passive"))
      (node (ref "R118") (pin "1") (pinfunction "1_1") (pintype "passive"))
    )
    (net (code "861") (name "Net-(Q104-B)") (class "Default")
      (node (ref "Q104") (pin "1") (pinfunction "B_1") (pintype "passive"))
      (node (ref "R128") (pin "2") (pinfunction "2_2") (pintype "passive"))
    )
    (net (code "862") (name "Net-(Q105-B)") (class "Default")
      (node (ref "Q105") (pin "1") (pinfunction "B_1") (pintype "passive"))
      (node (ref "R126") (pin "1") (pinfunction "1_1") (pintype "passive"))
    )
    (net (code "863") (name "Net-(Q107-D)") (class "Default")
      (node (ref "Q107") (pin "3") (pinfunction "D_3") (pintype "passive"))
      (node (ref "R138") (pin "2") (pinfunction "2_2") (pintype "passive"))
    )
    (net (code "864") (name "Net-(Q201-B)") (class "Default")
      (node (ref "Q201") (pin "1") (pinfunction "B_1") (pintype "passive"))
      (node (ref "Q202") (pin "1") (pinfunction "B_1") (pintype "passive"))
      (node (ref "Q202") (pin "2") (pinfunction "C_2") (pintype "passive"))
      (node (ref "R201") (pin "1") (pinfunction "1_1") (pintype "passive"))
      (node (ref "R203") (pin "1") (pinfunction "1_1") (pintype "passive"))
      (node (ref "X202") (pin "2") (pinfunction "S_2") (pintype "passive"))
    )
    (net (code "865") (name "Net-(Q201-E)") (class "Default")
      (node (ref "Q201") (pin "3") (pinfunction "E_3") (pintype "passive"))
      (node (ref "R202") (pin "2") (pinfunction "2_2") (pintype "passive"))
    )
    (net (code "866") (name "Net-(Q202-E)") (class "Default")
      (node (ref "Q202") (pin "3") (pinfunction "E_3") (pintype "passive"))
      (node (ref "R206") (pin "2") (pinfunction "2_2") (pintype "passive"))
    )
    (net (code "867") (name "Net-(Q203-B)") (class "Default")
      (node (ref "Q203") (pin "1") (pinfunction "B_1") (pintype "passive"))
      (node (ref "R216") (pin "2") (pinfunction "2_2") (pintype "passive"))
    )
    (net (code "868") (name "Net-(Q203-C)") (class "Default")
      (node (ref "Q203") (pin "2") (pinfunction "C_2") (pintype "passive"))
      (node (ref "R215") (pin "2") (pinfunction "2_2") (pintype "passive"))
      (node (ref "R218") (pin "1") (pinfunction "1_1") (pintype "passive"))
    )
    (net (code "869") (name "Net-(Q204-B)") (class "Default")
      (node (ref "Q204") (pin "1") (pinfunction "B_1") (pintype "passive"))
      (node (ref "R228") (pin "2") (pinfunction "2_2") (pintype "passive"))
    )
    (net (code "870") (name "Net-(Q205-B)") (class "Default")
      (node (ref "Q205") (pin "1") (pinfunction "B_1") (pintype "passive"))
      (node (ref "R226") (pin "1") (pinfunction "1_1") (pintype "passive"))
    )
    (net (code "871") (name "Net-(Q207-D)") (class "Default")
      (node (ref "Q207") (pin "3") (pinfunction "D_3") (pintype "passive"))
      (node (ref "R238") (pin "2") (pinfunction "2_2") (pintype "passive"))
    )
    (net (code "872") (name "Net-(Q301-B)") (class "Default")
      (node (ref "Q301") (pin "1") (pinfunction "B_1") (pintype "passive"))
      (node (ref "Q302") (pin "1") (pinfunction "B_1") (pintype "passive"))
      (node (ref "Q302") (pin "2") (pinfunction "C_2") (pintype "passive"))
      (node (ref "R301") (pin "1") (pinfunction "1_1") (pintype "passive"))
      (node (ref "R303") (pin "1") (pinfunction "1_1") (pintype "passive"))
      (node (ref "X302") (pin "2") (pinfunction "S_2") (pintype "passive"))
    )
    (net (code "873") (name "Net-(Q301-E)") (class "Default")
      (node (ref "Q301") (pin "3") (pinfunction "E_3") (pintype "passive"))
      (node (ref "R302") (pin "2") (pinfunction "2_2") (pintype "passive"))
    )
    (net (code "874") (name "Net-(Q302-E)") (class "Default")
      (node (ref "Q302") (pin "3") (pinfunction "E_3") (pintype "passive"))
      (node (ref "R306") (pin "2") (pinfunction "2_2") (pintype "passive"))
    )
    (net (code "875") (name "Net-(Q303-B)") (class "Default")
      (node (ref "Q303") (pin "1") (pinfunction "B_1") (pintype "passive"))
      (node (ref "R316") (pin "2") (pinfunction "2_2") (pintype "passive"))
    )
    (net (code "876") (name "Net-(Q303-C)") (class "Default")
      (node (ref "Q303") (pin "2") (pinfunction "C_2") (pintype "passive"))
      (node (ref "R315") (pin "2") (pinfunction "2_2") (pintype "passive"))
      (node (ref "R318") (pin "1") (pinfunction "1_1") (pintype "passive"))
    )
    (net (code "877") (name "Net-(Q304-B)") (class "Default")
      (node (ref "Q304") (pin "1") (pinfunction "B_1") (pintype "passive"))
      (node (ref "R328") (pin "2") (pinfunction "2_2") (pintype "passive"))
    )
    (net (code "878") (name "Net-(Q305-B)") (class "Default")
      (node (ref "Q305") (pin "1") (pinfunction "B_1") (pintype "passive"))
      (node (ref "R326") (pin "1") (pinfunction "1_1") (pintype "passive"))
    )
    (net (code "879") (name "Net-(Q307-D)") (class "Default")
      (node (ref "Q307") (pin "3") (pinfunction "D_3") (pintype "passive"))
      (node (ref "R338") (pin "2") (pinfunction "2_2") (pintype "passive"))
    )
    (net (code "880") (name "Net-(Q401-B)") (class "Default")
      (node (ref "Q401") (pin "1") (pinfunction "B_1") (pintype "passive"))
      (node (ref "Q402") (pin "1") (pinfunction "B_1") (pintype "passive"))
      (node (ref "Q402") (pin "2") (pinfunction "C_2") (pintype "passive"))
      (node (ref "R401") (pin "1") (pinfunction "1_1") (pintype "passive"))
      (node (ref "R403") (pin "1") (pinfunction "1_1") (pintype "passive"))
      (node (ref "X402") (pin "2") (pinfunction "S_2") (pintype "passive"))
    )
    (net (code "881") (name "Net-(Q401-E)") (class "Default")
      (node (ref "Q401") (pin "3") (pinfunction "E_3") (pintype "passive"))
      (node (ref "R402") (pin "2") (pinfunction "2_2") (pintype "passive"))
    )
    (net (code "882") (name "Net-(Q402-E)") (class "Default")
      (node (ref "Q402") (pin "3") (pinfunction "E_3") (pintype "passive"))
      (node (ref "R406") (pin "2") (pinfunction "2_2") (pintype "passive"))
    )
    (net (code "883") (name "Net-(Q403-B)") (class "Default")
      (node (ref "Q403") (pin "1") (pinfunction "B_1") (pintype "passive"))
      (node (ref "R416") (pin "2") (pinfunction "2_2") (pintype "passive"))
    )
    (net (code "884") (name "Net-(Q403-C)") (class "Default")
      (node (ref "Q403") (pin "2") (pinfunction "C_2") (pintype "passive"))
      (node (ref "R415") (pin "2") (pinfunction "2_2") (pintype "passive"))
      (node (ref "R418") (pin "1") (pinfunction "1_1") (pintype "passive"))
    )
    (net (code "885") (name "Net-(Q404-B)") (class "Default")
      (node (ref "Q404") (pin "1") (pinfunction "B_1") (pintype "passive"))
      (node (ref "R428") (pin "2") (pinfunction "2_2") (pintype "passive"))
    )
    (net (code "886") (name "Net-(Q405-B)") (class "Default")
      (node (ref "Q405") (pin "1") (pinfunction "B_1") (pintype "passive"))
      (node (ref "R426") (pin "1") (pinfunction "1_1") (pintype "passive"))
    )
    (net (code "887") (name "Net-(Q407-D)") (class "Default")
      (node (ref "Q407") (pin "3") (pinfunction "D_3") (pintype "passive"))
      (node (ref "R438") (pin "2") (pinfunction "2_2") (pintype "passive"))
    )
    (net (code "888") (name "Net-(Q501-B)") (class "Default")
      (node (ref "Q501") (pin "1") (pinfunction "B_1") (pintype "passive"))
      (node (ref "Q502") (pin "1") (pinfunction "B_1") (pintype "passive"))
      (node (ref "Q502") (pin "2") (pinfunction "C_2") (pintype "passive"))
      (node (ref "R501") (pin "1") (pinfunction "1_1") (pintype "passive"))
      (node (ref "R503") (pin "1") (pinfunction "1_1") (pintype "passive"))
      (node (ref "X502") (pin "2") (pinfunction "S_2") (pintype "passive"))
    )
    (net (code "889") (name "Net-(Q501-E)") (class "Default")
      (node (ref "Q501") (pin "3") (pinfunction "E_3") (pintype "passive"))
      (node (ref "R502") (pin "2") (pinfunction "2_2") (pintype "passive"))
    )
    (net (code "890") (name "Net-(Q502-E)") (class "Default")
      (node (ref "Q502") (pin "3") (pinfunction "E_3") (pintype "passive"))
      (node (ref "R506") (pin "2") (pinfunction "2_2") (pintype "passive"))
    )
    (net (code "891") (name "Net-(Q503-B)") (class "Default")
      (node (ref "Q503") (pin "1") (pinfunction "B_1") (pintype "passive"))
      (node (ref "R516") (pin "2") (pinfunction "2_2") (pintype "passive"))
    )
    (net (code "892") (name "Net-(Q503-C)") (class "Default")
      (node (ref "Q503") (pin "2") (pinfunction "C_2") (pintype "passive"))
      (node (ref "R515") (pin "2") (pinfunction "2_2") (pintype "passive"))
      (node (ref "R518") (pin "1") (pinfunction "1_1") (pintype "passive"))
    )
    (net (code "893") (name "Net-(Q504-B)") (class "Default")
      (node (ref "Q504") (pin "1") (pinfunction "B_1") (pintype "passive"))
      (node (ref "R528") (pin "2") (pinfunction "2_2") (pintype "passive"))
    )
    (net (code "894") (name "Net-(Q505-B)") (class "Default")
      (node (ref "Q505") (pin "1") (pinfunction "B_1") (pintype "passive"))
      (node (ref "R526") (pin "1") (pinfunction "1_1") (pintype "passive"))
    )
    (net (code "895") (name "Net-(Q507-D)") (class "Default")
      (node (ref "Q507") (pin "3") (pinfunction "D_3") (pintype "passive"))
      (node (ref "R538") (pin "2") (pinfunction "2_2") (pintype "passive"))
    )
    (net (code "896") (name "Net-(Q601-B)") (class "Default")
      (node (ref "Q601") (pin "1") (pinfunction "B_1") (pintype "passive"))
      (node (ref "Q602") (pin "1") (pinfunction "B_1") (pintype "passive"))
      (node (ref "Q602") (pin "2") (pinfunction "C_2") (pintype "passive"))
      (node (ref "R601") (pin "1") (pinfunction "1_1") (pintype "passive"))
      (node (ref "R603") (pin "1") (pinfunction "1_1") (pintype "passive"))
      (node (ref "X602") (pin "2") (pinfunction "S_2") (pintype "passive"))
    )
    (net (code "897") (name "Net-(Q601-E)") (class "Default")
      (node (ref "Q601") (pin "3") (pinfunction "E_3") (pintype "passive"))
      (node (ref "R602") (pin "2") (pinfunction "2_2") (pintype "passive"))
    )
    (net (code "898") (name "Net-(Q602-E)") (class "Default")
      (node (ref "Q602") (pin "3") (pinfunction "E_3") (pintype "passive"))
      (node (ref "R606") (pin "2") (pinfunction "2_2") (pintype "passive"))
    )
    (net (code "899") (name "Net-(Q603-B)") (class "Default")
      (node (ref "Q603") (pin "1") (pinfunction "B_1") (pintype "passive"))
      (node (ref "R616") (pin "2") (pinfunction "2_2") (pintype "passive"))
    )
    (net (code "900") (name "Net-(Q603-C)") (class "Default")
      (node (ref "Q603") (pin "2") (pinfunction "C_2") (pintype "passive"))
      (node (ref "R615") (pin "2") (pinfunction "2_2") (pintype "passive"))
      (node (ref "R618") (pin "1") (pinfunction "1_1") (pintype "passive"))
    )
    (net (code "901") (name "Net-(Q604-B)") (class "Default")
      (node (ref "Q604") (pin "1") (pinfunction "B_1") (pintype "passive"))
      (node (ref "R628") (pin "2") (pinfunction "2_2") (pintype "passive"))
    )
    (net (code "902") (name "Net-(Q605-B)") (class "Default")
      (node (ref "Q605") (pin "1") (pinfunction "B_1") (pintype "passive"))
      (node (ref "R626") (pin "1") (pinfunction "1_1") (pintype "passive"))
    )
    (net (code "903") (name "Net-(Q607-D)") (class "Default")
      (node (ref "Q607") (pin "3") (pinfunction "D_3") (pintype "passive"))
      (node (ref "R638") (pin "2") (pinfunction "2_2") (pintype "passive"))
    )
    (net (code "904") (name "Net-(R1-Pad2)") (class "Default")
      (node (ref "R1") (pin "2") (pinfunction "2_2") (pintype "passive"))
      (node (ref "R3") (pin "1") (pinfunction "1_1") (pintype "passive"))
    )
    (net (code "905") (name "Net-(R7-Pad2)") (class "Default")
      (node (ref "R7") (pin "2") (pinfunction "2_2") (pintype "passive"))
      (node (ref "X1") (pin "22") (pinfunction "22_22") (pintype "passive"))
    )
    (net (code "906") (name "Net-(R20-Pad1)") (class "Default")
      (node (ref "R20") (pin "1") (pinfunction "1_1") (pintype "passive"))
      (node (ref "X1") (pin "21") (pinfunction "21_21") (pintype "passive"))
    )
    (net (code "907") (name "Net-(R33-Pad2)") (class "Default")
      (node (ref "R33") (pin "2") (pinfunction "2_2") (pintype "passive"))
      (node (ref "X1") (pin "16") (pinfunction "16_16") (pintype "passive"))
    )
    (net (code "908") (name "Net-(R46-Pad2)") (class "Default")
      (node (ref "R46") (pin "2") (pinfunction "2_2") (pintype "passive"))
      (node (ref "R48") (pin "1") (pinfunction "1_1") (pintype "passive"))
    )
    (net (code "909") (name "Net-(R52-Pad2)") (class "Default")
      (node (ref "R52") (pin "2") (pinfunction "2_2") (pintype "passive"))
      (node (ref "X4") (pin "22") (pinfunction "22_22") (pintype "passive"))
    )
    (net (code "910") (name "Net-(R65-Pad1)") (class "Default")
      (node (ref "R65") (pin "1") (pinfunction "1_1") (pintype "passive"))
      (node (ref "X4") (pin "21") (pinfunction "21_21") (pintype "passive"))
    )
    (net (code "911") (name "Net-(R78-Pad2)") (class "Default")
      (node (ref "R78") (pin "2") (pinfunction "2_2") (pintype "passive"))
      (node (ref "X4") (pin "16") (pinfunction "16_16") (pintype "passive"))
    )
    (net (code "912") (name "Net-(R91-Pad2)") (class "Default")
      (node (ref "R91") (pin "2") (pinfunction "2_2") (pintype "passive"))
      (node (ref "R93") (pin "1") (pinfunction "1_1") (pintype "passive"))
    )
    (net (code "913") (name "Net-(R97-Pad2)") (class "Default")
      (node (ref "R97") (pin "2") (pinfunction "2_2") (pintype "passive"))
      (node (ref "X7") (pin "22") (pinfunction "22_22") (pintype "passive"))
    )
    (net (code "914") (name "Net-(R105-Pad2)") (class "Default")
      (node (ref "R105") (pin "2") (pinfunction "2_2") (pintype "passive"))
      (node (ref "X101") (pin "22") (pinfunction "22_22") (pintype "passive"))
    )
    (net (code "915") (name "Net-(R115-Pad1)") (class "Default")
      (node (ref "R115") (pin "1") (pinfunction "1_1") (pintype "passive"))
      (node (ref "X101") (pin "21") (pinfunction "21_21") (pintype "passive"))
    )
    (net (code "916") (name "Net-(R127-Pad2)") (class "Default")
      (node (ref "R127") (pin "2") (pinfunction "2_2") (pintype "passive"))
      (node (ref "R129") (pin "1") (pinfunction "1_1") (pintype "passive"))
    )
    (net (code "917") (name "Net-(R140-Pad2)") (class "Default")
      (node (ref "R140") (pin "2") (pinfunction "2_2") (pintype "passive"))
      (node (ref "X101") (pin "16") (pinfunction "16_16") (pintype "passive"))
    )
    (net (code "918") (name "Net-(R155-Pad1)") (class "Default")
      (node (ref "R155") (pin "1") (pinfunction "1_1") (pintype "passive"))
      (node (ref "X7") (pin "21") (pinfunction "21_21") (pintype "passive"))
    )
    (net (code "919") (name "Net-(R168-Pad2)") (class "Default")
      (node (ref "R168") (pin "2") (pinfunction "2_2") (pintype "passive"))
      (node (ref "X7") (pin "16") (pinfunction "16_16") (pintype "passive"))
    )
    (net (code "920") (name "Net-(R181-Pad2)") (class "Default")
      (node (ref "R181") (pin "2") (pinfunction "2_2") (pintype "passive"))
      (node (ref "R183") (pin "1") (pinfunction "1_1") (pintype "passive"))
    )
    (net (code "921") (name "Net-(R187-Pad2)") (class "Default")
      (node (ref "R187") (pin "2") (pinfunction "2_2") (pintype "passive"))
      (node (ref "X10") (pin "22") (pinfunction "22_22") (pintype "passive"))
    )
    (net (code "922") (name "Net-(R200-Pad1)") (class "Default")
      (node (ref "R200") (pin "1") (pinfunction "1_1") (pintype "passive"))
      (node (ref "X10") (pin "21") (pinfunction "21_21") (pintype "passive"))
    )
    (net (code "923") (name "Net-(R205-Pad2)") (class "Default")
      (node (ref "R205") (pin "2") (pinfunction "2_2") (pintype "passive"))
      (node (ref "X201") (pin "22") (pinfunction "22_22") (pintype "passive"))
    )
    (net (code "924") (name "Net-(R215-Pad1)") (class "Default")
      (node (ref "R215") (pin "1") (pinfunction "1_1") (pintype "passive"))
      (node (ref "X201") (pin "21") (pinfunction "21_21") (pintype "passive"))
    )
    (net (code "925") (name "Net-(R227-Pad2)") (class "Default")
      (node (ref "R227") (pin "2") (pinfunction "2_2") (pintype "passive"))
      (node (ref "R229") (pin "1") (pinfunction "1_1") (pintype "passive"))
    )
    (net (code "926") (name "Net-(R240-Pad2)") (class "Default")
      (node (ref "R240") (pin "2") (pinfunction "2_2") (pintype "passive"))
      (node (ref "X201") (pin "16") (pinfunction "16_16") (pintype "passive"))
    )
    (net (code "927") (name "Net-(R258-Pad2)") (class "Default")
      (node (ref "R258") (pin "2") (pinfunction "2_2") (pintype "passive"))
      (node (ref "X10") (pin "16") (pinfunction "16_16") (pintype "passive"))
    )
    (net (code "928") (name "Net-(R271-Pad2)") (class "Default")
      (node (ref "R271") (pin "2") (pinfunction "2_2") (pintype "passive"))
      (node (ref "R273") (pin "1") (pinfunction "1_1") (pintype "passive"))
    )
    (net (code "929") (name "Net-(R277-Pad2)") (class "Default")
      (node (ref "R277") (pin "2") (pinfunction "2_2") (pintype "passive"))
      (node (ref "X13") (pin "22") (pinfunction "22_22") (pintype "passive"))
    )
    (net (code "930") (name "Net-(R290-Pad1)") (class "Default")
      (node (ref "R290") (pin "1") (pinfunction "1_1") (pintype "passive"))
      (node (ref "X13") (pin "21") (pinfunction "21_21") (pintype "passive"))
    )
    (net (code "931") (name "Net-(R305-Pad2)") (class "Default")
      (node (ref "R305") (pin "2") (pinfunction "2_2") (pintype "passive"))
      (node (ref "X301") (pin "22") (pinfunction "22_22") (pintype "passive"))
    )
    (net (code "932") (name "Net-(R315-Pad1)") (class "Default")
      (node (ref "R315") (pin "1") (pinfunction "1_1") (pintype "passive"))
      (node (ref "X301") (pin "21") (pinfunction "21_21") (pintype "passive"))
    )
    (net (code "933") (name "Net-(R327-Pad2)") (class "Default")
      (node (ref "R327") (pin "2") (pinfunction "2_2") (pintype "passive"))
      (node (ref "R329") (pin "1") (pinfunction "1_1") (pintype "passive"))
    )
    (net (code "934") (name "Net-(R340-Pad2)") (class "Default")
      (node (ref "R340") (pin "2") (pinfunction "2_2") (pintype "passive"))
      (node (ref "X301") (pin "16") (pinfunction "16_16") (pintype "passive"))
    )
    (net (code "935") (name "Net-(R348-Pad2)") (class "Default")
      (node (ref "R348") (pin "2") (pinfunction "2_2") (pintype "passive"))
      (node (ref "X13") (pin "16") (pinfunction "16_16") (pintype "passive"))
    )
    (net (code "936") (name "Net-(R361-Pad2)") (class "Default")
      (node (ref "R361") (pin "2") (pinfunction "2_2") (pintype "passive"))
      (node (ref "R363") (pin "1") (pinfunction "1_1") (pintype "passive"))
    )
    (net (code "937") (name "Net-(R367-Pad2)") (class "Default")
      (node (ref "R367") (pin "2") (pinfunction "2_2") (pintype "passive"))
      (node (ref "X16") (pin "22") (pinfunction "22_22") (pintype "passive"))
    )
    (net (code "938") (name "Net-(R380-Pad1)") (class "Default")
      (node (ref "R380") (pin "1") (pinfunction "1_1") (pintype "passive"))
      (node (ref "X16") (pin "21") (pinfunction "21_21") (pintype "passive"))
    )
    (net (code "939") (name "Net-(R393-Pad2)") (class "Default")
      (node (ref "R393") (pin "2") (pinfunction "2_2") (pintype "passive"))
      (node (ref "X16") (pin "16") (pinfunction "16_16") (pintype "passive"))
    )
    (net (code "940") (name "Net-(R405-Pad2)") (class "Default")
      (node (ref "R405") (pin "2") (pinfunction "2_2") (pintype "passive"))
      (node (ref "X401") (pin "22") (pinfunction "22_22") (pintype "passive"))
    )
    (net (code "941") (name "Net-(R415-Pad1)") (class "Default")
      (node (ref "R415") (pin "1") (pinfunction "1_1") (pintype "passive"))
      (node (ref "X401") (pin "21") (pinfunction "21_21") (pintype "passive"))
    )
    (net (code "942") (name "Net-(R427-Pad2)") (class "Default")
      (node (ref "R427") (pin "2") (pinfunction "2_2") (pintype "passive"))
      (node (ref "R429") (pin "1") (pinfunction "1_1") (pintype "passive"))
    )
    (net (code "943") (name "Net-(R440-Pad2)") (class "Default")
      (node (ref "R440") (pin "2") (pinfunction "2_2") (pintype "passive"))
      (node (ref "X401") (pin "16") (pinfunction "16_16") (pintype "passive"))
    )
    (net (code "944") (name "Net-(R505-Pad2)") (class "Default")
      (node (ref "R505") (pin "2") (pinfunction "2_2") (pintype "passive"))
      (node (ref "X501") (pin "22") (pinfunction "22_22") (pintype "passive"))
    )
    (net (code "945") (name "Net-(R515-Pad1)") (class "Default")
      (node (ref "R515") (pin "1") (pinfunction "1_1") (pintype "passive"))
      (node (ref "X501") (pin "21") (pinfunction "21_21") (pintype "passive"))
    )
    (net (code "946") (name "Net-(R527-Pad2)") (class "Default")
      (node (ref "R527") (pin "2") (pinfunction "2_2") (pintype "passive"))
      (node (ref "R529") (pin "1") (pinfunction "1_1") (pintype "passive"))
    )
    (net (code "947") (name "Net-(R540-Pad2)") (class "Default")
      (node (ref "R540") (pin "2") (pinfunction "2_2") (pintype "passive"))
      (node (ref "X501") (pin "16") (pinfunction "16_16") (pintype "passive"))
    )
    (net (code "948") (name "Net-(R605-Pad2)") (class "Default")
      (node (ref "R605") (pin "2") (pinfunction "2_2") (pintype "passive"))
      (node (ref "X601") (pin "22") (pinfunction "22_22") (pintype "passive"))
    )
    (net (code "949") (name "Net-(R615-Pad1)") (class "Default")
      (node (ref "R615") (pin "1") (pinfunction "1_1") (pintype "passive"))
      (node (ref "X601") (pin "21") (pinfunction "21_21") (pintype "passive"))
    )
    (net (code "950") (name "Net-(R627-Pad2)") (class "Default")
      (node (ref "R627") (pin "2") (pinfunction "2_2") (pintype "passive"))
      (node (ref "R629") (pin "1") (pinfunction "1_1") (pintype "passive"))
    )
    (net (code "951") (name "Net-(R640-Pad2)") (class "Default")
      (node (ref "R640") (pin "2") (pinfunction "2_2") (pintype "passive"))
      (node (ref "X601") (pin "16") (pinfunction "16_16") (pintype "passive"))
    )
    (net (code "952") (name "VCC") (class "Default")
      (node (ref "6V") (pin "TP") (pinfunction "PP_TP") (pintype "input"))
      (node (ref "6V1") (pin "TP") (pinfunction "PP_TP") (pintype "input"))
      (node (ref "6V2") (pin "TP") (pinfunction "PP_TP") (pintype "input"))
      (node (ref "6V201") (pin "TP") (pinfunction "PP_TP") (pintype "input"))
      (node (ref "6V3") (pin "TP") (pinfunction "PP_TP") (pintype "input"))
      (node (ref "6V301") (pin "TP") (pinfunction "PP_TP") (pintype "input"))
      (node (ref "6V4") (pin "TP") (pinfunction "PP_TP") (pintype "input"))
      (node (ref "6V401") (pin "TP") (pinfunction "PP_TP") (pintype "input"))
      (node (ref "6V5") (pin "TP") (pinfunction "PP_TP") (pintype "input"))
      (node (ref "6V501") (pin "TP") (pinfunction "PP_TP") (pintype "input"))
      (node (ref "6V6") (pin "TP") (pinfunction "PP_TP") (pintype "input"))
      (node (ref "6V601") (pin "TP") (pinfunction "PP_TP") (pintype "input"))
      (node (ref "C104") (pin "1") (pinfunction "1_1") (pintype "passive"))
      (node (ref "C13") (pin "1") (pinfunction "1_1") (pintype "passive"))
      (node (ref "C204") (pin "1") (pinfunction "1_1") (pintype "passive"))
      (node (ref "C23") (pin "1") (pinfunction "1_1") (pintype "passive"))
      (node (ref "C3") (pin "1") (pinfunction "1_1") (pintype "passive"))
      (node (ref "C304") (pin "1") (pinfunction "1_1") (pintype "passive"))
      (node (ref "C33") (pin "1") (pinfunction "1_1") (pintype "passive"))
      (node (ref "C404") (pin "1") (pinfunction "1_1") (pintype "passive"))
      (node (ref "C43") (pin "1") (pinfunction "1_1") (pintype "passive"))
      (node (ref "C504") (pin "1") (pinfunction "1_1") (pintype "passive"))
      (node (ref "C53") (pin "1") (pinfunction "1_1") (pintype "passive"))
      (node (ref "C604") (pin "1") (pinfunction "1_1") (pintype "passive"))
      (node (ref "IC10") (pin "8") (pinfunction "V+_8") (pintype "power_in"))
      (node (ref "IC101") (pin "8") (pinfunction "V+_8") (pintype "power_in"))
      (node (ref "IC102") (pin "1") (pinfunction "OUT_1") (pintype "passive"))
      (node (ref "IC103") (pin "OUT") (pinfunction "OUT_OUT") (pintype "passive"))
      (node (ref "IC108") (pin "3") (pinfunction "V+_3") (pintype "power_in"))
      (node (ref "IC12") (pin "OUT") (pinfunction "OUT_OUT") (pintype "passive"))
      (node (ref "IC15") (pin "3") (pinfunction "V+_3") (pintype "power_in"))
      (node (ref "IC16") (pin "1") (pinfunction "OUT_1") (pintype "passive"))
      (node (ref "IC2") (pin "OUT") (pinfunction "OUT_OUT") (pintype "passive"))
      (node (ref "IC20") (pin "8") (pinfunction "V+_8") (pintype "power_in"))
      (node (ref "IC201") (pin "8") (pinfunction "V+_8") (pintype "power_in"))
      (node (ref "IC202") (pin "1") (pinfunction "OUT_1") (pintype "passive"))
      (node (ref "IC203") (pin "OUT") (pinfunction "OUT_OUT") (pintype "passive"))
      (node (ref "IC208") (pin "3") (pinfunction "V+_3") (pintype "power_in"))
      (node (ref "IC22") (pin "OUT") (pinfunction "OUT_OUT") (pintype "passive"))
      (node (ref "IC25") (pin "3") (pinfunction "V+_3") (pintype "power_in"))
      (node (ref "IC26") (pin "1") (pinfunction "OUT_1") (pintype "passive"))
      (node (ref "IC30") (pin "8") (pinfunction "V+_8") (pintype "power_in"))
      (node (ref "IC301") (pin "8") (pinfunction "V+_8") (pintype "power_in"))
      (node (ref "IC302") (pin "1") (pinfunction "OUT_1") (pintype "passive"))
      (node (ref "IC303") (pin "OUT") (pinfunction "OUT_OUT") (pintype "passive"))
      (node (ref "IC308") (pin "3") (pinfunction "V+_3") (pintype "power_in"))
      (node (ref "IC32") (pin "OUT") (pinfunction "OUT_OUT") (pintype "passive"))
      (node (ref "IC35") (pin "3") (pinfunction "V+_3") (pintype "power_in"))
      (node (ref "IC36") (pin "1") (pinfunction "OUT_1") (pintype "passive"))
      (node (ref "IC40") (pin "8") (pinfunction "V+_8") (pintype "power_in"))
      (node (ref "IC401") (pin "8") (pinfunction "V+_8") (pintype "power_in"))
      (node (ref "IC402") (pin "1") (pinfunction "OUT_1") (pintype "passive"))
      (node (ref "IC403") (pin "OUT") (pinfunction "OUT_OUT") (pintype "passive"))
      (node (ref "IC408") (pin "3") (pinfunction "V+_3") (pintype "power_in"))
      (node (ref "IC42") (pin "OUT") (pinfunction "OUT_OUT") (pintype "passive"))
      (node (ref "IC45") (pin "3") (pinfunction "V+_3") (pintype "power_in"))
      (node (ref "IC46") (pin "1") (pinfunction "OUT_1") (pintype "passive"))
      (node (ref "IC5") (pin "3") (pinfunction "V+_3") (pintype "power_in"))
      (node (ref "IC50") (pin "8") (pinfunction "V+_8") (pintype "power_in"))
      (node (ref "IC501") (pin "8") (pinfunction "V+_8") (pintype "power_in"))
      (node (ref "IC502") (pin "1") (pinfunction "OUT_1") (pintype "passive"))
      (node (ref "IC503") (pin "OUT") (pinfunction "OUT_OUT") (pintype "passive"))
      (node (ref "IC508") (pin "3") (pinfunction "V+_3") (pintype "power_in"))
      (node (ref "IC52") (pin "OUT") (pinfunction "OUT_OUT") (pintype "passive"))
      (node (ref "IC55") (pin "3") (pinfunction "V+_3") (pintype "power_in"))
      (node (ref "IC56") (pin "1") (pinfunction "OUT_1") (pintype "passive"))
      (node (ref "IC6") (pin "1") (pinfunction "OUT_1") (pintype "passive"))
      (node (ref "IC60") (pin "8") (pinfunction "V+_8") (pintype "power_in"))
      (node (ref "IC601") (pin "8") (pinfunction "V+_8") (pintype "power_in"))
      (node (ref "IC602") (pin "1") (pinfunction "OUT_1") (pintype "passive"))
      (node (ref "IC603") (pin "OUT") (pinfunction "OUT_OUT") (pintype "passive"))
      (node (ref "IC608") (pin "3") (pinfunction "V+_3") (pintype "power_in"))
      (node (ref "R10") (pin "2") (pinfunction "2_2") (pintype "passive"))
      (node (ref "R100") (pin "2") (pinfunction "2_2") (pintype "passive"))
      (node (ref "R113") (pin "2") (pinfunction "2_2") (pintype "passive"))
      (node (ref "R121") (pin "2") (pinfunction "2_2") (pintype "passive"))
      (node (ref "R124") (pin "1") (pinfunction "1_1") (pintype "passive"))
      (node (ref "R13") (pin "2") (pinfunction "2_2") (pintype "passive"))
      (node (ref "R131") (pin "2") (pinfunction "2_2") (pintype "passive"))
      (node (ref "R142") (pin "2") (pinfunction "2_2") (pintype "passive"))
      (node (ref "R148") (pin "2") (pinfunction "2_2") (pintype "passive"))
      (node (ref "R151") (pin "1") (pinfunction "1_1") (pintype "passive"))
      (node (ref "R157") (pin "2") (pinfunction "2_2") (pintype "passive"))
      (node (ref "R16") (pin "1") (pinfunction "1_1") (pintype "passive"))
      (node (ref "R177") (pin "2") (pinfunction "2_2") (pintype "passive"))
      (node (ref "R190") (pin "2") (pinfunction "2_2") (pintype "passive"))
      (node (ref "R193") (pin "2") (pinfunction "2_2") (pintype "passive"))
      (node (ref "R196") (pin "1") (pinfunction "1_1") (pintype "passive"))
      (node (ref "R213") (pin "2") (pinfunction "2_2") (pintype "passive"))
      (node (ref "R22") (pin "2") (pinfunction "2_2") (pintype "passive"))
      (node (ref "R221") (pin "2") (pinfunction "2_2") (pintype "passive"))
      (node (ref "R224") (pin "1") (pinfunction "1_1") (pintype "passive"))
      (node (ref "R231") (pin "2") (pinfunction "2_2") (pintype "passive"))
      (node (ref "R242") (pin "2") (pinfunction "2_2") (pintype "passive"))
      (node (ref "R247") (pin "2") (pinfunction "2_2") (pintype "passive"))
      (node (ref "R267") (pin "2") (pinfunction "2_2") (pintype "passive"))
      (node (ref "R280") (pin "2") (pinfunction "2_2") (pintype "passive"))
      (node (ref "R283") (pin "2") (pinfunction "2_2") (pintype "passive"))
      (node (ref "R286") (pin "1") (pinfunction "1_1") (pintype "passive"))
      (node (ref "R292") (pin "2") (pinfunction "2_2") (pintype "passive"))
      (node (ref "R313") (pin "2") (pinfunction "2_2") (pintype "passive"))
      (node (ref "R321") (pin "2") (pinfunction "2_2") (pintype "passive"))
      (node (ref "R324") (pin "1") (pinfunction "1_1") (pintype "passive"))
      (node (ref "R331") (pin "2") (pinfunction "2_2") (pintype "passive"))
      (node (ref "R342") (pin "2") (pinfunction "2_2") (pintype "passive"))
      (node (ref "R357") (pin "2") (pinfunction "2_2") (pintype "passive"))
      (node (ref "R370") (pin "2") (pinfunction "2_2") (pintype "passive"))
      (node (ref "R373") (pin "2") (pinfunction "2_2") (pintype "passive"))
      (node (ref "R376") (pin "1") (pinfunction "1_1") (pintype "passive"))
      (node (ref "R382") (pin "2") (pinfunction "2_2") (pintype "passive"))
      (node (ref "R413") (pin "2") (pinfunction "2_2") (pintype "passive"))
      (node (ref "R42") (pin "2") (pinfunction "2_2") (pintype "passive"))
      (node (ref "R421") (pin "2") (pinfunction "2_2") (pintype "passive"))
      (node (ref "R424") (pin "1") (pinfunction "1_1") (pintype "passive"))
      (node (ref "R431") (pin "2") (pinfunction "2_2") (pintype "passive"))
      (node (ref "R442") (pin "2") (pinfunction "2_2") (pintype "passive"))
      (node (ref "R447") (pin "2") (pinfunction "2_2") (pintype "passive"))
      (node (ref "R513") (pin "2") (pinfunction "2_2") (pintype "passive"))
      (node (ref "R521") (pin "2") (pinfunction "2_2") (pintype "passive"))
      (node (ref "R524") (pin "1") (pinfunction "1_1") (pintype "passive"))
      (node (ref "R531") (pin "2") (pinfunction "2_2") (pintype "passive"))
      (node (ref "R542") (pin "2") (pinfunction "2_2") (pintype "passive"))
      (node (ref "R55") (pin "2") (pinfunction "2_2") (pintype "passive"))
      (node (ref "R58") (pin "2") (pinfunction "2_2") (pintype "passive"))
      (node (ref "R61") (pin "1") (pinfunction "1_1") (pintype "passive"))
      (node (ref "R613") (pin "2") (pinfunction "2_2") (pintype "passive"))
      (node (ref "R621") (pin "2") (pinfunction "2_2") (pintype "passive"))
      (node (ref "R624") (pin "1") (pinfunction "1_1") (pintype "passive"))
      (node (ref "R631") (pin "2") (pinfunction "2_2") (pintype "passive"))
      (node (ref "R642") (pin "2") (pinfunction "2_2") (pintype "passive"))
      (node (ref "R67") (pin "2") (pinfunction "2_2") (pintype "passive"))
      (node (ref "R87") (pin "2") (pinfunction "2_2") (pintype "passive"))
    )
    (net (code "953") (name "unconnected-(IC1A-Q6-Pad7)") (class "Default")
      (node (ref "IC1") (pin "7") (pinfunction "Q6_7") (pintype "output"))
    )
    (net (code "954") (name "unconnected-(IC1A-Q7-Pad4)") (class "Default")
      (node (ref "IC1") (pin "4") (pinfunction "Q7_4") (pintype "output"))
    )
    (net (code "955") (name "unconnected-(IC1A-Q8-Pad9)") (class "Default")
      (node (ref "IC1") (pin "9") (pinfunction "Q8_9") (pintype "output"))
    )
    (net (code "956") (name "unconnected-(IC1A-Q9-Pad5)") (class "Default")
      (node (ref "IC1") (pin "5") (pinfunction "Q9_5") (pintype "output"))
    )
    (net (code "957") (name "unconnected-(IC5D-OUT-Pad13)") (class "Default")
      (node (ref "IC5") (pin "13") (pinfunction "OUT_13") (pintype "open_collector"))
    )
    (net (code "958") (name "unconnected-(IC7-DIS-Pad7)") (class "Default")
      (node (ref "IC7") (pin "7") (pinfunction "DIS_7") (pintype "input"))
    )
    (net (code "959") (name "unconnected-(IC8A-Q-Pad6)") (class "Default")
      (node (ref "IC8") (pin "6") (pinfunction "Q_6") (pintype "output"))
    )
    (net (code "960") (name "unconnected-(IC8A-T2-Pad2)") (class "Default")
      (node (ref "IC8") (pin "2") (pinfunction "T2_2") (pintype "input"))
    )
    (net (code "961") (name "unconnected-(IC8A-~{Q}-Pad7)") (class "Default")
      (node (ref "IC8") (pin "7") (pinfunction "~{Q}_7") (pintype "output"))
    )
    (net (code "962") (name "unconnected-(IC8B-Q-Pad10)") (class "Default")
      (node (ref "IC8") (pin "10") (pinfunction "Q_10") (pintype "output"))
    )
    (net (code "963") (name "unconnected-(IC11A-Q6-Pad7)") (class "Default")
      (node (ref "IC11") (pin "7") (pinfunction "Q6_7") (pintype "output"))
    )
    (net (code "964") (name "unconnected-(IC11A-Q7-Pad4)") (class "Default")
      (node (ref "IC11") (pin "4") (pinfunction "Q7_4") (pintype "output"))
    )
    (net (code "965") (name "unconnected-(IC11A-Q8-Pad9)") (class "Default")
      (node (ref "IC11") (pin "9") (pinfunction "Q8_9") (pintype "output"))
    )
    (net (code "966") (name "unconnected-(IC11A-Q9-Pad5)") (class "Default")
      (node (ref "IC11") (pin "5") (pinfunction "Q9_5") (pintype "output"))
    )
    (net (code "967") (name "unconnected-(IC15D-OUT-Pad13)") (class "Default")
      (node (ref "IC15") (pin "13") (pinfunction "OUT_13") (pintype "open_collector"))
    )
    (net (code "968") (name "unconnected-(IC17-DIS-Pad7)") (class "Default")
      (node (ref "IC17") (pin "7") (pinfunction "DIS_7") (pintype "input"))
    )
    (net (code "969") (name "unconnected-(IC18A-Q-Pad6)") (class "Default")
      (node (ref "IC18") (pin "6") (pinfunction "Q_6") (pintype "output"))
    )
    (net (code "970") (name "unconnected-(IC18A-T2-Pad2)") (class "Default")
      (node (ref "IC18") (pin "2") (pinfunction "T2_2") (pintype "input"))
    )
    (net (code "971") (name "unconnected-(IC18A-~{Q}-Pad7)") (class "Default")
      (node (ref "IC18") (pin "7") (pinfunction "~{Q}_7") (pintype "output"))
    )
    (net (code "972") (name "unconnected-(IC18B-Q-Pad10)") (class "Default")
      (node (ref "IC18") (pin "10") (pinfunction "Q_10") (pintype "output"))
    )
    (net (code "973") (name "unconnected-(IC21A-Q6-Pad7)") (class "Default")
      (node (ref "IC21") (pin "7") (pinfunction "Q6_7") (pintype "output"))
    )
    (net (code "974") (name "unconnected-(IC21A-Q7-Pad4)") (class "Default")
      (node (ref "IC21") (pin "4") (pinfunction "Q7_4") (pintype "output"))
    )
    (net (code "975") (name "unconnected-(IC21A-Q8-Pad9)") (class "Default")
      (node (ref "IC21") (pin "9") (pinfunction "Q8_9") (pintype "output"))
    )
    (net (code "976") (name "unconnected-(IC21A-Q9-Pad5)") (class "Default")
      (node (ref "IC21") (pin "5") (pinfunction "Q9_5") (pintype "output"))
    )
    (net (code "977") (name "unconnected-(IC25D-OUT-Pad13)") (class "Default")
      (node (ref "IC25") (pin "13") (pinfunction "OUT_13") (pintype "open_collector"))
    )
    (net (code "978") (name "unconnected-(IC27-DIS-Pad7)") (class "Default")
      (node (ref "IC27") (pin "7") (pinfunction "DIS_7") (pintype "input"))
    )
    (net (code "979") (name "unconnected-(IC28A-Q-Pad6)") (class "Default")
      (node (ref "IC28") (pin "6") (pinfunction "Q_6") (pintype "output"))
    )
    (net (code "980") (name "unconnected-(IC28A-T2-Pad2)") (class "Default")
      (node (ref "IC28") (pin "2") (pinfunction "T2_2") (pintype "input"))
    )
    (net (code "981") (name "unconnected-(IC28A-~{Q}-Pad7)") (class "Default")
      (node (ref "IC28") (pin "7") (pinfunction "~{Q}_7") (pintype "output"))
    )
    (net (code "982") (name "unconnected-(IC28B-Q-Pad10)") (class "Default")
      (node (ref "IC28") (pin "10") (pinfunction "Q_10") (pintype "output"))
    )
    (net (code "983") (name "unconnected-(IC31A-Q6-Pad7)") (class "Default")
      (node (ref "IC31") (pin "7") (pinfunction "Q6_7") (pintype "output"))
    )
    (net (code "984") (name "unconnected-(IC31A-Q7-Pad4)") (class "Default")
      (node (ref "IC31") (pin "4") (pinfunction "Q7_4") (pintype "output"))
    )
    (net (code "985") (name "unconnected-(IC31A-Q8-Pad9)") (class "Default")
      (node (ref "IC31") (pin "9") (pinfunction "Q8_9") (pintype "output"))
    )
    (net (code "986") (name "unconnected-(IC31A-Q9-Pad5)") (class "Default")
      (node (ref "IC31") (pin "5") (pinfunction "Q9_5") (pintype "output"))
    )
    (net (code "987") (name "unconnected-(IC35D-OUT-Pad13)") (class "Default")
      (node (ref "IC35") (pin "13") (pinfunction "OUT_13") (pintype "open_collector"))
    )
    (net (code "988") (name "unconnected-(IC37-DIS-Pad7)") (class "Default")
      (node (ref "IC37") (pin "7") (pinfunction "DIS_7") (pintype "input"))
    )
    (net (code "989") (name "unconnected-(IC38A-Q-Pad6)") (class "Default")
      (node (ref "IC38") (pin "6") (pinfunction "Q_6") (pintype "output"))
    )
    (net (code "990") (name "unconnected-(IC38A-T2-Pad2)") (class "Default")
      (node (ref "IC38") (pin "2") (pinfunction "T2_2") (pintype "input"))
    )
    (net (code "991") (name "unconnected-(IC38A-~{Q}-Pad7)") (class "Default")
      (node (ref "IC38") (pin "7") (pinfunction "~{Q}_7") (pintype "output"))
    )
    (net (code "992") (name "unconnected-(IC38B-Q-Pad10)") (class "Default")
      (node (ref "IC38") (pin "10") (pinfunction "Q_10") (pintype "output"))
    )
    (net (code "993") (name "unconnected-(IC41A-Q6-Pad7)") (class "Default")
      (node (ref "IC41") (pin "7") (pinfunction "Q6_7") (pintype "output"))
    )
    (net (code "994") (name "unconnected-(IC41A-Q7-Pad4)") (class "Default")
      (node (ref "IC41") (pin "4") (pinfunction "Q7_4") (pintype "output"))
    )
    (net (code "995") (name "unconnected-(IC41A-Q8-Pad9)") (class "Default")
      (node (ref "IC41") (pin "9") (pinfunction "Q8_9") (pintype "output"))
    )
    (net (code "996") (name "unconnected-(IC41A-Q9-Pad5)") (class "Default")
      (node (ref "IC41") (pin "5") (pinfunction "Q9_5") (pintype "output"))
    )
    (net (code "997") (name "unconnected-(IC45D-OUT-Pad13)") (class "Default")
      (node (ref "IC45") (pin "13") (pinfunction "OUT_13") (pintype "open_collector"))
    )
    (net (code "998") (name "unconnected-(IC47-DIS-Pad7)") (class "Default")
      (node (ref "IC47") (pin "7") (pinfunction "DIS_7") (pintype "input"))
    )
    (net (code "999") (name "unconnected-(IC48A-Q-Pad6)") (class "Default")
      (node (ref "IC48") (pin "6") (pinfunction "Q_6") (pintype "output"))
    )
    (net (code "1000") (name "unconnected-(IC48A-T2-Pad2)") (class "Default")
      (node (ref "IC48") (pin "2") (pinfunction "T2_2") (pintype "input"))
    )
    (net (code "1001") (name "unconnected-(IC48A-~{Q}-Pad7)") (class "Default")
      (node (ref "IC48") (pin "7") (pinfunction "~{Q}_7") (pintype "output"))
    )
    (net (code "1002") (name "unconnected-(IC48B-Q-Pad10)") (class "Default")
      (node (ref "IC48") (pin "10") (pinfunction "Q_10") (pintype "output"))
    )
    (net (code "1003") (name "unconnected-(IC51A-Q6-Pad7)") (class "Default")
      (node (ref "IC51") (pin "7") (pinfunction "Q6_7") (pintype "output"))
    )
    (net (code "1004") (name "unconnected-(IC51A-Q7-Pad4)") (class "Default")
      (node (ref "IC51") (pin "4") (pinfunction "Q7_4") (pintype "output"))
    )
    (net (code "1005") (name "unconnected-(IC51A-Q8-Pad9)") (class "Default")
      (node (ref "IC51") (pin "9") (pinfunction "Q8_9") (pintype "output"))
    )
    (net (code "1006") (name "unconnected-(IC51A-Q9-Pad5)") (class "Default")
      (node (ref "IC51") (pin "5") (pinfunction "Q9_5") (pintype "output"))
    )
    (net (code "1007") (name "unconnected-(IC55D-OUT-Pad13)") (class "Default")
      (node (ref "IC55") (pin "13") (pinfunction "OUT_13") (pintype "open_collector"))
    )
    (net (code "1008") (name "unconnected-(IC57-DIS-Pad7)") (class "Default")
      (node (ref "IC57") (pin "7") (pinfunction "DIS_7") (pintype "input"))
    )
    (net (code "1009") (name "unconnected-(IC58A-Q-Pad6)") (class "Default")
      (node (ref "IC58") (pin "6") (pinfunction "Q_6") (pintype "output"))
    )
    (net (code "1010") (name "unconnected-(IC58A-T2-Pad2)") (class "Default")
      (node (ref "IC58") (pin "2") (pinfunction "T2_2") (pintype "input"))
    )
    (net (code "1011") (name "unconnected-(IC58A-~{Q}-Pad7)") (class "Default")
      (node (ref "IC58") (pin "7") (pinfunction "~{Q}_7") (pintype "output"))
    )
    (net (code "1012") (name "unconnected-(IC58B-Q-Pad10)") (class "Default")
      (node (ref "IC58") (pin "10") (pinfunction "Q_10") (pintype "output"))
    )
    (net (code "1013") (name "unconnected-(IC105A-Q6-Pad7)") (class "Default")
      (node (ref "IC105") (pin "7") (pinfunction "Q6_7") (pintype "output"))
    )
    (net (code "1014") (name "unconnected-(IC105A-Q7-Pad4)") (class "Default")
      (node (ref "IC105") (pin "4") (pinfunction "Q7_4") (pintype "output"))
    )
    (net (code "1015") (name "unconnected-(IC105A-Q8-Pad9)") (class "Default")
      (node (ref "IC105") (pin "9") (pinfunction "Q8_9") (pintype "output"))
    )
    (net (code "1016") (name "unconnected-(IC105A-Q9-Pad5)") (class "Default")
      (node (ref "IC105") (pin "5") (pinfunction "Q9_5") (pintype "output"))
    )
    (net (code "1017") (name "unconnected-(IC108D-OUT-Pad13)") (class "Default")
      (node (ref "IC108") (pin "13") (pinfunction "OUT_13") (pintype "open_collector"))
    )
    (net (code "1018") (name "unconnected-(IC110-DIS-Pad7)") (class "Default")
      (node (ref "IC110") (pin "7") (pinfunction "DIS_7") (pintype "input"))
    )
    (net (code "1019") (name "unconnected-(IC111A-Q-Pad6)") (class "Default")
      (node (ref "IC111") (pin "6") (pinfunction "Q_6") (pintype "output"))
    )
    (net (code "1020") (name "unconnected-(IC111A-T2-Pad2)") (class "Default")
      (node (ref "IC111") (pin "2") (pinfunction "T2_2") (pintype "input"))
    )
    (net (code "1021") (name "unconnected-(IC111A-~{Q}-Pad7)") (class "Default")
      (node (ref "IC111") (pin "7") (pinfunction "~{Q}_7") (pintype "output"))
    )
    (net (code "1022") (name "unconnected-(IC111B-Q-Pad10)") (class "Default")
      (node (ref "IC111") (pin "10") (pinfunction "Q_10") (pintype "output"))
    )
    (net (code "1023") (name "unconnected-(IC205A-Q6-Pad7)") (class "Default")
      (node (ref "IC205") (pin "7") (pinfunction "Q6_7") (pintype "output"))
    )
    (net (code "1024") (name "unconnected-(IC205A-Q7-Pad4)") (class "Default")
      (node (ref "IC205") (pin "4") (pinfunction "Q7_4") (pintype "output"))
    )
    (net (code "1025") (name "unconnected-(IC205A-Q8-Pad9)") (class "Default")
      (node (ref "IC205") (pin "9") (pinfunction "Q8_9") (pintype "output"))
    )
    (net (code "1026") (name "unconnected-(IC205A-Q9-Pad5)") (class "Default")
      (node (ref "IC205") (pin "5") (pinfunction "Q9_5") (pintype "output"))
    )
    (net (code "1027") (name "unconnected-(IC208D-OUT-Pad13)") (class "Default")
      (node (ref "IC208") (pin "13") (pinfunction "OUT_13") (pintype "open_collector"))
    )
    (net (code "1028") (name "unconnected-(IC210-DIS-Pad7)") (class "Default")
      (node (ref "IC210") (pin "7") (pinfunction "DIS_7") (pintype "input"))
    )
    (net (code "1029") (name "unconnected-(IC211A-Q-Pad6)") (class "Default")
      (node (ref "IC211") (pin "6") (pinfunction "Q_6") (pintype "output"))
    )
    (net (code "1030") (name "unconnected-(IC211A-T2-Pad2)") (class "Default")
      (node (ref "IC211") (pin "2") (pinfunction "T2_2") (pintype "input"))
    )
    (net (code "1031") (name "unconnected-(IC211A-~{Q}-Pad7)") (class "Default")
      (node (ref "IC211") (pin "7") (pinfunction "~{Q}_7") (pintype "output"))
    )
    (net (code "1032") (name "unconnected-(IC211B-Q-Pad10)") (class "Default")
      (node (ref "IC211") (pin "10") (pinfunction "Q_10") (pintype "output"))
    )
    (net (code "1033") (name "unconnected-(IC305A-Q6-Pad7)") (class "Default")
      (node (ref "IC305") (pin "7") (pinfunction "Q6_7") (pintype "output"))
    )
    (net (code "1034") (name "unconnected-(IC305A-Q7-Pad4)") (class "Default")
      (node (ref "IC305") (pin "4") (pinfunction "Q7_4") (pintype "output"))
    )
    (net (code "1035") (name "unconnected-(IC305A-Q8-Pad9)") (class "Default")
      (node (ref "IC305") (pin "9") (pinfunction "Q8_9") (pintype "output"))
    )
    (net (code "1036") (name "unconnected-(IC305A-Q9-Pad5)") (class "Default")
      (node (ref "IC305") (pin "5") (pinfunction "Q9_5") (pintype "output"))
    )
    (net (code "1037") (name "unconnected-(IC308D-OUT-Pad13)") (class "Default")
      (node (ref "IC308") (pin "13") (pinfunction "OUT_13") (pintype "open_collector"))
    )
    (net (code "1038") (name "unconnected-(IC310-DIS-Pad7)") (class "Default")
      (node (ref "IC310") (pin "7") (pinfunction "DIS_7") (pintype "input"))
    )
    (net (code "1039") (name "unconnected-(IC311A-Q-Pad6)") (class "Default")
      (node (ref "IC311") (pin "6") (pinfunction "Q_6") (pintype "output"))
    )
    (net (code "1040") (name "unconnected-(IC311A-T2-Pad2)") (class "Default")
      (node (ref "IC311") (pin "2") (pinfunction "T2_2") (pintype "input"))
    )
    (net (code "1041") (name "unconnected-(IC311A-~{Q}-Pad7)") (class "Default")
      (node (ref "IC311") (pin "7") (pinfunction "~{Q}_7") (pintype "output"))
    )
    (net (code "1042") (name "unconnected-(IC311B-Q-Pad10)") (class "Default")
      (node (ref "IC311") (pin "10") (pinfunction "Q_10") (pintype "output"))
    )
    (net (code "1043") (name "unconnected-(IC405A-Q6-Pad7)") (class "Default")
      (node (ref "IC405") (pin "7") (pinfunction "Q6_7") (pintype "output"))
    )
    (net (code "1044") (name "unconnected-(IC405A-Q7-Pad4)") (class "Default")
      (node (ref "IC405") (pin "4") (pinfunction "Q7_4") (pintype "output"))
    )
    (net (code "1045") (name "unconnected-(IC405A-Q8-Pad9)") (class "Default")
      (node (ref "IC405") (pin "9") (pinfunction "Q8_9") (pintype "output"))
    )
    (net (code "1046") (name "unconnected-(IC405A-Q9-Pad5)") (class "Default")
      (node (ref "IC405") (pin "5") (pinfunction "Q9_5") (pintype "output"))
    )
    (net (code "1047") (name "unconnected-(IC408D-OUT-Pad13)") (class "Default")
      (node (ref "IC408") (pin "13") (pinfunction "OUT_13") (pintype "open_collector"))
    )
    (net (code "1048") (name "unconnected-(IC410-DIS-Pad7)") (class "Default")
      (node (ref "IC410") (pin "7") (pinfunction "DIS_7") (pintype "input"))
    )
    (net (code "1049") (name "unconnected-(IC411A-Q-Pad6)") (class "Default")
      (node (ref "IC411") (pin "6") (pinfunction "Q_6") (pintype "output"))
    )
    (net (code "1050") (name "unconnected-(IC411A-T2-Pad2)") (class "Default")
      (node (ref "IC411") (pin "2") (pinfunction "T2_2") (pintype "input"))
    )
    (net (code "1051") (name "unconnected-(IC411A-~{Q}-Pad7)") (class "Default")
      (node (ref "IC411") (pin "7") (pinfunction "~{Q}_7") (pintype "output"))
    )
    (net (code "1052") (name "unconnected-(IC411B-Q-Pad10)") (class "Default")
      (node (ref "IC411") (pin "10") (pinfunction "Q_10") (pintype "output"))
    )
    (net (code "1053") (name "unconnected-(IC505A-Q6-Pad7)") (class "Default")
      (node (ref "IC505") (pin "7") (pinfunction "Q6_7") (pintype "output"))
    )
    (net (code "1054") (name "unconnected-(IC505A-Q7-Pad4)") (class "Default")
      (node (ref "IC505") (pin "4") (pinfunction "Q7_4") (pintype "output"))
    )
    (net (code "1055") (name "unconnected-(IC505A-Q8-Pad9)") (class "Default")
      (node (ref "IC505") (pin "9") (pinfunction "Q8_9") (pintype "output"))
    )
    (net (code "1056") (name "unconnected-(IC505A-Q9-Pad5)") (class "Default")
      (node (ref "IC505") (pin "5") (pinfunction "Q9_5") (pintype "output"))
    )
    (net (code "1057") (name "unconnected-(IC508D-OUT-Pad13)") (class "Default")
      (node (ref "IC508") (pin "13") (pinfunction "OUT_13") (pintype "open_collector"))
    )
    (net (code "1058") (name "unconnected-(IC510-DIS-Pad7)") (class "Default")
      (node (ref "IC510") (pin "7") (pinfunction "DIS_7") (pintype "input"))
    )
    (net (code "1059") (name "unconnected-(IC511A-Q-Pad6)") (class "Default")
      (node (ref "IC511") (pin "6") (pinfunction "Q_6") (pintype "output"))
    )
    (net (code "1060") (name "unconnected-(IC511A-T2-Pad2)") (class "Default")
      (node (ref "IC511") (pin "2") (pinfunction "T2_2") (pintype "input"))
    )
    (net (code "1061") (name "unconnected-(IC511A-~{Q}-Pad7)") (class "Default")
      (node (ref "IC511") (pin "7") (pinfunction "~{Q}_7") (pintype "output"))
    )
    (net (code "1062") (name "unconnected-(IC511B-Q-Pad10)") (class "Default")
      (node (ref "IC511") (pin "10") (pinfunction "Q_10") (pintype "output"))
    )
    (net (code "1063") (name "unconnected-(IC605A-Q6-Pad7)") (class "Default")
      (node (ref "IC605") (pin "7") (pinfunction "Q6_7") (pintype "output"))
    )
    (net (code "1064") (name "unconnected-(IC605A-Q7-Pad4)") (class "Default")
      (node (ref "IC605") (pin "4") (pinfunction "Q7_4") (pintype "output"))
    )
    (net (code "1065") (name "unconnected-(IC605A-Q8-Pad9)") (class "Default")
      (node (ref "IC605") (pin "9") (pinfunction "Q8_9") (pintype "output"))
    )
    (net (code "1066") (name "unconnected-(IC605A-Q9-Pad5)") (class "Default")
      (node (ref "IC605") (pin "5") (pinfunction "Q9_5") (pintype "output"))
    )
    (net (code "1067") (name "unconnected-(IC608D-OUT-Pad13)") (class "Default")
      (node (ref "IC608") (pin "13") (pinfunction "OUT_13") (pintype "open_collector"))
    )
    (net (code "1068") (name "unconnected-(IC610-DIS-Pad7)") (class "Default")
      (node (ref "IC610") (pin "7") (pinfunction "DIS_7") (pintype "input"))
    )
    (net (code "1069") (name "unconnected-(IC611A-Q-Pad6)") (class "Default")
      (node (ref "IC611") (pin "6") (pinfunction "Q_6") (pintype "output"))
    )
    (net (code "1070") (name "unconnected-(IC611A-T2-Pad2)") (class "Default")
      (node (ref "IC611") (pin "2") (pinfunction "T2_2") (pintype "input"))
    )
    (net (code "1071") (name "unconnected-(IC611A-~{Q}-Pad7)") (class "Default")
      (node (ref "IC611") (pin "7") (pinfunction "~{Q}_7") (pintype "output"))
    )
    (net (code "1072") (name "unconnected-(IC611B-Q-Pad10)") (class "Default")
      (node (ref "IC611") (pin "10") (pinfunction "Q_10") (pintype "output"))
    )
    (net (code "1073") (name "unconnected-(X1-Pad20)") (class "Default")
      (node (ref "X1") (pin "20") (pinfunction "20_20") (pintype "passive"))
    )
    (net (code "1074") (name "unconnected-(X1-Pad24)") (class "Default")
      (node (ref "X1") (pin "24") (pinfunction "24_24") (pintype "passive"))
    )
    (net (code "1075") (name "unconnected-(X4-Pad20)") (class "Default")
      (node (ref "X4") (pin "20") (pinfunction "20_20") (pintype "passive"))
    )
    (net (code "1076") (name "unconnected-(X4-Pad24)") (class "Default")
      (node (ref "X4") (pin "24") (pinfunction "24_24") (pintype "passive"))
    )
    (net (code "1077") (name "unconnected-(X7-Pad20)") (class "Default")
      (node (ref "X7") (pin "20") (pinfunction "20_20") (pintype "passive"))
    )
    (net (code "1078") (name "unconnected-(X7-Pad24)") (class "Default")
      (node (ref "X7") (pin "24") (pinfunction "24_24") (pintype "passive"))
    )
    (net (code "1079") (name "unconnected-(X10-Pad20)") (class "Default")
      (node (ref "X10") (pin "20") (pinfunction "20_20") (pintype "passive"))
    )
    (net (code "1080") (name "unconnected-(X10-Pad24)") (class "Default")
      (node (ref "X10") (pin "24") (pinfunction "24_24") (pintype "passive"))
    )
    (net (code "1081") (name "unconnected-(X13-Pad20)") (class "Default")
      (node (ref "X13") (pin "20") (pinfunction "20_20") (pintype "passive"))
    )
    (net (code "1082") (name "unconnected-(X13-Pad24)") (class "Default")
      (node (ref "X13") (pin "24") (pinfunction "24_24") (pintype "passive"))
    )
    (net (code "1083") (name "unconnected-(X16-Pad20)") (class "Default")
      (node (ref "X16") (pin "20") (pinfunction "20_20") (pintype "passive"))
    )
    (net (code "1084") (name "unconnected-(X16-Pad24)") (class "Default")
      (node (ref "X16") (pin "24") (pinfunction "24_24") (pintype "passive"))
    )
    (net (code "1085") (name "unconnected-(X101-Pad20)") (class "Default")
      (node (ref "X101") (pin "20") (pinfunction "20_20") (pintype "passive"))
    )
    (net (code "1086") (name "unconnected-(X101-Pad24)") (class "Default")
      (node (ref "X101") (pin "24") (pinfunction "24_24") (pintype "passive"))
    )
    (net (code "1087") (name "unconnected-(X201-Pad20)") (class "Default")
      (node (ref "X201") (pin "20") (pinfunction "20_20") (pintype "passive"))
    )
    (net (code "1088") (name "unconnected-(X201-Pad24)") (class "Default")
      (node (ref "X201") (pin "24") (pinfunction "24_24") (pintype "passive"))
    )
    (net (code "1089") (name "unconnected-(X301-Pad20)") (class "Default")
      (node (ref "X301") (pin "20") (pinfunction "20_20") (pintype "passive"))
    )
    (net (code "1090") (name "unconnected-(X301-Pad24)") (class "Default")
      (node (ref "X301") (pin "24") (pinfunction "24_24") (pintype "passive"))
    )
    (net (code "1091") (name "unconnected-(X401-Pad20)") (class "Default")
      (node (ref "X401") (pin "20") (pinfunction "20_20") (pintype "passive"))
    )
    (net (code "1092") (name "unconnected-(X401-Pad24)") (class "Default")
      (node (ref "X401") (pin "24") (pinfunction "24_24") (pintype "passive"))
    )
    (net (code "1093") (name "unconnected-(X501-Pad20)") (class "Default")
      (node (ref "X501") (pin "20") (pinfunction "20_20") (pintype "passive"))
    )
    (net (code "1094") (name "unconnected-(X501-Pad24)") (class "Default")
      (node (ref "X501") (pin "24") (pinfunction "24_24") (pintype "passive"))
    )
    (net (code "1095") (name "unconnected-(X601-Pad20)") (class "Default")
      (node (ref "X601") (pin "20") (pinfunction "20_20") (pintype "passive"))
    )
    (net (code "1096") (name "unconnected-(X601-Pad24)") (class "Default")
      (node (ref "X601") (pin "24") (pinfunction "24_24") (pintype "passive"))
    )
  )
)
